# MasterPCB_transfer.net
KiCad netlist of a schematic drawn in EAGLE
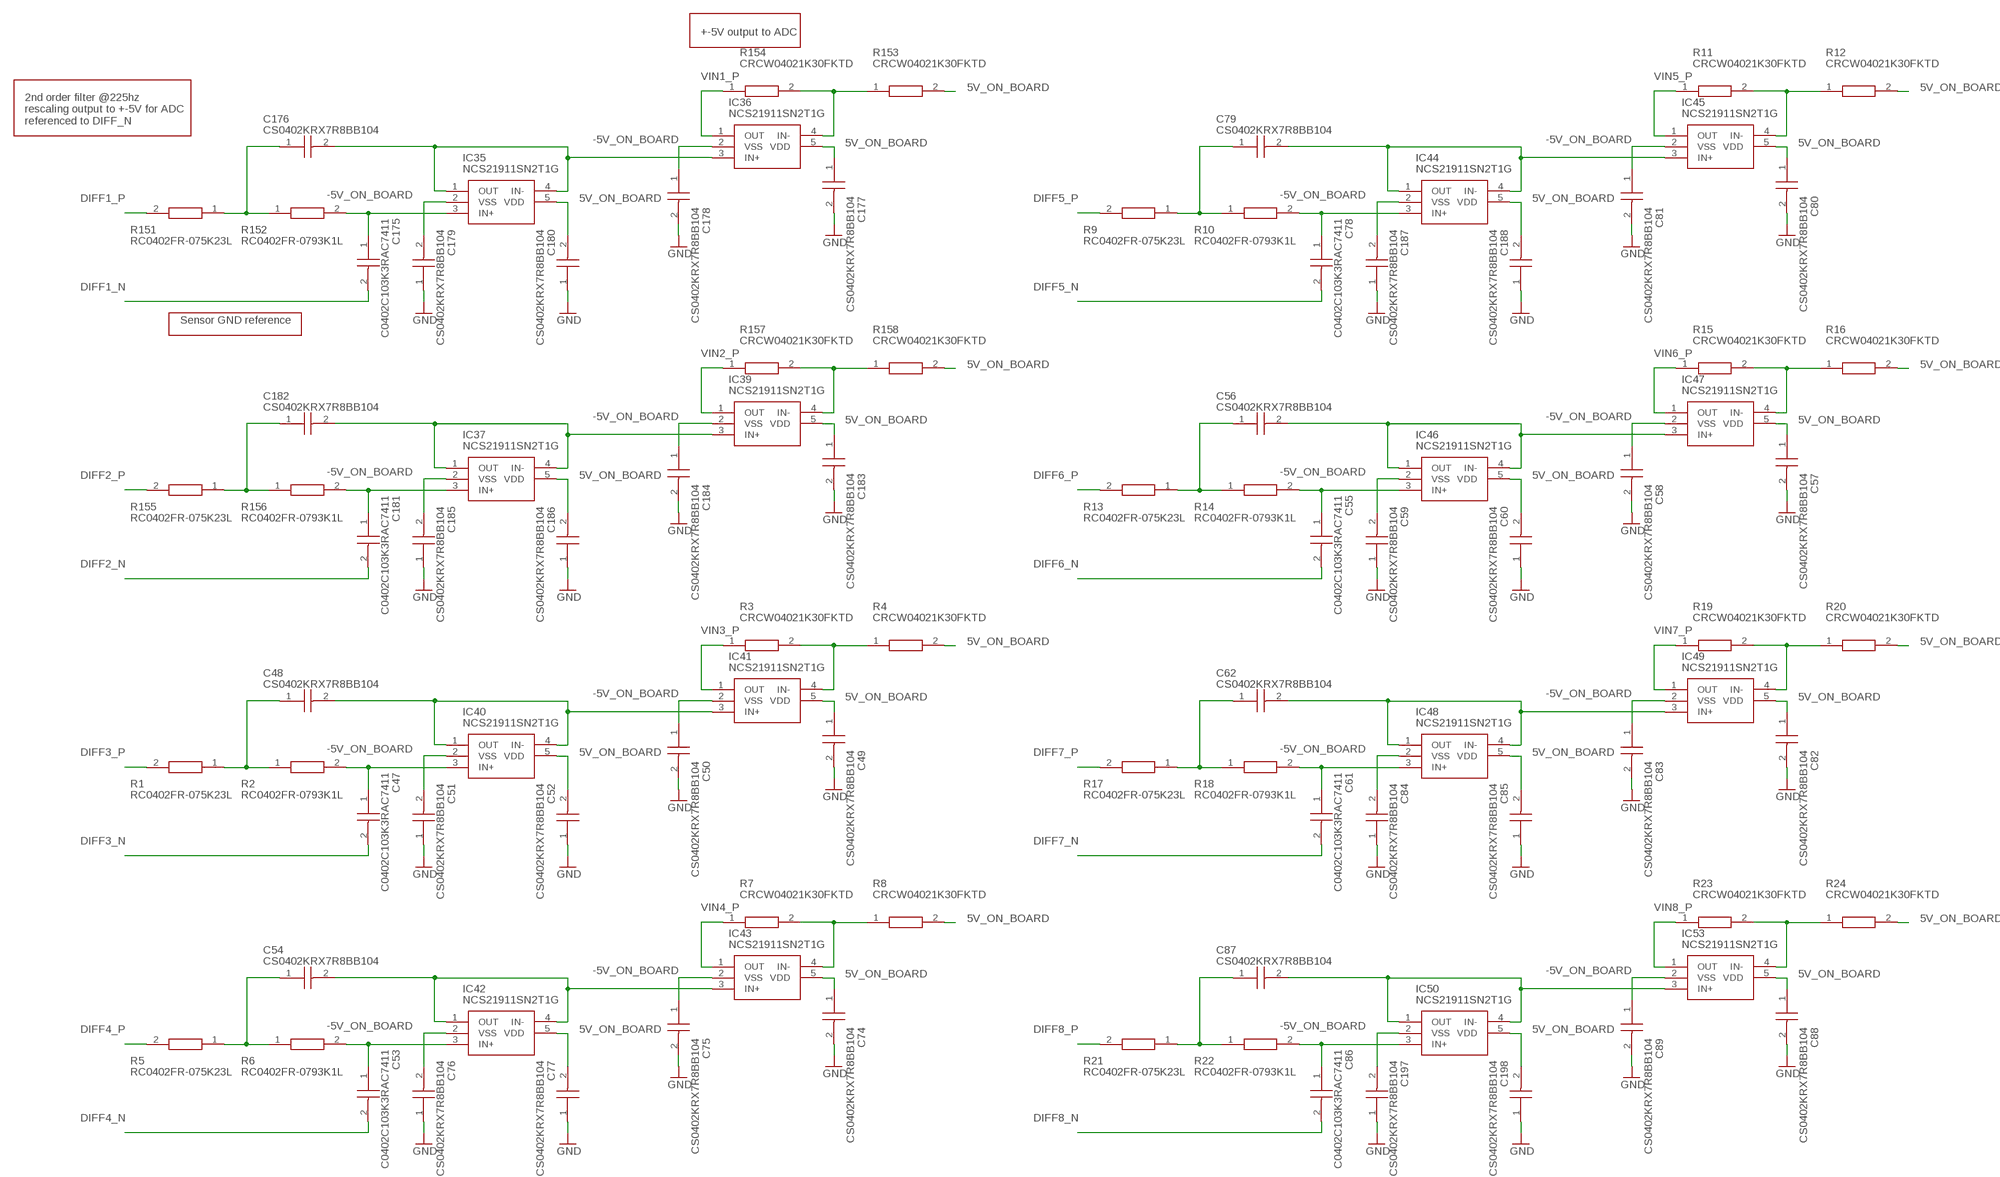
[diagram p0: schematic, sheet 1, part 1 of 3]
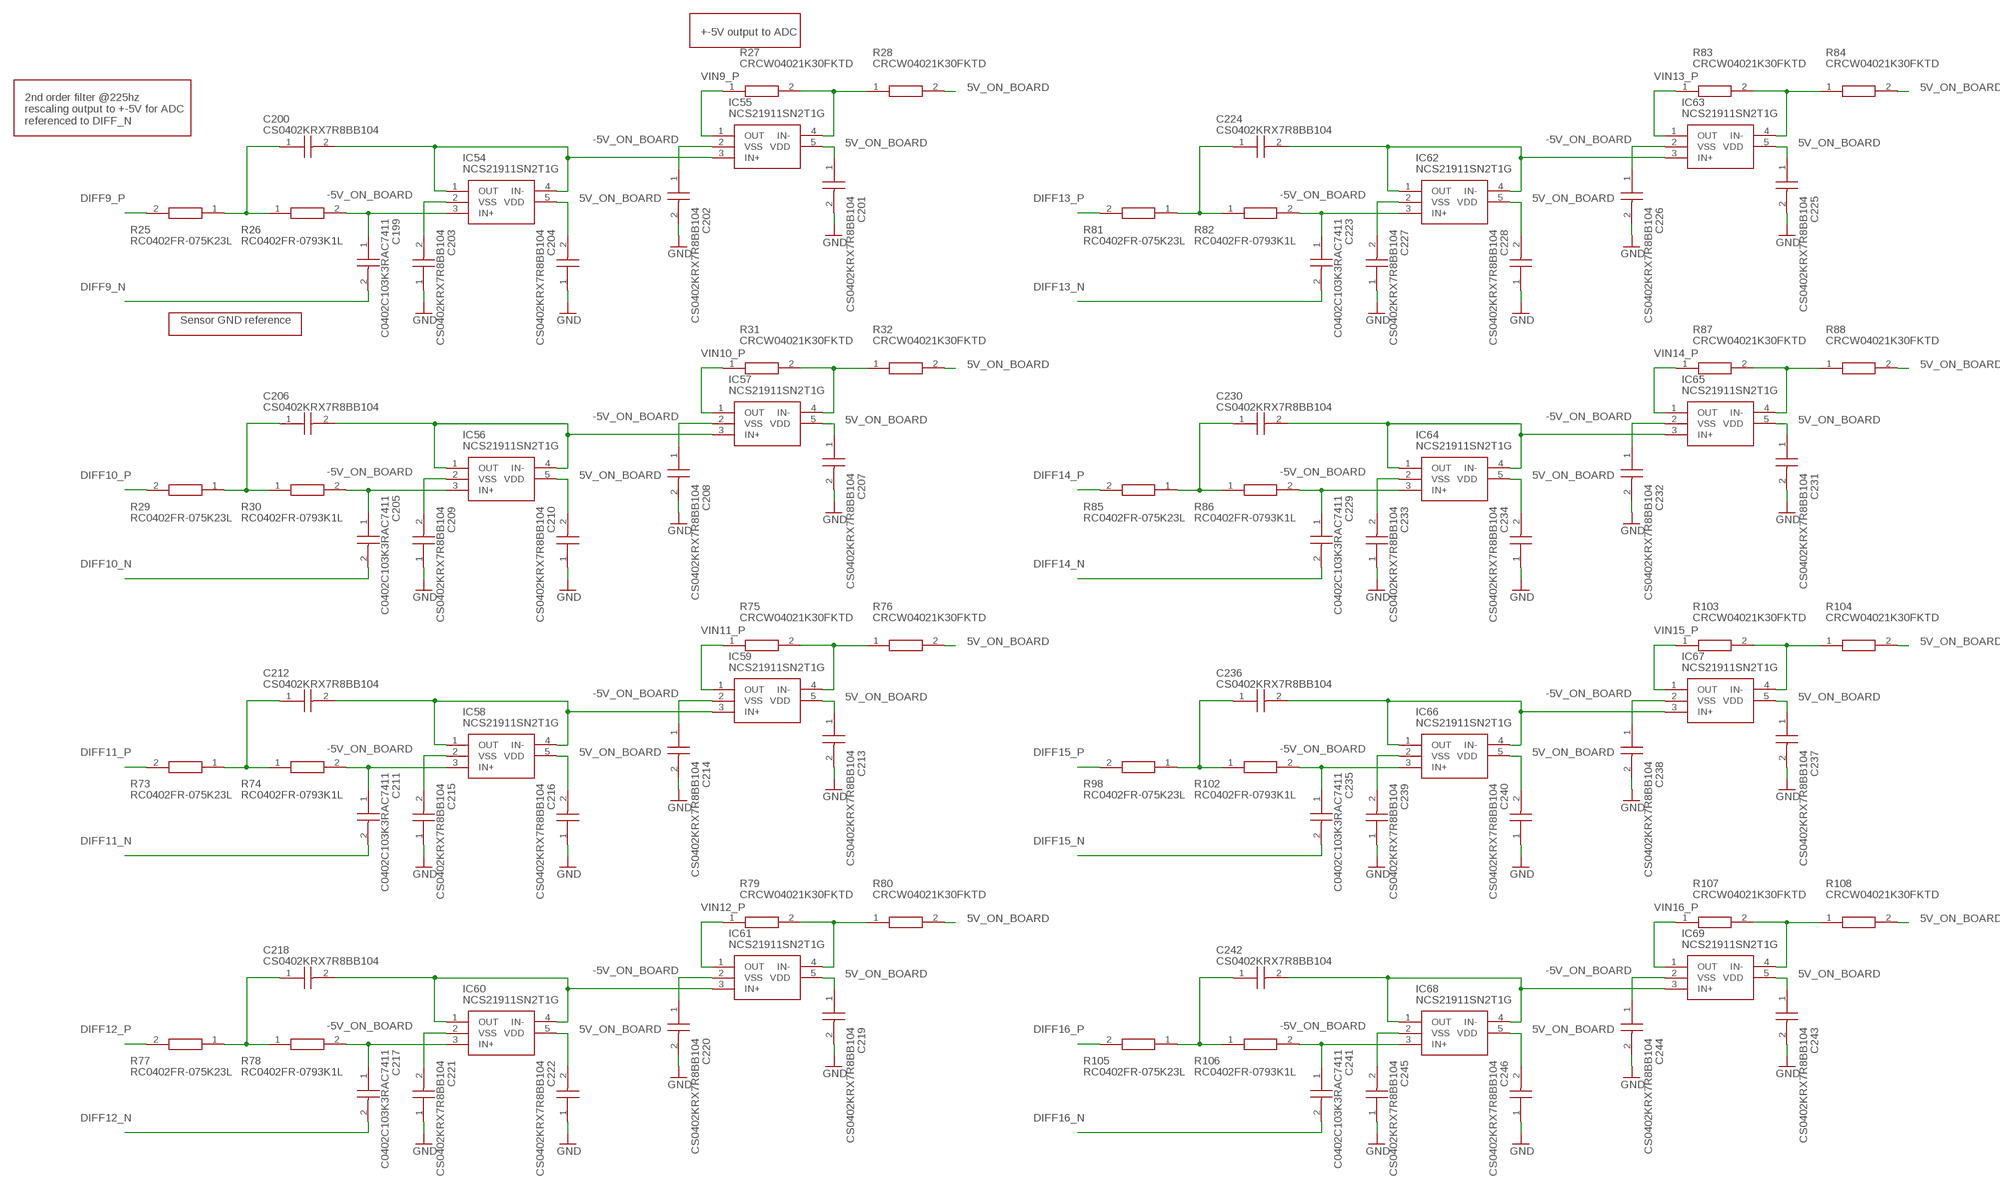
[diagram p1: schematic, sheet 1, part 2 of 3]
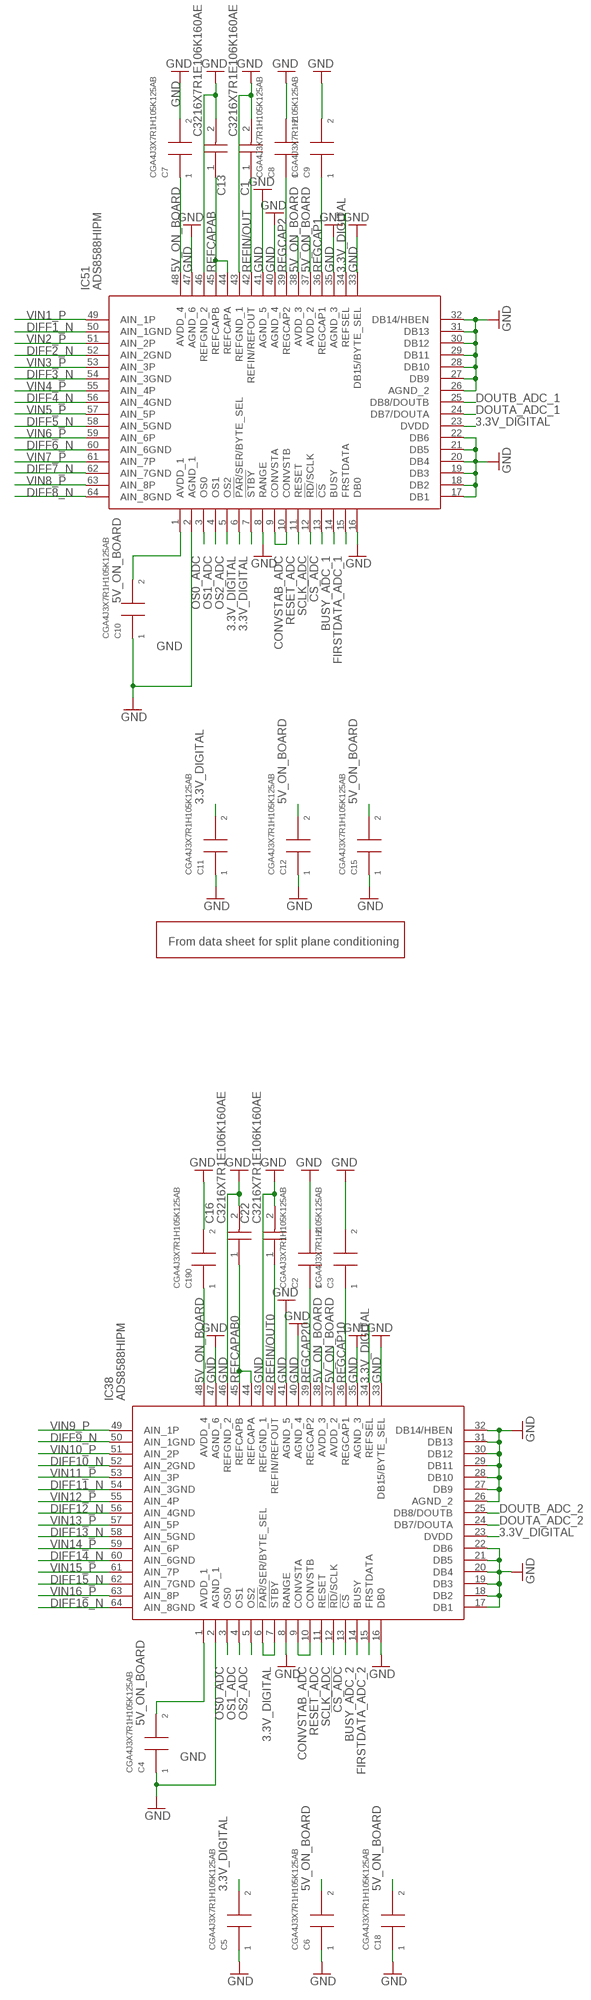
[diagram p2: schematic, sheet 1, part 3 of 3]
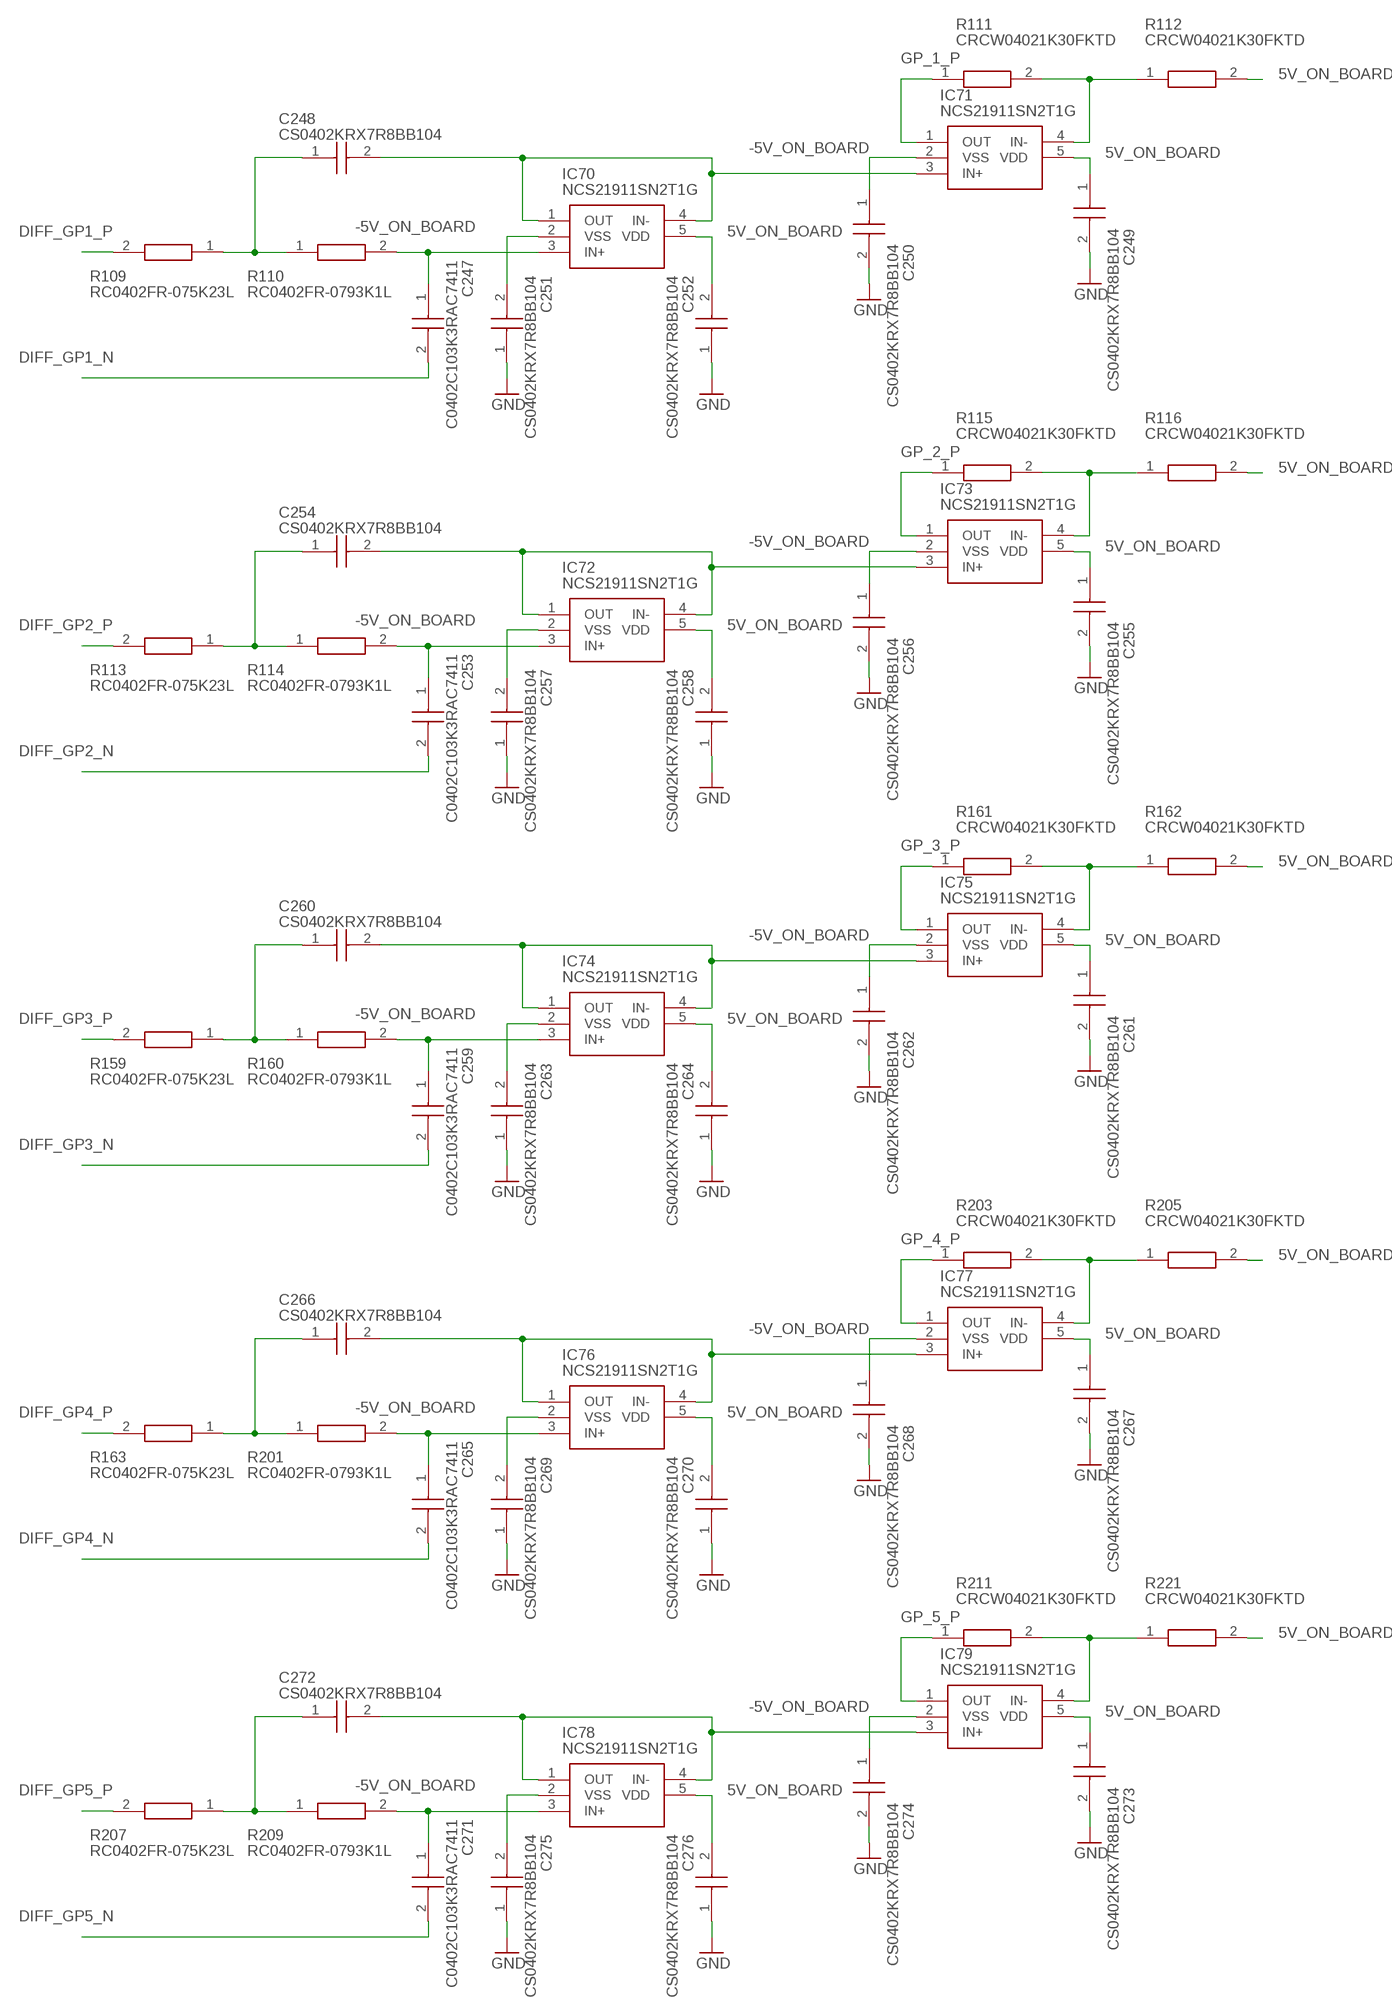
[diagram p3: schematic, sheet 2, part 1 of 2]
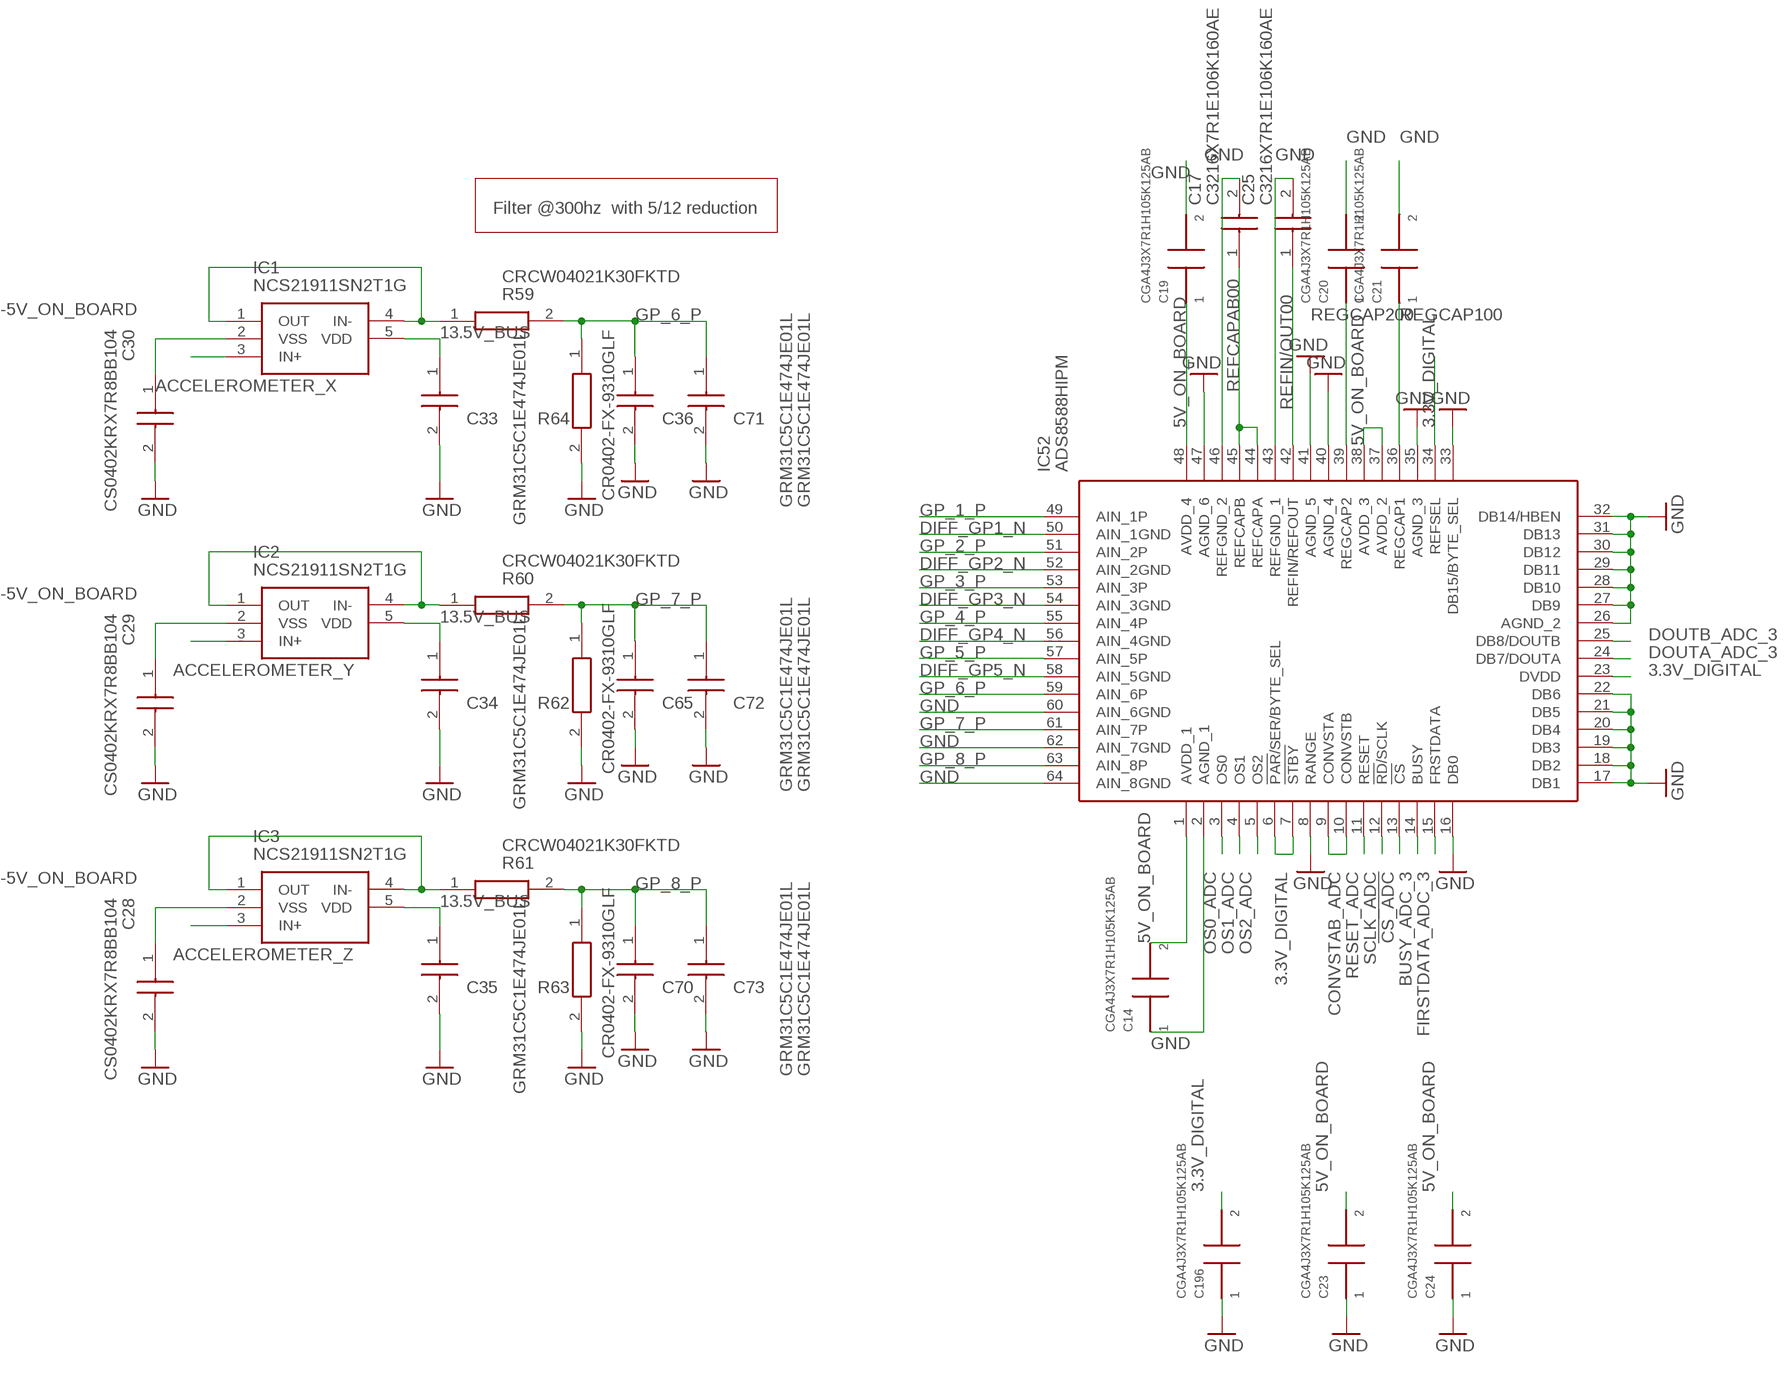
[diagram p4: schematic, sheet 2, part 2 of 2]
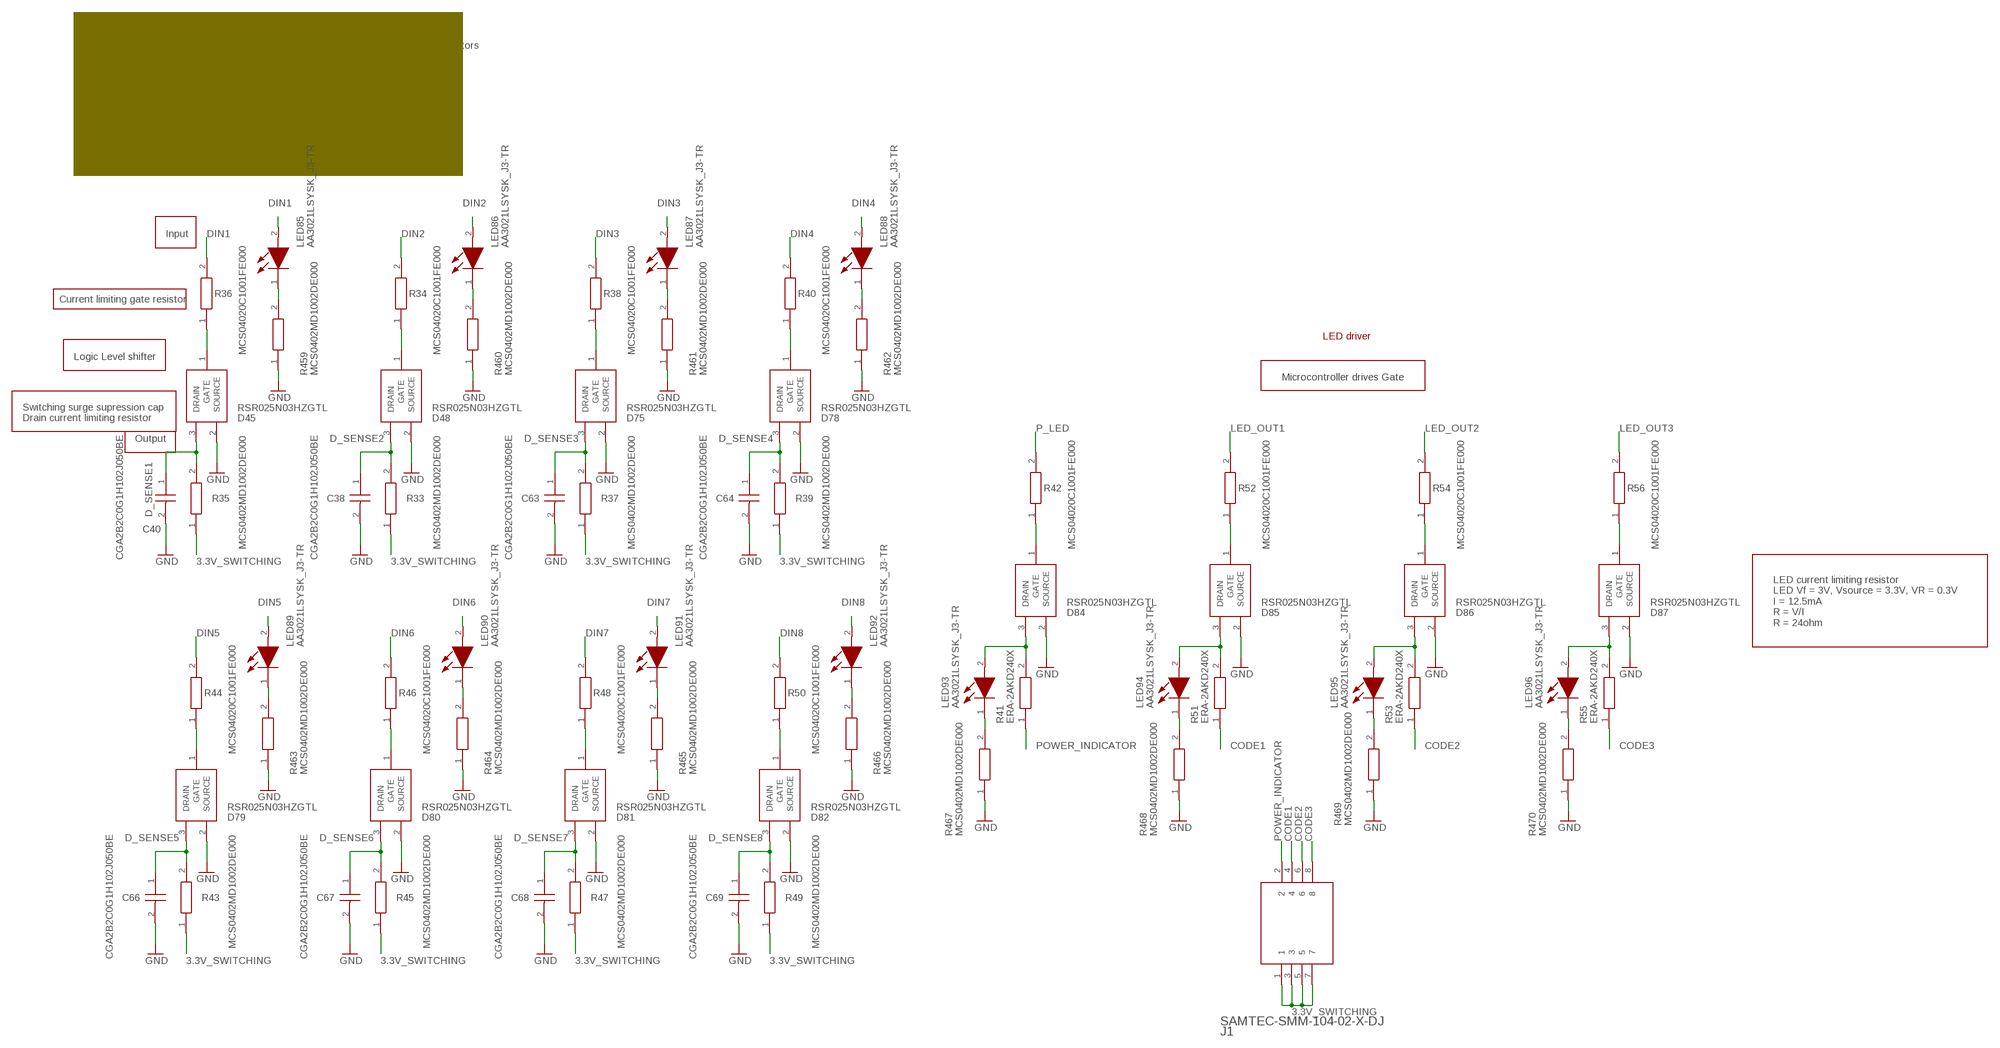
[diagram p5: schematic, sheet 3]
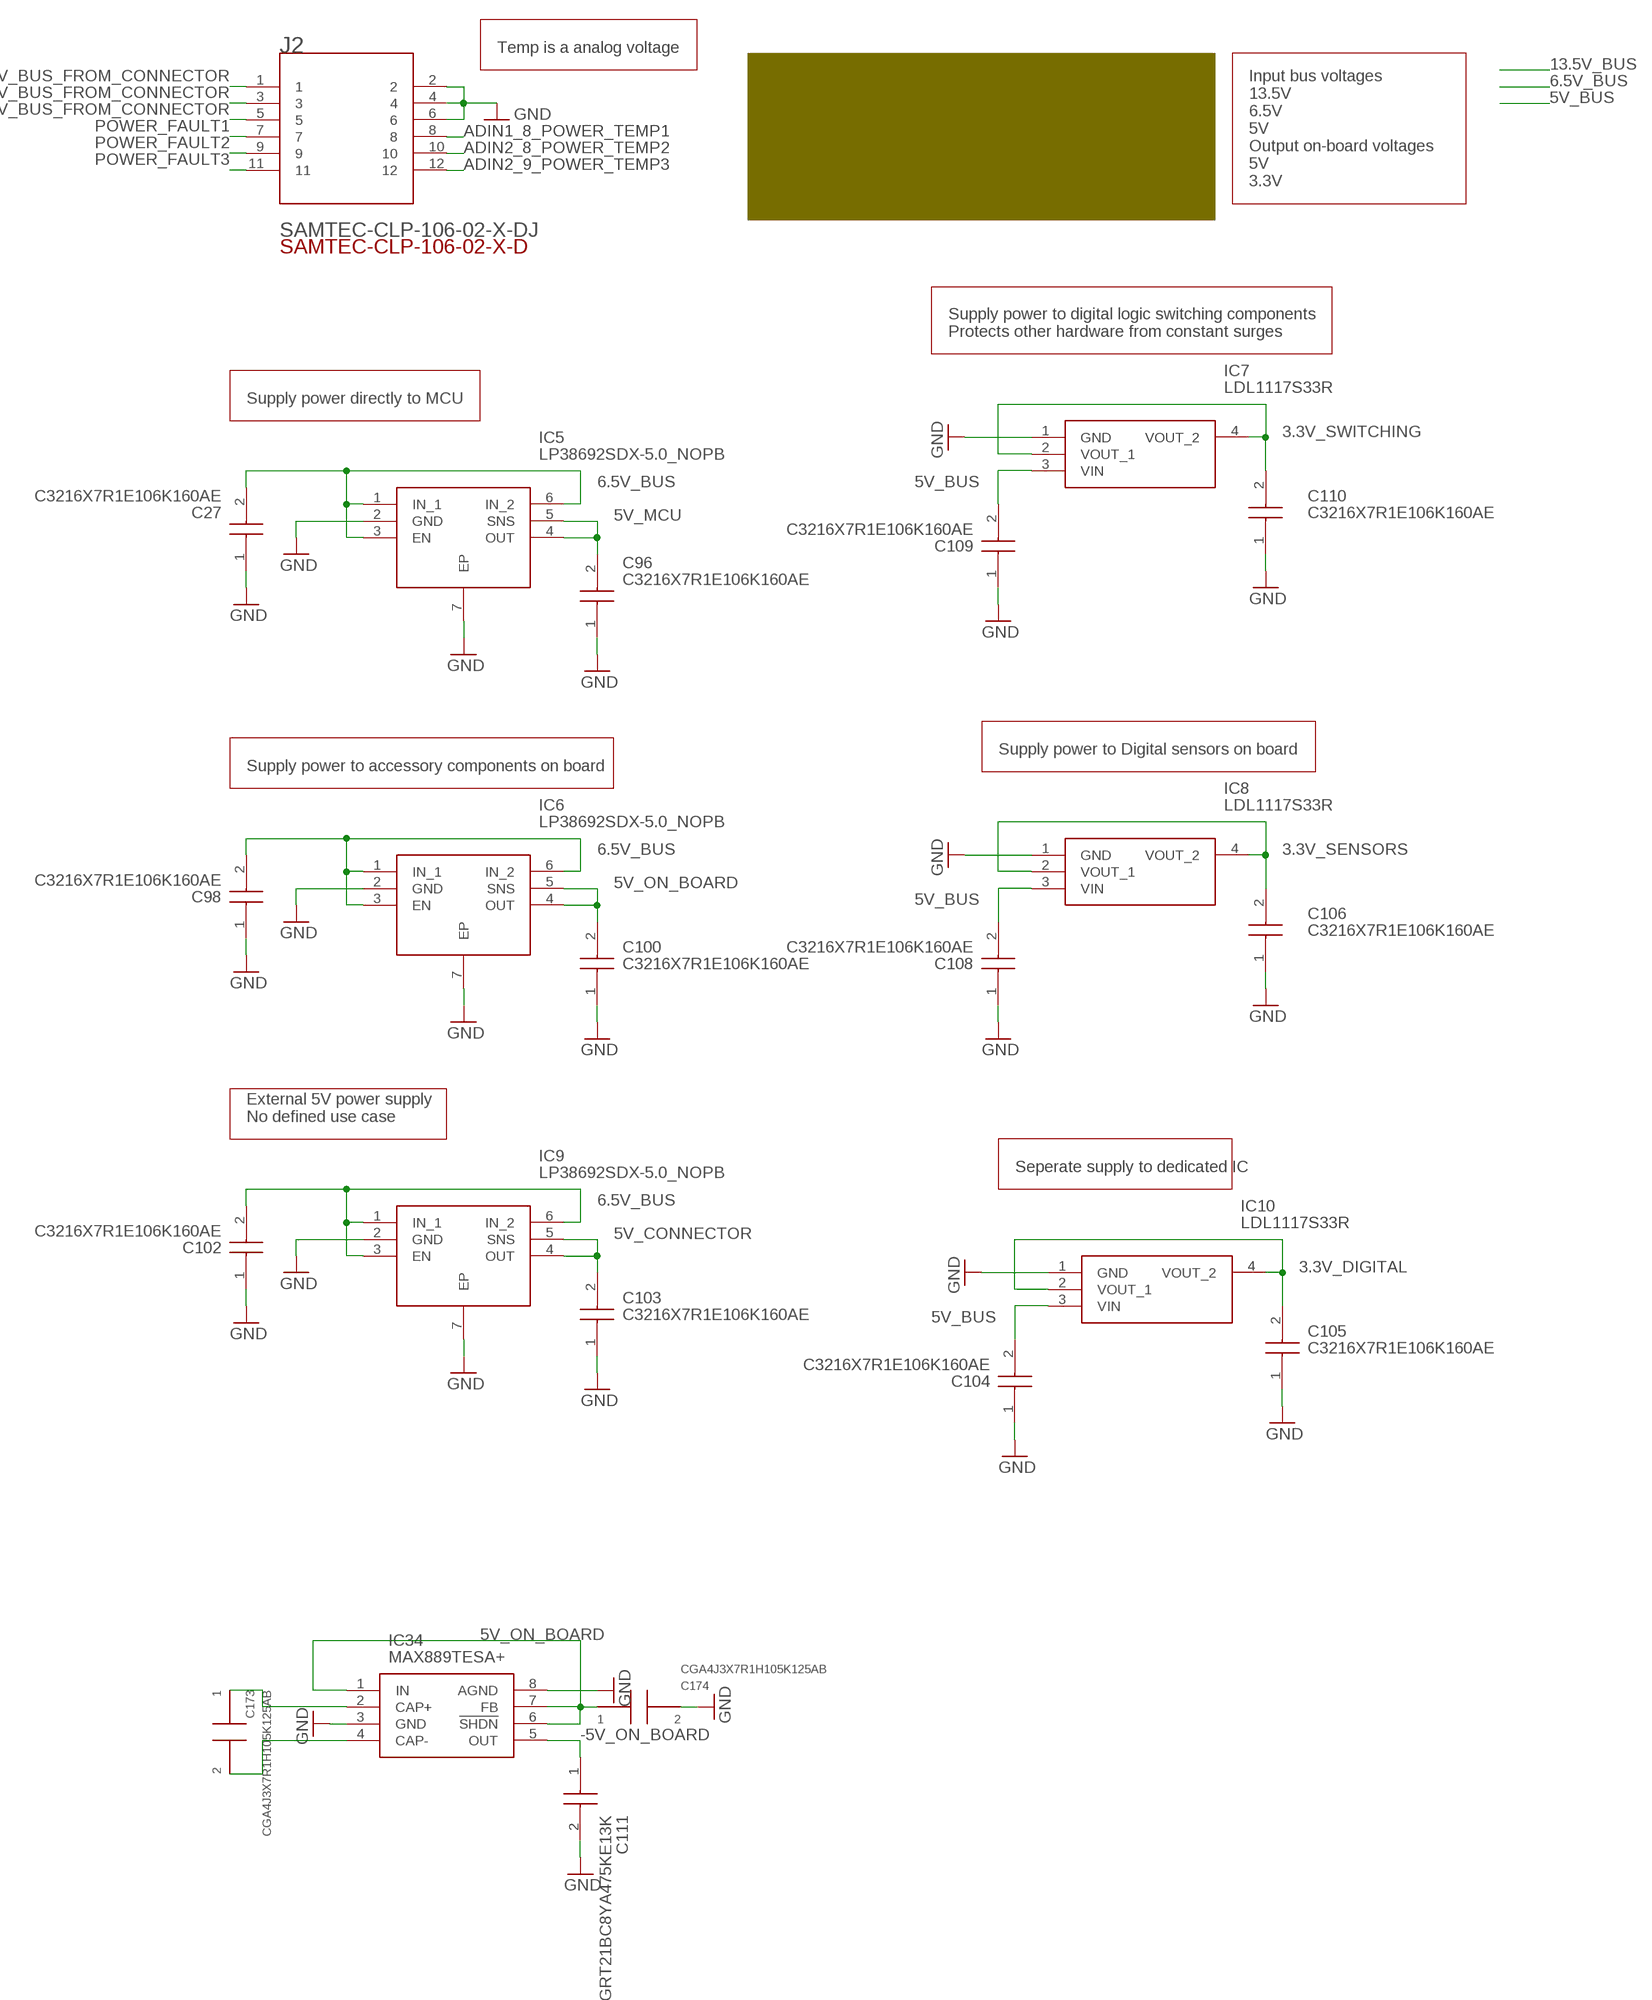
[diagram p6: schematic, sheet 4]
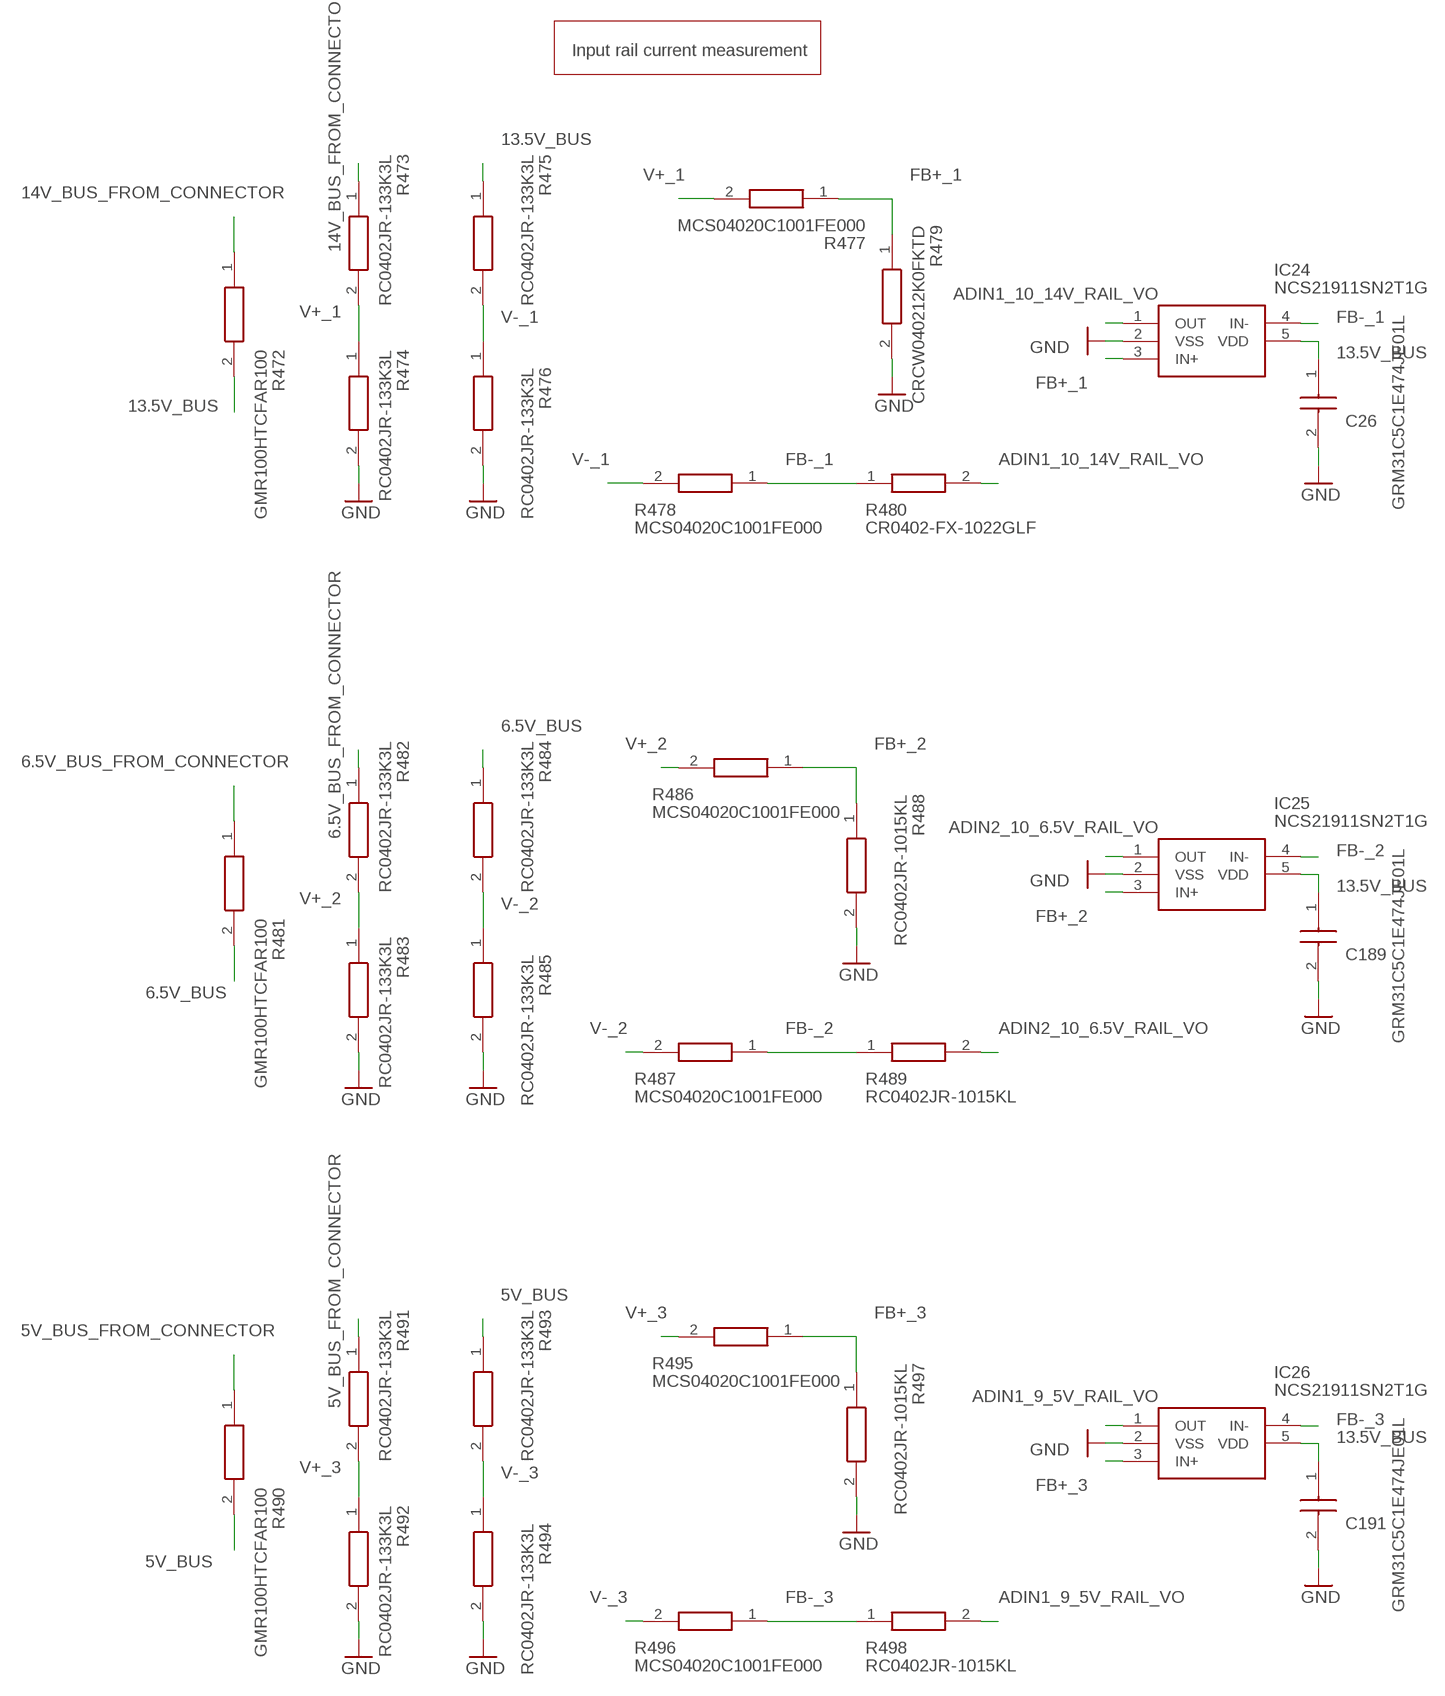
[diagram p7: schematic, sheet 5]
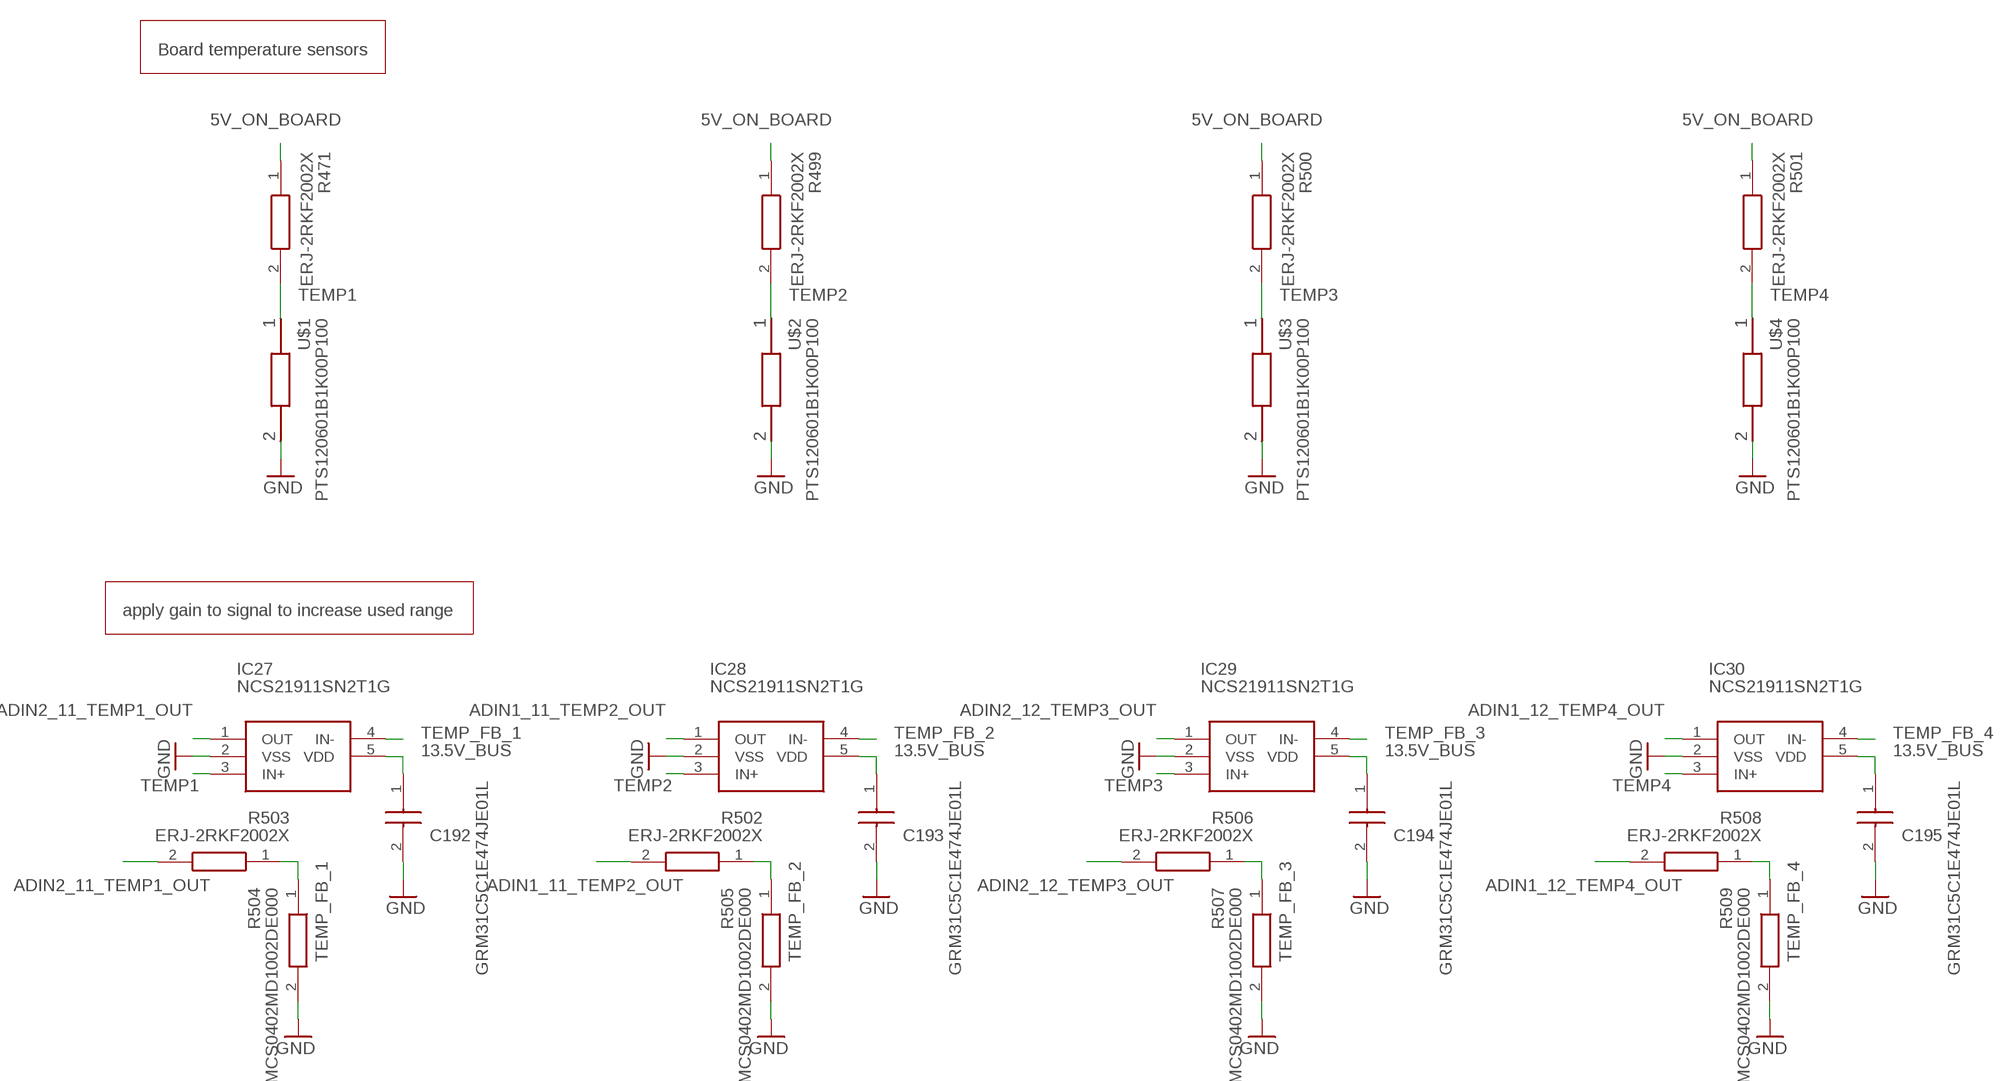
[diagram p8: schematic, sheet 6]
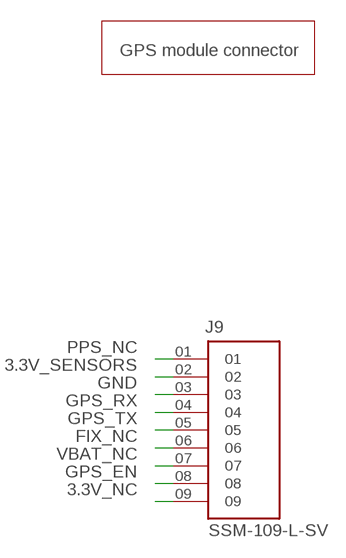
[diagram p9: schematic, sheet 7]
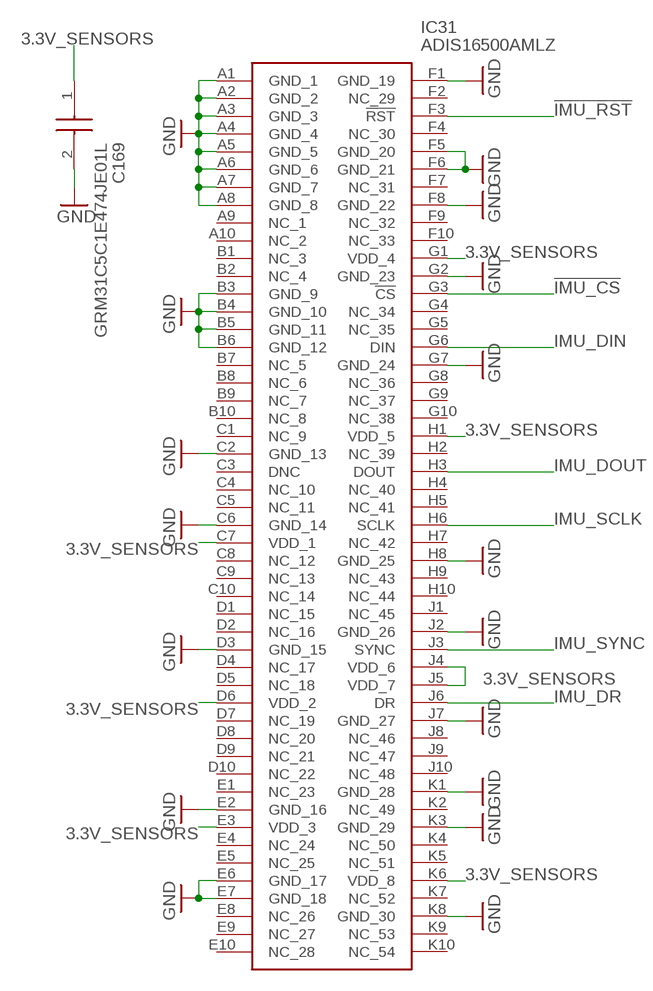
[diagram p10: schematic, sheet 8]
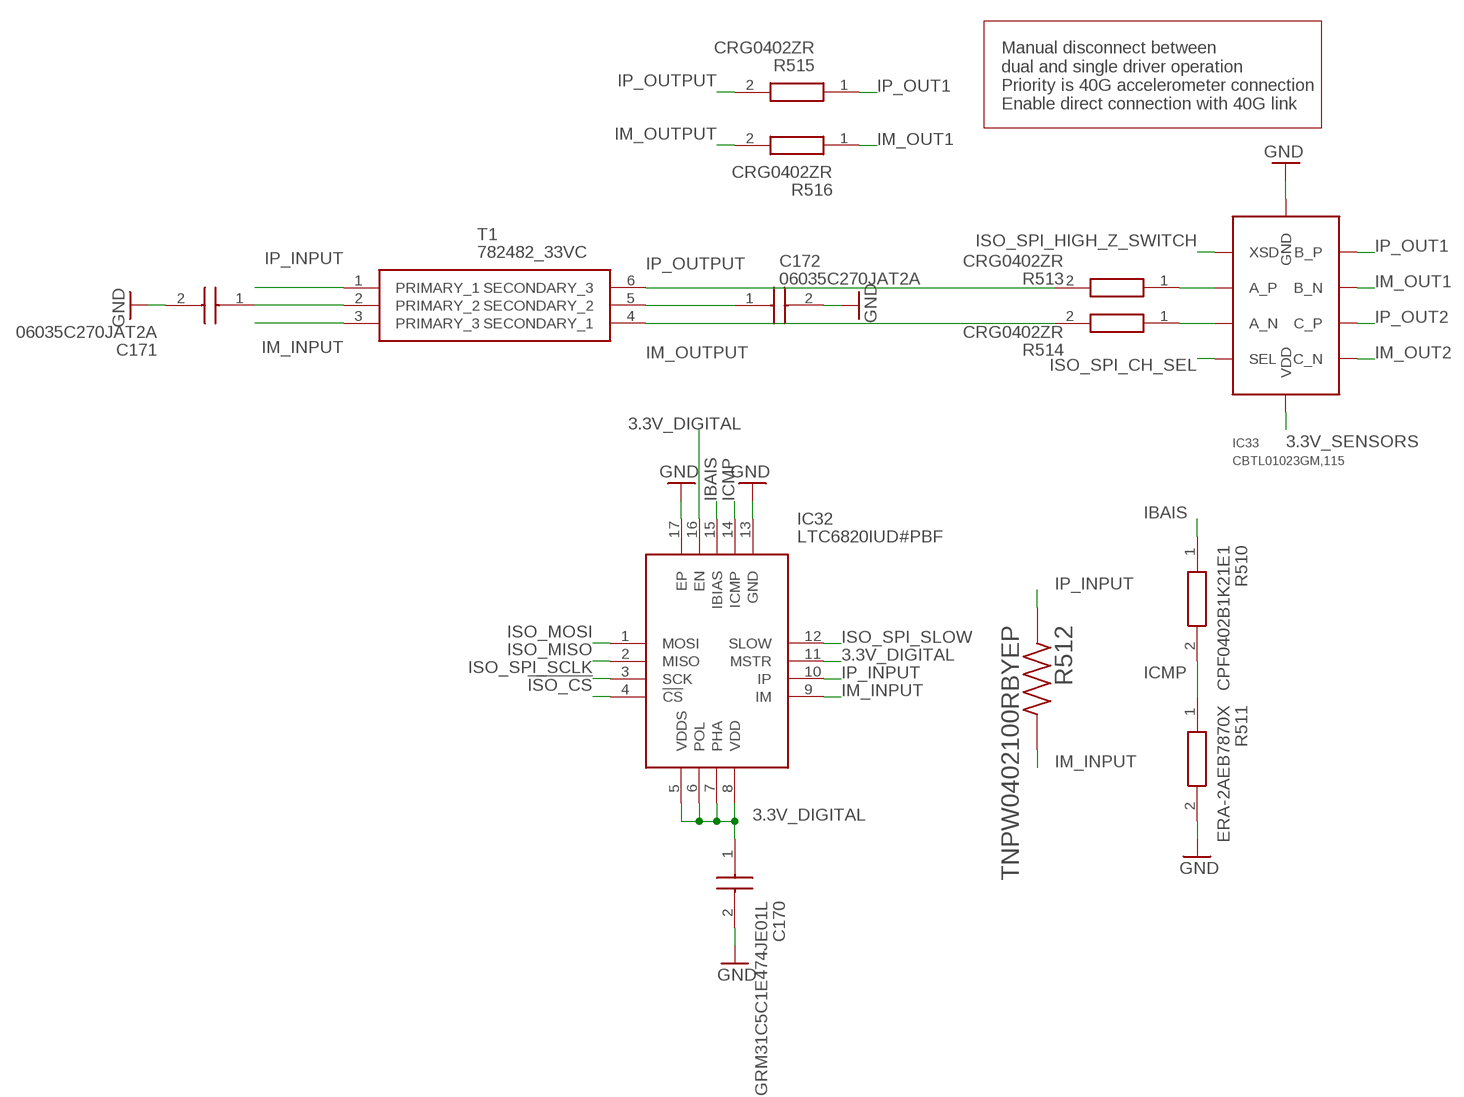
[diagram p11: schematic, sheet 9]
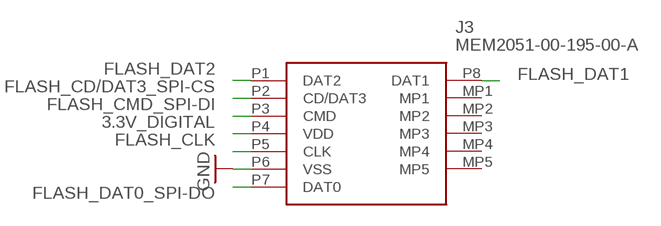
[diagram p12: schematic, sheet 10]
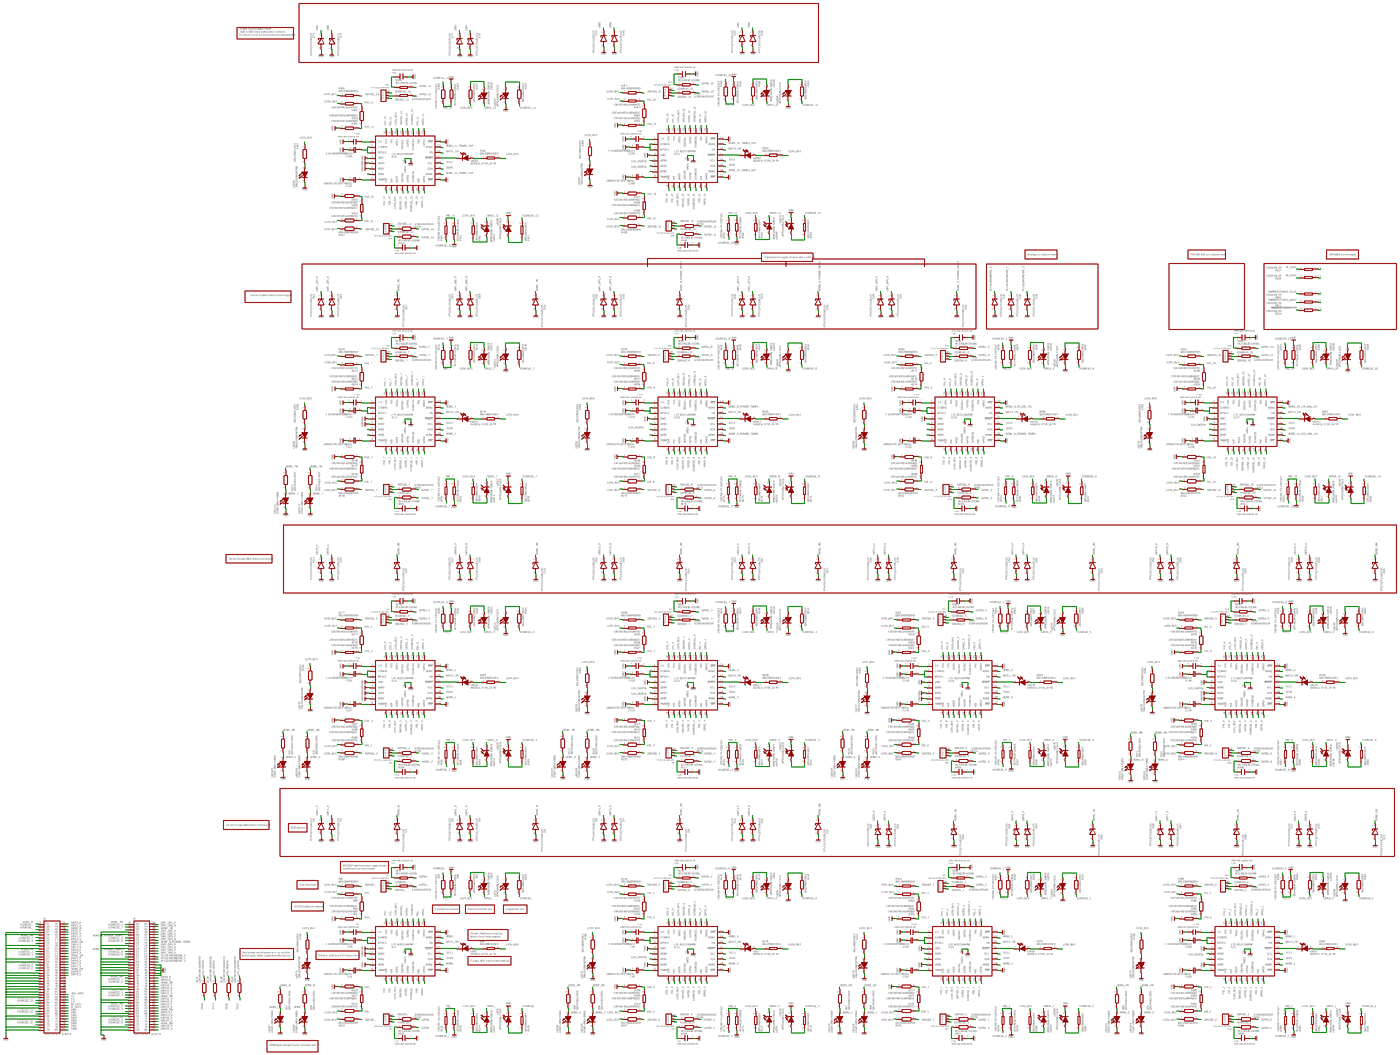
[diagram p13: schematic, sheet 11, overview]
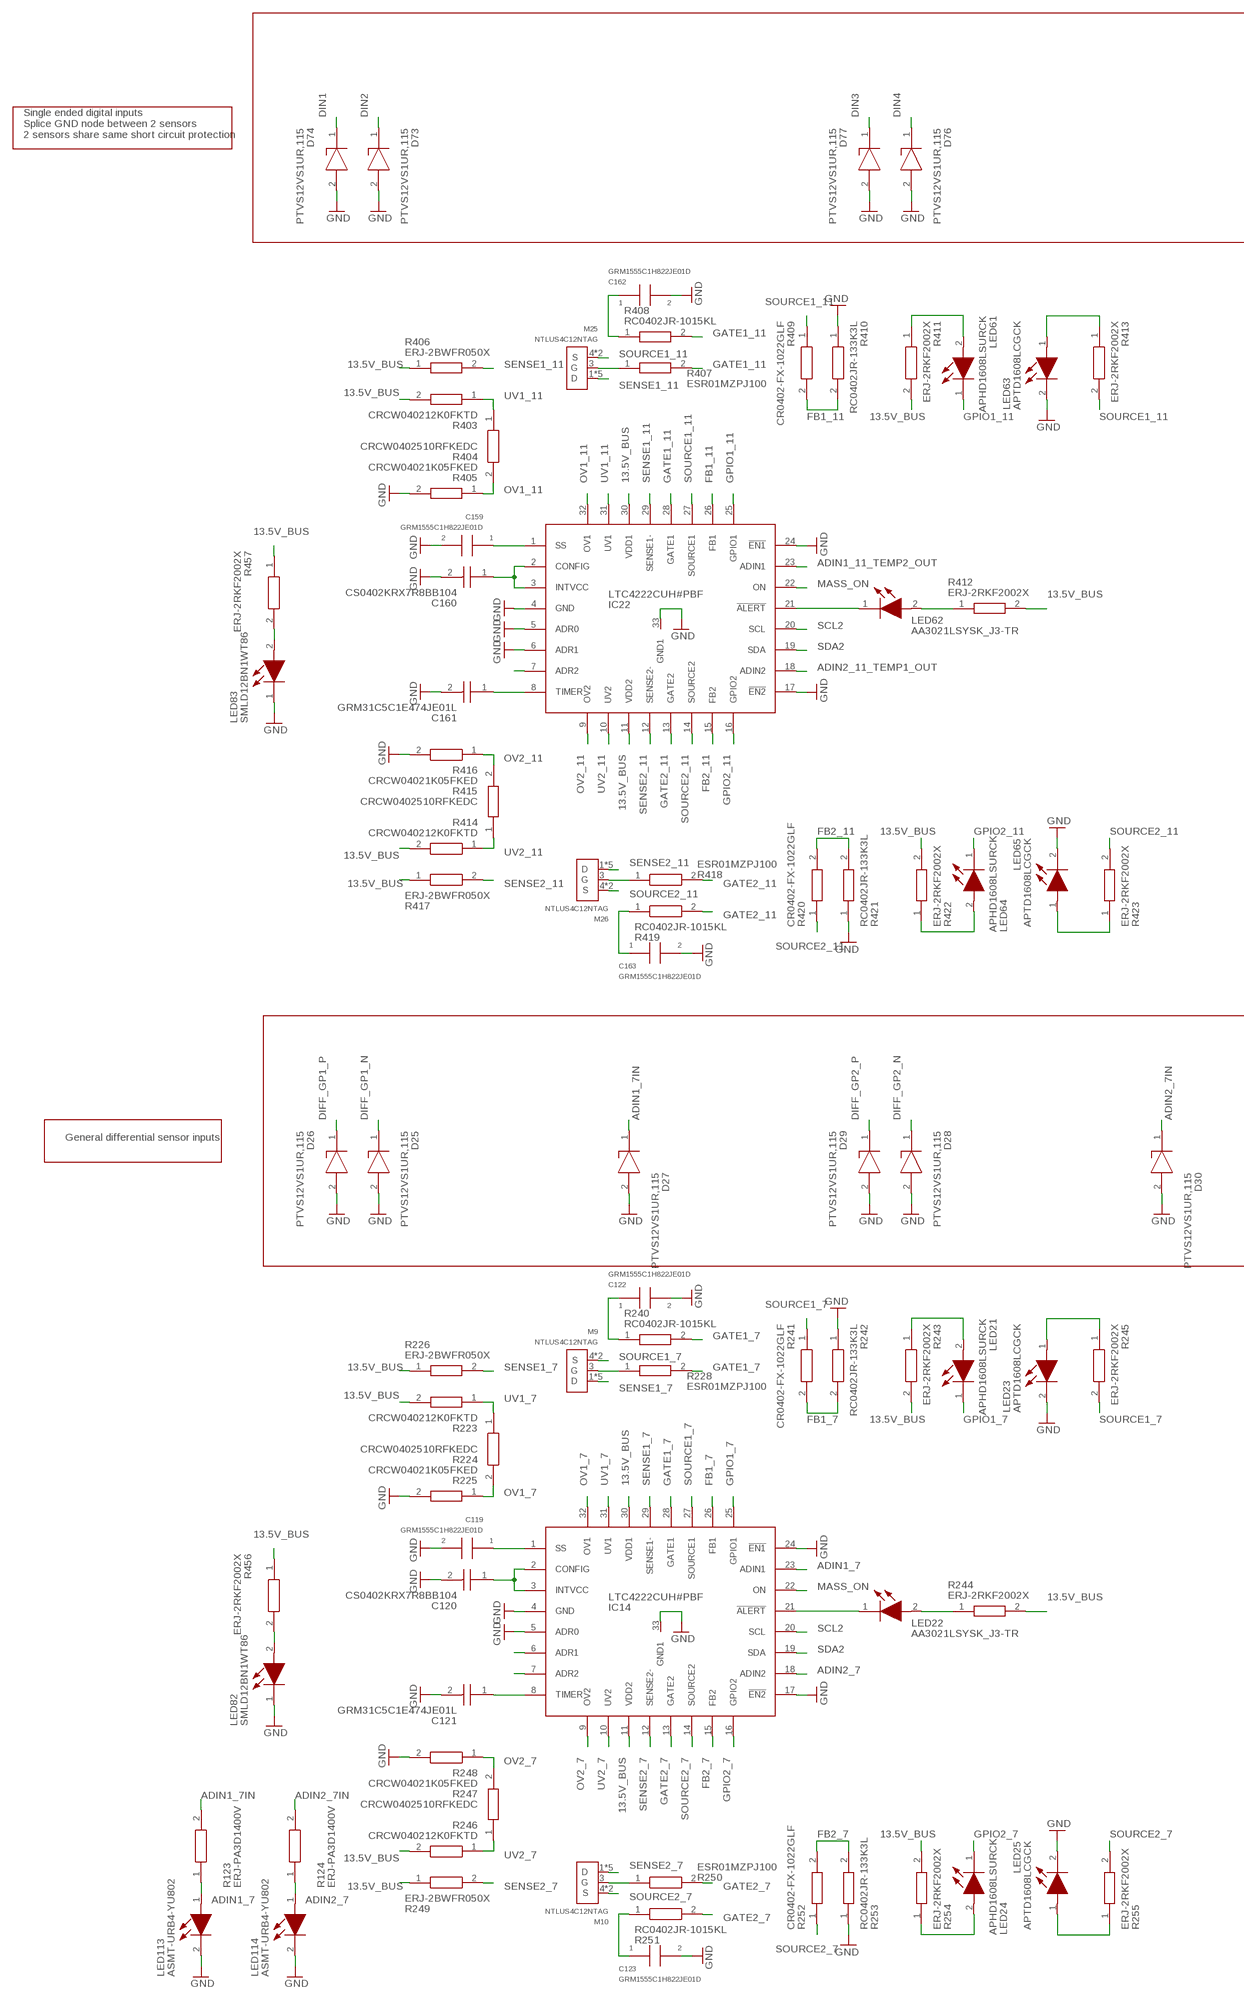
[diagram p14: schematic, sheet 11, part 1 of 6]
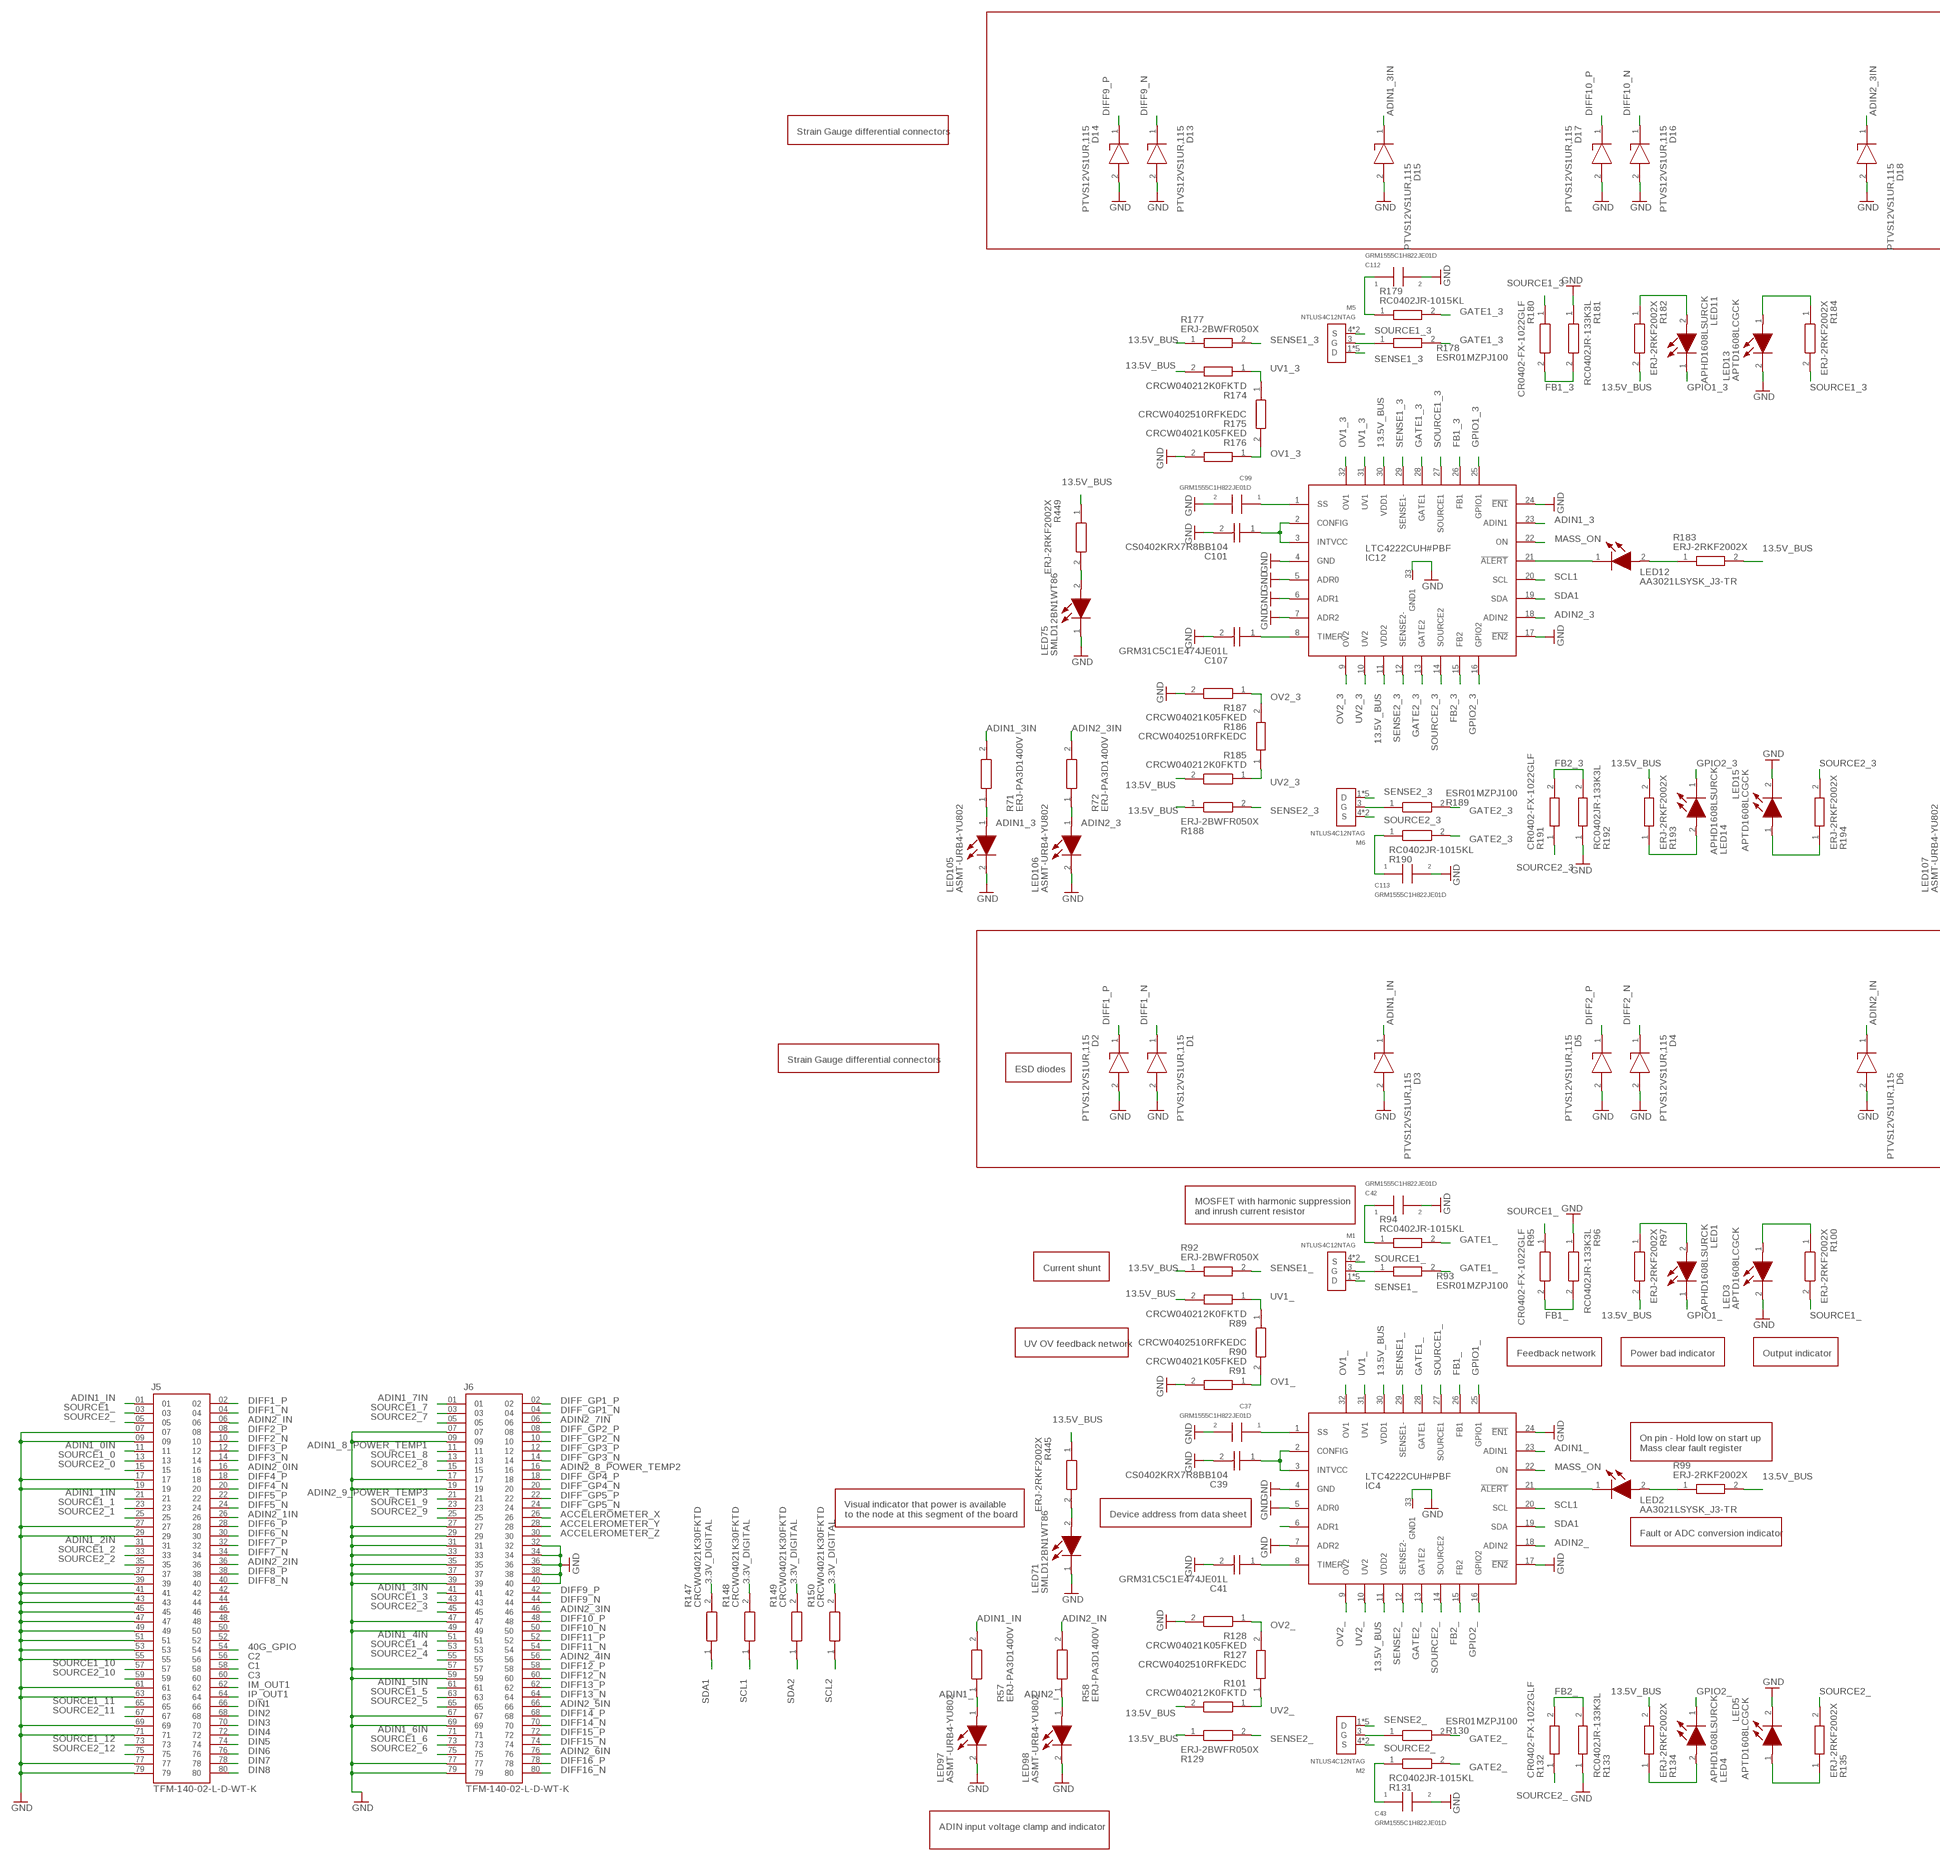
[diagram p15: schematic, sheet 11, part 2 of 6]
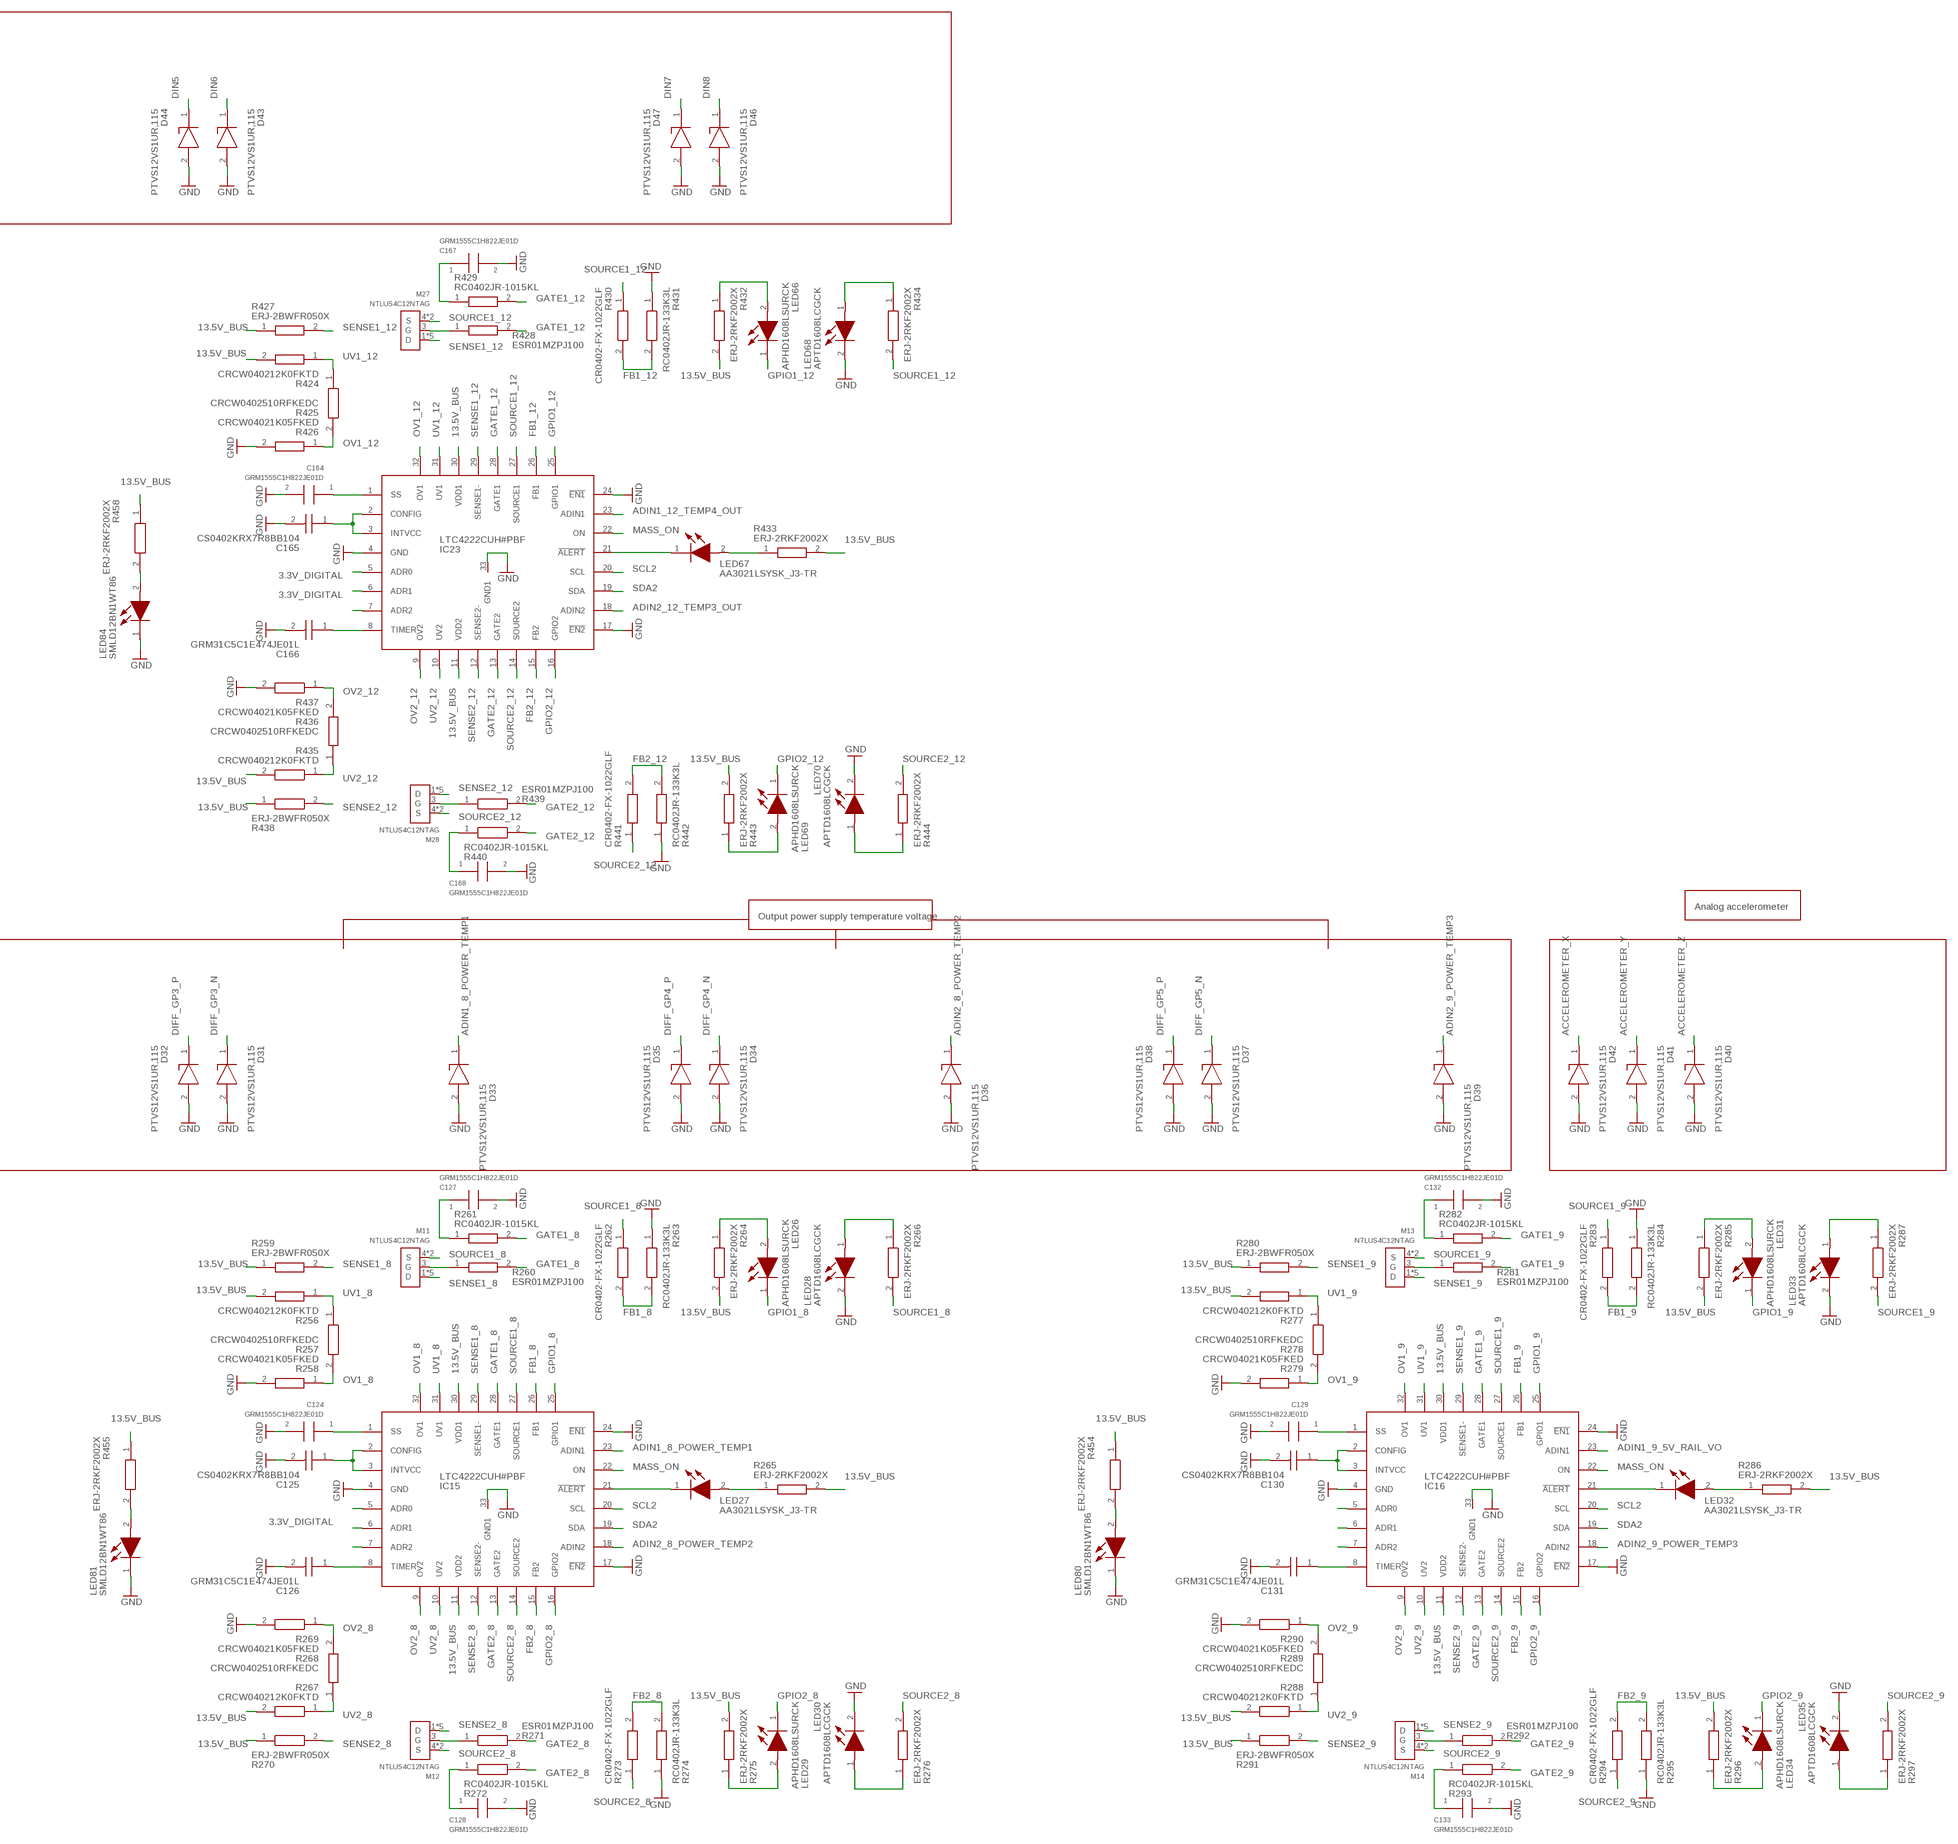
[diagram p16: schematic, sheet 11, part 3 of 6]
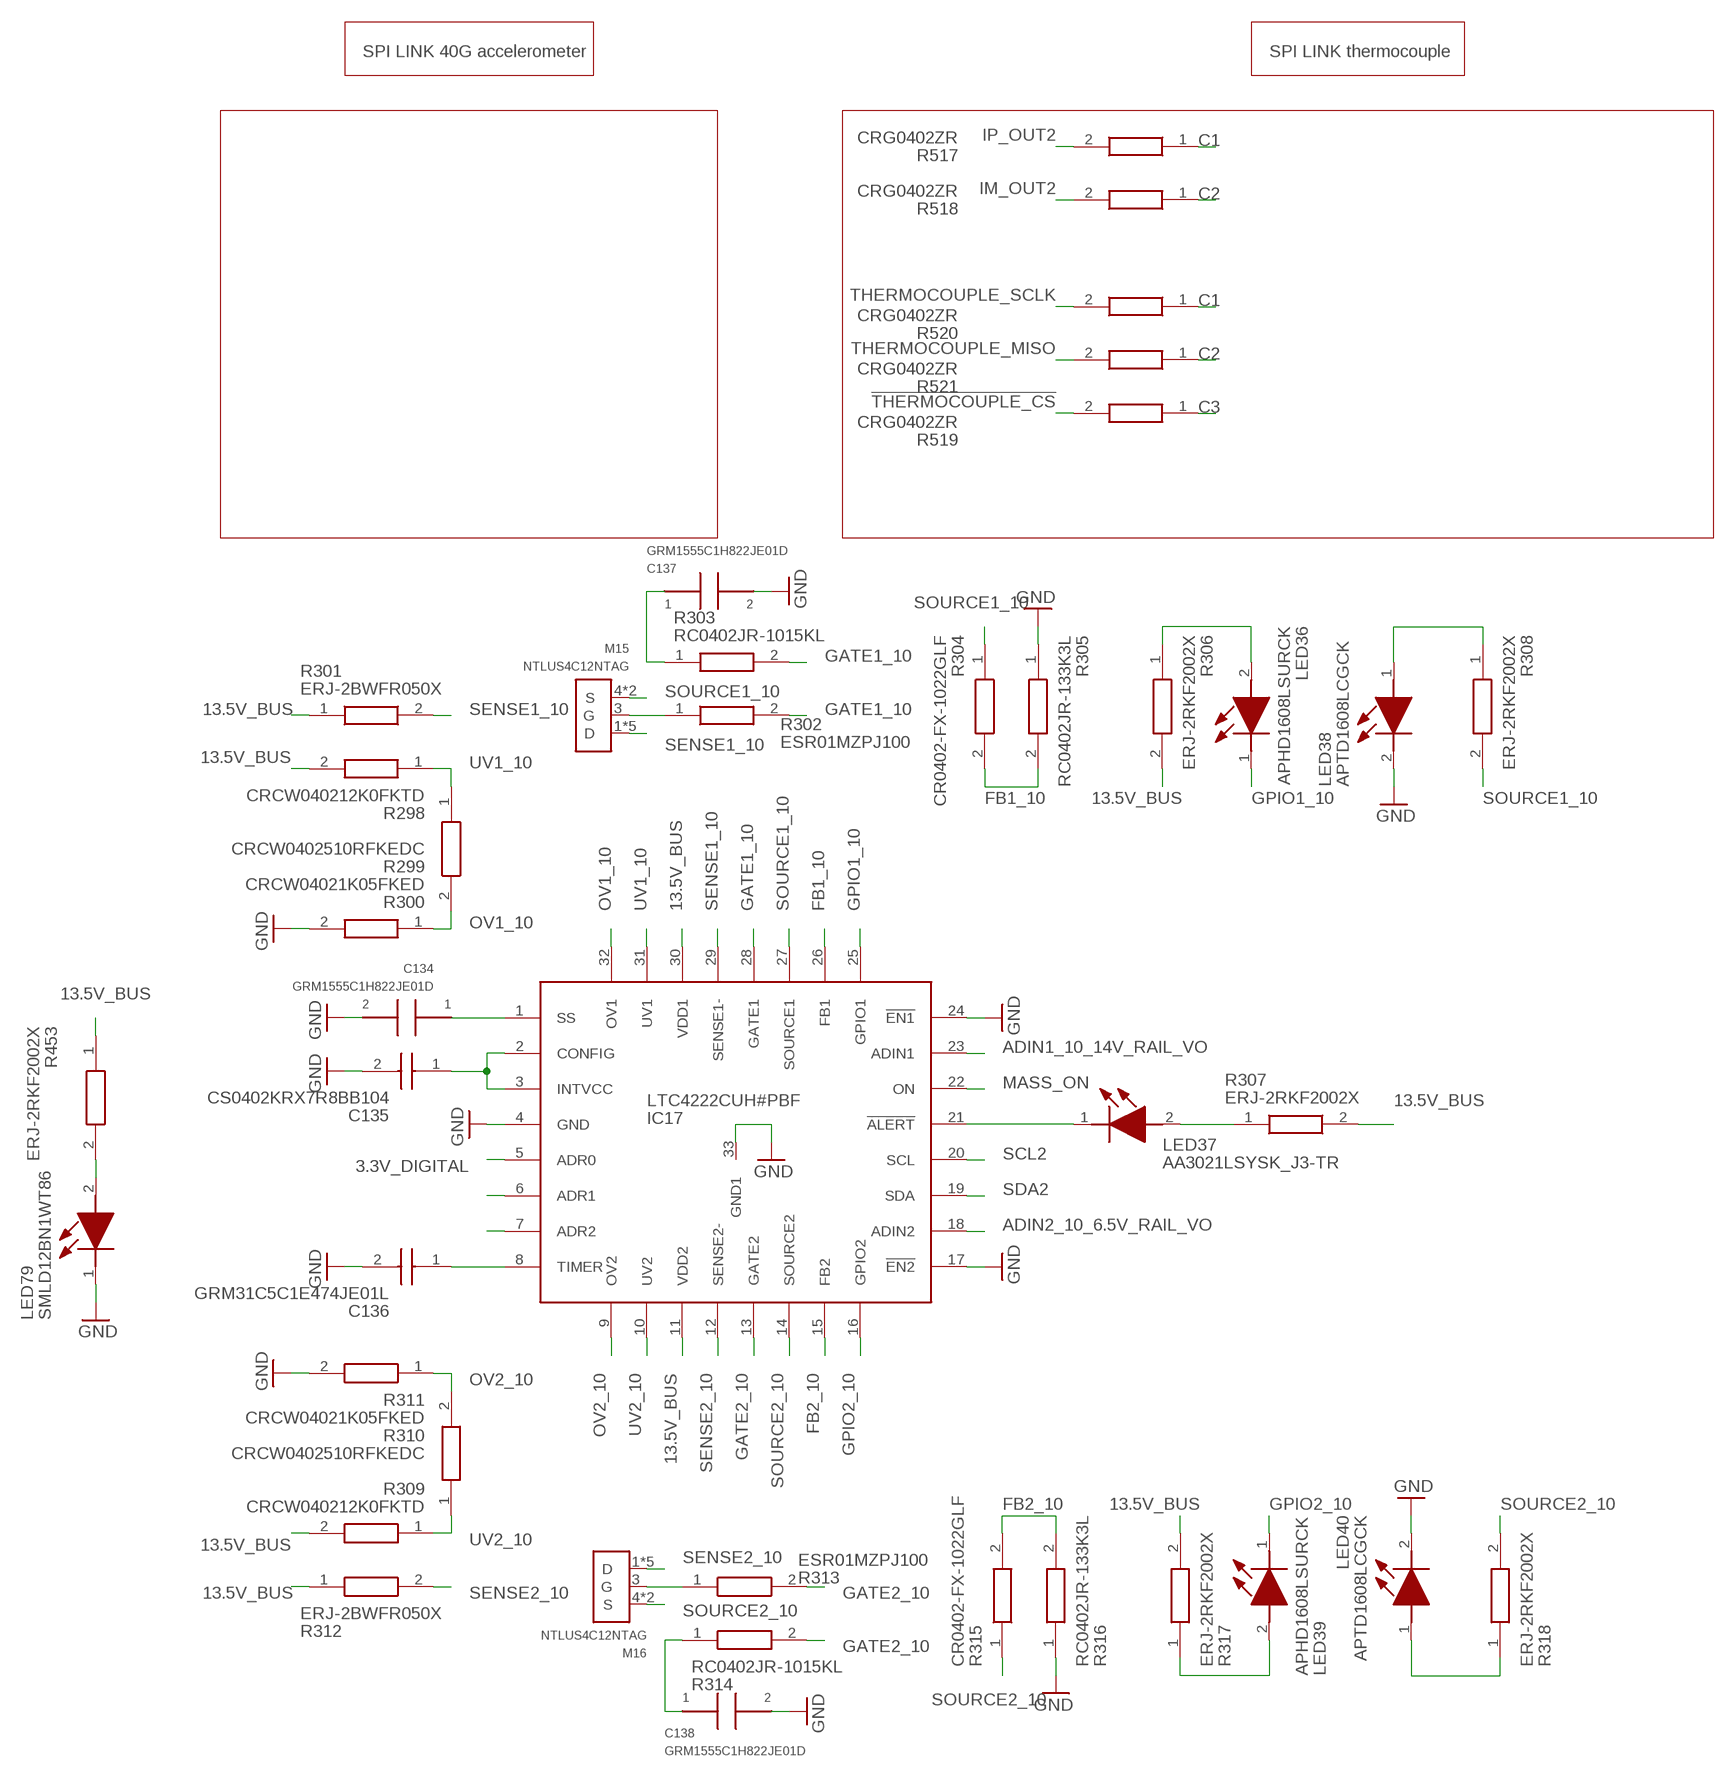
[diagram p17: schematic, sheet 11, part 4 of 6]
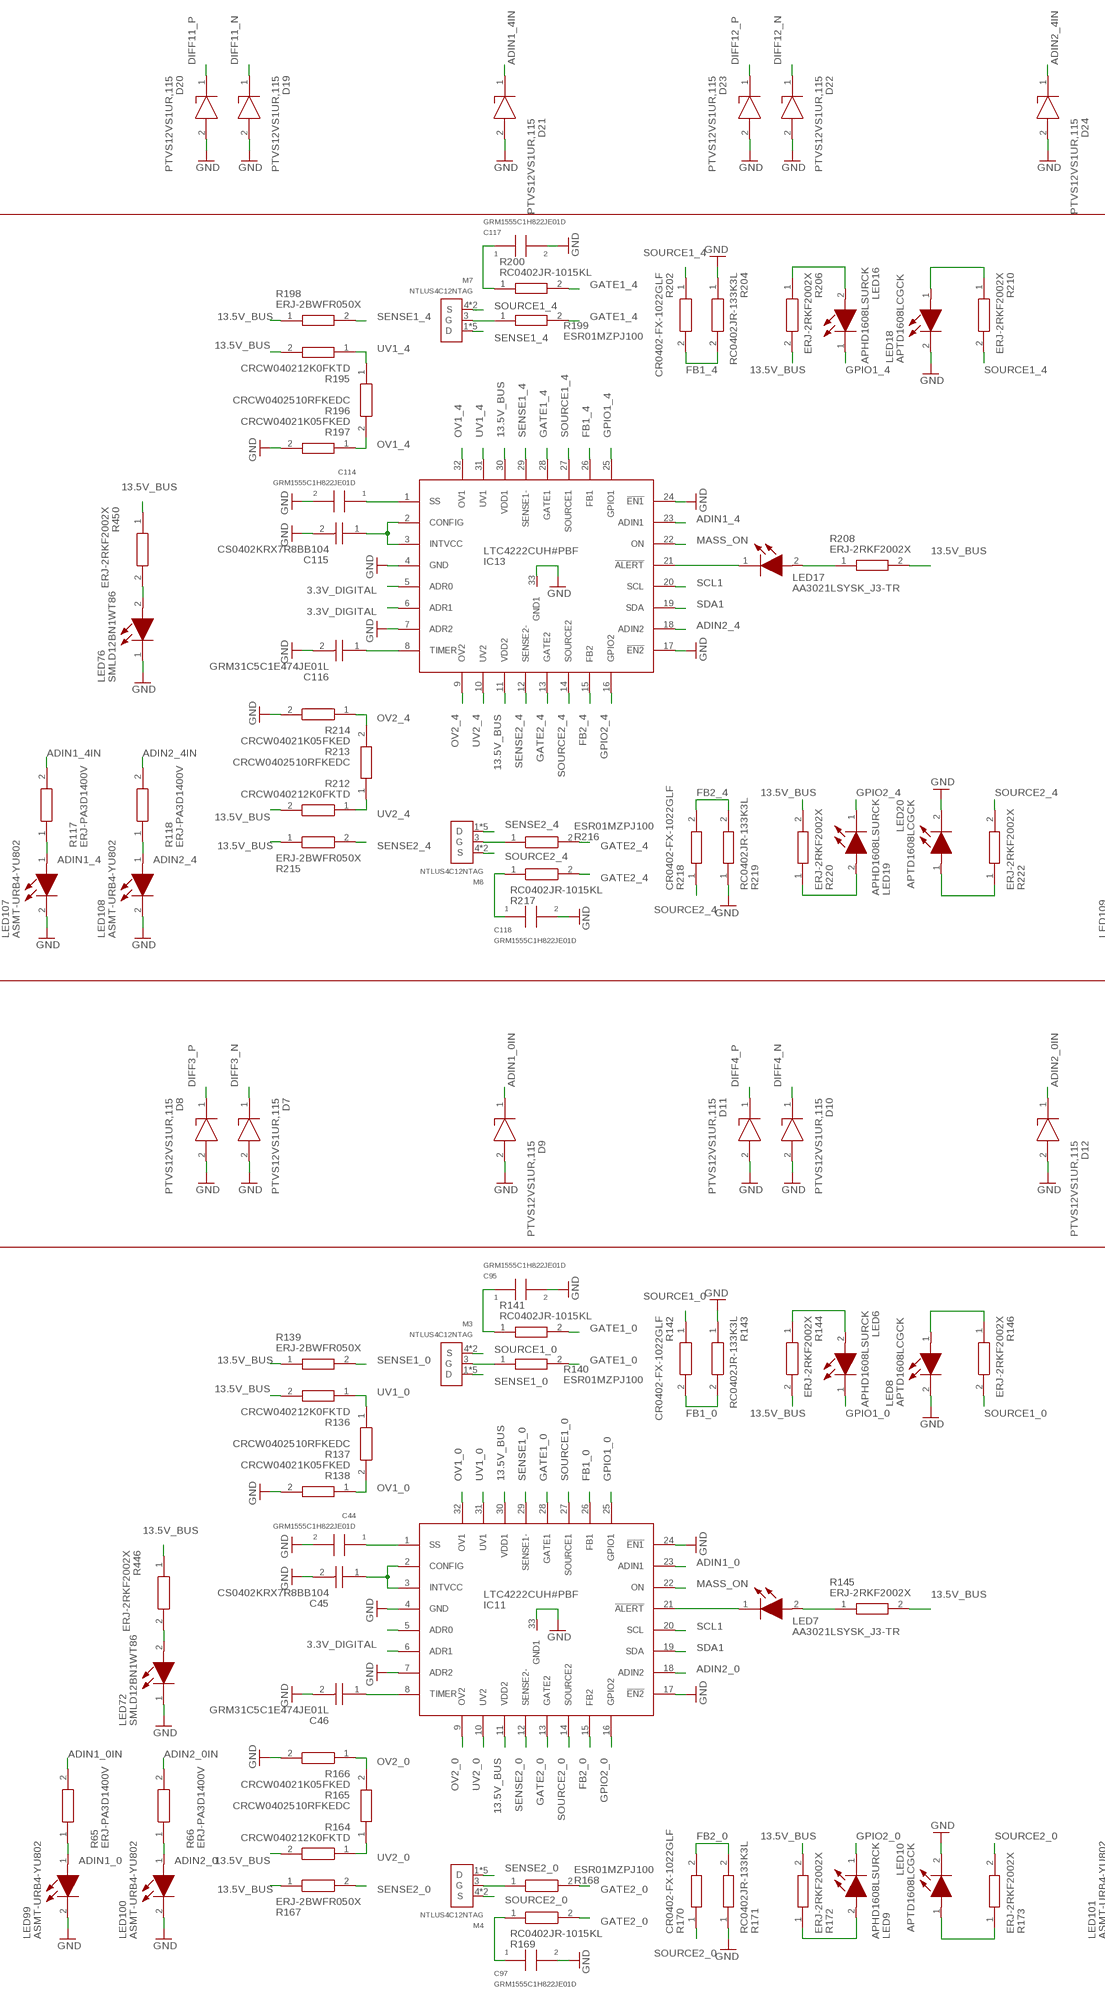
[diagram p18: schematic, sheet 11, part 5 of 6]
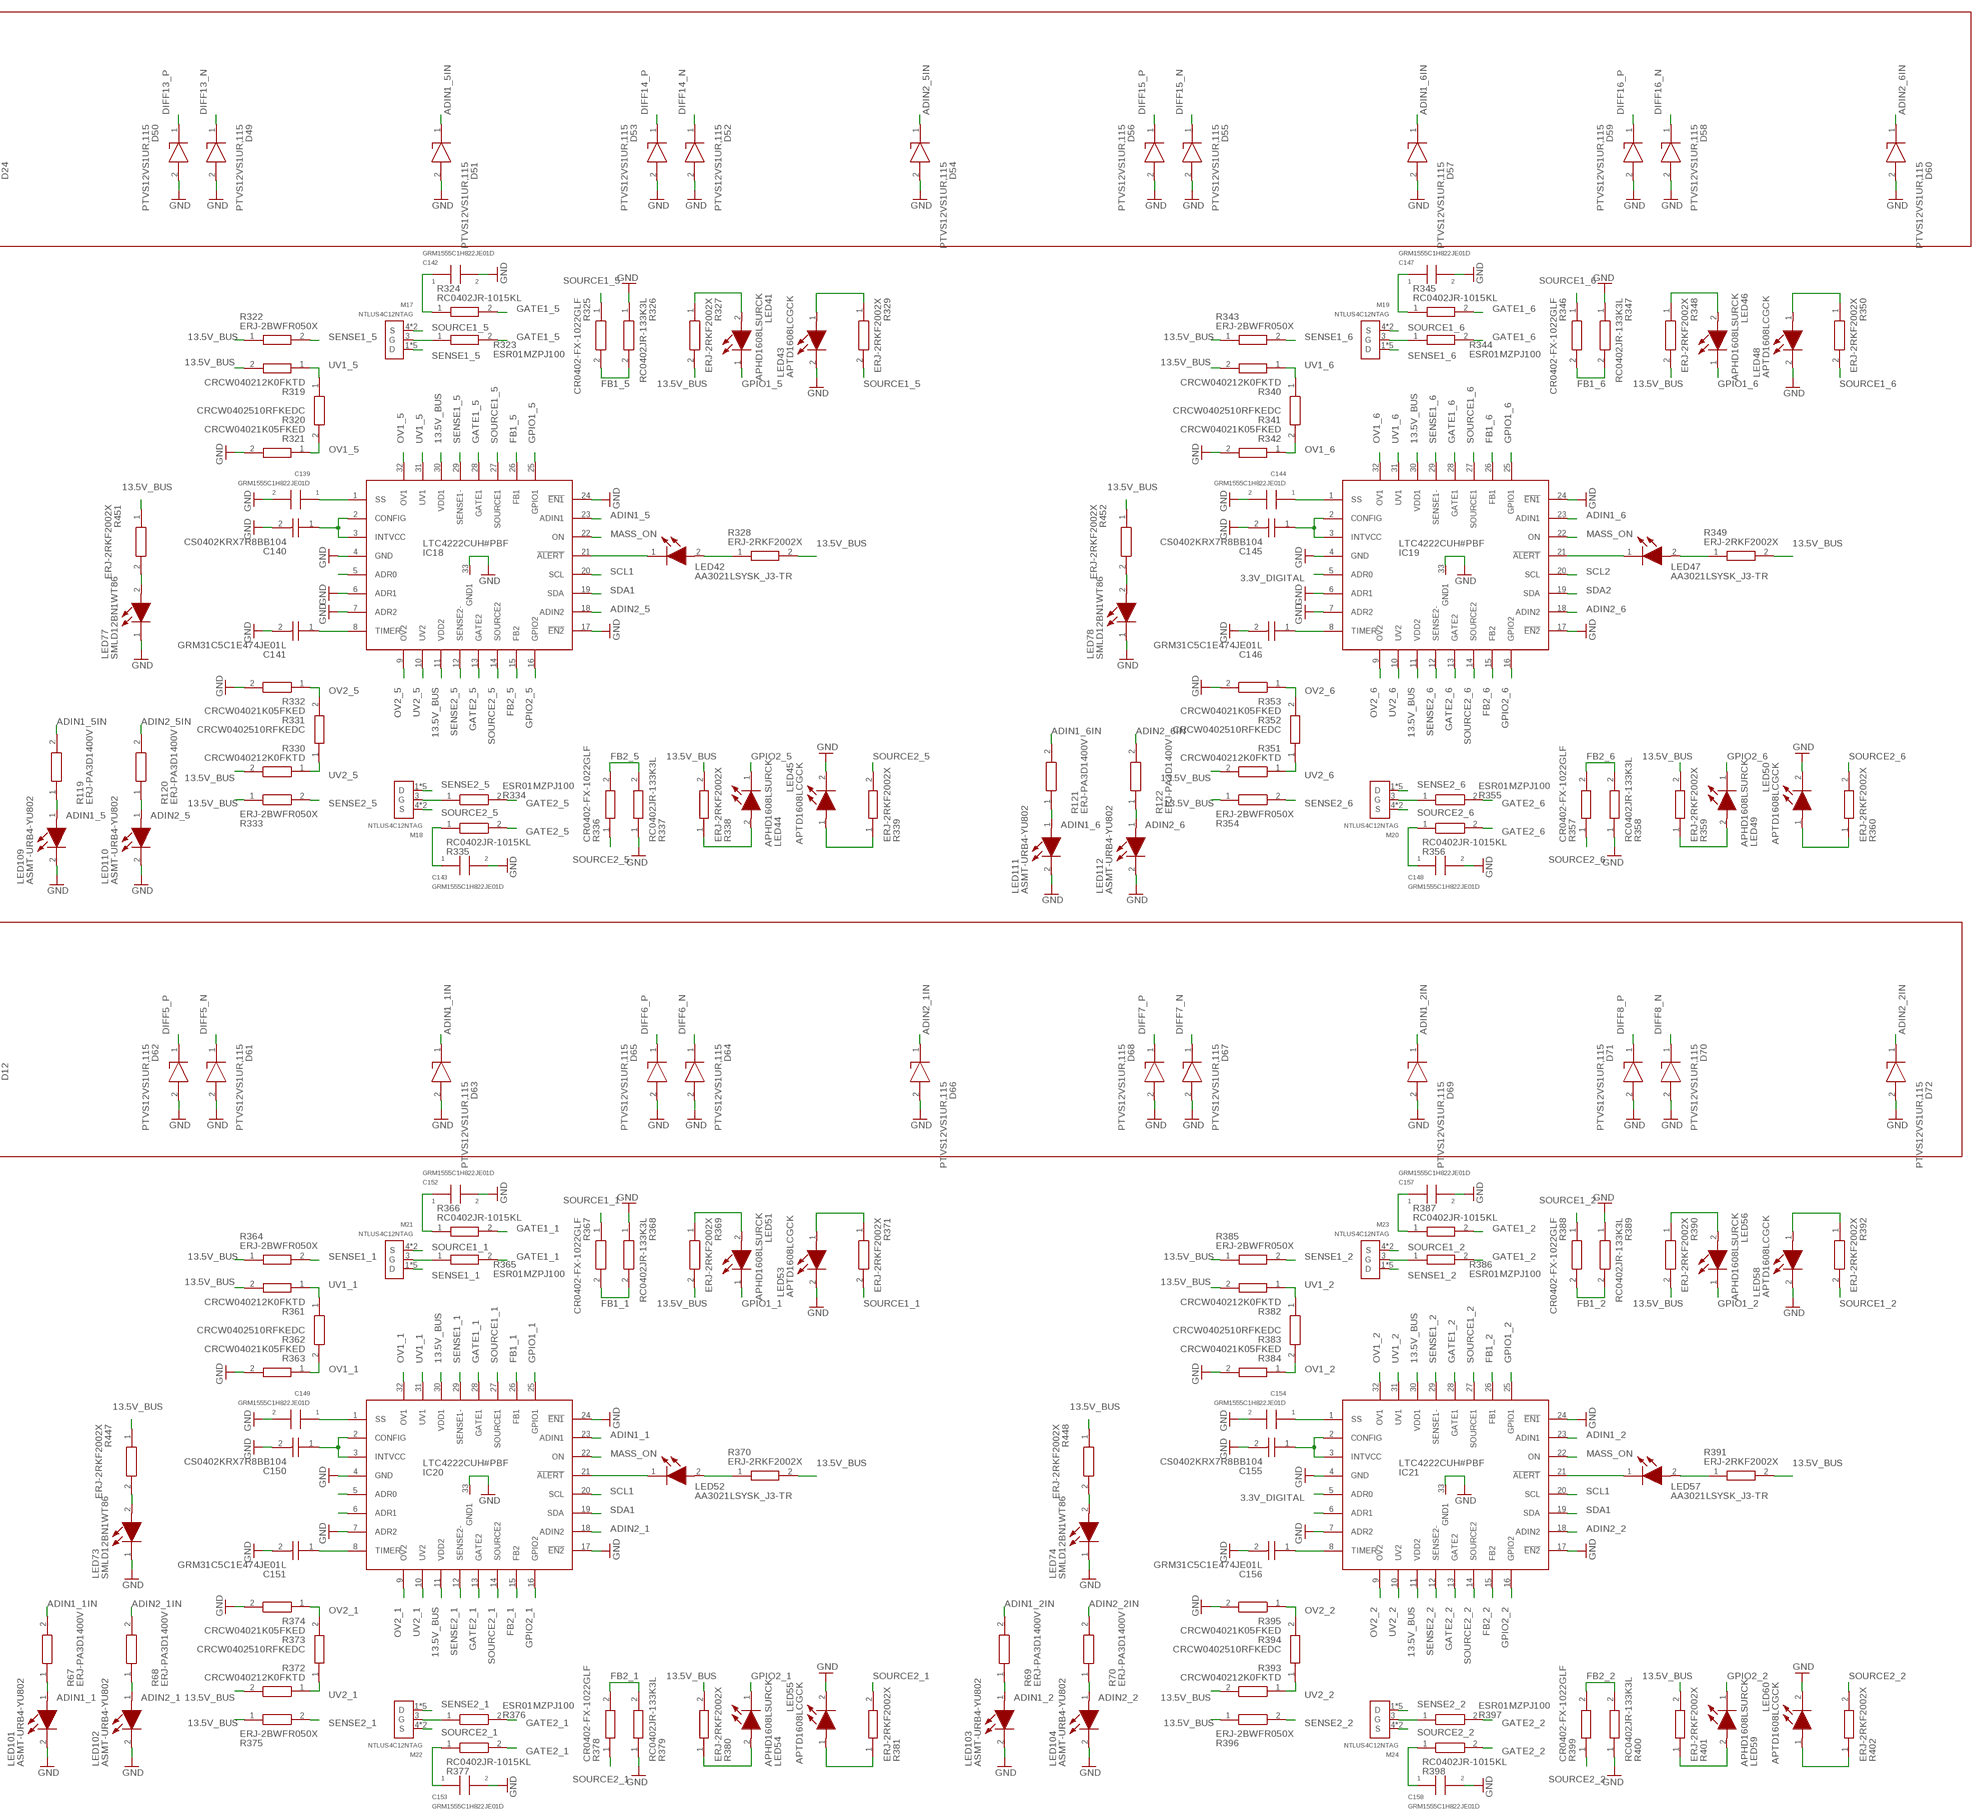
[diagram p19: schematic, sheet 11, part 6 of 6]
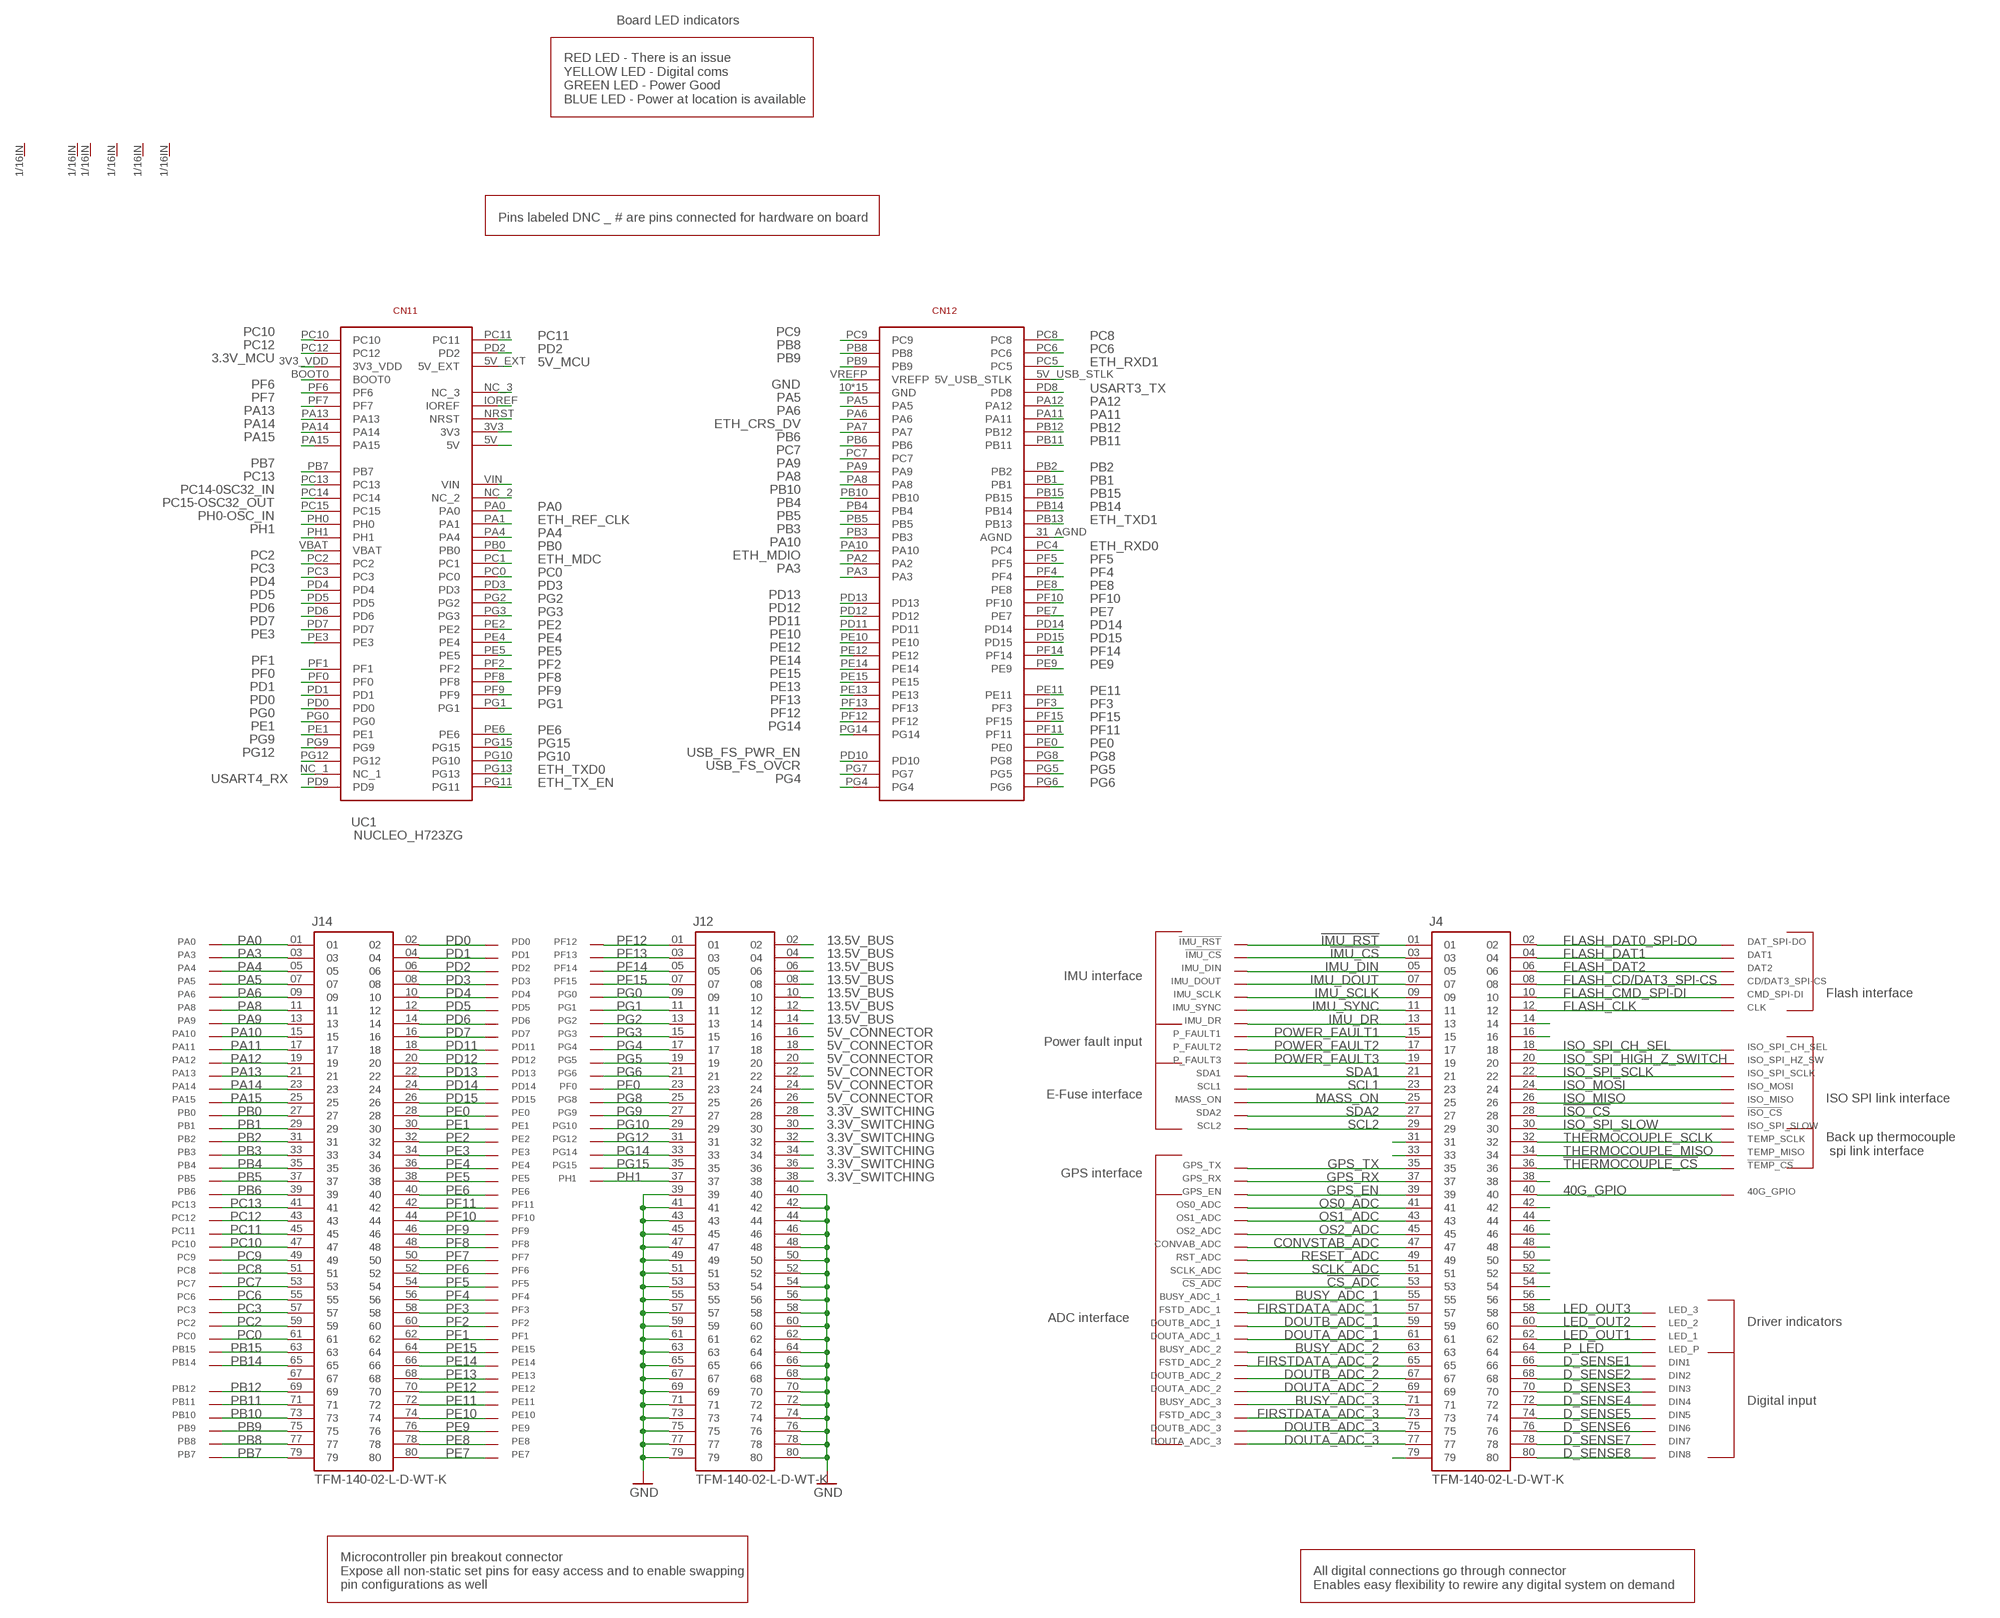
[diagram p20: schematic, sheet 12]

(export (version "E")
  (design (tool "Eeschema 10.0.6"))
  (components
    (comp (ref "C38")
      (value "CGA2B2C0G1H102J050BE")
      (footprint "eagle-import:CAPC1005X55N")
      (fields (field (name "MOUSER_PART_NUMBER") "810-CGA2B2C0G1H102J5"))
      (libsource (lib "eagle-import") (part "CGA2B2C0G1H102J050BE"))
    )
    (comp (ref "C40")
      (value "CGA2B2C0G1H102J050BE")
      (footprint "eagle-import:CAPC1005X55N")
      (fields (field (name "MOUSER_PART_NUMBER") "810-CGA2B2C0G1H102J5"))
      (libsource (lib "eagle-import") (part "CGA2B2C0G1H102J050BE"))
    )
    (comp (ref "C63")
      (value "CGA2B2C0G1H102J050BE")
      (footprint "eagle-import:CAPC1005X55N")
      (fields (field (name "MOUSER_PART_NUMBER") "810-CGA2B2C0G1H102J5"))
      (libsource (lib "eagle-import") (part "CGA2B2C0G1H102J050BE"))
    )
    (comp (ref "C64")
      (value "CGA2B2C0G1H102J050BE")
      (footprint "eagle-import:CAPC1005X55N")
      (fields (field (name "MOUSER_PART_NUMBER") "810-CGA2B2C0G1H102J5"))
      (libsource (lib "eagle-import") (part "CGA2B2C0G1H102J050BE"))
    )
    (comp (ref "C66")
      (value "CGA2B2C0G1H102J050BE")
      (footprint "eagle-import:CAPC1005X55N")
      (fields (field (name "MOUSER_PART_NUMBER") "810-CGA2B2C0G1H102J5"))
      (libsource (lib "eagle-import") (part "CGA2B2C0G1H102J050BE"))
    )
    (comp (ref "C67")
      (value "CGA2B2C0G1H102J050BE")
      (footprint "eagle-import:CAPC1005X55N")
      (fields (field (name "MOUSER_PART_NUMBER") "810-CGA2B2C0G1H102J5"))
      (libsource (lib "eagle-import") (part "CGA2B2C0G1H102J050BE"))
    )
    (comp (ref "C68")
      (value "CGA2B2C0G1H102J050BE")
      (footprint "eagle-import:CAPC1005X55N")
      (fields (field (name "MOUSER_PART_NUMBER") "810-CGA2B2C0G1H102J5"))
      (libsource (lib "eagle-import") (part "CGA2B2C0G1H102J050BE"))
    )
    (comp (ref "C69")
      (value "CGA2B2C0G1H102J050BE")
      (footprint "eagle-import:CAPC1005X55N")
      (fields (field (name "MOUSER_PART_NUMBER") "810-CGA2B2C0G1H102J5"))
      (libsource (lib "eagle-import") (part "CGA2B2C0G1H102J050BE"))
    )
    (comp (ref "D45")
      (value "RSR025N03HZGTL")
      (footprint "eagle-import:SOT95P280X100-3N")
      (fields (field (name "MOUSER_PART_NUMBER") "755-RSR025N03HZGTL"))
      (libsource (lib "eagle-import") (part "RSR025N03HZGTL"))
    )
    (comp (ref "D48")
      (value "RSR025N03HZGTL")
      (footprint "eagle-import:SOT95P280X100-3N")
      (fields (field (name "MOUSER_PART_NUMBER") "755-RSR025N03HZGTL"))
      (libsource (lib "eagle-import") (part "RSR025N03HZGTL"))
    )
    (comp (ref "D75")
      (value "RSR025N03HZGTL")
      (footprint "eagle-import:SOT95P280X100-3N")
      (fields (field (name "MOUSER_PART_NUMBER") "755-RSR025N03HZGTL"))
      (libsource (lib "eagle-import") (part "RSR025N03HZGTL"))
    )
    (comp (ref "D78")
      (value "RSR025N03HZGTL")
      (footprint "eagle-import:SOT95P280X100-3N")
      (fields (field (name "MOUSER_PART_NUMBER") "755-RSR025N03HZGTL"))
      (libsource (lib "eagle-import") (part "RSR025N03HZGTL"))
    )
    (comp (ref "D79")
      (value "RSR025N03HZGTL")
      (footprint "eagle-import:SOT95P280X100-3N")
      (fields (field (name "MOUSER_PART_NUMBER") "755-RSR025N03HZGTL"))
      (libsource (lib "eagle-import") (part "RSR025N03HZGTL"))
    )
    (comp (ref "D80")
      (value "RSR025N03HZGTL")
      (footprint "eagle-import:SOT95P280X100-3N")
      (fields (field (name "MOUSER_PART_NUMBER") "755-RSR025N03HZGTL"))
      (libsource (lib "eagle-import") (part "RSR025N03HZGTL"))
    )
    (comp (ref "D81")
      (value "RSR025N03HZGTL")
      (footprint "eagle-import:SOT95P280X100-3N")
      (fields (field (name "MOUSER_PART_NUMBER") "755-RSR025N03HZGTL"))
      (libsource (lib "eagle-import") (part "RSR025N03HZGTL"))
    )
    (comp (ref "D82")
      (value "RSR025N03HZGTL")
      (footprint "eagle-import:SOT95P280X100-3N")
      (fields (field (name "MOUSER_PART_NUMBER") "755-RSR025N03HZGTL"))
      (libsource (lib "eagle-import") (part "RSR025N03HZGTL"))
    )
    (comp (ref "D84")
      (value "RSR025N03HZGTL")
      (footprint "eagle-import:SOT95P280X100-3N")
      (fields (field (name "MOUSER_PART_NUMBER") "755-RSR025N03HZGTL"))
      (libsource (lib "eagle-import") (part "RSR025N03HZGTL"))
    )
    (comp (ref "D85")
      (value "RSR025N03HZGTL")
      (footprint "eagle-import:SOT95P280X100-3N")
      (fields (field (name "MOUSER_PART_NUMBER") "755-RSR025N03HZGTL"))
      (libsource (lib "eagle-import") (part "RSR025N03HZGTL"))
    )
    (comp (ref "D86")
      (value "RSR025N03HZGTL")
      (footprint "eagle-import:SOT95P280X100-3N")
      (fields (field (name "MOUSER_PART_NUMBER") "755-RSR025N03HZGTL"))
      (libsource (lib "eagle-import") (part "RSR025N03HZGTL"))
    )
    (comp (ref "D87")
      (value "RSR025N03HZGTL")
      (footprint "eagle-import:SOT95P280X100-3N")
      (fields (field (name "MOUSER_PART_NUMBER") "755-RSR025N03HZGTL"))
      (libsource (lib "eagle-import") (part "RSR025N03HZGTL"))
    )
    (comp (ref "J1")
      (value "SAMTEC-SMM-104-02-X-DJ")
      (footprint "eagle-import:SAMTEC-SMM-104-02-X-D")
      (libsource (lib "eagle-import") (part "SAMTEC-SMM-104-02-X-DJ"))
    )
    (comp (ref "LED85")
      (value "AA3021LSYSK_J3-TR")
      (footprint "eagle-import:AA3021LSYSKJ3TR")
      (fields
        (field (name "MANUFACTURER_PART_NUMBER") "AA3021LSYSK/J3-TR")
        (field (name "MOUSER_PART_NUMBER") "604-AA3021LSYSK/J3TR")
      )
      (libsource (lib "eagle-import") (part "AA3021LSYSK_J3-TR"))
    )
    (comp (ref "LED86")
      (value "AA3021LSYSK_J3-TR")
      (footprint "eagle-import:AA3021LSYSKJ3TR")
      (fields
        (field (name "MANUFACTURER_PART_NUMBER") "AA3021LSYSK/J3-TR")
        (field (name "MOUSER_PART_NUMBER") "604-AA3021LSYSK/J3TR")
      )
      (libsource (lib "eagle-import") (part "AA3021LSYSK_J3-TR"))
    )
    (comp (ref "LED87")
      (value "AA3021LSYSK_J3-TR")
      (footprint "eagle-import:AA3021LSYSKJ3TR")
      (fields
        (field (name "MANUFACTURER_PART_NUMBER") "AA3021LSYSK/J3-TR")
        (field (name "MOUSER_PART_NUMBER") "604-AA3021LSYSK/J3TR")
      )
      (libsource (lib "eagle-import") (part "AA3021LSYSK_J3-TR"))
    )
    (comp (ref "LED88")
      (value "AA3021LSYSK_J3-TR")
      (footprint "eagle-import:AA3021LSYSKJ3TR")
      (fields
        (field (name "MANUFACTURER_PART_NUMBER") "AA3021LSYSK/J3-TR")
        (field (name "MOUSER_PART_NUMBER") "604-AA3021LSYSK/J3TR")
      )
      (libsource (lib "eagle-import") (part "AA3021LSYSK_J3-TR"))
    )
    (comp (ref "LED89")
      (value "AA3021LSYSK_J3-TR")
      (footprint "eagle-import:AA3021LSYSKJ3TR")
      (fields
        (field (name "MANUFACTURER_PART_NUMBER") "AA3021LSYSK/J3-TR")
        (field (name "MOUSER_PART_NUMBER") "604-AA3021LSYSK/J3TR")
      )
      (libsource (lib "eagle-import") (part "AA3021LSYSK_J3-TR"))
    )
    (comp (ref "LED90")
      (value "AA3021LSYSK_J3-TR")
      (footprint "eagle-import:AA3021LSYSKJ3TR")
      (fields
        (field (name "MANUFACTURER_PART_NUMBER") "AA3021LSYSK/J3-TR")
        (field (name "MOUSER_PART_NUMBER") "604-AA3021LSYSK/J3TR")
      )
      (libsource (lib "eagle-import") (part "AA3021LSYSK_J3-TR"))
    )
    (comp (ref "LED91")
      (value "AA3021LSYSK_J3-TR")
      (footprint "eagle-import:AA3021LSYSKJ3TR")
      (fields
        (field (name "MANUFACTURER_PART_NUMBER") "AA3021LSYSK/J3-TR")
        (field (name "MOUSER_PART_NUMBER") "604-AA3021LSYSK/J3TR")
      )
      (libsource (lib "eagle-import") (part "AA3021LSYSK_J3-TR"))
    )
    (comp (ref "LED92")
      (value "AA3021LSYSK_J3-TR")
      (footprint "eagle-import:AA3021LSYSKJ3TR")
      (fields
        (field (name "MANUFACTURER_PART_NUMBER") "AA3021LSYSK/J3-TR")
        (field (name "MOUSER_PART_NUMBER") "604-AA3021LSYSK/J3TR")
      )
      (libsource (lib "eagle-import") (part "AA3021LSYSK_J3-TR"))
    )
    (comp (ref "LED93")
      (value "AA3021LSYSK_J3-TR")
      (footprint "eagle-import:AA3021LSYSKJ3TR")
      (fields
        (field (name "MANUFACTURER_PART_NUMBER") "AA3021LSYSK/J3-TR")
        (field (name "MOUSER_PART_NUMBER") "604-AA3021LSYSK/J3TR")
      )
      (libsource (lib "eagle-import") (part "AA3021LSYSK_J3-TR"))
    )
    (comp (ref "LED94")
      (value "AA3021LSYSK_J3-TR")
      (footprint "eagle-import:AA3021LSYSKJ3TR")
      (fields
        (field (name "MANUFACTURER_PART_NUMBER") "AA3021LSYSK/J3-TR")
        (field (name "MOUSER_PART_NUMBER") "604-AA3021LSYSK/J3TR")
      )
      (libsource (lib "eagle-import") (part "AA3021LSYSK_J3-TR"))
    )
    (comp (ref "LED95")
      (value "AA3021LSYSK_J3-TR")
      (footprint "eagle-import:AA3021LSYSKJ3TR")
      (fields
        (field (name "MANUFACTURER_PART_NUMBER") "AA3021LSYSK/J3-TR")
        (field (name "MOUSER_PART_NUMBER") "604-AA3021LSYSK/J3TR")
      )
      (libsource (lib "eagle-import") (part "AA3021LSYSK_J3-TR"))
    )
    (comp (ref "LED96")
      (value "AA3021LSYSK_J3-TR")
      (footprint "eagle-import:AA3021LSYSKJ3TR")
      (fields
        (field (name "MANUFACTURER_PART_NUMBER") "AA3021LSYSK/J3-TR")
        (field (name "MOUSER_PART_NUMBER") "604-AA3021LSYSK/J3TR")
      )
      (libsource (lib "eagle-import") (part "AA3021LSYSK_J3-TR"))
    )
    (comp (ref "R33")
      (value "MCS0402MD1002DE000")
      (footprint "eagle-import:RESC1005X37N")
      (fields (field (name "MOUSER_PART_NUMBER") "594-MCS0402MD1002DE0"))
      (libsource (lib "eagle-import") (part "MCS0402MD1002DE000"))
    )
    (comp (ref "R34")
      (value "MCS04020C1001FE000")
      (footprint "eagle-import:RESC1005X37N")
      (fields (field (name "MOUSER_PART_NUMBER") "594-MCS04020C1001FE0"))
      (libsource (lib "eagle-import") (part "MCS04020C1001FE000"))
    )
    (comp (ref "R35")
      (value "MCS0402MD1002DE000")
      (footprint "eagle-import:RESC1005X37N")
      (fields (field (name "MOUSER_PART_NUMBER") "594-MCS0402MD1002DE0"))
      (libsource (lib "eagle-import") (part "MCS0402MD1002DE000"))
    )
    (comp (ref "R36")
      (value "MCS04020C1001FE000")
      (footprint "eagle-import:RESC1005X37N")
      (fields (field (name "MOUSER_PART_NUMBER") "594-MCS04020C1001FE0"))
      (libsource (lib "eagle-import") (part "MCS04020C1001FE000"))
    )
    (comp (ref "R37")
      (value "MCS0402MD1002DE000")
      (footprint "eagle-import:RESC1005X37N")
      (fields (field (name "MOUSER_PART_NUMBER") "594-MCS0402MD1002DE0"))
      (libsource (lib "eagle-import") (part "MCS0402MD1002DE000"))
    )
    (comp (ref "R38")
      (value "MCS04020C1001FE000")
      (footprint "eagle-import:RESC1005X37N")
      (fields (field (name "MOUSER_PART_NUMBER") "594-MCS04020C1001FE0"))
      (libsource (lib "eagle-import") (part "MCS04020C1001FE000"))
    )
    (comp (ref "R39")
      (value "MCS0402MD1002DE000")
      (footprint "eagle-import:RESC1005X37N")
      (fields (field (name "MOUSER_PART_NUMBER") "594-MCS0402MD1002DE0"))
      (libsource (lib "eagle-import") (part "MCS0402MD1002DE000"))
    )
    (comp (ref "R40")
      (value "MCS04020C1001FE000")
      (footprint "eagle-import:RESC1005X37N")
      (fields (field (name "MOUSER_PART_NUMBER") "594-MCS04020C1001FE0"))
      (libsource (lib "eagle-import") (part "MCS04020C1001FE000"))
    )
    (comp (ref "R41")
      (value "ERA-2AKD240X")
      (footprint "eagle-import:ERA2A_(0402)")
      (fields (field (name "MOUSER_PART_NUMBER") "667-ERA-2AKD240X"))
      (libsource (lib "eagle-import") (part "ERA-2AKD240X"))
    )
    (comp (ref "R42")
      (value "MCS04020C1001FE000")
      (footprint "eagle-import:RESC1005X37N")
      (fields (field (name "MOUSER_PART_NUMBER") "594-MCS04020C1001FE0"))
      (libsource (lib "eagle-import") (part "MCS04020C1001FE000"))
    )
    (comp (ref "R43")
      (value "MCS0402MD1002DE000")
      (footprint "eagle-import:RESC1005X37N")
      (fields (field (name "MOUSER_PART_NUMBER") "594-MCS0402MD1002DE0"))
      (libsource (lib "eagle-import") (part "MCS0402MD1002DE000"))
    )
    (comp (ref "R44")
      (value "MCS04020C1001FE000")
      (footprint "eagle-import:RESC1005X37N")
      (fields (field (name "MOUSER_PART_NUMBER") "594-MCS04020C1001FE0"))
      (libsource (lib "eagle-import") (part "MCS04020C1001FE000"))
    )
    (comp (ref "R45")
      (value "MCS0402MD1002DE000")
      (footprint "eagle-import:RESC1005X37N")
      (fields (field (name "MOUSER_PART_NUMBER") "594-MCS0402MD1002DE0"))
      (libsource (lib "eagle-import") (part "MCS0402MD1002DE000"))
    )
    (comp (ref "R46")
      (value "MCS04020C1001FE000")
      (footprint "eagle-import:RESC1005X37N")
      (fields (field (name "MOUSER_PART_NUMBER") "594-MCS04020C1001FE0"))
      (libsource (lib "eagle-import") (part "MCS04020C1001FE000"))
    )
    (comp (ref "R47")
      (value "MCS0402MD1002DE000")
      (footprint "eagle-import:RESC1005X37N")
      (fields (field (name "MOUSER_PART_NUMBER") "594-MCS0402MD1002DE0"))
      (libsource (lib "eagle-import") (part "MCS0402MD1002DE000"))
    )
    (comp (ref "R48")
      (value "MCS04020C1001FE000")
      (footprint "eagle-import:RESC1005X37N")
      (fields (field (name "MOUSER_PART_NUMBER") "594-MCS04020C1001FE0"))
      (libsource (lib "eagle-import") (part "MCS04020C1001FE000"))
    )
    (comp (ref "R49")
      (value "MCS0402MD1002DE000")
      (footprint "eagle-import:RESC1005X37N")
      (fields (field (name "MOUSER_PART_NUMBER") "594-MCS0402MD1002DE0"))
      (libsource (lib "eagle-import") (part "MCS0402MD1002DE000"))
    )
    (comp (ref "R50")
      (value "MCS04020C1001FE000")
      (footprint "eagle-import:RESC1005X37N")
      (fields (field (name "MOUSER_PART_NUMBER") "594-MCS04020C1001FE0"))
      (libsource (lib "eagle-import") (part "MCS04020C1001FE000"))
    )
    (comp (ref "R51")
      (value "ERA-2AKD240X")
      (footprint "eagle-import:ERA2A_(0402)")
      (fields (field (name "MOUSER_PART_NUMBER") "667-ERA-2AKD240X"))
      (libsource (lib "eagle-import") (part "ERA-2AKD240X"))
    )
    (comp (ref "R52")
      (value "MCS04020C1001FE000")
      (footprint "eagle-import:RESC1005X37N")
      (fields (field (name "MOUSER_PART_NUMBER") "594-MCS04020C1001FE0"))
      (libsource (lib "eagle-import") (part "MCS04020C1001FE000"))
    )
    (comp (ref "R53")
      (value "ERA-2AKD240X")
      (footprint "eagle-import:ERA2A_(0402)")
      (fields (field (name "MOUSER_PART_NUMBER") "667-ERA-2AKD240X"))
      (libsource (lib "eagle-import") (part "ERA-2AKD240X"))
    )
    (comp (ref "R54")
      (value "MCS04020C1001FE000")
      (footprint "eagle-import:RESC1005X37N")
      (fields (field (name "MOUSER_PART_NUMBER") "594-MCS04020C1001FE0"))
      (libsource (lib "eagle-import") (part "MCS04020C1001FE000"))
    )
    (comp (ref "R55")
      (value "ERA-2AKD240X")
      (footprint "eagle-import:ERA2A_(0402)")
      (fields (field (name "MOUSER_PART_NUMBER") "667-ERA-2AKD240X"))
      (libsource (lib "eagle-import") (part "ERA-2AKD240X"))
    )
    (comp (ref "R56")
      (value "MCS04020C1001FE000")
      (footprint "eagle-import:RESC1005X37N")
      (fields (field (name "MOUSER_PART_NUMBER") "594-MCS04020C1001FE0"))
      (libsource (lib "eagle-import") (part "MCS04020C1001FE000"))
    )
    (comp (ref "R459")
      (value "MCS0402MD1002DE000")
      (footprint "eagle-import:RESC1005X37N")
      (fields (field (name "MOUSER_PART_NUMBER") "594-MCS0402MD1002DE0"))
      (libsource (lib "eagle-import") (part "MCS0402MD1002DE000"))
    )
    (comp (ref "R460")
      (value "MCS0402MD1002DE000")
      (footprint "eagle-import:RESC1005X37N")
      (fields (field (name "MOUSER_PART_NUMBER") "594-MCS0402MD1002DE0"))
      (libsource (lib "eagle-import") (part "MCS0402MD1002DE000"))
    )
    (comp (ref "R461")
      (value "MCS0402MD1002DE000")
      (footprint "eagle-import:RESC1005X37N")
      (fields (field (name "MOUSER_PART_NUMBER") "594-MCS0402MD1002DE0"))
      (libsource (lib "eagle-import") (part "MCS0402MD1002DE000"))
    )
    (comp (ref "R462")
      (value "MCS0402MD1002DE000")
      (footprint "eagle-import:RESC1005X37N")
      (fields (field (name "MOUSER_PART_NUMBER") "594-MCS0402MD1002DE0"))
      (libsource (lib "eagle-import") (part "MCS0402MD1002DE000"))
    )
    (comp (ref "R463")
      (value "MCS0402MD1002DE000")
      (footprint "eagle-import:RESC1005X37N")
      (fields (field (name "MOUSER_PART_NUMBER") "594-MCS0402MD1002DE0"))
      (libsource (lib "eagle-import") (part "MCS0402MD1002DE000"))
    )
    (comp (ref "R464")
      (value "MCS0402MD1002DE000")
      (footprint "eagle-import:RESC1005X37N")
      (fields (field (name "MOUSER_PART_NUMBER") "594-MCS0402MD1002DE0"))
      (libsource (lib "eagle-import") (part "MCS0402MD1002DE000"))
    )
    (comp (ref "R465")
      (value "MCS0402MD1002DE000")
      (footprint "eagle-import:RESC1005X37N")
      (fields (field (name "MOUSER_PART_NUMBER") "594-MCS0402MD1002DE0"))
      (libsource (lib "eagle-import") (part "MCS0402MD1002DE000"))
    )
    (comp (ref "R466")
      (value "MCS0402MD1002DE000")
      (footprint "eagle-import:RESC1005X37N")
      (fields (field (name "MOUSER_PART_NUMBER") "594-MCS0402MD1002DE0"))
      (libsource (lib "eagle-import") (part "MCS0402MD1002DE000"))
    )
    (comp (ref "R467")
      (value "MCS0402MD1002DE000")
      (footprint "eagle-import:RESC1005X37N")
      (fields (field (name "MOUSER_PART_NUMBER") "594-MCS0402MD1002DE0"))
      (libsource (lib "eagle-import") (part "MCS0402MD1002DE000"))
    )
    (comp (ref "R468")
      (value "MCS0402MD1002DE000")
      (footprint "eagle-import:RESC1005X37N")
      (fields (field (name "MOUSER_PART_NUMBER") "594-MCS0402MD1002DE0"))
      (libsource (lib "eagle-import") (part "MCS0402MD1002DE000"))
    )
    (comp (ref "R469")
      (value "MCS0402MD1002DE000")
      (footprint "eagle-import:RESC1005X37N")
      (fields (field (name "MOUSER_PART_NUMBER") "594-MCS0402MD1002DE0"))
      (libsource (lib "eagle-import") (part "MCS0402MD1002DE000"))
    )
    (comp (ref "R470")
      (value "MCS0402MD1002DE000")
      (footprint "eagle-import:RESC1005X37N")
      (fields (field (name "MOUSER_PART_NUMBER") "594-MCS0402MD1002DE0"))
      (libsource (lib "eagle-import") (part "MCS0402MD1002DE000"))
    )
    (comp (ref "C27")
      (value "C3216X7R1E106K160AE")
      (footprint "eagle-import:C3216_COMMERCIAL")
      (fields (field (name "MOUSER_PART_NUMBER") "810-C3216X7R1E106KST"))
      (libsource (lib "eagle-import") (part "C3216X7R1E106K160AE"))
    )
    (comp (ref "C96")
      (value "C3216X7R1E106K160AE")
      (footprint "eagle-import:C3216_COMMERCIAL")
      (fields (field (name "MOUSER_PART_NUMBER") "810-C3216X7R1E106KST"))
      (libsource (lib "eagle-import") (part "C3216X7R1E106K160AE"))
    )
    (comp (ref "C98")
      (value "C3216X7R1E106K160AE")
      (footprint "eagle-import:C3216_COMMERCIAL")
      (fields (field (name "MOUSER_PART_NUMBER") "810-C3216X7R1E106KST"))
      (libsource (lib "eagle-import") (part "C3216X7R1E106K160AE"))
    )
    (comp (ref "C100")
      (value "C3216X7R1E106K160AE")
      (footprint "eagle-import:C3216_COMMERCIAL")
      (fields (field (name "MOUSER_PART_NUMBER") "810-C3216X7R1E106KST"))
      (libsource (lib "eagle-import") (part "C3216X7R1E106K160AE"))
    )
    (comp (ref "C102")
      (value "C3216X7R1E106K160AE")
      (footprint "eagle-import:C3216_COMMERCIAL")
      (fields (field (name "MOUSER_PART_NUMBER") "810-C3216X7R1E106KST"))
      (libsource (lib "eagle-import") (part "C3216X7R1E106K160AE"))
    )
    (comp (ref "C103")
      (value "C3216X7R1E106K160AE")
      (footprint "eagle-import:C3216_COMMERCIAL")
      (fields (field (name "MOUSER_PART_NUMBER") "810-C3216X7R1E106KST"))
      (libsource (lib "eagle-import") (part "C3216X7R1E106K160AE"))
    )
    (comp (ref "C104")
      (value "C3216X7R1E106K160AE")
      (footprint "eagle-import:C3216_COMMERCIAL")
      (fields (field (name "MOUSER_PART_NUMBER") "810-C3216X7R1E106KST"))
      (libsource (lib "eagle-import") (part "C3216X7R1E106K160AE"))
    )
    (comp (ref "C105")
      (value "C3216X7R1E106K160AE")
      (footprint "eagle-import:C3216_COMMERCIAL")
      (fields (field (name "MOUSER_PART_NUMBER") "810-C3216X7R1E106KST"))
      (libsource (lib "eagle-import") (part "C3216X7R1E106K160AE"))
    )
    (comp (ref "C106")
      (value "C3216X7R1E106K160AE")
      (footprint "eagle-import:C3216_COMMERCIAL")
      (fields (field (name "MOUSER_PART_NUMBER") "810-C3216X7R1E106KST"))
      (libsource (lib "eagle-import") (part "C3216X7R1E106K160AE"))
    )
    (comp (ref "C108")
      (value "C3216X7R1E106K160AE")
      (footprint "eagle-import:C3216_COMMERCIAL")
      (fields (field (name "MOUSER_PART_NUMBER") "810-C3216X7R1E106KST"))
      (libsource (lib "eagle-import") (part "C3216X7R1E106K160AE"))
    )
    (comp (ref "C109")
      (value "C3216X7R1E106K160AE")
      (footprint "eagle-import:C3216_COMMERCIAL")
      (fields (field (name "MOUSER_PART_NUMBER") "810-C3216X7R1E106KST"))
      (libsource (lib "eagle-import") (part "C3216X7R1E106K160AE"))
    )
    (comp (ref "C110")
      (value "C3216X7R1E106K160AE")
      (footprint "eagle-import:C3216_COMMERCIAL")
      (fields (field (name "MOUSER_PART_NUMBER") "810-C3216X7R1E106KST"))
      (libsource (lib "eagle-import") (part "C3216X7R1E106K160AE"))
    )
    (comp (ref "C111")
      (value "GRT21BC8YA475KE13K")
      (footprint "eagle-import:CAPC2012X135N")
      (fields (field (name "MOUSER_PART_NUMBER") "81-GRT21BC8YA475KE3K"))
      (libsource (lib "eagle-import") (part "GRT21BC8YA475KE13K"))
    )
    (comp (ref "C173")
      (value "CGA4J3X7R1H105K125AB")
      (footprint "eagle-import:CAPC2012X145N")
      (fields (field (name "MOUSER_PART_NUMBER") "810-CGA4J3X7R1H105K "))
      (libsource (lib "eagle-import") (part "CGA4J3X7R1H105K125AB"))
    )
    (comp (ref "C174")
      (value "CGA4J3X7R1H105K125AB")
      (footprint "eagle-import:CAPC2012X145N")
      (fields (field (name "MOUSER_PART_NUMBER") "810-CGA4J3X7R1H105K "))
      (libsource (lib "eagle-import") (part "CGA4J3X7R1H105K125AB"))
    )
    (comp (ref "IC5")
      (value "LP38692SDX-5.0_NOPB")
      (footprint "eagle-import:SON95P300X300X80-7N")
      (fields
        (field (name "MANUFACTURER_PART_NUMBER") "LP38692SDX-5.0/NOPB")
        (field (name "MOUSER_PART_NUMBER") "926-LP38692SDX50NOPB")
      )
      (libsource (lib "eagle-import") (part "LP38692SDX-5.0_NOPB"))
    )
    (comp (ref "IC6")
      (value "LP38692SDX-5.0_NOPB")
      (footprint "eagle-import:SON95P300X300X80-7N")
      (fields
        (field (name "MANUFACTURER_PART_NUMBER") "LP38692SDX-5.0/NOPB")
        (field (name "MOUSER_PART_NUMBER") "926-LP38692SDX50NOPB")
      )
      (libsource (lib "eagle-import") (part "LP38692SDX-5.0_NOPB"))
    )
    (comp (ref "IC7")
      (value "LDL1117S33R")
      (footprint "eagle-import:SOT230P700X180-4N")
      (fields (field (name "MOUSER_PART_NUMBER") "511-LDL1117S33R"))
      (libsource (lib "eagle-import") (part "LDL1117S33R"))
    )
    (comp (ref "IC8")
      (value "LDL1117S33R")
      (footprint "eagle-import:SOT230P700X180-4N")
      (fields (field (name "MOUSER_PART_NUMBER") "511-LDL1117S33R"))
      (libsource (lib "eagle-import") (part "LDL1117S33R"))
    )
    (comp (ref "IC9")
      (value "LP38692SDX-5.0_NOPB")
      (footprint "eagle-import:SON95P300X300X80-7N")
      (fields
        (field (name "MANUFACTURER_PART_NUMBER") "LP38692SDX-5.0/NOPB")
        (field (name "MOUSER_PART_NUMBER") "926-LP38692SDX50NOPB")
      )
      (libsource (lib "eagle-import") (part "LP38692SDX-5.0_NOPB"))
    )
    (comp (ref "IC10")
      (value "LDL1117S33R")
      (footprint "eagle-import:SOT230P700X180-4N")
      (fields (field (name "MOUSER_PART_NUMBER") "511-LDL1117S33R"))
      (libsource (lib "eagle-import") (part "LDL1117S33R"))
    )
    (comp (ref "IC34")
      (value "MAX889TESA+")
      (footprint "eagle-import:SOIC127P600X175-8N")
      (fields (field (name "MOUSER_PART_NUMBER") "700-MAX889TESA"))
      (libsource (lib "eagle-import") (part "MAX889TESA+"))
    )
    (comp (ref "J2")
      (value "SAMTEC-CLP-106-02-X-DJ")
      (footprint "eagle-import:SAMTEC-CLP-106-02-X-D")
      (libsource (lib "eagle-import") (part "SAMTEC-CLP-106-02-X-DJ"))
    )
    (comp (ref "C26")
      (value "GRM31C5C1E474JE01L")
      (footprint "eagle-import:CAPC3216X180N")
      (fields (field (name "MOUSER_PART_NUMBER") "81-GRM31C5C1E474JE1L"))
      (libsource (lib "eagle-import") (part "GRM31C5C1E474JE01L"))
    )
    (comp (ref "C189")
      (value "GRM31C5C1E474JE01L")
      (footprint "eagle-import:CAPC3216X180N")
      (fields (field (name "MOUSER_PART_NUMBER") "81-GRM31C5C1E474JE1L"))
      (libsource (lib "eagle-import") (part "GRM31C5C1E474JE01L"))
    )
    (comp (ref "C191")
      (value "GRM31C5C1E474JE01L")
      (footprint "eagle-import:CAPC3216X180N")
      (fields (field (name "MOUSER_PART_NUMBER") "81-GRM31C5C1E474JE1L"))
      (libsource (lib "eagle-import") (part "GRM31C5C1E474JE01L"))
    )
    (comp (ref "IC24")
      (value "NCS21911SN2T1G")
      (footprint "eagle-import:SOT95P275X110-5N")
      (fields (field (name "MOUSER_PART_NUMBER") "863-NCS21911SN2T1G"))
      (libsource (lib "eagle-import") (part "NCS21911SN2T1G"))
    )
    (comp (ref "IC25")
      (value "NCS21911SN2T1G")
      (footprint "eagle-import:SOT95P275X110-5N")
      (fields (field (name "MOUSER_PART_NUMBER") "863-NCS21911SN2T1G"))
      (libsource (lib "eagle-import") (part "NCS21911SN2T1G"))
    )
    (comp (ref "IC26")
      (value "NCS21911SN2T1G")
      (footprint "eagle-import:SOT95P275X110-5N")
      (fields (field (name "MOUSER_PART_NUMBER") "863-NCS21911SN2T1G"))
      (libsource (lib "eagle-import") (part "NCS21911SN2T1G"))
    )
    (comp (ref "R472")
      (value "GMR100HTCFAR100")
      (footprint "eagle-import:RESC6432X55N")
      (fields (field (name "MOUSER_PART_NUMBER") "755-GMR100HTCFAR100"))
      (libsource (lib "eagle-import") (part "GMR100HTCFAR100"))
    )
    (comp (ref "R473")
      (value "RC0402JR-133K3L")
      (footprint "eagle-import:RESC1005X40N")
      (fields (field (name "MOUSER_PART_NUMBER") "603-RC0402JR-133K3L"))
      (libsource (lib "eagle-import") (part "RC0402JR-133K3L"))
    )
    (comp (ref "R474")
      (value "RC0402JR-133K3L")
      (footprint "eagle-import:RESC1005X40N")
      (fields (field (name "MOUSER_PART_NUMBER") "603-RC0402JR-133K3L"))
      (libsource (lib "eagle-import") (part "RC0402JR-133K3L"))
    )
    (comp (ref "R475")
      (value "RC0402JR-133K3L")
      (footprint "eagle-import:RESC1005X40N")
      (fields (field (name "MOUSER_PART_NUMBER") "603-RC0402JR-133K3L"))
      (libsource (lib "eagle-import") (part "RC0402JR-133K3L"))
    )
    (comp (ref "R476")
      (value "RC0402JR-133K3L")
      (footprint "eagle-import:RESC1005X40N")
      (fields (field (name "MOUSER_PART_NUMBER") "603-RC0402JR-133K3L"))
      (libsource (lib "eagle-import") (part "RC0402JR-133K3L"))
    )
    (comp (ref "R477")
      (value "MCS04020C1001FE000")
      (footprint "eagle-import:RESC1005X37N")
      (fields (field (name "MOUSER_PART_NUMBER") "594-MCS04020C1001FE0"))
      (libsource (lib "eagle-import") (part "MCS04020C1001FE000"))
    )
    (comp (ref "R478")
      (value "MCS04020C1001FE000")
      (footprint "eagle-import:RESC1005X37N")
      (fields (field (name "MOUSER_PART_NUMBER") "594-MCS04020C1001FE0"))
      (libsource (lib "eagle-import") (part "MCS04020C1001FE000"))
    )
    (comp (ref "R479")
      (value "CRCW040212K0FKTD")
      (footprint "eagle-import:RESC1005X40N")
      (fields (field (name "MOUSER_PART_NUMBER") "71-CRCW0402-12K"))
      (libsource (lib "eagle-import") (part "CRCW040212K0FKTD"))
    )
    (comp (ref "R480")
      (value "CR0402-FX-1022GLF")
      (footprint "eagle-import:RESC1005X40N")
      (fields (field (name "MOUSER_PART_NUMBER") "652-CR0402-FX1022GLF"))
      (libsource (lib "eagle-import") (part "CR0402-FX-1022GLF"))
    )
    (comp (ref "R481")
      (value "GMR100HTCFAR100")
      (footprint "eagle-import:RESC6432X55N")
      (fields (field (name "MOUSER_PART_NUMBER") "755-GMR100HTCFAR100"))
      (libsource (lib "eagle-import") (part "GMR100HTCFAR100"))
    )
    (comp (ref "R482")
      (value "RC0402JR-133K3L")
      (footprint "eagle-import:RESC1005X40N")
      (fields (field (name "MOUSER_PART_NUMBER") "603-RC0402JR-133K3L"))
      (libsource (lib "eagle-import") (part "RC0402JR-133K3L"))
    )
    (comp (ref "R483")
      (value "RC0402JR-133K3L")
      (footprint "eagle-import:RESC1005X40N")
      (fields (field (name "MOUSER_PART_NUMBER") "603-RC0402JR-133K3L"))
      (libsource (lib "eagle-import") (part "RC0402JR-133K3L"))
    )
    (comp (ref "R484")
      (value "RC0402JR-133K3L")
      (footprint "eagle-import:RESC1005X40N")
      (fields (field (name "MOUSER_PART_NUMBER") "603-RC0402JR-133K3L"))
      (libsource (lib "eagle-import") (part "RC0402JR-133K3L"))
    )
    (comp (ref "R485")
      (value "RC0402JR-133K3L")
      (footprint "eagle-import:RESC1005X40N")
      (fields (field (name "MOUSER_PART_NUMBER") "603-RC0402JR-133K3L"))
      (libsource (lib "eagle-import") (part "RC0402JR-133K3L"))
    )
    (comp (ref "R486")
      (value "MCS04020C1001FE000")
      (footprint "eagle-import:RESC1005X37N")
      (fields (field (name "MOUSER_PART_NUMBER") "594-MCS04020C1001FE0"))
      (libsource (lib "eagle-import") (part "MCS04020C1001FE000"))
    )
    (comp (ref "R487")
      (value "MCS04020C1001FE000")
      (footprint "eagle-import:RESC1005X37N")
      (fields (field (name "MOUSER_PART_NUMBER") "594-MCS04020C1001FE0"))
      (libsource (lib "eagle-import") (part "MCS04020C1001FE000"))
    )
    (comp (ref "R488")
      (value "RC0402JR-1015KL")
      (footprint "eagle-import:RESC1005X40N")
      (fields (field (name "MOUSER_PART_NUMBER") "603-RC0402JR-1015KL"))
      (libsource (lib "eagle-import") (part "RC0402JR-1015KL"))
    )
    (comp (ref "R489")
      (value "RC0402JR-1015KL")
      (footprint "eagle-import:RESC1005X40N")
      (fields (field (name "MOUSER_PART_NUMBER") "603-RC0402JR-1015KL"))
      (libsource (lib "eagle-import") (part "RC0402JR-1015KL"))
    )
    (comp (ref "R490")
      (value "GMR100HTCFAR100")
      (footprint "eagle-import:RESC6432X55N")
      (fields (field (name "MOUSER_PART_NUMBER") "755-GMR100HTCFAR100"))
      (libsource (lib "eagle-import") (part "GMR100HTCFAR100"))
    )
    (comp (ref "R491")
      (value "RC0402JR-133K3L")
      (footprint "eagle-import:RESC1005X40N")
      (fields (field (name "MOUSER_PART_NUMBER") "603-RC0402JR-133K3L"))
      (libsource (lib "eagle-import") (part "RC0402JR-133K3L"))
    )
    (comp (ref "R492")
      (value "RC0402JR-133K3L")
      (footprint "eagle-import:RESC1005X40N")
      (fields (field (name "MOUSER_PART_NUMBER") "603-RC0402JR-133K3L"))
      (libsource (lib "eagle-import") (part "RC0402JR-133K3L"))
    )
    (comp (ref "R493")
      (value "RC0402JR-133K3L")
      (footprint "eagle-import:RESC1005X40N")
      (fields (field (name "MOUSER_PART_NUMBER") "603-RC0402JR-133K3L"))
      (libsource (lib "eagle-import") (part "RC0402JR-133K3L"))
    )
    (comp (ref "R494")
      (value "RC0402JR-133K3L")
      (footprint "eagle-import:RESC1005X40N")
      (fields (field (name "MOUSER_PART_NUMBER") "603-RC0402JR-133K3L"))
      (libsource (lib "eagle-import") (part "RC0402JR-133K3L"))
    )
    (comp (ref "R495")
      (value "MCS04020C1001FE000")
      (footprint "eagle-import:RESC1005X37N")
      (fields (field (name "MOUSER_PART_NUMBER") "594-MCS04020C1001FE0"))
      (libsource (lib "eagle-import") (part "MCS04020C1001FE000"))
    )
    (comp (ref "R496")
      (value "MCS04020C1001FE000")
      (footprint "eagle-import:RESC1005X37N")
      (fields (field (name "MOUSER_PART_NUMBER") "594-MCS04020C1001FE0"))
      (libsource (lib "eagle-import") (part "MCS04020C1001FE000"))
    )
    (comp (ref "R497")
      (value "RC0402JR-1015KL")
      (footprint "eagle-import:RESC1005X40N")
      (fields (field (name "MOUSER_PART_NUMBER") "603-RC0402JR-1015KL"))
      (libsource (lib "eagle-import") (part "RC0402JR-1015KL"))
    )
    (comp (ref "R498")
      (value "RC0402JR-1015KL")
      (footprint "eagle-import:RESC1005X40N")
      (fields (field (name "MOUSER_PART_NUMBER") "603-RC0402JR-1015KL"))
      (libsource (lib "eagle-import") (part "RC0402JR-1015KL"))
    )
    (comp (ref "C1")
      (value "C3216X7R1E106K160AE")
      (footprint "eagle-import:C3216_COMMERCIAL")
      (fields (field (name "MOUSER_PART_NUMBER") "810-C3216X7R1E106KST"))
      (libsource (lib "eagle-import") (part "C3216X7R1E106K160AE"))
    )
    (comp (ref "C2")
      (value "CGA4J3X7R1H105K125AB")
      (footprint "eagle-import:CAPC2012X145N")
      (fields (field (name "MOUSER_PART_NUMBER") "810-CGA4J3X7R1H105K "))
      (libsource (lib "eagle-import") (part "CGA4J3X7R1H105K125AB"))
    )
    (comp (ref "C3")
      (value "CGA4J3X7R1H105K125AB")
      (footprint "eagle-import:CAPC2012X145N")
      (fields (field (name "MOUSER_PART_NUMBER") "810-CGA4J3X7R1H105K "))
      (libsource (lib "eagle-import") (part "CGA4J3X7R1H105K125AB"))
    )
    (comp (ref "C4")
      (value "CGA4J3X7R1H105K125AB")
      (footprint "eagle-import:CAPC2012X145N")
      (fields (field (name "MOUSER_PART_NUMBER") "810-CGA4J3X7R1H105K "))
      (libsource (lib "eagle-import") (part "CGA4J3X7R1H105K125AB"))
    )
    (comp (ref "C5")
      (value "CGA4J3X7R1H105K125AB")
      (footprint "eagle-import:CAPC2012X145N")
      (fields (field (name "MOUSER_PART_NUMBER") "810-CGA4J3X7R1H105K "))
      (libsource (lib "eagle-import") (part "CGA4J3X7R1H105K125AB"))
    )
    (comp (ref "C6")
      (value "CGA4J3X7R1H105K125AB")
      (footprint "eagle-import:CAPC2012X145N")
      (fields (field (name "MOUSER_PART_NUMBER") "810-CGA4J3X7R1H105K "))
      (libsource (lib "eagle-import") (part "CGA4J3X7R1H105K125AB"))
    )
    (comp (ref "C7")
      (value "CGA4J3X7R1H105K125AB")
      (footprint "eagle-import:CAPC2012X145N")
      (fields (field (name "MOUSER_PART_NUMBER") "810-CGA4J3X7R1H105K "))
      (libsource (lib "eagle-import") (part "CGA4J3X7R1H105K125AB"))
    )
    (comp (ref "C8")
      (value "CGA4J3X7R1H105K125AB")
      (footprint "eagle-import:CAPC2012X145N")
      (fields (field (name "MOUSER_PART_NUMBER") "810-CGA4J3X7R1H105K "))
      (libsource (lib "eagle-import") (part "CGA4J3X7R1H105K125AB"))
    )
    (comp (ref "C9")
      (value "CGA4J3X7R1H105K125AB")
      (footprint "eagle-import:CAPC2012X145N")
      (fields (field (name "MOUSER_PART_NUMBER") "810-CGA4J3X7R1H105K "))
      (libsource (lib "eagle-import") (part "CGA4J3X7R1H105K125AB"))
    )
    (comp (ref "C10")
      (value "CGA4J3X7R1H105K125AB")
      (footprint "eagle-import:CAPC2012X145N")
      (fields (field (name "MOUSER_PART_NUMBER") "810-CGA4J3X7R1H105K "))
      (libsource (lib "eagle-import") (part "CGA4J3X7R1H105K125AB"))
    )
    (comp (ref "C11")
      (value "CGA4J3X7R1H105K125AB")
      (footprint "eagle-import:CAPC2012X145N")
      (fields (field (name "MOUSER_PART_NUMBER") "810-CGA4J3X7R1H105K "))
      (libsource (lib "eagle-import") (part "CGA4J3X7R1H105K125AB"))
    )
    (comp (ref "C12")
      (value "CGA4J3X7R1H105K125AB")
      (footprint "eagle-import:CAPC2012X145N")
      (fields (field (name "MOUSER_PART_NUMBER") "810-CGA4J3X7R1H105K "))
      (libsource (lib "eagle-import") (part "CGA4J3X7R1H105K125AB"))
    )
    (comp (ref "C13")
      (value "C3216X7R1E106K160AE")
      (footprint "eagle-import:C3216_COMMERCIAL")
      (fields (field (name "MOUSER_PART_NUMBER") "810-C3216X7R1E106KST"))
      (libsource (lib "eagle-import") (part "C3216X7R1E106K160AE"))
    )
    (comp (ref "C15")
      (value "CGA4J3X7R1H105K125AB")
      (footprint "eagle-import:CAPC2012X145N")
      (fields (field (name "MOUSER_PART_NUMBER") "810-CGA4J3X7R1H105K "))
      (libsource (lib "eagle-import") (part "CGA4J3X7R1H105K125AB"))
    )
    (comp (ref "C16")
      (value "C3216X7R1E106K160AE")
      (footprint "eagle-import:C3216_COMMERCIAL")
      (fields (field (name "MOUSER_PART_NUMBER") "810-C3216X7R1E106KST"))
      (libsource (lib "eagle-import") (part "C3216X7R1E106K160AE"))
    )
    (comp (ref "C18")
      (value "CGA4J3X7R1H105K125AB")
      (footprint "eagle-import:CAPC2012X145N")
      (fields (field (name "MOUSER_PART_NUMBER") "810-CGA4J3X7R1H105K "))
      (libsource (lib "eagle-import") (part "CGA4J3X7R1H105K125AB"))
    )
    (comp (ref "C22")
      (value "C3216X7R1E106K160AE")
      (footprint "eagle-import:C3216_COMMERCIAL")
      (fields (field (name "MOUSER_PART_NUMBER") "810-C3216X7R1E106KST"))
      (libsource (lib "eagle-import") (part "C3216X7R1E106K160AE"))
    )
    (comp (ref "C47")
      (value "C0402C103K3RAC7411")
      (footprint "eagle-import:C0402")
      (fields (field (name "MOUSER_PART_NUMBER") "80-C0402C103K3R7411"))
      (libsource (lib "eagle-import") (part "C0402C103K3RAC7411"))
    )
    (comp (ref "C48")
      (value "CS0402KRX7R8BB104")
      (footprint "eagle-import:CAPC1005X65N")
      (fields (field (name "MOUSER_PART_NUMBER") "603-CS0402KRX78BB104"))
      (libsource (lib "eagle-import") (part "CS0402KRX7R8BB104"))
    )
    (comp (ref "C49")
      (value "CS0402KRX7R8BB104")
      (footprint "eagle-import:CAPC1005X65N")
      (fields (field (name "MOUSER_PART_NUMBER") "603-CS0402KRX78BB104"))
      (libsource (lib "eagle-import") (part "CS0402KRX7R8BB104"))
    )
    (comp (ref "C50")
      (value "CS0402KRX7R8BB104")
      (footprint "eagle-import:CAPC1005X65N")
      (fields (field (name "MOUSER_PART_NUMBER") "603-CS0402KRX78BB104"))
      (libsource (lib "eagle-import") (part "CS0402KRX7R8BB104"))
    )
    (comp (ref "C51")
      (value "CS0402KRX7R8BB104")
      (footprint "eagle-import:CAPC1005X65N")
      (fields (field (name "MOUSER_PART_NUMBER") "603-CS0402KRX78BB104"))
      (libsource (lib "eagle-import") (part "CS0402KRX7R8BB104"))
    )
    (comp (ref "C52")
      (value "CS0402KRX7R8BB104")
      (footprint "eagle-import:CAPC1005X65N")
      (fields (field (name "MOUSER_PART_NUMBER") "603-CS0402KRX78BB104"))
      (libsource (lib "eagle-import") (part "CS0402KRX7R8BB104"))
    )
    (comp (ref "C53")
      (value "C0402C103K3RAC7411")
      (footprint "eagle-import:C0402")
      (fields (field (name "MOUSER_PART_NUMBER") "80-C0402C103K3R7411"))
      (libsource (lib "eagle-import") (part "C0402C103K3RAC7411"))
    )
    (comp (ref "C54")
      (value "CS0402KRX7R8BB104")
      (footprint "eagle-import:CAPC1005X65N")
      (fields (field (name "MOUSER_PART_NUMBER") "603-CS0402KRX78BB104"))
      (libsource (lib "eagle-import") (part "CS0402KRX7R8BB104"))
    )
    (comp (ref "C55")
      (value "C0402C103K3RAC7411")
      (footprint "eagle-import:C0402")
      (fields (field (name "MOUSER_PART_NUMBER") "80-C0402C103K3R7411"))
      (libsource (lib "eagle-import") (part "C0402C103K3RAC7411"))
    )
    (comp (ref "C56")
      (value "CS0402KRX7R8BB104")
      (footprint "eagle-import:CAPC1005X65N")
      (fields (field (name "MOUSER_PART_NUMBER") "603-CS0402KRX78BB104"))
      (libsource (lib "eagle-import") (part "CS0402KRX7R8BB104"))
    )
    (comp (ref "C57")
      (value "CS0402KRX7R8BB104")
      (footprint "eagle-import:CAPC1005X65N")
      (fields (field (name "MOUSER_PART_NUMBER") "603-CS0402KRX78BB104"))
      (libsource (lib "eagle-import") (part "CS0402KRX7R8BB104"))
    )
    (comp (ref "C58")
      (value "CS0402KRX7R8BB104")
      (footprint "eagle-import:CAPC1005X65N")
      (fields (field (name "MOUSER_PART_NUMBER") "603-CS0402KRX78BB104"))
      (libsource (lib "eagle-import") (part "CS0402KRX7R8BB104"))
    )
    (comp (ref "C59")
      (value "CS0402KRX7R8BB104")
      (footprint "eagle-import:CAPC1005X65N")
      (fields (field (name "MOUSER_PART_NUMBER") "603-CS0402KRX78BB104"))
      (libsource (lib "eagle-import") (part "CS0402KRX7R8BB104"))
    )
    (comp (ref "C60")
      (value "CS0402KRX7R8BB104")
      (footprint "eagle-import:CAPC1005X65N")
      (fields (field (name "MOUSER_PART_NUMBER") "603-CS0402KRX78BB104"))
      (libsource (lib "eagle-import") (part "CS0402KRX7R8BB104"))
    )
    (comp (ref "C61")
      (value "C0402C103K3RAC7411")
      (footprint "eagle-import:C0402")
      (fields (field (name "MOUSER_PART_NUMBER") "80-C0402C103K3R7411"))
      (libsource (lib "eagle-import") (part "C0402C103K3RAC7411"))
    )
    (comp (ref "C62")
      (value "CS0402KRX7R8BB104")
      (footprint "eagle-import:CAPC1005X65N")
      (fields (field (name "MOUSER_PART_NUMBER") "603-CS0402KRX78BB104"))
      (libsource (lib "eagle-import") (part "CS0402KRX7R8BB104"))
    )
    (comp (ref "C74")
      (value "CS0402KRX7R8BB104")
      (footprint "eagle-import:CAPC1005X65N")
      (fields (field (name "MOUSER_PART_NUMBER") "603-CS0402KRX78BB104"))
      (libsource (lib "eagle-import") (part "CS0402KRX7R8BB104"))
    )
    (comp (ref "C75")
      (value "CS0402KRX7R8BB104")
      (footprint "eagle-import:CAPC1005X65N")
      (fields (field (name "MOUSER_PART_NUMBER") "603-CS0402KRX78BB104"))
      (libsource (lib "eagle-import") (part "CS0402KRX7R8BB104"))
    )
    (comp (ref "C76")
      (value "CS0402KRX7R8BB104")
      (footprint "eagle-import:CAPC1005X65N")
      (fields (field (name "MOUSER_PART_NUMBER") "603-CS0402KRX78BB104"))
      (libsource (lib "eagle-import") (part "CS0402KRX7R8BB104"))
    )
    (comp (ref "C77")
      (value "CS0402KRX7R8BB104")
      (footprint "eagle-import:CAPC1005X65N")
      (fields (field (name "MOUSER_PART_NUMBER") "603-CS0402KRX78BB104"))
      (libsource (lib "eagle-import") (part "CS0402KRX7R8BB104"))
    )
    (comp (ref "C78")
      (value "C0402C103K3RAC7411")
      (footprint "eagle-import:C0402")
      (fields (field (name "MOUSER_PART_NUMBER") "80-C0402C103K3R7411"))
      (libsource (lib "eagle-import") (part "C0402C103K3RAC7411"))
    )
    (comp (ref "C79")
      (value "CS0402KRX7R8BB104")
      (footprint "eagle-import:CAPC1005X65N")
      (fields (field (name "MOUSER_PART_NUMBER") "603-CS0402KRX78BB104"))
      (libsource (lib "eagle-import") (part "CS0402KRX7R8BB104"))
    )
    (comp (ref "C80")
      (value "CS0402KRX7R8BB104")
      (footprint "eagle-import:CAPC1005X65N")
      (fields (field (name "MOUSER_PART_NUMBER") "603-CS0402KRX78BB104"))
      (libsource (lib "eagle-import") (part "CS0402KRX7R8BB104"))
    )
    (comp (ref "C81")
      (value "CS0402KRX7R8BB104")
      (footprint "eagle-import:CAPC1005X65N")
      (fields (field (name "MOUSER_PART_NUMBER") "603-CS0402KRX78BB104"))
      (libsource (lib "eagle-import") (part "CS0402KRX7R8BB104"))
    )
    (comp (ref "C82")
      (value "CS0402KRX7R8BB104")
      (footprint "eagle-import:CAPC1005X65N")
      (fields (field (name "MOUSER_PART_NUMBER") "603-CS0402KRX78BB104"))
      (libsource (lib "eagle-import") (part "CS0402KRX7R8BB104"))
    )
    (comp (ref "C83")
      (value "CS0402KRX7R8BB104")
      (footprint "eagle-import:CAPC1005X65N")
      (fields (field (name "MOUSER_PART_NUMBER") "603-CS0402KRX78BB104"))
      (libsource (lib "eagle-import") (part "CS0402KRX7R8BB104"))
    )
    (comp (ref "C84")
      (value "CS0402KRX7R8BB104")
      (footprint "eagle-import:CAPC1005X65N")
      (fields (field (name "MOUSER_PART_NUMBER") "603-CS0402KRX78BB104"))
      (libsource (lib "eagle-import") (part "CS0402KRX7R8BB104"))
    )
    (comp (ref "C85")
      (value "CS0402KRX7R8BB104")
      (footprint "eagle-import:CAPC1005X65N")
      (fields (field (name "MOUSER_PART_NUMBER") "603-CS0402KRX78BB104"))
      (libsource (lib "eagle-import") (part "CS0402KRX7R8BB104"))
    )
    (comp (ref "C86")
      (value "C0402C103K3RAC7411")
      (footprint "eagle-import:C0402")
      (fields (field (name "MOUSER_PART_NUMBER") "80-C0402C103K3R7411"))
      (libsource (lib "eagle-import") (part "C0402C103K3RAC7411"))
    )
    (comp (ref "C87")
      (value "CS0402KRX7R8BB104")
      (footprint "eagle-import:CAPC1005X65N")
      (fields (field (name "MOUSER_PART_NUMBER") "603-CS0402KRX78BB104"))
      (libsource (lib "eagle-import") (part "CS0402KRX7R8BB104"))
    )
    (comp (ref "C88")
      (value "CS0402KRX7R8BB104")
      (footprint "eagle-import:CAPC1005X65N")
      (fields (field (name "MOUSER_PART_NUMBER") "603-CS0402KRX78BB104"))
      (libsource (lib "eagle-import") (part "CS0402KRX7R8BB104"))
    )
    (comp (ref "C89")
      (value "CS0402KRX7R8BB104")
      (footprint "eagle-import:CAPC1005X65N")
      (fields (field (name "MOUSER_PART_NUMBER") "603-CS0402KRX78BB104"))
      (libsource (lib "eagle-import") (part "CS0402KRX7R8BB104"))
    )
    (comp (ref "C175")
      (value "C0402C103K3RAC7411")
      (footprint "eagle-import:C0402")
      (fields (field (name "MOUSER_PART_NUMBER") "80-C0402C103K3R7411"))
      (libsource (lib "eagle-import") (part "C0402C103K3RAC7411"))
    )
    (comp (ref "C176")
      (value "CS0402KRX7R8BB104")
      (footprint "eagle-import:CAPC1005X65N")
      (fields (field (name "MOUSER_PART_NUMBER") "603-CS0402KRX78BB104"))
      (libsource (lib "eagle-import") (part "CS0402KRX7R8BB104"))
    )
    (comp (ref "C177")
      (value "CS0402KRX7R8BB104")
      (footprint "eagle-import:CAPC1005X65N")
      (fields (field (name "MOUSER_PART_NUMBER") "603-CS0402KRX78BB104"))
      (libsource (lib "eagle-import") (part "CS0402KRX7R8BB104"))
    )
    (comp (ref "C178")
      (value "CS0402KRX7R8BB104")
      (footprint "eagle-import:CAPC1005X65N")
      (fields (field (name "MOUSER_PART_NUMBER") "603-CS0402KRX78BB104"))
      (libsource (lib "eagle-import") (part "CS0402KRX7R8BB104"))
    )
    (comp (ref "C179")
      (value "CS0402KRX7R8BB104")
      (footprint "eagle-import:CAPC1005X65N")
      (fields (field (name "MOUSER_PART_NUMBER") "603-CS0402KRX78BB104"))
      (libsource (lib "eagle-import") (part "CS0402KRX7R8BB104"))
    )
    (comp (ref "C180")
      (value "CS0402KRX7R8BB104")
      (footprint "eagle-import:CAPC1005X65N")
      (fields (field (name "MOUSER_PART_NUMBER") "603-CS0402KRX78BB104"))
      (libsource (lib "eagle-import") (part "CS0402KRX7R8BB104"))
    )
    (comp (ref "C181")
      (value "C0402C103K3RAC7411")
      (footprint "eagle-import:C0402")
      (fields (field (name "MOUSER_PART_NUMBER") "80-C0402C103K3R7411"))
      (libsource (lib "eagle-import") (part "C0402C103K3RAC7411"))
    )
    (comp (ref "C182")
      (value "CS0402KRX7R8BB104")
      (footprint "eagle-import:CAPC1005X65N")
      (fields (field (name "MOUSER_PART_NUMBER") "603-CS0402KRX78BB104"))
      (libsource (lib "eagle-import") (part "CS0402KRX7R8BB104"))
    )
    (comp (ref "C183")
      (value "CS0402KRX7R8BB104")
      (footprint "eagle-import:CAPC1005X65N")
      (fields (field (name "MOUSER_PART_NUMBER") "603-CS0402KRX78BB104"))
      (libsource (lib "eagle-import") (part "CS0402KRX7R8BB104"))
    )
    (comp (ref "C184")
      (value "CS0402KRX7R8BB104")
      (footprint "eagle-import:CAPC1005X65N")
      (fields (field (name "MOUSER_PART_NUMBER") "603-CS0402KRX78BB104"))
      (libsource (lib "eagle-import") (part "CS0402KRX7R8BB104"))
    )
    (comp (ref "C185")
      (value "CS0402KRX7R8BB104")
      (footprint "eagle-import:CAPC1005X65N")
      (fields (field (name "MOUSER_PART_NUMBER") "603-CS0402KRX78BB104"))
      (libsource (lib "eagle-import") (part "CS0402KRX7R8BB104"))
    )
    (comp (ref "C186")
      (value "CS0402KRX7R8BB104")
      (footprint "eagle-import:CAPC1005X65N")
      (fields (field (name "MOUSER_PART_NUMBER") "603-CS0402KRX78BB104"))
      (libsource (lib "eagle-import") (part "CS0402KRX7R8BB104"))
    )
    (comp (ref "C187")
      (value "CS0402KRX7R8BB104")
      (footprint "eagle-import:CAPC1005X65N")
      (fields (field (name "MOUSER_PART_NUMBER") "603-CS0402KRX78BB104"))
      (libsource (lib "eagle-import") (part "CS0402KRX7R8BB104"))
    )
    (comp (ref "C188")
      (value "CS0402KRX7R8BB104")
      (footprint "eagle-import:CAPC1005X65N")
      (fields (field (name "MOUSER_PART_NUMBER") "603-CS0402KRX78BB104"))
      (libsource (lib "eagle-import") (part "CS0402KRX7R8BB104"))
    )
    (comp (ref "C190")
      (value "CGA4J3X7R1H105K125AB")
      (footprint "eagle-import:CAPC2012X145N")
      (fields (field (name "MOUSER_PART_NUMBER") "810-CGA4J3X7R1H105K "))
      (libsource (lib "eagle-import") (part "CGA4J3X7R1H105K125AB"))
    )
    (comp (ref "C197")
      (value "CS0402KRX7R8BB104")
      (footprint "eagle-import:CAPC1005X65N")
      (fields (field (name "MOUSER_PART_NUMBER") "603-CS0402KRX78BB104"))
      (libsource (lib "eagle-import") (part "CS0402KRX7R8BB104"))
    )
    (comp (ref "C198")
      (value "CS0402KRX7R8BB104")
      (footprint "eagle-import:CAPC1005X65N")
      (fields (field (name "MOUSER_PART_NUMBER") "603-CS0402KRX78BB104"))
      (libsource (lib "eagle-import") (part "CS0402KRX7R8BB104"))
    )
    (comp (ref "C199")
      (value "C0402C103K3RAC7411")
      (footprint "eagle-import:C0402")
      (fields (field (name "MOUSER_PART_NUMBER") "80-C0402C103K3R7411"))
      (libsource (lib "eagle-import") (part "C0402C103K3RAC7411"))
    )
    (comp (ref "C200")
      (value "CS0402KRX7R8BB104")
      (footprint "eagle-import:CAPC1005X65N")
      (fields (field (name "MOUSER_PART_NUMBER") "603-CS0402KRX78BB104"))
      (libsource (lib "eagle-import") (part "CS0402KRX7R8BB104"))
    )
    (comp (ref "C201")
      (value "CS0402KRX7R8BB104")
      (footprint "eagle-import:CAPC1005X65N")
      (fields (field (name "MOUSER_PART_NUMBER") "603-CS0402KRX78BB104"))
      (libsource (lib "eagle-import") (part "CS0402KRX7R8BB104"))
    )
    (comp (ref "C202")
      (value "CS0402KRX7R8BB104")
      (footprint "eagle-import:CAPC1005X65N")
      (fields (field (name "MOUSER_PART_NUMBER") "603-CS0402KRX78BB104"))
      (libsource (lib "eagle-import") (part "CS0402KRX7R8BB104"))
    )
    (comp (ref "C203")
      (value "CS0402KRX7R8BB104")
      (footprint "eagle-import:CAPC1005X65N")
      (fields (field (name "MOUSER_PART_NUMBER") "603-CS0402KRX78BB104"))
      (libsource (lib "eagle-import") (part "CS0402KRX7R8BB104"))
    )
    (comp (ref "C204")
      (value "CS0402KRX7R8BB104")
      (footprint "eagle-import:CAPC1005X65N")
      (fields (field (name "MOUSER_PART_NUMBER") "603-CS0402KRX78BB104"))
      (libsource (lib "eagle-import") (part "CS0402KRX7R8BB104"))
    )
    (comp (ref "C205")
      (value "C0402C103K3RAC7411")
      (footprint "eagle-import:C0402")
      (fields (field (name "MOUSER_PART_NUMBER") "80-C0402C103K3R7411"))
      (libsource (lib "eagle-import") (part "C0402C103K3RAC7411"))
    )
    (comp (ref "C206")
      (value "CS0402KRX7R8BB104")
      (footprint "eagle-import:CAPC1005X65N")
      (fields (field (name "MOUSER_PART_NUMBER") "603-CS0402KRX78BB104"))
      (libsource (lib "eagle-import") (part "CS0402KRX7R8BB104"))
    )
    (comp (ref "C207")
      (value "CS0402KRX7R8BB104")
      (footprint "eagle-import:CAPC1005X65N")
      (fields (field (name "MOUSER_PART_NUMBER") "603-CS0402KRX78BB104"))
      (libsource (lib "eagle-import") (part "CS0402KRX7R8BB104"))
    )
    (comp (ref "C208")
      (value "CS0402KRX7R8BB104")
      (footprint "eagle-import:CAPC1005X65N")
      (fields (field (name "MOUSER_PART_NUMBER") "603-CS0402KRX78BB104"))
      (libsource (lib "eagle-import") (part "CS0402KRX7R8BB104"))
    )
    (comp (ref "C209")
      (value "CS0402KRX7R8BB104")
      (footprint "eagle-import:CAPC1005X65N")
      (fields (field (name "MOUSER_PART_NUMBER") "603-CS0402KRX78BB104"))
      (libsource (lib "eagle-import") (part "CS0402KRX7R8BB104"))
    )
    (comp (ref "C210")
      (value "CS0402KRX7R8BB104")
      (footprint "eagle-import:CAPC1005X65N")
      (fields (field (name "MOUSER_PART_NUMBER") "603-CS0402KRX78BB104"))
      (libsource (lib "eagle-import") (part "CS0402KRX7R8BB104"))
    )
    (comp (ref "C211")
      (value "C0402C103K3RAC7411")
      (footprint "eagle-import:C0402")
      (fields (field (name "MOUSER_PART_NUMBER") "80-C0402C103K3R7411"))
      (libsource (lib "eagle-import") (part "C0402C103K3RAC7411"))
    )
    (comp (ref "C212")
      (value "CS0402KRX7R8BB104")
      (footprint "eagle-import:CAPC1005X65N")
      (fields (field (name "MOUSER_PART_NUMBER") "603-CS0402KRX78BB104"))
      (libsource (lib "eagle-import") (part "CS0402KRX7R8BB104"))
    )
    (comp (ref "C213")
      (value "CS0402KRX7R8BB104")
      (footprint "eagle-import:CAPC1005X65N")
      (fields (field (name "MOUSER_PART_NUMBER") "603-CS0402KRX78BB104"))
      (libsource (lib "eagle-import") (part "CS0402KRX7R8BB104"))
    )
    (comp (ref "C214")
      (value "CS0402KRX7R8BB104")
      (footprint "eagle-import:CAPC1005X65N")
      (fields (field (name "MOUSER_PART_NUMBER") "603-CS0402KRX78BB104"))
      (libsource (lib "eagle-import") (part "CS0402KRX7R8BB104"))
    )
    (comp (ref "C215")
      (value "CS0402KRX7R8BB104")
      (footprint "eagle-import:CAPC1005X65N")
      (fields (field (name "MOUSER_PART_NUMBER") "603-CS0402KRX78BB104"))
      (libsource (lib "eagle-import") (part "CS0402KRX7R8BB104"))
    )
    (comp (ref "C216")
      (value "CS0402KRX7R8BB104")
      (footprint "eagle-import:CAPC1005X65N")
      (fields (field (name "MOUSER_PART_NUMBER") "603-CS0402KRX78BB104"))
      (libsource (lib "eagle-import") (part "CS0402KRX7R8BB104"))
    )
    (comp (ref "C217")
      (value "C0402C103K3RAC7411")
      (footprint "eagle-import:C0402")
      (fields (field (name "MOUSER_PART_NUMBER") "80-C0402C103K3R7411"))
      (libsource (lib "eagle-import") (part "C0402C103K3RAC7411"))
    )
    (comp (ref "C218")
      (value "CS0402KRX7R8BB104")
      (footprint "eagle-import:CAPC1005X65N")
      (fields (field (name "MOUSER_PART_NUMBER") "603-CS0402KRX78BB104"))
      (libsource (lib "eagle-import") (part "CS0402KRX7R8BB104"))
    )
    (comp (ref "C219")
      (value "CS0402KRX7R8BB104")
      (footprint "eagle-import:CAPC1005X65N")
      (fields (field (name "MOUSER_PART_NUMBER") "603-CS0402KRX78BB104"))
      (libsource (lib "eagle-import") (part "CS0402KRX7R8BB104"))
    )
    (comp (ref "C220")
      (value "CS0402KRX7R8BB104")
      (footprint "eagle-import:CAPC1005X65N")
      (fields (field (name "MOUSER_PART_NUMBER") "603-CS0402KRX78BB104"))
      (libsource (lib "eagle-import") (part "CS0402KRX7R8BB104"))
    )
    (comp (ref "C221")
      (value "CS0402KRX7R8BB104")
      (footprint "eagle-import:CAPC1005X65N")
      (fields (field (name "MOUSER_PART_NUMBER") "603-CS0402KRX78BB104"))
      (libsource (lib "eagle-import") (part "CS0402KRX7R8BB104"))
    )
    (comp (ref "C222")
      (value "CS0402KRX7R8BB104")
      (footprint "eagle-import:CAPC1005X65N")
      (fields (field (name "MOUSER_PART_NUMBER") "603-CS0402KRX78BB104"))
      (libsource (lib "eagle-import") (part "CS0402KRX7R8BB104"))
    )
    (comp (ref "C223")
      (value "C0402C103K3RAC7411")
      (footprint "eagle-import:C0402")
      (fields (field (name "MOUSER_PART_NUMBER") "80-C0402C103K3R7411"))
      (libsource (lib "eagle-import") (part "C0402C103K3RAC7411"))
    )
    (comp (ref "C224")
      (value "CS0402KRX7R8BB104")
      (footprint "eagle-import:CAPC1005X65N")
      (fields (field (name "MOUSER_PART_NUMBER") "603-CS0402KRX78BB104"))
      (libsource (lib "eagle-import") (part "CS0402KRX7R8BB104"))
    )
    (comp (ref "C225")
      (value "CS0402KRX7R8BB104")
      (footprint "eagle-import:CAPC1005X65N")
      (fields (field (name "MOUSER_PART_NUMBER") "603-CS0402KRX78BB104"))
      (libsource (lib "eagle-import") (part "CS0402KRX7R8BB104"))
    )
    (comp (ref "C226")
      (value "CS0402KRX7R8BB104")
      (footprint "eagle-import:CAPC1005X65N")
      (fields (field (name "MOUSER_PART_NUMBER") "603-CS0402KRX78BB104"))
      (libsource (lib "eagle-import") (part "CS0402KRX7R8BB104"))
    )
    (comp (ref "C227")
      (value "CS0402KRX7R8BB104")
      (footprint "eagle-import:CAPC1005X65N")
      (fields (field (name "MOUSER_PART_NUMBER") "603-CS0402KRX78BB104"))
      (libsource (lib "eagle-import") (part "CS0402KRX7R8BB104"))
    )
    (comp (ref "C228")
      (value "CS0402KRX7R8BB104")
      (footprint "eagle-import:CAPC1005X65N")
      (fields (field (name "MOUSER_PART_NUMBER") "603-CS0402KRX78BB104"))
      (libsource (lib "eagle-import") (part "CS0402KRX7R8BB104"))
    )
    (comp (ref "C229")
      (value "C0402C103K3RAC7411")
      (footprint "eagle-import:C0402")
      (fields (field (name "MOUSER_PART_NUMBER") "80-C0402C103K3R7411"))
      (libsource (lib "eagle-import") (part "C0402C103K3RAC7411"))
    )
    (comp (ref "C230")
      (value "CS0402KRX7R8BB104")
      (footprint "eagle-import:CAPC1005X65N")
      (fields (field (name "MOUSER_PART_NUMBER") "603-CS0402KRX78BB104"))
      (libsource (lib "eagle-import") (part "CS0402KRX7R8BB104"))
    )
    (comp (ref "C231")
      (value "CS0402KRX7R8BB104")
      (footprint "eagle-import:CAPC1005X65N")
      (fields (field (name "MOUSER_PART_NUMBER") "603-CS0402KRX78BB104"))
      (libsource (lib "eagle-import") (part "CS0402KRX7R8BB104"))
    )
    (comp (ref "C232")
      (value "CS0402KRX7R8BB104")
      (footprint "eagle-import:CAPC1005X65N")
      (fields (field (name "MOUSER_PART_NUMBER") "603-CS0402KRX78BB104"))
      (libsource (lib "eagle-import") (part "CS0402KRX7R8BB104"))
    )
    (comp (ref "C233")
      (value "CS0402KRX7R8BB104")
      (footprint "eagle-import:CAPC1005X65N")
      (fields (field (name "MOUSER_PART_NUMBER") "603-CS0402KRX78BB104"))
      (libsource (lib "eagle-import") (part "CS0402KRX7R8BB104"))
    )
    (comp (ref "C234")
      (value "CS0402KRX7R8BB104")
      (footprint "eagle-import:CAPC1005X65N")
      (fields (field (name "MOUSER_PART_NUMBER") "603-CS0402KRX78BB104"))
      (libsource (lib "eagle-import") (part "CS0402KRX7R8BB104"))
    )
    (comp (ref "C235")
      (value "C0402C103K3RAC7411")
      (footprint "eagle-import:C0402")
      (fields (field (name "MOUSER_PART_NUMBER") "80-C0402C103K3R7411"))
      (libsource (lib "eagle-import") (part "C0402C103K3RAC7411"))
    )
    (comp (ref "C236")
      (value "CS0402KRX7R8BB104")
      (footprint "eagle-import:CAPC1005X65N")
      (fields (field (name "MOUSER_PART_NUMBER") "603-CS0402KRX78BB104"))
      (libsource (lib "eagle-import") (part "CS0402KRX7R8BB104"))
    )
    (comp (ref "C237")
      (value "CS0402KRX7R8BB104")
      (footprint "eagle-import:CAPC1005X65N")
      (fields (field (name "MOUSER_PART_NUMBER") "603-CS0402KRX78BB104"))
      (libsource (lib "eagle-import") (part "CS0402KRX7R8BB104"))
    )
    (comp (ref "C238")
      (value "CS0402KRX7R8BB104")
      (footprint "eagle-import:CAPC1005X65N")
      (fields (field (name "MOUSER_PART_NUMBER") "603-CS0402KRX78BB104"))
      (libsource (lib "eagle-import") (part "CS0402KRX7R8BB104"))
    )
    (comp (ref "C239")
      (value "CS0402KRX7R8BB104")
      (footprint "eagle-import:CAPC1005X65N")
      (fields (field (name "MOUSER_PART_NUMBER") "603-CS0402KRX78BB104"))
      (libsource (lib "eagle-import") (part "CS0402KRX7R8BB104"))
    )
    (comp (ref "C240")
      (value "CS0402KRX7R8BB104")
      (footprint "eagle-import:CAPC1005X65N")
      (fields (field (name "MOUSER_PART_NUMBER") "603-CS0402KRX78BB104"))
      (libsource (lib "eagle-import") (part "CS0402KRX7R8BB104"))
    )
    (comp (ref "C241")
      (value "C0402C103K3RAC7411")
      (footprint "eagle-import:C0402")
      (fields (field (name "MOUSER_PART_NUMBER") "80-C0402C103K3R7411"))
      (libsource (lib "eagle-import") (part "C0402C103K3RAC7411"))
    )
    (comp (ref "C242")
      (value "CS0402KRX7R8BB104")
      (footprint "eagle-import:CAPC1005X65N")
      (fields (field (name "MOUSER_PART_NUMBER") "603-CS0402KRX78BB104"))
      (libsource (lib "eagle-import") (part "CS0402KRX7R8BB104"))
    )
    (comp (ref "C243")
      (value "CS0402KRX7R8BB104")
      (footprint "eagle-import:CAPC1005X65N")
      (fields (field (name "MOUSER_PART_NUMBER") "603-CS0402KRX78BB104"))
      (libsource (lib "eagle-import") (part "CS0402KRX7R8BB104"))
    )
    (comp (ref "C244")
      (value "CS0402KRX7R8BB104")
      (footprint "eagle-import:CAPC1005X65N")
      (fields (field (name "MOUSER_PART_NUMBER") "603-CS0402KRX78BB104"))
      (libsource (lib "eagle-import") (part "CS0402KRX7R8BB104"))
    )
    (comp (ref "C245")
      (value "CS0402KRX7R8BB104")
      (footprint "eagle-import:CAPC1005X65N")
      (fields (field (name "MOUSER_PART_NUMBER") "603-CS0402KRX78BB104"))
      (libsource (lib "eagle-import") (part "CS0402KRX7R8BB104"))
    )
    (comp (ref "C246")
      (value "CS0402KRX7R8BB104")
      (footprint "eagle-import:CAPC1005X65N")
      (fields (field (name "MOUSER_PART_NUMBER") "603-CS0402KRX78BB104"))
      (libsource (lib "eagle-import") (part "CS0402KRX7R8BB104"))
    )
    (comp (ref "IC35")
      (value "NCS21911SN2T1G")
      (footprint "eagle-import:SOT95P275X110-5N")
      (fields (field (name "MOUSER_PART_NUMBER") "863-NCS21911SN2T1G"))
      (libsource (lib "eagle-import") (part "NCS21911SN2T1G"))
    )
    (comp (ref "IC36")
      (value "NCS21911SN2T1G")
      (footprint "eagle-import:SOT95P275X110-5N")
      (fields (field (name "MOUSER_PART_NUMBER") "863-NCS21911SN2T1G"))
      (libsource (lib "eagle-import") (part "NCS21911SN2T1G"))
    )
    (comp (ref "IC37")
      (value "NCS21911SN2T1G")
      (footprint "eagle-import:SOT95P275X110-5N")
      (fields (field (name "MOUSER_PART_NUMBER") "863-NCS21911SN2T1G"))
      (libsource (lib "eagle-import") (part "NCS21911SN2T1G"))
    )
    (comp (ref "IC38")
      (value "ADS8588HIPM")
      (footprint "eagle-import:QFP50P1200X1200X160-64N_NO_3D")
      (libsource (lib "eagle-import") (part "ADS8588HIPM"))
    )
    (comp (ref "IC39")
      (value "NCS21911SN2T1G")
      (footprint "eagle-import:SOT95P275X110-5N")
      (fields (field (name "MOUSER_PART_NUMBER") "863-NCS21911SN2T1G"))
      (libsource (lib "eagle-import") (part "NCS21911SN2T1G"))
    )
    (comp (ref "IC40")
      (value "NCS21911SN2T1G")
      (footprint "eagle-import:SOT95P275X110-5N")
      (fields (field (name "MOUSER_PART_NUMBER") "863-NCS21911SN2T1G"))
      (libsource (lib "eagle-import") (part "NCS21911SN2T1G"))
    )
    (comp (ref "IC41")
      (value "NCS21911SN2T1G")
      (footprint "eagle-import:SOT95P275X110-5N")
      (fields (field (name "MOUSER_PART_NUMBER") "863-NCS21911SN2T1G"))
      (libsource (lib "eagle-import") (part "NCS21911SN2T1G"))
    )
    (comp (ref "IC42")
      (value "NCS21911SN2T1G")
      (footprint "eagle-import:SOT95P275X110-5N")
      (fields (field (name "MOUSER_PART_NUMBER") "863-NCS21911SN2T1G"))
      (libsource (lib "eagle-import") (part "NCS21911SN2T1G"))
    )
    (comp (ref "IC43")
      (value "NCS21911SN2T1G")
      (footprint "eagle-import:SOT95P275X110-5N")
      (fields (field (name "MOUSER_PART_NUMBER") "863-NCS21911SN2T1G"))
      (libsource (lib "eagle-import") (part "NCS21911SN2T1G"))
    )
    (comp (ref "IC44")
      (value "NCS21911SN2T1G")
      (footprint "eagle-import:SOT95P275X110-5N")
      (fields (field (name "MOUSER_PART_NUMBER") "863-NCS21911SN2T1G"))
      (libsource (lib "eagle-import") (part "NCS21911SN2T1G"))
    )
    (comp (ref "IC45")
      (value "NCS21911SN2T1G")
      (footprint "eagle-import:SOT95P275X110-5N")
      (fields (field (name "MOUSER_PART_NUMBER") "863-NCS21911SN2T1G"))
      (libsource (lib "eagle-import") (part "NCS21911SN2T1G"))
    )
    (comp (ref "IC46")
      (value "NCS21911SN2T1G")
      (footprint "eagle-import:SOT95P275X110-5N")
      (fields (field (name "MOUSER_PART_NUMBER") "863-NCS21911SN2T1G"))
      (libsource (lib "eagle-import") (part "NCS21911SN2T1G"))
    )
    (comp (ref "IC47")
      (value "NCS21911SN2T1G")
      (footprint "eagle-import:SOT95P275X110-5N")
      (fields (field (name "MOUSER_PART_NUMBER") "863-NCS21911SN2T1G"))
      (libsource (lib "eagle-import") (part "NCS21911SN2T1G"))
    )
    (comp (ref "IC48")
      (value "NCS21911SN2T1G")
      (footprint "eagle-import:SOT95P275X110-5N")
      (fields (field (name "MOUSER_PART_NUMBER") "863-NCS21911SN2T1G"))
      (libsource (lib "eagle-import") (part "NCS21911SN2T1G"))
    )
    (comp (ref "IC49")
      (value "NCS21911SN2T1G")
      (footprint "eagle-import:SOT95P275X110-5N")
      (fields (field (name "MOUSER_PART_NUMBER") "863-NCS21911SN2T1G"))
      (libsource (lib "eagle-import") (part "NCS21911SN2T1G"))
    )
    (comp (ref "IC50")
      (value "NCS21911SN2T1G")
      (footprint "eagle-import:SOT95P275X110-5N")
      (fields (field (name "MOUSER_PART_NUMBER") "863-NCS21911SN2T1G"))
      (libsource (lib "eagle-import") (part "NCS21911SN2T1G"))
    )
    (comp (ref "IC51")
      (value "ADS8588HIPM")
      (footprint "eagle-import:QFP50P1200X1200X160-64N_NO_3D")
      (libsource (lib "eagle-import") (part "ADS8588HIPM"))
    )
    (comp (ref "IC53")
      (value "NCS21911SN2T1G")
      (footprint "eagle-import:SOT95P275X110-5N")
      (fields (field (name "MOUSER_PART_NUMBER") "863-NCS21911SN2T1G"))
      (libsource (lib "eagle-import") (part "NCS21911SN2T1G"))
    )
    (comp (ref "IC54")
      (value "NCS21911SN2T1G")
      (footprint "eagle-import:SOT95P275X110-5N")
      (fields (field (name "MOUSER_PART_NUMBER") "863-NCS21911SN2T1G"))
      (libsource (lib "eagle-import") (part "NCS21911SN2T1G"))
    )
    (comp (ref "IC55")
      (value "NCS21911SN2T1G")
      (footprint "eagle-import:SOT95P275X110-5N")
      (fields (field (name "MOUSER_PART_NUMBER") "863-NCS21911SN2T1G"))
      (libsource (lib "eagle-import") (part "NCS21911SN2T1G"))
    )
    (comp (ref "IC56")
      (value "NCS21911SN2T1G")
      (footprint "eagle-import:SOT95P275X110-5N")
      (fields (field (name "MOUSER_PART_NUMBER") "863-NCS21911SN2T1G"))
      (libsource (lib "eagle-import") (part "NCS21911SN2T1G"))
    )
    (comp (ref "IC57")
      (value "NCS21911SN2T1G")
      (footprint "eagle-import:SOT95P275X110-5N")
      (fields (field (name "MOUSER_PART_NUMBER") "863-NCS21911SN2T1G"))
      (libsource (lib "eagle-import") (part "NCS21911SN2T1G"))
    )
    (comp (ref "IC58")
      (value "NCS21911SN2T1G")
      (footprint "eagle-import:SOT95P275X110-5N")
      (fields (field (name "MOUSER_PART_NUMBER") "863-NCS21911SN2T1G"))
      (libsource (lib "eagle-import") (part "NCS21911SN2T1G"))
    )
    (comp (ref "IC59")
      (value "NCS21911SN2T1G")
      (footprint "eagle-import:SOT95P275X110-5N")
      (fields (field (name "MOUSER_PART_NUMBER") "863-NCS21911SN2T1G"))
      (libsource (lib "eagle-import") (part "NCS21911SN2T1G"))
    )
    (comp (ref "IC60")
      (value "NCS21911SN2T1G")
      (footprint "eagle-import:SOT95P275X110-5N")
      (fields (field (name "MOUSER_PART_NUMBER") "863-NCS21911SN2T1G"))
      (libsource (lib "eagle-import") (part "NCS21911SN2T1G"))
    )
    (comp (ref "IC61")
      (value "NCS21911SN2T1G")
      (footprint "eagle-import:SOT95P275X110-5N")
      (fields (field (name "MOUSER_PART_NUMBER") "863-NCS21911SN2T1G"))
      (libsource (lib "eagle-import") (part "NCS21911SN2T1G"))
    )
    (comp (ref "IC62")
      (value "NCS21911SN2T1G")
      (footprint "eagle-import:SOT95P275X110-5N")
      (fields (field (name "MOUSER_PART_NUMBER") "863-NCS21911SN2T1G"))
      (libsource (lib "eagle-import") (part "NCS21911SN2T1G"))
    )
    (comp (ref "IC63")
      (value "NCS21911SN2T1G")
      (footprint "eagle-import:SOT95P275X110-5N")
      (fields (field (name "MOUSER_PART_NUMBER") "863-NCS21911SN2T1G"))
      (libsource (lib "eagle-import") (part "NCS21911SN2T1G"))
    )
    (comp (ref "IC64")
      (value "NCS21911SN2T1G")
      (footprint "eagle-import:SOT95P275X110-5N")
      (fields (field (name "MOUSER_PART_NUMBER") "863-NCS21911SN2T1G"))
      (libsource (lib "eagle-import") (part "NCS21911SN2T1G"))
    )
    (comp (ref "IC65")
      (value "NCS21911SN2T1G")
      (footprint "eagle-import:SOT95P275X110-5N")
      (fields (field (name "MOUSER_PART_NUMBER") "863-NCS21911SN2T1G"))
      (libsource (lib "eagle-import") (part "NCS21911SN2T1G"))
    )
    (comp (ref "IC66")
      (value "NCS21911SN2T1G")
      (footprint "eagle-import:SOT95P275X110-5N")
      (fields (field (name "MOUSER_PART_NUMBER") "863-NCS21911SN2T1G"))
      (libsource (lib "eagle-import") (part "NCS21911SN2T1G"))
    )
    (comp (ref "IC67")
      (value "NCS21911SN2T1G")
      (footprint "eagle-import:SOT95P275X110-5N")
      (fields (field (name "MOUSER_PART_NUMBER") "863-NCS21911SN2T1G"))
      (libsource (lib "eagle-import") (part "NCS21911SN2T1G"))
    )
    (comp (ref "IC68")
      (value "NCS21911SN2T1G")
      (footprint "eagle-import:SOT95P275X110-5N")
      (fields (field (name "MOUSER_PART_NUMBER") "863-NCS21911SN2T1G"))
      (libsource (lib "eagle-import") (part "NCS21911SN2T1G"))
    )
    (comp (ref "IC69")
      (value "NCS21911SN2T1G")
      (footprint "eagle-import:SOT95P275X110-5N")
      (fields (field (name "MOUSER_PART_NUMBER") "863-NCS21911SN2T1G"))
      (libsource (lib "eagle-import") (part "NCS21911SN2T1G"))
    )
    (comp (ref "R1")
      (value "RC0402FR-075K23L")
      (footprint "eagle-import:RESC1005X40N")
      (fields (field (name "MOUSER_PART_NUMBER") "603-RC0402FR-075K23L"))
      (libsource (lib "eagle-import") (part "RC0402FR-075K23L"))
    )
    (comp (ref "R2")
      (value "RC0402FR-0793K1L")
      (footprint "eagle-import:RESC1005X40N")
      (fields (field (name "MOUSER_PART_NUMBER") "603-RC0402FR-0793K1L"))
      (libsource (lib "eagle-import") (part "RC0402FR-0793K1L"))
    )
    (comp (ref "R3")
      (value "CRCW04021K30FKTD")
      (footprint "eagle-import:RESC1005X40N")
      (fields (field (name "MOUSER_PART_NUMBER") "71-CRCW0402-1.3K"))
      (libsource (lib "eagle-import") (part "CRCW04021K30FKTD"))
    )
    (comp (ref "R4")
      (value "CRCW04021K30FKTD")
      (footprint "eagle-import:RESC1005X40N")
      (fields (field (name "MOUSER_PART_NUMBER") "71-CRCW0402-1.3K"))
      (libsource (lib "eagle-import") (part "CRCW04021K30FKTD"))
    )
    (comp (ref "R5")
      (value "RC0402FR-075K23L")
      (footprint "eagle-import:RESC1005X40N")
      (fields (field (name "MOUSER_PART_NUMBER") "603-RC0402FR-075K23L"))
      (libsource (lib "eagle-import") (part "RC0402FR-075K23L"))
    )
    (comp (ref "R6")
      (value "RC0402FR-0793K1L")
      (footprint "eagle-import:RESC1005X40N")
      (fields (field (name "MOUSER_PART_NUMBER") "603-RC0402FR-0793K1L"))
      (libsource (lib "eagle-import") (part "RC0402FR-0793K1L"))
    )
    (comp (ref "R7")
      (value "CRCW04021K30FKTD")
      (footprint "eagle-import:RESC1005X40N")
      (fields (field (name "MOUSER_PART_NUMBER") "71-CRCW0402-1.3K"))
      (libsource (lib "eagle-import") (part "CRCW04021K30FKTD"))
    )
    (comp (ref "R8")
      (value "CRCW04021K30FKTD")
      (footprint "eagle-import:RESC1005X40N")
      (fields (field (name "MOUSER_PART_NUMBER") "71-CRCW0402-1.3K"))
      (libsource (lib "eagle-import") (part "CRCW04021K30FKTD"))
    )
    (comp (ref "R9")
      (value "RC0402FR-075K23L")
      (footprint "eagle-import:RESC1005X40N")
      (fields (field (name "MOUSER_PART_NUMBER") "603-RC0402FR-075K23L"))
      (libsource (lib "eagle-import") (part "RC0402FR-075K23L"))
    )
    (comp (ref "R10")
      (value "RC0402FR-0793K1L")
      (footprint "eagle-import:RESC1005X40N")
      (fields (field (name "MOUSER_PART_NUMBER") "603-RC0402FR-0793K1L"))
      (libsource (lib "eagle-import") (part "RC0402FR-0793K1L"))
    )
    (comp (ref "R11")
      (value "CRCW04021K30FKTD")
      (footprint "eagle-import:RESC1005X40N")
      (fields (field (name "MOUSER_PART_NUMBER") "71-CRCW0402-1.3K"))
      (libsource (lib "eagle-import") (part "CRCW04021K30FKTD"))
    )
    (comp (ref "R12")
      (value "CRCW04021K30FKTD")
      (footprint "eagle-import:RESC1005X40N")
      (fields (field (name "MOUSER_PART_NUMBER") "71-CRCW0402-1.3K"))
      (libsource (lib "eagle-import") (part "CRCW04021K30FKTD"))
    )
    (comp (ref "R13")
      (value "RC0402FR-075K23L")
      (footprint "eagle-import:RESC1005X40N")
      (fields (field (name "MOUSER_PART_NUMBER") "603-RC0402FR-075K23L"))
      (libsource (lib "eagle-import") (part "RC0402FR-075K23L"))
    )
    (comp (ref "R14")
      (value "RC0402FR-0793K1L")
      (footprint "eagle-import:RESC1005X40N")
      (fields (field (name "MOUSER_PART_NUMBER") "603-RC0402FR-0793K1L"))
      (libsource (lib "eagle-import") (part "RC0402FR-0793K1L"))
    )
    (comp (ref "R15")
      (value "CRCW04021K30FKTD")
      (footprint "eagle-import:RESC1005X40N")
      (fields (field (name "MOUSER_PART_NUMBER") "71-CRCW0402-1.3K"))
      (libsource (lib "eagle-import") (part "CRCW04021K30FKTD"))
    )
    (comp (ref "R16")
      (value "CRCW04021K30FKTD")
      (footprint "eagle-import:RESC1005X40N")
      (fields (field (name "MOUSER_PART_NUMBER") "71-CRCW0402-1.3K"))
      (libsource (lib "eagle-import") (part "CRCW04021K30FKTD"))
    )
    (comp (ref "R17")
      (value "RC0402FR-075K23L")
      (footprint "eagle-import:RESC1005X40N")
      (fields (field (name "MOUSER_PART_NUMBER") "603-RC0402FR-075K23L"))
      (libsource (lib "eagle-import") (part "RC0402FR-075K23L"))
    )
    (comp (ref "R18")
      (value "RC0402FR-0793K1L")
      (footprint "eagle-import:RESC1005X40N")
      (fields (field (name "MOUSER_PART_NUMBER") "603-RC0402FR-0793K1L"))
      (libsource (lib "eagle-import") (part "RC0402FR-0793K1L"))
    )
    (comp (ref "R19")
      (value "CRCW04021K30FKTD")
      (footprint "eagle-import:RESC1005X40N")
      (fields (field (name "MOUSER_PART_NUMBER") "71-CRCW0402-1.3K"))
      (libsource (lib "eagle-import") (part "CRCW04021K30FKTD"))
    )
    (comp (ref "R20")
      (value "CRCW04021K30FKTD")
      (footprint "eagle-import:RESC1005X40N")
      (fields (field (name "MOUSER_PART_NUMBER") "71-CRCW0402-1.3K"))
      (libsource (lib "eagle-import") (part "CRCW04021K30FKTD"))
    )
    (comp (ref "R21")
      (value "RC0402FR-075K23L")
      (footprint "eagle-import:RESC1005X40N")
      (fields (field (name "MOUSER_PART_NUMBER") "603-RC0402FR-075K23L"))
      (libsource (lib "eagle-import") (part "RC0402FR-075K23L"))
    )
    (comp (ref "R22")
      (value "RC0402FR-0793K1L")
      (footprint "eagle-import:RESC1005X40N")
      (fields (field (name "MOUSER_PART_NUMBER") "603-RC0402FR-0793K1L"))
      (libsource (lib "eagle-import") (part "RC0402FR-0793K1L"))
    )
    (comp (ref "R23")
      (value "CRCW04021K30FKTD")
      (footprint "eagle-import:RESC1005X40N")
      (fields (field (name "MOUSER_PART_NUMBER") "71-CRCW0402-1.3K"))
      (libsource (lib "eagle-import") (part "CRCW04021K30FKTD"))
    )
    (comp (ref "R24")
      (value "CRCW04021K30FKTD")
      (footprint "eagle-import:RESC1005X40N")
      (fields (field (name "MOUSER_PART_NUMBER") "71-CRCW0402-1.3K"))
      (libsource (lib "eagle-import") (part "CRCW04021K30FKTD"))
    )
    (comp (ref "R25")
      (value "RC0402FR-075K23L")
      (footprint "eagle-import:RESC1005X40N")
      (fields (field (name "MOUSER_PART_NUMBER") "603-RC0402FR-075K23L"))
      (libsource (lib "eagle-import") (part "RC0402FR-075K23L"))
    )
    (comp (ref "R26")
      (value "RC0402FR-0793K1L")
      (footprint "eagle-import:RESC1005X40N")
      (fields (field (name "MOUSER_PART_NUMBER") "603-RC0402FR-0793K1L"))
      (libsource (lib "eagle-import") (part "RC0402FR-0793K1L"))
    )
    (comp (ref "R27")
      (value "CRCW04021K30FKTD")
      (footprint "eagle-import:RESC1005X40N")
      (fields (field (name "MOUSER_PART_NUMBER") "71-CRCW0402-1.3K"))
      (libsource (lib "eagle-import") (part "CRCW04021K30FKTD"))
    )
    (comp (ref "R28")
      (value "CRCW04021K30FKTD")
      (footprint "eagle-import:RESC1005X40N")
      (fields (field (name "MOUSER_PART_NUMBER") "71-CRCW0402-1.3K"))
      (libsource (lib "eagle-import") (part "CRCW04021K30FKTD"))
    )
    (comp (ref "R29")
      (value "RC0402FR-075K23L")
      (footprint "eagle-import:RESC1005X40N")
      (fields (field (name "MOUSER_PART_NUMBER") "603-RC0402FR-075K23L"))
      (libsource (lib "eagle-import") (part "RC0402FR-075K23L"))
    )
    (comp (ref "R30")
      (value "RC0402FR-0793K1L")
      (footprint "eagle-import:RESC1005X40N")
      (fields (field (name "MOUSER_PART_NUMBER") "603-RC0402FR-0793K1L"))
      (libsource (lib "eagle-import") (part "RC0402FR-0793K1L"))
    )
    (comp (ref "R31")
      (value "CRCW04021K30FKTD")
      (footprint "eagle-import:RESC1005X40N")
      (fields (field (name "MOUSER_PART_NUMBER") "71-CRCW0402-1.3K"))
      (libsource (lib "eagle-import") (part "CRCW04021K30FKTD"))
    )
    (comp (ref "R32")
      (value "CRCW04021K30FKTD")
      (footprint "eagle-import:RESC1005X40N")
      (fields (field (name "MOUSER_PART_NUMBER") "71-CRCW0402-1.3K"))
      (libsource (lib "eagle-import") (part "CRCW04021K30FKTD"))
    )
    (comp (ref "R73")
      (value "RC0402FR-075K23L")
      (footprint "eagle-import:RESC1005X40N")
      (fields (field (name "MOUSER_PART_NUMBER") "603-RC0402FR-075K23L"))
      (libsource (lib "eagle-import") (part "RC0402FR-075K23L"))
    )
    (comp (ref "R74")
      (value "RC0402FR-0793K1L")
      (footprint "eagle-import:RESC1005X40N")
      (fields (field (name "MOUSER_PART_NUMBER") "603-RC0402FR-0793K1L"))
      (libsource (lib "eagle-import") (part "RC0402FR-0793K1L"))
    )
    (comp (ref "R75")
      (value "CRCW04021K30FKTD")
      (footprint "eagle-import:RESC1005X40N")
      (fields (field (name "MOUSER_PART_NUMBER") "71-CRCW0402-1.3K"))
      (libsource (lib "eagle-import") (part "CRCW04021K30FKTD"))
    )
    (comp (ref "R76")
      (value "CRCW04021K30FKTD")
      (footprint "eagle-import:RESC1005X40N")
      (fields (field (name "MOUSER_PART_NUMBER") "71-CRCW0402-1.3K"))
      (libsource (lib "eagle-import") (part "CRCW04021K30FKTD"))
    )
    (comp (ref "R77")
      (value "RC0402FR-075K23L")
      (footprint "eagle-import:RESC1005X40N")
      (fields (field (name "MOUSER_PART_NUMBER") "603-RC0402FR-075K23L"))
      (libsource (lib "eagle-import") (part "RC0402FR-075K23L"))
    )
    (comp (ref "R78")
      (value "RC0402FR-0793K1L")
      (footprint "eagle-import:RESC1005X40N")
      (fields (field (name "MOUSER_PART_NUMBER") "603-RC0402FR-0793K1L"))
      (libsource (lib "eagle-import") (part "RC0402FR-0793K1L"))
    )
    (comp (ref "R79")
      (value "CRCW04021K30FKTD")
      (footprint "eagle-import:RESC1005X40N")
      (fields (field (name "MOUSER_PART_NUMBER") "71-CRCW0402-1.3K"))
      (libsource (lib "eagle-import") (part "CRCW04021K30FKTD"))
    )
    (comp (ref "R80")
      (value "CRCW04021K30FKTD")
      (footprint "eagle-import:RESC1005X40N")
      (fields (field (name "MOUSER_PART_NUMBER") "71-CRCW0402-1.3K"))
      (libsource (lib "eagle-import") (part "CRCW04021K30FKTD"))
    )
    (comp (ref "R81")
      (value "RC0402FR-075K23L")
      (footprint "eagle-import:RESC1005X40N")
      (fields (field (name "MOUSER_PART_NUMBER") "603-RC0402FR-075K23L"))
      (libsource (lib "eagle-import") (part "RC0402FR-075K23L"))
    )
    (comp (ref "R82")
      (value "RC0402FR-0793K1L")
      (footprint "eagle-import:RESC1005X40N")
      (fields (field (name "MOUSER_PART_NUMBER") "603-RC0402FR-0793K1L"))
      (libsource (lib "eagle-import") (part "RC0402FR-0793K1L"))
    )
    (comp (ref "R83")
      (value "CRCW04021K30FKTD")
      (footprint "eagle-import:RESC1005X40N")
      (fields (field (name "MOUSER_PART_NUMBER") "71-CRCW0402-1.3K"))
      (libsource (lib "eagle-import") (part "CRCW04021K30FKTD"))
    )
    (comp (ref "R84")
      (value "CRCW04021K30FKTD")
      (footprint "eagle-import:RESC1005X40N")
      (fields (field (name "MOUSER_PART_NUMBER") "71-CRCW0402-1.3K"))
      (libsource (lib "eagle-import") (part "CRCW04021K30FKTD"))
    )
    (comp (ref "R85")
      (value "RC0402FR-075K23L")
      (footprint "eagle-import:RESC1005X40N")
      (fields (field (name "MOUSER_PART_NUMBER") "603-RC0402FR-075K23L"))
      (libsource (lib "eagle-import") (part "RC0402FR-075K23L"))
    )
    (comp (ref "R86")
      (value "RC0402FR-0793K1L")
      (footprint "eagle-import:RESC1005X40N")
      (fields (field (name "MOUSER_PART_NUMBER") "603-RC0402FR-0793K1L"))
      (libsource (lib "eagle-import") (part "RC0402FR-0793K1L"))
    )
    (comp (ref "R87")
      (value "CRCW04021K30FKTD")
      (footprint "eagle-import:RESC1005X40N")
      (fields (field (name "MOUSER_PART_NUMBER") "71-CRCW0402-1.3K"))
      (libsource (lib "eagle-import") (part "CRCW04021K30FKTD"))
    )
    (comp (ref "R88")
      (value "CRCW04021K30FKTD")
      (footprint "eagle-import:RESC1005X40N")
      (fields (field (name "MOUSER_PART_NUMBER") "71-CRCW0402-1.3K"))
      (libsource (lib "eagle-import") (part "CRCW04021K30FKTD"))
    )
    (comp (ref "R98")
      (value "RC0402FR-075K23L")
      (footprint "eagle-import:RESC1005X40N")
      (fields (field (name "MOUSER_PART_NUMBER") "603-RC0402FR-075K23L"))
      (libsource (lib "eagle-import") (part "RC0402FR-075K23L"))
    )
    (comp (ref "R102")
      (value "RC0402FR-0793K1L")
      (footprint "eagle-import:RESC1005X40N")
      (fields (field (name "MOUSER_PART_NUMBER") "603-RC0402FR-0793K1L"))
      (libsource (lib "eagle-import") (part "RC0402FR-0793K1L"))
    )
    (comp (ref "R103")
      (value "CRCW04021K30FKTD")
      (footprint "eagle-import:RESC1005X40N")
      (fields (field (name "MOUSER_PART_NUMBER") "71-CRCW0402-1.3K"))
      (libsource (lib "eagle-import") (part "CRCW04021K30FKTD"))
    )
    (comp (ref "R104")
      (value "CRCW04021K30FKTD")
      (footprint "eagle-import:RESC1005X40N")
      (fields (field (name "MOUSER_PART_NUMBER") "71-CRCW0402-1.3K"))
      (libsource (lib "eagle-import") (part "CRCW04021K30FKTD"))
    )
    (comp (ref "R105")
      (value "RC0402FR-075K23L")
      (footprint "eagle-import:RESC1005X40N")
      (fields (field (name "MOUSER_PART_NUMBER") "603-RC0402FR-075K23L"))
      (libsource (lib "eagle-import") (part "RC0402FR-075K23L"))
    )
    (comp (ref "R106")
      (value "RC0402FR-0793K1L")
      (footprint "eagle-import:RESC1005X40N")
      (fields (field (name "MOUSER_PART_NUMBER") "603-RC0402FR-0793K1L"))
      (libsource (lib "eagle-import") (part "RC0402FR-0793K1L"))
    )
    (comp (ref "R107")
      (value "CRCW04021K30FKTD")
      (footprint "eagle-import:RESC1005X40N")
      (fields (field (name "MOUSER_PART_NUMBER") "71-CRCW0402-1.3K"))
      (libsource (lib "eagle-import") (part "CRCW04021K30FKTD"))
    )
    (comp (ref "R108")
      (value "CRCW04021K30FKTD")
      (footprint "eagle-import:RESC1005X40N")
      (fields (field (name "MOUSER_PART_NUMBER") "71-CRCW0402-1.3K"))
      (libsource (lib "eagle-import") (part "CRCW04021K30FKTD"))
    )
    (comp (ref "R151")
      (value "RC0402FR-075K23L")
      (footprint "eagle-import:RESC1005X40N")
      (fields (field (name "MOUSER_PART_NUMBER") "603-RC0402FR-075K23L"))
      (libsource (lib "eagle-import") (part "RC0402FR-075K23L"))
    )
    (comp (ref "R152")
      (value "RC0402FR-0793K1L")
      (footprint "eagle-import:RESC1005X40N")
      (fields (field (name "MOUSER_PART_NUMBER") "603-RC0402FR-0793K1L"))
      (libsource (lib "eagle-import") (part "RC0402FR-0793K1L"))
    )
    (comp (ref "R153")
      (value "CRCW04021K30FKTD")
      (footprint "eagle-import:RESC1005X40N")
      (fields (field (name "MOUSER_PART_NUMBER") "71-CRCW0402-1.3K"))
      (libsource (lib "eagle-import") (part "CRCW04021K30FKTD"))
    )
    (comp (ref "R154")
      (value "CRCW04021K30FKTD")
      (footprint "eagle-import:RESC1005X40N")
      (fields (field (name "MOUSER_PART_NUMBER") "71-CRCW0402-1.3K"))
      (libsource (lib "eagle-import") (part "CRCW04021K30FKTD"))
    )
    (comp (ref "R155")
      (value "RC0402FR-075K23L")
      (footprint "eagle-import:RESC1005X40N")
      (fields (field (name "MOUSER_PART_NUMBER") "603-RC0402FR-075K23L"))
      (libsource (lib "eagle-import") (part "RC0402FR-075K23L"))
    )
    (comp (ref "R156")
      (value "RC0402FR-0793K1L")
      (footprint "eagle-import:RESC1005X40N")
      (fields (field (name "MOUSER_PART_NUMBER") "603-RC0402FR-0793K1L"))
      (libsource (lib "eagle-import") (part "RC0402FR-0793K1L"))
    )
    (comp (ref "R157")
      (value "CRCW04021K30FKTD")
      (footprint "eagle-import:RESC1005X40N")
      (fields (field (name "MOUSER_PART_NUMBER") "71-CRCW0402-1.3K"))
      (libsource (lib "eagle-import") (part "CRCW04021K30FKTD"))
    )
    (comp (ref "R158")
      (value "CRCW04021K30FKTD")
      (footprint "eagle-import:RESC1005X40N")
      (fields (field (name "MOUSER_PART_NUMBER") "71-CRCW0402-1.3K"))
      (libsource (lib "eagle-import") (part "CRCW04021K30FKTD"))
    )
    (comp (ref "J3")
      (value "MEM2051-00-195-00-A")
      (footprint "eagle-import:MEM20510019500A")
      (fields (field (name "MOUSER_PART_NUMBER") "640-MEM20510019500A"))
      (libsource (lib "eagle-import") (part "MEM2051-00-195-00-A"))
    )
    (comp (ref "!CS_ADC")
      (value "SMALL_TP")
      (footprint "eagle-import:SMALL_TP")
      (libsource (lib "eagle-import") (part "SMALL_TP"))
    )
    (comp (ref "!IMU_CS")
      (value "SMALL_TP")
      (footprint "eagle-import:SMALL_TP")
      (libsource (lib "eagle-import") (part "SMALL_TP"))
    )
    (comp (ref "!IMU_RST")
      (value "SMALL_TP")
      (footprint "eagle-import:SMALL_TP")
      (libsource (lib "eagle-import") (part "SMALL_TP"))
    )
    (comp (ref "!ISO_CS")
      (value "SMALL_TP")
      (footprint "eagle-import:SMALL_TP")
      (libsource (lib "eagle-import") (part "SMALL_TP"))
    )
    (comp (ref "!TEMP_CS")
      (value "SMALL_TP")
      (footprint "eagle-import:SMALL_TP")
      (libsource (lib "eagle-import") (part "SMALL_TP"))
    )
    (comp (ref "40G_GPIO")
      (value "SMALL_TP")
      (footprint "eagle-import:SMALL_TP")
      (libsource (lib "eagle-import") (part "SMALL_TP"))
    )
    (comp (ref "BUSY_ADC_1")
      (value "SMALL_TP")
      (footprint "eagle-import:SMALL_TP")
      (libsource (lib "eagle-import") (part "SMALL_TP"))
    )
    (comp (ref "BUSY_ADC_2")
      (value "SMALL_TP")
      (footprint "eagle-import:SMALL_TP")
      (libsource (lib "eagle-import") (part "SMALL_TP"))
    )
    (comp (ref "BUSY_ADC_3")
      (value "SMALL_TP")
      (footprint "eagle-import:SMALL_TP")
      (libsource (lib "eagle-import") (part "SMALL_TP"))
    )
    (comp (ref "CD/DAT3_SPI-CS")
      (value "SMALL_TP")
      (footprint "eagle-import:SMALL_TP")
      (libsource (lib "eagle-import") (part "SMALL_TP"))
    )
    (comp (ref "CLK")
      (value "SMALL_TP")
      (footprint "eagle-import:SMALL_TP")
      (libsource (lib "eagle-import") (part "SMALL_TP"))
    )
    (comp (ref "CMD_SPI-DI")
      (value "SMALL_TP")
      (footprint "eagle-import:SMALL_TP")
      (libsource (lib "eagle-import") (part "SMALL_TP"))
    )
    (comp (ref "CONVAB_ADC")
      (value "SMALL_TP")
      (footprint "eagle-import:SMALL_TP")
      (libsource (lib "eagle-import") (part "SMALL_TP"))
    )
    (comp (ref "DAT1")
      (value "SMALL_TP")
      (footprint "eagle-import:SMALL_TP")
      (libsource (lib "eagle-import") (part "SMALL_TP"))
    )
    (comp (ref "DAT2")
      (value "SMALL_TP")
      (footprint "eagle-import:SMALL_TP")
      (libsource (lib "eagle-import") (part "SMALL_TP"))
    )
    (comp (ref "DAT_SPI-DO")
      (value "SMALL_TP")
      (footprint "eagle-import:SMALL_TP")
      (libsource (lib "eagle-import") (part "SMALL_TP"))
    )
    (comp (ref "DIN1")
      (value "SMALL_TP")
      (footprint "eagle-import:SMALL_TP")
      (libsource (lib "eagle-import") (part "SMALL_TP"))
    )
    (comp (ref "DIN2")
      (value "SMALL_TP")
      (footprint "eagle-import:SMALL_TP")
      (libsource (lib "eagle-import") (part "SMALL_TP"))
    )
    (comp (ref "DIN3")
      (value "SMALL_TP")
      (footprint "eagle-import:SMALL_TP")
      (libsource (lib "eagle-import") (part "SMALL_TP"))
    )
    (comp (ref "DIN4")
      (value "SMALL_TP")
      (footprint "eagle-import:SMALL_TP")
      (libsource (lib "eagle-import") (part "SMALL_TP"))
    )
    (comp (ref "DIN5")
      (value "SMALL_TP")
      (footprint "eagle-import:SMALL_TP")
      (libsource (lib "eagle-import") (part "SMALL_TP"))
    )
    (comp (ref "DIN6")
      (value "SMALL_TP")
      (footprint "eagle-import:SMALL_TP")
      (libsource (lib "eagle-import") (part "SMALL_TP"))
    )
    (comp (ref "DIN7")
      (value "SMALL_TP")
      (footprint "eagle-import:SMALL_TP")
      (libsource (lib "eagle-import") (part "SMALL_TP"))
    )
    (comp (ref "DIN8")
      (value "SMALL_TP")
      (footprint "eagle-import:SMALL_TP")
      (libsource (lib "eagle-import") (part "SMALL_TP"))
    )
    (comp (ref "DOUTA_ADC_1")
      (value "SMALL_TP")
      (footprint "eagle-import:SMALL_TP")
      (libsource (lib "eagle-import") (part "SMALL_TP"))
    )
    (comp (ref "DOUTA_ADC_2")
      (value "SMALL_TP")
      (footprint "eagle-import:SMALL_TP")
      (libsource (lib "eagle-import") (part "SMALL_TP"))
    )
    (comp (ref "DOUTA_ADC_3")
      (value "SMALL_TP")
      (footprint "eagle-import:SMALL_TP")
      (libsource (lib "eagle-import") (part "SMALL_TP"))
    )
    (comp (ref "DOUTB_ADC_1")
      (value "SMALL_TP")
      (footprint "eagle-import:SMALL_TP")
      (libsource (lib "eagle-import") (part "SMALL_TP"))
    )
    (comp (ref "DOUTB_ADC_2")
      (value "SMALL_TP")
      (footprint "eagle-import:SMALL_TP")
      (libsource (lib "eagle-import") (part "SMALL_TP"))
    )
    (comp (ref "DOUTB_ADC_3")
      (value "SMALL_TP")
      (footprint "eagle-import:SMALL_TP")
      (libsource (lib "eagle-import") (part "SMALL_TP"))
    )
    (comp (ref "FSTD_ADC_1")
      (value "SMALL_TP")
      (footprint "eagle-import:SMALL_TP")
      (libsource (lib "eagle-import") (part "SMALL_TP"))
    )
    (comp (ref "FSTD_ADC_2")
      (value "SMALL_TP")
      (footprint "eagle-import:SMALL_TP")
      (libsource (lib "eagle-import") (part "SMALL_TP"))
    )
    (comp (ref "FSTD_ADC_3")
      (value "SMALL_TP")
      (footprint "eagle-import:SMALL_TP")
      (libsource (lib "eagle-import") (part "SMALL_TP"))
    )
    (comp (ref "GPS_EN")
      (value "SMALL_TP")
      (footprint "eagle-import:SMALL_TP")
      (libsource (lib "eagle-import") (part "SMALL_TP"))
    )
    (comp (ref "GPS_RX")
      (value "SMALL_TP")
      (footprint "eagle-import:SMALL_TP")
      (libsource (lib "eagle-import") (part "SMALL_TP"))
    )
    (comp (ref "GPS_TX")
      (value "SMALL_TP")
      (footprint "eagle-import:SMALL_TP")
      (libsource (lib "eagle-import") (part "SMALL_TP"))
    )
    (comp (ref "IMU_DIN")
      (value "SMALL_TP")
      (footprint "eagle-import:SMALL_TP")
      (libsource (lib "eagle-import") (part "SMALL_TP"))
    )
    (comp (ref "IMU_DOUT")
      (value "SMALL_TP")
      (footprint "eagle-import:SMALL_TP")
      (libsource (lib "eagle-import") (part "SMALL_TP"))
    )
    (comp (ref "IMU_DR")
      (value "SMALL_TP")
      (footprint "eagle-import:SMALL_TP")
      (libsource (lib "eagle-import") (part "SMALL_TP"))
    )
    (comp (ref "IMU_SCLK")
      (value "SMALL_TP")
      (footprint "eagle-import:SMALL_TP")
      (libsource (lib "eagle-import") (part "SMALL_TP"))
    )
    (comp (ref "IMU_SYNC")
      (value "SMALL_TP")
      (footprint "eagle-import:SMALL_TP")
      (libsource (lib "eagle-import") (part "SMALL_TP"))
    )
    (comp (ref "ISO_MISO")
      (value "SMALL_TP")
      (footprint "eagle-import:SMALL_TP")
      (libsource (lib "eagle-import") (part "SMALL_TP"))
    )
    (comp (ref "ISO_MOSI")
      (value "SMALL_TP")
      (footprint "eagle-import:SMALL_TP")
      (libsource (lib "eagle-import") (part "SMALL_TP"))
    )
    (comp (ref "ISO_SPI_CH_SEL")
      (value "SMALL_TP")
      (footprint "eagle-import:SMALL_TP")
      (libsource (lib "eagle-import") (part "SMALL_TP"))
    )
    (comp (ref "ISO_SPI_HZ_SW")
      (value "SMALL_TP")
      (footprint "eagle-import:SMALL_TP")
      (libsource (lib "eagle-import") (part "SMALL_TP"))
    )
    (comp (ref "ISO_SPI_SCLK")
      (value "SMALL_TP")
      (footprint "eagle-import:SMALL_TP")
      (libsource (lib "eagle-import") (part "SMALL_TP"))
    )
    (comp (ref "ISO_SPI_SLOW")
      (value "SMALL_TP")
      (footprint "eagle-import:SMALL_TP")
      (libsource (lib "eagle-import") (part "SMALL_TP"))
    )
    (comp (ref "J4")
      (value "TFM-140-02-L-D-WT-K")
      (footprint "eagle-import:SAMTEC_TFM-140-02-L-D-WT-K")
      (fields (field (name "MANUFACTURER") "SAMTEC"))
      (libsource (lib "eagle-import") (part "TFM-140-02-L-D-WT-K"))
    )
    (comp (ref "J12")
      (value "TFM-140-02-L-D-WT-K")
      (footprint "eagle-import:SAMTEC_TFM-140-02-L-D-WT-K")
      (fields (field (name "MANUFACTURER") "SAMTEC"))
      (libsource (lib "eagle-import") (part "TFM-140-02-L-D-WT-K"))
    )
    (comp (ref "J14")
      (value "TFM-140-02-L-D-WT-K")
      (footprint "eagle-import:SAMTEC_TFM-140-02-L-D-WT-K")
      (fields (field (name "MANUFACTURER") "SAMTEC"))
      (libsource (lib "eagle-import") (part "TFM-140-02-L-D-WT-K"))
    )
    (comp (ref "LED_1")
      (value "SMALL_TP")
      (footprint "eagle-import:SMALL_TP")
      (libsource (lib "eagle-import") (part "SMALL_TP"))
    )
    (comp (ref "LED_2")
      (value "SMALL_TP")
      (footprint "eagle-import:SMALL_TP")
      (libsource (lib "eagle-import") (part "SMALL_TP"))
    )
    (comp (ref "LED_3")
      (value "SMALL_TP")
      (footprint "eagle-import:SMALL_TP")
      (libsource (lib "eagle-import") (part "SMALL_TP"))
    )
    (comp (ref "LED_P")
      (value "SMALL_TP")
      (footprint "eagle-import:SMALL_TP")
      (libsource (lib "eagle-import") (part "SMALL_TP"))
    )
    (comp (ref "MASS_ON")
      (value "SMALL_TP")
      (footprint "eagle-import:SMALL_TP")
      (libsource (lib "eagle-import") (part "SMALL_TP"))
    )
    (comp (ref "OS0_ADC")
      (value "SMALL_TP")
      (footprint "eagle-import:SMALL_TP")
      (libsource (lib "eagle-import") (part "SMALL_TP"))
    )
    (comp (ref "OS1_ADC")
      (value "SMALL_TP")
      (footprint "eagle-import:SMALL_TP")
      (libsource (lib "eagle-import") (part "SMALL_TP"))
    )
    (comp (ref "OS2_ADC")
      (value "SMALL_TP")
      (footprint "eagle-import:SMALL_TP")
      (libsource (lib "eagle-import") (part "SMALL_TP"))
    )
    (comp (ref "PA0")
      (value "SMALL_TP")
      (footprint "eagle-import:SMALL_TP")
      (libsource (lib "eagle-import") (part "SMALL_TP"))
    )
    (comp (ref "PA3")
      (value "SMALL_TP")
      (footprint "eagle-import:SMALL_TP")
      (libsource (lib "eagle-import") (part "SMALL_TP"))
    )
    (comp (ref "PA4")
      (value "SMALL_TP")
      (footprint "eagle-import:SMALL_TP")
      (libsource (lib "eagle-import") (part "SMALL_TP"))
    )
    (comp (ref "PA5")
      (value "SMALL_TP")
      (footprint "eagle-import:SMALL_TP")
      (libsource (lib "eagle-import") (part "SMALL_TP"))
    )
    (comp (ref "PA6")
      (value "SMALL_TP")
      (footprint "eagle-import:SMALL_TP")
      (libsource (lib "eagle-import") (part "SMALL_TP"))
    )
    (comp (ref "PA8")
      (value "SMALL_TP")
      (footprint "eagle-import:SMALL_TP")
      (libsource (lib "eagle-import") (part "SMALL_TP"))
    )
    (comp (ref "PA9")
      (value "SMALL_TP")
      (footprint "eagle-import:SMALL_TP")
      (libsource (lib "eagle-import") (part "SMALL_TP"))
    )
    (comp (ref "PA10")
      (value "SMALL_TP")
      (footprint "eagle-import:SMALL_TP")
      (libsource (lib "eagle-import") (part "SMALL_TP"))
    )
    (comp (ref "PA11")
      (value "SMALL_TP")
      (footprint "eagle-import:SMALL_TP")
      (libsource (lib "eagle-import") (part "SMALL_TP"))
    )
    (comp (ref "PA12")
      (value "SMALL_TP")
      (footprint "eagle-import:SMALL_TP")
      (libsource (lib "eagle-import") (part "SMALL_TP"))
    )
    (comp (ref "PA13")
      (value "SMALL_TP")
      (footprint "eagle-import:SMALL_TP")
      (libsource (lib "eagle-import") (part "SMALL_TP"))
    )
    (comp (ref "PA14")
      (value "SMALL_TP")
      (footprint "eagle-import:SMALL_TP")
      (libsource (lib "eagle-import") (part "SMALL_TP"))
    )
    (comp (ref "PA15")
      (value "SMALL_TP")
      (footprint "eagle-import:SMALL_TP")
      (libsource (lib "eagle-import") (part "SMALL_TP"))
    )
    (comp (ref "PB0")
      (value "SMALL_TP")
      (footprint "eagle-import:SMALL_TP")
      (libsource (lib "eagle-import") (part "SMALL_TP"))
    )
    (comp (ref "PB1")
      (value "SMALL_TP")
      (footprint "eagle-import:SMALL_TP")
      (libsource (lib "eagle-import") (part "SMALL_TP"))
    )
    (comp (ref "PB2")
      (value "SMALL_TP")
      (footprint "eagle-import:SMALL_TP")
      (libsource (lib "eagle-import") (part "SMALL_TP"))
    )
    (comp (ref "PB3")
      (value "SMALL_TP")
      (footprint "eagle-import:SMALL_TP")
      (libsource (lib "eagle-import") (part "SMALL_TP"))
    )
    (comp (ref "PB4")
      (value "SMALL_TP")
      (footprint "eagle-import:SMALL_TP")
      (libsource (lib "eagle-import") (part "SMALL_TP"))
    )
    (comp (ref "PB5")
      (value "SMALL_TP")
      (footprint "eagle-import:SMALL_TP")
      (libsource (lib "eagle-import") (part "SMALL_TP"))
    )
    (comp (ref "PB6")
      (value "SMALL_TP")
      (footprint "eagle-import:SMALL_TP")
      (libsource (lib "eagle-import") (part "SMALL_TP"))
    )
    (comp (ref "PB7")
      (value "SMALL_TP")
      (footprint "eagle-import:SMALL_TP")
      (libsource (lib "eagle-import") (part "SMALL_TP"))
    )
    (comp (ref "PB8")
      (value "SMALL_TP")
      (footprint "eagle-import:SMALL_TP")
      (libsource (lib "eagle-import") (part "SMALL_TP"))
    )
    (comp (ref "PB9")
      (value "SMALL_TP")
      (footprint "eagle-import:SMALL_TP")
      (libsource (lib "eagle-import") (part "SMALL_TP"))
    )
    (comp (ref "PB10")
      (value "SMALL_TP")
      (footprint "eagle-import:SMALL_TP")
      (libsource (lib "eagle-import") (part "SMALL_TP"))
    )
    (comp (ref "PB11")
      (value "SMALL_TP")
      (footprint "eagle-import:SMALL_TP")
      (libsource (lib "eagle-import") (part "SMALL_TP"))
    )
    (comp (ref "PB12")
      (value "SMALL_TP")
      (footprint "eagle-import:SMALL_TP")
      (libsource (lib "eagle-import") (part "SMALL_TP"))
    )
    (comp (ref "PB14")
      (value "SMALL_TP")
      (footprint "eagle-import:SMALL_TP")
      (libsource (lib "eagle-import") (part "SMALL_TP"))
    )
    (comp (ref "PB15")
      (value "SMALL_TP")
      (footprint "eagle-import:SMALL_TP")
      (libsource (lib "eagle-import") (part "SMALL_TP"))
    )
    (comp (ref "PC0")
      (value "SMALL_TP")
      (footprint "eagle-import:SMALL_TP")
      (libsource (lib "eagle-import") (part "SMALL_TP"))
    )
    (comp (ref "PC2")
      (value "SMALL_TP")
      (footprint "eagle-import:SMALL_TP")
      (libsource (lib "eagle-import") (part "SMALL_TP"))
    )
    (comp (ref "PC3")
      (value "SMALL_TP")
      (footprint "eagle-import:SMALL_TP")
      (libsource (lib "eagle-import") (part "SMALL_TP"))
    )
    (comp (ref "PC6")
      (value "SMALL_TP")
      (footprint "eagle-import:SMALL_TP")
      (libsource (lib "eagle-import") (part "SMALL_TP"))
    )
    (comp (ref "PC7")
      (value "SMALL_TP")
      (footprint "eagle-import:SMALL_TP")
      (libsource (lib "eagle-import") (part "SMALL_TP"))
    )
    (comp (ref "PC8")
      (value "SMALL_TP")
      (footprint "eagle-import:SMALL_TP")
      (libsource (lib "eagle-import") (part "SMALL_TP"))
    )
    (comp (ref "PC9")
      (value "SMALL_TP")
      (footprint "eagle-import:SMALL_TP")
      (libsource (lib "eagle-import") (part "SMALL_TP"))
    )
    (comp (ref "PC10")
      (value "SMALL_TP")
      (footprint "eagle-import:SMALL_TP")
      (libsource (lib "eagle-import") (part "SMALL_TP"))
    )
    (comp (ref "PC11")
      (value "SMALL_TP")
      (footprint "eagle-import:SMALL_TP")
      (libsource (lib "eagle-import") (part "SMALL_TP"))
    )
    (comp (ref "PC12")
      (value "SMALL_TP")
      (footprint "eagle-import:SMALL_TP")
      (libsource (lib "eagle-import") (part "SMALL_TP"))
    )
    (comp (ref "PC13")
      (value "SMALL_TP")
      (footprint "eagle-import:SMALL_TP")
      (libsource (lib "eagle-import") (part "SMALL_TP"))
    )
    (comp (ref "PD0")
      (value "SMALL_TP")
      (footprint "eagle-import:SMALL_TP")
      (libsource (lib "eagle-import") (part "SMALL_TP"))
    )
    (comp (ref "PD1")
      (value "SMALL_TP")
      (footprint "eagle-import:SMALL_TP")
      (libsource (lib "eagle-import") (part "SMALL_TP"))
    )
    (comp (ref "PD2")
      (value "SMALL_TP")
      (footprint "eagle-import:SMALL_TP")
      (libsource (lib "eagle-import") (part "SMALL_TP"))
    )
    (comp (ref "PD3")
      (value "SMALL_TP")
      (footprint "eagle-import:SMALL_TP")
      (libsource (lib "eagle-import") (part "SMALL_TP"))
    )
    (comp (ref "PD4")
      (value "SMALL_TP")
      (footprint "eagle-import:SMALL_TP")
      (libsource (lib "eagle-import") (part "SMALL_TP"))
    )
    (comp (ref "PD5")
      (value "SMALL_TP")
      (footprint "eagle-import:SMALL_TP")
      (libsource (lib "eagle-import") (part "SMALL_TP"))
    )
    (comp (ref "PD6")
      (value "SMALL_TP")
      (footprint "eagle-import:SMALL_TP")
      (libsource (lib "eagle-import") (part "SMALL_TP"))
    )
    (comp (ref "PD7")
      (value "SMALL_TP")
      (footprint "eagle-import:SMALL_TP")
      (libsource (lib "eagle-import") (part "SMALL_TP"))
    )
    (comp (ref "PD11")
      (value "SMALL_TP")
      (footprint "eagle-import:SMALL_TP")
      (libsource (lib "eagle-import") (part "SMALL_TP"))
    )
    (comp (ref "PD12")
      (value "SMALL_TP")
      (footprint "eagle-import:SMALL_TP")
      (libsource (lib "eagle-import") (part "SMALL_TP"))
    )
    (comp (ref "PD13")
      (value "SMALL_TP")
      (footprint "eagle-import:SMALL_TP")
      (libsource (lib "eagle-import") (part "SMALL_TP"))
    )
    (comp (ref "PD14")
      (value "SMALL_TP")
      (footprint "eagle-import:SMALL_TP")
      (libsource (lib "eagle-import") (part "SMALL_TP"))
    )
    (comp (ref "PD15")
      (value "SMALL_TP")
      (footprint "eagle-import:SMALL_TP")
      (libsource (lib "eagle-import") (part "SMALL_TP"))
    )
    (comp (ref "PE0")
      (value "SMALL_TP")
      (footprint "eagle-import:SMALL_TP")
      (libsource (lib "eagle-import") (part "SMALL_TP"))
    )
    (comp (ref "PE1")
      (value "SMALL_TP")
      (footprint "eagle-import:SMALL_TP")
      (libsource (lib "eagle-import") (part "SMALL_TP"))
    )
    (comp (ref "PE2")
      (value "SMALL_TP")
      (footprint "eagle-import:SMALL_TP")
      (libsource (lib "eagle-import") (part "SMALL_TP"))
    )
    (comp (ref "PE3")
      (value "SMALL_TP")
      (footprint "eagle-import:SMALL_TP")
      (libsource (lib "eagle-import") (part "SMALL_TP"))
    )
    (comp (ref "PE4")
      (value "SMALL_TP")
      (footprint "eagle-import:SMALL_TP")
      (libsource (lib "eagle-import") (part "SMALL_TP"))
    )
    (comp (ref "PE5")
      (value "SMALL_TP")
      (footprint "eagle-import:SMALL_TP")
      (libsource (lib "eagle-import") (part "SMALL_TP"))
    )
    (comp (ref "PE6")
      (value "SMALL_TP")
      (footprint "eagle-import:SMALL_TP")
      (libsource (lib "eagle-import") (part "SMALL_TP"))
    )
    (comp (ref "PE7")
      (value "SMALL_TP")
      (footprint "eagle-import:SMALL_TP")
      (libsource (lib "eagle-import") (part "SMALL_TP"))
    )
    (comp (ref "PE8")
      (value "SMALL_TP")
      (footprint "eagle-import:SMALL_TP")
      (libsource (lib "eagle-import") (part "SMALL_TP"))
    )
    (comp (ref "PE9")
      (value "SMALL_TP")
      (footprint "eagle-import:SMALL_TP")
      (libsource (lib "eagle-import") (part "SMALL_TP"))
    )
    (comp (ref "PE10")
      (value "SMALL_TP")
      (footprint "eagle-import:SMALL_TP")
      (libsource (lib "eagle-import") (part "SMALL_TP"))
    )
    (comp (ref "PE11")
      (value "SMALL_TP")
      (footprint "eagle-import:SMALL_TP")
      (libsource (lib "eagle-import") (part "SMALL_TP"))
    )
    (comp (ref "PE12")
      (value "SMALL_TP")
      (footprint "eagle-import:SMALL_TP")
      (libsource (lib "eagle-import") (part "SMALL_TP"))
    )
    (comp (ref "PE13")
      (value "SMALL_TP")
      (footprint "eagle-import:SMALL_TP")
      (libsource (lib "eagle-import") (part "SMALL_TP"))
    )
    (comp (ref "PE14")
      (value "SMALL_TP")
      (footprint "eagle-import:SMALL_TP")
      (libsource (lib "eagle-import") (part "SMALL_TP"))
    )
    (comp (ref "PE15")
      (value "SMALL_TP")
      (footprint "eagle-import:SMALL_TP")
      (libsource (lib "eagle-import") (part "SMALL_TP"))
    )
    (comp (ref "PF0")
      (value "SMALL_TP")
      (footprint "eagle-import:SMALL_TP")
      (libsource (lib "eagle-import") (part "SMALL_TP"))
    )
    (comp (ref "PF1")
      (value "SMALL_TP")
      (footprint "eagle-import:SMALL_TP")
      (libsource (lib "eagle-import") (part "SMALL_TP"))
    )
    (comp (ref "PF2")
      (value "SMALL_TP")
      (footprint "eagle-import:SMALL_TP")
      (libsource (lib "eagle-import") (part "SMALL_TP"))
    )
    (comp (ref "PF3")
      (value "SMALL_TP")
      (footprint "eagle-import:SMALL_TP")
      (libsource (lib "eagle-import") (part "SMALL_TP"))
    )
    (comp (ref "PF4")
      (value "SMALL_TP")
      (footprint "eagle-import:SMALL_TP")
      (libsource (lib "eagle-import") (part "SMALL_TP"))
    )
    (comp (ref "PF5")
      (value "SMALL_TP")
      (footprint "eagle-import:SMALL_TP")
      (libsource (lib "eagle-import") (part "SMALL_TP"))
    )
    (comp (ref "PF6")
      (value "SMALL_TP")
      (footprint "eagle-import:SMALL_TP")
      (libsource (lib "eagle-import") (part "SMALL_TP"))
    )
    (comp (ref "PF7")
      (value "SMALL_TP")
      (footprint "eagle-import:SMALL_TP")
      (libsource (lib "eagle-import") (part "SMALL_TP"))
    )
    (comp (ref "PF8")
      (value "SMALL_TP")
      (footprint "eagle-import:SMALL_TP")
      (libsource (lib "eagle-import") (part "SMALL_TP"))
    )
    (comp (ref "PF9")
      (value "SMALL_TP")
      (footprint "eagle-import:SMALL_TP")
      (libsource (lib "eagle-import") (part "SMALL_TP"))
    )
    (comp (ref "PF10")
      (value "SMALL_TP")
      (footprint "eagle-import:SMALL_TP")
      (libsource (lib "eagle-import") (part "SMALL_TP"))
    )
    (comp (ref "PF11")
      (value "SMALL_TP")
      (footprint "eagle-import:SMALL_TP")
      (libsource (lib "eagle-import") (part "SMALL_TP"))
    )
    (comp (ref "PF12")
      (value "SMALL_TP")
      (footprint "eagle-import:SMALL_TP")
      (libsource (lib "eagle-import") (part "SMALL_TP"))
    )
    (comp (ref "PF13")
      (value "SMALL_TP")
      (footprint "eagle-import:SMALL_TP")
      (libsource (lib "eagle-import") (part "SMALL_TP"))
    )
    (comp (ref "PF14")
      (value "SMALL_TP")
      (footprint "eagle-import:SMALL_TP")
      (libsource (lib "eagle-import") (part "SMALL_TP"))
    )
    (comp (ref "PF15")
      (value "SMALL_TP")
      (footprint "eagle-import:SMALL_TP")
      (libsource (lib "eagle-import") (part "SMALL_TP"))
    )
    (comp (ref "PG0")
      (value "SMALL_TP")
      (footprint "eagle-import:SMALL_TP")
      (libsource (lib "eagle-import") (part "SMALL_TP"))
    )
    (comp (ref "PG1")
      (value "SMALL_TP")
      (footprint "eagle-import:SMALL_TP")
      (libsource (lib "eagle-import") (part "SMALL_TP"))
    )
    (comp (ref "PG2")
      (value "SMALL_TP")
      (footprint "eagle-import:SMALL_TP")
      (libsource (lib "eagle-import") (part "SMALL_TP"))
    )
    (comp (ref "PG3")
      (value "SMALL_TP")
      (footprint "eagle-import:SMALL_TP")
      (libsource (lib "eagle-import") (part "SMALL_TP"))
    )
    (comp (ref "PG4")
      (value "SMALL_TP")
      (footprint "eagle-import:SMALL_TP")
      (libsource (lib "eagle-import") (part "SMALL_TP"))
    )
    (comp (ref "PG5")
      (value "SMALL_TP")
      (footprint "eagle-import:SMALL_TP")
      (libsource (lib "eagle-import") (part "SMALL_TP"))
    )
    (comp (ref "PG6")
      (value "SMALL_TP")
      (footprint "eagle-import:SMALL_TP")
      (libsource (lib "eagle-import") (part "SMALL_TP"))
    )
    (comp (ref "PG8")
      (value "SMALL_TP")
      (footprint "eagle-import:SMALL_TP")
      (libsource (lib "eagle-import") (part "SMALL_TP"))
    )
    (comp (ref "PG9")
      (value "SMALL_TP")
      (footprint "eagle-import:SMALL_TP")
      (libsource (lib "eagle-import") (part "SMALL_TP"))
    )
    (comp (ref "PG10")
      (value "SMALL_TP")
      (footprint "eagle-import:SMALL_TP")
      (libsource (lib "eagle-import") (part "SMALL_TP"))
    )
    (comp (ref "PG12")
      (value "SMALL_TP")
      (footprint "eagle-import:SMALL_TP")
      (libsource (lib "eagle-import") (part "SMALL_TP"))
    )
    (comp (ref "PG14")
      (value "SMALL_TP")
      (footprint "eagle-import:SMALL_TP")
      (libsource (lib "eagle-import") (part "SMALL_TP"))
    )
    (comp (ref "PG15")
      (value "SMALL_TP")
      (footprint "eagle-import:SMALL_TP")
      (libsource (lib "eagle-import") (part "SMALL_TP"))
    )
    (comp (ref "PH1")
      (value "SMALL_TP")
      (footprint "eagle-import:SMALL_TP")
      (libsource (lib "eagle-import") (part "SMALL_TP"))
    )
    (comp (ref "P_FAULT1")
      (value "SMALL_TP")
      (footprint "eagle-import:SMALL_TP")
      (libsource (lib "eagle-import") (part "SMALL_TP"))
    )
    (comp (ref "P_FAULT2")
      (value "SMALL_TP")
      (footprint "eagle-import:SMALL_TP")
      (libsource (lib "eagle-import") (part "SMALL_TP"))
    )
    (comp (ref "P_FAULT3")
      (value "SMALL_TP")
      (footprint "eagle-import:SMALL_TP")
      (libsource (lib "eagle-import") (part "SMALL_TP"))
    )
    (comp (ref "RST_ADC")
      (value "SMALL_TP")
      (footprint "eagle-import:SMALL_TP")
      (libsource (lib "eagle-import") (part "SMALL_TP"))
    )
    (comp (ref "SCL1")
      (value "SMALL_TP")
      (footprint "eagle-import:SMALL_TP")
      (libsource (lib "eagle-import") (part "SMALL_TP"))
    )
    (comp (ref "SCL2")
      (value "SMALL_TP")
      (footprint "eagle-import:SMALL_TP")
      (libsource (lib "eagle-import") (part "SMALL_TP"))
    )
    (comp (ref "SCLK_ADC")
      (value "SMALL_TP")
      (footprint "eagle-import:SMALL_TP")
      (libsource (lib "eagle-import") (part "SMALL_TP"))
    )
    (comp (ref "SDA1")
      (value "SMALL_TP")
      (footprint "eagle-import:SMALL_TP")
      (libsource (lib "eagle-import") (part "SMALL_TP"))
    )
    (comp (ref "SDA2")
      (value "SMALL_TP")
      (footprint "eagle-import:SMALL_TP")
      (libsource (lib "eagle-import") (part "SMALL_TP"))
    )
    (comp (ref "TEMP_MISO")
      (value "SMALL_TP")
      (footprint "eagle-import:SMALL_TP")
      (libsource (lib "eagle-import") (part "SMALL_TP"))
    )
    (comp (ref "TEMP_SCLK")
      (value "SMALL_TP")
      (footprint "eagle-import:SMALL_TP")
      (libsource (lib "eagle-import") (part "SMALL_TP"))
    )
    (comp (ref "U$5")
      (value "THROUGH_HOLE")
      (footprint "eagle-import:1_16TH_BOLT")
      (libsource (lib "eagle-import") (part "THROUGH_HOLE"))
    )
    (comp (ref "U$7")
      (value "THROUGH_HOLE")
      (footprint "eagle-import:1_16TH_BOLT")
      (libsource (lib "eagle-import") (part "THROUGH_HOLE"))
    )
    (comp (ref "U$9")
      (value "THROUGH_HOLE")
      (footprint "eagle-import:1_16TH_BOLT")
      (libsource (lib "eagle-import") (part "THROUGH_HOLE"))
    )
    (comp (ref "U$10")
      (value "THROUGH_HOLE")
      (footprint "eagle-import:1_16TH_BOLT")
      (libsource (lib "eagle-import") (part "THROUGH_HOLE"))
    )
    (comp (ref "U$14")
      (value "THROUGH_HOLE")
      (footprint "eagle-import:1_16TH_BOLT")
      (libsource (lib "eagle-import") (part "THROUGH_HOLE"))
    )
    (comp (ref "U$15")
      (value "THROUGH_HOLE")
      (footprint "eagle-import:1_16TH_BOLT")
      (libsource (lib "eagle-import") (part "THROUGH_HOLE"))
    )
    (comp (ref "UC1")
      (value "NUCLEO_H723ZG")
      (footprint "eagle-import:NUCLEO_H723ZG")
      (libsource (lib "eagle-import") (part "NUCLEO_H723ZG"))
    )
    (comp (ref "J9")
      (value "SSM-109-L-SV")
      (footprint "eagle-import:SAMTEC_SSM-109-L-SV")
      (fields (field (name "MANUFACTURER") "SAMTEC "))
      (libsource (lib "eagle-import") (part "SSM-109-L-SV"))
    )
    (comp (ref "C192")
      (value "GRM31C5C1E474JE01L")
      (footprint "eagle-import:CAPC3216X180N")
      (fields (field (name "MOUSER_PART_NUMBER") "81-GRM31C5C1E474JE1L"))
      (libsource (lib "eagle-import") (part "GRM31C5C1E474JE01L"))
    )
    (comp (ref "C193")
      (value "GRM31C5C1E474JE01L")
      (footprint "eagle-import:CAPC3216X180N")
      (fields (field (name "MOUSER_PART_NUMBER") "81-GRM31C5C1E474JE1L"))
      (libsource (lib "eagle-import") (part "GRM31C5C1E474JE01L"))
    )
    (comp (ref "C194")
      (value "GRM31C5C1E474JE01L")
      (footprint "eagle-import:CAPC3216X180N")
      (fields (field (name "MOUSER_PART_NUMBER") "81-GRM31C5C1E474JE1L"))
      (libsource (lib "eagle-import") (part "GRM31C5C1E474JE01L"))
    )
    (comp (ref "C195")
      (value "GRM31C5C1E474JE01L")
      (footprint "eagle-import:CAPC3216X180N")
      (fields (field (name "MOUSER_PART_NUMBER") "81-GRM31C5C1E474JE1L"))
      (libsource (lib "eagle-import") (part "GRM31C5C1E474JE01L"))
    )
    (comp (ref "IC27")
      (value "NCS21911SN2T1G")
      (footprint "eagle-import:SOT95P275X110-5N")
      (fields (field (name "MOUSER_PART_NUMBER") "863-NCS21911SN2T1G"))
      (libsource (lib "eagle-import") (part "NCS21911SN2T1G"))
    )
    (comp (ref "IC28")
      (value "NCS21911SN2T1G")
      (footprint "eagle-import:SOT95P275X110-5N")
      (fields (field (name "MOUSER_PART_NUMBER") "863-NCS21911SN2T1G"))
      (libsource (lib "eagle-import") (part "NCS21911SN2T1G"))
    )
    (comp (ref "IC29")
      (value "NCS21911SN2T1G")
      (footprint "eagle-import:SOT95P275X110-5N")
      (fields (field (name "MOUSER_PART_NUMBER") "863-NCS21911SN2T1G"))
      (libsource (lib "eagle-import") (part "NCS21911SN2T1G"))
    )
    (comp (ref "IC30")
      (value "NCS21911SN2T1G")
      (footprint "eagle-import:SOT95P275X110-5N")
      (fields (field (name "MOUSER_PART_NUMBER") "863-NCS21911SN2T1G"))
      (libsource (lib "eagle-import") (part "NCS21911SN2T1G"))
    )
    (comp (ref "R471")
      (value "ERJ-2RKF2002X")
      (footprint "eagle-import:ERJ2R_(0402)")
      (fields (field (name "MOUSER_PART_NUMBER") "667-ERJ-2RKF2002X"))
      (libsource (lib "eagle-import") (part "ERJ-2RKF2002X"))
    )
    (comp (ref "R499")
      (value "ERJ-2RKF2002X")
      (footprint "eagle-import:ERJ2R_(0402)")
      (fields (field (name "MOUSER_PART_NUMBER") "667-ERJ-2RKF2002X"))
      (libsource (lib "eagle-import") (part "ERJ-2RKF2002X"))
    )
    (comp (ref "R500")
      (value "ERJ-2RKF2002X")
      (footprint "eagle-import:ERJ2R_(0402)")
      (fields (field (name "MOUSER_PART_NUMBER") "667-ERJ-2RKF2002X"))
      (libsource (lib "eagle-import") (part "ERJ-2RKF2002X"))
    )
    (comp (ref "R501")
      (value "ERJ-2RKF2002X")
      (footprint "eagle-import:ERJ2R_(0402)")
      (fields (field (name "MOUSER_PART_NUMBER") "667-ERJ-2RKF2002X"))
      (libsource (lib "eagle-import") (part "ERJ-2RKF2002X"))
    )
    (comp (ref "R502")
      (value "ERJ-2RKF2002X")
      (footprint "eagle-import:ERJ2R_(0402)")
      (fields (field (name "MOUSER_PART_NUMBER") "667-ERJ-2RKF2002X"))
      (libsource (lib "eagle-import") (part "ERJ-2RKF2002X"))
    )
    (comp (ref "R503")
      (value "ERJ-2RKF2002X")
      (footprint "eagle-import:ERJ2R_(0402)")
      (fields (field (name "MOUSER_PART_NUMBER") "667-ERJ-2RKF2002X"))
      (libsource (lib "eagle-import") (part "ERJ-2RKF2002X"))
    )
    (comp (ref "R504")
      (value "MCS0402MD1002DE000")
      (footprint "eagle-import:RESC1005X37N")
      (fields (field (name "MOUSER_PART_NUMBER") "594-MCS0402MD1002DE0"))
      (libsource (lib "eagle-import") (part "MCS0402MD1002DE000"))
    )
    (comp (ref "R505")
      (value "MCS0402MD1002DE000")
      (footprint "eagle-import:RESC1005X37N")
      (fields (field (name "MOUSER_PART_NUMBER") "594-MCS0402MD1002DE0"))
      (libsource (lib "eagle-import") (part "MCS0402MD1002DE000"))
    )
    (comp (ref "R506")
      (value "ERJ-2RKF2002X")
      (footprint "eagle-import:ERJ2R_(0402)")
      (fields (field (name "MOUSER_PART_NUMBER") "667-ERJ-2RKF2002X"))
      (libsource (lib "eagle-import") (part "ERJ-2RKF2002X"))
    )
    (comp (ref "R507")
      (value "MCS0402MD1002DE000")
      (footprint "eagle-import:RESC1005X37N")
      (fields (field (name "MOUSER_PART_NUMBER") "594-MCS0402MD1002DE0"))
      (libsource (lib "eagle-import") (part "MCS0402MD1002DE000"))
    )
    (comp (ref "R508")
      (value "ERJ-2RKF2002X")
      (footprint "eagle-import:ERJ2R_(0402)")
      (fields (field (name "MOUSER_PART_NUMBER") "667-ERJ-2RKF2002X"))
      (libsource (lib "eagle-import") (part "ERJ-2RKF2002X"))
    )
    (comp (ref "R509")
      (value "MCS0402MD1002DE000")
      (footprint "eagle-import:RESC1005X37N")
      (fields (field (name "MOUSER_PART_NUMBER") "594-MCS0402MD1002DE0"))
      (libsource (lib "eagle-import") (part "MCS0402MD1002DE000"))
    )
    (comp (ref "U$1")
      (value "PTS120601B1K00P100")
      (footprint "eagle-import:RESC3016X70N")
      (libsource (lib "eagle-import") (part "PTS120601B1K00P100"))
    )
    (comp (ref "U$2")
      (value "PTS120601B1K00P100")
      (footprint "eagle-import:RESC3016X70N")
      (libsource (lib "eagle-import") (part "PTS120601B1K00P100"))
    )
    (comp (ref "U$3")
      (value "PTS120601B1K00P100")
      (footprint "eagle-import:RESC3016X70N")
      (libsource (lib "eagle-import") (part "PTS120601B1K00P100"))
    )
    (comp (ref "U$4")
      (value "PTS120601B1K00P100")
      (footprint "eagle-import:RESC3016X70N")
      (libsource (lib "eagle-import") (part "PTS120601B1K00P100"))
    )
    (comp (ref "C169")
      (value "GRM31C5C1E474JE01L")
      (footprint "eagle-import:CAPC3216X180N")
      (fields (field (name "MOUSER_PART_NUMBER") "81-GRM31C5C1E474JE1L"))
      (libsource (lib "eagle-import") (part "GRM31C5C1E474JE01L"))
    )
    (comp (ref "IC31")
      (value "ADIS16500AMLZ")
      (footprint "eagle-import:BGA100C127P10X10_1500X1500X608")
      (fields (field (name "MOUSER_PART_NUMBER") "584-ADIS16500AMLZ"))
      (libsource (lib "eagle-import") (part "ADIS16500AMLZ"))
    )
    (comp (ref "C14")
      (value "CGA4J3X7R1H105K125AB")
      (footprint "eagle-import:CAPC2012X145N")
      (fields (field (name "MOUSER_PART_NUMBER") "810-CGA4J3X7R1H105K "))
      (libsource (lib "eagle-import") (part "CGA4J3X7R1H105K125AB"))
    )
    (comp (ref "C17")
      (value "C3216X7R1E106K160AE")
      (footprint "eagle-import:C3216_COMMERCIAL")
      (fields (field (name "MOUSER_PART_NUMBER") "810-C3216X7R1E106KST"))
      (libsource (lib "eagle-import") (part "C3216X7R1E106K160AE"))
    )
    (comp (ref "C19")
      (value "CGA4J3X7R1H105K125AB")
      (footprint "eagle-import:CAPC2012X145N")
      (fields (field (name "MOUSER_PART_NUMBER") "810-CGA4J3X7R1H105K "))
      (libsource (lib "eagle-import") (part "CGA4J3X7R1H105K125AB"))
    )
    (comp (ref "C20")
      (value "CGA4J3X7R1H105K125AB")
      (footprint "eagle-import:CAPC2012X145N")
      (fields (field (name "MOUSER_PART_NUMBER") "810-CGA4J3X7R1H105K "))
      (libsource (lib "eagle-import") (part "CGA4J3X7R1H105K125AB"))
    )
    (comp (ref "C21")
      (value "CGA4J3X7R1H105K125AB")
      (footprint "eagle-import:CAPC2012X145N")
      (fields (field (name "MOUSER_PART_NUMBER") "810-CGA4J3X7R1H105K "))
      (libsource (lib "eagle-import") (part "CGA4J3X7R1H105K125AB"))
    )
    (comp (ref "C23")
      (value "CGA4J3X7R1H105K125AB")
      (footprint "eagle-import:CAPC2012X145N")
      (fields (field (name "MOUSER_PART_NUMBER") "810-CGA4J3X7R1H105K "))
      (libsource (lib "eagle-import") (part "CGA4J3X7R1H105K125AB"))
    )
    (comp (ref "C24")
      (value "CGA4J3X7R1H105K125AB")
      (footprint "eagle-import:CAPC2012X145N")
      (fields (field (name "MOUSER_PART_NUMBER") "810-CGA4J3X7R1H105K "))
      (libsource (lib "eagle-import") (part "CGA4J3X7R1H105K125AB"))
    )
    (comp (ref "C25")
      (value "C3216X7R1E106K160AE")
      (footprint "eagle-import:C3216_COMMERCIAL")
      (fields (field (name "MOUSER_PART_NUMBER") "810-C3216X7R1E106KST"))
      (libsource (lib "eagle-import") (part "C3216X7R1E106K160AE"))
    )
    (comp (ref "C28")
      (value "CS0402KRX7R8BB104")
      (footprint "eagle-import:CAPC1005X65N")
      (fields (field (name "MOUSER_PART_NUMBER") "603-CS0402KRX78BB104"))
      (libsource (lib "eagle-import") (part "CS0402KRX7R8BB104"))
    )
    (comp (ref "C29")
      (value "CS0402KRX7R8BB104")
      (footprint "eagle-import:CAPC1005X65N")
      (fields (field (name "MOUSER_PART_NUMBER") "603-CS0402KRX78BB104"))
      (libsource (lib "eagle-import") (part "CS0402KRX7R8BB104"))
    )
    (comp (ref "C30")
      (value "CS0402KRX7R8BB104")
      (footprint "eagle-import:CAPC1005X65N")
      (fields (field (name "MOUSER_PART_NUMBER") "603-CS0402KRX78BB104"))
      (libsource (lib "eagle-import") (part "CS0402KRX7R8BB104"))
    )
    (comp (ref "C33")
      (value "GRM31C5C1E474JE01L")
      (footprint "eagle-import:CAPC3216X180N")
      (fields (field (name "MOUSER_PART_NUMBER") "81-GRM31C5C1E474JE1L"))
      (libsource (lib "eagle-import") (part "GRM31C5C1E474JE01L"))
    )
    (comp (ref "C34")
      (value "GRM31C5C1E474JE01L")
      (footprint "eagle-import:CAPC3216X180N")
      (fields (field (name "MOUSER_PART_NUMBER") "81-GRM31C5C1E474JE1L"))
      (libsource (lib "eagle-import") (part "GRM31C5C1E474JE01L"))
    )
    (comp (ref "C35")
      (value "GRM31C5C1E474JE01L")
      (footprint "eagle-import:CAPC3216X180N")
      (fields (field (name "MOUSER_PART_NUMBER") "81-GRM31C5C1E474JE1L"))
      (libsource (lib "eagle-import") (part "GRM31C5C1E474JE01L"))
    )
    (comp (ref "C36")
      (value "GRM31C5C1E474JE01L")
      (footprint "eagle-import:CAPC3216X180N")
      (fields (field (name "MOUSER_PART_NUMBER") "81-GRM31C5C1E474JE1L"))
      (libsource (lib "eagle-import") (part "GRM31C5C1E474JE01L"))
    )
    (comp (ref "C65")
      (value "GRM31C5C1E474JE01L")
      (footprint "eagle-import:CAPC3216X180N")
      (fields (field (name "MOUSER_PART_NUMBER") "81-GRM31C5C1E474JE1L"))
      (libsource (lib "eagle-import") (part "GRM31C5C1E474JE01L"))
    )
    (comp (ref "C70")
      (value "GRM31C5C1E474JE01L")
      (footprint "eagle-import:CAPC3216X180N")
      (fields (field (name "MOUSER_PART_NUMBER") "81-GRM31C5C1E474JE1L"))
      (libsource (lib "eagle-import") (part "GRM31C5C1E474JE01L"))
    )
    (comp (ref "C71")
      (value "GRM31C5C1E474JE01L")
      (footprint "eagle-import:CAPC3216X180N")
      (fields (field (name "MOUSER_PART_NUMBER") "81-GRM31C5C1E474JE1L"))
      (libsource (lib "eagle-import") (part "GRM31C5C1E474JE01L"))
    )
    (comp (ref "C72")
      (value "GRM31C5C1E474JE01L")
      (footprint "eagle-import:CAPC3216X180N")
      (fields (field (name "MOUSER_PART_NUMBER") "81-GRM31C5C1E474JE1L"))
      (libsource (lib "eagle-import") (part "GRM31C5C1E474JE01L"))
    )
    (comp (ref "C73")
      (value "GRM31C5C1E474JE01L")
      (footprint "eagle-import:CAPC3216X180N")
      (fields (field (name "MOUSER_PART_NUMBER") "81-GRM31C5C1E474JE1L"))
      (libsource (lib "eagle-import") (part "GRM31C5C1E474JE01L"))
    )
    (comp (ref "C196")
      (value "CGA4J3X7R1H105K125AB")
      (footprint "eagle-import:CAPC2012X145N")
      (fields (field (name "MOUSER_PART_NUMBER") "810-CGA4J3X7R1H105K "))
      (libsource (lib "eagle-import") (part "CGA4J3X7R1H105K125AB"))
    )
    (comp (ref "C247")
      (value "C0402C103K3RAC7411")
      (footprint "eagle-import:C0402")
      (fields (field (name "MOUSER_PART_NUMBER") "80-C0402C103K3R7411"))
      (libsource (lib "eagle-import") (part "C0402C103K3RAC7411"))
    )
    (comp (ref "C248")
      (value "CS0402KRX7R8BB104")
      (footprint "eagle-import:CAPC1005X65N")
      (fields (field (name "MOUSER_PART_NUMBER") "603-CS0402KRX78BB104"))
      (libsource (lib "eagle-import") (part "CS0402KRX7R8BB104"))
    )
    (comp (ref "C249")
      (value "CS0402KRX7R8BB104")
      (footprint "eagle-import:CAPC1005X65N")
      (fields (field (name "MOUSER_PART_NUMBER") "603-CS0402KRX78BB104"))
      (libsource (lib "eagle-import") (part "CS0402KRX7R8BB104"))
    )
    (comp (ref "C250")
      (value "CS0402KRX7R8BB104")
      (footprint "eagle-import:CAPC1005X65N")
      (fields (field (name "MOUSER_PART_NUMBER") "603-CS0402KRX78BB104"))
      (libsource (lib "eagle-import") (part "CS0402KRX7R8BB104"))
    )
    (comp (ref "C251")
      (value "CS0402KRX7R8BB104")
      (footprint "eagle-import:CAPC1005X65N")
      (fields (field (name "MOUSER_PART_NUMBER") "603-CS0402KRX78BB104"))
      (libsource (lib "eagle-import") (part "CS0402KRX7R8BB104"))
    )
    (comp (ref "C252")
      (value "CS0402KRX7R8BB104")
      (footprint "eagle-import:CAPC1005X65N")
      (fields (field (name "MOUSER_PART_NUMBER") "603-CS0402KRX78BB104"))
      (libsource (lib "eagle-import") (part "CS0402KRX7R8BB104"))
    )
    (comp (ref "C253")
      (value "C0402C103K3RAC7411")
      (footprint "eagle-import:C0402")
      (fields (field (name "MOUSER_PART_NUMBER") "80-C0402C103K3R7411"))
      (libsource (lib "eagle-import") (part "C0402C103K3RAC7411"))
    )
    (comp (ref "C254")
      (value "CS0402KRX7R8BB104")
      (footprint "eagle-import:CAPC1005X65N")
      (fields (field (name "MOUSER_PART_NUMBER") "603-CS0402KRX78BB104"))
      (libsource (lib "eagle-import") (part "CS0402KRX7R8BB104"))
    )
    (comp (ref "C255")
      (value "CS0402KRX7R8BB104")
      (footprint "eagle-import:CAPC1005X65N")
      (fields (field (name "MOUSER_PART_NUMBER") "603-CS0402KRX78BB104"))
      (libsource (lib "eagle-import") (part "CS0402KRX7R8BB104"))
    )
    (comp (ref "C256")
      (value "CS0402KRX7R8BB104")
      (footprint "eagle-import:CAPC1005X65N")
      (fields (field (name "MOUSER_PART_NUMBER") "603-CS0402KRX78BB104"))
      (libsource (lib "eagle-import") (part "CS0402KRX7R8BB104"))
    )
    (comp (ref "C257")
      (value "CS0402KRX7R8BB104")
      (footprint "eagle-import:CAPC1005X65N")
      (fields (field (name "MOUSER_PART_NUMBER") "603-CS0402KRX78BB104"))
      (libsource (lib "eagle-import") (part "CS0402KRX7R8BB104"))
    )
    (comp (ref "C258")
      (value "CS0402KRX7R8BB104")
      (footprint "eagle-import:CAPC1005X65N")
      (fields (field (name "MOUSER_PART_NUMBER") "603-CS0402KRX78BB104"))
      (libsource (lib "eagle-import") (part "CS0402KRX7R8BB104"))
    )
    (comp (ref "C259")
      (value "C0402C103K3RAC7411")
      (footprint "eagle-import:C0402")
      (fields (field (name "MOUSER_PART_NUMBER") "80-C0402C103K3R7411"))
      (libsource (lib "eagle-import") (part "C0402C103K3RAC7411"))
    )
    (comp (ref "C260")
      (value "CS0402KRX7R8BB104")
      (footprint "eagle-import:CAPC1005X65N")
      (fields (field (name "MOUSER_PART_NUMBER") "603-CS0402KRX78BB104"))
      (libsource (lib "eagle-import") (part "CS0402KRX7R8BB104"))
    )
    (comp (ref "C261")
      (value "CS0402KRX7R8BB104")
      (footprint "eagle-import:CAPC1005X65N")
      (fields (field (name "MOUSER_PART_NUMBER") "603-CS0402KRX78BB104"))
      (libsource (lib "eagle-import") (part "CS0402KRX7R8BB104"))
    )
    (comp (ref "C262")
      (value "CS0402KRX7R8BB104")
      (footprint "eagle-import:CAPC1005X65N")
      (fields (field (name "MOUSER_PART_NUMBER") "603-CS0402KRX78BB104"))
      (libsource (lib "eagle-import") (part "CS0402KRX7R8BB104"))
    )
    (comp (ref "C263")
      (value "CS0402KRX7R8BB104")
      (footprint "eagle-import:CAPC1005X65N")
      (fields (field (name "MOUSER_PART_NUMBER") "603-CS0402KRX78BB104"))
      (libsource (lib "eagle-import") (part "CS0402KRX7R8BB104"))
    )
    (comp (ref "C264")
      (value "CS0402KRX7R8BB104")
      (footprint "eagle-import:CAPC1005X65N")
      (fields (field (name "MOUSER_PART_NUMBER") "603-CS0402KRX78BB104"))
      (libsource (lib "eagle-import") (part "CS0402KRX7R8BB104"))
    )
    (comp (ref "C265")
      (value "C0402C103K3RAC7411")
      (footprint "eagle-import:C0402")
      (fields (field (name "MOUSER_PART_NUMBER") "80-C0402C103K3R7411"))
      (libsource (lib "eagle-import") (part "C0402C103K3RAC7411"))
    )
    (comp (ref "C266")
      (value "CS0402KRX7R8BB104")
      (footprint "eagle-import:CAPC1005X65N")
      (fields (field (name "MOUSER_PART_NUMBER") "603-CS0402KRX78BB104"))
      (libsource (lib "eagle-import") (part "CS0402KRX7R8BB104"))
    )
    (comp (ref "C267")
      (value "CS0402KRX7R8BB104")
      (footprint "eagle-import:CAPC1005X65N")
      (fields (field (name "MOUSER_PART_NUMBER") "603-CS0402KRX78BB104"))
      (libsource (lib "eagle-import") (part "CS0402KRX7R8BB104"))
    )
    (comp (ref "C268")
      (value "CS0402KRX7R8BB104")
      (footprint "eagle-import:CAPC1005X65N")
      (fields (field (name "MOUSER_PART_NUMBER") "603-CS0402KRX78BB104"))
      (libsource (lib "eagle-import") (part "CS0402KRX7R8BB104"))
    )
    (comp (ref "C269")
      (value "CS0402KRX7R8BB104")
      (footprint "eagle-import:CAPC1005X65N")
      (fields (field (name "MOUSER_PART_NUMBER") "603-CS0402KRX78BB104"))
      (libsource (lib "eagle-import") (part "CS0402KRX7R8BB104"))
    )
    (comp (ref "C270")
      (value "CS0402KRX7R8BB104")
      (footprint "eagle-import:CAPC1005X65N")
      (fields (field (name "MOUSER_PART_NUMBER") "603-CS0402KRX78BB104"))
      (libsource (lib "eagle-import") (part "CS0402KRX7R8BB104"))
    )
    (comp (ref "C271")
      (value "C0402C103K3RAC7411")
      (footprint "eagle-import:C0402")
      (fields (field (name "MOUSER_PART_NUMBER") "80-C0402C103K3R7411"))
      (libsource (lib "eagle-import") (part "C0402C103K3RAC7411"))
    )
    (comp (ref "C272")
      (value "CS0402KRX7R8BB104")
      (footprint "eagle-import:CAPC1005X65N")
      (fields (field (name "MOUSER_PART_NUMBER") "603-CS0402KRX78BB104"))
      (libsource (lib "eagle-import") (part "CS0402KRX7R8BB104"))
    )
    (comp (ref "C273")
      (value "CS0402KRX7R8BB104")
      (footprint "eagle-import:CAPC1005X65N")
      (fields (field (name "MOUSER_PART_NUMBER") "603-CS0402KRX78BB104"))
      (libsource (lib "eagle-import") (part "CS0402KRX7R8BB104"))
    )
    (comp (ref "C274")
      (value "CS0402KRX7R8BB104")
      (footprint "eagle-import:CAPC1005X65N")
      (fields (field (name "MOUSER_PART_NUMBER") "603-CS0402KRX78BB104"))
      (libsource (lib "eagle-import") (part "CS0402KRX7R8BB104"))
    )
    (comp (ref "C275")
      (value "CS0402KRX7R8BB104")
      (footprint "eagle-import:CAPC1005X65N")
      (fields (field (name "MOUSER_PART_NUMBER") "603-CS0402KRX78BB104"))
      (libsource (lib "eagle-import") (part "CS0402KRX7R8BB104"))
    )
    (comp (ref "C276")
      (value "CS0402KRX7R8BB104")
      (footprint "eagle-import:CAPC1005X65N")
      (fields (field (name "MOUSER_PART_NUMBER") "603-CS0402KRX78BB104"))
      (libsource (lib "eagle-import") (part "CS0402KRX7R8BB104"))
    )
    (comp (ref "IC1")
      (value "NCS21911SN2T1G")
      (footprint "eagle-import:SOT95P275X110-5N")
      (fields (field (name "MOUSER_PART_NUMBER") "863-NCS21911SN2T1G"))
      (libsource (lib "eagle-import") (part "NCS21911SN2T1G"))
    )
    (comp (ref "IC2")
      (value "NCS21911SN2T1G")
      (footprint "eagle-import:SOT95P275X110-5N")
      (fields (field (name "MOUSER_PART_NUMBER") "863-NCS21911SN2T1G"))
      (libsource (lib "eagle-import") (part "NCS21911SN2T1G"))
    )
    (comp (ref "IC3")
      (value "NCS21911SN2T1G")
      (footprint "eagle-import:SOT95P275X110-5N")
      (fields (field (name "MOUSER_PART_NUMBER") "863-NCS21911SN2T1G"))
      (libsource (lib "eagle-import") (part "NCS21911SN2T1G"))
    )
    (comp (ref "IC52")
      (value "ADS8588HIPM")
      (footprint "eagle-import:QFP50P1200X1200X160-64N_NO_3D")
      (libsource (lib "eagle-import") (part "ADS8588HIPM"))
    )
    (comp (ref "IC70")
      (value "NCS21911SN2T1G")
      (footprint "eagle-import:SOT95P275X110-5N")
      (fields (field (name "MOUSER_PART_NUMBER") "863-NCS21911SN2T1G"))
      (libsource (lib "eagle-import") (part "NCS21911SN2T1G"))
    )
    (comp (ref "IC71")
      (value "NCS21911SN2T1G")
      (footprint "eagle-import:SOT95P275X110-5N")
      (fields (field (name "MOUSER_PART_NUMBER") "863-NCS21911SN2T1G"))
      (libsource (lib "eagle-import") (part "NCS21911SN2T1G"))
    )
    (comp (ref "IC72")
      (value "NCS21911SN2T1G")
      (footprint "eagle-import:SOT95P275X110-5N")
      (fields (field (name "MOUSER_PART_NUMBER") "863-NCS21911SN2T1G"))
      (libsource (lib "eagle-import") (part "NCS21911SN2T1G"))
    )
    (comp (ref "IC73")
      (value "NCS21911SN2T1G")
      (footprint "eagle-import:SOT95P275X110-5N")
      (fields (field (name "MOUSER_PART_NUMBER") "863-NCS21911SN2T1G"))
      (libsource (lib "eagle-import") (part "NCS21911SN2T1G"))
    )
    (comp (ref "IC74")
      (value "NCS21911SN2T1G")
      (footprint "eagle-import:SOT95P275X110-5N")
      (fields (field (name "MOUSER_PART_NUMBER") "863-NCS21911SN2T1G"))
      (libsource (lib "eagle-import") (part "NCS21911SN2T1G"))
    )
    (comp (ref "IC75")
      (value "NCS21911SN2T1G")
      (footprint "eagle-import:SOT95P275X110-5N")
      (fields (field (name "MOUSER_PART_NUMBER") "863-NCS21911SN2T1G"))
      (libsource (lib "eagle-import") (part "NCS21911SN2T1G"))
    )
    (comp (ref "IC76")
      (value "NCS21911SN2T1G")
      (footprint "eagle-import:SOT95P275X110-5N")
      (fields (field (name "MOUSER_PART_NUMBER") "863-NCS21911SN2T1G"))
      (libsource (lib "eagle-import") (part "NCS21911SN2T1G"))
    )
    (comp (ref "IC77")
      (value "NCS21911SN2T1G")
      (footprint "eagle-import:SOT95P275X110-5N")
      (fields (field (name "MOUSER_PART_NUMBER") "863-NCS21911SN2T1G"))
      (libsource (lib "eagle-import") (part "NCS21911SN2T1G"))
    )
    (comp (ref "IC78")
      (value "NCS21911SN2T1G")
      (footprint "eagle-import:SOT95P275X110-5N")
      (fields (field (name "MOUSER_PART_NUMBER") "863-NCS21911SN2T1G"))
      (libsource (lib "eagle-import") (part "NCS21911SN2T1G"))
    )
    (comp (ref "IC79")
      (value "NCS21911SN2T1G")
      (footprint "eagle-import:SOT95P275X110-5N")
      (fields (field (name "MOUSER_PART_NUMBER") "863-NCS21911SN2T1G"))
      (libsource (lib "eagle-import") (part "NCS21911SN2T1G"))
    )
    (comp (ref "R59")
      (value "CRCW04021K30FKTD")
      (footprint "eagle-import:RESC1005X40N")
      (fields (field (name "MOUSER_PART_NUMBER") "71-CRCW0402-1.3K"))
      (libsource (lib "eagle-import") (part "CRCW04021K30FKTD"))
    )
    (comp (ref "R60")
      (value "CRCW04021K30FKTD")
      (footprint "eagle-import:RESC1005X40N")
      (fields (field (name "MOUSER_PART_NUMBER") "71-CRCW0402-1.3K"))
      (libsource (lib "eagle-import") (part "CRCW04021K30FKTD"))
    )
    (comp (ref "R61")
      (value "CRCW04021K30FKTD")
      (footprint "eagle-import:RESC1005X40N")
      (fields (field (name "MOUSER_PART_NUMBER") "71-CRCW0402-1.3K"))
      (libsource (lib "eagle-import") (part "CRCW04021K30FKTD"))
    )
    (comp (ref "R62")
      (value "CR0402-FX-9310GLF")
      (footprint "eagle-import:RESC1005X40N")
      (fields (field (name "MOUSER_PART_NUMBER") "652-CR0402FX9310GLF"))
      (libsource (lib "eagle-import") (part "CR0402-FX-9310GLF"))
    )
    (comp (ref "R63")
      (value "CR0402-FX-9310GLF")
      (footprint "eagle-import:RESC1005X40N")
      (fields (field (name "MOUSER_PART_NUMBER") "652-CR0402FX9310GLF"))
      (libsource (lib "eagle-import") (part "CR0402-FX-9310GLF"))
    )
    (comp (ref "R64")
      (value "CR0402-FX-9310GLF")
      (footprint "eagle-import:RESC1005X40N")
      (fields (field (name "MOUSER_PART_NUMBER") "652-CR0402FX9310GLF"))
      (libsource (lib "eagle-import") (part "CR0402-FX-9310GLF"))
    )
    (comp (ref "R109")
      (value "RC0402FR-075K23L")
      (footprint "eagle-import:RESC1005X40N")
      (fields (field (name "MOUSER_PART_NUMBER") "603-RC0402FR-075K23L"))
      (libsource (lib "eagle-import") (part "RC0402FR-075K23L"))
    )
    (comp (ref "R110")
      (value "RC0402FR-0793K1L")
      (footprint "eagle-import:RESC1005X40N")
      (fields (field (name "MOUSER_PART_NUMBER") "603-RC0402FR-0793K1L"))
      (libsource (lib "eagle-import") (part "RC0402FR-0793K1L"))
    )
    (comp (ref "R111")
      (value "CRCW04021K30FKTD")
      (footprint "eagle-import:RESC1005X40N")
      (fields (field (name "MOUSER_PART_NUMBER") "71-CRCW0402-1.3K"))
      (libsource (lib "eagle-import") (part "CRCW04021K30FKTD"))
    )
    (comp (ref "R112")
      (value "CRCW04021K30FKTD")
      (footprint "eagle-import:RESC1005X40N")
      (fields (field (name "MOUSER_PART_NUMBER") "71-CRCW0402-1.3K"))
      (libsource (lib "eagle-import") (part "CRCW04021K30FKTD"))
    )
    (comp (ref "R113")
      (value "RC0402FR-075K23L")
      (footprint "eagle-import:RESC1005X40N")
      (fields (field (name "MOUSER_PART_NUMBER") "603-RC0402FR-075K23L"))
      (libsource (lib "eagle-import") (part "RC0402FR-075K23L"))
    )
    (comp (ref "R114")
      (value "RC0402FR-0793K1L")
      (footprint "eagle-import:RESC1005X40N")
      (fields (field (name "MOUSER_PART_NUMBER") "603-RC0402FR-0793K1L"))
      (libsource (lib "eagle-import") (part "RC0402FR-0793K1L"))
    )
    (comp (ref "R115")
      (value "CRCW04021K30FKTD")
      (footprint "eagle-import:RESC1005X40N")
      (fields (field (name "MOUSER_PART_NUMBER") "71-CRCW0402-1.3K"))
      (libsource (lib "eagle-import") (part "CRCW04021K30FKTD"))
    )
    (comp (ref "R116")
      (value "CRCW04021K30FKTD")
      (footprint "eagle-import:RESC1005X40N")
      (fields (field (name "MOUSER_PART_NUMBER") "71-CRCW0402-1.3K"))
      (libsource (lib "eagle-import") (part "CRCW04021K30FKTD"))
    )
    (comp (ref "R159")
      (value "RC0402FR-075K23L")
      (footprint "eagle-import:RESC1005X40N")
      (fields (field (name "MOUSER_PART_NUMBER") "603-RC0402FR-075K23L"))
      (libsource (lib "eagle-import") (part "RC0402FR-075K23L"))
    )
    (comp (ref "R160")
      (value "RC0402FR-0793K1L")
      (footprint "eagle-import:RESC1005X40N")
      (fields (field (name "MOUSER_PART_NUMBER") "603-RC0402FR-0793K1L"))
      (libsource (lib "eagle-import") (part "RC0402FR-0793K1L"))
    )
    (comp (ref "R161")
      (value "CRCW04021K30FKTD")
      (footprint "eagle-import:RESC1005X40N")
      (fields (field (name "MOUSER_PART_NUMBER") "71-CRCW0402-1.3K"))
      (libsource (lib "eagle-import") (part "CRCW04021K30FKTD"))
    )
    (comp (ref "R162")
      (value "CRCW04021K30FKTD")
      (footprint "eagle-import:RESC1005X40N")
      (fields (field (name "MOUSER_PART_NUMBER") "71-CRCW0402-1.3K"))
      (libsource (lib "eagle-import") (part "CRCW04021K30FKTD"))
    )
    (comp (ref "R163")
      (value "RC0402FR-075K23L")
      (footprint "eagle-import:RESC1005X40N")
      (fields (field (name "MOUSER_PART_NUMBER") "603-RC0402FR-075K23L"))
      (libsource (lib "eagle-import") (part "RC0402FR-075K23L"))
    )
    (comp (ref "R201")
      (value "RC0402FR-0793K1L")
      (footprint "eagle-import:RESC1005X40N")
      (fields (field (name "MOUSER_PART_NUMBER") "603-RC0402FR-0793K1L"))
      (libsource (lib "eagle-import") (part "RC0402FR-0793K1L"))
    )
    (comp (ref "R203")
      (value "CRCW04021K30FKTD")
      (footprint "eagle-import:RESC1005X40N")
      (fields (field (name "MOUSER_PART_NUMBER") "71-CRCW0402-1.3K"))
      (libsource (lib "eagle-import") (part "CRCW04021K30FKTD"))
    )
    (comp (ref "R205")
      (value "CRCW04021K30FKTD")
      (footprint "eagle-import:RESC1005X40N")
      (fields (field (name "MOUSER_PART_NUMBER") "71-CRCW0402-1.3K"))
      (libsource (lib "eagle-import") (part "CRCW04021K30FKTD"))
    )
    (comp (ref "R207")
      (value "RC0402FR-075K23L")
      (footprint "eagle-import:RESC1005X40N")
      (fields (field (name "MOUSER_PART_NUMBER") "603-RC0402FR-075K23L"))
      (libsource (lib "eagle-import") (part "RC0402FR-075K23L"))
    )
    (comp (ref "R209")
      (value "RC0402FR-0793K1L")
      (footprint "eagle-import:RESC1005X40N")
      (fields (field (name "MOUSER_PART_NUMBER") "603-RC0402FR-0793K1L"))
      (libsource (lib "eagle-import") (part "RC0402FR-0793K1L"))
    )
    (comp (ref "R211")
      (value "CRCW04021K30FKTD")
      (footprint "eagle-import:RESC1005X40N")
      (fields (field (name "MOUSER_PART_NUMBER") "71-CRCW0402-1.3K"))
      (libsource (lib "eagle-import") (part "CRCW04021K30FKTD"))
    )
    (comp (ref "R221")
      (value "CRCW04021K30FKTD")
      (footprint "eagle-import:RESC1005X40N")
      (fields (field (name "MOUSER_PART_NUMBER") "71-CRCW0402-1.3K"))
      (libsource (lib "eagle-import") (part "CRCW04021K30FKTD"))
    )
    (comp (ref "C37")
      (value "GRM1555C1H822JE01D")
      (footprint "eagle-import:0402CAP")
      (libsource (lib "eagle-import") (part "GRM1555C1H822JE01D"))
    )
    (comp (ref "C39")
      (value "CS0402KRX7R8BB104")
      (footprint "eagle-import:CAPC1005X65N")
      (fields (field (name "MOUSER_PART_NUMBER") "603-CS0402KRX78BB104"))
      (libsource (lib "eagle-import") (part "CS0402KRX7R8BB104"))
    )
    (comp (ref "C41")
      (value "GRM31C5C1E474JE01L")
      (footprint "eagle-import:CAPC3216X180N")
      (fields (field (name "MOUSER_PART_NUMBER") "81-GRM31C5C1E474JE1L"))
      (libsource (lib "eagle-import") (part "GRM31C5C1E474JE01L"))
    )
    (comp (ref "C42")
      (value "GRM1555C1H822JE01D")
      (footprint "eagle-import:0402CAP")
      (libsource (lib "eagle-import") (part "GRM1555C1H822JE01D"))
    )
    (comp (ref "C43")
      (value "GRM1555C1H822JE01D")
      (footprint "eagle-import:0402CAP")
      (libsource (lib "eagle-import") (part "GRM1555C1H822JE01D"))
    )
    (comp (ref "C44")
      (value "GRM1555C1H822JE01D")
      (footprint "eagle-import:0402CAP")
      (libsource (lib "eagle-import") (part "GRM1555C1H822JE01D"))
    )
    (comp (ref "C45")
      (value "CS0402KRX7R8BB104")
      (footprint "eagle-import:CAPC1005X65N")
      (fields (field (name "MOUSER_PART_NUMBER") "603-CS0402KRX78BB104"))
      (libsource (lib "eagle-import") (part "CS0402KRX7R8BB104"))
    )
    (comp (ref "C46")
      (value "GRM31C5C1E474JE01L")
      (footprint "eagle-import:CAPC3216X180N")
      (fields (field (name "MOUSER_PART_NUMBER") "81-GRM31C5C1E474JE1L"))
      (libsource (lib "eagle-import") (part "GRM31C5C1E474JE01L"))
    )
    (comp (ref "C95")
      (value "GRM1555C1H822JE01D")
      (footprint "eagle-import:0402CAP")
      (libsource (lib "eagle-import") (part "GRM1555C1H822JE01D"))
    )
    (comp (ref "C97")
      (value "GRM1555C1H822JE01D")
      (footprint "eagle-import:0402CAP")
      (libsource (lib "eagle-import") (part "GRM1555C1H822JE01D"))
    )
    (comp (ref "C99")
      (value "GRM1555C1H822JE01D")
      (footprint "eagle-import:0402CAP")
      (libsource (lib "eagle-import") (part "GRM1555C1H822JE01D"))
    )
    (comp (ref "C101")
      (value "CS0402KRX7R8BB104")
      (footprint "eagle-import:CAPC1005X65N")
      (fields (field (name "MOUSER_PART_NUMBER") "603-CS0402KRX78BB104"))
      (libsource (lib "eagle-import") (part "CS0402KRX7R8BB104"))
    )
    (comp (ref "C107")
      (value "GRM31C5C1E474JE01L")
      (footprint "eagle-import:CAPC3216X180N")
      (fields (field (name "MOUSER_PART_NUMBER") "81-GRM31C5C1E474JE1L"))
      (libsource (lib "eagle-import") (part "GRM31C5C1E474JE01L"))
    )
    (comp (ref "C112")
      (value "GRM1555C1H822JE01D")
      (footprint "eagle-import:0402CAP")
      (libsource (lib "eagle-import") (part "GRM1555C1H822JE01D"))
    )
    (comp (ref "C113")
      (value "GRM1555C1H822JE01D")
      (footprint "eagle-import:0402CAP")
      (libsource (lib "eagle-import") (part "GRM1555C1H822JE01D"))
    )
    (comp (ref "C114")
      (value "GRM1555C1H822JE01D")
      (footprint "eagle-import:0402CAP")
      (libsource (lib "eagle-import") (part "GRM1555C1H822JE01D"))
    )
    (comp (ref "C115")
      (value "CS0402KRX7R8BB104")
      (footprint "eagle-import:CAPC1005X65N")
      (fields (field (name "MOUSER_PART_NUMBER") "603-CS0402KRX78BB104"))
      (libsource (lib "eagle-import") (part "CS0402KRX7R8BB104"))
    )
    (comp (ref "C116")
      (value "GRM31C5C1E474JE01L")
      (footprint "eagle-import:CAPC3216X180N")
      (fields (field (name "MOUSER_PART_NUMBER") "81-GRM31C5C1E474JE1L"))
      (libsource (lib "eagle-import") (part "GRM31C5C1E474JE01L"))
    )
    (comp (ref "C117")
      (value "GRM1555C1H822JE01D")
      (footprint "eagle-import:0402CAP")
      (libsource (lib "eagle-import") (part "GRM1555C1H822JE01D"))
    )
    (comp (ref "C118")
      (value "GRM1555C1H822JE01D")
      (footprint "eagle-import:0402CAP")
      (libsource (lib "eagle-import") (part "GRM1555C1H822JE01D"))
    )
    (comp (ref "C119")
      (value "GRM1555C1H822JE01D")
      (footprint "eagle-import:0402CAP")
      (libsource (lib "eagle-import") (part "GRM1555C1H822JE01D"))
    )
    (comp (ref "C120")
      (value "CS0402KRX7R8BB104")
      (footprint "eagle-import:CAPC1005X65N")
      (fields (field (name "MOUSER_PART_NUMBER") "603-CS0402KRX78BB104"))
      (libsource (lib "eagle-import") (part "CS0402KRX7R8BB104"))
    )
    (comp (ref "C121")
      (value "GRM31C5C1E474JE01L")
      (footprint "eagle-import:CAPC3216X180N")
      (fields (field (name "MOUSER_PART_NUMBER") "81-GRM31C5C1E474JE1L"))
      (libsource (lib "eagle-import") (part "GRM31C5C1E474JE01L"))
    )
    (comp (ref "C122")
      (value "GRM1555C1H822JE01D")
      (footprint "eagle-import:0402CAP")
      (libsource (lib "eagle-import") (part "GRM1555C1H822JE01D"))
    )
    (comp (ref "C123")
      (value "GRM1555C1H822JE01D")
      (footprint "eagle-import:0402CAP")
      (libsource (lib "eagle-import") (part "GRM1555C1H822JE01D"))
    )
    (comp (ref "C124")
      (value "GRM1555C1H822JE01D")
      (footprint "eagle-import:0402CAP")
      (libsource (lib "eagle-import") (part "GRM1555C1H822JE01D"))
    )
    (comp (ref "C125")
      (value "CS0402KRX7R8BB104")
      (footprint "eagle-import:CAPC1005X65N")
      (fields (field (name "MOUSER_PART_NUMBER") "603-CS0402KRX78BB104"))
      (libsource (lib "eagle-import") (part "CS0402KRX7R8BB104"))
    )
    (comp (ref "C126")
      (value "GRM31C5C1E474JE01L")
      (footprint "eagle-import:CAPC3216X180N")
      (fields (field (name "MOUSER_PART_NUMBER") "81-GRM31C5C1E474JE1L"))
      (libsource (lib "eagle-import") (part "GRM31C5C1E474JE01L"))
    )
    (comp (ref "C127")
      (value "GRM1555C1H822JE01D")
      (footprint "eagle-import:0402CAP")
      (libsource (lib "eagle-import") (part "GRM1555C1H822JE01D"))
    )
    (comp (ref "C128")
      (value "GRM1555C1H822JE01D")
      (footprint "eagle-import:0402CAP")
      (libsource (lib "eagle-import") (part "GRM1555C1H822JE01D"))
    )
    (comp (ref "C129")
      (value "GRM1555C1H822JE01D")
      (footprint "eagle-import:0402CAP")
      (libsource (lib "eagle-import") (part "GRM1555C1H822JE01D"))
    )
    (comp (ref "C130")
      (value "CS0402KRX7R8BB104")
      (footprint "eagle-import:CAPC1005X65N")
      (fields (field (name "MOUSER_PART_NUMBER") "603-CS0402KRX78BB104"))
      (libsource (lib "eagle-import") (part "CS0402KRX7R8BB104"))
    )
    (comp (ref "C131")
      (value "GRM31C5C1E474JE01L")
      (footprint "eagle-import:CAPC3216X180N")
      (fields (field (name "MOUSER_PART_NUMBER") "81-GRM31C5C1E474JE1L"))
      (libsource (lib "eagle-import") (part "GRM31C5C1E474JE01L"))
    )
    (comp (ref "C132")
      (value "GRM1555C1H822JE01D")
      (footprint "eagle-import:0402CAP")
      (libsource (lib "eagle-import") (part "GRM1555C1H822JE01D"))
    )
    (comp (ref "C133")
      (value "GRM1555C1H822JE01D")
      (footprint "eagle-import:0402CAP")
      (libsource (lib "eagle-import") (part "GRM1555C1H822JE01D"))
    )
    (comp (ref "C134")
      (value "GRM1555C1H822JE01D")
      (footprint "eagle-import:0402CAP")
      (libsource (lib "eagle-import") (part "GRM1555C1H822JE01D"))
    )
    (comp (ref "C135")
      (value "CS0402KRX7R8BB104")
      (footprint "eagle-import:CAPC1005X65N")
      (fields (field (name "MOUSER_PART_NUMBER") "603-CS0402KRX78BB104"))
      (libsource (lib "eagle-import") (part "CS0402KRX7R8BB104"))
    )
    (comp (ref "C136")
      (value "GRM31C5C1E474JE01L")
      (footprint "eagle-import:CAPC3216X180N")
      (fields (field (name "MOUSER_PART_NUMBER") "81-GRM31C5C1E474JE1L"))
      (libsource (lib "eagle-import") (part "GRM31C5C1E474JE01L"))
    )
    (comp (ref "C137")
      (value "GRM1555C1H822JE01D")
      (footprint "eagle-import:0402CAP")
      (libsource (lib "eagle-import") (part "GRM1555C1H822JE01D"))
    )
    (comp (ref "C138")
      (value "GRM1555C1H822JE01D")
      (footprint "eagle-import:0402CAP")
      (libsource (lib "eagle-import") (part "GRM1555C1H822JE01D"))
    )
    (comp (ref "C139")
      (value "GRM1555C1H822JE01D")
      (footprint "eagle-import:0402CAP")
      (libsource (lib "eagle-import") (part "GRM1555C1H822JE01D"))
    )
    (comp (ref "C140")
      (value "CS0402KRX7R8BB104")
      (footprint "eagle-import:CAPC1005X65N")
      (fields (field (name "MOUSER_PART_NUMBER") "603-CS0402KRX78BB104"))
      (libsource (lib "eagle-import") (part "CS0402KRX7R8BB104"))
    )
    (comp (ref "C141")
      (value "GRM31C5C1E474JE01L")
      (footprint "eagle-import:CAPC3216X180N")
      (fields (field (name "MOUSER_PART_NUMBER") "81-GRM31C5C1E474JE1L"))
      (libsource (lib "eagle-import") (part "GRM31C5C1E474JE01L"))
    )
    (comp (ref "C142")
      (value "GRM1555C1H822JE01D")
      (footprint "eagle-import:0402CAP")
      (libsource (lib "eagle-import") (part "GRM1555C1H822JE01D"))
    )
    (comp (ref "C143")
      (value "GRM1555C1H822JE01D")
      (footprint "eagle-import:0402CAP")
      (libsource (lib "eagle-import") (part "GRM1555C1H822JE01D"))
    )
    (comp (ref "C144")
      (value "GRM1555C1H822JE01D")
      (footprint "eagle-import:0402CAP")
      (libsource (lib "eagle-import") (part "GRM1555C1H822JE01D"))
    )
    (comp (ref "C145")
      (value "CS0402KRX7R8BB104")
      (footprint "eagle-import:CAPC1005X65N")
      (fields (field (name "MOUSER_PART_NUMBER") "603-CS0402KRX78BB104"))
      (libsource (lib "eagle-import") (part "CS0402KRX7R8BB104"))
    )
    (comp (ref "C146")
      (value "GRM31C5C1E474JE01L")
      (footprint "eagle-import:CAPC3216X180N")
      (fields (field (name "MOUSER_PART_NUMBER") "81-GRM31C5C1E474JE1L"))
      (libsource (lib "eagle-import") (part "GRM31C5C1E474JE01L"))
    )
    (comp (ref "C147")
      (value "GRM1555C1H822JE01D")
      (footprint "eagle-import:0402CAP")
      (libsource (lib "eagle-import") (part "GRM1555C1H822JE01D"))
    )
    (comp (ref "C148")
      (value "GRM1555C1H822JE01D")
      (footprint "eagle-import:0402CAP")
      (libsource (lib "eagle-import") (part "GRM1555C1H822JE01D"))
    )
    (comp (ref "C149")
      (value "GRM1555C1H822JE01D")
      (footprint "eagle-import:0402CAP")
      (libsource (lib "eagle-import") (part "GRM1555C1H822JE01D"))
    )
    (comp (ref "C150")
      (value "CS0402KRX7R8BB104")
      (footprint "eagle-import:CAPC1005X65N")
      (fields (field (name "MOUSER_PART_NUMBER") "603-CS0402KRX78BB104"))
      (libsource (lib "eagle-import") (part "CS0402KRX7R8BB104"))
    )
    (comp (ref "C151")
      (value "GRM31C5C1E474JE01L")
      (footprint "eagle-import:CAPC3216X180N")
      (fields (field (name "MOUSER_PART_NUMBER") "81-GRM31C5C1E474JE1L"))
      (libsource (lib "eagle-import") (part "GRM31C5C1E474JE01L"))
    )
    (comp (ref "C152")
      (value "GRM1555C1H822JE01D")
      (footprint "eagle-import:0402CAP")
      (libsource (lib "eagle-import") (part "GRM1555C1H822JE01D"))
    )
    (comp (ref "C153")
      (value "GRM1555C1H822JE01D")
      (footprint "eagle-import:0402CAP")
      (libsource (lib "eagle-import") (part "GRM1555C1H822JE01D"))
    )
    (comp (ref "C154")
      (value "GRM1555C1H822JE01D")
      (footprint "eagle-import:0402CAP")
      (libsource (lib "eagle-import") (part "GRM1555C1H822JE01D"))
    )
    (comp (ref "C155")
      (value "CS0402KRX7R8BB104")
      (footprint "eagle-import:CAPC1005X65N")
      (fields (field (name "MOUSER_PART_NUMBER") "603-CS0402KRX78BB104"))
      (libsource (lib "eagle-import") (part "CS0402KRX7R8BB104"))
    )
    (comp (ref "C156")
      (value "GRM31C5C1E474JE01L")
      (footprint "eagle-import:CAPC3216X180N")
      (fields (field (name "MOUSER_PART_NUMBER") "81-GRM31C5C1E474JE1L"))
      (libsource (lib "eagle-import") (part "GRM31C5C1E474JE01L"))
    )
    (comp (ref "C157")
      (value "GRM1555C1H822JE01D")
      (footprint "eagle-import:0402CAP")
      (libsource (lib "eagle-import") (part "GRM1555C1H822JE01D"))
    )
    (comp (ref "C158")
      (value "GRM1555C1H822JE01D")
      (footprint "eagle-import:0402CAP")
      (libsource (lib "eagle-import") (part "GRM1555C1H822JE01D"))
    )
    (comp (ref "C159")
      (value "GRM1555C1H822JE01D")
      (footprint "eagle-import:0402CAP")
      (libsource (lib "eagle-import") (part "GRM1555C1H822JE01D"))
    )
    (comp (ref "C160")
      (value "CS0402KRX7R8BB104")
      (footprint "eagle-import:CAPC1005X65N")
      (fields (field (name "MOUSER_PART_NUMBER") "603-CS0402KRX78BB104"))
      (libsource (lib "eagle-import") (part "CS0402KRX7R8BB104"))
    )
    (comp (ref "C161")
      (value "GRM31C5C1E474JE01L")
      (footprint "eagle-import:CAPC3216X180N")
      (fields (field (name "MOUSER_PART_NUMBER") "81-GRM31C5C1E474JE1L"))
      (libsource (lib "eagle-import") (part "GRM31C5C1E474JE01L"))
    )
    (comp (ref "C162")
      (value "GRM1555C1H822JE01D")
      (footprint "eagle-import:0402CAP")
      (libsource (lib "eagle-import") (part "GRM1555C1H822JE01D"))
    )
    (comp (ref "C163")
      (value "GRM1555C1H822JE01D")
      (footprint "eagle-import:0402CAP")
      (libsource (lib "eagle-import") (part "GRM1555C1H822JE01D"))
    )
    (comp (ref "C164")
      (value "GRM1555C1H822JE01D")
      (footprint "eagle-import:0402CAP")
      (libsource (lib "eagle-import") (part "GRM1555C1H822JE01D"))
    )
    (comp (ref "C165")
      (value "CS0402KRX7R8BB104")
      (footprint "eagle-import:CAPC1005X65N")
      (fields (field (name "MOUSER_PART_NUMBER") "603-CS0402KRX78BB104"))
      (libsource (lib "eagle-import") (part "CS0402KRX7R8BB104"))
    )
    (comp (ref "C166")
      (value "GRM31C5C1E474JE01L")
      (footprint "eagle-import:CAPC3216X180N")
      (fields (field (name "MOUSER_PART_NUMBER") "81-GRM31C5C1E474JE1L"))
      (libsource (lib "eagle-import") (part "GRM31C5C1E474JE01L"))
    )
    (comp (ref "C167")
      (value "GRM1555C1H822JE01D")
      (footprint "eagle-import:0402CAP")
      (libsource (lib "eagle-import") (part "GRM1555C1H822JE01D"))
    )
    (comp (ref "C168")
      (value "GRM1555C1H822JE01D")
      (footprint "eagle-import:0402CAP")
      (libsource (lib "eagle-import") (part "GRM1555C1H822JE01D"))
    )
    (comp (ref "D1")
      (value "PTVS12VS1UR,115")
      (footprint "eagle-import:SOD123W")
      (fields (field (name "MOUSER_PART_NUMBER") "771-PTVS12VS1UR115"))
      (libsource (lib "eagle-import") (part "PTVS12VS1UR,115"))
    )
    (comp (ref "D2")
      (value "PTVS12VS1UR,115")
      (footprint "eagle-import:SOD123W")
      (fields (field (name "MOUSER_PART_NUMBER") "771-PTVS12VS1UR115"))
      (libsource (lib "eagle-import") (part "PTVS12VS1UR,115"))
    )
    (comp (ref "D3")
      (value "PTVS12VS1UR,115")
      (footprint "eagle-import:SOD123W")
      (fields (field (name "MOUSER_PART_NUMBER") "771-PTVS12VS1UR115"))
      (libsource (lib "eagle-import") (part "PTVS12VS1UR,115"))
    )
    (comp (ref "D4")
      (value "PTVS12VS1UR,115")
      (footprint "eagle-import:SOD123W")
      (fields (field (name "MOUSER_PART_NUMBER") "771-PTVS12VS1UR115"))
      (libsource (lib "eagle-import") (part "PTVS12VS1UR,115"))
    )
    (comp (ref "D5")
      (value "PTVS12VS1UR,115")
      (footprint "eagle-import:SOD123W")
      (fields (field (name "MOUSER_PART_NUMBER") "771-PTVS12VS1UR115"))
      (libsource (lib "eagle-import") (part "PTVS12VS1UR,115"))
    )
    (comp (ref "D6")
      (value "PTVS12VS1UR,115")
      (footprint "eagle-import:SOD123W")
      (fields (field (name "MOUSER_PART_NUMBER") "771-PTVS12VS1UR115"))
      (libsource (lib "eagle-import") (part "PTVS12VS1UR,115"))
    )
    (comp (ref "D7")
      (value "PTVS12VS1UR,115")
      (footprint "eagle-import:SOD123W")
      (fields (field (name "MOUSER_PART_NUMBER") "771-PTVS12VS1UR115"))
      (libsource (lib "eagle-import") (part "PTVS12VS1UR,115"))
    )
    (comp (ref "D8")
      (value "PTVS12VS1UR,115")
      (footprint "eagle-import:SOD123W")
      (fields (field (name "MOUSER_PART_NUMBER") "771-PTVS12VS1UR115"))
      (libsource (lib "eagle-import") (part "PTVS12VS1UR,115"))
    )
    (comp (ref "D9")
      (value "PTVS12VS1UR,115")
      (footprint "eagle-import:SOD123W")
      (fields (field (name "MOUSER_PART_NUMBER") "771-PTVS12VS1UR115"))
      (libsource (lib "eagle-import") (part "PTVS12VS1UR,115"))
    )
    (comp (ref "D10")
      (value "PTVS12VS1UR,115")
      (footprint "eagle-import:SOD123W")
      (fields (field (name "MOUSER_PART_NUMBER") "771-PTVS12VS1UR115"))
      (libsource (lib "eagle-import") (part "PTVS12VS1UR,115"))
    )
    (comp (ref "D11")
      (value "PTVS12VS1UR,115")
      (footprint "eagle-import:SOD123W")
      (fields (field (name "MOUSER_PART_NUMBER") "771-PTVS12VS1UR115"))
      (libsource (lib "eagle-import") (part "PTVS12VS1UR,115"))
    )
    (comp (ref "D12")
      (value "PTVS12VS1UR,115")
      (footprint "eagle-import:SOD123W")
      (fields (field (name "MOUSER_PART_NUMBER") "771-PTVS12VS1UR115"))
      (libsource (lib "eagle-import") (part "PTVS12VS1UR,115"))
    )
    (comp (ref "D13")
      (value "PTVS12VS1UR,115")
      (footprint "eagle-import:SOD123W")
      (fields (field (name "MOUSER_PART_NUMBER") "771-PTVS12VS1UR115"))
      (libsource (lib "eagle-import") (part "PTVS12VS1UR,115"))
    )
    (comp (ref "D14")
      (value "PTVS12VS1UR,115")
      (footprint "eagle-import:SOD123W")
      (fields (field (name "MOUSER_PART_NUMBER") "771-PTVS12VS1UR115"))
      (libsource (lib "eagle-import") (part "PTVS12VS1UR,115"))
    )
    (comp (ref "D15")
      (value "PTVS12VS1UR,115")
      (footprint "eagle-import:SOD123W")
      (fields (field (name "MOUSER_PART_NUMBER") "771-PTVS12VS1UR115"))
      (libsource (lib "eagle-import") (part "PTVS12VS1UR,115"))
    )
    (comp (ref "D16")
      (value "PTVS12VS1UR,115")
      (footprint "eagle-import:SOD123W")
      (fields (field (name "MOUSER_PART_NUMBER") "771-PTVS12VS1UR115"))
      (libsource (lib "eagle-import") (part "PTVS12VS1UR,115"))
    )
    (comp (ref "D17")
      (value "PTVS12VS1UR,115")
      (footprint "eagle-import:SOD123W")
      (fields (field (name "MOUSER_PART_NUMBER") "771-PTVS12VS1UR115"))
      (libsource (lib "eagle-import") (part "PTVS12VS1UR,115"))
    )
    (comp (ref "D18")
      (value "PTVS12VS1UR,115")
      (footprint "eagle-import:SOD123W")
      (fields (field (name "MOUSER_PART_NUMBER") "771-PTVS12VS1UR115"))
      (libsource (lib "eagle-import") (part "PTVS12VS1UR,115"))
    )
    (comp (ref "D19")
      (value "PTVS12VS1UR,115")
      (footprint "eagle-import:SOD123W")
      (fields (field (name "MOUSER_PART_NUMBER") "771-PTVS12VS1UR115"))
      (libsource (lib "eagle-import") (part "PTVS12VS1UR,115"))
    )
    (comp (ref "D20")
      (value "PTVS12VS1UR,115")
      (footprint "eagle-import:SOD123W")
      (fields (field (name "MOUSER_PART_NUMBER") "771-PTVS12VS1UR115"))
      (libsource (lib "eagle-import") (part "PTVS12VS1UR,115"))
    )
    (comp (ref "D21")
      (value "PTVS12VS1UR,115")
      (footprint "eagle-import:SOD123W")
      (fields (field (name "MOUSER_PART_NUMBER") "771-PTVS12VS1UR115"))
      (libsource (lib "eagle-import") (part "PTVS12VS1UR,115"))
    )
    (comp (ref "D22")
      (value "PTVS12VS1UR,115")
      (footprint "eagle-import:SOD123W")
      (fields (field (name "MOUSER_PART_NUMBER") "771-PTVS12VS1UR115"))
      (libsource (lib "eagle-import") (part "PTVS12VS1UR,115"))
    )
    (comp (ref "D23")
      (value "PTVS12VS1UR,115")
      (footprint "eagle-import:SOD123W")
      (fields (field (name "MOUSER_PART_NUMBER") "771-PTVS12VS1UR115"))
      (libsource (lib "eagle-import") (part "PTVS12VS1UR,115"))
    )
    (comp (ref "D24")
      (value "PTVS12VS1UR,115")
      (footprint "eagle-import:SOD123W")
      (fields (field (name "MOUSER_PART_NUMBER") "771-PTVS12VS1UR115"))
      (libsource (lib "eagle-import") (part "PTVS12VS1UR,115"))
    )
    (comp (ref "D25")
      (value "PTVS12VS1UR,115")
      (footprint "eagle-import:SOD123W")
      (fields (field (name "MOUSER_PART_NUMBER") "771-PTVS12VS1UR115"))
      (libsource (lib "eagle-import") (part "PTVS12VS1UR,115"))
    )
    (comp (ref "D26")
      (value "PTVS12VS1UR,115")
      (footprint "eagle-import:SOD123W")
      (fields (field (name "MOUSER_PART_NUMBER") "771-PTVS12VS1UR115"))
      (libsource (lib "eagle-import") (part "PTVS12VS1UR,115"))
    )
    (comp (ref "D27")
      (value "PTVS12VS1UR,115")
      (footprint "eagle-import:SOD123W")
      (fields (field (name "MOUSER_PART_NUMBER") "771-PTVS12VS1UR115"))
      (libsource (lib "eagle-import") (part "PTVS12VS1UR,115"))
    )
    (comp (ref "D28")
      (value "PTVS12VS1UR,115")
      (footprint "eagle-import:SOD123W")
      (fields (field (name "MOUSER_PART_NUMBER") "771-PTVS12VS1UR115"))
      (libsource (lib "eagle-import") (part "PTVS12VS1UR,115"))
    )
    (comp (ref "D29")
      (value "PTVS12VS1UR,115")
      (footprint "eagle-import:SOD123W")
      (fields (field (name "MOUSER_PART_NUMBER") "771-PTVS12VS1UR115"))
      (libsource (lib "eagle-import") (part "PTVS12VS1UR,115"))
    )
    (comp (ref "D30")
      (value "PTVS12VS1UR,115")
      (footprint "eagle-import:SOD123W")
      (fields (field (name "MOUSER_PART_NUMBER") "771-PTVS12VS1UR115"))
      (libsource (lib "eagle-import") (part "PTVS12VS1UR,115"))
    )
    (comp (ref "D31")
      (value "PTVS12VS1UR,115")
      (footprint "eagle-import:SOD123W")
      (fields (field (name "MOUSER_PART_NUMBER") "771-PTVS12VS1UR115"))
      (libsource (lib "eagle-import") (part "PTVS12VS1UR,115"))
    )
    (comp (ref "D32")
      (value "PTVS12VS1UR,115")
      (footprint "eagle-import:SOD123W")
      (fields (field (name "MOUSER_PART_NUMBER") "771-PTVS12VS1UR115"))
      (libsource (lib "eagle-import") (part "PTVS12VS1UR,115"))
    )
    (comp (ref "D33")
      (value "PTVS12VS1UR,115")
      (footprint "eagle-import:SOD123W")
      (fields (field (name "MOUSER_PART_NUMBER") "771-PTVS12VS1UR115"))
      (libsource (lib "eagle-import") (part "PTVS12VS1UR,115"))
    )
    (comp (ref "D34")
      (value "PTVS12VS1UR,115")
      (footprint "eagle-import:SOD123W")
      (fields (field (name "MOUSER_PART_NUMBER") "771-PTVS12VS1UR115"))
      (libsource (lib "eagle-import") (part "PTVS12VS1UR,115"))
    )
    (comp (ref "D35")
      (value "PTVS12VS1UR,115")
      (footprint "eagle-import:SOD123W")
      (fields (field (name "MOUSER_PART_NUMBER") "771-PTVS12VS1UR115"))
      (libsource (lib "eagle-import") (part "PTVS12VS1UR,115"))
    )
    (comp (ref "D36")
      (value "PTVS12VS1UR,115")
      (footprint "eagle-import:SOD123W")
      (fields (field (name "MOUSER_PART_NUMBER") "771-PTVS12VS1UR115"))
      (libsource (lib "eagle-import") (part "PTVS12VS1UR,115"))
    )
    (comp (ref "D37")
      (value "PTVS12VS1UR,115")
      (footprint "eagle-import:SOD123W")
      (fields (field (name "MOUSER_PART_NUMBER") "771-PTVS12VS1UR115"))
      (libsource (lib "eagle-import") (part "PTVS12VS1UR,115"))
    )
    (comp (ref "D38")
      (value "PTVS12VS1UR,115")
      (footprint "eagle-import:SOD123W")
      (fields (field (name "MOUSER_PART_NUMBER") "771-PTVS12VS1UR115"))
      (libsource (lib "eagle-import") (part "PTVS12VS1UR,115"))
    )
    (comp (ref "D39")
      (value "PTVS12VS1UR,115")
      (footprint "eagle-import:SOD123W")
      (fields (field (name "MOUSER_PART_NUMBER") "771-PTVS12VS1UR115"))
      (libsource (lib "eagle-import") (part "PTVS12VS1UR,115"))
    )
    (comp (ref "D40")
      (value "PTVS12VS1UR,115")
      (footprint "eagle-import:SOD123W")
      (fields (field (name "MOUSER_PART_NUMBER") "771-PTVS12VS1UR115"))
      (libsource (lib "eagle-import") (part "PTVS12VS1UR,115"))
    )
    (comp (ref "D41")
      (value "PTVS12VS1UR,115")
      (footprint "eagle-import:SOD123W")
      (fields (field (name "MOUSER_PART_NUMBER") "771-PTVS12VS1UR115"))
      (libsource (lib "eagle-import") (part "PTVS12VS1UR,115"))
    )
    (comp (ref "D42")
      (value "PTVS12VS1UR,115")
      (footprint "eagle-import:SOD123W")
      (fields (field (name "MOUSER_PART_NUMBER") "771-PTVS12VS1UR115"))
      (libsource (lib "eagle-import") (part "PTVS12VS1UR,115"))
    )
    (comp (ref "D43")
      (value "PTVS12VS1UR,115")
      (footprint "eagle-import:SOD123W")
      (fields (field (name "MOUSER_PART_NUMBER") "771-PTVS12VS1UR115"))
      (libsource (lib "eagle-import") (part "PTVS12VS1UR,115"))
    )
    (comp (ref "D44")
      (value "PTVS12VS1UR,115")
      (footprint "eagle-import:SOD123W")
      (fields (field (name "MOUSER_PART_NUMBER") "771-PTVS12VS1UR115"))
      (libsource (lib "eagle-import") (part "PTVS12VS1UR,115"))
    )
    (comp (ref "D46")
      (value "PTVS12VS1UR,115")
      (footprint "eagle-import:SOD123W")
      (fields (field (name "MOUSER_PART_NUMBER") "771-PTVS12VS1UR115"))
      (libsource (lib "eagle-import") (part "PTVS12VS1UR,115"))
    )
    (comp (ref "D47")
      (value "PTVS12VS1UR,115")
      (footprint "eagle-import:SOD123W")
      (fields (field (name "MOUSER_PART_NUMBER") "771-PTVS12VS1UR115"))
      (libsource (lib "eagle-import") (part "PTVS12VS1UR,115"))
    )
    (comp (ref "D49")
      (value "PTVS12VS1UR,115")
      (footprint "eagle-import:SOD123W")
      (fields (field (name "MOUSER_PART_NUMBER") "771-PTVS12VS1UR115"))
      (libsource (lib "eagle-import") (part "PTVS12VS1UR,115"))
    )
    (comp (ref "D50")
      (value "PTVS12VS1UR,115")
      (footprint "eagle-import:SOD123W")
      (fields (field (name "MOUSER_PART_NUMBER") "771-PTVS12VS1UR115"))
      (libsource (lib "eagle-import") (part "PTVS12VS1UR,115"))
    )
    (comp (ref "D51")
      (value "PTVS12VS1UR,115")
      (footprint "eagle-import:SOD123W")
      (fields (field (name "MOUSER_PART_NUMBER") "771-PTVS12VS1UR115"))
      (libsource (lib "eagle-import") (part "PTVS12VS1UR,115"))
    )
    (comp (ref "D52")
      (value "PTVS12VS1UR,115")
      (footprint "eagle-import:SOD123W")
      (fields (field (name "MOUSER_PART_NUMBER") "771-PTVS12VS1UR115"))
      (libsource (lib "eagle-import") (part "PTVS12VS1UR,115"))
    )
    (comp (ref "D53")
      (value "PTVS12VS1UR,115")
      (footprint "eagle-import:SOD123W")
      (fields (field (name "MOUSER_PART_NUMBER") "771-PTVS12VS1UR115"))
      (libsource (lib "eagle-import") (part "PTVS12VS1UR,115"))
    )
    (comp (ref "D54")
      (value "PTVS12VS1UR,115")
      (footprint "eagle-import:SOD123W")
      (fields (field (name "MOUSER_PART_NUMBER") "771-PTVS12VS1UR115"))
      (libsource (lib "eagle-import") (part "PTVS12VS1UR,115"))
    )
    (comp (ref "D55")
      (value "PTVS12VS1UR,115")
      (footprint "eagle-import:SOD123W")
      (fields (field (name "MOUSER_PART_NUMBER") "771-PTVS12VS1UR115"))
      (libsource (lib "eagle-import") (part "PTVS12VS1UR,115"))
    )
    (comp (ref "D56")
      (value "PTVS12VS1UR,115")
      (footprint "eagle-import:SOD123W")
      (fields (field (name "MOUSER_PART_NUMBER") "771-PTVS12VS1UR115"))
      (libsource (lib "eagle-import") (part "PTVS12VS1UR,115"))
    )
    (comp (ref "D57")
      (value "PTVS12VS1UR,115")
      (footprint "eagle-import:SOD123W")
      (fields (field (name "MOUSER_PART_NUMBER") "771-PTVS12VS1UR115"))
      (libsource (lib "eagle-import") (part "PTVS12VS1UR,115"))
    )
    (comp (ref "D58")
      (value "PTVS12VS1UR,115")
      (footprint "eagle-import:SOD123W")
      (fields (field (name "MOUSER_PART_NUMBER") "771-PTVS12VS1UR115"))
      (libsource (lib "eagle-import") (part "PTVS12VS1UR,115"))
    )
    (comp (ref "D59")
      (value "PTVS12VS1UR,115")
      (footprint "eagle-import:SOD123W")
      (fields (field (name "MOUSER_PART_NUMBER") "771-PTVS12VS1UR115"))
      (libsource (lib "eagle-import") (part "PTVS12VS1UR,115"))
    )
    (comp (ref "D60")
      (value "PTVS12VS1UR,115")
      (footprint "eagle-import:SOD123W")
      (fields (field (name "MOUSER_PART_NUMBER") "771-PTVS12VS1UR115"))
      (libsource (lib "eagle-import") (part "PTVS12VS1UR,115"))
    )
    (comp (ref "D61")
      (value "PTVS12VS1UR,115")
      (footprint "eagle-import:SOD123W")
      (fields (field (name "MOUSER_PART_NUMBER") "771-PTVS12VS1UR115"))
      (libsource (lib "eagle-import") (part "PTVS12VS1UR,115"))
    )
    (comp (ref "D62")
      (value "PTVS12VS1UR,115")
      (footprint "eagle-import:SOD123W")
      (fields (field (name "MOUSER_PART_NUMBER") "771-PTVS12VS1UR115"))
      (libsource (lib "eagle-import") (part "PTVS12VS1UR,115"))
    )
    (comp (ref "D63")
      (value "PTVS12VS1UR,115")
      (footprint "eagle-import:SOD123W")
      (fields (field (name "MOUSER_PART_NUMBER") "771-PTVS12VS1UR115"))
      (libsource (lib "eagle-import") (part "PTVS12VS1UR,115"))
    )
    (comp (ref "D64")
      (value "PTVS12VS1UR,115")
      (footprint "eagle-import:SOD123W")
      (fields (field (name "MOUSER_PART_NUMBER") "771-PTVS12VS1UR115"))
      (libsource (lib "eagle-import") (part "PTVS12VS1UR,115"))
    )
    (comp (ref "D65")
      (value "PTVS12VS1UR,115")
      (footprint "eagle-import:SOD123W")
      (fields (field (name "MOUSER_PART_NUMBER") "771-PTVS12VS1UR115"))
      (libsource (lib "eagle-import") (part "PTVS12VS1UR,115"))
    )
    (comp (ref "D66")
      (value "PTVS12VS1UR,115")
      (footprint "eagle-import:SOD123W")
      (fields (field (name "MOUSER_PART_NUMBER") "771-PTVS12VS1UR115"))
      (libsource (lib "eagle-import") (part "PTVS12VS1UR,115"))
    )
    (comp (ref "D67")
      (value "PTVS12VS1UR,115")
      (footprint "eagle-import:SOD123W")
      (fields (field (name "MOUSER_PART_NUMBER") "771-PTVS12VS1UR115"))
      (libsource (lib "eagle-import") (part "PTVS12VS1UR,115"))
    )
    (comp (ref "D68")
      (value "PTVS12VS1UR,115")
      (footprint "eagle-import:SOD123W")
      (fields (field (name "MOUSER_PART_NUMBER") "771-PTVS12VS1UR115"))
      (libsource (lib "eagle-import") (part "PTVS12VS1UR,115"))
    )
    (comp (ref "D69")
      (value "PTVS12VS1UR,115")
      (footprint "eagle-import:SOD123W")
      (fields (field (name "MOUSER_PART_NUMBER") "771-PTVS12VS1UR115"))
      (libsource (lib "eagle-import") (part "PTVS12VS1UR,115"))
    )
    (comp (ref "D70")
      (value "PTVS12VS1UR,115")
      (footprint "eagle-import:SOD123W")
      (fields (field (name "MOUSER_PART_NUMBER") "771-PTVS12VS1UR115"))
      (libsource (lib "eagle-import") (part "PTVS12VS1UR,115"))
    )
    (comp (ref "D71")
      (value "PTVS12VS1UR,115")
      (footprint "eagle-import:SOD123W")
      (fields (field (name "MOUSER_PART_NUMBER") "771-PTVS12VS1UR115"))
      (libsource (lib "eagle-import") (part "PTVS12VS1UR,115"))
    )
    (comp (ref "D72")
      (value "PTVS12VS1UR,115")
      (footprint "eagle-import:SOD123W")
      (fields (field (name "MOUSER_PART_NUMBER") "771-PTVS12VS1UR115"))
      (libsource (lib "eagle-import") (part "PTVS12VS1UR,115"))
    )
    (comp (ref "D73")
      (value "PTVS12VS1UR,115")
      (footprint "eagle-import:SOD123W")
      (fields (field (name "MOUSER_PART_NUMBER") "771-PTVS12VS1UR115"))
      (libsource (lib "eagle-import") (part "PTVS12VS1UR,115"))
    )
    (comp (ref "D74")
      (value "PTVS12VS1UR,115")
      (footprint "eagle-import:SOD123W")
      (fields (field (name "MOUSER_PART_NUMBER") "771-PTVS12VS1UR115"))
      (libsource (lib "eagle-import") (part "PTVS12VS1UR,115"))
    )
    (comp (ref "D76")
      (value "PTVS12VS1UR,115")
      (footprint "eagle-import:SOD123W")
      (fields (field (name "MOUSER_PART_NUMBER") "771-PTVS12VS1UR115"))
      (libsource (lib "eagle-import") (part "PTVS12VS1UR,115"))
    )
    (comp (ref "D77")
      (value "PTVS12VS1UR,115")
      (footprint "eagle-import:SOD123W")
      (fields (field (name "MOUSER_PART_NUMBER") "771-PTVS12VS1UR115"))
      (libsource (lib "eagle-import") (part "PTVS12VS1UR,115"))
    )
    (comp (ref "IC4")
      (value "LTC4222CUH#PBF")
      (footprint "eagle-import:QFN50P500X500X80-33T345N")
      (fields
        (field (name "MANUFACTURER_PART_NUMBER") "LTC4222CUH#PBF ")
        (field (name "MOUSER_PART_NUMBER") "584-LTC4222CUH#PBF ")
      )
      (libsource (lib "eagle-import") (part "LTC4222CUH#PBF"))
    )
    (comp (ref "IC11")
      (value "LTC4222CUH#PBF")
      (footprint "eagle-import:QFN50P500X500X80-33T345N")
      (fields
        (field (name "MANUFACTURER_PART_NUMBER") "LTC4222CUH#PBF ")
        (field (name "MOUSER_PART_NUMBER") "584-LTC4222CUH#PBF ")
      )
      (libsource (lib "eagle-import") (part "LTC4222CUH#PBF"))
    )
    (comp (ref "IC12")
      (value "LTC4222CUH#PBF")
      (footprint "eagle-import:QFN50P500X500X80-33T345N")
      (fields
        (field (name "MANUFACTURER_PART_NUMBER") "LTC4222CUH#PBF ")
        (field (name "MOUSER_PART_NUMBER") "584-LTC4222CUH#PBF ")
      )
      (libsource (lib "eagle-import") (part "LTC4222CUH#PBF"))
    )
    (comp (ref "IC13")
      (value "LTC4222CUH#PBF")
      (footprint "eagle-import:QFN50P500X500X80-33T345N")
      (fields
        (field (name "MANUFACTURER_PART_NUMBER") "LTC4222CUH#PBF ")
        (field (name "MOUSER_PART_NUMBER") "584-LTC4222CUH#PBF ")
      )
      (libsource (lib "eagle-import") (part "LTC4222CUH#PBF"))
    )
    (comp (ref "IC14")
      (value "LTC4222CUH#PBF")
      (footprint "eagle-import:QFN50P500X500X80-33T345N")
      (fields
        (field (name "MANUFACTURER_PART_NUMBER") "LTC4222CUH#PBF ")
        (field (name "MOUSER_PART_NUMBER") "584-LTC4222CUH#PBF ")
      )
      (libsource (lib "eagle-import") (part "LTC4222CUH#PBF"))
    )
    (comp (ref "IC15")
      (value "LTC4222CUH#PBF")
      (footprint "eagle-import:QFN50P500X500X80-33T345N")
      (fields
        (field (name "MANUFACTURER_PART_NUMBER") "LTC4222CUH#PBF ")
        (field (name "MOUSER_PART_NUMBER") "584-LTC4222CUH#PBF ")
      )
      (libsource (lib "eagle-import") (part "LTC4222CUH#PBF"))
    )
    (comp (ref "IC16")
      (value "LTC4222CUH#PBF")
      (footprint "eagle-import:QFN50P500X500X80-33T345N")
      (fields
        (field (name "MANUFACTURER_PART_NUMBER") "LTC4222CUH#PBF ")
        (field (name "MOUSER_PART_NUMBER") "584-LTC4222CUH#PBF ")
      )
      (libsource (lib "eagle-import") (part "LTC4222CUH#PBF"))
    )
    (comp (ref "IC17")
      (value "LTC4222CUH#PBF")
      (footprint "eagle-import:QFN50P500X500X80-33T345N")
      (fields
        (field (name "MANUFACTURER_PART_NUMBER") "LTC4222CUH#PBF ")
        (field (name "MOUSER_PART_NUMBER") "584-LTC4222CUH#PBF ")
      )
      (libsource (lib "eagle-import") (part "LTC4222CUH#PBF"))
    )
    (comp (ref "IC18")
      (value "LTC4222CUH#PBF")
      (footprint "eagle-import:QFN50P500X500X80-33T345N")
      (fields
        (field (name "MANUFACTURER_PART_NUMBER") "LTC4222CUH#PBF ")
        (field (name "MOUSER_PART_NUMBER") "584-LTC4222CUH#PBF ")
      )
      (libsource (lib "eagle-import") (part "LTC4222CUH#PBF"))
    )
    (comp (ref "IC19")
      (value "LTC4222CUH#PBF")
      (footprint "eagle-import:QFN50P500X500X80-33T345N")
      (fields
        (field (name "MANUFACTURER_PART_NUMBER") "LTC4222CUH#PBF ")
        (field (name "MOUSER_PART_NUMBER") "584-LTC4222CUH#PBF ")
      )
      (libsource (lib "eagle-import") (part "LTC4222CUH#PBF"))
    )
    (comp (ref "IC20")
      (value "LTC4222CUH#PBF")
      (footprint "eagle-import:QFN50P500X500X80-33T345N")
      (fields
        (field (name "MANUFACTURER_PART_NUMBER") "LTC4222CUH#PBF ")
        (field (name "MOUSER_PART_NUMBER") "584-LTC4222CUH#PBF ")
      )
      (libsource (lib "eagle-import") (part "LTC4222CUH#PBF"))
    )
    (comp (ref "IC21")
      (value "LTC4222CUH#PBF")
      (footprint "eagle-import:QFN50P500X500X80-33T345N")
      (fields
        (field (name "MANUFACTURER_PART_NUMBER") "LTC4222CUH#PBF ")
        (field (name "MOUSER_PART_NUMBER") "584-LTC4222CUH#PBF ")
      )
      (libsource (lib "eagle-import") (part "LTC4222CUH#PBF"))
    )
    (comp (ref "IC22")
      (value "LTC4222CUH#PBF")
      (footprint "eagle-import:QFN50P500X500X80-33T345N")
      (fields
        (field (name "MANUFACTURER_PART_NUMBER") "LTC4222CUH#PBF ")
        (field (name "MOUSER_PART_NUMBER") "584-LTC4222CUH#PBF ")
      )
      (libsource (lib "eagle-import") (part "LTC4222CUH#PBF"))
    )
    (comp (ref "IC23")
      (value "LTC4222CUH#PBF")
      (footprint "eagle-import:QFN50P500X500X80-33T345N")
      (fields
        (field (name "MANUFACTURER_PART_NUMBER") "LTC4222CUH#PBF ")
        (field (name "MOUSER_PART_NUMBER") "584-LTC4222CUH#PBF ")
      )
      (libsource (lib "eagle-import") (part "LTC4222CUH#PBF"))
    )
    (comp (ref "J5")
      (value "TFM-140-02-L-D-WT-K")
      (footprint "eagle-import:SAMTEC_TFM-140-02-L-D-WT-K")
      (fields (field (name "MANUFACTURER") "SAMTEC"))
      (libsource (lib "eagle-import") (part "TFM-140-02-L-D-WT-K"))
    )
    (comp (ref "J6")
      (value "TFM-140-02-L-D-WT-K")
      (footprint "eagle-import:SAMTEC_TFM-140-02-L-D-WT-K")
      (fields (field (name "MANUFACTURER") "SAMTEC"))
      (libsource (lib "eagle-import") (part "TFM-140-02-L-D-WT-K"))
    )
    (comp (ref "LED1")
      (value "APHD1608LSURCK")
      (footprint "eagle-import:LEDM168X80N")
      (fields (field (name "MOUSER_PART_NUMBER") "604-APHD1608LSURCK"))
      (libsource (lib "eagle-import") (part "APHD1608LSURCK"))
    )
    (comp (ref "LED2")
      (value "AA3021LSYSK_J3-TR")
      (footprint "eagle-import:AA3021LSYSKJ3TR")
      (fields
        (field (name "MANUFACTURER_PART_NUMBER") "AA3021LSYSK/J3-TR")
        (field (name "MOUSER_PART_NUMBER") "604-AA3021LSYSK/J3TR")
      )
      (libsource (lib "eagle-import") (part "AA3021LSYSK_J3-TR"))
    )
    (comp (ref "LED3")
      (value "APTD1608LCGCK")
      (footprint "eagle-import:APT1608CGCK")
      (fields (field (name "MOUSER_PART_NUMBER") "604-APTD1608LCGCK"))
      (libsource (lib "eagle-import") (part "APTD1608LCGCK"))
    )
    (comp (ref "LED4")
      (value "APHD1608LSURCK")
      (footprint "eagle-import:LEDM168X80N")
      (fields (field (name "MOUSER_PART_NUMBER") "604-APHD1608LSURCK"))
      (libsource (lib "eagle-import") (part "APHD1608LSURCK"))
    )
    (comp (ref "LED5")
      (value "APTD1608LCGCK")
      (footprint "eagle-import:APT1608CGCK")
      (fields (field (name "MOUSER_PART_NUMBER") "604-APTD1608LCGCK"))
      (libsource (lib "eagle-import") (part "APTD1608LCGCK"))
    )
    (comp (ref "LED6")
      (value "APHD1608LSURCK")
      (footprint "eagle-import:LEDM168X80N")
      (fields (field (name "MOUSER_PART_NUMBER") "604-APHD1608LSURCK"))
      (libsource (lib "eagle-import") (part "APHD1608LSURCK"))
    )
    (comp (ref "LED7")
      (value "AA3021LSYSK_J3-TR")
      (footprint "eagle-import:AA3021LSYSKJ3TR")
      (fields
        (field (name "MANUFACTURER_PART_NUMBER") "AA3021LSYSK/J3-TR")
        (field (name "MOUSER_PART_NUMBER") "604-AA3021LSYSK/J3TR")
      )
      (libsource (lib "eagle-import") (part "AA3021LSYSK_J3-TR"))
    )
    (comp (ref "LED8")
      (value "APTD1608LCGCK")
      (footprint "eagle-import:APT1608CGCK")
      (fields (field (name "MOUSER_PART_NUMBER") "604-APTD1608LCGCK"))
      (libsource (lib "eagle-import") (part "APTD1608LCGCK"))
    )
    (comp (ref "LED9")
      (value "APHD1608LSURCK")
      (footprint "eagle-import:LEDM168X80N")
      (fields (field (name "MOUSER_PART_NUMBER") "604-APHD1608LSURCK"))
      (libsource (lib "eagle-import") (part "APHD1608LSURCK"))
    )
    (comp (ref "LED10")
      (value "APTD1608LCGCK")
      (footprint "eagle-import:APT1608CGCK")
      (fields (field (name "MOUSER_PART_NUMBER") "604-APTD1608LCGCK"))
      (libsource (lib "eagle-import") (part "APTD1608LCGCK"))
    )
    (comp (ref "LED11")
      (value "APHD1608LSURCK")
      (footprint "eagle-import:LEDM168X80N")
      (fields (field (name "MOUSER_PART_NUMBER") "604-APHD1608LSURCK"))
      (libsource (lib "eagle-import") (part "APHD1608LSURCK"))
    )
    (comp (ref "LED12")
      (value "AA3021LSYSK_J3-TR")
      (footprint "eagle-import:AA3021LSYSKJ3TR")
      (fields
        (field (name "MANUFACTURER_PART_NUMBER") "AA3021LSYSK/J3-TR")
        (field (name "MOUSER_PART_NUMBER") "604-AA3021LSYSK/J3TR")
      )
      (libsource (lib "eagle-import") (part "AA3021LSYSK_J3-TR"))
    )
    (comp (ref "LED13")
      (value "APTD1608LCGCK")
      (footprint "eagle-import:APT1608CGCK")
      (fields (field (name "MOUSER_PART_NUMBER") "604-APTD1608LCGCK"))
      (libsource (lib "eagle-import") (part "APTD1608LCGCK"))
    )
    (comp (ref "LED14")
      (value "APHD1608LSURCK")
      (footprint "eagle-import:LEDM168X80N")
      (fields (field (name "MOUSER_PART_NUMBER") "604-APHD1608LSURCK"))
      (libsource (lib "eagle-import") (part "APHD1608LSURCK"))
    )
    (comp (ref "LED15")
      (value "APTD1608LCGCK")
      (footprint "eagle-import:APT1608CGCK")
      (fields (field (name "MOUSER_PART_NUMBER") "604-APTD1608LCGCK"))
      (libsource (lib "eagle-import") (part "APTD1608LCGCK"))
    )
    (comp (ref "LED16")
      (value "APHD1608LSURCK")
      (footprint "eagle-import:LEDM168X80N")
      (fields (field (name "MOUSER_PART_NUMBER") "604-APHD1608LSURCK"))
      (libsource (lib "eagle-import") (part "APHD1608LSURCK"))
    )
    (comp (ref "LED17")
      (value "AA3021LSYSK_J3-TR")
      (footprint "eagle-import:AA3021LSYSKJ3TR")
      (fields
        (field (name "MANUFACTURER_PART_NUMBER") "AA3021LSYSK/J3-TR")
        (field (name "MOUSER_PART_NUMBER") "604-AA3021LSYSK/J3TR")
      )
      (libsource (lib "eagle-import") (part "AA3021LSYSK_J3-TR"))
    )
    (comp (ref "LED18")
      (value "APTD1608LCGCK")
      (footprint "eagle-import:APT1608CGCK")
      (fields (field (name "MOUSER_PART_NUMBER") "604-APTD1608LCGCK"))
      (libsource (lib "eagle-import") (part "APTD1608LCGCK"))
    )
    (comp (ref "LED19")
      (value "APHD1608LSURCK")
      (footprint "eagle-import:LEDM168X80N")
      (fields (field (name "MOUSER_PART_NUMBER") "604-APHD1608LSURCK"))
      (libsource (lib "eagle-import") (part "APHD1608LSURCK"))
    )
    (comp (ref "LED20")
      (value "APTD1608LCGCK")
      (footprint "eagle-import:APT1608CGCK")
      (fields (field (name "MOUSER_PART_NUMBER") "604-APTD1608LCGCK"))
      (libsource (lib "eagle-import") (part "APTD1608LCGCK"))
    )
    (comp (ref "LED21")
      (value "APHD1608LSURCK")
      (footprint "eagle-import:LEDM168X80N")
      (fields (field (name "MOUSER_PART_NUMBER") "604-APHD1608LSURCK"))
      (libsource (lib "eagle-import") (part "APHD1608LSURCK"))
    )
    (comp (ref "LED22")
      (value "AA3021LSYSK_J3-TR")
      (footprint "eagle-import:AA3021LSYSKJ3TR")
      (fields
        (field (name "MANUFACTURER_PART_NUMBER") "AA3021LSYSK/J3-TR")
        (field (name "MOUSER_PART_NUMBER") "604-AA3021LSYSK/J3TR")
      )
      (libsource (lib "eagle-import") (part "AA3021LSYSK_J3-TR"))
    )
    (comp (ref "LED23")
      (value "APTD1608LCGCK")
      (footprint "eagle-import:APT1608CGCK")
      (fields (field (name "MOUSER_PART_NUMBER") "604-APTD1608LCGCK"))
      (libsource (lib "eagle-import") (part "APTD1608LCGCK"))
    )
    (comp (ref "LED24")
      (value "APHD1608LSURCK")
      (footprint "eagle-import:LEDM168X80N")
      (fields (field (name "MOUSER_PART_NUMBER") "604-APHD1608LSURCK"))
      (libsource (lib "eagle-import") (part "APHD1608LSURCK"))
    )
    (comp (ref "LED25")
      (value "APTD1608LCGCK")
      (footprint "eagle-import:APT1608CGCK")
      (fields (field (name "MOUSER_PART_NUMBER") "604-APTD1608LCGCK"))
      (libsource (lib "eagle-import") (part "APTD1608LCGCK"))
    )
    (comp (ref "LED26")
      (value "APHD1608LSURCK")
      (footprint "eagle-import:LEDM168X80N")
      (fields (field (name "MOUSER_PART_NUMBER") "604-APHD1608LSURCK"))
      (libsource (lib "eagle-import") (part "APHD1608LSURCK"))
    )
    (comp (ref "LED27")
      (value "AA3021LSYSK_J3-TR")
      (footprint "eagle-import:AA3021LSYSKJ3TR")
      (fields
        (field (name "MANUFACTURER_PART_NUMBER") "AA3021LSYSK/J3-TR")
        (field (name "MOUSER_PART_NUMBER") "604-AA3021LSYSK/J3TR")
      )
      (libsource (lib "eagle-import") (part "AA3021LSYSK_J3-TR"))
    )
    (comp (ref "LED28")
      (value "APTD1608LCGCK")
      (footprint "eagle-import:APT1608CGCK")
      (fields (field (name "MOUSER_PART_NUMBER") "604-APTD1608LCGCK"))
      (libsource (lib "eagle-import") (part "APTD1608LCGCK"))
    )
    (comp (ref "LED29")
      (value "APHD1608LSURCK")
      (footprint "eagle-import:LEDM168X80N")
      (fields (field (name "MOUSER_PART_NUMBER") "604-APHD1608LSURCK"))
      (libsource (lib "eagle-import") (part "APHD1608LSURCK"))
    )
    (comp (ref "LED30")
      (value "APTD1608LCGCK")
      (footprint "eagle-import:APT1608CGCK")
      (fields (field (name "MOUSER_PART_NUMBER") "604-APTD1608LCGCK"))
      (libsource (lib "eagle-import") (part "APTD1608LCGCK"))
    )
    (comp (ref "LED31")
      (value "APHD1608LSURCK")
      (footprint "eagle-import:LEDM168X80N")
      (fields (field (name "MOUSER_PART_NUMBER") "604-APHD1608LSURCK"))
      (libsource (lib "eagle-import") (part "APHD1608LSURCK"))
    )
    (comp (ref "LED32")
      (value "AA3021LSYSK_J3-TR")
      (footprint "eagle-import:AA3021LSYSKJ3TR")
      (fields
        (field (name "MANUFACTURER_PART_NUMBER") "AA3021LSYSK/J3-TR")
        (field (name "MOUSER_PART_NUMBER") "604-AA3021LSYSK/J3TR")
      )
      (libsource (lib "eagle-import") (part "AA3021LSYSK_J3-TR"))
    )
    (comp (ref "LED33")
      (value "APTD1608LCGCK")
      (footprint "eagle-import:APT1608CGCK")
      (fields (field (name "MOUSER_PART_NUMBER") "604-APTD1608LCGCK"))
      (libsource (lib "eagle-import") (part "APTD1608LCGCK"))
    )
    (comp (ref "LED34")
      (value "APHD1608LSURCK")
      (footprint "eagle-import:LEDM168X80N")
      (fields (field (name "MOUSER_PART_NUMBER") "604-APHD1608LSURCK"))
      (libsource (lib "eagle-import") (part "APHD1608LSURCK"))
    )
    (comp (ref "LED35")
      (value "APTD1608LCGCK")
      (footprint "eagle-import:APT1608CGCK")
      (fields (field (name "MOUSER_PART_NUMBER") "604-APTD1608LCGCK"))
      (libsource (lib "eagle-import") (part "APTD1608LCGCK"))
    )
    (comp (ref "LED36")
      (value "APHD1608LSURCK")
      (footprint "eagle-import:LEDM168X80N")
      (fields (field (name "MOUSER_PART_NUMBER") "604-APHD1608LSURCK"))
      (libsource (lib "eagle-import") (part "APHD1608LSURCK"))
    )
    (comp (ref "LED37")
      (value "AA3021LSYSK_J3-TR")
      (footprint "eagle-import:AA3021LSYSKJ3TR")
      (fields
        (field (name "MANUFACTURER_PART_NUMBER") "AA3021LSYSK/J3-TR")
        (field (name "MOUSER_PART_NUMBER") "604-AA3021LSYSK/J3TR")
      )
      (libsource (lib "eagle-import") (part "AA3021LSYSK_J3-TR"))
    )
    (comp (ref "LED38")
      (value "APTD1608LCGCK")
      (footprint "eagle-import:APT1608CGCK")
      (fields (field (name "MOUSER_PART_NUMBER") "604-APTD1608LCGCK"))
      (libsource (lib "eagle-import") (part "APTD1608LCGCK"))
    )
    (comp (ref "LED39")
      (value "APHD1608LSURCK")
      (footprint "eagle-import:LEDM168X80N")
      (fields (field (name "MOUSER_PART_NUMBER") "604-APHD1608LSURCK"))
      (libsource (lib "eagle-import") (part "APHD1608LSURCK"))
    )
    (comp (ref "LED40")
      (value "APTD1608LCGCK")
      (footprint "eagle-import:APT1608CGCK")
      (fields (field (name "MOUSER_PART_NUMBER") "604-APTD1608LCGCK"))
      (libsource (lib "eagle-import") (part "APTD1608LCGCK"))
    )
    (comp (ref "LED41")
      (value "APHD1608LSURCK")
      (footprint "eagle-import:LEDM168X80N")
      (fields (field (name "MOUSER_PART_NUMBER") "604-APHD1608LSURCK"))
      (libsource (lib "eagle-import") (part "APHD1608LSURCK"))
    )
    (comp (ref "LED42")
      (value "AA3021LSYSK_J3-TR")
      (footprint "eagle-import:AA3021LSYSKJ3TR")
      (fields
        (field (name "MANUFACTURER_PART_NUMBER") "AA3021LSYSK/J3-TR")
        (field (name "MOUSER_PART_NUMBER") "604-AA3021LSYSK/J3TR")
      )
      (libsource (lib "eagle-import") (part "AA3021LSYSK_J3-TR"))
    )
    (comp (ref "LED43")
      (value "APTD1608LCGCK")
      (footprint "eagle-import:APT1608CGCK")
      (fields (field (name "MOUSER_PART_NUMBER") "604-APTD1608LCGCK"))
      (libsource (lib "eagle-import") (part "APTD1608LCGCK"))
    )
    (comp (ref "LED44")
      (value "APHD1608LSURCK")
      (footprint "eagle-import:LEDM168X80N")
      (fields (field (name "MOUSER_PART_NUMBER") "604-APHD1608LSURCK"))
      (libsource (lib "eagle-import") (part "APHD1608LSURCK"))
    )
    (comp (ref "LED45")
      (value "APTD1608LCGCK")
      (footprint "eagle-import:APT1608CGCK")
      (fields (field (name "MOUSER_PART_NUMBER") "604-APTD1608LCGCK"))
      (libsource (lib "eagle-import") (part "APTD1608LCGCK"))
    )
    (comp (ref "LED46")
      (value "APHD1608LSURCK")
      (footprint "eagle-import:LEDM168X80N")
      (fields (field (name "MOUSER_PART_NUMBER") "604-APHD1608LSURCK"))
      (libsource (lib "eagle-import") (part "APHD1608LSURCK"))
    )
    (comp (ref "LED47")
      (value "AA3021LSYSK_J3-TR")
      (footprint "eagle-import:AA3021LSYSKJ3TR")
      (fields
        (field (name "MANUFACTURER_PART_NUMBER") "AA3021LSYSK/J3-TR")
        (field (name "MOUSER_PART_NUMBER") "604-AA3021LSYSK/J3TR")
      )
      (libsource (lib "eagle-import") (part "AA3021LSYSK_J3-TR"))
    )
    (comp (ref "LED48")
      (value "APTD1608LCGCK")
      (footprint "eagle-import:APT1608CGCK")
      (fields (field (name "MOUSER_PART_NUMBER") "604-APTD1608LCGCK"))
      (libsource (lib "eagle-import") (part "APTD1608LCGCK"))
    )
    (comp (ref "LED49")
      (value "APHD1608LSURCK")
      (footprint "eagle-import:LEDM168X80N")
      (fields (field (name "MOUSER_PART_NUMBER") "604-APHD1608LSURCK"))
      (libsource (lib "eagle-import") (part "APHD1608LSURCK"))
    )
    (comp (ref "LED50")
      (value "APTD1608LCGCK")
      (footprint "eagle-import:APT1608CGCK")
      (fields (field (name "MOUSER_PART_NUMBER") "604-APTD1608LCGCK"))
      (libsource (lib "eagle-import") (part "APTD1608LCGCK"))
    )
    (comp (ref "LED51")
      (value "APHD1608LSURCK")
      (footprint "eagle-import:LEDM168X80N")
      (fields (field (name "MOUSER_PART_NUMBER") "604-APHD1608LSURCK"))
      (libsource (lib "eagle-import") (part "APHD1608LSURCK"))
    )
    (comp (ref "LED52")
      (value "AA3021LSYSK_J3-TR")
      (footprint "eagle-import:AA3021LSYSKJ3TR")
      (fields
        (field (name "MANUFACTURER_PART_NUMBER") "AA3021LSYSK/J3-TR")
        (field (name "MOUSER_PART_NUMBER") "604-AA3021LSYSK/J3TR")
      )
      (libsource (lib "eagle-import") (part "AA3021LSYSK_J3-TR"))
    )
    (comp (ref "LED53")
      (value "APTD1608LCGCK")
      (footprint "eagle-import:APT1608CGCK")
      (fields (field (name "MOUSER_PART_NUMBER") "604-APTD1608LCGCK"))
      (libsource (lib "eagle-import") (part "APTD1608LCGCK"))
    )
    (comp (ref "LED54")
      (value "APHD1608LSURCK")
      (footprint "eagle-import:LEDM168X80N")
      (fields (field (name "MOUSER_PART_NUMBER") "604-APHD1608LSURCK"))
      (libsource (lib "eagle-import") (part "APHD1608LSURCK"))
    )
    (comp (ref "LED55")
      (value "APTD1608LCGCK")
      (footprint "eagle-import:APT1608CGCK")
      (fields (field (name "MOUSER_PART_NUMBER") "604-APTD1608LCGCK"))
      (libsource (lib "eagle-import") (part "APTD1608LCGCK"))
    )
    (comp (ref "LED56")
      (value "APHD1608LSURCK")
      (footprint "eagle-import:LEDM168X80N")
      (fields (field (name "MOUSER_PART_NUMBER") "604-APHD1608LSURCK"))
      (libsource (lib "eagle-import") (part "APHD1608LSURCK"))
    )
    (comp (ref "LED57")
      (value "AA3021LSYSK_J3-TR")
      (footprint "eagle-import:AA3021LSYSKJ3TR")
      (fields
        (field (name "MANUFACTURER_PART_NUMBER") "AA3021LSYSK/J3-TR")
        (field (name "MOUSER_PART_NUMBER") "604-AA3021LSYSK/J3TR")
      )
      (libsource (lib "eagle-import") (part "AA3021LSYSK_J3-TR"))
    )
    (comp (ref "LED58")
      (value "APTD1608LCGCK")
      (footprint "eagle-import:APT1608CGCK")
      (fields (field (name "MOUSER_PART_NUMBER") "604-APTD1608LCGCK"))
      (libsource (lib "eagle-import") (part "APTD1608LCGCK"))
    )
    (comp (ref "LED59")
      (value "APHD1608LSURCK")
      (footprint "eagle-import:LEDM168X80N")
      (fields (field (name "MOUSER_PART_NUMBER") "604-APHD1608LSURCK"))
      (libsource (lib "eagle-import") (part "APHD1608LSURCK"))
    )
    (comp (ref "LED60")
      (value "APTD1608LCGCK")
      (footprint "eagle-import:APT1608CGCK")
      (fields (field (name "MOUSER_PART_NUMBER") "604-APTD1608LCGCK"))
      (libsource (lib "eagle-import") (part "APTD1608LCGCK"))
    )
    (comp (ref "LED61")
      (value "APHD1608LSURCK")
      (footprint "eagle-import:LEDM168X80N")
      (fields (field (name "MOUSER_PART_NUMBER") "604-APHD1608LSURCK"))
      (libsource (lib "eagle-import") (part "APHD1608LSURCK"))
    )
    (comp (ref "LED62")
      (value "AA3021LSYSK_J3-TR")
      (footprint "eagle-import:AA3021LSYSKJ3TR")
      (fields
        (field (name "MANUFACTURER_PART_NUMBER") "AA3021LSYSK/J3-TR")
        (field (name "MOUSER_PART_NUMBER") "604-AA3021LSYSK/J3TR")
      )
      (libsource (lib "eagle-import") (part "AA3021LSYSK_J3-TR"))
    )
    (comp (ref "LED63")
      (value "APTD1608LCGCK")
      (footprint "eagle-import:APT1608CGCK")
      (fields (field (name "MOUSER_PART_NUMBER") "604-APTD1608LCGCK"))
      (libsource (lib "eagle-import") (part "APTD1608LCGCK"))
    )
    (comp (ref "LED64")
      (value "APHD1608LSURCK")
      (footprint "eagle-import:LEDM168X80N")
      (fields (field (name "MOUSER_PART_NUMBER") "604-APHD1608LSURCK"))
      (libsource (lib "eagle-import") (part "APHD1608LSURCK"))
    )
    (comp (ref "LED65")
      (value "APTD1608LCGCK")
      (footprint "eagle-import:APT1608CGCK")
      (fields (field (name "MOUSER_PART_NUMBER") "604-APTD1608LCGCK"))
      (libsource (lib "eagle-import") (part "APTD1608LCGCK"))
    )
    (comp (ref "LED66")
      (value "APHD1608LSURCK")
      (footprint "eagle-import:LEDM168X80N")
      (fields (field (name "MOUSER_PART_NUMBER") "604-APHD1608LSURCK"))
      (libsource (lib "eagle-import") (part "APHD1608LSURCK"))
    )
    (comp (ref "LED67")
      (value "AA3021LSYSK_J3-TR")
      (footprint "eagle-import:AA3021LSYSKJ3TR")
      (fields
        (field (name "MANUFACTURER_PART_NUMBER") "AA3021LSYSK/J3-TR")
        (field (name "MOUSER_PART_NUMBER") "604-AA3021LSYSK/J3TR")
      )
      (libsource (lib "eagle-import") (part "AA3021LSYSK_J3-TR"))
    )
    (comp (ref "LED68")
      (value "APTD1608LCGCK")
      (footprint "eagle-import:APT1608CGCK")
      (fields (field (name "MOUSER_PART_NUMBER") "604-APTD1608LCGCK"))
      (libsource (lib "eagle-import") (part "APTD1608LCGCK"))
    )
    (comp (ref "LED69")
      (value "APHD1608LSURCK")
      (footprint "eagle-import:LEDM168X80N")
      (fields (field (name "MOUSER_PART_NUMBER") "604-APHD1608LSURCK"))
      (libsource (lib "eagle-import") (part "APHD1608LSURCK"))
    )
    (comp (ref "LED70")
      (value "APTD1608LCGCK")
      (footprint "eagle-import:APT1608CGCK")
      (fields (field (name "MOUSER_PART_NUMBER") "604-APTD1608LCGCK"))
      (libsource (lib "eagle-import") (part "APTD1608LCGCK"))
    )
    (comp (ref "LED71")
      (value "SMLD12BN1WT86")
      (footprint "eagle-import:LEDM168X65N")
      (fields (field (name "MOUSER_PART_NUMBER") "755-SMLD12BN1WT86"))
      (libsource (lib "eagle-import") (part "SMLD12BN1WT86"))
    )
    (comp (ref "LED72")
      (value "SMLD12BN1WT86")
      (footprint "eagle-import:LEDM168X65N")
      (fields (field (name "MOUSER_PART_NUMBER") "755-SMLD12BN1WT86"))
      (libsource (lib "eagle-import") (part "SMLD12BN1WT86"))
    )
    (comp (ref "LED73")
      (value "SMLD12BN1WT86")
      (footprint "eagle-import:LEDM168X65N")
      (fields (field (name "MOUSER_PART_NUMBER") "755-SMLD12BN1WT86"))
      (libsource (lib "eagle-import") (part "SMLD12BN1WT86"))
    )
    (comp (ref "LED74")
      (value "SMLD12BN1WT86")
      (footprint "eagle-import:LEDM168X65N")
      (fields (field (name "MOUSER_PART_NUMBER") "755-SMLD12BN1WT86"))
      (libsource (lib "eagle-import") (part "SMLD12BN1WT86"))
    )
    (comp (ref "LED75")
      (value "SMLD12BN1WT86")
      (footprint "eagle-import:LEDM168X65N")
      (fields (field (name "MOUSER_PART_NUMBER") "755-SMLD12BN1WT86"))
      (libsource (lib "eagle-import") (part "SMLD12BN1WT86"))
    )
    (comp (ref "LED76")
      (value "SMLD12BN1WT86")
      (footprint "eagle-import:LEDM168X65N")
      (fields (field (name "MOUSER_PART_NUMBER") "755-SMLD12BN1WT86"))
      (libsource (lib "eagle-import") (part "SMLD12BN1WT86"))
    )
    (comp (ref "LED77")
      (value "SMLD12BN1WT86")
      (footprint "eagle-import:LEDM168X65N")
      (fields (field (name "MOUSER_PART_NUMBER") "755-SMLD12BN1WT86"))
      (libsource (lib "eagle-import") (part "SMLD12BN1WT86"))
    )
    (comp (ref "LED78")
      (value "SMLD12BN1WT86")
      (footprint "eagle-import:LEDM168X65N")
      (fields (field (name "MOUSER_PART_NUMBER") "755-SMLD12BN1WT86"))
      (libsource (lib "eagle-import") (part "SMLD12BN1WT86"))
    )
    (comp (ref "LED79")
      (value "SMLD12BN1WT86")
      (footprint "eagle-import:LEDM168X65N")
      (fields (field (name "MOUSER_PART_NUMBER") "755-SMLD12BN1WT86"))
      (libsource (lib "eagle-import") (part "SMLD12BN1WT86"))
    )
    (comp (ref "LED80")
      (value "SMLD12BN1WT86")
      (footprint "eagle-import:LEDM168X65N")
      (fields (field (name "MOUSER_PART_NUMBER") "755-SMLD12BN1WT86"))
      (libsource (lib "eagle-import") (part "SMLD12BN1WT86"))
    )
    (comp (ref "LED81")
      (value "SMLD12BN1WT86")
      (footprint "eagle-import:LEDM168X65N")
      (fields (field (name "MOUSER_PART_NUMBER") "755-SMLD12BN1WT86"))
      (libsource (lib "eagle-import") (part "SMLD12BN1WT86"))
    )
    (comp (ref "LED82")
      (value "SMLD12BN1WT86")
      (footprint "eagle-import:LEDM168X65N")
      (fields (field (name "MOUSER_PART_NUMBER") "755-SMLD12BN1WT86"))
      (libsource (lib "eagle-import") (part "SMLD12BN1WT86"))
    )
    (comp (ref "LED83")
      (value "SMLD12BN1WT86")
      (footprint "eagle-import:LEDM168X65N")
      (fields (field (name "MOUSER_PART_NUMBER") "755-SMLD12BN1WT86"))
      (libsource (lib "eagle-import") (part "SMLD12BN1WT86"))
    )
    (comp (ref "LED84")
      (value "SMLD12BN1WT86")
      (footprint "eagle-import:LEDM168X65N")
      (fields (field (name "MOUSER_PART_NUMBER") "755-SMLD12BN1WT86"))
      (libsource (lib "eagle-import") (part "SMLD12BN1WT86"))
    )
    (comp (ref "LED97")
      (value "ASMT-URB4-YU802")
      (footprint "eagle-import:ASMTURB4YU802")
      (fields (field (name "MOUSER_PART_NUMBER") "630-ASMT-URB4-YU802"))
      (libsource (lib "eagle-import") (part "ASMT-URB4-YU802"))
    )
    (comp (ref "LED98")
      (value "ASMT-URB4-YU802")
      (footprint "eagle-import:ASMTURB4YU802")
      (fields (field (name "MOUSER_PART_NUMBER") "630-ASMT-URB4-YU802"))
      (libsource (lib "eagle-import") (part "ASMT-URB4-YU802"))
    )
    (comp (ref "LED99")
      (value "ASMT-URB4-YU802")
      (footprint "eagle-import:ASMTURB4YU802")
      (fields (field (name "MOUSER_PART_NUMBER") "630-ASMT-URB4-YU802"))
      (libsource (lib "eagle-import") (part "ASMT-URB4-YU802"))
    )
    (comp (ref "LED100")
      (value "ASMT-URB4-YU802")
      (footprint "eagle-import:ASMTURB4YU802")
      (fields (field (name "MOUSER_PART_NUMBER") "630-ASMT-URB4-YU802"))
      (libsource (lib "eagle-import") (part "ASMT-URB4-YU802"))
    )
    (comp (ref "LED101")
      (value "ASMT-URB4-YU802")
      (footprint "eagle-import:ASMTURB4YU802")
      (fields (field (name "MOUSER_PART_NUMBER") "630-ASMT-URB4-YU802"))
      (libsource (lib "eagle-import") (part "ASMT-URB4-YU802"))
    )
    (comp (ref "LED102")
      (value "ASMT-URB4-YU802")
      (footprint "eagle-import:ASMTURB4YU802")
      (fields (field (name "MOUSER_PART_NUMBER") "630-ASMT-URB4-YU802"))
      (libsource (lib "eagle-import") (part "ASMT-URB4-YU802"))
    )
    (comp (ref "LED103")
      (value "ASMT-URB4-YU802")
      (footprint "eagle-import:ASMTURB4YU802")
      (fields (field (name "MOUSER_PART_NUMBER") "630-ASMT-URB4-YU802"))
      (libsource (lib "eagle-import") (part "ASMT-URB4-YU802"))
    )
    (comp (ref "LED104")
      (value "ASMT-URB4-YU802")
      (footprint "eagle-import:ASMTURB4YU802")
      (fields (field (name "MOUSER_PART_NUMBER") "630-ASMT-URB4-YU802"))
      (libsource (lib "eagle-import") (part "ASMT-URB4-YU802"))
    )
    (comp (ref "LED105")
      (value "ASMT-URB4-YU802")
      (footprint "eagle-import:ASMTURB4YU802")
      (fields (field (name "MOUSER_PART_NUMBER") "630-ASMT-URB4-YU802"))
      (libsource (lib "eagle-import") (part "ASMT-URB4-YU802"))
    )
    (comp (ref "LED106")
      (value "ASMT-URB4-YU802")
      (footprint "eagle-import:ASMTURB4YU802")
      (fields (field (name "MOUSER_PART_NUMBER") "630-ASMT-URB4-YU802"))
      (libsource (lib "eagle-import") (part "ASMT-URB4-YU802"))
    )
    (comp (ref "LED107")
      (value "ASMT-URB4-YU802")
      (footprint "eagle-import:ASMTURB4YU802")
      (fields (field (name "MOUSER_PART_NUMBER") "630-ASMT-URB4-YU802"))
      (libsource (lib "eagle-import") (part "ASMT-URB4-YU802"))
    )
    (comp (ref "LED108")
      (value "ASMT-URB4-YU802")
      (footprint "eagle-import:ASMTURB4YU802")
      (fields (field (name "MOUSER_PART_NUMBER") "630-ASMT-URB4-YU802"))
      (libsource (lib "eagle-import") (part "ASMT-URB4-YU802"))
    )
    (comp (ref "LED109")
      (value "ASMT-URB4-YU802")
      (footprint "eagle-import:ASMTURB4YU802")
      (fields (field (name "MOUSER_PART_NUMBER") "630-ASMT-URB4-YU802"))
      (libsource (lib "eagle-import") (part "ASMT-URB4-YU802"))
    )
    (comp (ref "LED110")
      (value "ASMT-URB4-YU802")
      (footprint "eagle-import:ASMTURB4YU802")
      (fields (field (name "MOUSER_PART_NUMBER") "630-ASMT-URB4-YU802"))
      (libsource (lib "eagle-import") (part "ASMT-URB4-YU802"))
    )
    (comp (ref "LED111")
      (value "ASMT-URB4-YU802")
      (footprint "eagle-import:ASMTURB4YU802")
      (fields (field (name "MOUSER_PART_NUMBER") "630-ASMT-URB4-YU802"))
      (libsource (lib "eagle-import") (part "ASMT-URB4-YU802"))
    )
    (comp (ref "LED112")
      (value "ASMT-URB4-YU802")
      (footprint "eagle-import:ASMTURB4YU802")
      (fields (field (name "MOUSER_PART_NUMBER") "630-ASMT-URB4-YU802"))
      (libsource (lib "eagle-import") (part "ASMT-URB4-YU802"))
    )
    (comp (ref "LED113")
      (value "ASMT-URB4-YU802")
      (footprint "eagle-import:ASMTURB4YU802")
      (fields (field (name "MOUSER_PART_NUMBER") "630-ASMT-URB4-YU802"))
      (libsource (lib "eagle-import") (part "ASMT-URB4-YU802"))
    )
    (comp (ref "LED114")
      (value "ASMT-URB4-YU802")
      (footprint "eagle-import:ASMTURB4YU802")
      (fields (field (name "MOUSER_PART_NUMBER") "630-ASMT-URB4-YU802"))
      (libsource (lib "eagle-import") (part "ASMT-URB4-YU802"))
    )
    (comp (ref "M1")
      (value "NTLUS4C12NTAG")
      (footprint "eagle-import:TRANS_NTLUS3A18PZTAG")
      (libsource (lib "eagle-import") (part "NTLUS4C12NTAG"))
    )
    (comp (ref "M2")
      (value "NTLUS4C12NTAG")
      (footprint "eagle-import:TRANS_NTLUS3A18PZTAG")
      (libsource (lib "eagle-import") (part "NTLUS4C12NTAG"))
    )
    (comp (ref "M3")
      (value "NTLUS4C12NTAG")
      (footprint "eagle-import:TRANS_NTLUS3A18PZTAG")
      (libsource (lib "eagle-import") (part "NTLUS4C12NTAG"))
    )
    (comp (ref "M4")
      (value "NTLUS4C12NTAG")
      (footprint "eagle-import:TRANS_NTLUS3A18PZTAG")
      (libsource (lib "eagle-import") (part "NTLUS4C12NTAG"))
    )
    (comp (ref "M5")
      (value "NTLUS4C12NTAG")
      (footprint "eagle-import:TRANS_NTLUS3A18PZTAG")
      (libsource (lib "eagle-import") (part "NTLUS4C12NTAG"))
    )
    (comp (ref "M6")
      (value "NTLUS4C12NTAG")
      (footprint "eagle-import:TRANS_NTLUS3A18PZTAG")
      (libsource (lib "eagle-import") (part "NTLUS4C12NTAG"))
    )
    (comp (ref "M7")
      (value "NTLUS4C12NTAG")
      (footprint "eagle-import:TRANS_NTLUS3A18PZTAG")
      (libsource (lib "eagle-import") (part "NTLUS4C12NTAG"))
    )
    (comp (ref "M8")
      (value "NTLUS4C12NTAG")
      (footprint "eagle-import:TRANS_NTLUS3A18PZTAG")
      (libsource (lib "eagle-import") (part "NTLUS4C12NTAG"))
    )
    (comp (ref "M9")
      (value "NTLUS4C12NTAG")
      (footprint "eagle-import:TRANS_NTLUS3A18PZTAG")
      (libsource (lib "eagle-import") (part "NTLUS4C12NTAG"))
    )
    (comp (ref "M10")
      (value "NTLUS4C12NTAG")
      (footprint "eagle-import:TRANS_NTLUS3A18PZTAG")
      (libsource (lib "eagle-import") (part "NTLUS4C12NTAG"))
    )
    (comp (ref "M11")
      (value "NTLUS4C12NTAG")
      (footprint "eagle-import:TRANS_NTLUS3A18PZTAG")
      (libsource (lib "eagle-import") (part "NTLUS4C12NTAG"))
    )
    (comp (ref "M12")
      (value "NTLUS4C12NTAG")
      (footprint "eagle-import:TRANS_NTLUS3A18PZTAG")
      (libsource (lib "eagle-import") (part "NTLUS4C12NTAG"))
    )
    (comp (ref "M13")
      (value "NTLUS4C12NTAG")
      (footprint "eagle-import:TRANS_NTLUS3A18PZTAG")
      (libsource (lib "eagle-import") (part "NTLUS4C12NTAG"))
    )
    (comp (ref "M14")
      (value "NTLUS4C12NTAG")
      (footprint "eagle-import:TRANS_NTLUS3A18PZTAG")
      (libsource (lib "eagle-import") (part "NTLUS4C12NTAG"))
    )
    (comp (ref "M15")
      (value "NTLUS4C12NTAG")
      (footprint "eagle-import:TRANS_NTLUS3A18PZTAG")
      (libsource (lib "eagle-import") (part "NTLUS4C12NTAG"))
    )
    (comp (ref "M16")
      (value "NTLUS4C12NTAG")
      (footprint "eagle-import:TRANS_NTLUS3A18PZTAG")
      (libsource (lib "eagle-import") (part "NTLUS4C12NTAG"))
    )
    (comp (ref "M17")
      (value "NTLUS4C12NTAG")
      (footprint "eagle-import:TRANS_NTLUS3A18PZTAG")
      (libsource (lib "eagle-import") (part "NTLUS4C12NTAG"))
    )
    (comp (ref "M18")
      (value "NTLUS4C12NTAG")
      (footprint "eagle-import:TRANS_NTLUS3A18PZTAG")
      (libsource (lib "eagle-import") (part "NTLUS4C12NTAG"))
    )
    (comp (ref "M19")
      (value "NTLUS4C12NTAG")
      (footprint "eagle-import:TRANS_NTLUS3A18PZTAG")
      (libsource (lib "eagle-import") (part "NTLUS4C12NTAG"))
    )
    (comp (ref "M20")
      (value "NTLUS4C12NTAG")
      (footprint "eagle-import:TRANS_NTLUS3A18PZTAG")
      (libsource (lib "eagle-import") (part "NTLUS4C12NTAG"))
    )
    (comp (ref "M21")
      (value "NTLUS4C12NTAG")
      (footprint "eagle-import:TRANS_NTLUS3A18PZTAG")
      (libsource (lib "eagle-import") (part "NTLUS4C12NTAG"))
    )
    (comp (ref "M22")
      (value "NTLUS4C12NTAG")
      (footprint "eagle-import:TRANS_NTLUS3A18PZTAG")
      (libsource (lib "eagle-import") (part "NTLUS4C12NTAG"))
    )
    (comp (ref "M23")
      (value "NTLUS4C12NTAG")
      (footprint "eagle-import:TRANS_NTLUS3A18PZTAG")
      (libsource (lib "eagle-import") (part "NTLUS4C12NTAG"))
    )
    (comp (ref "M24")
      (value "NTLUS4C12NTAG")
      (footprint "eagle-import:TRANS_NTLUS3A18PZTAG")
      (libsource (lib "eagle-import") (part "NTLUS4C12NTAG"))
    )
    (comp (ref "M25")
      (value "NTLUS4C12NTAG")
      (footprint "eagle-import:TRANS_NTLUS3A18PZTAG")
      (libsource (lib "eagle-import") (part "NTLUS4C12NTAG"))
    )
    (comp (ref "M26")
      (value "NTLUS4C12NTAG")
      (footprint "eagle-import:TRANS_NTLUS3A18PZTAG")
      (libsource (lib "eagle-import") (part "NTLUS4C12NTAG"))
    )
    (comp (ref "M27")
      (value "NTLUS4C12NTAG")
      (footprint "eagle-import:TRANS_NTLUS3A18PZTAG")
      (libsource (lib "eagle-import") (part "NTLUS4C12NTAG"))
    )
    (comp (ref "M28")
      (value "NTLUS4C12NTAG")
      (footprint "eagle-import:TRANS_NTLUS3A18PZTAG")
      (libsource (lib "eagle-import") (part "NTLUS4C12NTAG"))
    )
    (comp (ref "R57")
      (value "ERJ-PA3D1400V")
      (footprint "eagle-import:ERJP03_PA3_(0603)")
      (libsource (lib "eagle-import") (part "ERJ-PA3D1400V"))
    )
    (comp (ref "R58")
      (value "ERJ-PA3D1400V")
      (footprint "eagle-import:ERJP03_PA3_(0603)")
      (libsource (lib "eagle-import") (part "ERJ-PA3D1400V"))
    )
    (comp (ref "R65")
      (value "ERJ-PA3D1400V")
      (footprint "eagle-import:ERJP03_PA3_(0603)")
      (libsource (lib "eagle-import") (part "ERJ-PA3D1400V"))
    )
    (comp (ref "R66")
      (value "ERJ-PA3D1400V")
      (footprint "eagle-import:ERJP03_PA3_(0603)")
      (libsource (lib "eagle-import") (part "ERJ-PA3D1400V"))
    )
    (comp (ref "R67")
      (value "ERJ-PA3D1400V")
      (footprint "eagle-import:ERJP03_PA3_(0603)")
      (libsource (lib "eagle-import") (part "ERJ-PA3D1400V"))
    )
    (comp (ref "R68")
      (value "ERJ-PA3D1400V")
      (footprint "eagle-import:ERJP03_PA3_(0603)")
      (libsource (lib "eagle-import") (part "ERJ-PA3D1400V"))
    )
    (comp (ref "R69")
      (value "ERJ-PA3D1400V")
      (footprint "eagle-import:ERJP03_PA3_(0603)")
      (libsource (lib "eagle-import") (part "ERJ-PA3D1400V"))
    )
    (comp (ref "R70")
      (value "ERJ-PA3D1400V")
      (footprint "eagle-import:ERJP03_PA3_(0603)")
      (libsource (lib "eagle-import") (part "ERJ-PA3D1400V"))
    )
    (comp (ref "R71")
      (value "ERJ-PA3D1400V")
      (footprint "eagle-import:ERJP03_PA3_(0603)")
      (libsource (lib "eagle-import") (part "ERJ-PA3D1400V"))
    )
    (comp (ref "R72")
      (value "ERJ-PA3D1400V")
      (footprint "eagle-import:ERJP03_PA3_(0603)")
      (libsource (lib "eagle-import") (part "ERJ-PA3D1400V"))
    )
    (comp (ref "R89")
      (value "CRCW040212K0FKTD")
      (footprint "eagle-import:RESC1005X40N")
      (fields (field (name "MOUSER_PART_NUMBER") "71-CRCW0402-12K"))
      (libsource (lib "eagle-import") (part "CRCW040212K0FKTD"))
    )
    (comp (ref "R90")
      (value "CRCW0402510RFKEDC")
      (footprint "eagle-import:RESC1005X35N")
      (fields (field (name "MOUSER_PART_NUMBER") "71-CRCW0402510RFKEDC"))
      (libsource (lib "eagle-import") (part "CRCW0402510RFKEDC"))
    )
    (comp (ref "R91")
      (value "CRCW04021K05FKED")
      (footprint "eagle-import:RESC1005X40N")
      (fields (field (name "MOUSER_PART_NUMBER") "71-CRCW04021K05FKED"))
      (libsource (lib "eagle-import") (part "CRCW04021K05FKED"))
    )
    (comp (ref "R92")
      (value "ERJ-2BWFR050X")
      (footprint "eagle-import:ERJ_2LW_2BW_2B_(0402)")
      (fields (field (name "MOUSER_PART_NUMBER") "667-ERJ-2BWFR050X"))
      (libsource (lib "eagle-import") (part "ERJ-2BWFR050X"))
    )
    (comp (ref "R93")
      (value "ESR01MZPJ100")
      (footprint "eagle-import:RESC1005X40N")
      (fields (field (name "MOUSER_PART_NUMBER") "755-ESR01MZPJ100"))
      (libsource (lib "eagle-import") (part "ESR01MZPJ100"))
    )
    (comp (ref "R94")
      (value "RC0402JR-1015KL")
      (footprint "eagle-import:RESC1005X40N")
      (fields (field (name "MOUSER_PART_NUMBER") "603-RC0402JR-1015KL"))
      (libsource (lib "eagle-import") (part "RC0402JR-1015KL"))
    )
    (comp (ref "R95")
      (value "CR0402-FX-1022GLF")
      (footprint "eagle-import:RESC1005X40N")
      (fields (field (name "MOUSER_PART_NUMBER") "652-CR0402-FX1022GLF"))
      (libsource (lib "eagle-import") (part "CR0402-FX-1022GLF"))
    )
    (comp (ref "R96")
      (value "RC0402JR-133K3L")
      (footprint "eagle-import:RESC1005X40N")
      (fields (field (name "MOUSER_PART_NUMBER") "603-RC0402JR-133K3L"))
      (libsource (lib "eagle-import") (part "RC0402JR-133K3L"))
    )
    (comp (ref "R97")
      (value "ERJ-2RKF2002X")
      (footprint "eagle-import:ERJ2R_(0402)")
      (fields (field (name "MOUSER_PART_NUMBER") "667-ERJ-2RKF2002X"))
      (libsource (lib "eagle-import") (part "ERJ-2RKF2002X"))
    )
    (comp (ref "R99")
      (value "ERJ-2RKF2002X")
      (footprint "eagle-import:ERJ2R_(0402)")
      (fields (field (name "MOUSER_PART_NUMBER") "667-ERJ-2RKF2002X"))
      (libsource (lib "eagle-import") (part "ERJ-2RKF2002X"))
    )
    (comp (ref "R100")
      (value "ERJ-2RKF2002X")
      (footprint "eagle-import:ERJ2R_(0402)")
      (fields (field (name "MOUSER_PART_NUMBER") "667-ERJ-2RKF2002X"))
      (libsource (lib "eagle-import") (part "ERJ-2RKF2002X"))
    )
    (comp (ref "R101")
      (value "CRCW040212K0FKTD")
      (footprint "eagle-import:RESC1005X40N")
      (fields (field (name "MOUSER_PART_NUMBER") "71-CRCW0402-12K"))
      (libsource (lib "eagle-import") (part "CRCW040212K0FKTD"))
    )
    (comp (ref "R117")
      (value "ERJ-PA3D1400V")
      (footprint "eagle-import:ERJP03_PA3_(0603)")
      (libsource (lib "eagle-import") (part "ERJ-PA3D1400V"))
    )
    (comp (ref "R118")
      (value "ERJ-PA3D1400V")
      (footprint "eagle-import:ERJP03_PA3_(0603)")
      (libsource (lib "eagle-import") (part "ERJ-PA3D1400V"))
    )
    (comp (ref "R119")
      (value "ERJ-PA3D1400V")
      (footprint "eagle-import:ERJP03_PA3_(0603)")
      (libsource (lib "eagle-import") (part "ERJ-PA3D1400V"))
    )
    (comp (ref "R120")
      (value "ERJ-PA3D1400V")
      (footprint "eagle-import:ERJP03_PA3_(0603)")
      (libsource (lib "eagle-import") (part "ERJ-PA3D1400V"))
    )
    (comp (ref "R121")
      (value "ERJ-PA3D1400V")
      (footprint "eagle-import:ERJP03_PA3_(0603)")
      (libsource (lib "eagle-import") (part "ERJ-PA3D1400V"))
    )
    (comp (ref "R122")
      (value "ERJ-PA3D1400V")
      (footprint "eagle-import:ERJP03_PA3_(0603)")
      (libsource (lib "eagle-import") (part "ERJ-PA3D1400V"))
    )
    (comp (ref "R123")
      (value "ERJ-PA3D1400V")
      (footprint "eagle-import:ERJP03_PA3_(0603)")
      (libsource (lib "eagle-import") (part "ERJ-PA3D1400V"))
    )
    (comp (ref "R124")
      (value "ERJ-PA3D1400V")
      (footprint "eagle-import:ERJP03_PA3_(0603)")
      (libsource (lib "eagle-import") (part "ERJ-PA3D1400V"))
    )
    (comp (ref "R127")
      (value "CRCW0402510RFKEDC")
      (footprint "eagle-import:RESC1005X35N")
      (fields (field (name "MOUSER_PART_NUMBER") "71-CRCW0402510RFKEDC"))
      (libsource (lib "eagle-import") (part "CRCW0402510RFKEDC"))
    )
    (comp (ref "R128")
      (value "CRCW04021K05FKED")
      (footprint "eagle-import:RESC1005X40N")
      (fields (field (name "MOUSER_PART_NUMBER") "71-CRCW04021K05FKED"))
      (libsource (lib "eagle-import") (part "CRCW04021K05FKED"))
    )
    (comp (ref "R129")
      (value "ERJ-2BWFR050X")
      (footprint "eagle-import:ERJ_2LW_2BW_2B_(0402)")
      (fields (field (name "MOUSER_PART_NUMBER") "667-ERJ-2BWFR050X"))
      (libsource (lib "eagle-import") (part "ERJ-2BWFR050X"))
    )
    (comp (ref "R130")
      (value "ESR01MZPJ100")
      (footprint "eagle-import:RESC1005X40N")
      (fields (field (name "MOUSER_PART_NUMBER") "755-ESR01MZPJ100"))
      (libsource (lib "eagle-import") (part "ESR01MZPJ100"))
    )
    (comp (ref "R131")
      (value "RC0402JR-1015KL")
      (footprint "eagle-import:RESC1005X40N")
      (fields (field (name "MOUSER_PART_NUMBER") "603-RC0402JR-1015KL"))
      (libsource (lib "eagle-import") (part "RC0402JR-1015KL"))
    )
    (comp (ref "R132")
      (value "CR0402-FX-1022GLF")
      (footprint "eagle-import:RESC1005X40N")
      (fields (field (name "MOUSER_PART_NUMBER") "652-CR0402-FX1022GLF"))
      (libsource (lib "eagle-import") (part "CR0402-FX-1022GLF"))
    )
    (comp (ref "R133")
      (value "RC0402JR-133K3L")
      (footprint "eagle-import:RESC1005X40N")
      (fields (field (name "MOUSER_PART_NUMBER") "603-RC0402JR-133K3L"))
      (libsource (lib "eagle-import") (part "RC0402JR-133K3L"))
    )
    (comp (ref "R134")
      (value "ERJ-2RKF2002X")
      (footprint "eagle-import:ERJ2R_(0402)")
      (fields (field (name "MOUSER_PART_NUMBER") "667-ERJ-2RKF2002X"))
      (libsource (lib "eagle-import") (part "ERJ-2RKF2002X"))
    )
    (comp (ref "R135")
      (value "ERJ-2RKF2002X")
      (footprint "eagle-import:ERJ2R_(0402)")
      (fields (field (name "MOUSER_PART_NUMBER") "667-ERJ-2RKF2002X"))
      (libsource (lib "eagle-import") (part "ERJ-2RKF2002X"))
    )
    (comp (ref "R136")
      (value "CRCW040212K0FKTD")
      (footprint "eagle-import:RESC1005X40N")
      (fields (field (name "MOUSER_PART_NUMBER") "71-CRCW0402-12K"))
      (libsource (lib "eagle-import") (part "CRCW040212K0FKTD"))
    )
    (comp (ref "R137")
      (value "CRCW0402510RFKEDC")
      (footprint "eagle-import:RESC1005X35N")
      (fields (field (name "MOUSER_PART_NUMBER") "71-CRCW0402510RFKEDC"))
      (libsource (lib "eagle-import") (part "CRCW0402510RFKEDC"))
    )
    (comp (ref "R138")
      (value "CRCW04021K05FKED")
      (footprint "eagle-import:RESC1005X40N")
      (fields (field (name "MOUSER_PART_NUMBER") "71-CRCW04021K05FKED"))
      (libsource (lib "eagle-import") (part "CRCW04021K05FKED"))
    )
    (comp (ref "R139")
      (value "ERJ-2BWFR050X")
      (footprint "eagle-import:ERJ_2LW_2BW_2B_(0402)")
      (fields (field (name "MOUSER_PART_NUMBER") "667-ERJ-2BWFR050X"))
      (libsource (lib "eagle-import") (part "ERJ-2BWFR050X"))
    )
    (comp (ref "R140")
      (value "ESR01MZPJ100")
      (footprint "eagle-import:RESC1005X40N")
      (fields (field (name "MOUSER_PART_NUMBER") "755-ESR01MZPJ100"))
      (libsource (lib "eagle-import") (part "ESR01MZPJ100"))
    )
    (comp (ref "R141")
      (value "RC0402JR-1015KL")
      (footprint "eagle-import:RESC1005X40N")
      (fields (field (name "MOUSER_PART_NUMBER") "603-RC0402JR-1015KL"))
      (libsource (lib "eagle-import") (part "RC0402JR-1015KL"))
    )
    (comp (ref "R142")
      (value "CR0402-FX-1022GLF")
      (footprint "eagle-import:RESC1005X40N")
      (fields (field (name "MOUSER_PART_NUMBER") "652-CR0402-FX1022GLF"))
      (libsource (lib "eagle-import") (part "CR0402-FX-1022GLF"))
    )
    (comp (ref "R143")
      (value "RC0402JR-133K3L")
      (footprint "eagle-import:RESC1005X40N")
      (fields (field (name "MOUSER_PART_NUMBER") "603-RC0402JR-133K3L"))
      (libsource (lib "eagle-import") (part "RC0402JR-133K3L"))
    )
    (comp (ref "R144")
      (value "ERJ-2RKF2002X")
      (footprint "eagle-import:ERJ2R_(0402)")
      (fields (field (name "MOUSER_PART_NUMBER") "667-ERJ-2RKF2002X"))
      (libsource (lib "eagle-import") (part "ERJ-2RKF2002X"))
    )
    (comp (ref "R145")
      (value "ERJ-2RKF2002X")
      (footprint "eagle-import:ERJ2R_(0402)")
      (fields (field (name "MOUSER_PART_NUMBER") "667-ERJ-2RKF2002X"))
      (libsource (lib "eagle-import") (part "ERJ-2RKF2002X"))
    )
    (comp (ref "R146")
      (value "ERJ-2RKF2002X")
      (footprint "eagle-import:ERJ2R_(0402)")
      (fields (field (name "MOUSER_PART_NUMBER") "667-ERJ-2RKF2002X"))
      (libsource (lib "eagle-import") (part "ERJ-2RKF2002X"))
    )
    (comp (ref "R147")
      (value "CRCW04021K30FKTD")
      (footprint "eagle-import:RESC1005X40N")
      (fields (field (name "MOUSER_PART_NUMBER") "71-CRCW0402-1.3K"))
      (libsource (lib "eagle-import") (part "CRCW04021K30FKTD"))
    )
    (comp (ref "R148")
      (value "CRCW04021K30FKTD")
      (footprint "eagle-import:RESC1005X40N")
      (fields (field (name "MOUSER_PART_NUMBER") "71-CRCW0402-1.3K"))
      (libsource (lib "eagle-import") (part "CRCW04021K30FKTD"))
    )
    (comp (ref "R149")
      (value "CRCW04021K30FKTD")
      (footprint "eagle-import:RESC1005X40N")
      (fields (field (name "MOUSER_PART_NUMBER") "71-CRCW0402-1.3K"))
      (libsource (lib "eagle-import") (part "CRCW04021K30FKTD"))
    )
    (comp (ref "R150")
      (value "CRCW04021K30FKTD")
      (footprint "eagle-import:RESC1005X40N")
      (fields (field (name "MOUSER_PART_NUMBER") "71-CRCW0402-1.3K"))
      (libsource (lib "eagle-import") (part "CRCW04021K30FKTD"))
    )
    (comp (ref "R164")
      (value "CRCW040212K0FKTD")
      (footprint "eagle-import:RESC1005X40N")
      (fields (field (name "MOUSER_PART_NUMBER") "71-CRCW0402-12K"))
      (libsource (lib "eagle-import") (part "CRCW040212K0FKTD"))
    )
    (comp (ref "R165")
      (value "CRCW0402510RFKEDC")
      (footprint "eagle-import:RESC1005X35N")
      (fields (field (name "MOUSER_PART_NUMBER") "71-CRCW0402510RFKEDC"))
      (libsource (lib "eagle-import") (part "CRCW0402510RFKEDC"))
    )
    (comp (ref "R166")
      (value "CRCW04021K05FKED")
      (footprint "eagle-import:RESC1005X40N")
      (fields (field (name "MOUSER_PART_NUMBER") "71-CRCW04021K05FKED"))
      (libsource (lib "eagle-import") (part "CRCW04021K05FKED"))
    )
    (comp (ref "R167")
      (value "ERJ-2BWFR050X")
      (footprint "eagle-import:ERJ_2LW_2BW_2B_(0402)")
      (fields (field (name "MOUSER_PART_NUMBER") "667-ERJ-2BWFR050X"))
      (libsource (lib "eagle-import") (part "ERJ-2BWFR050X"))
    )
    (comp (ref "R168")
      (value "ESR01MZPJ100")
      (footprint "eagle-import:RESC1005X40N")
      (fields (field (name "MOUSER_PART_NUMBER") "755-ESR01MZPJ100"))
      (libsource (lib "eagle-import") (part "ESR01MZPJ100"))
    )
    (comp (ref "R169")
      (value "RC0402JR-1015KL")
      (footprint "eagle-import:RESC1005X40N")
      (fields (field (name "MOUSER_PART_NUMBER") "603-RC0402JR-1015KL"))
      (libsource (lib "eagle-import") (part "RC0402JR-1015KL"))
    )
    (comp (ref "R170")
      (value "CR0402-FX-1022GLF")
      (footprint "eagle-import:RESC1005X40N")
      (fields (field (name "MOUSER_PART_NUMBER") "652-CR0402-FX1022GLF"))
      (libsource (lib "eagle-import") (part "CR0402-FX-1022GLF"))
    )
    (comp (ref "R171")
      (value "RC0402JR-133K3L")
      (footprint "eagle-import:RESC1005X40N")
      (fields (field (name "MOUSER_PART_NUMBER") "603-RC0402JR-133K3L"))
      (libsource (lib "eagle-import") (part "RC0402JR-133K3L"))
    )
    (comp (ref "R172")
      (value "ERJ-2RKF2002X")
      (footprint "eagle-import:ERJ2R_(0402)")
      (fields (field (name "MOUSER_PART_NUMBER") "667-ERJ-2RKF2002X"))
      (libsource (lib "eagle-import") (part "ERJ-2RKF2002X"))
    )
    (comp (ref "R173")
      (value "ERJ-2RKF2002X")
      (footprint "eagle-import:ERJ2R_(0402)")
      (fields (field (name "MOUSER_PART_NUMBER") "667-ERJ-2RKF2002X"))
      (libsource (lib "eagle-import") (part "ERJ-2RKF2002X"))
    )
    (comp (ref "R174")
      (value "CRCW040212K0FKTD")
      (footprint "eagle-import:RESC1005X40N")
      (fields (field (name "MOUSER_PART_NUMBER") "71-CRCW0402-12K"))
      (libsource (lib "eagle-import") (part "CRCW040212K0FKTD"))
    )
    (comp (ref "R175")
      (value "CRCW0402510RFKEDC")
      (footprint "eagle-import:RESC1005X35N")
      (fields (field (name "MOUSER_PART_NUMBER") "71-CRCW0402510RFKEDC"))
      (libsource (lib "eagle-import") (part "CRCW0402510RFKEDC"))
    )
    (comp (ref "R176")
      (value "CRCW04021K05FKED")
      (footprint "eagle-import:RESC1005X40N")
      (fields (field (name "MOUSER_PART_NUMBER") "71-CRCW04021K05FKED"))
      (libsource (lib "eagle-import") (part "CRCW04021K05FKED"))
    )
    (comp (ref "R177")
      (value "ERJ-2BWFR050X")
      (footprint "eagle-import:ERJ_2LW_2BW_2B_(0402)")
      (fields (field (name "MOUSER_PART_NUMBER") "667-ERJ-2BWFR050X"))
      (libsource (lib "eagle-import") (part "ERJ-2BWFR050X"))
    )
    (comp (ref "R178")
      (value "ESR01MZPJ100")
      (footprint "eagle-import:RESC1005X40N")
      (fields (field (name "MOUSER_PART_NUMBER") "755-ESR01MZPJ100"))
      (libsource (lib "eagle-import") (part "ESR01MZPJ100"))
    )
    (comp (ref "R179")
      (value "RC0402JR-1015KL")
      (footprint "eagle-import:RESC1005X40N")
      (fields (field (name "MOUSER_PART_NUMBER") "603-RC0402JR-1015KL"))
      (libsource (lib "eagle-import") (part "RC0402JR-1015KL"))
    )
    (comp (ref "R180")
      (value "CR0402-FX-1022GLF")
      (footprint "eagle-import:RESC1005X40N")
      (fields (field (name "MOUSER_PART_NUMBER") "652-CR0402-FX1022GLF"))
      (libsource (lib "eagle-import") (part "CR0402-FX-1022GLF"))
    )
    (comp (ref "R181")
      (value "RC0402JR-133K3L")
      (footprint "eagle-import:RESC1005X40N")
      (fields (field (name "MOUSER_PART_NUMBER") "603-RC0402JR-133K3L"))
      (libsource (lib "eagle-import") (part "RC0402JR-133K3L"))
    )
    (comp (ref "R182")
      (value "ERJ-2RKF2002X")
      (footprint "eagle-import:ERJ2R_(0402)")
      (fields (field (name "MOUSER_PART_NUMBER") "667-ERJ-2RKF2002X"))
      (libsource (lib "eagle-import") (part "ERJ-2RKF2002X"))
    )
    (comp (ref "R183")
      (value "ERJ-2RKF2002X")
      (footprint "eagle-import:ERJ2R_(0402)")
      (fields (field (name "MOUSER_PART_NUMBER") "667-ERJ-2RKF2002X"))
      (libsource (lib "eagle-import") (part "ERJ-2RKF2002X"))
    )
    (comp (ref "R184")
      (value "ERJ-2RKF2002X")
      (footprint "eagle-import:ERJ2R_(0402)")
      (fields (field (name "MOUSER_PART_NUMBER") "667-ERJ-2RKF2002X"))
      (libsource (lib "eagle-import") (part "ERJ-2RKF2002X"))
    )
    (comp (ref "R185")
      (value "CRCW040212K0FKTD")
      (footprint "eagle-import:RESC1005X40N")
      (fields (field (name "MOUSER_PART_NUMBER") "71-CRCW0402-12K"))
      (libsource (lib "eagle-import") (part "CRCW040212K0FKTD"))
    )
    (comp (ref "R186")
      (value "CRCW0402510RFKEDC")
      (footprint "eagle-import:RESC1005X35N")
      (fields (field (name "MOUSER_PART_NUMBER") "71-CRCW0402510RFKEDC"))
      (libsource (lib "eagle-import") (part "CRCW0402510RFKEDC"))
    )
    (comp (ref "R187")
      (value "CRCW04021K05FKED")
      (footprint "eagle-import:RESC1005X40N")
      (fields (field (name "MOUSER_PART_NUMBER") "71-CRCW04021K05FKED"))
      (libsource (lib "eagle-import") (part "CRCW04021K05FKED"))
    )
    (comp (ref "R188")
      (value "ERJ-2BWFR050X")
      (footprint "eagle-import:ERJ_2LW_2BW_2B_(0402)")
      (fields (field (name "MOUSER_PART_NUMBER") "667-ERJ-2BWFR050X"))
      (libsource (lib "eagle-import") (part "ERJ-2BWFR050X"))
    )
    (comp (ref "R189")
      (value "ESR01MZPJ100")
      (footprint "eagle-import:RESC1005X40N")
      (fields (field (name "MOUSER_PART_NUMBER") "755-ESR01MZPJ100"))
      (libsource (lib "eagle-import") (part "ESR01MZPJ100"))
    )
    (comp (ref "R190")
      (value "RC0402JR-1015KL")
      (footprint "eagle-import:RESC1005X40N")
      (fields (field (name "MOUSER_PART_NUMBER") "603-RC0402JR-1015KL"))
      (libsource (lib "eagle-import") (part "RC0402JR-1015KL"))
    )
    (comp (ref "R191")
      (value "CR0402-FX-1022GLF")
      (footprint "eagle-import:RESC1005X40N")
      (fields (field (name "MOUSER_PART_NUMBER") "652-CR0402-FX1022GLF"))
      (libsource (lib "eagle-import") (part "CR0402-FX-1022GLF"))
    )
    (comp (ref "R192")
      (value "RC0402JR-133K3L")
      (footprint "eagle-import:RESC1005X40N")
      (fields (field (name "MOUSER_PART_NUMBER") "603-RC0402JR-133K3L"))
      (libsource (lib "eagle-import") (part "RC0402JR-133K3L"))
    )
    (comp (ref "R193")
      (value "ERJ-2RKF2002X")
      (footprint "eagle-import:ERJ2R_(0402)")
      (fields (field (name "MOUSER_PART_NUMBER") "667-ERJ-2RKF2002X"))
      (libsource (lib "eagle-import") (part "ERJ-2RKF2002X"))
    )
    (comp (ref "R194")
      (value "ERJ-2RKF2002X")
      (footprint "eagle-import:ERJ2R_(0402)")
      (fields (field (name "MOUSER_PART_NUMBER") "667-ERJ-2RKF2002X"))
      (libsource (lib "eagle-import") (part "ERJ-2RKF2002X"))
    )
    (comp (ref "R195")
      (value "CRCW040212K0FKTD")
      (footprint "eagle-import:RESC1005X40N")
      (fields (field (name "MOUSER_PART_NUMBER") "71-CRCW0402-12K"))
      (libsource (lib "eagle-import") (part "CRCW040212K0FKTD"))
    )
    (comp (ref "R196")
      (value "CRCW0402510RFKEDC")
      (footprint "eagle-import:RESC1005X35N")
      (fields (field (name "MOUSER_PART_NUMBER") "71-CRCW0402510RFKEDC"))
      (libsource (lib "eagle-import") (part "CRCW0402510RFKEDC"))
    )
    (comp (ref "R197")
      (value "CRCW04021K05FKED")
      (footprint "eagle-import:RESC1005X40N")
      (fields (field (name "MOUSER_PART_NUMBER") "71-CRCW04021K05FKED"))
      (libsource (lib "eagle-import") (part "CRCW04021K05FKED"))
    )
    (comp (ref "R198")
      (value "ERJ-2BWFR050X")
      (footprint "eagle-import:ERJ_2LW_2BW_2B_(0402)")
      (fields (field (name "MOUSER_PART_NUMBER") "667-ERJ-2BWFR050X"))
      (libsource (lib "eagle-import") (part "ERJ-2BWFR050X"))
    )
    (comp (ref "R199")
      (value "ESR01MZPJ100")
      (footprint "eagle-import:RESC1005X40N")
      (fields (field (name "MOUSER_PART_NUMBER") "755-ESR01MZPJ100"))
      (libsource (lib "eagle-import") (part "ESR01MZPJ100"))
    )
    (comp (ref "R200")
      (value "RC0402JR-1015KL")
      (footprint "eagle-import:RESC1005X40N")
      (fields (field (name "MOUSER_PART_NUMBER") "603-RC0402JR-1015KL"))
      (libsource (lib "eagle-import") (part "RC0402JR-1015KL"))
    )
    (comp (ref "R202")
      (value "CR0402-FX-1022GLF")
      (footprint "eagle-import:RESC1005X40N")
      (fields (field (name "MOUSER_PART_NUMBER") "652-CR0402-FX1022GLF"))
      (libsource (lib "eagle-import") (part "CR0402-FX-1022GLF"))
    )
    (comp (ref "R204")
      (value "RC0402JR-133K3L")
      (footprint "eagle-import:RESC1005X40N")
      (fields (field (name "MOUSER_PART_NUMBER") "603-RC0402JR-133K3L"))
      (libsource (lib "eagle-import") (part "RC0402JR-133K3L"))
    )
    (comp (ref "R206")
      (value "ERJ-2RKF2002X")
      (footprint "eagle-import:ERJ2R_(0402)")
      (fields (field (name "MOUSER_PART_NUMBER") "667-ERJ-2RKF2002X"))
      (libsource (lib "eagle-import") (part "ERJ-2RKF2002X"))
    )
    (comp (ref "R208")
      (value "ERJ-2RKF2002X")
      (footprint "eagle-import:ERJ2R_(0402)")
      (fields (field (name "MOUSER_PART_NUMBER") "667-ERJ-2RKF2002X"))
      (libsource (lib "eagle-import") (part "ERJ-2RKF2002X"))
    )
    (comp (ref "R210")
      (value "ERJ-2RKF2002X")
      (footprint "eagle-import:ERJ2R_(0402)")
      (fields (field (name "MOUSER_PART_NUMBER") "667-ERJ-2RKF2002X"))
      (libsource (lib "eagle-import") (part "ERJ-2RKF2002X"))
    )
    (comp (ref "R212")
      (value "CRCW040212K0FKTD")
      (footprint "eagle-import:RESC1005X40N")
      (fields (field (name "MOUSER_PART_NUMBER") "71-CRCW0402-12K"))
      (libsource (lib "eagle-import") (part "CRCW040212K0FKTD"))
    )
    (comp (ref "R213")
      (value "CRCW0402510RFKEDC")
      (footprint "eagle-import:RESC1005X35N")
      (fields (field (name "MOUSER_PART_NUMBER") "71-CRCW0402510RFKEDC"))
      (libsource (lib "eagle-import") (part "CRCW0402510RFKEDC"))
    )
    (comp (ref "R214")
      (value "CRCW04021K05FKED")
      (footprint "eagle-import:RESC1005X40N")
      (fields (field (name "MOUSER_PART_NUMBER") "71-CRCW04021K05FKED"))
      (libsource (lib "eagle-import") (part "CRCW04021K05FKED"))
    )
    (comp (ref "R215")
      (value "ERJ-2BWFR050X")
      (footprint "eagle-import:ERJ_2LW_2BW_2B_(0402)")
      (fields (field (name "MOUSER_PART_NUMBER") "667-ERJ-2BWFR050X"))
      (libsource (lib "eagle-import") (part "ERJ-2BWFR050X"))
    )
    (comp (ref "R216")
      (value "ESR01MZPJ100")
      (footprint "eagle-import:RESC1005X40N")
      (fields (field (name "MOUSER_PART_NUMBER") "755-ESR01MZPJ100"))
      (libsource (lib "eagle-import") (part "ESR01MZPJ100"))
    )
    (comp (ref "R217")
      (value "RC0402JR-1015KL")
      (footprint "eagle-import:RESC1005X40N")
      (fields (field (name "MOUSER_PART_NUMBER") "603-RC0402JR-1015KL"))
      (libsource (lib "eagle-import") (part "RC0402JR-1015KL"))
    )
    (comp (ref "R218")
      (value "CR0402-FX-1022GLF")
      (footprint "eagle-import:RESC1005X40N")
      (fields (field (name "MOUSER_PART_NUMBER") "652-CR0402-FX1022GLF"))
      (libsource (lib "eagle-import") (part "CR0402-FX-1022GLF"))
    )
    (comp (ref "R219")
      (value "RC0402JR-133K3L")
      (footprint "eagle-import:RESC1005X40N")
      (fields (field (name "MOUSER_PART_NUMBER") "603-RC0402JR-133K3L"))
      (libsource (lib "eagle-import") (part "RC0402JR-133K3L"))
    )
    (comp (ref "R220")
      (value "ERJ-2RKF2002X")
      (footprint "eagle-import:ERJ2R_(0402)")
      (fields (field (name "MOUSER_PART_NUMBER") "667-ERJ-2RKF2002X"))
      (libsource (lib "eagle-import") (part "ERJ-2RKF2002X"))
    )
    (comp (ref "R222")
      (value "ERJ-2RKF2002X")
      (footprint "eagle-import:ERJ2R_(0402)")
      (fields (field (name "MOUSER_PART_NUMBER") "667-ERJ-2RKF2002X"))
      (libsource (lib "eagle-import") (part "ERJ-2RKF2002X"))
    )
    (comp (ref "R223")
      (value "CRCW040212K0FKTD")
      (footprint "eagle-import:RESC1005X40N")
      (fields (field (name "MOUSER_PART_NUMBER") "71-CRCW0402-12K"))
      (libsource (lib "eagle-import") (part "CRCW040212K0FKTD"))
    )
    (comp (ref "R224")
      (value "CRCW0402510RFKEDC")
      (footprint "eagle-import:RESC1005X35N")
      (fields (field (name "MOUSER_PART_NUMBER") "71-CRCW0402510RFKEDC"))
      (libsource (lib "eagle-import") (part "CRCW0402510RFKEDC"))
    )
    (comp (ref "R225")
      (value "CRCW04021K05FKED")
      (footprint "eagle-import:RESC1005X40N")
      (fields (field (name "MOUSER_PART_NUMBER") "71-CRCW04021K05FKED"))
      (libsource (lib "eagle-import") (part "CRCW04021K05FKED"))
    )
    (comp (ref "R226")
      (value "ERJ-2BWFR050X")
      (footprint "eagle-import:ERJ_2LW_2BW_2B_(0402)")
      (fields (field (name "MOUSER_PART_NUMBER") "667-ERJ-2BWFR050X"))
      (libsource (lib "eagle-import") (part "ERJ-2BWFR050X"))
    )
    (comp (ref "R228")
      (value "ESR01MZPJ100")
      (footprint "eagle-import:RESC1005X40N")
      (fields (field (name "MOUSER_PART_NUMBER") "755-ESR01MZPJ100"))
      (libsource (lib "eagle-import") (part "ESR01MZPJ100"))
    )
    (comp (ref "R240")
      (value "RC0402JR-1015KL")
      (footprint "eagle-import:RESC1005X40N")
      (fields (field (name "MOUSER_PART_NUMBER") "603-RC0402JR-1015KL"))
      (libsource (lib "eagle-import") (part "RC0402JR-1015KL"))
    )
    (comp (ref "R241")
      (value "CR0402-FX-1022GLF")
      (footprint "eagle-import:RESC1005X40N")
      (fields (field (name "MOUSER_PART_NUMBER") "652-CR0402-FX1022GLF"))
      (libsource (lib "eagle-import") (part "CR0402-FX-1022GLF"))
    )
    (comp (ref "R242")
      (value "RC0402JR-133K3L")
      (footprint "eagle-import:RESC1005X40N")
      (fields (field (name "MOUSER_PART_NUMBER") "603-RC0402JR-133K3L"))
      (libsource (lib "eagle-import") (part "RC0402JR-133K3L"))
    )
    (comp (ref "R243")
      (value "ERJ-2RKF2002X")
      (footprint "eagle-import:ERJ2R_(0402)")
      (fields (field (name "MOUSER_PART_NUMBER") "667-ERJ-2RKF2002X"))
      (libsource (lib "eagle-import") (part "ERJ-2RKF2002X"))
    )
    (comp (ref "R244")
      (value "ERJ-2RKF2002X")
      (footprint "eagle-import:ERJ2R_(0402)")
      (fields (field (name "MOUSER_PART_NUMBER") "667-ERJ-2RKF2002X"))
      (libsource (lib "eagle-import") (part "ERJ-2RKF2002X"))
    )
    (comp (ref "R245")
      (value "ERJ-2RKF2002X")
      (footprint "eagle-import:ERJ2R_(0402)")
      (fields (field (name "MOUSER_PART_NUMBER") "667-ERJ-2RKF2002X"))
      (libsource (lib "eagle-import") (part "ERJ-2RKF2002X"))
    )
    (comp (ref "R246")
      (value "CRCW040212K0FKTD")
      (footprint "eagle-import:RESC1005X40N")
      (fields (field (name "MOUSER_PART_NUMBER") "71-CRCW0402-12K"))
      (libsource (lib "eagle-import") (part "CRCW040212K0FKTD"))
    )
    (comp (ref "R247")
      (value "CRCW0402510RFKEDC")
      (footprint "eagle-import:RESC1005X35N")
      (fields (field (name "MOUSER_PART_NUMBER") "71-CRCW0402510RFKEDC"))
      (libsource (lib "eagle-import") (part "CRCW0402510RFKEDC"))
    )
    (comp (ref "R248")
      (value "CRCW04021K05FKED")
      (footprint "eagle-import:RESC1005X40N")
      (fields (field (name "MOUSER_PART_NUMBER") "71-CRCW04021K05FKED"))
      (libsource (lib "eagle-import") (part "CRCW04021K05FKED"))
    )
    (comp (ref "R249")
      (value "ERJ-2BWFR050X")
      (footprint "eagle-import:ERJ_2LW_2BW_2B_(0402)")
      (fields (field (name "MOUSER_PART_NUMBER") "667-ERJ-2BWFR050X"))
      (libsource (lib "eagle-import") (part "ERJ-2BWFR050X"))
    )
    (comp (ref "R250")
      (value "ESR01MZPJ100")
      (footprint "eagle-import:RESC1005X40N")
      (fields (field (name "MOUSER_PART_NUMBER") "755-ESR01MZPJ100"))
      (libsource (lib "eagle-import") (part "ESR01MZPJ100"))
    )
    (comp (ref "R251")
      (value "RC0402JR-1015KL")
      (footprint "eagle-import:RESC1005X40N")
      (fields (field (name "MOUSER_PART_NUMBER") "603-RC0402JR-1015KL"))
      (libsource (lib "eagle-import") (part "RC0402JR-1015KL"))
    )
    (comp (ref "R252")
      (value "CR0402-FX-1022GLF")
      (footprint "eagle-import:RESC1005X40N")
      (fields (field (name "MOUSER_PART_NUMBER") "652-CR0402-FX1022GLF"))
      (libsource (lib "eagle-import") (part "CR0402-FX-1022GLF"))
    )
    (comp (ref "R253")
      (value "RC0402JR-133K3L")
      (footprint "eagle-import:RESC1005X40N")
      (fields (field (name "MOUSER_PART_NUMBER") "603-RC0402JR-133K3L"))
      (libsource (lib "eagle-import") (part "RC0402JR-133K3L"))
    )
    (comp (ref "R254")
      (value "ERJ-2RKF2002X")
      (footprint "eagle-import:ERJ2R_(0402)")
      (fields (field (name "MOUSER_PART_NUMBER") "667-ERJ-2RKF2002X"))
      (libsource (lib "eagle-import") (part "ERJ-2RKF2002X"))
    )
    (comp (ref "R255")
      (value "ERJ-2RKF2002X")
      (footprint "eagle-import:ERJ2R_(0402)")
      (fields (field (name "MOUSER_PART_NUMBER") "667-ERJ-2RKF2002X"))
      (libsource (lib "eagle-import") (part "ERJ-2RKF2002X"))
    )
    (comp (ref "R256")
      (value "CRCW040212K0FKTD")
      (footprint "eagle-import:RESC1005X40N")
      (fields (field (name "MOUSER_PART_NUMBER") "71-CRCW0402-12K"))
      (libsource (lib "eagle-import") (part "CRCW040212K0FKTD"))
    )
    (comp (ref "R257")
      (value "CRCW0402510RFKEDC")
      (footprint "eagle-import:RESC1005X35N")
      (fields (field (name "MOUSER_PART_NUMBER") "71-CRCW0402510RFKEDC"))
      (libsource (lib "eagle-import") (part "CRCW0402510RFKEDC"))
    )
    (comp (ref "R258")
      (value "CRCW04021K05FKED")
      (footprint "eagle-import:RESC1005X40N")
      (fields (field (name "MOUSER_PART_NUMBER") "71-CRCW04021K05FKED"))
      (libsource (lib "eagle-import") (part "CRCW04021K05FKED"))
    )
    (comp (ref "R259")
      (value "ERJ-2BWFR050X")
      (footprint "eagle-import:ERJ_2LW_2BW_2B_(0402)")
      (fields (field (name "MOUSER_PART_NUMBER") "667-ERJ-2BWFR050X"))
      (libsource (lib "eagle-import") (part "ERJ-2BWFR050X"))
    )
    (comp (ref "R260")
      (value "ESR01MZPJ100")
      (footprint "eagle-import:RESC1005X40N")
      (fields (field (name "MOUSER_PART_NUMBER") "755-ESR01MZPJ100"))
      (libsource (lib "eagle-import") (part "ESR01MZPJ100"))
    )
    (comp (ref "R261")
      (value "RC0402JR-1015KL")
      (footprint "eagle-import:RESC1005X40N")
      (fields (field (name "MOUSER_PART_NUMBER") "603-RC0402JR-1015KL"))
      (libsource (lib "eagle-import") (part "RC0402JR-1015KL"))
    )
    (comp (ref "R262")
      (value "CR0402-FX-1022GLF")
      (footprint "eagle-import:RESC1005X40N")
      (fields (field (name "MOUSER_PART_NUMBER") "652-CR0402-FX1022GLF"))
      (libsource (lib "eagle-import") (part "CR0402-FX-1022GLF"))
    )
    (comp (ref "R263")
      (value "RC0402JR-133K3L")
      (footprint "eagle-import:RESC1005X40N")
      (fields (field (name "MOUSER_PART_NUMBER") "603-RC0402JR-133K3L"))
      (libsource (lib "eagle-import") (part "RC0402JR-133K3L"))
    )
    (comp (ref "R264")
      (value "ERJ-2RKF2002X")
      (footprint "eagle-import:ERJ2R_(0402)")
      (fields (field (name "MOUSER_PART_NUMBER") "667-ERJ-2RKF2002X"))
      (libsource (lib "eagle-import") (part "ERJ-2RKF2002X"))
    )
    (comp (ref "R265")
      (value "ERJ-2RKF2002X")
      (footprint "eagle-import:ERJ2R_(0402)")
      (fields (field (name "MOUSER_PART_NUMBER") "667-ERJ-2RKF2002X"))
      (libsource (lib "eagle-import") (part "ERJ-2RKF2002X"))
    )
    (comp (ref "R266")
      (value "ERJ-2RKF2002X")
      (footprint "eagle-import:ERJ2R_(0402)")
      (fields (field (name "MOUSER_PART_NUMBER") "667-ERJ-2RKF2002X"))
      (libsource (lib "eagle-import") (part "ERJ-2RKF2002X"))
    )
    (comp (ref "R267")
      (value "CRCW040212K0FKTD")
      (footprint "eagle-import:RESC1005X40N")
      (fields (field (name "MOUSER_PART_NUMBER") "71-CRCW0402-12K"))
      (libsource (lib "eagle-import") (part "CRCW040212K0FKTD"))
    )
    (comp (ref "R268")
      (value "CRCW0402510RFKEDC")
      (footprint "eagle-import:RESC1005X35N")
      (fields (field (name "MOUSER_PART_NUMBER") "71-CRCW0402510RFKEDC"))
      (libsource (lib "eagle-import") (part "CRCW0402510RFKEDC"))
    )
    (comp (ref "R269")
      (value "CRCW04021K05FKED")
      (footprint "eagle-import:RESC1005X40N")
      (fields (field (name "MOUSER_PART_NUMBER") "71-CRCW04021K05FKED"))
      (libsource (lib "eagle-import") (part "CRCW04021K05FKED"))
    )
    (comp (ref "R270")
      (value "ERJ-2BWFR050X")
      (footprint "eagle-import:ERJ_2LW_2BW_2B_(0402)")
      (fields (field (name "MOUSER_PART_NUMBER") "667-ERJ-2BWFR050X"))
      (libsource (lib "eagle-import") (part "ERJ-2BWFR050X"))
    )
    (comp (ref "R271")
      (value "ESR01MZPJ100")
      (footprint "eagle-import:RESC1005X40N")
      (fields (field (name "MOUSER_PART_NUMBER") "755-ESR01MZPJ100"))
      (libsource (lib "eagle-import") (part "ESR01MZPJ100"))
    )
    (comp (ref "R272")
      (value "RC0402JR-1015KL")
      (footprint "eagle-import:RESC1005X40N")
      (fields (field (name "MOUSER_PART_NUMBER") "603-RC0402JR-1015KL"))
      (libsource (lib "eagle-import") (part "RC0402JR-1015KL"))
    )
    (comp (ref "R273")
      (value "CR0402-FX-1022GLF")
      (footprint "eagle-import:RESC1005X40N")
      (fields (field (name "MOUSER_PART_NUMBER") "652-CR0402-FX1022GLF"))
      (libsource (lib "eagle-import") (part "CR0402-FX-1022GLF"))
    )
    (comp (ref "R274")
      (value "RC0402JR-133K3L")
      (footprint "eagle-import:RESC1005X40N")
      (fields (field (name "MOUSER_PART_NUMBER") "603-RC0402JR-133K3L"))
      (libsource (lib "eagle-import") (part "RC0402JR-133K3L"))
    )
    (comp (ref "R275")
      (value "ERJ-2RKF2002X")
      (footprint "eagle-import:ERJ2R_(0402)")
      (fields (field (name "MOUSER_PART_NUMBER") "667-ERJ-2RKF2002X"))
      (libsource (lib "eagle-import") (part "ERJ-2RKF2002X"))
    )
    (comp (ref "R276")
      (value "ERJ-2RKF2002X")
      (footprint "eagle-import:ERJ2R_(0402)")
      (fields (field (name "MOUSER_PART_NUMBER") "667-ERJ-2RKF2002X"))
      (libsource (lib "eagle-import") (part "ERJ-2RKF2002X"))
    )
    (comp (ref "R277")
      (value "CRCW040212K0FKTD")
      (footprint "eagle-import:RESC1005X40N")
      (fields (field (name "MOUSER_PART_NUMBER") "71-CRCW0402-12K"))
      (libsource (lib "eagle-import") (part "CRCW040212K0FKTD"))
    )
    (comp (ref "R278")
      (value "CRCW0402510RFKEDC")
      (footprint "eagle-import:RESC1005X35N")
      (fields (field (name "MOUSER_PART_NUMBER") "71-CRCW0402510RFKEDC"))
      (libsource (lib "eagle-import") (part "CRCW0402510RFKEDC"))
    )
    (comp (ref "R279")
      (value "CRCW04021K05FKED")
      (footprint "eagle-import:RESC1005X40N")
      (fields (field (name "MOUSER_PART_NUMBER") "71-CRCW04021K05FKED"))
      (libsource (lib "eagle-import") (part "CRCW04021K05FKED"))
    )
    (comp (ref "R280")
      (value "ERJ-2BWFR050X")
      (footprint "eagle-import:ERJ_2LW_2BW_2B_(0402)")
      (fields (field (name "MOUSER_PART_NUMBER") "667-ERJ-2BWFR050X"))
      (libsource (lib "eagle-import") (part "ERJ-2BWFR050X"))
    )
    (comp (ref "R281")
      (value "ESR01MZPJ100")
      (footprint "eagle-import:RESC1005X40N")
      (fields (field (name "MOUSER_PART_NUMBER") "755-ESR01MZPJ100"))
      (libsource (lib "eagle-import") (part "ESR01MZPJ100"))
    )
    (comp (ref "R282")
      (value "RC0402JR-1015KL")
      (footprint "eagle-import:RESC1005X40N")
      (fields (field (name "MOUSER_PART_NUMBER") "603-RC0402JR-1015KL"))
      (libsource (lib "eagle-import") (part "RC0402JR-1015KL"))
    )
    (comp (ref "R283")
      (value "CR0402-FX-1022GLF")
      (footprint "eagle-import:RESC1005X40N")
      (fields (field (name "MOUSER_PART_NUMBER") "652-CR0402-FX1022GLF"))
      (libsource (lib "eagle-import") (part "CR0402-FX-1022GLF"))
    )
    (comp (ref "R284")
      (value "RC0402JR-133K3L")
      (footprint "eagle-import:RESC1005X40N")
      (fields (field (name "MOUSER_PART_NUMBER") "603-RC0402JR-133K3L"))
      (libsource (lib "eagle-import") (part "RC0402JR-133K3L"))
    )
    (comp (ref "R285")
      (value "ERJ-2RKF2002X")
      (footprint "eagle-import:ERJ2R_(0402)")
      (fields (field (name "MOUSER_PART_NUMBER") "667-ERJ-2RKF2002X"))
      (libsource (lib "eagle-import") (part "ERJ-2RKF2002X"))
    )
    (comp (ref "R286")
      (value "ERJ-2RKF2002X")
      (footprint "eagle-import:ERJ2R_(0402)")
      (fields (field (name "MOUSER_PART_NUMBER") "667-ERJ-2RKF2002X"))
      (libsource (lib "eagle-import") (part "ERJ-2RKF2002X"))
    )
    (comp (ref "R287")
      (value "ERJ-2RKF2002X")
      (footprint "eagle-import:ERJ2R_(0402)")
      (fields (field (name "MOUSER_PART_NUMBER") "667-ERJ-2RKF2002X"))
      (libsource (lib "eagle-import") (part "ERJ-2RKF2002X"))
    )
    (comp (ref "R288")
      (value "CRCW040212K0FKTD")
      (footprint "eagle-import:RESC1005X40N")
      (fields (field (name "MOUSER_PART_NUMBER") "71-CRCW0402-12K"))
      (libsource (lib "eagle-import") (part "CRCW040212K0FKTD"))
    )
    (comp (ref "R289")
      (value "CRCW0402510RFKEDC")
      (footprint "eagle-import:RESC1005X35N")
      (fields (field (name "MOUSER_PART_NUMBER") "71-CRCW0402510RFKEDC"))
      (libsource (lib "eagle-import") (part "CRCW0402510RFKEDC"))
    )
    (comp (ref "R290")
      (value "CRCW04021K05FKED")
      (footprint "eagle-import:RESC1005X40N")
      (fields (field (name "MOUSER_PART_NUMBER") "71-CRCW04021K05FKED"))
      (libsource (lib "eagle-import") (part "CRCW04021K05FKED"))
    )
    (comp (ref "R291")
      (value "ERJ-2BWFR050X")
      (footprint "eagle-import:ERJ_2LW_2BW_2B_(0402)")
      (fields (field (name "MOUSER_PART_NUMBER") "667-ERJ-2BWFR050X"))
      (libsource (lib "eagle-import") (part "ERJ-2BWFR050X"))
    )
    (comp (ref "R292")
      (value "ESR01MZPJ100")
      (footprint "eagle-import:RESC1005X40N")
      (fields (field (name "MOUSER_PART_NUMBER") "755-ESR01MZPJ100"))
      (libsource (lib "eagle-import") (part "ESR01MZPJ100"))
    )
    (comp (ref "R293")
      (value "RC0402JR-1015KL")
      (footprint "eagle-import:RESC1005X40N")
      (fields (field (name "MOUSER_PART_NUMBER") "603-RC0402JR-1015KL"))
      (libsource (lib "eagle-import") (part "RC0402JR-1015KL"))
    )
    (comp (ref "R294")
      (value "CR0402-FX-1022GLF")
      (footprint "eagle-import:RESC1005X40N")
      (fields (field (name "MOUSER_PART_NUMBER") "652-CR0402-FX1022GLF"))
      (libsource (lib "eagle-import") (part "CR0402-FX-1022GLF"))
    )
    (comp (ref "R295")
      (value "RC0402JR-133K3L")
      (footprint "eagle-import:RESC1005X40N")
      (fields (field (name "MOUSER_PART_NUMBER") "603-RC0402JR-133K3L"))
      (libsource (lib "eagle-import") (part "RC0402JR-133K3L"))
    )
    (comp (ref "R296")
      (value "ERJ-2RKF2002X")
      (footprint "eagle-import:ERJ2R_(0402)")
      (fields (field (name "MOUSER_PART_NUMBER") "667-ERJ-2RKF2002X"))
      (libsource (lib "eagle-import") (part "ERJ-2RKF2002X"))
    )
    (comp (ref "R297")
      (value "ERJ-2RKF2002X")
      (footprint "eagle-import:ERJ2R_(0402)")
      (fields (field (name "MOUSER_PART_NUMBER") "667-ERJ-2RKF2002X"))
      (libsource (lib "eagle-import") (part "ERJ-2RKF2002X"))
    )
    (comp (ref "R298")
      (value "CRCW040212K0FKTD")
      (footprint "eagle-import:RESC1005X40N")
      (fields (field (name "MOUSER_PART_NUMBER") "71-CRCW0402-12K"))
      (libsource (lib "eagle-import") (part "CRCW040212K0FKTD"))
    )
    (comp (ref "R299")
      (value "CRCW0402510RFKEDC")
      (footprint "eagle-import:RESC1005X35N")
      (fields (field (name "MOUSER_PART_NUMBER") "71-CRCW0402510RFKEDC"))
      (libsource (lib "eagle-import") (part "CRCW0402510RFKEDC"))
    )
    (comp (ref "R300")
      (value "CRCW04021K05FKED")
      (footprint "eagle-import:RESC1005X40N")
      (fields (field (name "MOUSER_PART_NUMBER") "71-CRCW04021K05FKED"))
      (libsource (lib "eagle-import") (part "CRCW04021K05FKED"))
    )
    (comp (ref "R301")
      (value "ERJ-2BWFR050X")
      (footprint "eagle-import:ERJ_2LW_2BW_2B_(0402)")
      (fields (field (name "MOUSER_PART_NUMBER") "667-ERJ-2BWFR050X"))
      (libsource (lib "eagle-import") (part "ERJ-2BWFR050X"))
    )
    (comp (ref "R302")
      (value "ESR01MZPJ100")
      (footprint "eagle-import:RESC1005X40N")
      (fields (field (name "MOUSER_PART_NUMBER") "755-ESR01MZPJ100"))
      (libsource (lib "eagle-import") (part "ESR01MZPJ100"))
    )
    (comp (ref "R303")
      (value "RC0402JR-1015KL")
      (footprint "eagle-import:RESC1005X40N")
      (fields (field (name "MOUSER_PART_NUMBER") "603-RC0402JR-1015KL"))
      (libsource (lib "eagle-import") (part "RC0402JR-1015KL"))
    )
    (comp (ref "R304")
      (value "CR0402-FX-1022GLF")
      (footprint "eagle-import:RESC1005X40N")
      (fields (field (name "MOUSER_PART_NUMBER") "652-CR0402-FX1022GLF"))
      (libsource (lib "eagle-import") (part "CR0402-FX-1022GLF"))
    )
    (comp (ref "R305")
      (value "RC0402JR-133K3L")
      (footprint "eagle-import:RESC1005X40N")
      (fields (field (name "MOUSER_PART_NUMBER") "603-RC0402JR-133K3L"))
      (libsource (lib "eagle-import") (part "RC0402JR-133K3L"))
    )
    (comp (ref "R306")
      (value "ERJ-2RKF2002X")
      (footprint "eagle-import:ERJ2R_(0402)")
      (fields (field (name "MOUSER_PART_NUMBER") "667-ERJ-2RKF2002X"))
      (libsource (lib "eagle-import") (part "ERJ-2RKF2002X"))
    )
    (comp (ref "R307")
      (value "ERJ-2RKF2002X")
      (footprint "eagle-import:ERJ2R_(0402)")
      (fields (field (name "MOUSER_PART_NUMBER") "667-ERJ-2RKF2002X"))
      (libsource (lib "eagle-import") (part "ERJ-2RKF2002X"))
    )
    (comp (ref "R308")
      (value "ERJ-2RKF2002X")
      (footprint "eagle-import:ERJ2R_(0402)")
      (fields (field (name "MOUSER_PART_NUMBER") "667-ERJ-2RKF2002X"))
      (libsource (lib "eagle-import") (part "ERJ-2RKF2002X"))
    )
    (comp (ref "R309")
      (value "CRCW040212K0FKTD")
      (footprint "eagle-import:RESC1005X40N")
      (fields (field (name "MOUSER_PART_NUMBER") "71-CRCW0402-12K"))
      (libsource (lib "eagle-import") (part "CRCW040212K0FKTD"))
    )
    (comp (ref "R310")
      (value "CRCW0402510RFKEDC")
      (footprint "eagle-import:RESC1005X35N")
      (fields (field (name "MOUSER_PART_NUMBER") "71-CRCW0402510RFKEDC"))
      (libsource (lib "eagle-import") (part "CRCW0402510RFKEDC"))
    )
    (comp (ref "R311")
      (value "CRCW04021K05FKED")
      (footprint "eagle-import:RESC1005X40N")
      (fields (field (name "MOUSER_PART_NUMBER") "71-CRCW04021K05FKED"))
      (libsource (lib "eagle-import") (part "CRCW04021K05FKED"))
    )
    (comp (ref "R312")
      (value "ERJ-2BWFR050X")
      (footprint "eagle-import:ERJ_2LW_2BW_2B_(0402)")
      (fields (field (name "MOUSER_PART_NUMBER") "667-ERJ-2BWFR050X"))
      (libsource (lib "eagle-import") (part "ERJ-2BWFR050X"))
    )
    (comp (ref "R313")
      (value "ESR01MZPJ100")
      (footprint "eagle-import:RESC1005X40N")
      (fields (field (name "MOUSER_PART_NUMBER") "755-ESR01MZPJ100"))
      (libsource (lib "eagle-import") (part "ESR01MZPJ100"))
    )
    (comp (ref "R314")
      (value "RC0402JR-1015KL")
      (footprint "eagle-import:RESC1005X40N")
      (fields (field (name "MOUSER_PART_NUMBER") "603-RC0402JR-1015KL"))
      (libsource (lib "eagle-import") (part "RC0402JR-1015KL"))
    )
    (comp (ref "R315")
      (value "CR0402-FX-1022GLF")
      (footprint "eagle-import:RESC1005X40N")
      (fields (field (name "MOUSER_PART_NUMBER") "652-CR0402-FX1022GLF"))
      (libsource (lib "eagle-import") (part "CR0402-FX-1022GLF"))
    )
    (comp (ref "R316")
      (value "RC0402JR-133K3L")
      (footprint "eagle-import:RESC1005X40N")
      (fields (field (name "MOUSER_PART_NUMBER") "603-RC0402JR-133K3L"))
      (libsource (lib "eagle-import") (part "RC0402JR-133K3L"))
    )
    (comp (ref "R317")
      (value "ERJ-2RKF2002X")
      (footprint "eagle-import:ERJ2R_(0402)")
      (fields (field (name "MOUSER_PART_NUMBER") "667-ERJ-2RKF2002X"))
      (libsource (lib "eagle-import") (part "ERJ-2RKF2002X"))
    )
    (comp (ref "R318")
      (value "ERJ-2RKF2002X")
      (footprint "eagle-import:ERJ2R_(0402)")
      (fields (field (name "MOUSER_PART_NUMBER") "667-ERJ-2RKF2002X"))
      (libsource (lib "eagle-import") (part "ERJ-2RKF2002X"))
    )
    (comp (ref "R319")
      (value "CRCW040212K0FKTD")
      (footprint "eagle-import:RESC1005X40N")
      (fields (field (name "MOUSER_PART_NUMBER") "71-CRCW0402-12K"))
      (libsource (lib "eagle-import") (part "CRCW040212K0FKTD"))
    )
    (comp (ref "R320")
      (value "CRCW0402510RFKEDC")
      (footprint "eagle-import:RESC1005X35N")
      (fields (field (name "MOUSER_PART_NUMBER") "71-CRCW0402510RFKEDC"))
      (libsource (lib "eagle-import") (part "CRCW0402510RFKEDC"))
    )
    (comp (ref "R321")
      (value "CRCW04021K05FKED")
      (footprint "eagle-import:RESC1005X40N")
      (fields (field (name "MOUSER_PART_NUMBER") "71-CRCW04021K05FKED"))
      (libsource (lib "eagle-import") (part "CRCW04021K05FKED"))
    )
    (comp (ref "R322")
      (value "ERJ-2BWFR050X")
      (footprint "eagle-import:ERJ_2LW_2BW_2B_(0402)")
      (fields (field (name "MOUSER_PART_NUMBER") "667-ERJ-2BWFR050X"))
      (libsource (lib "eagle-import") (part "ERJ-2BWFR050X"))
    )
    (comp (ref "R323")
      (value "ESR01MZPJ100")
      (footprint "eagle-import:RESC1005X40N")
      (fields (field (name "MOUSER_PART_NUMBER") "755-ESR01MZPJ100"))
      (libsource (lib "eagle-import") (part "ESR01MZPJ100"))
    )
    (comp (ref "R324")
      (value "RC0402JR-1015KL")
      (footprint "eagle-import:RESC1005X40N")
      (fields (field (name "MOUSER_PART_NUMBER") "603-RC0402JR-1015KL"))
      (libsource (lib "eagle-import") (part "RC0402JR-1015KL"))
    )
    (comp (ref "R325")
      (value "CR0402-FX-1022GLF")
      (footprint "eagle-import:RESC1005X40N")
      (fields (field (name "MOUSER_PART_NUMBER") "652-CR0402-FX1022GLF"))
      (libsource (lib "eagle-import") (part "CR0402-FX-1022GLF"))
    )
    (comp (ref "R326")
      (value "RC0402JR-133K3L")
      (footprint "eagle-import:RESC1005X40N")
      (fields (field (name "MOUSER_PART_NUMBER") "603-RC0402JR-133K3L"))
      (libsource (lib "eagle-import") (part "RC0402JR-133K3L"))
    )
    (comp (ref "R327")
      (value "ERJ-2RKF2002X")
      (footprint "eagle-import:ERJ2R_(0402)")
      (fields (field (name "MOUSER_PART_NUMBER") "667-ERJ-2RKF2002X"))
      (libsource (lib "eagle-import") (part "ERJ-2RKF2002X"))
    )
    (comp (ref "R328")
      (value "ERJ-2RKF2002X")
      (footprint "eagle-import:ERJ2R_(0402)")
      (fields (field (name "MOUSER_PART_NUMBER") "667-ERJ-2RKF2002X"))
      (libsource (lib "eagle-import") (part "ERJ-2RKF2002X"))
    )
    (comp (ref "R329")
      (value "ERJ-2RKF2002X")
      (footprint "eagle-import:ERJ2R_(0402)")
      (fields (field (name "MOUSER_PART_NUMBER") "667-ERJ-2RKF2002X"))
      (libsource (lib "eagle-import") (part "ERJ-2RKF2002X"))
    )
    (comp (ref "R330")
      (value "CRCW040212K0FKTD")
      (footprint "eagle-import:RESC1005X40N")
      (fields (field (name "MOUSER_PART_NUMBER") "71-CRCW0402-12K"))
      (libsource (lib "eagle-import") (part "CRCW040212K0FKTD"))
    )
    (comp (ref "R331")
      (value "CRCW0402510RFKEDC")
      (footprint "eagle-import:RESC1005X35N")
      (fields (field (name "MOUSER_PART_NUMBER") "71-CRCW0402510RFKEDC"))
      (libsource (lib "eagle-import") (part "CRCW0402510RFKEDC"))
    )
    (comp (ref "R332")
      (value "CRCW04021K05FKED")
      (footprint "eagle-import:RESC1005X40N")
      (fields (field (name "MOUSER_PART_NUMBER") "71-CRCW04021K05FKED"))
      (libsource (lib "eagle-import") (part "CRCW04021K05FKED"))
    )
    (comp (ref "R333")
      (value "ERJ-2BWFR050X")
      (footprint "eagle-import:ERJ_2LW_2BW_2B_(0402)")
      (fields (field (name "MOUSER_PART_NUMBER") "667-ERJ-2BWFR050X"))
      (libsource (lib "eagle-import") (part "ERJ-2BWFR050X"))
    )
    (comp (ref "R334")
      (value "ESR01MZPJ100")
      (footprint "eagle-import:RESC1005X40N")
      (fields (field (name "MOUSER_PART_NUMBER") "755-ESR01MZPJ100"))
      (libsource (lib "eagle-import") (part "ESR01MZPJ100"))
    )
    (comp (ref "R335")
      (value "RC0402JR-1015KL")
      (footprint "eagle-import:RESC1005X40N")
      (fields (field (name "MOUSER_PART_NUMBER") "603-RC0402JR-1015KL"))
      (libsource (lib "eagle-import") (part "RC0402JR-1015KL"))
    )
    (comp (ref "R336")
      (value "CR0402-FX-1022GLF")
      (footprint "eagle-import:RESC1005X40N")
      (fields (field (name "MOUSER_PART_NUMBER") "652-CR0402-FX1022GLF"))
      (libsource (lib "eagle-import") (part "CR0402-FX-1022GLF"))
    )
    (comp (ref "R337")
      (value "RC0402JR-133K3L")
      (footprint "eagle-import:RESC1005X40N")
      (fields (field (name "MOUSER_PART_NUMBER") "603-RC0402JR-133K3L"))
      (libsource (lib "eagle-import") (part "RC0402JR-133K3L"))
    )
    (comp (ref "R338")
      (value "ERJ-2RKF2002X")
      (footprint "eagle-import:ERJ2R_(0402)")
      (fields (field (name "MOUSER_PART_NUMBER") "667-ERJ-2RKF2002X"))
      (libsource (lib "eagle-import") (part "ERJ-2RKF2002X"))
    )
    (comp (ref "R339")
      (value "ERJ-2RKF2002X")
      (footprint "eagle-import:ERJ2R_(0402)")
      (fields (field (name "MOUSER_PART_NUMBER") "667-ERJ-2RKF2002X"))
      (libsource (lib "eagle-import") (part "ERJ-2RKF2002X"))
    )
    (comp (ref "R340")
      (value "CRCW040212K0FKTD")
      (footprint "eagle-import:RESC1005X40N")
      (fields (field (name "MOUSER_PART_NUMBER") "71-CRCW0402-12K"))
      (libsource (lib "eagle-import") (part "CRCW040212K0FKTD"))
    )
    (comp (ref "R341")
      (value "CRCW0402510RFKEDC")
      (footprint "eagle-import:RESC1005X35N")
      (fields (field (name "MOUSER_PART_NUMBER") "71-CRCW0402510RFKEDC"))
      (libsource (lib "eagle-import") (part "CRCW0402510RFKEDC"))
    )
    (comp (ref "R342")
      (value "CRCW04021K05FKED")
      (footprint "eagle-import:RESC1005X40N")
      (fields (field (name "MOUSER_PART_NUMBER") "71-CRCW04021K05FKED"))
      (libsource (lib "eagle-import") (part "CRCW04021K05FKED"))
    )
    (comp (ref "R343")
      (value "ERJ-2BWFR050X")
      (footprint "eagle-import:ERJ_2LW_2BW_2B_(0402)")
      (fields (field (name "MOUSER_PART_NUMBER") "667-ERJ-2BWFR050X"))
      (libsource (lib "eagle-import") (part "ERJ-2BWFR050X"))
    )
    (comp (ref "R344")
      (value "ESR01MZPJ100")
      (footprint "eagle-import:RESC1005X40N")
      (fields (field (name "MOUSER_PART_NUMBER") "755-ESR01MZPJ100"))
      (libsource (lib "eagle-import") (part "ESR01MZPJ100"))
    )
    (comp (ref "R345")
      (value "RC0402JR-1015KL")
      (footprint "eagle-import:RESC1005X40N")
      (fields (field (name "MOUSER_PART_NUMBER") "603-RC0402JR-1015KL"))
      (libsource (lib "eagle-import") (part "RC0402JR-1015KL"))
    )
    (comp (ref "R346")
      (value "CR0402-FX-1022GLF")
      (footprint "eagle-import:RESC1005X40N")
      (fields (field (name "MOUSER_PART_NUMBER") "652-CR0402-FX1022GLF"))
      (libsource (lib "eagle-import") (part "CR0402-FX-1022GLF"))
    )
    (comp (ref "R347")
      (value "RC0402JR-133K3L")
      (footprint "eagle-import:RESC1005X40N")
      (fields (field (name "MOUSER_PART_NUMBER") "603-RC0402JR-133K3L"))
      (libsource (lib "eagle-import") (part "RC0402JR-133K3L"))
    )
    (comp (ref "R348")
      (value "ERJ-2RKF2002X")
      (footprint "eagle-import:ERJ2R_(0402)")
      (fields (field (name "MOUSER_PART_NUMBER") "667-ERJ-2RKF2002X"))
      (libsource (lib "eagle-import") (part "ERJ-2RKF2002X"))
    )
    (comp (ref "R349")
      (value "ERJ-2RKF2002X")
      (footprint "eagle-import:ERJ2R_(0402)")
      (fields (field (name "MOUSER_PART_NUMBER") "667-ERJ-2RKF2002X"))
      (libsource (lib "eagle-import") (part "ERJ-2RKF2002X"))
    )
    (comp (ref "R350")
      (value "ERJ-2RKF2002X")
      (footprint "eagle-import:ERJ2R_(0402)")
      (fields (field (name "MOUSER_PART_NUMBER") "667-ERJ-2RKF2002X"))
      (libsource (lib "eagle-import") (part "ERJ-2RKF2002X"))
    )
    (comp (ref "R351")
      (value "CRCW040212K0FKTD")
      (footprint "eagle-import:RESC1005X40N")
      (fields (field (name "MOUSER_PART_NUMBER") "71-CRCW0402-12K"))
      (libsource (lib "eagle-import") (part "CRCW040212K0FKTD"))
    )
    (comp (ref "R352")
      (value "CRCW0402510RFKEDC")
      (footprint "eagle-import:RESC1005X35N")
      (fields (field (name "MOUSER_PART_NUMBER") "71-CRCW0402510RFKEDC"))
      (libsource (lib "eagle-import") (part "CRCW0402510RFKEDC"))
    )
    (comp (ref "R353")
      (value "CRCW04021K05FKED")
      (footprint "eagle-import:RESC1005X40N")
      (fields (field (name "MOUSER_PART_NUMBER") "71-CRCW04021K05FKED"))
      (libsource (lib "eagle-import") (part "CRCW04021K05FKED"))
    )
    (comp (ref "R354")
      (value "ERJ-2BWFR050X")
      (footprint "eagle-import:ERJ_2LW_2BW_2B_(0402)")
      (fields (field (name "MOUSER_PART_NUMBER") "667-ERJ-2BWFR050X"))
      (libsource (lib "eagle-import") (part "ERJ-2BWFR050X"))
    )
    (comp (ref "R355")
      (value "ESR01MZPJ100")
      (footprint "eagle-import:RESC1005X40N")
      (fields (field (name "MOUSER_PART_NUMBER") "755-ESR01MZPJ100"))
      (libsource (lib "eagle-import") (part "ESR01MZPJ100"))
    )
    (comp (ref "R356")
      (value "RC0402JR-1015KL")
      (footprint "eagle-import:RESC1005X40N")
      (fields (field (name "MOUSER_PART_NUMBER") "603-RC0402JR-1015KL"))
      (libsource (lib "eagle-import") (part "RC0402JR-1015KL"))
    )
    (comp (ref "R357")
      (value "CR0402-FX-1022GLF")
      (footprint "eagle-import:RESC1005X40N")
      (fields (field (name "MOUSER_PART_NUMBER") "652-CR0402-FX1022GLF"))
      (libsource (lib "eagle-import") (part "CR0402-FX-1022GLF"))
    )
    (comp (ref "R358")
      (value "RC0402JR-133K3L")
      (footprint "eagle-import:RESC1005X40N")
      (fields (field (name "MOUSER_PART_NUMBER") "603-RC0402JR-133K3L"))
      (libsource (lib "eagle-import") (part "RC0402JR-133K3L"))
    )
    (comp (ref "R359")
      (value "ERJ-2RKF2002X")
      (footprint "eagle-import:ERJ2R_(0402)")
      (fields (field (name "MOUSER_PART_NUMBER") "667-ERJ-2RKF2002X"))
      (libsource (lib "eagle-import") (part "ERJ-2RKF2002X"))
    )
    (comp (ref "R360")
      (value "ERJ-2RKF2002X")
      (footprint "eagle-import:ERJ2R_(0402)")
      (fields (field (name "MOUSER_PART_NUMBER") "667-ERJ-2RKF2002X"))
      (libsource (lib "eagle-import") (part "ERJ-2RKF2002X"))
    )
    (comp (ref "R361")
      (value "CRCW040212K0FKTD")
      (footprint "eagle-import:RESC1005X40N")
      (fields (field (name "MOUSER_PART_NUMBER") "71-CRCW0402-12K"))
      (libsource (lib "eagle-import") (part "CRCW040212K0FKTD"))
    )
    (comp (ref "R362")
      (value "CRCW0402510RFKEDC")
      (footprint "eagle-import:RESC1005X35N")
      (fields (field (name "MOUSER_PART_NUMBER") "71-CRCW0402510RFKEDC"))
      (libsource (lib "eagle-import") (part "CRCW0402510RFKEDC"))
    )
    (comp (ref "R363")
      (value "CRCW04021K05FKED")
      (footprint "eagle-import:RESC1005X40N")
      (fields (field (name "MOUSER_PART_NUMBER") "71-CRCW04021K05FKED"))
      (libsource (lib "eagle-import") (part "CRCW04021K05FKED"))
    )
    (comp (ref "R364")
      (value "ERJ-2BWFR050X")
      (footprint "eagle-import:ERJ_2LW_2BW_2B_(0402)")
      (fields (field (name "MOUSER_PART_NUMBER") "667-ERJ-2BWFR050X"))
      (libsource (lib "eagle-import") (part "ERJ-2BWFR050X"))
    )
    (comp (ref "R365")
      (value "ESR01MZPJ100")
      (footprint "eagle-import:RESC1005X40N")
      (fields (field (name "MOUSER_PART_NUMBER") "755-ESR01MZPJ100"))
      (libsource (lib "eagle-import") (part "ESR01MZPJ100"))
    )
    (comp (ref "R366")
      (value "RC0402JR-1015KL")
      (footprint "eagle-import:RESC1005X40N")
      (fields (field (name "MOUSER_PART_NUMBER") "603-RC0402JR-1015KL"))
      (libsource (lib "eagle-import") (part "RC0402JR-1015KL"))
    )
    (comp (ref "R367")
      (value "CR0402-FX-1022GLF")
      (footprint "eagle-import:RESC1005X40N")
      (fields (field (name "MOUSER_PART_NUMBER") "652-CR0402-FX1022GLF"))
      (libsource (lib "eagle-import") (part "CR0402-FX-1022GLF"))
    )
    (comp (ref "R368")
      (value "RC0402JR-133K3L")
      (footprint "eagle-import:RESC1005X40N")
      (fields (field (name "MOUSER_PART_NUMBER") "603-RC0402JR-133K3L"))
      (libsource (lib "eagle-import") (part "RC0402JR-133K3L"))
    )
    (comp (ref "R369")
      (value "ERJ-2RKF2002X")
      (footprint "eagle-import:ERJ2R_(0402)")
      (fields (field (name "MOUSER_PART_NUMBER") "667-ERJ-2RKF2002X"))
      (libsource (lib "eagle-import") (part "ERJ-2RKF2002X"))
    )
    (comp (ref "R370")
      (value "ERJ-2RKF2002X")
      (footprint "eagle-import:ERJ2R_(0402)")
      (fields (field (name "MOUSER_PART_NUMBER") "667-ERJ-2RKF2002X"))
      (libsource (lib "eagle-import") (part "ERJ-2RKF2002X"))
    )
    (comp (ref "R371")
      (value "ERJ-2RKF2002X")
      (footprint "eagle-import:ERJ2R_(0402)")
      (fields (field (name "MOUSER_PART_NUMBER") "667-ERJ-2RKF2002X"))
      (libsource (lib "eagle-import") (part "ERJ-2RKF2002X"))
    )
    (comp (ref "R372")
      (value "CRCW040212K0FKTD")
      (footprint "eagle-import:RESC1005X40N")
      (fields (field (name "MOUSER_PART_NUMBER") "71-CRCW0402-12K"))
      (libsource (lib "eagle-import") (part "CRCW040212K0FKTD"))
    )
    (comp (ref "R373")
      (value "CRCW0402510RFKEDC")
      (footprint "eagle-import:RESC1005X35N")
      (fields (field (name "MOUSER_PART_NUMBER") "71-CRCW0402510RFKEDC"))
      (libsource (lib "eagle-import") (part "CRCW0402510RFKEDC"))
    )
    (comp (ref "R374")
      (value "CRCW04021K05FKED")
      (footprint "eagle-import:RESC1005X40N")
      (fields (field (name "MOUSER_PART_NUMBER") "71-CRCW04021K05FKED"))
      (libsource (lib "eagle-import") (part "CRCW04021K05FKED"))
    )
    (comp (ref "R375")
      (value "ERJ-2BWFR050X")
      (footprint "eagle-import:ERJ_2LW_2BW_2B_(0402)")
      (fields (field (name "MOUSER_PART_NUMBER") "667-ERJ-2BWFR050X"))
      (libsource (lib "eagle-import") (part "ERJ-2BWFR050X"))
    )
    (comp (ref "R376")
      (value "ESR01MZPJ100")
      (footprint "eagle-import:RESC1005X40N")
      (fields (field (name "MOUSER_PART_NUMBER") "755-ESR01MZPJ100"))
      (libsource (lib "eagle-import") (part "ESR01MZPJ100"))
    )
    (comp (ref "R377")
      (value "RC0402JR-1015KL")
      (footprint "eagle-import:RESC1005X40N")
      (fields (field (name "MOUSER_PART_NUMBER") "603-RC0402JR-1015KL"))
      (libsource (lib "eagle-import") (part "RC0402JR-1015KL"))
    )
    (comp (ref "R378")
      (value "CR0402-FX-1022GLF")
      (footprint "eagle-import:RESC1005X40N")
      (fields (field (name "MOUSER_PART_NUMBER") "652-CR0402-FX1022GLF"))
      (libsource (lib "eagle-import") (part "CR0402-FX-1022GLF"))
    )
    (comp (ref "R379")
      (value "RC0402JR-133K3L")
      (footprint "eagle-import:RESC1005X40N")
      (fields (field (name "MOUSER_PART_NUMBER") "603-RC0402JR-133K3L"))
      (libsource (lib "eagle-import") (part "RC0402JR-133K3L"))
    )
    (comp (ref "R380")
      (value "ERJ-2RKF2002X")
      (footprint "eagle-import:ERJ2R_(0402)")
      (fields (field (name "MOUSER_PART_NUMBER") "667-ERJ-2RKF2002X"))
      (libsource (lib "eagle-import") (part "ERJ-2RKF2002X"))
    )
    (comp (ref "R381")
      (value "ERJ-2RKF2002X")
      (footprint "eagle-import:ERJ2R_(0402)")
      (fields (field (name "MOUSER_PART_NUMBER") "667-ERJ-2RKF2002X"))
      (libsource (lib "eagle-import") (part "ERJ-2RKF2002X"))
    )
    (comp (ref "R382")
      (value "CRCW040212K0FKTD")
      (footprint "eagle-import:RESC1005X40N")
      (fields (field (name "MOUSER_PART_NUMBER") "71-CRCW0402-12K"))
      (libsource (lib "eagle-import") (part "CRCW040212K0FKTD"))
    )
    (comp (ref "R383")
      (value "CRCW0402510RFKEDC")
      (footprint "eagle-import:RESC1005X35N")
      (fields (field (name "MOUSER_PART_NUMBER") "71-CRCW0402510RFKEDC"))
      (libsource (lib "eagle-import") (part "CRCW0402510RFKEDC"))
    )
    (comp (ref "R384")
      (value "CRCW04021K05FKED")
      (footprint "eagle-import:RESC1005X40N")
      (fields (field (name "MOUSER_PART_NUMBER") "71-CRCW04021K05FKED"))
      (libsource (lib "eagle-import") (part "CRCW04021K05FKED"))
    )
    (comp (ref "R385")
      (value "ERJ-2BWFR050X")
      (footprint "eagle-import:ERJ_2LW_2BW_2B_(0402)")
      (fields (field (name "MOUSER_PART_NUMBER") "667-ERJ-2BWFR050X"))
      (libsource (lib "eagle-import") (part "ERJ-2BWFR050X"))
    )
    (comp (ref "R386")
      (value "ESR01MZPJ100")
      (footprint "eagle-import:RESC1005X40N")
      (fields (field (name "MOUSER_PART_NUMBER") "755-ESR01MZPJ100"))
      (libsource (lib "eagle-import") (part "ESR01MZPJ100"))
    )
    (comp (ref "R387")
      (value "RC0402JR-1015KL")
      (footprint "eagle-import:RESC1005X40N")
      (fields (field (name "MOUSER_PART_NUMBER") "603-RC0402JR-1015KL"))
      (libsource (lib "eagle-import") (part "RC0402JR-1015KL"))
    )
    (comp (ref "R388")
      (value "CR0402-FX-1022GLF")
      (footprint "eagle-import:RESC1005X40N")
      (fields (field (name "MOUSER_PART_NUMBER") "652-CR0402-FX1022GLF"))
      (libsource (lib "eagle-import") (part "CR0402-FX-1022GLF"))
    )
    (comp (ref "R389")
      (value "RC0402JR-133K3L")
      (footprint "eagle-import:RESC1005X40N")
      (fields (field (name "MOUSER_PART_NUMBER") "603-RC0402JR-133K3L"))
      (libsource (lib "eagle-import") (part "RC0402JR-133K3L"))
    )
    (comp (ref "R390")
      (value "ERJ-2RKF2002X")
      (footprint "eagle-import:ERJ2R_(0402)")
      (fields (field (name "MOUSER_PART_NUMBER") "667-ERJ-2RKF2002X"))
      (libsource (lib "eagle-import") (part "ERJ-2RKF2002X"))
    )
    (comp (ref "R391")
      (value "ERJ-2RKF2002X")
      (footprint "eagle-import:ERJ2R_(0402)")
      (fields (field (name "MOUSER_PART_NUMBER") "667-ERJ-2RKF2002X"))
      (libsource (lib "eagle-import") (part "ERJ-2RKF2002X"))
    )
    (comp (ref "R392")
      (value "ERJ-2RKF2002X")
      (footprint "eagle-import:ERJ2R_(0402)")
      (fields (field (name "MOUSER_PART_NUMBER") "667-ERJ-2RKF2002X"))
      (libsource (lib "eagle-import") (part "ERJ-2RKF2002X"))
    )
    (comp (ref "R393")
      (value "CRCW040212K0FKTD")
      (footprint "eagle-import:RESC1005X40N")
      (fields (field (name "MOUSER_PART_NUMBER") "71-CRCW0402-12K"))
      (libsource (lib "eagle-import") (part "CRCW040212K0FKTD"))
    )
    (comp (ref "R394")
      (value "CRCW0402510RFKEDC")
      (footprint "eagle-import:RESC1005X35N")
      (fields (field (name "MOUSER_PART_NUMBER") "71-CRCW0402510RFKEDC"))
      (libsource (lib "eagle-import") (part "CRCW0402510RFKEDC"))
    )
    (comp (ref "R395")
      (value "CRCW04021K05FKED")
      (footprint "eagle-import:RESC1005X40N")
      (fields (field (name "MOUSER_PART_NUMBER") "71-CRCW04021K05FKED"))
      (libsource (lib "eagle-import") (part "CRCW04021K05FKED"))
    )
    (comp (ref "R396")
      (value "ERJ-2BWFR050X")
      (footprint "eagle-import:ERJ_2LW_2BW_2B_(0402)")
      (fields (field (name "MOUSER_PART_NUMBER") "667-ERJ-2BWFR050X"))
      (libsource (lib "eagle-import") (part "ERJ-2BWFR050X"))
    )
    (comp (ref "R397")
      (value "ESR01MZPJ100")
      (footprint "eagle-import:RESC1005X40N")
      (fields (field (name "MOUSER_PART_NUMBER") "755-ESR01MZPJ100"))
      (libsource (lib "eagle-import") (part "ESR01MZPJ100"))
    )
    (comp (ref "R398")
      (value "RC0402JR-1015KL")
      (footprint "eagle-import:RESC1005X40N")
      (fields (field (name "MOUSER_PART_NUMBER") "603-RC0402JR-1015KL"))
      (libsource (lib "eagle-import") (part "RC0402JR-1015KL"))
    )
    (comp (ref "R399")
      (value "CR0402-FX-1022GLF")
      (footprint "eagle-import:RESC1005X40N")
      (fields (field (name "MOUSER_PART_NUMBER") "652-CR0402-FX1022GLF"))
      (libsource (lib "eagle-import") (part "CR0402-FX-1022GLF"))
    )
    (comp (ref "R400")
      (value "RC0402JR-133K3L")
      (footprint "eagle-import:RESC1005X40N")
      (fields (field (name "MOUSER_PART_NUMBER") "603-RC0402JR-133K3L"))
      (libsource (lib "eagle-import") (part "RC0402JR-133K3L"))
    )
    (comp (ref "R401")
      (value "ERJ-2RKF2002X")
      (footprint "eagle-import:ERJ2R_(0402)")
      (fields (field (name "MOUSER_PART_NUMBER") "667-ERJ-2RKF2002X"))
      (libsource (lib "eagle-import") (part "ERJ-2RKF2002X"))
    )
    (comp (ref "R402")
      (value "ERJ-2RKF2002X")
      (footprint "eagle-import:ERJ2R_(0402)")
      (fields (field (name "MOUSER_PART_NUMBER") "667-ERJ-2RKF2002X"))
      (libsource (lib "eagle-import") (part "ERJ-2RKF2002X"))
    )
    (comp (ref "R403")
      (value "CRCW040212K0FKTD")
      (footprint "eagle-import:RESC1005X40N")
      (fields (field (name "MOUSER_PART_NUMBER") "71-CRCW0402-12K"))
      (libsource (lib "eagle-import") (part "CRCW040212K0FKTD"))
    )
    (comp (ref "R404")
      (value "CRCW0402510RFKEDC")
      (footprint "eagle-import:RESC1005X35N")
      (fields (field (name "MOUSER_PART_NUMBER") "71-CRCW0402510RFKEDC"))
      (libsource (lib "eagle-import") (part "CRCW0402510RFKEDC"))
    )
    (comp (ref "R405")
      (value "CRCW04021K05FKED")
      (footprint "eagle-import:RESC1005X40N")
      (fields (field (name "MOUSER_PART_NUMBER") "71-CRCW04021K05FKED"))
      (libsource (lib "eagle-import") (part "CRCW04021K05FKED"))
    )
    (comp (ref "R406")
      (value "ERJ-2BWFR050X")
      (footprint "eagle-import:ERJ_2LW_2BW_2B_(0402)")
      (fields (field (name "MOUSER_PART_NUMBER") "667-ERJ-2BWFR050X"))
      (libsource (lib "eagle-import") (part "ERJ-2BWFR050X"))
    )
    (comp (ref "R407")
      (value "ESR01MZPJ100")
      (footprint "eagle-import:RESC1005X40N")
      (fields (field (name "MOUSER_PART_NUMBER") "755-ESR01MZPJ100"))
      (libsource (lib "eagle-import") (part "ESR01MZPJ100"))
    )
    (comp (ref "R408")
      (value "RC0402JR-1015KL")
      (footprint "eagle-import:RESC1005X40N")
      (fields (field (name "MOUSER_PART_NUMBER") "603-RC0402JR-1015KL"))
      (libsource (lib "eagle-import") (part "RC0402JR-1015KL"))
    )
    (comp (ref "R409")
      (value "CR0402-FX-1022GLF")
      (footprint "eagle-import:RESC1005X40N")
      (fields (field (name "MOUSER_PART_NUMBER") "652-CR0402-FX1022GLF"))
      (libsource (lib "eagle-import") (part "CR0402-FX-1022GLF"))
    )
    (comp (ref "R410")
      (value "RC0402JR-133K3L")
      (footprint "eagle-import:RESC1005X40N")
      (fields (field (name "MOUSER_PART_NUMBER") "603-RC0402JR-133K3L"))
      (libsource (lib "eagle-import") (part "RC0402JR-133K3L"))
    )
    (comp (ref "R411")
      (value "ERJ-2RKF2002X")
      (footprint "eagle-import:ERJ2R_(0402)")
      (fields (field (name "MOUSER_PART_NUMBER") "667-ERJ-2RKF2002X"))
      (libsource (lib "eagle-import") (part "ERJ-2RKF2002X"))
    )
    (comp (ref "R412")
      (value "ERJ-2RKF2002X")
      (footprint "eagle-import:ERJ2R_(0402)")
      (fields (field (name "MOUSER_PART_NUMBER") "667-ERJ-2RKF2002X"))
      (libsource (lib "eagle-import") (part "ERJ-2RKF2002X"))
    )
    (comp (ref "R413")
      (value "ERJ-2RKF2002X")
      (footprint "eagle-import:ERJ2R_(0402)")
      (fields (field (name "MOUSER_PART_NUMBER") "667-ERJ-2RKF2002X"))
      (libsource (lib "eagle-import") (part "ERJ-2RKF2002X"))
    )
    (comp (ref "R414")
      (value "CRCW040212K0FKTD")
      (footprint "eagle-import:RESC1005X40N")
      (fields (field (name "MOUSER_PART_NUMBER") "71-CRCW0402-12K"))
      (libsource (lib "eagle-import") (part "CRCW040212K0FKTD"))
    )
    (comp (ref "R415")
      (value "CRCW0402510RFKEDC")
      (footprint "eagle-import:RESC1005X35N")
      (fields (field (name "MOUSER_PART_NUMBER") "71-CRCW0402510RFKEDC"))
      (libsource (lib "eagle-import") (part "CRCW0402510RFKEDC"))
    )
    (comp (ref "R416")
      (value "CRCW04021K05FKED")
      (footprint "eagle-import:RESC1005X40N")
      (fields (field (name "MOUSER_PART_NUMBER") "71-CRCW04021K05FKED"))
      (libsource (lib "eagle-import") (part "CRCW04021K05FKED"))
    )
    (comp (ref "R417")
      (value "ERJ-2BWFR050X")
      (footprint "eagle-import:ERJ_2LW_2BW_2B_(0402)")
      (fields (field (name "MOUSER_PART_NUMBER") "667-ERJ-2BWFR050X"))
      (libsource (lib "eagle-import") (part "ERJ-2BWFR050X"))
    )
    (comp (ref "R418")
      (value "ESR01MZPJ100")
      (footprint "eagle-import:RESC1005X40N")
      (fields (field (name "MOUSER_PART_NUMBER") "755-ESR01MZPJ100"))
      (libsource (lib "eagle-import") (part "ESR01MZPJ100"))
    )
    (comp (ref "R419")
      (value "RC0402JR-1015KL")
      (footprint "eagle-import:RESC1005X40N")
      (fields (field (name "MOUSER_PART_NUMBER") "603-RC0402JR-1015KL"))
      (libsource (lib "eagle-import") (part "RC0402JR-1015KL"))
    )
    (comp (ref "R420")
      (value "CR0402-FX-1022GLF")
      (footprint "eagle-import:RESC1005X40N")
      (fields (field (name "MOUSER_PART_NUMBER") "652-CR0402-FX1022GLF"))
      (libsource (lib "eagle-import") (part "CR0402-FX-1022GLF"))
    )
    (comp (ref "R421")
      (value "RC0402JR-133K3L")
      (footprint "eagle-import:RESC1005X40N")
      (fields (field (name "MOUSER_PART_NUMBER") "603-RC0402JR-133K3L"))
      (libsource (lib "eagle-import") (part "RC0402JR-133K3L"))
    )
    (comp (ref "R422")
      (value "ERJ-2RKF2002X")
      (footprint "eagle-import:ERJ2R_(0402)")
      (fields (field (name "MOUSER_PART_NUMBER") "667-ERJ-2RKF2002X"))
      (libsource (lib "eagle-import") (part "ERJ-2RKF2002X"))
    )
    (comp (ref "R423")
      (value "ERJ-2RKF2002X")
      (footprint "eagle-import:ERJ2R_(0402)")
      (fields (field (name "MOUSER_PART_NUMBER") "667-ERJ-2RKF2002X"))
      (libsource (lib "eagle-import") (part "ERJ-2RKF2002X"))
    )
    (comp (ref "R424")
      (value "CRCW040212K0FKTD")
      (footprint "eagle-import:RESC1005X40N")
      (fields (field (name "MOUSER_PART_NUMBER") "71-CRCW0402-12K"))
      (libsource (lib "eagle-import") (part "CRCW040212K0FKTD"))
    )
    (comp (ref "R425")
      (value "CRCW0402510RFKEDC")
      (footprint "eagle-import:RESC1005X35N")
      (fields (field (name "MOUSER_PART_NUMBER") "71-CRCW0402510RFKEDC"))
      (libsource (lib "eagle-import") (part "CRCW0402510RFKEDC"))
    )
    (comp (ref "R426")
      (value "CRCW04021K05FKED")
      (footprint "eagle-import:RESC1005X40N")
      (fields (field (name "MOUSER_PART_NUMBER") "71-CRCW04021K05FKED"))
      (libsource (lib "eagle-import") (part "CRCW04021K05FKED"))
    )
    (comp (ref "R427")
      (value "ERJ-2BWFR050X")
      (footprint "eagle-import:ERJ_2LW_2BW_2B_(0402)")
      (fields (field (name "MOUSER_PART_NUMBER") "667-ERJ-2BWFR050X"))
      (libsource (lib "eagle-import") (part "ERJ-2BWFR050X"))
    )
    (comp (ref "R428")
      (value "ESR01MZPJ100")
      (footprint "eagle-import:RESC1005X40N")
      (fields (field (name "MOUSER_PART_NUMBER") "755-ESR01MZPJ100"))
      (libsource (lib "eagle-import") (part "ESR01MZPJ100"))
    )
    (comp (ref "R429")
      (value "RC0402JR-1015KL")
      (footprint "eagle-import:RESC1005X40N")
      (fields (field (name "MOUSER_PART_NUMBER") "603-RC0402JR-1015KL"))
      (libsource (lib "eagle-import") (part "RC0402JR-1015KL"))
    )
    (comp (ref "R430")
      (value "CR0402-FX-1022GLF")
      (footprint "eagle-import:RESC1005X40N")
      (fields (field (name "MOUSER_PART_NUMBER") "652-CR0402-FX1022GLF"))
      (libsource (lib "eagle-import") (part "CR0402-FX-1022GLF"))
    )
    (comp (ref "R431")
      (value "RC0402JR-133K3L")
      (footprint "eagle-import:RESC1005X40N")
      (fields (field (name "MOUSER_PART_NUMBER") "603-RC0402JR-133K3L"))
      (libsource (lib "eagle-import") (part "RC0402JR-133K3L"))
    )
    (comp (ref "R432")
      (value "ERJ-2RKF2002X")
      (footprint "eagle-import:ERJ2R_(0402)")
      (fields (field (name "MOUSER_PART_NUMBER") "667-ERJ-2RKF2002X"))
      (libsource (lib "eagle-import") (part "ERJ-2RKF2002X"))
    )
    (comp (ref "R433")
      (value "ERJ-2RKF2002X")
      (footprint "eagle-import:ERJ2R_(0402)")
      (fields (field (name "MOUSER_PART_NUMBER") "667-ERJ-2RKF2002X"))
      (libsource (lib "eagle-import") (part "ERJ-2RKF2002X"))
    )
    (comp (ref "R434")
      (value "ERJ-2RKF2002X")
      (footprint "eagle-import:ERJ2R_(0402)")
      (fields (field (name "MOUSER_PART_NUMBER") "667-ERJ-2RKF2002X"))
      (libsource (lib "eagle-import") (part "ERJ-2RKF2002X"))
    )
    (comp (ref "R435")
      (value "CRCW040212K0FKTD")
      (footprint "eagle-import:RESC1005X40N")
      (fields (field (name "MOUSER_PART_NUMBER") "71-CRCW0402-12K"))
      (libsource (lib "eagle-import") (part "CRCW040212K0FKTD"))
    )
    (comp (ref "R436")
      (value "CRCW0402510RFKEDC")
      (footprint "eagle-import:RESC1005X35N")
      (fields (field (name "MOUSER_PART_NUMBER") "71-CRCW0402510RFKEDC"))
      (libsource (lib "eagle-import") (part "CRCW0402510RFKEDC"))
    )
    (comp (ref "R437")
      (value "CRCW04021K05FKED")
      (footprint "eagle-import:RESC1005X40N")
      (fields (field (name "MOUSER_PART_NUMBER") "71-CRCW04021K05FKED"))
      (libsource (lib "eagle-import") (part "CRCW04021K05FKED"))
    )
    (comp (ref "R438")
      (value "ERJ-2BWFR050X")
      (footprint "eagle-import:ERJ_2LW_2BW_2B_(0402)")
      (fields (field (name "MOUSER_PART_NUMBER") "667-ERJ-2BWFR050X"))
      (libsource (lib "eagle-import") (part "ERJ-2BWFR050X"))
    )
    (comp (ref "R439")
      (value "ESR01MZPJ100")
      (footprint "eagle-import:RESC1005X40N")
      (fields (field (name "MOUSER_PART_NUMBER") "755-ESR01MZPJ100"))
      (libsource (lib "eagle-import") (part "ESR01MZPJ100"))
    )
    (comp (ref "R440")
      (value "RC0402JR-1015KL")
      (footprint "eagle-import:RESC1005X40N")
      (fields (field (name "MOUSER_PART_NUMBER") "603-RC0402JR-1015KL"))
      (libsource (lib "eagle-import") (part "RC0402JR-1015KL"))
    )
    (comp (ref "R441")
      (value "CR0402-FX-1022GLF")
      (footprint "eagle-import:RESC1005X40N")
      (fields (field (name "MOUSER_PART_NUMBER") "652-CR0402-FX1022GLF"))
      (libsource (lib "eagle-import") (part "CR0402-FX-1022GLF"))
    )
    (comp (ref "R442")
      (value "RC0402JR-133K3L")
      (footprint "eagle-import:RESC1005X40N")
      (fields (field (name "MOUSER_PART_NUMBER") "603-RC0402JR-133K3L"))
      (libsource (lib "eagle-import") (part "RC0402JR-133K3L"))
    )
    (comp (ref "R443")
      (value "ERJ-2RKF2002X")
      (footprint "eagle-import:ERJ2R_(0402)")
      (fields (field (name "MOUSER_PART_NUMBER") "667-ERJ-2RKF2002X"))
      (libsource (lib "eagle-import") (part "ERJ-2RKF2002X"))
    )
    (comp (ref "R444")
      (value "ERJ-2RKF2002X")
      (footprint "eagle-import:ERJ2R_(0402)")
      (fields (field (name "MOUSER_PART_NUMBER") "667-ERJ-2RKF2002X"))
      (libsource (lib "eagle-import") (part "ERJ-2RKF2002X"))
    )
    (comp (ref "R445")
      (value "ERJ-2RKF2002X")
      (footprint "eagle-import:ERJ2R_(0402)")
      (fields (field (name "MOUSER_PART_NUMBER") "667-ERJ-2RKF2002X"))
      (libsource (lib "eagle-import") (part "ERJ-2RKF2002X"))
    )
    (comp (ref "R446")
      (value "ERJ-2RKF2002X")
      (footprint "eagle-import:ERJ2R_(0402)")
      (fields (field (name "MOUSER_PART_NUMBER") "667-ERJ-2RKF2002X"))
      (libsource (lib "eagle-import") (part "ERJ-2RKF2002X"))
    )
    (comp (ref "R447")
      (value "ERJ-2RKF2002X")
      (footprint "eagle-import:ERJ2R_(0402)")
      (fields (field (name "MOUSER_PART_NUMBER") "667-ERJ-2RKF2002X"))
      (libsource (lib "eagle-import") (part "ERJ-2RKF2002X"))
    )
    (comp (ref "R448")
      (value "ERJ-2RKF2002X")
      (footprint "eagle-import:ERJ2R_(0402)")
      (fields (field (name "MOUSER_PART_NUMBER") "667-ERJ-2RKF2002X"))
      (libsource (lib "eagle-import") (part "ERJ-2RKF2002X"))
    )
    (comp (ref "R449")
      (value "ERJ-2RKF2002X")
      (footprint "eagle-import:ERJ2R_(0402)")
      (fields (field (name "MOUSER_PART_NUMBER") "667-ERJ-2RKF2002X"))
      (libsource (lib "eagle-import") (part "ERJ-2RKF2002X"))
    )
    (comp (ref "R450")
      (value "ERJ-2RKF2002X")
      (footprint "eagle-import:ERJ2R_(0402)")
      (fields (field (name "MOUSER_PART_NUMBER") "667-ERJ-2RKF2002X"))
      (libsource (lib "eagle-import") (part "ERJ-2RKF2002X"))
    )
    (comp (ref "R451")
      (value "ERJ-2RKF2002X")
      (footprint "eagle-import:ERJ2R_(0402)")
      (fields (field (name "MOUSER_PART_NUMBER") "667-ERJ-2RKF2002X"))
      (libsource (lib "eagle-import") (part "ERJ-2RKF2002X"))
    )
    (comp (ref "R452")
      (value "ERJ-2RKF2002X")
      (footprint "eagle-import:ERJ2R_(0402)")
      (fields (field (name "MOUSER_PART_NUMBER") "667-ERJ-2RKF2002X"))
      (libsource (lib "eagle-import") (part "ERJ-2RKF2002X"))
    )
    (comp (ref "R453")
      (value "ERJ-2RKF2002X")
      (footprint "eagle-import:ERJ2R_(0402)")
      (fields (field (name "MOUSER_PART_NUMBER") "667-ERJ-2RKF2002X"))
      (libsource (lib "eagle-import") (part "ERJ-2RKF2002X"))
    )
    (comp (ref "R454")
      (value "ERJ-2RKF2002X")
      (footprint "eagle-import:ERJ2R_(0402)")
      (fields (field (name "MOUSER_PART_NUMBER") "667-ERJ-2RKF2002X"))
      (libsource (lib "eagle-import") (part "ERJ-2RKF2002X"))
    )
    (comp (ref "R455")
      (value "ERJ-2RKF2002X")
      (footprint "eagle-import:ERJ2R_(0402)")
      (fields (field (name "MOUSER_PART_NUMBER") "667-ERJ-2RKF2002X"))
      (libsource (lib "eagle-import") (part "ERJ-2RKF2002X"))
    )
    (comp (ref "R456")
      (value "ERJ-2RKF2002X")
      (footprint "eagle-import:ERJ2R_(0402)")
      (fields (field (name "MOUSER_PART_NUMBER") "667-ERJ-2RKF2002X"))
      (libsource (lib "eagle-import") (part "ERJ-2RKF2002X"))
    )
    (comp (ref "R457")
      (value "ERJ-2RKF2002X")
      (footprint "eagle-import:ERJ2R_(0402)")
      (fields (field (name "MOUSER_PART_NUMBER") "667-ERJ-2RKF2002X"))
      (libsource (lib "eagle-import") (part "ERJ-2RKF2002X"))
    )
    (comp (ref "R458")
      (value "ERJ-2RKF2002X")
      (footprint "eagle-import:ERJ2R_(0402)")
      (fields (field (name "MOUSER_PART_NUMBER") "667-ERJ-2RKF2002X"))
      (libsource (lib "eagle-import") (part "ERJ-2RKF2002X"))
    )
    (comp (ref "R517")
      (value "CRG0402ZR")
      (footprint "eagle-import:RESC1005X40N")
      (fields (field (name "MOUSER_PART_NUMBER") "279-CRG0402ZR"))
      (libsource (lib "eagle-import") (part "CRG0402ZR"))
    )
    (comp (ref "R518")
      (value "CRG0402ZR")
      (footprint "eagle-import:RESC1005X40N")
      (fields (field (name "MOUSER_PART_NUMBER") "279-CRG0402ZR"))
      (libsource (lib "eagle-import") (part "CRG0402ZR"))
    )
    (comp (ref "R519")
      (value "CRG0402ZR")
      (footprint "eagle-import:RESC1005X40N")
      (fields (field (name "MOUSER_PART_NUMBER") "279-CRG0402ZR"))
      (libsource (lib "eagle-import") (part "CRG0402ZR"))
    )
    (comp (ref "R520")
      (value "CRG0402ZR")
      (footprint "eagle-import:RESC1005X40N")
      (fields (field (name "MOUSER_PART_NUMBER") "279-CRG0402ZR"))
      (libsource (lib "eagle-import") (part "CRG0402ZR"))
    )
    (comp (ref "R521")
      (value "CRG0402ZR")
      (footprint "eagle-import:RESC1005X40N")
      (fields (field (name "MOUSER_PART_NUMBER") "279-CRG0402ZR"))
      (libsource (lib "eagle-import") (part "CRG0402ZR"))
    )
    (comp (ref "C170")
      (value "GRM31C5C1E474JE01L")
      (footprint "eagle-import:CAPC3216X180N")
      (fields (field (name "MOUSER_PART_NUMBER") "81-GRM31C5C1E474JE1L"))
      (libsource (lib "eagle-import") (part "GRM31C5C1E474JE01L"))
    )
    (comp (ref "C171")
      (value "06035C270JAT2A")
      (footprint "eagle-import:CAPC1608X90N")
      (libsource (lib "eagle-import") (part "06035C270JAT2A"))
    )
    (comp (ref "C172")
      (value "06035C270JAT2A")
      (footprint "eagle-import:CAPC1608X90N")
      (libsource (lib "eagle-import") (part "06035C270JAT2A"))
    )
    (comp (ref "IC32")
      (value "LTC6820IUD#PBF")
      (footprint "eagle-import:QFN50P300X300X80-17N")
      (fields (field (name "MOUSER_PART_NUMBER") "584-LTC6820IUD#PBF"))
      (libsource (lib "eagle-import") (part "LTC6820IUD#PBF"))
    )
    (comp (ref "IC33")
      (value "CBTL01023GM,115")
      (footprint "eagle-import:QFN50P200X155X50-10N")
      (libsource (lib "eagle-import") (part "CBTL01023GM,115"))
    )
    (comp (ref "R510")
      (value "CPF0402B1K21E1")
      (footprint "eagle-import:RESC1005X35N")
      (libsource (lib "eagle-import") (part "CPF0402B1K21E1"))
    )
    (comp (ref "R511")
      (value "ERA-2AEB7870X")
      (footprint "eagle-import:ERA2AED122X")
      (libsource (lib "eagle-import") (part "ERA-2AEB7870X"))
    )
    (comp (ref "R512")
      (value "TNPW0402100RBYEP")
      (footprint "eagle-import:RESC1005X40N")
      (fields (field (name "MF") "Vishay"))
      (libsource (lib "eagle-import") (part "TNPW0402100RBYEP"))
    )
    (comp (ref "R513")
      (value "CRG0402ZR")
      (footprint "eagle-import:RESC1005X40N")
      (fields (field (name "MOUSER_PART_NUMBER") "279-CRG0402ZR"))
      (libsource (lib "eagle-import") (part "CRG0402ZR"))
    )
    (comp (ref "R514")
      (value "CRG0402ZR")
      (footprint "eagle-import:RESC1005X40N")
      (fields (field (name "MOUSER_PART_NUMBER") "279-CRG0402ZR"))
      (libsource (lib "eagle-import") (part "CRG0402ZR"))
    )
    (comp (ref "R515")
      (value "CRG0402ZR")
      (footprint "eagle-import:RESC1005X40N")
      (fields (field (name "MOUSER_PART_NUMBER") "279-CRG0402ZR"))
      (libsource (lib "eagle-import") (part "CRG0402ZR"))
    )
    (comp (ref "R516")
      (value "CRG0402ZR")
      (footprint "eagle-import:RESC1005X40N")
      (fields (field (name "MOUSER_PART_NUMBER") "279-CRG0402ZR"))
      (libsource (lib "eagle-import") (part "CRG0402ZR"))
    )
    (comp (ref "T1")
      (value "782482_33VC")
      (footprint "eagle-import:DIP1016W60P254L914H635Q6N")
      (fields
        (field (name "MANUFACTURER_PART_NUMBER") "782482/33VC")
        (field (name "MOUSER_PART_NUMBER") "580-782482/33VC")
      )
      (libsource (lib "eagle-import") (part "782482_33VC"))
    )
  )
  (nets
    (net (code "1") (name "-5V_ON_BOARD") (class "Default")
      (node (ref "C111") (pin "1") (pinfunction "1_1") (pintype "bidirectional"))
      (node (ref "C178") (pin "1") (pinfunction "1_1") (pintype "bidirectional"))
      (node (ref "C179") (pin "2") (pinfunction "2_2") (pintype "bidirectional"))
      (node (ref "C184") (pin "1") (pinfunction "1_1") (pintype "bidirectional"))
      (node (ref "C185") (pin "2") (pinfunction "2_2") (pintype "bidirectional"))
      (node (ref "C187") (pin "2") (pinfunction "2_2") (pintype "bidirectional"))
      (node (ref "C197") (pin "2") (pinfunction "2_2") (pintype "bidirectional"))
      (node (ref "C202") (pin "1") (pinfunction "1_1") (pintype "bidirectional"))
      (node (ref "C203") (pin "2") (pinfunction "2_2") (pintype "bidirectional"))
      (node (ref "C208") (pin "1") (pinfunction "1_1") (pintype "bidirectional"))
      (node (ref "C209") (pin "2") (pinfunction "2_2") (pintype "bidirectional"))
      (node (ref "C214") (pin "1") (pinfunction "1_1") (pintype "bidirectional"))
      (node (ref "C215") (pin "2") (pinfunction "2_2") (pintype "bidirectional"))
      (node (ref "C220") (pin "1") (pinfunction "1_1") (pintype "bidirectional"))
      (node (ref "C221") (pin "2") (pinfunction "2_2") (pintype "bidirectional"))
      (node (ref "C226") (pin "1") (pinfunction "1_1") (pintype "bidirectional"))
      (node (ref "C227") (pin "2") (pinfunction "2_2") (pintype "bidirectional"))
      (node (ref "C232") (pin "1") (pinfunction "1_1") (pintype "bidirectional"))
      (node (ref "C233") (pin "2") (pinfunction "2_2") (pintype "bidirectional"))
      (node (ref "C238") (pin "1") (pinfunction "1_1") (pintype "bidirectional"))
      (node (ref "C239") (pin "2") (pinfunction "2_2") (pintype "bidirectional"))
      (node (ref "C244") (pin "1") (pinfunction "1_1") (pintype "bidirectional"))
      (node (ref "C245") (pin "2") (pinfunction "2_2") (pintype "bidirectional"))
      (node (ref "C250") (pin "1") (pinfunction "1_1") (pintype "bidirectional"))
      (node (ref "C251") (pin "2") (pinfunction "2_2") (pintype "bidirectional"))
      (node (ref "C256") (pin "1") (pinfunction "1_1") (pintype "bidirectional"))
      (node (ref "C257") (pin "2") (pinfunction "2_2") (pintype "bidirectional"))
      (node (ref "C262") (pin "1") (pinfunction "1_1") (pintype "bidirectional"))
      (node (ref "C263") (pin "2") (pinfunction "2_2") (pintype "bidirectional"))
      (node (ref "C268") (pin "1") (pinfunction "1_1") (pintype "bidirectional"))
      (node (ref "C269") (pin "2") (pinfunction "2_2") (pintype "bidirectional"))
      (node (ref "C274") (pin "1") (pinfunction "1_1") (pintype "bidirectional"))
      (node (ref "C275") (pin "2") (pinfunction "2_2") (pintype "bidirectional"))
      (node (ref "C28") (pin "1") (pinfunction "1_1") (pintype "bidirectional"))
      (node (ref "C29") (pin "1") (pinfunction "1_1") (pintype "bidirectional"))
      (node (ref "C30") (pin "1") (pinfunction "1_1") (pintype "bidirectional"))
      (node (ref "C50") (pin "1") (pinfunction "1_1") (pintype "bidirectional"))
      (node (ref "C51") (pin "2") (pinfunction "2_2") (pintype "bidirectional"))
      (node (ref "C58") (pin "1") (pinfunction "1_1") (pintype "bidirectional"))
      (node (ref "C59") (pin "2") (pinfunction "2_2") (pintype "bidirectional"))
      (node (ref "C75") (pin "1") (pinfunction "1_1") (pintype "bidirectional"))
      (node (ref "C76") (pin "2") (pinfunction "2_2") (pintype "bidirectional"))
      (node (ref "C81") (pin "1") (pinfunction "1_1") (pintype "bidirectional"))
      (node (ref "C83") (pin "1") (pinfunction "1_1") (pintype "bidirectional"))
      (node (ref "C84") (pin "2") (pinfunction "2_2") (pintype "bidirectional"))
      (node (ref "C89") (pin "1") (pinfunction "1_1") (pintype "bidirectional"))
      (node (ref "IC1") (pin "2") (pinfunction "VSS_2") (pintype "bidirectional"))
      (node (ref "IC2") (pin "2") (pinfunction "VSS_2") (pintype "bidirectional"))
      (node (ref "IC3") (pin "2") (pinfunction "VSS_2") (pintype "bidirectional"))
      (node (ref "IC34") (pin "5") (pinfunction "OUT_5") (pintype "bidirectional"))
      (node (ref "IC35") (pin "2") (pinfunction "VSS_2") (pintype "bidirectional"))
      (node (ref "IC36") (pin "2") (pinfunction "VSS_2") (pintype "bidirectional"))
      (node (ref "IC37") (pin "2") (pinfunction "VSS_2") (pintype "bidirectional"))
      (node (ref "IC39") (pin "2") (pinfunction "VSS_2") (pintype "bidirectional"))
      (node (ref "IC40") (pin "2") (pinfunction "VSS_2") (pintype "bidirectional"))
      (node (ref "IC41") (pin "2") (pinfunction "VSS_2") (pintype "bidirectional"))
      (node (ref "IC42") (pin "2") (pinfunction "VSS_2") (pintype "bidirectional"))
      (node (ref "IC43") (pin "2") (pinfunction "VSS_2") (pintype "bidirectional"))
      (node (ref "IC44") (pin "2") (pinfunction "VSS_2") (pintype "bidirectional"))
      (node (ref "IC45") (pin "2") (pinfunction "VSS_2") (pintype "bidirectional"))
      (node (ref "IC46") (pin "2") (pinfunction "VSS_2") (pintype "bidirectional"))
      (node (ref "IC47") (pin "2") (pinfunction "VSS_2") (pintype "bidirectional"))
      (node (ref "IC48") (pin "2") (pinfunction "VSS_2") (pintype "bidirectional"))
      (node (ref "IC49") (pin "2") (pinfunction "VSS_2") (pintype "bidirectional"))
      (node (ref "IC50") (pin "2") (pinfunction "VSS_2") (pintype "bidirectional"))
      (node (ref "IC53") (pin "2") (pinfunction "VSS_2") (pintype "bidirectional"))
      (node (ref "IC54") (pin "2") (pinfunction "VSS_2") (pintype "bidirectional"))
      (node (ref "IC55") (pin "2") (pinfunction "VSS_2") (pintype "bidirectional"))
      (node (ref "IC56") (pin "2") (pinfunction "VSS_2") (pintype "bidirectional"))
      (node (ref "IC57") (pin "2") (pinfunction "VSS_2") (pintype "bidirectional"))
      (node (ref "IC58") (pin "2") (pinfunction "VSS_2") (pintype "bidirectional"))
      (node (ref "IC59") (pin "2") (pinfunction "VSS_2") (pintype "bidirectional"))
      (node (ref "IC60") (pin "2") (pinfunction "VSS_2") (pintype "bidirectional"))
      (node (ref "IC61") (pin "2") (pinfunction "VSS_2") (pintype "bidirectional"))
      (node (ref "IC62") (pin "2") (pinfunction "VSS_2") (pintype "bidirectional"))
      (node (ref "IC63") (pin "2") (pinfunction "VSS_2") (pintype "bidirectional"))
      (node (ref "IC64") (pin "2") (pinfunction "VSS_2") (pintype "bidirectional"))
      (node (ref "IC65") (pin "2") (pinfunction "VSS_2") (pintype "bidirectional"))
      (node (ref "IC66") (pin "2") (pinfunction "VSS_2") (pintype "bidirectional"))
      (node (ref "IC67") (pin "2") (pinfunction "VSS_2") (pintype "bidirectional"))
      (node (ref "IC68") (pin "2") (pinfunction "VSS_2") (pintype "bidirectional"))
      (node (ref "IC69") (pin "2") (pinfunction "VSS_2") (pintype "bidirectional"))
      (node (ref "IC70") (pin "2") (pinfunction "VSS_2") (pintype "bidirectional"))
      (node (ref "IC71") (pin "2") (pinfunction "VSS_2") (pintype "bidirectional"))
      (node (ref "IC72") (pin "2") (pinfunction "VSS_2") (pintype "bidirectional"))
      (node (ref "IC73") (pin "2") (pinfunction "VSS_2") (pintype "bidirectional"))
      (node (ref "IC74") (pin "2") (pinfunction "VSS_2") (pintype "bidirectional"))
      (node (ref "IC75") (pin "2") (pinfunction "VSS_2") (pintype "bidirectional"))
      (node (ref "IC76") (pin "2") (pinfunction "VSS_2") (pintype "bidirectional"))
      (node (ref "IC77") (pin "2") (pinfunction "VSS_2") (pintype "bidirectional"))
      (node (ref "IC78") (pin "2") (pinfunction "VSS_2") (pintype "bidirectional"))
      (node (ref "IC79") (pin "2") (pinfunction "VSS_2") (pintype "bidirectional"))
    )
    (net (code "2") (name "3.3V_DIGITAL") (class "Default")
      (node (ref "C105") (pin "2") (pinfunction "2_2") (pintype "bidirectional"))
      (node (ref "C11") (pin "2") (pinfunction "2_2") (pintype "bidirectional"))
      (node (ref "C170") (pin "1") (pinfunction "1_1") (pintype "bidirectional"))
      (node (ref "C196") (pin "2") (pinfunction "2_2") (pintype "bidirectional"))
      (node (ref "C5") (pin "2") (pinfunction "2_2") (pintype "bidirectional"))
      (node (ref "IC10") (pin "2") (pinfunction "VOUT_1_2") (pintype "output"))
      (node (ref "IC10") (pin "4") (pinfunction "VOUT_2_4") (pintype "output"))
      (node (ref "IC11") (pin "6") (pinfunction "ADR1_6") (pintype "bidirectional"))
      (node (ref "IC13") (pin "5") (pinfunction "ADR0_5") (pintype "bidirectional"))
      (node (ref "IC13") (pin "6") (pinfunction "ADR1_6") (pintype "bidirectional"))
      (node (ref "IC15") (pin "6") (pinfunction "ADR1_6") (pintype "bidirectional"))
      (node (ref "IC17") (pin "5") (pinfunction "ADR0_5") (pintype "bidirectional"))
      (node (ref "IC19") (pin "5") (pinfunction "ADR0_5") (pintype "bidirectional"))
      (node (ref "IC21") (pin "5") (pinfunction "ADR0_5") (pintype "bidirectional"))
      (node (ref "IC23") (pin "5") (pinfunction "ADR0_5") (pintype "bidirectional"))
      (node (ref "IC23") (pin "6") (pinfunction "ADR1_6") (pintype "bidirectional"))
      (node (ref "IC32") (pin "11") (pinfunction "MSTR_11") (pintype "bidirectional"))
      (node (ref "IC32") (pin "16") (pinfunction "EN_16") (pintype "bidirectional"))
      (node (ref "IC32") (pin "5") (pinfunction "VDDS_5") (pintype "bidirectional"))
      (node (ref "IC32") (pin "6") (pinfunction "POL_6") (pintype "bidirectional"))
      (node (ref "IC32") (pin "7") (pinfunction "PHA_7") (pintype "bidirectional"))
      (node (ref "IC32") (pin "8") (pinfunction "VDD_8") (pintype "bidirectional"))
      (node (ref "IC38") (pin "23") (pinfunction "DVDD_23") (pintype "power_in"))
      (node (ref "IC38") (pin "34") (pinfunction "REFSEL_34") (pintype "input"))
      (node (ref "IC38") (pin "6") (pinfunction "~{PAR}/SER/BYTE_SEL_6") (pintype "input"))
      (node (ref "IC38") (pin "7") (pinfunction "~{STBY}_7") (pintype "input"))
      (node (ref "IC51") (pin "23") (pinfunction "DVDD_23") (pintype "power_in"))
      (node (ref "IC51") (pin "34") (pinfunction "REFSEL_34") (pintype "input"))
      (node (ref "IC51") (pin "6") (pinfunction "~{PAR}/SER/BYTE_SEL_6") (pintype "input"))
      (node (ref "IC51") (pin "7") (pinfunction "~{STBY}_7") (pintype "input"))
      (node (ref "IC52") (pin "23") (pinfunction "DVDD_23") (pintype "power_in"))
      (node (ref "IC52") (pin "34") (pinfunction "REFSEL_34") (pintype "input"))
      (node (ref "IC52") (pin "6") (pinfunction "~{PAR}/SER/BYTE_SEL_6") (pintype "input"))
      (node (ref "IC52") (pin "7") (pinfunction "~{STBY}_7") (pintype "input"))
      (node (ref "J3") (pin "P4") (pinfunction "VDD_P4") (pintype "bidirectional"))
      (node (ref "R147") (pin "2") (pinfunction "2_2") (pintype "bidirectional"))
      (node (ref "R148") (pin "2") (pinfunction "2_2") (pintype "bidirectional"))
      (node (ref "R149") (pin "2") (pinfunction "2_2") (pintype "bidirectional"))
      (node (ref "R150") (pin "2") (pinfunction "2_2") (pintype "bidirectional"))
    )
    (net (code "3") (name "3.3V_MCU") (class "Default")
      (node (ref "UC1") (pin "3V3_VDD") (pinfunction "3V3_VDD_3V3_VDD") (pintype "passive"))
    )
    (net (code "4") (name "3.3V_NC") (class "Default")
      (node (ref "J9") (pin "09") (pinfunction "09_09") (pintype "passive"))
    )
    (net (code "5") (name "3.3V_SENSORS") (class "Default")
      (node (ref "C106") (pin "2") (pinfunction "2_2") (pintype "bidirectional"))
      (node (ref "C169") (pin "1") (pinfunction "1_1") (pintype "bidirectional"))
      (node (ref "IC31") (pin "C7") (pinfunction "VDD_1_C7") (pintype "bidirectional"))
      (node (ref "IC31") (pin "D6") (pinfunction "VDD_2_D6") (pintype "bidirectional"))
      (node (ref "IC31") (pin "E3") (pinfunction "VDD_3_E3") (pintype "bidirectional"))
      (node (ref "IC31") (pin "G1") (pinfunction "VDD_4_G1") (pintype "bidirectional"))
      (node (ref "IC31") (pin "H1") (pinfunction "VDD_5_H1") (pintype "bidirectional"))
      (node (ref "IC31") (pin "J4") (pinfunction "VDD_6_J4") (pintype "bidirectional"))
      (node (ref "IC31") (pin "J5") (pinfunction "VDD_7_J5") (pintype "bidirectional"))
      (node (ref "IC31") (pin "K6") (pinfunction "VDD_8_K6") (pintype "bidirectional"))
      (node (ref "IC33") (pin "5") (pinfunction "VDD_5") (pintype "bidirectional"))
      (node (ref "IC8") (pin "2") (pinfunction "VOUT_1_2") (pintype "output"))
      (node (ref "IC8") (pin "4") (pinfunction "VOUT_2_4") (pintype "output"))
      (node (ref "J9") (pin "02") (pinfunction "02_02") (pintype "passive"))
    )
    (net (code "6") (name "3.3V_SWITCHING") (class "Default")
      (node (ref "C110") (pin "2") (pinfunction "2_2") (pintype "bidirectional"))
      (node (ref "IC7") (pin "2") (pinfunction "VOUT_1_2") (pintype "output"))
      (node (ref "IC7") (pin "4") (pinfunction "VOUT_2_4") (pintype "output"))
      (node (ref "J1") (pin "1") (pinfunction "1_1") (pintype "passive"))
      (node (ref "J1") (pin "3") (pinfunction "3_3") (pintype "passive"))
      (node (ref "J1") (pin "5") (pinfunction "5_5") (pintype "passive"))
      (node (ref "J1") (pin "7") (pinfunction "7_7") (pintype "passive"))
      (node (ref "J12") (pin "28") (pinfunction "28_28") (pintype "passive"))
      (node (ref "J12") (pin "30") (pinfunction "30_30") (pintype "passive"))
      (node (ref "J12") (pin "32") (pinfunction "32_32") (pintype "passive"))
      (node (ref "J12") (pin "34") (pinfunction "34_34") (pintype "passive"))
      (node (ref "J12") (pin "36") (pinfunction "36_36") (pintype "passive"))
      (node (ref "J12") (pin "38") (pinfunction "38_38") (pintype "passive"))
      (node (ref "R33") (pin "1") (pinfunction "1_1") (pintype "bidirectional"))
      (node (ref "R35") (pin "1") (pinfunction "1_1") (pintype "bidirectional"))
      (node (ref "R37") (pin "1") (pinfunction "1_1") (pintype "bidirectional"))
      (node (ref "R39") (pin "1") (pinfunction "1_1") (pintype "bidirectional"))
      (node (ref "R43") (pin "1") (pinfunction "1_1") (pintype "bidirectional"))
      (node (ref "R45") (pin "1") (pinfunction "1_1") (pintype "bidirectional"))
      (node (ref "R47") (pin "1") (pinfunction "1_1") (pintype "bidirectional"))
      (node (ref "R49") (pin "1") (pinfunction "1_1") (pintype "bidirectional"))
    )
    (net (code "7") (name "5V_BUS") (class "Default")
      (node (ref "C104") (pin "2") (pinfunction "2_2") (pintype "bidirectional"))
      (node (ref "C108") (pin "2") (pinfunction "2_2") (pintype "bidirectional"))
      (node (ref "C109") (pin "2") (pinfunction "2_2") (pintype "bidirectional"))
      (node (ref "IC10") (pin "3") (pinfunction "VIN_3") (pintype "input"))
      (node (ref "IC7") (pin "3") (pinfunction "VIN_3") (pintype "input"))
      (node (ref "IC8") (pin "3") (pinfunction "VIN_3") (pintype "input"))
      (node (ref "R490") (pin "2") (pinfunction "2_2") (pintype "bidirectional"))
      (node (ref "R493") (pin "1") (pinfunction "1_1") (pintype "bidirectional"))
    )
    (net (code "8") (name "5V_BUS_FROM_CONNECTOR") (class "Default")
      (node (ref "J2") (pin "5") (pinfunction "5_5") (pintype "passive"))
      (node (ref "R490") (pin "1") (pinfunction "1_1") (pintype "bidirectional"))
      (node (ref "R491") (pin "1") (pinfunction "1_1") (pintype "bidirectional"))
    )
    (net (code "9") (name "5V_CONNECTOR") (class "Default")
      (node (ref "C103") (pin "2") (pinfunction "2_2") (pintype "bidirectional"))
      (node (ref "IC9") (pin "4") (pinfunction "OUT_4") (pintype "bidirectional"))
      (node (ref "IC9") (pin "5") (pinfunction "SNS_5") (pintype "bidirectional"))
      (node (ref "J12") (pin "16") (pinfunction "16_16") (pintype "passive"))
      (node (ref "J12") (pin "18") (pinfunction "18_18") (pintype "passive"))
      (node (ref "J12") (pin "20") (pinfunction "20_20") (pintype "passive"))
      (node (ref "J12") (pin "22") (pinfunction "22_22") (pintype "passive"))
      (node (ref "J12") (pin "24") (pinfunction "24_24") (pintype "passive"))
      (node (ref "J12") (pin "26") (pinfunction "26_26") (pintype "passive"))
    )
    (net (code "10") (name "5V_MCU") (class "Default")
      (node (ref "C96") (pin "2") (pinfunction "2_2") (pintype "bidirectional"))
      (node (ref "IC5") (pin "4") (pinfunction "OUT_4") (pintype "bidirectional"))
      (node (ref "IC5") (pin "5") (pinfunction "SNS_5") (pintype "bidirectional"))
      (node (ref "UC1") (pin "5V_EXT") (pinfunction "5V_EXT_5V_EXT") (pintype "passive"))
    )
    (net (code "11") (name "5V_ON_BOARD") (class "Default")
      (node (ref "C10") (pin "2") (pinfunction "2_2") (pintype "bidirectional"))
      (node (ref "C100") (pin "2") (pinfunction "2_2") (pintype "bidirectional"))
      (node (ref "C12") (pin "2") (pinfunction "2_2") (pintype "bidirectional"))
      (node (ref "C14") (pin "2") (pinfunction "2_2") (pintype "bidirectional"))
      (node (ref "C15") (pin "2") (pinfunction "2_2") (pintype "bidirectional"))
      (node (ref "C174") (pin "1") (pinfunction "1_1") (pintype "bidirectional"))
      (node (ref "C177") (pin "1") (pinfunction "1_1") (pintype "bidirectional"))
      (node (ref "C18") (pin "2") (pinfunction "2_2") (pintype "bidirectional"))
      (node (ref "C180") (pin "2") (pinfunction "2_2") (pintype "bidirectional"))
      (node (ref "C183") (pin "1") (pinfunction "1_1") (pintype "bidirectional"))
      (node (ref "C186") (pin "2") (pinfunction "2_2") (pintype "bidirectional"))
      (node (ref "C188") (pin "2") (pinfunction "2_2") (pintype "bidirectional"))
      (node (ref "C19") (pin "1") (pinfunction "1_1") (pintype "bidirectional"))
      (node (ref "C190") (pin "1") (pinfunction "1_1") (pintype "bidirectional"))
      (node (ref "C198") (pin "2") (pinfunction "2_2") (pintype "bidirectional"))
      (node (ref "C201") (pin "1") (pinfunction "1_1") (pintype "bidirectional"))
      (node (ref "C204") (pin "2") (pinfunction "2_2") (pintype "bidirectional"))
      (node (ref "C207") (pin "1") (pinfunction "1_1") (pintype "bidirectional"))
      (node (ref "C210") (pin "2") (pinfunction "2_2") (pintype "bidirectional"))
      (node (ref "C213") (pin "1") (pinfunction "1_1") (pintype "bidirectional"))
      (node (ref "C216") (pin "2") (pinfunction "2_2") (pintype "bidirectional"))
      (node (ref "C219") (pin "1") (pinfunction "1_1") (pintype "bidirectional"))
      (node (ref "C222") (pin "2") (pinfunction "2_2") (pintype "bidirectional"))
      (node (ref "C225") (pin "1") (pinfunction "1_1") (pintype "bidirectional"))
      (node (ref "C228") (pin "2") (pinfunction "2_2") (pintype "bidirectional"))
      (node (ref "C23") (pin "2") (pinfunction "2_2") (pintype "bidirectional"))
      (node (ref "C231") (pin "1") (pinfunction "1_1") (pintype "bidirectional"))
      (node (ref "C234") (pin "2") (pinfunction "2_2") (pintype "bidirectional"))
      (node (ref "C237") (pin "1") (pinfunction "1_1") (pintype "bidirectional"))
      (node (ref "C24") (pin "2") (pinfunction "2_2") (pintype "bidirectional"))
      (node (ref "C240") (pin "2") (pinfunction "2_2") (pintype "bidirectional"))
      (node (ref "C243") (pin "1") (pinfunction "1_1") (pintype "bidirectional"))
      (node (ref "C246") (pin "2") (pinfunction "2_2") (pintype "bidirectional"))
      (node (ref "C249") (pin "1") (pinfunction "1_1") (pintype "bidirectional"))
      (node (ref "C252") (pin "2") (pinfunction "2_2") (pintype "bidirectional"))
      (node (ref "C255") (pin "1") (pinfunction "1_1") (pintype "bidirectional"))
      (node (ref "C258") (pin "2") (pinfunction "2_2") (pintype "bidirectional"))
      (node (ref "C261") (pin "1") (pinfunction "1_1") (pintype "bidirectional"))
      (node (ref "C264") (pin "2") (pinfunction "2_2") (pintype "bidirectional"))
      (node (ref "C267") (pin "1") (pinfunction "1_1") (pintype "bidirectional"))
      (node (ref "C270") (pin "2") (pinfunction "2_2") (pintype "bidirectional"))
      (node (ref "C273") (pin "1") (pinfunction "1_1") (pintype "bidirectional"))
      (node (ref "C276") (pin "2") (pinfunction "2_2") (pintype "bidirectional"))
      (node (ref "C4") (pin "2") (pinfunction "2_2") (pintype "bidirectional"))
      (node (ref "C49") (pin "1") (pinfunction "1_1") (pintype "bidirectional"))
      (node (ref "C52") (pin "2") (pinfunction "2_2") (pintype "bidirectional"))
      (node (ref "C57") (pin "1") (pinfunction "1_1") (pintype "bidirectional"))
      (node (ref "C6") (pin "2") (pinfunction "2_2") (pintype "bidirectional"))
      (node (ref "C60") (pin "2") (pinfunction "2_2") (pintype "bidirectional"))
      (node (ref "C7") (pin "1") (pinfunction "1_1") (pintype "bidirectional"))
      (node (ref "C74") (pin "1") (pinfunction "1_1") (pintype "bidirectional"))
      (node (ref "C77") (pin "2") (pinfunction "2_2") (pintype "bidirectional"))
      (node (ref "C80") (pin "1") (pinfunction "1_1") (pintype "bidirectional"))
      (node (ref "C82") (pin "1") (pinfunction "1_1") (pintype "bidirectional"))
      (node (ref "C85") (pin "2") (pinfunction "2_2") (pintype "bidirectional"))
      (node (ref "C88") (pin "1") (pinfunction "1_1") (pintype "bidirectional"))
      (node (ref "IC34") (pin "1") (pinfunction "IN_1") (pintype "bidirectional"))
      (node (ref "IC34") (pin "6") (pinfunction "~{SHDN}_6") (pintype "bidirectional"))
      (node (ref "IC34") (pin "7") (pinfunction "FB_7") (pintype "bidirectional"))
      (node (ref "IC35") (pin "5") (pinfunction "VDD_5") (pintype "bidirectional"))
      (node (ref "IC36") (pin "5") (pinfunction "VDD_5") (pintype "bidirectional"))
      (node (ref "IC37") (pin "5") (pinfunction "VDD_5") (pintype "bidirectional"))
      (node (ref "IC38") (pin "1") (pinfunction "AVDD_1_1") (pintype "power_in"))
      (node (ref "IC38") (pin "37") (pinfunction "AVDD_2_37") (pintype "power_in"))
      (node (ref "IC38") (pin "38") (pinfunction "AVDD_3_38") (pintype "power_in"))
      (node (ref "IC38") (pin "48") (pinfunction "AVDD_4_48") (pintype "power_in"))
      (node (ref "IC39") (pin "5") (pinfunction "VDD_5") (pintype "bidirectional"))
      (node (ref "IC40") (pin "5") (pinfunction "VDD_5") (pintype "bidirectional"))
      (node (ref "IC41") (pin "5") (pinfunction "VDD_5") (pintype "bidirectional"))
      (node (ref "IC42") (pin "5") (pinfunction "VDD_5") (pintype "bidirectional"))
      (node (ref "IC43") (pin "5") (pinfunction "VDD_5") (pintype "bidirectional"))
      (node (ref "IC44") (pin "5") (pinfunction "VDD_5") (pintype "bidirectional"))
      (node (ref "IC45") (pin "5") (pinfunction "VDD_5") (pintype "bidirectional"))
      (node (ref "IC46") (pin "5") (pinfunction "VDD_5") (pintype "bidirectional"))
      (node (ref "IC47") (pin "5") (pinfunction "VDD_5") (pintype "bidirectional"))
      (node (ref "IC48") (pin "5") (pinfunction "VDD_5") (pintype "bidirectional"))
      (node (ref "IC49") (pin "5") (pinfunction "VDD_5") (pintype "bidirectional"))
      (node (ref "IC50") (pin "5") (pinfunction "VDD_5") (pintype "bidirectional"))
      (node (ref "IC51") (pin "1") (pinfunction "AVDD_1_1") (pintype "power_in"))
      (node (ref "IC51") (pin "37") (pinfunction "AVDD_2_37") (pintype "power_in"))
      (node (ref "IC51") (pin "38") (pinfunction "AVDD_3_38") (pintype "power_in"))
      (node (ref "IC51") (pin "48") (pinfunction "AVDD_4_48") (pintype "power_in"))
      (node (ref "IC52") (pin "1") (pinfunction "AVDD_1_1") (pintype "power_in"))
      (node (ref "IC52") (pin "37") (pinfunction "AVDD_2_37") (pintype "power_in"))
      (node (ref "IC52") (pin "38") (pinfunction "AVDD_3_38") (pintype "power_in"))
      (node (ref "IC52") (pin "48") (pinfunction "AVDD_4_48") (pintype "power_in"))
      (node (ref "IC53") (pin "5") (pinfunction "VDD_5") (pintype "bidirectional"))
      (node (ref "IC54") (pin "5") (pinfunction "VDD_5") (pintype "bidirectional"))
      (node (ref "IC55") (pin "5") (pinfunction "VDD_5") (pintype "bidirectional"))
      (node (ref "IC56") (pin "5") (pinfunction "VDD_5") (pintype "bidirectional"))
      (node (ref "IC57") (pin "5") (pinfunction "VDD_5") (pintype "bidirectional"))
      (node (ref "IC58") (pin "5") (pinfunction "VDD_5") (pintype "bidirectional"))
      (node (ref "IC59") (pin "5") (pinfunction "VDD_5") (pintype "bidirectional"))
      (node (ref "IC6") (pin "4") (pinfunction "OUT_4") (pintype "bidirectional"))
      (node (ref "IC6") (pin "5") (pinfunction "SNS_5") (pintype "bidirectional"))
      (node (ref "IC60") (pin "5") (pinfunction "VDD_5") (pintype "bidirectional"))
      (node (ref "IC61") (pin "5") (pinfunction "VDD_5") (pintype "bidirectional"))
      (node (ref "IC62") (pin "5") (pinfunction "VDD_5") (pintype "bidirectional"))
      (node (ref "IC63") (pin "5") (pinfunction "VDD_5") (pintype "bidirectional"))
      (node (ref "IC64") (pin "5") (pinfunction "VDD_5") (pintype "bidirectional"))
      (node (ref "IC65") (pin "5") (pinfunction "VDD_5") (pintype "bidirectional"))
      (node (ref "IC66") (pin "5") (pinfunction "VDD_5") (pintype "bidirectional"))
      (node (ref "IC67") (pin "5") (pinfunction "VDD_5") (pintype "bidirectional"))
      (node (ref "IC68") (pin "5") (pinfunction "VDD_5") (pintype "bidirectional"))
      (node (ref "IC69") (pin "5") (pinfunction "VDD_5") (pintype "bidirectional"))
      (node (ref "IC70") (pin "5") (pinfunction "VDD_5") (pintype "bidirectional"))
      (node (ref "IC71") (pin "5") (pinfunction "VDD_5") (pintype "bidirectional"))
      (node (ref "IC72") (pin "5") (pinfunction "VDD_5") (pintype "bidirectional"))
      (node (ref "IC73") (pin "5") (pinfunction "VDD_5") (pintype "bidirectional"))
      (node (ref "IC74") (pin "5") (pinfunction "VDD_5") (pintype "bidirectional"))
      (node (ref "IC75") (pin "5") (pinfunction "VDD_5") (pintype "bidirectional"))
      (node (ref "IC76") (pin "5") (pinfunction "VDD_5") (pintype "bidirectional"))
      (node (ref "IC77") (pin "5") (pinfunction "VDD_5") (pintype "bidirectional"))
      (node (ref "IC78") (pin "5") (pinfunction "VDD_5") (pintype "bidirectional"))
      (node (ref "IC79") (pin "5") (pinfunction "VDD_5") (pintype "bidirectional"))
      (node (ref "R104") (pin "2") (pinfunction "2_2") (pintype "bidirectional"))
      (node (ref "R108") (pin "2") (pinfunction "2_2") (pintype "bidirectional"))
      (node (ref "R112") (pin "2") (pinfunction "2_2") (pintype "bidirectional"))
      (node (ref "R116") (pin "2") (pinfunction "2_2") (pintype "bidirectional"))
      (node (ref "R12") (pin "2") (pinfunction "2_2") (pintype "bidirectional"))
      (node (ref "R153") (pin "2") (pinfunction "2_2") (pintype "bidirectional"))
      (node (ref "R158") (pin "2") (pinfunction "2_2") (pintype "bidirectional"))
      (node (ref "R16") (pin "2") (pinfunction "2_2") (pintype "bidirectional"))
      (node (ref "R162") (pin "2") (pinfunction "2_2") (pintype "bidirectional"))
      (node (ref "R20") (pin "2") (pinfunction "2_2") (pintype "bidirectional"))
      (node (ref "R205") (pin "2") (pinfunction "2_2") (pintype "bidirectional"))
      (node (ref "R221") (pin "2") (pinfunction "2_2") (pintype "bidirectional"))
      (node (ref "R24") (pin "2") (pinfunction "2_2") (pintype "bidirectional"))
      (node (ref "R28") (pin "2") (pinfunction "2_2") (pintype "bidirectional"))
      (node (ref "R32") (pin "2") (pinfunction "2_2") (pintype "bidirectional"))
      (node (ref "R4") (pin "2") (pinfunction "2_2") (pintype "bidirectional"))
      (node (ref "R471") (pin "1") (pinfunction "1_1") (pintype "bidirectional"))
      (node (ref "R499") (pin "1") (pinfunction "1_1") (pintype "bidirectional"))
      (node (ref "R500") (pin "1") (pinfunction "1_1") (pintype "bidirectional"))
      (node (ref "R501") (pin "1") (pinfunction "1_1") (pintype "bidirectional"))
      (node (ref "R76") (pin "2") (pinfunction "2_2") (pintype "bidirectional"))
      (node (ref "R8") (pin "2") (pinfunction "2_2") (pintype "bidirectional"))
      (node (ref "R80") (pin "2") (pinfunction "2_2") (pintype "bidirectional"))
      (node (ref "R84") (pin "2") (pinfunction "2_2") (pintype "bidirectional"))
      (node (ref "R88") (pin "2") (pinfunction "2_2") (pintype "bidirectional"))
    )
    (net (code "12") (name "6.5V_BUS") (class "Default")
      (node (ref "C102") (pin "2") (pinfunction "2_2") (pintype "bidirectional"))
      (node (ref "C27") (pin "2") (pinfunction "2_2") (pintype "bidirectional"))
      (node (ref "C98") (pin "2") (pinfunction "2_2") (pintype "bidirectional"))
      (node (ref "IC5") (pin "1") (pinfunction "IN_1_1") (pintype "bidirectional"))
      (node (ref "IC5") (pin "3") (pinfunction "EN_3") (pintype "bidirectional"))
      (node (ref "IC5") (pin "6") (pinfunction "IN_2_6") (pintype "bidirectional"))
      (node (ref "IC6") (pin "1") (pinfunction "IN_1_1") (pintype "bidirectional"))
      (node (ref "IC6") (pin "3") (pinfunction "EN_3") (pintype "bidirectional"))
      (node (ref "IC6") (pin "6") (pinfunction "IN_2_6") (pintype "bidirectional"))
      (node (ref "IC9") (pin "1") (pinfunction "IN_1_1") (pintype "bidirectional"))
      (node (ref "IC9") (pin "3") (pinfunction "EN_3") (pintype "bidirectional"))
      (node (ref "IC9") (pin "6") (pinfunction "IN_2_6") (pintype "bidirectional"))
      (node (ref "R481") (pin "2") (pinfunction "2_2") (pintype "bidirectional"))
      (node (ref "R484") (pin "1") (pinfunction "1_1") (pintype "bidirectional"))
    )
    (net (code "13") (name "6.5V_BUS_FROM_CONNECTOR") (class "Default")
      (node (ref "J2") (pin "3") (pinfunction "3_3") (pintype "passive"))
      (node (ref "R481") (pin "1") (pinfunction "1_1") (pintype "bidirectional"))
      (node (ref "R482") (pin "1") (pinfunction "1_1") (pintype "bidirectional"))
    )
    (net (code "14") (name "13.5V_BUS") (class "Default")
      (node (ref "C189") (pin "1") (pinfunction "1_1") (pintype "bidirectional"))
      (node (ref "C191") (pin "1") (pinfunction "1_1") (pintype "bidirectional"))
      (node (ref "C192") (pin "1") (pinfunction "1_1") (pintype "bidirectional"))
      (node (ref "C193") (pin "1") (pinfunction "1_1") (pintype "bidirectional"))
      (node (ref "C194") (pin "1") (pinfunction "1_1") (pintype "bidirectional"))
      (node (ref "C195") (pin "1") (pinfunction "1_1") (pintype "bidirectional"))
      (node (ref "C26") (pin "1") (pinfunction "1_1") (pintype "bidirectional"))
      (node (ref "C33") (pin "1") (pinfunction "1_1") (pintype "bidirectional"))
      (node (ref "C34") (pin "1") (pinfunction "1_1") (pintype "bidirectional"))
      (node (ref "C35") (pin "1") (pinfunction "1_1") (pintype "bidirectional"))
      (node (ref "IC1") (pin "5") (pinfunction "VDD_5") (pintype "bidirectional"))
      (node (ref "IC11") (pin "11") (pinfunction "VDD2_11") (pintype "bidirectional"))
      (node (ref "IC11") (pin "30") (pinfunction "VDD1_30") (pintype "bidirectional"))
      (node (ref "IC12") (pin "11") (pinfunction "VDD2_11") (pintype "bidirectional"))
      (node (ref "IC12") (pin "30") (pinfunction "VDD1_30") (pintype "bidirectional"))
      (node (ref "IC13") (pin "11") (pinfunction "VDD2_11") (pintype "bidirectional"))
      (node (ref "IC13") (pin "30") (pinfunction "VDD1_30") (pintype "bidirectional"))
      (node (ref "IC14") (pin "11") (pinfunction "VDD2_11") (pintype "bidirectional"))
      (node (ref "IC14") (pin "30") (pinfunction "VDD1_30") (pintype "bidirectional"))
      (node (ref "IC15") (pin "11") (pinfunction "VDD2_11") (pintype "bidirectional"))
      (node (ref "IC15") (pin "30") (pinfunction "VDD1_30") (pintype "bidirectional"))
      (node (ref "IC16") (pin "11") (pinfunction "VDD2_11") (pintype "bidirectional"))
      (node (ref "IC16") (pin "30") (pinfunction "VDD1_30") (pintype "bidirectional"))
      (node (ref "IC17") (pin "11") (pinfunction "VDD2_11") (pintype "bidirectional"))
      (node (ref "IC17") (pin "30") (pinfunction "VDD1_30") (pintype "bidirectional"))
      (node (ref "IC18") (pin "11") (pinfunction "VDD2_11") (pintype "bidirectional"))
      (node (ref "IC18") (pin "30") (pinfunction "VDD1_30") (pintype "bidirectional"))
      (node (ref "IC19") (pin "11") (pinfunction "VDD2_11") (pintype "bidirectional"))
      (node (ref "IC19") (pin "30") (pinfunction "VDD1_30") (pintype "bidirectional"))
      (node (ref "IC2") (pin "5") (pinfunction "VDD_5") (pintype "bidirectional"))
      (node (ref "IC20") (pin "11") (pinfunction "VDD2_11") (pintype "bidirectional"))
      (node (ref "IC20") (pin "30") (pinfunction "VDD1_30") (pintype "bidirectional"))
      (node (ref "IC21") (pin "11") (pinfunction "VDD2_11") (pintype "bidirectional"))
      (node (ref "IC21") (pin "30") (pinfunction "VDD1_30") (pintype "bidirectional"))
      (node (ref "IC22") (pin "11") (pinfunction "VDD2_11") (pintype "bidirectional"))
      (node (ref "IC22") (pin "30") (pinfunction "VDD1_30") (pintype "bidirectional"))
      (node (ref "IC23") (pin "11") (pinfunction "VDD2_11") (pintype "bidirectional"))
      (node (ref "IC23") (pin "30") (pinfunction "VDD1_30") (pintype "bidirectional"))
      (node (ref "IC24") (pin "5") (pinfunction "VDD_5") (pintype "bidirectional"))
      (node (ref "IC25") (pin "5") (pinfunction "VDD_5") (pintype "bidirectional"))
      (node (ref "IC26") (pin "5") (pinfunction "VDD_5") (pintype "bidirectional"))
      (node (ref "IC27") (pin "5") (pinfunction "VDD_5") (pintype "bidirectional"))
      (node (ref "IC28") (pin "5") (pinfunction "VDD_5") (pintype "bidirectional"))
      (node (ref "IC29") (pin "5") (pinfunction "VDD_5") (pintype "bidirectional"))
      (node (ref "IC3") (pin "5") (pinfunction "VDD_5") (pintype "bidirectional"))
      (node (ref "IC30") (pin "5") (pinfunction "VDD_5") (pintype "bidirectional"))
      (node (ref "IC4") (pin "11") (pinfunction "VDD2_11") (pintype "bidirectional"))
      (node (ref "IC4") (pin "30") (pinfunction "VDD1_30") (pintype "bidirectional"))
      (node (ref "J12") (pin "02") (pinfunction "02_02") (pintype "passive"))
      (node (ref "J12") (pin "04") (pinfunction "04_04") (pintype "passive"))
      (node (ref "J12") (pin "06") (pinfunction "06_06") (pintype "passive"))
      (node (ref "J12") (pin "08") (pinfunction "08_08") (pintype "passive"))
      (node (ref "J12") (pin "10") (pinfunction "10_10") (pintype "passive"))
      (node (ref "J12") (pin "12") (pinfunction "12_12") (pintype "passive"))
      (node (ref "J12") (pin "14") (pinfunction "14_14") (pintype "passive"))
      (node (ref "R101") (pin "2") (pinfunction "2_2") (pintype "bidirectional"))
      (node (ref "R129") (pin "1") (pinfunction "1_1") (pintype "bidirectional"))
      (node (ref "R134") (pin "2") (pinfunction "2_2") (pintype "bidirectional"))
      (node (ref "R136") (pin "2") (pinfunction "2_2") (pintype "bidirectional"))
      (node (ref "R139") (pin "1") (pinfunction "1_1") (pintype "bidirectional"))
      (node (ref "R144") (pin "2") (pinfunction "2_2") (pintype "bidirectional"))
      (node (ref "R145") (pin "2") (pinfunction "2_2") (pintype "bidirectional"))
      (node (ref "R164") (pin "2") (pinfunction "2_2") (pintype "bidirectional"))
      (node (ref "R167") (pin "1") (pinfunction "1_1") (pintype "bidirectional"))
      (node (ref "R172") (pin "2") (pinfunction "2_2") (pintype "bidirectional"))
      (node (ref "R174") (pin "2") (pinfunction "2_2") (pintype "bidirectional"))
      (node (ref "R177") (pin "1") (pinfunction "1_1") (pintype "bidirectional"))
      (node (ref "R182") (pin "2") (pinfunction "2_2") (pintype "bidirectional"))
      (node (ref "R183") (pin "2") (pinfunction "2_2") (pintype "bidirectional"))
      (node (ref "R185") (pin "2") (pinfunction "2_2") (pintype "bidirectional"))
      (node (ref "R188") (pin "1") (pinfunction "1_1") (pintype "bidirectional"))
      (node (ref "R193") (pin "2") (pinfunction "2_2") (pintype "bidirectional"))
      (node (ref "R195") (pin "2") (pinfunction "2_2") (pintype "bidirectional"))
      (node (ref "R198") (pin "1") (pinfunction "1_1") (pintype "bidirectional"))
      (node (ref "R206") (pin "2") (pinfunction "2_2") (pintype "bidirectional"))
      (node (ref "R208") (pin "2") (pinfunction "2_2") (pintype "bidirectional"))
      (node (ref "R212") (pin "2") (pinfunction "2_2") (pintype "bidirectional"))
      (node (ref "R215") (pin "1") (pinfunction "1_1") (pintype "bidirectional"))
      (node (ref "R220") (pin "2") (pinfunction "2_2") (pintype "bidirectional"))
      (node (ref "R223") (pin "2") (pinfunction "2_2") (pintype "bidirectional"))
      (node (ref "R226") (pin "1") (pinfunction "1_1") (pintype "bidirectional"))
      (node (ref "R243") (pin "2") (pinfunction "2_2") (pintype "bidirectional"))
      (node (ref "R244") (pin "2") (pinfunction "2_2") (pintype "bidirectional"))
      (node (ref "R246") (pin "2") (pinfunction "2_2") (pintype "bidirectional"))
      (node (ref "R249") (pin "1") (pinfunction "1_1") (pintype "bidirectional"))
      (node (ref "R254") (pin "2") (pinfunction "2_2") (pintype "bidirectional"))
      (node (ref "R256") (pin "2") (pinfunction "2_2") (pintype "bidirectional"))
      (node (ref "R259") (pin "1") (pinfunction "1_1") (pintype "bidirectional"))
      (node (ref "R264") (pin "2") (pinfunction "2_2") (pintype "bidirectional"))
      (node (ref "R265") (pin "2") (pinfunction "2_2") (pintype "bidirectional"))
      (node (ref "R267") (pin "2") (pinfunction "2_2") (pintype "bidirectional"))
      (node (ref "R270") (pin "1") (pinfunction "1_1") (pintype "bidirectional"))
      (node (ref "R275") (pin "2") (pinfunction "2_2") (pintype "bidirectional"))
      (node (ref "R277") (pin "2") (pinfunction "2_2") (pintype "bidirectional"))
      (node (ref "R280") (pin "1") (pinfunction "1_1") (pintype "bidirectional"))
      (node (ref "R285") (pin "2") (pinfunction "2_2") (pintype "bidirectional"))
      (node (ref "R286") (pin "2") (pinfunction "2_2") (pintype "bidirectional"))
      (node (ref "R288") (pin "2") (pinfunction "2_2") (pintype "bidirectional"))
      (node (ref "R291") (pin "1") (pinfunction "1_1") (pintype "bidirectional"))
      (node (ref "R296") (pin "2") (pinfunction "2_2") (pintype "bidirectional"))
      (node (ref "R298") (pin "2") (pinfunction "2_2") (pintype "bidirectional"))
      (node (ref "R301") (pin "1") (pinfunction "1_1") (pintype "bidirectional"))
      (node (ref "R306") (pin "2") (pinfunction "2_2") (pintype "bidirectional"))
      (node (ref "R307") (pin "2") (pinfunction "2_2") (pintype "bidirectional"))
      (node (ref "R309") (pin "2") (pinfunction "2_2") (pintype "bidirectional"))
      (node (ref "R312") (pin "1") (pinfunction "1_1") (pintype "bidirectional"))
      (node (ref "R317") (pin "2") (pinfunction "2_2") (pintype "bidirectional"))
      (node (ref "R319") (pin "2") (pinfunction "2_2") (pintype "bidirectional"))
      (node (ref "R322") (pin "1") (pinfunction "1_1") (pintype "bidirectional"))
      (node (ref "R327") (pin "2") (pinfunction "2_2") (pintype "bidirectional"))
      (node (ref "R328") (pin "2") (pinfunction "2_2") (pintype "bidirectional"))
      (node (ref "R330") (pin "2") (pinfunction "2_2") (pintype "bidirectional"))
      (node (ref "R333") (pin "1") (pinfunction "1_1") (pintype "bidirectional"))
      (node (ref "R338") (pin "2") (pinfunction "2_2") (pintype "bidirectional"))
      (node (ref "R340") (pin "2") (pinfunction "2_2") (pintype "bidirectional"))
      (node (ref "R343") (pin "1") (pinfunction "1_1") (pintype "bidirectional"))
      (node (ref "R348") (pin "2") (pinfunction "2_2") (pintype "bidirectional"))
      (node (ref "R349") (pin "2") (pinfunction "2_2") (pintype "bidirectional"))
      (node (ref "R351") (pin "2") (pinfunction "2_2") (pintype "bidirectional"))
      (node (ref "R354") (pin "1") (pinfunction "1_1") (pintype "bidirectional"))
      (node (ref "R359") (pin "2") (pinfunction "2_2") (pintype "bidirectional"))
      (node (ref "R361") (pin "2") (pinfunction "2_2") (pintype "bidirectional"))
      (node (ref "R364") (pin "1") (pinfunction "1_1") (pintype "bidirectional"))
      (node (ref "R369") (pin "2") (pinfunction "2_2") (pintype "bidirectional"))
      (node (ref "R370") (pin "2") (pinfunction "2_2") (pintype "bidirectional"))
      (node (ref "R372") (pin "2") (pinfunction "2_2") (pintype "bidirectional"))
      (node (ref "R375") (pin "1") (pinfunction "1_1") (pintype "bidirectional"))
      (node (ref "R380") (pin "2") (pinfunction "2_2") (pintype "bidirectional"))
      (node (ref "R382") (pin "2") (pinfunction "2_2") (pintype "bidirectional"))
      (node (ref "R385") (pin "1") (pinfunction "1_1") (pintype "bidirectional"))
      (node (ref "R390") (pin "2") (pinfunction "2_2") (pintype "bidirectional"))
      (node (ref "R391") (pin "2") (pinfunction "2_2") (pintype "bidirectional"))
      (node (ref "R393") (pin "2") (pinfunction "2_2") (pintype "bidirectional"))
      (node (ref "R396") (pin "1") (pinfunction "1_1") (pintype "bidirectional"))
      (node (ref "R401") (pin "2") (pinfunction "2_2") (pintype "bidirectional"))
      (node (ref "R403") (pin "2") (pinfunction "2_2") (pintype "bidirectional"))
      (node (ref "R406") (pin "1") (pinfunction "1_1") (pintype "bidirectional"))
      (node (ref "R411") (pin "2") (pinfunction "2_2") (pintype "bidirectional"))
      (node (ref "R412") (pin "2") (pinfunction "2_2") (pintype "bidirectional"))
      (node (ref "R414") (pin "2") (pinfunction "2_2") (pintype "bidirectional"))
      (node (ref "R417") (pin "1") (pinfunction "1_1") (pintype "bidirectional"))
      (node (ref "R422") (pin "2") (pinfunction "2_2") (pintype "bidirectional"))
      (node (ref "R424") (pin "2") (pinfunction "2_2") (pintype "bidirectional"))
      (node (ref "R427") (pin "1") (pinfunction "1_1") (pintype "bidirectional"))
      (node (ref "R432") (pin "2") (pinfunction "2_2") (pintype "bidirectional"))
      (node (ref "R433") (pin "2") (pinfunction "2_2") (pintype "bidirectional"))
      (node (ref "R435") (pin "2") (pinfunction "2_2") (pintype "bidirectional"))
      (node (ref "R438") (pin "1") (pinfunction "1_1") (pintype "bidirectional"))
      (node (ref "R443") (pin "2") (pinfunction "2_2") (pintype "bidirectional"))
      (node (ref "R445") (pin "1") (pinfunction "1_1") (pintype "bidirectional"))
      (node (ref "R446") (pin "1") (pinfunction "1_1") (pintype "bidirectional"))
      (node (ref "R447") (pin "1") (pinfunction "1_1") (pintype "bidirectional"))
      (node (ref "R448") (pin "1") (pinfunction "1_1") (pintype "bidirectional"))
      (node (ref "R449") (pin "1") (pinfunction "1_1") (pintype "bidirectional"))
      (node (ref "R450") (pin "1") (pinfunction "1_1") (pintype "bidirectional"))
      (node (ref "R451") (pin "1") (pinfunction "1_1") (pintype "bidirectional"))
      (node (ref "R452") (pin "1") (pinfunction "1_1") (pintype "bidirectional"))
      (node (ref "R453") (pin "1") (pinfunction "1_1") (pintype "bidirectional"))
      (node (ref "R454") (pin "1") (pinfunction "1_1") (pintype "bidirectional"))
      (node (ref "R455") (pin "1") (pinfunction "1_1") (pintype "bidirectional"))
      (node (ref "R456") (pin "1") (pinfunction "1_1") (pintype "bidirectional"))
      (node (ref "R457") (pin "1") (pinfunction "1_1") (pintype "bidirectional"))
      (node (ref "R458") (pin "1") (pinfunction "1_1") (pintype "bidirectional"))
      (node (ref "R472") (pin "2") (pinfunction "2_2") (pintype "bidirectional"))
      (node (ref "R475") (pin "1") (pinfunction "1_1") (pintype "bidirectional"))
      (node (ref "R89") (pin "2") (pinfunction "2_2") (pintype "bidirectional"))
      (node (ref "R92") (pin "1") (pinfunction "1_1") (pintype "bidirectional"))
      (node (ref "R97") (pin "2") (pinfunction "2_2") (pintype "bidirectional"))
      (node (ref "R99") (pin "2") (pinfunction "2_2") (pintype "bidirectional"))
    )
    (net (code "15") (name "14V_BUS_FROM_CONNECTOR") (class "Default")
      (node (ref "J2") (pin "1") (pinfunction "1_1") (pintype "passive"))
      (node (ref "R472") (pin "1") (pinfunction "1_1") (pintype "bidirectional"))
      (node (ref "R473") (pin "1") (pinfunction "1_1") (pintype "bidirectional"))
    )
    (net (code "16") (name "40G_GPIO") (class "Default")
      (node (ref "40G_GPIO") (pin "TP") (pinfunction "TP_TP") (pintype "bidirectional"))
      (node (ref "J4") (pin "40") (pinfunction "40_40") (pintype "passive"))
      (node (ref "J5") (pin "54") (pinfunction "54_54") (pintype "passive"))
    )
    (net (code "17") (name "ACCELEROMETER_X") (class "Default")
      (node (ref "D42") (pin "1") (pinfunction "K_1") (pintype "bidirectional"))
      (node (ref "IC1") (pin "3") (pinfunction "IN+_3") (pintype "bidirectional"))
      (node (ref "J6") (pin "26") (pinfunction "26_26") (pintype "passive"))
    )
    (net (code "18") (name "ACCELEROMETER_Y") (class "Default")
      (node (ref "D41") (pin "1") (pinfunction "K_1") (pintype "bidirectional"))
      (node (ref "IC2") (pin "3") (pinfunction "IN+_3") (pintype "bidirectional"))
      (node (ref "J6") (pin "28") (pinfunction "28_28") (pintype "passive"))
    )
    (net (code "19") (name "ACCELEROMETER_Z") (class "Default")
      (node (ref "D40") (pin "1") (pinfunction "K_1") (pintype "bidirectional"))
      (node (ref "IC3") (pin "3") (pinfunction "IN+_3") (pintype "bidirectional"))
      (node (ref "J6") (pin "30") (pinfunction "30_30") (pintype "passive"))
    )
    (net (code "20") (name "ADIN1_") (class "Default")
      (node (ref "IC4") (pin "23") (pinfunction "ADIN1_23") (pintype "bidirectional"))
      (node (ref "LED97") (pin "1") (pinfunction "A_1") (pintype "bidirectional"))
      (node (ref "R57") (pin "1") (pinfunction "1_1") (pintype "bidirectional"))
    )
    (net (code "21") (name "ADIN1_0") (class "Default")
      (node (ref "IC11") (pin "23") (pinfunction "ADIN1_23") (pintype "bidirectional"))
      (node (ref "LED99") (pin "1") (pinfunction "A_1") (pintype "bidirectional"))
      (node (ref "R65") (pin "1") (pinfunction "1_1") (pintype "bidirectional"))
    )
    (net (code "22") (name "ADIN1_0IN") (class "Default")
      (node (ref "D9") (pin "1") (pinfunction "K_1") (pintype "bidirectional"))
      (node (ref "J5") (pin "11") (pinfunction "11_11") (pintype "passive"))
      (node (ref "R65") (pin "2") (pinfunction "2_2") (pintype "bidirectional"))
    )
    (net (code "23") (name "ADIN1_1") (class "Default")
      (node (ref "IC20") (pin "23") (pinfunction "ADIN1_23") (pintype "bidirectional"))
      (node (ref "LED101") (pin "1") (pinfunction "A_1") (pintype "bidirectional"))
      (node (ref "R67") (pin "1") (pinfunction "1_1") (pintype "bidirectional"))
    )
    (net (code "24") (name "ADIN1_1IN") (class "Default")
      (node (ref "D63") (pin "1") (pinfunction "K_1") (pintype "bidirectional"))
      (node (ref "J5") (pin "21") (pinfunction "21_21") (pintype "passive"))
      (node (ref "R67") (pin "2") (pinfunction "2_2") (pintype "bidirectional"))
    )
    (net (code "25") (name "ADIN1_2") (class "Default")
      (node (ref "IC21") (pin "23") (pinfunction "ADIN1_23") (pintype "bidirectional"))
      (node (ref "LED103") (pin "1") (pinfunction "A_1") (pintype "bidirectional"))
      (node (ref "R69") (pin "1") (pinfunction "1_1") (pintype "bidirectional"))
    )
    (net (code "26") (name "ADIN1_2IN") (class "Default")
      (node (ref "D69") (pin "1") (pinfunction "K_1") (pintype "bidirectional"))
      (node (ref "J5") (pin "31") (pinfunction "31_31") (pintype "passive"))
      (node (ref "R69") (pin "2") (pinfunction "2_2") (pintype "bidirectional"))
    )
    (net (code "27") (name "ADIN1_3") (class "Default")
      (node (ref "IC12") (pin "23") (pinfunction "ADIN1_23") (pintype "bidirectional"))
      (node (ref "LED105") (pin "1") (pinfunction "A_1") (pintype "bidirectional"))
      (node (ref "R71") (pin "1") (pinfunction "1_1") (pintype "bidirectional"))
    )
    (net (code "28") (name "ADIN1_3IN") (class "Default")
      (node (ref "D15") (pin "1") (pinfunction "K_1") (pintype "bidirectional"))
      (node (ref "J6") (pin "41") (pinfunction "41_41") (pintype "passive"))
      (node (ref "R71") (pin "2") (pinfunction "2_2") (pintype "bidirectional"))
    )
    (net (code "29") (name "ADIN1_4") (class "Default")
      (node (ref "IC13") (pin "23") (pinfunction "ADIN1_23") (pintype "bidirectional"))
      (node (ref "LED107") (pin "1") (pinfunction "A_1") (pintype "bidirectional"))
      (node (ref "R117") (pin "1") (pinfunction "1_1") (pintype "bidirectional"))
    )
    (net (code "30") (name "ADIN1_4IN") (class "Default")
      (node (ref "D21") (pin "1") (pinfunction "K_1") (pintype "bidirectional"))
      (node (ref "J6") (pin "51") (pinfunction "51_51") (pintype "passive"))
      (node (ref "R117") (pin "2") (pinfunction "2_2") (pintype "bidirectional"))
    )
    (net (code "31") (name "ADIN1_5") (class "Default")
      (node (ref "IC18") (pin "23") (pinfunction "ADIN1_23") (pintype "bidirectional"))
      (node (ref "LED109") (pin "1") (pinfunction "A_1") (pintype "bidirectional"))
      (node (ref "R119") (pin "1") (pinfunction "1_1") (pintype "bidirectional"))
    )
    (net (code "32") (name "ADIN1_5IN") (class "Default")
      (node (ref "D51") (pin "1") (pinfunction "K_1") (pintype "bidirectional"))
      (node (ref "J6") (pin "61") (pinfunction "61_61") (pintype "passive"))
      (node (ref "R119") (pin "2") (pinfunction "2_2") (pintype "bidirectional"))
    )
    (net (code "33") (name "ADIN1_6") (class "Default")
      (node (ref "IC19") (pin "23") (pinfunction "ADIN1_23") (pintype "bidirectional"))
      (node (ref "LED111") (pin "1") (pinfunction "A_1") (pintype "bidirectional"))
      (node (ref "R121") (pin "1") (pinfunction "1_1") (pintype "bidirectional"))
    )
    (net (code "34") (name "ADIN1_6IN") (class "Default")
      (node (ref "D57") (pin "1") (pinfunction "K_1") (pintype "bidirectional"))
      (node (ref "J6") (pin "71") (pinfunction "71_71") (pintype "passive"))
      (node (ref "R121") (pin "2") (pinfunction "2_2") (pintype "bidirectional"))
    )
    (net (code "35") (name "ADIN1_7") (class "Default")
      (node (ref "IC14") (pin "23") (pinfunction "ADIN1_23") (pintype "bidirectional"))
      (node (ref "LED113") (pin "1") (pinfunction "A_1") (pintype "bidirectional"))
      (node (ref "R123") (pin "1") (pinfunction "1_1") (pintype "bidirectional"))
    )
    (net (code "36") (name "ADIN1_7IN") (class "Default")
      (node (ref "D27") (pin "1") (pinfunction "K_1") (pintype "bidirectional"))
      (node (ref "J6") (pin "01") (pinfunction "01_01") (pintype "passive"))
      (node (ref "R123") (pin "2") (pinfunction "2_2") (pintype "bidirectional"))
    )
    (net (code "37") (name "ADIN1_8_POWER_TEMP1") (class "Default")
      (node (ref "D33") (pin "1") (pinfunction "K_1") (pintype "bidirectional"))
      (node (ref "IC15") (pin "23") (pinfunction "ADIN1_23") (pintype "bidirectional"))
      (node (ref "J2") (pin "8") (pinfunction "8_8") (pintype "passive"))
      (node (ref "J6") (pin "11") (pinfunction "11_11") (pintype "passive"))
    )
    (net (code "38") (name "ADIN1_9_5V_RAIL_VO") (class "Default")
      (node (ref "IC16") (pin "23") (pinfunction "ADIN1_23") (pintype "bidirectional"))
      (node (ref "IC26") (pin "1") (pinfunction "OUT_1") (pintype "bidirectional"))
      (node (ref "R498") (pin "2") (pinfunction "2_2") (pintype "bidirectional"))
    )
    (net (code "39") (name "ADIN1_10_14V_RAIL_VO") (class "Default")
      (node (ref "IC17") (pin "23") (pinfunction "ADIN1_23") (pintype "bidirectional"))
      (node (ref "IC24") (pin "1") (pinfunction "OUT_1") (pintype "bidirectional"))
      (node (ref "R480") (pin "2") (pinfunction "2_2") (pintype "bidirectional"))
    )
    (net (code "40") (name "ADIN1_11_TEMP2_OUT") (class "Default")
      (node (ref "IC22") (pin "23") (pinfunction "ADIN1_23") (pintype "bidirectional"))
      (node (ref "IC28") (pin "1") (pinfunction "OUT_1") (pintype "bidirectional"))
      (node (ref "R502") (pin "2") (pinfunction "2_2") (pintype "bidirectional"))
    )
    (net (code "41") (name "ADIN1_12_TEMP4_OUT") (class "Default")
      (node (ref "IC23") (pin "23") (pinfunction "ADIN1_23") (pintype "bidirectional"))
      (node (ref "IC30") (pin "1") (pinfunction "OUT_1") (pintype "bidirectional"))
      (node (ref "R508") (pin "2") (pinfunction "2_2") (pintype "bidirectional"))
    )
    (net (code "42") (name "ADIN1_IN") (class "Default")
      (node (ref "D3") (pin "1") (pinfunction "K_1") (pintype "bidirectional"))
      (node (ref "J5") (pin "01") (pinfunction "01_01") (pintype "passive"))
      (node (ref "R57") (pin "2") (pinfunction "2_2") (pintype "bidirectional"))
    )
    (net (code "43") (name "ADIN2_") (class "Default")
      (node (ref "IC4") (pin "18") (pinfunction "ADIN2_18") (pintype "bidirectional"))
      (node (ref "LED98") (pin "1") (pinfunction "A_1") (pintype "bidirectional"))
      (node (ref "R58") (pin "1") (pinfunction "1_1") (pintype "bidirectional"))
    )
    (net (code "44") (name "ADIN2_0") (class "Default")
      (node (ref "IC11") (pin "18") (pinfunction "ADIN2_18") (pintype "bidirectional"))
      (node (ref "LED100") (pin "1") (pinfunction "A_1") (pintype "bidirectional"))
      (node (ref "R66") (pin "1") (pinfunction "1_1") (pintype "bidirectional"))
    )
    (net (code "45") (name "ADIN2_0IN") (class "Default")
      (node (ref "D12") (pin "1") (pinfunction "K_1") (pintype "bidirectional"))
      (node (ref "J5") (pin "16") (pinfunction "16_16") (pintype "passive"))
      (node (ref "R66") (pin "2") (pinfunction "2_2") (pintype "bidirectional"))
    )
    (net (code "46") (name "ADIN2_1") (class "Default")
      (node (ref "IC20") (pin "18") (pinfunction "ADIN2_18") (pintype "bidirectional"))
      (node (ref "LED102") (pin "1") (pinfunction "A_1") (pintype "bidirectional"))
      (node (ref "R68") (pin "1") (pinfunction "1_1") (pintype "bidirectional"))
    )
    (net (code "47") (name "ADIN2_1IN") (class "Default")
      (node (ref "D66") (pin "1") (pinfunction "K_1") (pintype "bidirectional"))
      (node (ref "J5") (pin "26") (pinfunction "26_26") (pintype "passive"))
      (node (ref "R68") (pin "2") (pinfunction "2_2") (pintype "bidirectional"))
    )
    (net (code "48") (name "ADIN2_2") (class "Default")
      (node (ref "IC21") (pin "18") (pinfunction "ADIN2_18") (pintype "bidirectional"))
      (node (ref "LED104") (pin "1") (pinfunction "A_1") (pintype "bidirectional"))
      (node (ref "R70") (pin "1") (pinfunction "1_1") (pintype "bidirectional"))
    )
    (net (code "49") (name "ADIN2_2IN") (class "Default")
      (node (ref "D72") (pin "1") (pinfunction "K_1") (pintype "bidirectional"))
      (node (ref "J5") (pin "36") (pinfunction "36_36") (pintype "passive"))
      (node (ref "R70") (pin "2") (pinfunction "2_2") (pintype "bidirectional"))
    )
    (net (code "50") (name "ADIN2_3") (class "Default")
      (node (ref "IC12") (pin "18") (pinfunction "ADIN2_18") (pintype "bidirectional"))
      (node (ref "LED106") (pin "1") (pinfunction "A_1") (pintype "bidirectional"))
      (node (ref "R72") (pin "1") (pinfunction "1_1") (pintype "bidirectional"))
    )
    (net (code "51") (name "ADIN2_3IN") (class "Default")
      (node (ref "D18") (pin "1") (pinfunction "K_1") (pintype "bidirectional"))
      (node (ref "J6") (pin "46") (pinfunction "46_46") (pintype "passive"))
      (node (ref "R72") (pin "2") (pinfunction "2_2") (pintype "bidirectional"))
    )
    (net (code "52") (name "ADIN2_4") (class "Default")
      (node (ref "IC13") (pin "18") (pinfunction "ADIN2_18") (pintype "bidirectional"))
      (node (ref "LED108") (pin "1") (pinfunction "A_1") (pintype "bidirectional"))
      (node (ref "R118") (pin "1") (pinfunction "1_1") (pintype "bidirectional"))
    )
    (net (code "53") (name "ADIN2_4IN") (class "Default")
      (node (ref "D24") (pin "1") (pinfunction "K_1") (pintype "bidirectional"))
      (node (ref "J6") (pin "56") (pinfunction "56_56") (pintype "passive"))
      (node (ref "R118") (pin "2") (pinfunction "2_2") (pintype "bidirectional"))
    )
    (net (code "54") (name "ADIN2_5") (class "Default")
      (node (ref "IC18") (pin "18") (pinfunction "ADIN2_18") (pintype "bidirectional"))
      (node (ref "LED110") (pin "1") (pinfunction "A_1") (pintype "bidirectional"))
      (node (ref "R120") (pin "1") (pinfunction "1_1") (pintype "bidirectional"))
    )
    (net (code "55") (name "ADIN2_5IN") (class "Default")
      (node (ref "D54") (pin "1") (pinfunction "K_1") (pintype "bidirectional"))
      (node (ref "J6") (pin "66") (pinfunction "66_66") (pintype "passive"))
      (node (ref "R120") (pin "2") (pinfunction "2_2") (pintype "bidirectional"))
    )
    (net (code "56") (name "ADIN2_6") (class "Default")
      (node (ref "IC19") (pin "18") (pinfunction "ADIN2_18") (pintype "bidirectional"))
      (node (ref "LED112") (pin "1") (pinfunction "A_1") (pintype "bidirectional"))
      (node (ref "R122") (pin "1") (pinfunction "1_1") (pintype "bidirectional"))
    )
    (net (code "57") (name "ADIN2_6IN") (class "Default")
      (node (ref "D60") (pin "1") (pinfunction "K_1") (pintype "bidirectional"))
      (node (ref "J6") (pin "76") (pinfunction "76_76") (pintype "passive"))
      (node (ref "R122") (pin "2") (pinfunction "2_2") (pintype "bidirectional"))
    )
    (net (code "58") (name "ADIN2_7") (class "Default")
      (node (ref "IC14") (pin "18") (pinfunction "ADIN2_18") (pintype "bidirectional"))
      (node (ref "LED114") (pin "1") (pinfunction "A_1") (pintype "bidirectional"))
      (node (ref "R124") (pin "1") (pinfunction "1_1") (pintype "bidirectional"))
    )
    (net (code "59") (name "ADIN2_7IN") (class "Default")
      (node (ref "D30") (pin "1") (pinfunction "K_1") (pintype "bidirectional"))
      (node (ref "J6") (pin "06") (pinfunction "06_06") (pintype "passive"))
      (node (ref "R124") (pin "2") (pinfunction "2_2") (pintype "bidirectional"))
    )
    (net (code "60") (name "ADIN2_8_POWER_TEMP2") (class "Default")
      (node (ref "D36") (pin "1") (pinfunction "K_1") (pintype "bidirectional"))
      (node (ref "IC15") (pin "18") (pinfunction "ADIN2_18") (pintype "bidirectional"))
      (node (ref "J2") (pin "10") (pinfunction "10_10") (pintype "passive"))
      (node (ref "J6") (pin "16") (pinfunction "16_16") (pintype "passive"))
    )
    (net (code "61") (name "ADIN2_9_POWER_TEMP3") (class "Default")
      (node (ref "D39") (pin "1") (pinfunction "K_1") (pintype "bidirectional"))
      (node (ref "IC16") (pin "18") (pinfunction "ADIN2_18") (pintype "bidirectional"))
      (node (ref "J2") (pin "12") (pinfunction "12_12") (pintype "passive"))
      (node (ref "J6") (pin "21") (pinfunction "21_21") (pintype "passive"))
    )
    (net (code "62") (name "ADIN2_10_6.5V_RAIL_VO") (class "Default")
      (node (ref "IC17") (pin "18") (pinfunction "ADIN2_18") (pintype "bidirectional"))
      (node (ref "IC25") (pin "1") (pinfunction "OUT_1") (pintype "bidirectional"))
      (node (ref "R489") (pin "2") (pinfunction "2_2") (pintype "bidirectional"))
    )
    (net (code "63") (name "ADIN2_11_TEMP1_OUT") (class "Default")
      (node (ref "IC22") (pin "18") (pinfunction "ADIN2_18") (pintype "bidirectional"))
      (node (ref "IC27") (pin "1") (pinfunction "OUT_1") (pintype "bidirectional"))
      (node (ref "R503") (pin "2") (pinfunction "2_2") (pintype "bidirectional"))
    )
    (net (code "64") (name "ADIN2_12_TEMP3_OUT") (class "Default")
      (node (ref "IC23") (pin "18") (pinfunction "ADIN2_18") (pintype "bidirectional"))
      (node (ref "IC29") (pin "1") (pinfunction "OUT_1") (pintype "bidirectional"))
      (node (ref "R506") (pin "2") (pinfunction "2_2") (pintype "bidirectional"))
    )
    (net (code "65") (name "ADIN2_IN") (class "Default")
      (node (ref "D6") (pin "1") (pinfunction "K_1") (pintype "bidirectional"))
      (node (ref "J5") (pin "06") (pinfunction "06_06") (pintype "passive"))
      (node (ref "R58") (pin "2") (pinfunction "2_2") (pintype "bidirectional"))
    )
    (net (code "66") (name "BUSY_ADC_1") (class "Default")
      (node (ref "BUSY_ADC_1") (pin "TP") (pinfunction "TP_TP") (pintype "bidirectional"))
      (node (ref "IC51") (pin "14") (pinfunction "BUSY_14") (pintype "output"))
      (node (ref "J4") (pin "55") (pinfunction "55_55") (pintype "passive"))
    )
    (net (code "67") (name "BUSY_ADC_2") (class "Default")
      (node (ref "BUSY_ADC_2") (pin "TP") (pinfunction "TP_TP") (pintype "bidirectional"))
      (node (ref "IC38") (pin "14") (pinfunction "BUSY_14") (pintype "output"))
      (node (ref "J4") (pin "63") (pinfunction "63_63") (pintype "passive"))
    )
    (net (code "68") (name "BUSY_ADC_3") (class "Default")
      (node (ref "BUSY_ADC_3") (pin "TP") (pinfunction "TP_TP") (pintype "bidirectional"))
      (node (ref "IC52") (pin "14") (pinfunction "BUSY_14") (pintype "output"))
      (node (ref "J4") (pin "71") (pinfunction "71_71") (pintype "passive"))
    )
    (net (code "69") (name "C1") (class "Default")
      (node (ref "J5") (pin "58") (pinfunction "58_58") (pintype "passive"))
      (node (ref "R517") (pin "1") (pinfunction "1_1") (pintype "bidirectional"))
      (node (ref "R520") (pin "1") (pinfunction "1_1") (pintype "bidirectional"))
    )
    (net (code "70") (name "C2") (class "Default")
      (node (ref "J5") (pin "56") (pinfunction "56_56") (pintype "passive"))
      (node (ref "R518") (pin "1") (pinfunction "1_1") (pintype "bidirectional"))
      (node (ref "R521") (pin "1") (pinfunction "1_1") (pintype "bidirectional"))
    )
    (net (code "71") (name "C3") (class "Default")
      (node (ref "J5") (pin "60") (pinfunction "60_60") (pintype "passive"))
      (node (ref "R519") (pin "1") (pinfunction "1_1") (pintype "bidirectional"))
    )
    (net (code "72") (name "CODE1") (class "Default")
      (node (ref "J1") (pin "4") (pinfunction "4_4") (pintype "passive"))
      (node (ref "R51") (pin "1") (pinfunction "1_1") (pintype "bidirectional"))
    )
    (net (code "73") (name "CODE2") (class "Default")
      (node (ref "J1") (pin "6") (pinfunction "6_6") (pintype "passive"))
      (node (ref "R53") (pin "1") (pinfunction "1_1") (pintype "bidirectional"))
    )
    (net (code "74") (name "CODE3") (class "Default")
      (node (ref "J1") (pin "8") (pinfunction "8_8") (pintype "passive"))
      (node (ref "R55") (pin "1") (pinfunction "1_1") (pintype "bidirectional"))
    )
    (net (code "75") (name "CONVSTAB_ADC") (class "Default")
      (node (ref "CONVAB_ADC") (pin "TP") (pinfunction "TP_TP") (pintype "bidirectional"))
      (node (ref "IC38") (pin "10") (pinfunction "CONVSTB_10") (pintype "input"))
      (node (ref "IC38") (pin "9") (pinfunction "CONVSTA_9") (pintype "input"))
      (node (ref "IC51") (pin "10") (pinfunction "CONVSTB_10") (pintype "input"))
      (node (ref "IC51") (pin "9") (pinfunction "CONVSTA_9") (pintype "input"))
      (node (ref "IC52") (pin "10") (pinfunction "CONVSTB_10") (pintype "input"))
      (node (ref "IC52") (pin "9") (pinfunction "CONVSTA_9") (pintype "input"))
      (node (ref "J4") (pin "47") (pinfunction "47_47") (pintype "passive"))
    )
    (net (code "76") (name "DIFF1_N") (class "Default")
      (node (ref "C175") (pin "2") (pinfunction "2_2") (pintype "bidirectional"))
      (node (ref "D1") (pin "1") (pinfunction "K_1") (pintype "bidirectional"))
      (node (ref "IC51") (pin "50") (pinfunction "AIN_1GND_50") (pintype "input"))
      (node (ref "J5") (pin "04") (pinfunction "04_04") (pintype "passive"))
    )
    (net (code "77") (name "DIFF1_P") (class "Default")
      (node (ref "D2") (pin "1") (pinfunction "K_1") (pintype "bidirectional"))
      (node (ref "J5") (pin "02") (pinfunction "02_02") (pintype "passive"))
      (node (ref "R151") (pin "2") (pinfunction "2_2") (pintype "bidirectional"))
    )
    (net (code "78") (name "DIFF2_N") (class "Default")
      (node (ref "C181") (pin "2") (pinfunction "2_2") (pintype "bidirectional"))
      (node (ref "D4") (pin "1") (pinfunction "K_1") (pintype "bidirectional"))
      (node (ref "IC51") (pin "52") (pinfunction "AIN_2GND_52") (pintype "input"))
      (node (ref "J5") (pin "10") (pinfunction "10_10") (pintype "passive"))
    )
    (net (code "79") (name "DIFF2_P") (class "Default")
      (node (ref "D5") (pin "1") (pinfunction "K_1") (pintype "bidirectional"))
      (node (ref "J5") (pin "08") (pinfunction "08_08") (pintype "passive"))
      (node (ref "R155") (pin "2") (pinfunction "2_2") (pintype "bidirectional"))
    )
    (net (code "80") (name "DIFF3_N") (class "Default")
      (node (ref "C47") (pin "2") (pinfunction "2_2") (pintype "bidirectional"))
      (node (ref "D7") (pin "1") (pinfunction "K_1") (pintype "bidirectional"))
      (node (ref "IC51") (pin "54") (pinfunction "AIN_3GND_54") (pintype "input"))
      (node (ref "J5") (pin "14") (pinfunction "14_14") (pintype "passive"))
    )
    (net (code "81") (name "DIFF3_P") (class "Default")
      (node (ref "D8") (pin "1") (pinfunction "K_1") (pintype "bidirectional"))
      (node (ref "J5") (pin "12") (pinfunction "12_12") (pintype "passive"))
      (node (ref "R1") (pin "2") (pinfunction "2_2") (pintype "bidirectional"))
    )
    (net (code "82") (name "DIFF4_N") (class "Default")
      (node (ref "C53") (pin "2") (pinfunction "2_2") (pintype "bidirectional"))
      (node (ref "D10") (pin "1") (pinfunction "K_1") (pintype "bidirectional"))
      (node (ref "IC51") (pin "56") (pinfunction "AIN_4GND_56") (pintype "input"))
      (node (ref "J5") (pin "20") (pinfunction "20_20") (pintype "passive"))
    )
    (net (code "83") (name "DIFF4_P") (class "Default")
      (node (ref "D11") (pin "1") (pinfunction "K_1") (pintype "bidirectional"))
      (node (ref "J5") (pin "18") (pinfunction "18_18") (pintype "passive"))
      (node (ref "R5") (pin "2") (pinfunction "2_2") (pintype "bidirectional"))
    )
    (net (code "84") (name "DIFF5_N") (class "Default")
      (node (ref "C78") (pin "2") (pinfunction "2_2") (pintype "bidirectional"))
      (node (ref "D61") (pin "1") (pinfunction "K_1") (pintype "bidirectional"))
      (node (ref "IC51") (pin "58") (pinfunction "AIN_5GND_58") (pintype "input"))
      (node (ref "J5") (pin "24") (pinfunction "24_24") (pintype "passive"))
    )
    (net (code "85") (name "DIFF5_P") (class "Default")
      (node (ref "D62") (pin "1") (pinfunction "K_1") (pintype "bidirectional"))
      (node (ref "J5") (pin "22") (pinfunction "22_22") (pintype "passive"))
      (node (ref "R9") (pin "2") (pinfunction "2_2") (pintype "bidirectional"))
    )
    (net (code "86") (name "DIFF6_N") (class "Default")
      (node (ref "C55") (pin "2") (pinfunction "2_2") (pintype "bidirectional"))
      (node (ref "D64") (pin "1") (pinfunction "K_1") (pintype "bidirectional"))
      (node (ref "IC51") (pin "60") (pinfunction "AIN_6GND_60") (pintype "input"))
      (node (ref "J5") (pin "30") (pinfunction "30_30") (pintype "passive"))
    )
    (net (code "87") (name "DIFF6_P") (class "Default")
      (node (ref "D65") (pin "1") (pinfunction "K_1") (pintype "bidirectional"))
      (node (ref "J5") (pin "28") (pinfunction "28_28") (pintype "passive"))
      (node (ref "R13") (pin "2") (pinfunction "2_2") (pintype "bidirectional"))
    )
    (net (code "88") (name "DIFF7_N") (class "Default")
      (node (ref "C61") (pin "2") (pinfunction "2_2") (pintype "bidirectional"))
      (node (ref "D67") (pin "1") (pinfunction "K_1") (pintype "bidirectional"))
      (node (ref "IC51") (pin "62") (pinfunction "AIN_7GND_62") (pintype "input"))
      (node (ref "J5") (pin "34") (pinfunction "34_34") (pintype "passive"))
    )
    (net (code "89") (name "DIFF7_P") (class "Default")
      (node (ref "D68") (pin "1") (pinfunction "K_1") (pintype "bidirectional"))
      (node (ref "J5") (pin "32") (pinfunction "32_32") (pintype "passive"))
      (node (ref "R17") (pin "2") (pinfunction "2_2") (pintype "bidirectional"))
    )
    (net (code "90") (name "DIFF8_N") (class "Default")
      (node (ref "C86") (pin "2") (pinfunction "2_2") (pintype "bidirectional"))
      (node (ref "D70") (pin "1") (pinfunction "K_1") (pintype "bidirectional"))
      (node (ref "IC51") (pin "64") (pinfunction "AIN_8GND_64") (pintype "input"))
      (node (ref "J5") (pin "40") (pinfunction "40_40") (pintype "passive"))
    )
    (net (code "91") (name "DIFF8_P") (class "Default")
      (node (ref "D71") (pin "1") (pinfunction "K_1") (pintype "bidirectional"))
      (node (ref "J5") (pin "38") (pinfunction "38_38") (pintype "passive"))
      (node (ref "R21") (pin "2") (pinfunction "2_2") (pintype "bidirectional"))
    )
    (net (code "92") (name "DIFF9_N") (class "Default")
      (node (ref "C199") (pin "2") (pinfunction "2_2") (pintype "bidirectional"))
      (node (ref "D13") (pin "1") (pinfunction "K_1") (pintype "bidirectional"))
      (node (ref "IC38") (pin "50") (pinfunction "AIN_1GND_50") (pintype "input"))
      (node (ref "J6") (pin "44") (pinfunction "44_44") (pintype "passive"))
    )
    (net (code "93") (name "DIFF9_P") (class "Default")
      (node (ref "D14") (pin "1") (pinfunction "K_1") (pintype "bidirectional"))
      (node (ref "J6") (pin "42") (pinfunction "42_42") (pintype "passive"))
      (node (ref "R25") (pin "2") (pinfunction "2_2") (pintype "bidirectional"))
    )
    (net (code "94") (name "DIFF10_N") (class "Default")
      (node (ref "C205") (pin "2") (pinfunction "2_2") (pintype "bidirectional"))
      (node (ref "D16") (pin "1") (pinfunction "K_1") (pintype "bidirectional"))
      (node (ref "IC38") (pin "52") (pinfunction "AIN_2GND_52") (pintype "input"))
      (node (ref "J6") (pin "50") (pinfunction "50_50") (pintype "passive"))
    )
    (net (code "95") (name "DIFF10_P") (class "Default")
      (node (ref "D17") (pin "1") (pinfunction "K_1") (pintype "bidirectional"))
      (node (ref "J6") (pin "48") (pinfunction "48_48") (pintype "passive"))
      (node (ref "R29") (pin "2") (pinfunction "2_2") (pintype "bidirectional"))
    )
    (net (code "96") (name "DIFF11_N") (class "Default")
      (node (ref "C211") (pin "2") (pinfunction "2_2") (pintype "bidirectional"))
      (node (ref "D19") (pin "1") (pinfunction "K_1") (pintype "bidirectional"))
      (node (ref "IC38") (pin "54") (pinfunction "AIN_3GND_54") (pintype "input"))
      (node (ref "J6") (pin "54") (pinfunction "54_54") (pintype "passive"))
    )
    (net (code "97") (name "DIFF11_P") (class "Default")
      (node (ref "D20") (pin "1") (pinfunction "K_1") (pintype "bidirectional"))
      (node (ref "J6") (pin "52") (pinfunction "52_52") (pintype "passive"))
      (node (ref "R73") (pin "2") (pinfunction "2_2") (pintype "bidirectional"))
    )
    (net (code "98") (name "DIFF12_N") (class "Default")
      (node (ref "C217") (pin "2") (pinfunction "2_2") (pintype "bidirectional"))
      (node (ref "D22") (pin "1") (pinfunction "K_1") (pintype "bidirectional"))
      (node (ref "IC38") (pin "56") (pinfunction "AIN_4GND_56") (pintype "input"))
      (node (ref "J6") (pin "60") (pinfunction "60_60") (pintype "passive"))
    )
    (net (code "99") (name "DIFF12_P") (class "Default")
      (node (ref "D23") (pin "1") (pinfunction "K_1") (pintype "bidirectional"))
      (node (ref "J6") (pin "58") (pinfunction "58_58") (pintype "passive"))
      (node (ref "R77") (pin "2") (pinfunction "2_2") (pintype "bidirectional"))
    )
    (net (code "100") (name "DIFF13_N") (class "Default")
      (node (ref "C223") (pin "2") (pinfunction "2_2") (pintype "bidirectional"))
      (node (ref "D49") (pin "1") (pinfunction "K_1") (pintype "bidirectional"))
      (node (ref "IC38") (pin "58") (pinfunction "AIN_5GND_58") (pintype "input"))
      (node (ref "J6") (pin "64") (pinfunction "64_64") (pintype "passive"))
    )
    (net (code "101") (name "DIFF13_P") (class "Default")
      (node (ref "D50") (pin "1") (pinfunction "K_1") (pintype "bidirectional"))
      (node (ref "J6") (pin "62") (pinfunction "62_62") (pintype "passive"))
      (node (ref "R81") (pin "2") (pinfunction "2_2") (pintype "bidirectional"))
    )
    (net (code "102") (name "DIFF14_N") (class "Default")
      (node (ref "C229") (pin "2") (pinfunction "2_2") (pintype "bidirectional"))
      (node (ref "D52") (pin "1") (pinfunction "K_1") (pintype "bidirectional"))
      (node (ref "IC38") (pin "60") (pinfunction "AIN_6GND_60") (pintype "input"))
      (node (ref "J6") (pin "70") (pinfunction "70_70") (pintype "passive"))
    )
    (net (code "103") (name "DIFF14_P") (class "Default")
      (node (ref "D53") (pin "1") (pinfunction "K_1") (pintype "bidirectional"))
      (node (ref "J6") (pin "68") (pinfunction "68_68") (pintype "passive"))
      (node (ref "R85") (pin "2") (pinfunction "2_2") (pintype "bidirectional"))
    )
    (net (code "104") (name "DIFF15_N") (class "Default")
      (node (ref "C235") (pin "2") (pinfunction "2_2") (pintype "bidirectional"))
      (node (ref "D55") (pin "1") (pinfunction "K_1") (pintype "bidirectional"))
      (node (ref "IC38") (pin "62") (pinfunction "AIN_7GND_62") (pintype "input"))
      (node (ref "J6") (pin "74") (pinfunction "74_74") (pintype "passive"))
    )
    (net (code "105") (name "DIFF15_P") (class "Default")
      (node (ref "D56") (pin "1") (pinfunction "K_1") (pintype "bidirectional"))
      (node (ref "J6") (pin "72") (pinfunction "72_72") (pintype "passive"))
      (node (ref "R98") (pin "2") (pinfunction "2_2") (pintype "bidirectional"))
    )
    (net (code "106") (name "DIFF16_N") (class "Default")
      (node (ref "C241") (pin "2") (pinfunction "2_2") (pintype "bidirectional"))
      (node (ref "D58") (pin "1") (pinfunction "K_1") (pintype "bidirectional"))
      (node (ref "IC38") (pin "64") (pinfunction "AIN_8GND_64") (pintype "input"))
      (node (ref "J6") (pin "80") (pinfunction "80_80") (pintype "passive"))
    )
    (net (code "107") (name "DIFF16_P") (class "Default")
      (node (ref "D59") (pin "1") (pinfunction "K_1") (pintype "bidirectional"))
      (node (ref "J6") (pin "78") (pinfunction "78_78") (pintype "passive"))
      (node (ref "R105") (pin "2") (pinfunction "2_2") (pintype "bidirectional"))
    )
    (net (code "108") (name "DIFF_GP1_N") (class "Default")
      (node (ref "C247") (pin "2") (pinfunction "2_2") (pintype "bidirectional"))
      (node (ref "D25") (pin "1") (pinfunction "K_1") (pintype "bidirectional"))
      (node (ref "IC52") (pin "50") (pinfunction "AIN_1GND_50") (pintype "input"))
      (node (ref "J6") (pin "04") (pinfunction "04_04") (pintype "passive"))
    )
    (net (code "109") (name "DIFF_GP1_P") (class "Default")
      (node (ref "D26") (pin "1") (pinfunction "K_1") (pintype "bidirectional"))
      (node (ref "J6") (pin "02") (pinfunction "02_02") (pintype "passive"))
      (node (ref "R109") (pin "2") (pinfunction "2_2") (pintype "bidirectional"))
    )
    (net (code "110") (name "DIFF_GP2_N") (class "Default")
      (node (ref "C253") (pin "2") (pinfunction "2_2") (pintype "bidirectional"))
      (node (ref "D28") (pin "1") (pinfunction "K_1") (pintype "bidirectional"))
      (node (ref "IC52") (pin "52") (pinfunction "AIN_2GND_52") (pintype "input"))
      (node (ref "J6") (pin "10") (pinfunction "10_10") (pintype "passive"))
    )
    (net (code "111") (name "DIFF_GP2_P") (class "Default")
      (node (ref "D29") (pin "1") (pinfunction "K_1") (pintype "bidirectional"))
      (node (ref "J6") (pin "08") (pinfunction "08_08") (pintype "passive"))
      (node (ref "R113") (pin "2") (pinfunction "2_2") (pintype "bidirectional"))
    )
    (net (code "112") (name "DIFF_GP3_N") (class "Default")
      (node (ref "C259") (pin "2") (pinfunction "2_2") (pintype "bidirectional"))
      (node (ref "D31") (pin "1") (pinfunction "K_1") (pintype "bidirectional"))
      (node (ref "IC52") (pin "54") (pinfunction "AIN_3GND_54") (pintype "input"))
      (node (ref "J6") (pin "14") (pinfunction "14_14") (pintype "passive"))
    )
    (net (code "113") (name "DIFF_GP3_P") (class "Default")
      (node (ref "D32") (pin "1") (pinfunction "K_1") (pintype "bidirectional"))
      (node (ref "J6") (pin "12") (pinfunction "12_12") (pintype "passive"))
      (node (ref "R159") (pin "2") (pinfunction "2_2") (pintype "bidirectional"))
    )
    (net (code "114") (name "DIFF_GP4_N") (class "Default")
      (node (ref "C265") (pin "2") (pinfunction "2_2") (pintype "bidirectional"))
      (node (ref "D34") (pin "1") (pinfunction "K_1") (pintype "bidirectional"))
      (node (ref "IC52") (pin "56") (pinfunction "AIN_4GND_56") (pintype "input"))
      (node (ref "J6") (pin "20") (pinfunction "20_20") (pintype "passive"))
    )
    (net (code "115") (name "DIFF_GP4_P") (class "Default")
      (node (ref "D35") (pin "1") (pinfunction "K_1") (pintype "bidirectional"))
      (node (ref "J6") (pin "18") (pinfunction "18_18") (pintype "passive"))
      (node (ref "R163") (pin "2") (pinfunction "2_2") (pintype "bidirectional"))
    )
    (net (code "116") (name "DIFF_GP5_N") (class "Default")
      (node (ref "C271") (pin "2") (pinfunction "2_2") (pintype "bidirectional"))
      (node (ref "D37") (pin "1") (pinfunction "K_1") (pintype "bidirectional"))
      (node (ref "IC52") (pin "58") (pinfunction "AIN_5GND_58") (pintype "input"))
      (node (ref "J6") (pin "24") (pinfunction "24_24") (pintype "passive"))
    )
    (net (code "117") (name "DIFF_GP5_P") (class "Default")
      (node (ref "D38") (pin "1") (pinfunction "K_1") (pintype "bidirectional"))
      (node (ref "J6") (pin "22") (pinfunction "22_22") (pintype "passive"))
      (node (ref "R207") (pin "2") (pinfunction "2_2") (pintype "bidirectional"))
    )
    (net (code "118") (name "DIN1") (class "Default")
      (node (ref "D74") (pin "1") (pinfunction "K_1") (pintype "bidirectional"))
      (node (ref "J5") (pin "66") (pinfunction "66_66") (pintype "passive"))
      (node (ref "LED85") (pin "2") (pinfunction "A_2") (pintype "bidirectional"))
      (node (ref "R36") (pin "2") (pinfunction "2_2") (pintype "bidirectional"))
    )
    (net (code "119") (name "DIN2") (class "Default")
      (node (ref "D73") (pin "1") (pinfunction "K_1") (pintype "bidirectional"))
      (node (ref "J5") (pin "68") (pinfunction "68_68") (pintype "passive"))
      (node (ref "LED86") (pin "2") (pinfunction "A_2") (pintype "bidirectional"))
      (node (ref "R34") (pin "2") (pinfunction "2_2") (pintype "bidirectional"))
    )
    (net (code "120") (name "DIN3") (class "Default")
      (node (ref "D77") (pin "1") (pinfunction "K_1") (pintype "bidirectional"))
      (node (ref "J5") (pin "70") (pinfunction "70_70") (pintype "passive"))
      (node (ref "LED87") (pin "2") (pinfunction "A_2") (pintype "bidirectional"))
      (node (ref "R38") (pin "2") (pinfunction "2_2") (pintype "bidirectional"))
    )
    (net (code "121") (name "DIN4") (class "Default")
      (node (ref "D76") (pin "1") (pinfunction "K_1") (pintype "bidirectional"))
      (node (ref "J5") (pin "72") (pinfunction "72_72") (pintype "passive"))
      (node (ref "LED88") (pin "2") (pinfunction "A_2") (pintype "bidirectional"))
      (node (ref "R40") (pin "2") (pinfunction "2_2") (pintype "bidirectional"))
    )
    (net (code "122") (name "DIN5") (class "Default")
      (node (ref "D44") (pin "1") (pinfunction "K_1") (pintype "bidirectional"))
      (node (ref "J5") (pin "74") (pinfunction "74_74") (pintype "passive"))
      (node (ref "LED89") (pin "2") (pinfunction "A_2") (pintype "bidirectional"))
      (node (ref "R44") (pin "2") (pinfunction "2_2") (pintype "bidirectional"))
    )
    (net (code "123") (name "DIN6") (class "Default")
      (node (ref "D43") (pin "1") (pinfunction "K_1") (pintype "bidirectional"))
      (node (ref "J5") (pin "76") (pinfunction "76_76") (pintype "passive"))
      (node (ref "LED90") (pin "2") (pinfunction "A_2") (pintype "bidirectional"))
      (node (ref "R46") (pin "2") (pinfunction "2_2") (pintype "bidirectional"))
    )
    (net (code "124") (name "DIN7") (class "Default")
      (node (ref "D47") (pin "1") (pinfunction "K_1") (pintype "bidirectional"))
      (node (ref "J5") (pin "78") (pinfunction "78_78") (pintype "passive"))
      (node (ref "LED91") (pin "2") (pinfunction "A_2") (pintype "bidirectional"))
      (node (ref "R48") (pin "2") (pinfunction "2_2") (pintype "bidirectional"))
    )
    (net (code "125") (name "DIN8") (class "Default")
      (node (ref "D46") (pin "1") (pinfunction "K_1") (pintype "bidirectional"))
      (node (ref "J5") (pin "80") (pinfunction "80_80") (pintype "passive"))
      (node (ref "LED92") (pin "2") (pinfunction "A_2") (pintype "bidirectional"))
      (node (ref "R50") (pin "2") (pinfunction "2_2") (pintype "bidirectional"))
    )
    (net (code "126") (name "DOUTA_ADC_1") (class "Default")
      (node (ref "DOUTA_ADC_1") (pin "TP") (pinfunction "TP_TP") (pintype "bidirectional"))
      (node (ref "IC51") (pin "24") (pinfunction "DB7/DOUTA_24") (pintype "output"))
      (node (ref "J4") (pin "61") (pinfunction "61_61") (pintype "passive"))
    )
    (net (code "127") (name "DOUTA_ADC_2") (class "Default")
      (node (ref "DOUTA_ADC_2") (pin "TP") (pinfunction "TP_TP") (pintype "bidirectional"))
      (node (ref "IC38") (pin "24") (pinfunction "DB7/DOUTA_24") (pintype "output"))
      (node (ref "J4") (pin "69") (pinfunction "69_69") (pintype "passive"))
    )
    (net (code "128") (name "DOUTA_ADC_3") (class "Default")
      (node (ref "DOUTA_ADC_3") (pin "TP") (pinfunction "TP_TP") (pintype "bidirectional"))
      (node (ref "IC52") (pin "24") (pinfunction "DB7/DOUTA_24") (pintype "output"))
      (node (ref "J4") (pin "77") (pinfunction "77_77") (pintype "passive"))
    )
    (net (code "129") (name "DOUTB_ADC_1") (class "Default")
      (node (ref "DOUTB_ADC_1") (pin "TP") (pinfunction "TP_TP") (pintype "bidirectional"))
      (node (ref "IC51") (pin "25") (pinfunction "DB8/DOUTB_25") (pintype "output"))
      (node (ref "J4") (pin "59") (pinfunction "59_59") (pintype "passive"))
    )
    (net (code "130") (name "DOUTB_ADC_2") (class "Default")
      (node (ref "DOUTB_ADC_2") (pin "TP") (pinfunction "TP_TP") (pintype "bidirectional"))
      (node (ref "IC38") (pin "25") (pinfunction "DB8/DOUTB_25") (pintype "output"))
      (node (ref "J4") (pin "67") (pinfunction "67_67") (pintype "passive"))
    )
    (net (code "131") (name "DOUTB_ADC_3") (class "Default")
      (node (ref "DOUTB_ADC_3") (pin "TP") (pinfunction "TP_TP") (pintype "bidirectional"))
      (node (ref "IC52") (pin "25") (pinfunction "DB8/DOUTB_25") (pintype "output"))
      (node (ref "J4") (pin "75") (pinfunction "75_75") (pintype "passive"))
    )
    (net (code "132") (name "D_SENSE1") (class "Default")
      (node (ref "C40") (pin "1") (pinfunction "1_1") (pintype "bidirectional"))
      (node (ref "D45") (pin "3") (pinfunction "DRAIN_3") (pintype "bidirectional"))
      (node (ref "DIN1") (pin "TP") (pinfunction "TP_TP") (pintype "bidirectional"))
      (node (ref "J4") (pin "66") (pinfunction "66_66") (pintype "passive"))
      (node (ref "R35") (pin "2") (pinfunction "2_2") (pintype "bidirectional"))
    )
    (net (code "133") (name "D_SENSE2") (class "Default")
      (node (ref "C38") (pin "1") (pinfunction "1_1") (pintype "bidirectional"))
      (node (ref "D48") (pin "3") (pinfunction "DRAIN_3") (pintype "bidirectional"))
      (node (ref "DIN2") (pin "TP") (pinfunction "TP_TP") (pintype "bidirectional"))
      (node (ref "J4") (pin "68") (pinfunction "68_68") (pintype "passive"))
      (node (ref "R33") (pin "2") (pinfunction "2_2") (pintype "bidirectional"))
    )
    (net (code "134") (name "D_SENSE3") (class "Default")
      (node (ref "C63") (pin "1") (pinfunction "1_1") (pintype "bidirectional"))
      (node (ref "D75") (pin "3") (pinfunction "DRAIN_3") (pintype "bidirectional"))
      (node (ref "DIN3") (pin "TP") (pinfunction "TP_TP") (pintype "bidirectional"))
      (node (ref "J4") (pin "70") (pinfunction "70_70") (pintype "passive"))
      (node (ref "R37") (pin "2") (pinfunction "2_2") (pintype "bidirectional"))
    )
    (net (code "135") (name "D_SENSE4") (class "Default")
      (node (ref "C64") (pin "1") (pinfunction "1_1") (pintype "bidirectional"))
      (node (ref "D78") (pin "3") (pinfunction "DRAIN_3") (pintype "bidirectional"))
      (node (ref "DIN4") (pin "TP") (pinfunction "TP_TP") (pintype "bidirectional"))
      (node (ref "J4") (pin "72") (pinfunction "72_72") (pintype "passive"))
      (node (ref "R39") (pin "2") (pinfunction "2_2") (pintype "bidirectional"))
    )
    (net (code "136") (name "D_SENSE5") (class "Default")
      (node (ref "C66") (pin "1") (pinfunction "1_1") (pintype "bidirectional"))
      (node (ref "D79") (pin "3") (pinfunction "DRAIN_3") (pintype "bidirectional"))
      (node (ref "DIN5") (pin "TP") (pinfunction "TP_TP") (pintype "bidirectional"))
      (node (ref "J4") (pin "74") (pinfunction "74_74") (pintype "passive"))
      (node (ref "R43") (pin "2") (pinfunction "2_2") (pintype "bidirectional"))
    )
    (net (code "137") (name "D_SENSE6") (class "Default")
      (node (ref "C67") (pin "1") (pinfunction "1_1") (pintype "bidirectional"))
      (node (ref "D80") (pin "3") (pinfunction "DRAIN_3") (pintype "bidirectional"))
      (node (ref "DIN6") (pin "TP") (pinfunction "TP_TP") (pintype "bidirectional"))
      (node (ref "J4") (pin "76") (pinfunction "76_76") (pintype "passive"))
      (node (ref "R45") (pin "2") (pinfunction "2_2") (pintype "bidirectional"))
    )
    (net (code "138") (name "D_SENSE7") (class "Default")
      (node (ref "C68") (pin "1") (pinfunction "1_1") (pintype "bidirectional"))
      (node (ref "D81") (pin "3") (pinfunction "DRAIN_3") (pintype "bidirectional"))
      (node (ref "DIN7") (pin "TP") (pinfunction "TP_TP") (pintype "bidirectional"))
      (node (ref "J4") (pin "78") (pinfunction "78_78") (pintype "passive"))
      (node (ref "R47") (pin "2") (pinfunction "2_2") (pintype "bidirectional"))
    )
    (net (code "139") (name "D_SENSE8") (class "Default")
      (node (ref "C69") (pin "1") (pinfunction "1_1") (pintype "bidirectional"))
      (node (ref "D82") (pin "3") (pinfunction "DRAIN_3") (pintype "bidirectional"))
      (node (ref "DIN8") (pin "TP") (pinfunction "TP_TP") (pintype "bidirectional"))
      (node (ref "J4") (pin "80") (pinfunction "80_80") (pintype "passive"))
      (node (ref "R49") (pin "2") (pinfunction "2_2") (pintype "bidirectional"))
    )
    (net (code "140") (name "ETH_CRS_DV") (class "Default")
      (node (ref "UC1") (pin "PA7") (pinfunction "PA7_PA7") (pintype "passive"))
    )
    (net (code "141") (name "ETH_MDC") (class "Default")
      (node (ref "UC1") (pin "PC1") (pinfunction "PC1_PC1") (pintype "passive"))
    )
    (net (code "142") (name "ETH_MDIO") (class "Default")
      (node (ref "UC1") (pin "PA2") (pinfunction "PA2_PA2") (pintype "passive"))
    )
    (net (code "143") (name "ETH_REF_CLK") (class "Default")
      (node (ref "UC1") (pin "PA1") (pinfunction "PA1_PA1") (pintype "passive"))
    )
    (net (code "144") (name "ETH_RXD0") (class "Default")
      (node (ref "UC1") (pin "PC4") (pinfunction "PC4_PC4") (pintype "passive"))
    )
    (net (code "145") (name "ETH_RXD1") (class "Default")
      (node (ref "UC1") (pin "PC5") (pinfunction "PC5_PC5") (pintype "passive"))
    )
    (net (code "146") (name "ETH_TXD0") (class "Default")
      (node (ref "UC1") (pin "PG13") (pinfunction "PG13_PG13") (pintype "passive"))
    )
    (net (code "147") (name "ETH_TXD1") (class "Default")
      (node (ref "UC1") (pin "PB13") (pinfunction "PB13_PB13") (pintype "passive"))
    )
    (net (code "148") (name "ETH_TX_EN") (class "Default")
      (node (ref "UC1") (pin "PG11") (pinfunction "PG11_PG11") (pintype "passive"))
    )
    (net (code "149") (name "FB+_1") (class "Default")
      (node (ref "IC24") (pin "3") (pinfunction "IN+_3") (pintype "bidirectional"))
      (node (ref "R477") (pin "1") (pinfunction "1_1") (pintype "bidirectional"))
      (node (ref "R479") (pin "1") (pinfunction "1_1") (pintype "bidirectional"))
    )
    (net (code "150") (name "FB+_2") (class "Default")
      (node (ref "IC25") (pin "3") (pinfunction "IN+_3") (pintype "bidirectional"))
      (node (ref "R486") (pin "1") (pinfunction "1_1") (pintype "bidirectional"))
      (node (ref "R488") (pin "1") (pinfunction "1_1") (pintype "bidirectional"))
    )
    (net (code "151") (name "FB+_3") (class "Default")
      (node (ref "IC26") (pin "3") (pinfunction "IN+_3") (pintype "bidirectional"))
      (node (ref "R495") (pin "1") (pinfunction "1_1") (pintype "bidirectional"))
      (node (ref "R497") (pin "1") (pinfunction "1_1") (pintype "bidirectional"))
    )
    (net (code "152") (name "FB-_1") (class "Default")
      (node (ref "IC24") (pin "4") (pinfunction "IN-_4") (pintype "bidirectional"))
      (node (ref "R478") (pin "1") (pinfunction "1_1") (pintype "bidirectional"))
      (node (ref "R480") (pin "1") (pinfunction "1_1") (pintype "bidirectional"))
    )
    (net (code "153") (name "FB-_2") (class "Default")
      (node (ref "IC25") (pin "4") (pinfunction "IN-_4") (pintype "bidirectional"))
      (node (ref "R487") (pin "1") (pinfunction "1_1") (pintype "bidirectional"))
      (node (ref "R489") (pin "1") (pinfunction "1_1") (pintype "bidirectional"))
    )
    (net (code "154") (name "FB-_3") (class "Default")
      (node (ref "IC26") (pin "4") (pinfunction "IN-_4") (pintype "bidirectional"))
      (node (ref "R496") (pin "1") (pinfunction "1_1") (pintype "bidirectional"))
      (node (ref "R498") (pin "1") (pinfunction "1_1") (pintype "bidirectional"))
    )
    (net (code "155") (name "FB1_") (class "Default")
      (node (ref "IC4") (pin "26") (pinfunction "FB1_26") (pintype "bidirectional"))
      (node (ref "R95") (pin "2") (pinfunction "2_2") (pintype "bidirectional"))
      (node (ref "R96") (pin "2") (pinfunction "2_2") (pintype "bidirectional"))
    )
    (net (code "156") (name "FB1_0") (class "Default")
      (node (ref "IC11") (pin "26") (pinfunction "FB1_26") (pintype "bidirectional"))
      (node (ref "R142") (pin "2") (pinfunction "2_2") (pintype "bidirectional"))
      (node (ref "R143") (pin "2") (pinfunction "2_2") (pintype "bidirectional"))
    )
    (net (code "157") (name "FB1_1") (class "Default")
      (node (ref "IC20") (pin "26") (pinfunction "FB1_26") (pintype "bidirectional"))
      (node (ref "R367") (pin "2") (pinfunction "2_2") (pintype "bidirectional"))
      (node (ref "R368") (pin "2") (pinfunction "2_2") (pintype "bidirectional"))
    )
    (net (code "158") (name "FB1_2") (class "Default")
      (node (ref "IC21") (pin "26") (pinfunction "FB1_26") (pintype "bidirectional"))
      (node (ref "R388") (pin "2") (pinfunction "2_2") (pintype "bidirectional"))
      (node (ref "R389") (pin "2") (pinfunction "2_2") (pintype "bidirectional"))
    )
    (net (code "159") (name "FB1_3") (class "Default")
      (node (ref "IC12") (pin "26") (pinfunction "FB1_26") (pintype "bidirectional"))
      (node (ref "R180") (pin "2") (pinfunction "2_2") (pintype "bidirectional"))
      (node (ref "R181") (pin "2") (pinfunction "2_2") (pintype "bidirectional"))
    )
    (net (code "160") (name "FB1_4") (class "Default")
      (node (ref "IC13") (pin "26") (pinfunction "FB1_26") (pintype "bidirectional"))
      (node (ref "R202") (pin "2") (pinfunction "2_2") (pintype "bidirectional"))
      (node (ref "R204") (pin "2") (pinfunction "2_2") (pintype "bidirectional"))
    )
    (net (code "161") (name "FB1_5") (class "Default")
      (node (ref "IC18") (pin "26") (pinfunction "FB1_26") (pintype "bidirectional"))
      (node (ref "R325") (pin "2") (pinfunction "2_2") (pintype "bidirectional"))
      (node (ref "R326") (pin "2") (pinfunction "2_2") (pintype "bidirectional"))
    )
    (net (code "162") (name "FB1_6") (class "Default")
      (node (ref "IC19") (pin "26") (pinfunction "FB1_26") (pintype "bidirectional"))
      (node (ref "R346") (pin "2") (pinfunction "2_2") (pintype "bidirectional"))
      (node (ref "R347") (pin "2") (pinfunction "2_2") (pintype "bidirectional"))
    )
    (net (code "163") (name "FB1_7") (class "Default")
      (node (ref "IC14") (pin "26") (pinfunction "FB1_26") (pintype "bidirectional"))
      (node (ref "R241") (pin "2") (pinfunction "2_2") (pintype "bidirectional"))
      (node (ref "R242") (pin "2") (pinfunction "2_2") (pintype "bidirectional"))
    )
    (net (code "164") (name "FB1_8") (class "Default")
      (node (ref "IC15") (pin "26") (pinfunction "FB1_26") (pintype "bidirectional"))
      (node (ref "R262") (pin "2") (pinfunction "2_2") (pintype "bidirectional"))
      (node (ref "R263") (pin "2") (pinfunction "2_2") (pintype "bidirectional"))
    )
    (net (code "165") (name "FB1_9") (class "Default")
      (node (ref "IC16") (pin "26") (pinfunction "FB1_26") (pintype "bidirectional"))
      (node (ref "R283") (pin "2") (pinfunction "2_2") (pintype "bidirectional"))
      (node (ref "R284") (pin "2") (pinfunction "2_2") (pintype "bidirectional"))
    )
    (net (code "166") (name "FB1_10") (class "Default")
      (node (ref "IC17") (pin "26") (pinfunction "FB1_26") (pintype "bidirectional"))
      (node (ref "R304") (pin "2") (pinfunction "2_2") (pintype "bidirectional"))
      (node (ref "R305") (pin "2") (pinfunction "2_2") (pintype "bidirectional"))
    )
    (net (code "167") (name "FB1_11") (class "Default")
      (node (ref "IC22") (pin "26") (pinfunction "FB1_26") (pintype "bidirectional"))
      (node (ref "R409") (pin "2") (pinfunction "2_2") (pintype "bidirectional"))
      (node (ref "R410") (pin "2") (pinfunction "2_2") (pintype "bidirectional"))
    )
    (net (code "168") (name "FB1_12") (class "Default")
      (node (ref "IC23") (pin "26") (pinfunction "FB1_26") (pintype "bidirectional"))
      (node (ref "R430") (pin "2") (pinfunction "2_2") (pintype "bidirectional"))
      (node (ref "R431") (pin "2") (pinfunction "2_2") (pintype "bidirectional"))
    )
    (net (code "169") (name "FB2_") (class "Default")
      (node (ref "IC4") (pin "15") (pinfunction "FB2_15") (pintype "bidirectional"))
      (node (ref "R132") (pin "2") (pinfunction "2_2") (pintype "bidirectional"))
      (node (ref "R133") (pin "2") (pinfunction "2_2") (pintype "bidirectional"))
    )
    (net (code "170") (name "FB2_0") (class "Default")
      (node (ref "IC11") (pin "15") (pinfunction "FB2_15") (pintype "bidirectional"))
      (node (ref "R170") (pin "2") (pinfunction "2_2") (pintype "bidirectional"))
      (node (ref "R171") (pin "2") (pinfunction "2_2") (pintype "bidirectional"))
    )
    (net (code "171") (name "FB2_1") (class "Default")
      (node (ref "IC20") (pin "15") (pinfunction "FB2_15") (pintype "bidirectional"))
      (node (ref "R378") (pin "2") (pinfunction "2_2") (pintype "bidirectional"))
      (node (ref "R379") (pin "2") (pinfunction "2_2") (pintype "bidirectional"))
    )
    (net (code "172") (name "FB2_2") (class "Default")
      (node (ref "IC21") (pin "15") (pinfunction "FB2_15") (pintype "bidirectional"))
      (node (ref "R399") (pin "2") (pinfunction "2_2") (pintype "bidirectional"))
      (node (ref "R400") (pin "2") (pinfunction "2_2") (pintype "bidirectional"))
    )
    (net (code "173") (name "FB2_3") (class "Default")
      (node (ref "IC12") (pin "15") (pinfunction "FB2_15") (pintype "bidirectional"))
      (node (ref "R191") (pin "2") (pinfunction "2_2") (pintype "bidirectional"))
      (node (ref "R192") (pin "2") (pinfunction "2_2") (pintype "bidirectional"))
    )
    (net (code "174") (name "FB2_4") (class "Default")
      (node (ref "IC13") (pin "15") (pinfunction "FB2_15") (pintype "bidirectional"))
      (node (ref "R218") (pin "2") (pinfunction "2_2") (pintype "bidirectional"))
      (node (ref "R219") (pin "2") (pinfunction "2_2") (pintype "bidirectional"))
    )
    (net (code "175") (name "FB2_5") (class "Default")
      (node (ref "IC18") (pin "15") (pinfunction "FB2_15") (pintype "bidirectional"))
      (node (ref "R336") (pin "2") (pinfunction "2_2") (pintype "bidirectional"))
      (node (ref "R337") (pin "2") (pinfunction "2_2") (pintype "bidirectional"))
    )
    (net (code "176") (name "FB2_6") (class "Default")
      (node (ref "IC19") (pin "15") (pinfunction "FB2_15") (pintype "bidirectional"))
      (node (ref "R357") (pin "2") (pinfunction "2_2") (pintype "bidirectional"))
      (node (ref "R358") (pin "2") (pinfunction "2_2") (pintype "bidirectional"))
    )
    (net (code "177") (name "FB2_7") (class "Default")
      (node (ref "IC14") (pin "15") (pinfunction "FB2_15") (pintype "bidirectional"))
      (node (ref "R252") (pin "2") (pinfunction "2_2") (pintype "bidirectional"))
      (node (ref "R253") (pin "2") (pinfunction "2_2") (pintype "bidirectional"))
    )
    (net (code "178") (name "FB2_8") (class "Default")
      (node (ref "IC15") (pin "15") (pinfunction "FB2_15") (pintype "bidirectional"))
      (node (ref "R273") (pin "2") (pinfunction "2_2") (pintype "bidirectional"))
      (node (ref "R274") (pin "2") (pinfunction "2_2") (pintype "bidirectional"))
    )
    (net (code "179") (name "FB2_9") (class "Default")
      (node (ref "IC16") (pin "15") (pinfunction "FB2_15") (pintype "bidirectional"))
      (node (ref "R294") (pin "2") (pinfunction "2_2") (pintype "bidirectional"))
      (node (ref "R295") (pin "2") (pinfunction "2_2") (pintype "bidirectional"))
    )
    (net (code "180") (name "FB2_10") (class "Default")
      (node (ref "IC17") (pin "15") (pinfunction "FB2_15") (pintype "bidirectional"))
      (node (ref "R315") (pin "2") (pinfunction "2_2") (pintype "bidirectional"))
      (node (ref "R316") (pin "2") (pinfunction "2_2") (pintype "bidirectional"))
    )
    (net (code "181") (name "FB2_11") (class "Default")
      (node (ref "IC22") (pin "15") (pinfunction "FB2_15") (pintype "bidirectional"))
      (node (ref "R420") (pin "2") (pinfunction "2_2") (pintype "bidirectional"))
      (node (ref "R421") (pin "2") (pinfunction "2_2") (pintype "bidirectional"))
    )
    (net (code "182") (name "FB2_12") (class "Default")
      (node (ref "IC23") (pin "15") (pinfunction "FB2_15") (pintype "bidirectional"))
      (node (ref "R441") (pin "2") (pinfunction "2_2") (pintype "bidirectional"))
      (node (ref "R442") (pin "2") (pinfunction "2_2") (pintype "bidirectional"))
    )
    (net (code "183") (name "FIRSTDATA_ADC_1") (class "Default")
      (node (ref "FSTD_ADC_1") (pin "TP") (pinfunction "TP_TP") (pintype "bidirectional"))
      (node (ref "IC51") (pin "15") (pinfunction "FRSTDATA_15") (pintype "output"))
      (node (ref "J4") (pin "57") (pinfunction "57_57") (pintype "passive"))
    )
    (net (code "184") (name "FIRSTDATA_ADC_2") (class "Default")
      (node (ref "FSTD_ADC_2") (pin "TP") (pinfunction "TP_TP") (pintype "bidirectional"))
      (node (ref "IC38") (pin "15") (pinfunction "FRSTDATA_15") (pintype "output"))
      (node (ref "J4") (pin "65") (pinfunction "65_65") (pintype "passive"))
    )
    (net (code "185") (name "FIRSTDATA_ADC_3") (class "Default")
      (node (ref "FSTD_ADC_3") (pin "TP") (pinfunction "TP_TP") (pintype "bidirectional"))
      (node (ref "IC52") (pin "15") (pinfunction "FRSTDATA_15") (pintype "output"))
      (node (ref "J4") (pin "73") (pinfunction "73_73") (pintype "passive"))
    )
    (net (code "186") (name "FIX_NC") (class "Default")
      (node (ref "J9") (pin "06") (pinfunction "06_06") (pintype "passive"))
    )
    (net (code "187") (name "FLASH_CD{slash}DAT3_SPI-CS") (class "Default")
      (node (ref "CD/DAT3_SPI-CS") (pin "TP") (pinfunction "TP_TP") (pintype "bidirectional"))
      (node (ref "J3") (pin "P2") (pinfunction "CD/DAT3_P2") (pintype "bidirectional"))
      (node (ref "J4") (pin "08") (pinfunction "08_08") (pintype "passive"))
    )
    (net (code "188") (name "FLASH_CLK") (class "Default")
      (node (ref "CLK") (pin "TP") (pinfunction "TP_TP") (pintype "bidirectional"))
      (node (ref "J3") (pin "P5") (pinfunction "CLK_P5") (pintype "bidirectional"))
      (node (ref "J4") (pin "12") (pinfunction "12_12") (pintype "passive"))
    )
    (net (code "189") (name "FLASH_CMD_SPI-DI") (class "Default")
      (node (ref "CMD_SPI-DI") (pin "TP") (pinfunction "TP_TP") (pintype "bidirectional"))
      (node (ref "J3") (pin "P3") (pinfunction "CMD_P3") (pintype "bidirectional"))
      (node (ref "J4") (pin "10") (pinfunction "10_10") (pintype "passive"))
    )
    (net (code "190") (name "FLASH_DAT0_SPI-DO") (class "Default")
      (node (ref "DAT_SPI-DO") (pin "TP") (pinfunction "TP_TP") (pintype "bidirectional"))
      (node (ref "J3") (pin "P7") (pinfunction "DAT0_P7") (pintype "bidirectional"))
      (node (ref "J4") (pin "02") (pinfunction "02_02") (pintype "passive"))
    )
    (net (code "191") (name "FLASH_DAT1") (class "Default")
      (node (ref "DAT1") (pin "TP") (pinfunction "TP_TP") (pintype "bidirectional"))
      (node (ref "J3") (pin "P8") (pinfunction "DAT1_P8") (pintype "bidirectional"))
      (node (ref "J4") (pin "04") (pinfunction "04_04") (pintype "passive"))
    )
    (net (code "192") (name "FLASH_DAT2") (class "Default")
      (node (ref "DAT2") (pin "TP") (pinfunction "TP_TP") (pintype "bidirectional"))
      (node (ref "J3") (pin "P1") (pinfunction "DAT2_P1") (pintype "bidirectional"))
      (node (ref "J4") (pin "06") (pinfunction "06_06") (pintype "passive"))
    )
    (net (code "193") (name "GATE1_") (class "Default")
      (node (ref "IC4") (pin "28") (pinfunction "GATE1_28") (pintype "bidirectional"))
      (node (ref "R93") (pin "2") (pinfunction "2_2") (pintype "bidirectional"))
      (node (ref "R94") (pin "2") (pinfunction "2_2") (pintype "bidirectional"))
    )
    (net (code "194") (name "GATE1_0") (class "Default")
      (node (ref "IC11") (pin "28") (pinfunction "GATE1_28") (pintype "bidirectional"))
      (node (ref "R140") (pin "2") (pinfunction "2_2") (pintype "bidirectional"))
      (node (ref "R141") (pin "2") (pinfunction "2_2") (pintype "bidirectional"))
    )
    (net (code "195") (name "GATE1_1") (class "Default")
      (node (ref "IC20") (pin "28") (pinfunction "GATE1_28") (pintype "bidirectional"))
      (node (ref "R365") (pin "2") (pinfunction "2_2") (pintype "bidirectional"))
      (node (ref "R366") (pin "2") (pinfunction "2_2") (pintype "bidirectional"))
    )
    (net (code "196") (name "GATE1_2") (class "Default")
      (node (ref "IC21") (pin "28") (pinfunction "GATE1_28") (pintype "bidirectional"))
      (node (ref "R386") (pin "2") (pinfunction "2_2") (pintype "bidirectional"))
      (node (ref "R387") (pin "2") (pinfunction "2_2") (pintype "bidirectional"))
    )
    (net (code "197") (name "GATE1_3") (class "Default")
      (node (ref "IC12") (pin "28") (pinfunction "GATE1_28") (pintype "bidirectional"))
      (node (ref "R178") (pin "2") (pinfunction "2_2") (pintype "bidirectional"))
      (node (ref "R179") (pin "2") (pinfunction "2_2") (pintype "bidirectional"))
    )
    (net (code "198") (name "GATE1_4") (class "Default")
      (node (ref "IC13") (pin "28") (pinfunction "GATE1_28") (pintype "bidirectional"))
      (node (ref "R199") (pin "2") (pinfunction "2_2") (pintype "bidirectional"))
      (node (ref "R200") (pin "2") (pinfunction "2_2") (pintype "bidirectional"))
    )
    (net (code "199") (name "GATE1_5") (class "Default")
      (node (ref "IC18") (pin "28") (pinfunction "GATE1_28") (pintype "bidirectional"))
      (node (ref "R323") (pin "2") (pinfunction "2_2") (pintype "bidirectional"))
      (node (ref "R324") (pin "2") (pinfunction "2_2") (pintype "bidirectional"))
    )
    (net (code "200") (name "GATE1_6") (class "Default")
      (node (ref "IC19") (pin "28") (pinfunction "GATE1_28") (pintype "bidirectional"))
      (node (ref "R344") (pin "2") (pinfunction "2_2") (pintype "bidirectional"))
      (node (ref "R345") (pin "2") (pinfunction "2_2") (pintype "bidirectional"))
    )
    (net (code "201") (name "GATE1_7") (class "Default")
      (node (ref "IC14") (pin "28") (pinfunction "GATE1_28") (pintype "bidirectional"))
      (node (ref "R228") (pin "2") (pinfunction "2_2") (pintype "bidirectional"))
      (node (ref "R240") (pin "2") (pinfunction "2_2") (pintype "bidirectional"))
    )
    (net (code "202") (name "GATE1_8") (class "Default")
      (node (ref "IC15") (pin "28") (pinfunction "GATE1_28") (pintype "bidirectional"))
      (node (ref "R260") (pin "2") (pinfunction "2_2") (pintype "bidirectional"))
      (node (ref "R261") (pin "2") (pinfunction "2_2") (pintype "bidirectional"))
    )
    (net (code "203") (name "GATE1_9") (class "Default")
      (node (ref "IC16") (pin "28") (pinfunction "GATE1_28") (pintype "bidirectional"))
      (node (ref "R281") (pin "2") (pinfunction "2_2") (pintype "bidirectional"))
      (node (ref "R282") (pin "2") (pinfunction "2_2") (pintype "bidirectional"))
    )
    (net (code "204") (name "GATE1_10") (class "Default")
      (node (ref "IC17") (pin "28") (pinfunction "GATE1_28") (pintype "bidirectional"))
      (node (ref "R302") (pin "2") (pinfunction "2_2") (pintype "bidirectional"))
      (node (ref "R303") (pin "2") (pinfunction "2_2") (pintype "bidirectional"))
    )
    (net (code "205") (name "GATE1_11") (class "Default")
      (node (ref "IC22") (pin "28") (pinfunction "GATE1_28") (pintype "bidirectional"))
      (node (ref "R407") (pin "2") (pinfunction "2_2") (pintype "bidirectional"))
      (node (ref "R408") (pin "2") (pinfunction "2_2") (pintype "bidirectional"))
    )
    (net (code "206") (name "GATE1_12") (class "Default")
      (node (ref "IC23") (pin "28") (pinfunction "GATE1_28") (pintype "bidirectional"))
      (node (ref "R428") (pin "2") (pinfunction "2_2") (pintype "bidirectional"))
      (node (ref "R429") (pin "2") (pinfunction "2_2") (pintype "bidirectional"))
    )
    (net (code "207") (name "GATE2_") (class "Default")
      (node (ref "IC4") (pin "13") (pinfunction "GATE2_13") (pintype "bidirectional"))
      (node (ref "R130") (pin "2") (pinfunction "2_2") (pintype "bidirectional"))
      (node (ref "R131") (pin "2") (pinfunction "2_2") (pintype "bidirectional"))
    )
    (net (code "208") (name "GATE2_0") (class "Default")
      (node (ref "IC11") (pin "13") (pinfunction "GATE2_13") (pintype "bidirectional"))
      (node (ref "R168") (pin "2") (pinfunction "2_2") (pintype "bidirectional"))
      (node (ref "R169") (pin "2") (pinfunction "2_2") (pintype "bidirectional"))
    )
    (net (code "209") (name "GATE2_1") (class "Default")
      (node (ref "IC20") (pin "13") (pinfunction "GATE2_13") (pintype "bidirectional"))
      (node (ref "R376") (pin "2") (pinfunction "2_2") (pintype "bidirectional"))
      (node (ref "R377") (pin "2") (pinfunction "2_2") (pintype "bidirectional"))
    )
    (net (code "210") (name "GATE2_2") (class "Default")
      (node (ref "IC21") (pin "13") (pinfunction "GATE2_13") (pintype "bidirectional"))
      (node (ref "R397") (pin "2") (pinfunction "2_2") (pintype "bidirectional"))
      (node (ref "R398") (pin "2") (pinfunction "2_2") (pintype "bidirectional"))
    )
    (net (code "211") (name "GATE2_3") (class "Default")
      (node (ref "IC12") (pin "13") (pinfunction "GATE2_13") (pintype "bidirectional"))
      (node (ref "R189") (pin "2") (pinfunction "2_2") (pintype "bidirectional"))
      (node (ref "R190") (pin "2") (pinfunction "2_2") (pintype "bidirectional"))
    )
    (net (code "212") (name "GATE2_4") (class "Default")
      (node (ref "IC13") (pin "13") (pinfunction "GATE2_13") (pintype "bidirectional"))
      (node (ref "R216") (pin "2") (pinfunction "2_2") (pintype "bidirectional"))
      (node (ref "R217") (pin "2") (pinfunction "2_2") (pintype "bidirectional"))
    )
    (net (code "213") (name "GATE2_5") (class "Default")
      (node (ref "IC18") (pin "13") (pinfunction "GATE2_13") (pintype "bidirectional"))
      (node (ref "R334") (pin "2") (pinfunction "2_2") (pintype "bidirectional"))
      (node (ref "R335") (pin "2") (pinfunction "2_2") (pintype "bidirectional"))
    )
    (net (code "214") (name "GATE2_6") (class "Default")
      (node (ref "IC19") (pin "13") (pinfunction "GATE2_13") (pintype "bidirectional"))
      (node (ref "R355") (pin "2") (pinfunction "2_2") (pintype "bidirectional"))
      (node (ref "R356") (pin "2") (pinfunction "2_2") (pintype "bidirectional"))
    )
    (net (code "215") (name "GATE2_7") (class "Default")
      (node (ref "IC14") (pin "13") (pinfunction "GATE2_13") (pintype "bidirectional"))
      (node (ref "R250") (pin "2") (pinfunction "2_2") (pintype "bidirectional"))
      (node (ref "R251") (pin "2") (pinfunction "2_2") (pintype "bidirectional"))
    )
    (net (code "216") (name "GATE2_8") (class "Default")
      (node (ref "IC15") (pin "13") (pinfunction "GATE2_13") (pintype "bidirectional"))
      (node (ref "R271") (pin "2") (pinfunction "2_2") (pintype "bidirectional"))
      (node (ref "R272") (pin "2") (pinfunction "2_2") (pintype "bidirectional"))
    )
    (net (code "217") (name "GATE2_9") (class "Default")
      (node (ref "IC16") (pin "13") (pinfunction "GATE2_13") (pintype "bidirectional"))
      (node (ref "R292") (pin "2") (pinfunction "2_2") (pintype "bidirectional"))
      (node (ref "R293") (pin "2") (pinfunction "2_2") (pintype "bidirectional"))
    )
    (net (code "218") (name "GATE2_10") (class "Default")
      (node (ref "IC17") (pin "13") (pinfunction "GATE2_13") (pintype "bidirectional"))
      (node (ref "R313") (pin "2") (pinfunction "2_2") (pintype "bidirectional"))
      (node (ref "R314") (pin "2") (pinfunction "2_2") (pintype "bidirectional"))
    )
    (net (code "219") (name "GATE2_11") (class "Default")
      (node (ref "IC22") (pin "13") (pinfunction "GATE2_13") (pintype "bidirectional"))
      (node (ref "R418") (pin "2") (pinfunction "2_2") (pintype "bidirectional"))
      (node (ref "R419") (pin "2") (pinfunction "2_2") (pintype "bidirectional"))
    )
    (net (code "220") (name "GATE2_12") (class "Default")
      (node (ref "IC23") (pin "13") (pinfunction "GATE2_13") (pintype "bidirectional"))
      (node (ref "R439") (pin "2") (pinfunction "2_2") (pintype "bidirectional"))
      (node (ref "R440") (pin "2") (pinfunction "2_2") (pintype "bidirectional"))
    )
    (net (code "221") (name "GND") (class "Default")
      (node (ref "C1") (pin "2") (pinfunction "2_2") (pintype "bidirectional"))
      (node (ref "C10") (pin "1") (pinfunction "1_1") (pintype "bidirectional"))
      (node (ref "C100") (pin "1") (pinfunction "1_1") (pintype "bidirectional"))
      (node (ref "C101") (pin "2") (pinfunction "2_2") (pintype "bidirectional"))
      (node (ref "C102") (pin "1") (pinfunction "1_1") (pintype "bidirectional"))
      (node (ref "C103") (pin "1") (pinfunction "1_1") (pintype "bidirectional"))
      (node (ref "C104") (pin "1") (pinfunction "1_1") (pintype "bidirectional"))
      (node (ref "C105") (pin "1") (pinfunction "1_1") (pintype "bidirectional"))
      (node (ref "C106") (pin "1") (pinfunction "1_1") (pintype "bidirectional"))
      (node (ref "C107") (pin "2") (pinfunction "2_2") (pintype "bidirectional"))
      (node (ref "C108") (pin "1") (pinfunction "1_1") (pintype "bidirectional"))
      (node (ref "C109") (pin "1") (pinfunction "1_1") (pintype "bidirectional"))
      (node (ref "C11") (pin "1") (pinfunction "1_1") (pintype "bidirectional"))
      (node (ref "C110") (pin "1") (pinfunction "1_1") (pintype "bidirectional"))
      (node (ref "C111") (pin "2") (pinfunction "2_2") (pintype "bidirectional"))
      (node (ref "C112") (pin "2") (pinfunction "2_2") (pintype "bidirectional"))
      (node (ref "C113") (pin "2") (pinfunction "2_2") (pintype "bidirectional"))
      (node (ref "C114") (pin "2") (pinfunction "2_2") (pintype "bidirectional"))
      (node (ref "C115") (pin "2") (pinfunction "2_2") (pintype "bidirectional"))
      (node (ref "C116") (pin "2") (pinfunction "2_2") (pintype "bidirectional"))
      (node (ref "C117") (pin "2") (pinfunction "2_2") (pintype "bidirectional"))
      (node (ref "C118") (pin "2") (pinfunction "2_2") (pintype "bidirectional"))
      (node (ref "C119") (pin "2") (pinfunction "2_2") (pintype "bidirectional"))
      (node (ref "C12") (pin "1") (pinfunction "1_1") (pintype "bidirectional"))
      (node (ref "C120") (pin "2") (pinfunction "2_2") (pintype "bidirectional"))
      (node (ref "C121") (pin "2") (pinfunction "2_2") (pintype "bidirectional"))
      (node (ref "C122") (pin "2") (pinfunction "2_2") (pintype "bidirectional"))
      (node (ref "C123") (pin "2") (pinfunction "2_2") (pintype "bidirectional"))
      (node (ref "C124") (pin "2") (pinfunction "2_2") (pintype "bidirectional"))
      (node (ref "C125") (pin "2") (pinfunction "2_2") (pintype "bidirectional"))
      (node (ref "C126") (pin "2") (pinfunction "2_2") (pintype "bidirectional"))
      (node (ref "C127") (pin "2") (pinfunction "2_2") (pintype "bidirectional"))
      (node (ref "C128") (pin "2") (pinfunction "2_2") (pintype "bidirectional"))
      (node (ref "C129") (pin "2") (pinfunction "2_2") (pintype "bidirectional"))
      (node (ref "C13") (pin "2") (pinfunction "2_2") (pintype "bidirectional"))
      (node (ref "C130") (pin "2") (pinfunction "2_2") (pintype "bidirectional"))
      (node (ref "C131") (pin "2") (pinfunction "2_2") (pintype "bidirectional"))
      (node (ref "C132") (pin "2") (pinfunction "2_2") (pintype "bidirectional"))
      (node (ref "C133") (pin "2") (pinfunction "2_2") (pintype "bidirectional"))
      (node (ref "C134") (pin "2") (pinfunction "2_2") (pintype "bidirectional"))
      (node (ref "C135") (pin "2") (pinfunction "2_2") (pintype "bidirectional"))
      (node (ref "C136") (pin "2") (pinfunction "2_2") (pintype "bidirectional"))
      (node (ref "C137") (pin "2") (pinfunction "2_2") (pintype "bidirectional"))
      (node (ref "C138") (pin "2") (pinfunction "2_2") (pintype "bidirectional"))
      (node (ref "C139") (pin "2") (pinfunction "2_2") (pintype "bidirectional"))
      (node (ref "C14") (pin "1") (pinfunction "1_1") (pintype "bidirectional"))
      (node (ref "C140") (pin "2") (pinfunction "2_2") (pintype "bidirectional"))
      (node (ref "C141") (pin "2") (pinfunction "2_2") (pintype "bidirectional"))
      (node (ref "C142") (pin "2") (pinfunction "2_2") (pintype "bidirectional"))
      (node (ref "C143") (pin "2") (pinfunction "2_2") (pintype "bidirectional"))
      (node (ref "C144") (pin "2") (pinfunction "2_2") (pintype "bidirectional"))
      (node (ref "C145") (pin "2") (pinfunction "2_2") (pintype "bidirectional"))
      (node (ref "C146") (pin "2") (pinfunction "2_2") (pintype "bidirectional"))
      (node (ref "C147") (pin "2") (pinfunction "2_2") (pintype "bidirectional"))
      (node (ref "C148") (pin "2") (pinfunction "2_2") (pintype "bidirectional"))
      (node (ref "C149") (pin "2") (pinfunction "2_2") (pintype "bidirectional"))
      (node (ref "C15") (pin "1") (pinfunction "1_1") (pintype "bidirectional"))
      (node (ref "C150") (pin "2") (pinfunction "2_2") (pintype "bidirectional"))
      (node (ref "C151") (pin "2") (pinfunction "2_2") (pintype "bidirectional"))
      (node (ref "C152") (pin "2") (pinfunction "2_2") (pintype "bidirectional"))
      (node (ref "C153") (pin "2") (pinfunction "2_2") (pintype "bidirectional"))
      (node (ref "C154") (pin "2") (pinfunction "2_2") (pintype "bidirectional"))
      (node (ref "C155") (pin "2") (pinfunction "2_2") (pintype "bidirectional"))
      (node (ref "C156") (pin "2") (pinfunction "2_2") (pintype "bidirectional"))
      (node (ref "C157") (pin "2") (pinfunction "2_2") (pintype "bidirectional"))
      (node (ref "C158") (pin "2") (pinfunction "2_2") (pintype "bidirectional"))
      (node (ref "C159") (pin "2") (pinfunction "2_2") (pintype "bidirectional"))
      (node (ref "C16") (pin "2") (pinfunction "2_2") (pintype "bidirectional"))
      (node (ref "C160") (pin "2") (pinfunction "2_2") (pintype "bidirectional"))
      (node (ref "C161") (pin "2") (pinfunction "2_2") (pintype "bidirectional"))
      (node (ref "C162") (pin "2") (pinfunction "2_2") (pintype "bidirectional"))
      (node (ref "C163") (pin "2") (pinfunction "2_2") (pintype "bidirectional"))
      (node (ref "C164") (pin "2") (pinfunction "2_2") (pintype "bidirectional"))
      (node (ref "C165") (pin "2") (pinfunction "2_2") (pintype "bidirectional"))
      (node (ref "C166") (pin "2") (pinfunction "2_2") (pintype "bidirectional"))
      (node (ref "C167") (pin "2") (pinfunction "2_2") (pintype "bidirectional"))
      (node (ref "C168") (pin "2") (pinfunction "2_2") (pintype "bidirectional"))
      (node (ref "C169") (pin "2") (pinfunction "2_2") (pintype "bidirectional"))
      (node (ref "C17") (pin "2") (pinfunction "2_2") (pintype "bidirectional"))
      (node (ref "C170") (pin "2") (pinfunction "2_2") (pintype "bidirectional"))
      (node (ref "C171") (pin "2") (pinfunction "2_2") (pintype "bidirectional"))
      (node (ref "C172") (pin "2") (pinfunction "2_2") (pintype "bidirectional"))
      (node (ref "C174") (pin "2") (pinfunction "2_2") (pintype "bidirectional"))
      (node (ref "C177") (pin "2") (pinfunction "2_2") (pintype "bidirectional"))
      (node (ref "C178") (pin "2") (pinfunction "2_2") (pintype "bidirectional"))
      (node (ref "C179") (pin "1") (pinfunction "1_1") (pintype "bidirectional"))
      (node (ref "C18") (pin "1") (pinfunction "1_1") (pintype "bidirectional"))
      (node (ref "C180") (pin "1") (pinfunction "1_1") (pintype "bidirectional"))
      (node (ref "C183") (pin "2") (pinfunction "2_2") (pintype "bidirectional"))
      (node (ref "C184") (pin "2") (pinfunction "2_2") (pintype "bidirectional"))
      (node (ref "C185") (pin "1") (pinfunction "1_1") (pintype "bidirectional"))
      (node (ref "C186") (pin "1") (pinfunction "1_1") (pintype "bidirectional"))
      (node (ref "C187") (pin "1") (pinfunction "1_1") (pintype "bidirectional"))
      (node (ref "C188") (pin "1") (pinfunction "1_1") (pintype "bidirectional"))
      (node (ref "C189") (pin "2") (pinfunction "2_2") (pintype "bidirectional"))
      (node (ref "C19") (pin "2") (pinfunction "2_2") (pintype "bidirectional"))
      (node (ref "C190") (pin "2") (pinfunction "2_2") (pintype "bidirectional"))
      (node (ref "C191") (pin "2") (pinfunction "2_2") (pintype "bidirectional"))
      (node (ref "C192") (pin "2") (pinfunction "2_2") (pintype "bidirectional"))
      (node (ref "C193") (pin "2") (pinfunction "2_2") (pintype "bidirectional"))
      (node (ref "C194") (pin "2") (pinfunction "2_2") (pintype "bidirectional"))
      (node (ref "C195") (pin "2") (pinfunction "2_2") (pintype "bidirectional"))
      (node (ref "C196") (pin "1") (pinfunction "1_1") (pintype "bidirectional"))
      (node (ref "C197") (pin "1") (pinfunction "1_1") (pintype "bidirectional"))
      (node (ref "C198") (pin "1") (pinfunction "1_1") (pintype "bidirectional"))
      (node (ref "C2") (pin "2") (pinfunction "2_2") (pintype "bidirectional"))
      (node (ref "C20") (pin "2") (pinfunction "2_2") (pintype "bidirectional"))
      (node (ref "C201") (pin "2") (pinfunction "2_2") (pintype "bidirectional"))
      (node (ref "C202") (pin "2") (pinfunction "2_2") (pintype "bidirectional"))
      (node (ref "C203") (pin "1") (pinfunction "1_1") (pintype "bidirectional"))
      (node (ref "C204") (pin "1") (pinfunction "1_1") (pintype "bidirectional"))
      (node (ref "C207") (pin "2") (pinfunction "2_2") (pintype "bidirectional"))
      (node (ref "C208") (pin "2") (pinfunction "2_2") (pintype "bidirectional"))
      (node (ref "C209") (pin "1") (pinfunction "1_1") (pintype "bidirectional"))
      (node (ref "C21") (pin "2") (pinfunction "2_2") (pintype "bidirectional"))
      (node (ref "C210") (pin "1") (pinfunction "1_1") (pintype "bidirectional"))
      (node (ref "C213") (pin "2") (pinfunction "2_2") (pintype "bidirectional"))
      (node (ref "C214") (pin "2") (pinfunction "2_2") (pintype "bidirectional"))
      (node (ref "C215") (pin "1") (pinfunction "1_1") (pintype "bidirectional"))
      (node (ref "C216") (pin "1") (pinfunction "1_1") (pintype "bidirectional"))
      (node (ref "C219") (pin "2") (pinfunction "2_2") (pintype "bidirectional"))
      (node (ref "C22") (pin "2") (pinfunction "2_2") (pintype "bidirectional"))
      (node (ref "C220") (pin "2") (pinfunction "2_2") (pintype "bidirectional"))
      (node (ref "C221") (pin "1") (pinfunction "1_1") (pintype "bidirectional"))
      (node (ref "C222") (pin "1") (pinfunction "1_1") (pintype "bidirectional"))
      (node (ref "C225") (pin "2") (pinfunction "2_2") (pintype "bidirectional"))
      (node (ref "C226") (pin "2") (pinfunction "2_2") (pintype "bidirectional"))
      (node (ref "C227") (pin "1") (pinfunction "1_1") (pintype "bidirectional"))
      (node (ref "C228") (pin "1") (pinfunction "1_1") (pintype "bidirectional"))
      (node (ref "C23") (pin "1") (pinfunction "1_1") (pintype "bidirectional"))
      (node (ref "C231") (pin "2") (pinfunction "2_2") (pintype "bidirectional"))
      (node (ref "C232") (pin "2") (pinfunction "2_2") (pintype "bidirectional"))
      (node (ref "C233") (pin "1") (pinfunction "1_1") (pintype "bidirectional"))
      (node (ref "C234") (pin "1") (pinfunction "1_1") (pintype "bidirectional"))
      (node (ref "C237") (pin "2") (pinfunction "2_2") (pintype "bidirectional"))
      (node (ref "C238") (pin "2") (pinfunction "2_2") (pintype "bidirectional"))
      (node (ref "C239") (pin "1") (pinfunction "1_1") (pintype "bidirectional"))
      (node (ref "C24") (pin "1") (pinfunction "1_1") (pintype "bidirectional"))
      (node (ref "C240") (pin "1") (pinfunction "1_1") (pintype "bidirectional"))
      (node (ref "C243") (pin "2") (pinfunction "2_2") (pintype "bidirectional"))
      (node (ref "C244") (pin "2") (pinfunction "2_2") (pintype "bidirectional"))
      (node (ref "C245") (pin "1") (pinfunction "1_1") (pintype "bidirectional"))
      (node (ref "C246") (pin "1") (pinfunction "1_1") (pintype "bidirectional"))
      (node (ref "C249") (pin "2") (pinfunction "2_2") (pintype "bidirectional"))
      (node (ref "C25") (pin "2") (pinfunction "2_2") (pintype "bidirectional"))
      (node (ref "C250") (pin "2") (pinfunction "2_2") (pintype "bidirectional"))
      (node (ref "C251") (pin "1") (pinfunction "1_1") (pintype "bidirectional"))
      (node (ref "C252") (pin "1") (pinfunction "1_1") (pintype "bidirectional"))
      (node (ref "C255") (pin "2") (pinfunction "2_2") (pintype "bidirectional"))
      (node (ref "C256") (pin "2") (pinfunction "2_2") (pintype "bidirectional"))
      (node (ref "C257") (pin "1") (pinfunction "1_1") (pintype "bidirectional"))
      (node (ref "C258") (pin "1") (pinfunction "1_1") (pintype "bidirectional"))
      (node (ref "C26") (pin "2") (pinfunction "2_2") (pintype "bidirectional"))
      (node (ref "C261") (pin "2") (pinfunction "2_2") (pintype "bidirectional"))
      (node (ref "C262") (pin "2") (pinfunction "2_2") (pintype "bidirectional"))
      (node (ref "C263") (pin "1") (pinfunction "1_1") (pintype "bidirectional"))
      (node (ref "C264") (pin "1") (pinfunction "1_1") (pintype "bidirectional"))
      (node (ref "C267") (pin "2") (pinfunction "2_2") (pintype "bidirectional"))
      (node (ref "C268") (pin "2") (pinfunction "2_2") (pintype "bidirectional"))
      (node (ref "C269") (pin "1") (pinfunction "1_1") (pintype "bidirectional"))
      (node (ref "C27") (pin "1") (pinfunction "1_1") (pintype "bidirectional"))
      (node (ref "C270") (pin "1") (pinfunction "1_1") (pintype "bidirectional"))
      (node (ref "C273") (pin "2") (pinfunction "2_2") (pintype "bidirectional"))
      (node (ref "C274") (pin "2") (pinfunction "2_2") (pintype "bidirectional"))
      (node (ref "C275") (pin "1") (pinfunction "1_1") (pintype "bidirectional"))
      (node (ref "C276") (pin "1") (pinfunction "1_1") (pintype "bidirectional"))
      (node (ref "C28") (pin "2") (pinfunction "2_2") (pintype "bidirectional"))
      (node (ref "C29") (pin "2") (pinfunction "2_2") (pintype "bidirectional"))
      (node (ref "C3") (pin "2") (pinfunction "2_2") (pintype "bidirectional"))
      (node (ref "C30") (pin "2") (pinfunction "2_2") (pintype "bidirectional"))
      (node (ref "C33") (pin "2") (pinfunction "2_2") (pintype "bidirectional"))
      (node (ref "C34") (pin "2") (pinfunction "2_2") (pintype "bidirectional"))
      (node (ref "C35") (pin "2") (pinfunction "2_2") (pintype "bidirectional"))
      (node (ref "C36") (pin "2") (pinfunction "2_2") (pintype "bidirectional"))
      (node (ref "C37") (pin "2") (pinfunction "2_2") (pintype "bidirectional"))
      (node (ref "C38") (pin "2") (pinfunction "2_2") (pintype "bidirectional"))
      (node (ref "C39") (pin "2") (pinfunction "2_2") (pintype "bidirectional"))
      (node (ref "C4") (pin "1") (pinfunction "1_1") (pintype "bidirectional"))
      (node (ref "C40") (pin "2") (pinfunction "2_2") (pintype "bidirectional"))
      (node (ref "C41") (pin "2") (pinfunction "2_2") (pintype "bidirectional"))
      (node (ref "C42") (pin "2") (pinfunction "2_2") (pintype "bidirectional"))
      (node (ref "C43") (pin "2") (pinfunction "2_2") (pintype "bidirectional"))
      (node (ref "C44") (pin "2") (pinfunction "2_2") (pintype "bidirectional"))
      (node (ref "C45") (pin "2") (pinfunction "2_2") (pintype "bidirectional"))
      (node (ref "C46") (pin "2") (pinfunction "2_2") (pintype "bidirectional"))
      (node (ref "C49") (pin "2") (pinfunction "2_2") (pintype "bidirectional"))
      (node (ref "C5") (pin "1") (pinfunction "1_1") (pintype "bidirectional"))
      (node (ref "C50") (pin "2") (pinfunction "2_2") (pintype "bidirectional"))
      (node (ref "C51") (pin "1") (pinfunction "1_1") (pintype "bidirectional"))
      (node (ref "C52") (pin "1") (pinfunction "1_1") (pintype "bidirectional"))
      (node (ref "C57") (pin "2") (pinfunction "2_2") (pintype "bidirectional"))
      (node (ref "C58") (pin "2") (pinfunction "2_2") (pintype "bidirectional"))
      (node (ref "C59") (pin "1") (pinfunction "1_1") (pintype "bidirectional"))
      (node (ref "C6") (pin "1") (pinfunction "1_1") (pintype "bidirectional"))
      (node (ref "C60") (pin "1") (pinfunction "1_1") (pintype "bidirectional"))
      (node (ref "C63") (pin "2") (pinfunction "2_2") (pintype "bidirectional"))
      (node (ref "C64") (pin "2") (pinfunction "2_2") (pintype "bidirectional"))
      (node (ref "C65") (pin "2") (pinfunction "2_2") (pintype "bidirectional"))
      (node (ref "C66") (pin "2") (pinfunction "2_2") (pintype "bidirectional"))
      (node (ref "C67") (pin "2") (pinfunction "2_2") (pintype "bidirectional"))
      (node (ref "C68") (pin "2") (pinfunction "2_2") (pintype "bidirectional"))
      (node (ref "C69") (pin "2") (pinfunction "2_2") (pintype "bidirectional"))
      (node (ref "C7") (pin "2") (pinfunction "2_2") (pintype "bidirectional"))
      (node (ref "C70") (pin "2") (pinfunction "2_2") (pintype "bidirectional"))
      (node (ref "C71") (pin "2") (pinfunction "2_2") (pintype "bidirectional"))
      (node (ref "C72") (pin "2") (pinfunction "2_2") (pintype "bidirectional"))
      (node (ref "C73") (pin "2") (pinfunction "2_2") (pintype "bidirectional"))
      (node (ref "C74") (pin "2") (pinfunction "2_2") (pintype "bidirectional"))
      (node (ref "C75") (pin "2") (pinfunction "2_2") (pintype "bidirectional"))
      (node (ref "C76") (pin "1") (pinfunction "1_1") (pintype "bidirectional"))
      (node (ref "C77") (pin "1") (pinfunction "1_1") (pintype "bidirectional"))
      (node (ref "C8") (pin "2") (pinfunction "2_2") (pintype "bidirectional"))
      (node (ref "C80") (pin "2") (pinfunction "2_2") (pintype "bidirectional"))
      (node (ref "C81") (pin "2") (pinfunction "2_2") (pintype "bidirectional"))
      (node (ref "C82") (pin "2") (pinfunction "2_2") (pintype "bidirectional"))
      (node (ref "C83") (pin "2") (pinfunction "2_2") (pintype "bidirectional"))
      (node (ref "C84") (pin "1") (pinfunction "1_1") (pintype "bidirectional"))
      (node (ref "C85") (pin "1") (pinfunction "1_1") (pintype "bidirectional"))
      (node (ref "C88") (pin "2") (pinfunction "2_2") (pintype "bidirectional"))
      (node (ref "C89") (pin "2") (pinfunction "2_2") (pintype "bidirectional"))
      (node (ref "C9") (pin "2") (pinfunction "2_2") (pintype "bidirectional"))
      (node (ref "C95") (pin "2") (pinfunction "2_2") (pintype "bidirectional"))
      (node (ref "C96") (pin "1") (pinfunction "1_1") (pintype "bidirectional"))
      (node (ref "C97") (pin "2") (pinfunction "2_2") (pintype "bidirectional"))
      (node (ref "C98") (pin "1") (pinfunction "1_1") (pintype "bidirectional"))
      (node (ref "C99") (pin "2") (pinfunction "2_2") (pintype "bidirectional"))
      (node (ref "D1") (pin "2") (pinfunction "A_2") (pintype "bidirectional"))
      (node (ref "D10") (pin "2") (pinfunction "A_2") (pintype "bidirectional"))
      (node (ref "D11") (pin "2") (pinfunction "A_2") (pintype "bidirectional"))
      (node (ref "D12") (pin "2") (pinfunction "A_2") (pintype "bidirectional"))
      (node (ref "D13") (pin "2") (pinfunction "A_2") (pintype "bidirectional"))
      (node (ref "D14") (pin "2") (pinfunction "A_2") (pintype "bidirectional"))
      (node (ref "D15") (pin "2") (pinfunction "A_2") (pintype "bidirectional"))
      (node (ref "D16") (pin "2") (pinfunction "A_2") (pintype "bidirectional"))
      (node (ref "D17") (pin "2") (pinfunction "A_2") (pintype "bidirectional"))
      (node (ref "D18") (pin "2") (pinfunction "A_2") (pintype "bidirectional"))
      (node (ref "D19") (pin "2") (pinfunction "A_2") (pintype "bidirectional"))
      (node (ref "D2") (pin "2") (pinfunction "A_2") (pintype "bidirectional"))
      (node (ref "D20") (pin "2") (pinfunction "A_2") (pintype "bidirectional"))
      (node (ref "D21") (pin "2") (pinfunction "A_2") (pintype "bidirectional"))
      (node (ref "D22") (pin "2") (pinfunction "A_2") (pintype "bidirectional"))
      (node (ref "D23") (pin "2") (pinfunction "A_2") (pintype "bidirectional"))
      (node (ref "D24") (pin "2") (pinfunction "A_2") (pintype "bidirectional"))
      (node (ref "D25") (pin "2") (pinfunction "A_2") (pintype "bidirectional"))
      (node (ref "D26") (pin "2") (pinfunction "A_2") (pintype "bidirectional"))
      (node (ref "D27") (pin "2") (pinfunction "A_2") (pintype "bidirectional"))
      (node (ref "D28") (pin "2") (pinfunction "A_2") (pintype "bidirectional"))
      (node (ref "D29") (pin "2") (pinfunction "A_2") (pintype "bidirectional"))
      (node (ref "D3") (pin "2") (pinfunction "A_2") (pintype "bidirectional"))
      (node (ref "D30") (pin "2") (pinfunction "A_2") (pintype "bidirectional"))
      (node (ref "D31") (pin "2") (pinfunction "A_2") (pintype "bidirectional"))
      (node (ref "D32") (pin "2") (pinfunction "A_2") (pintype "bidirectional"))
      (node (ref "D33") (pin "2") (pinfunction "A_2") (pintype "bidirectional"))
      (node (ref "D34") (pin "2") (pinfunction "A_2") (pintype "bidirectional"))
      (node (ref "D35") (pin "2") (pinfunction "A_2") (pintype "bidirectional"))
      (node (ref "D36") (pin "2") (pinfunction "A_2") (pintype "bidirectional"))
      (node (ref "D37") (pin "2") (pinfunction "A_2") (pintype "bidirectional"))
      (node (ref "D38") (pin "2") (pinfunction "A_2") (pintype "bidirectional"))
      (node (ref "D39") (pin "2") (pinfunction "A_2") (pintype "bidirectional"))
      (node (ref "D4") (pin "2") (pinfunction "A_2") (pintype "bidirectional"))
      (node (ref "D40") (pin "2") (pinfunction "A_2") (pintype "bidirectional"))
      (node (ref "D41") (pin "2") (pinfunction "A_2") (pintype "bidirectional"))
      (node (ref "D42") (pin "2") (pinfunction "A_2") (pintype "bidirectional"))
      (node (ref "D43") (pin "2") (pinfunction "A_2") (pintype "bidirectional"))
      (node (ref "D44") (pin "2") (pinfunction "A_2") (pintype "bidirectional"))
      (node (ref "D45") (pin "2") (pinfunction "SOURCE_2") (pintype "bidirectional"))
      (node (ref "D46") (pin "2") (pinfunction "A_2") (pintype "bidirectional"))
      (node (ref "D47") (pin "2") (pinfunction "A_2") (pintype "bidirectional"))
      (node (ref "D48") (pin "2") (pinfunction "SOURCE_2") (pintype "bidirectional"))
      (node (ref "D49") (pin "2") (pinfunction "A_2") (pintype "bidirectional"))
      (node (ref "D5") (pin "2") (pinfunction "A_2") (pintype "bidirectional"))
      (node (ref "D50") (pin "2") (pinfunction "A_2") (pintype "bidirectional"))
      (node (ref "D51") (pin "2") (pinfunction "A_2") (pintype "bidirectional"))
      (node (ref "D52") (pin "2") (pinfunction "A_2") (pintype "bidirectional"))
      (node (ref "D53") (pin "2") (pinfunction "A_2") (pintype "bidirectional"))
      (node (ref "D54") (pin "2") (pinfunction "A_2") (pintype "bidirectional"))
      (node (ref "D55") (pin "2") (pinfunction "A_2") (pintype "bidirectional"))
      (node (ref "D56") (pin "2") (pinfunction "A_2") (pintype "bidirectional"))
      (node (ref "D57") (pin "2") (pinfunction "A_2") (pintype "bidirectional"))
      (node (ref "D58") (pin "2") (pinfunction "A_2") (pintype "bidirectional"))
      (node (ref "D59") (pin "2") (pinfunction "A_2") (pintype "bidirectional"))
      (node (ref "D6") (pin "2") (pinfunction "A_2") (pintype "bidirectional"))
      (node (ref "D60") (pin "2") (pinfunction "A_2") (pintype "bidirectional"))
      (node (ref "D61") (pin "2") (pinfunction "A_2") (pintype "bidirectional"))
      (node (ref "D62") (pin "2") (pinfunction "A_2") (pintype "bidirectional"))
      (node (ref "D63") (pin "2") (pinfunction "A_2") (pintype "bidirectional"))
      (node (ref "D64") (pin "2") (pinfunction "A_2") (pintype "bidirectional"))
      (node (ref "D65") (pin "2") (pinfunction "A_2") (pintype "bidirectional"))
      (node (ref "D66") (pin "2") (pinfunction "A_2") (pintype "bidirectional"))
      (node (ref "D67") (pin "2") (pinfunction "A_2") (pintype "bidirectional"))
      (node (ref "D68") (pin "2") (pinfunction "A_2") (pintype "bidirectional"))
      (node (ref "D69") (pin "2") (pinfunction "A_2") (pintype "bidirectional"))
      (node (ref "D7") (pin "2") (pinfunction "A_2") (pintype "bidirectional"))
      (node (ref "D70") (pin "2") (pinfunction "A_2") (pintype "bidirectional"))
      (node (ref "D71") (pin "2") (pinfunction "A_2") (pintype "bidirectional"))
      (node (ref "D72") (pin "2") (pinfunction "A_2") (pintype "bidirectional"))
      (node (ref "D73") (pin "2") (pinfunction "A_2") (pintype "bidirectional"))
      (node (ref "D74") (pin "2") (pinfunction "A_2") (pintype "bidirectional"))
      (node (ref "D75") (pin "2") (pinfunction "SOURCE_2") (pintype "bidirectional"))
      (node (ref "D76") (pin "2") (pinfunction "A_2") (pintype "bidirectional"))
      (node (ref "D77") (pin "2") (pinfunction "A_2") (pintype "bidirectional"))
      (node (ref "D78") (pin "2") (pinfunction "SOURCE_2") (pintype "bidirectional"))
      (node (ref "D79") (pin "2") (pinfunction "SOURCE_2") (pintype "bidirectional"))
      (node (ref "D8") (pin "2") (pinfunction "A_2") (pintype "bidirectional"))
      (node (ref "D80") (pin "2") (pinfunction "SOURCE_2") (pintype "bidirectional"))
      (node (ref "D81") (pin "2") (pinfunction "SOURCE_2") (pintype "bidirectional"))
      (node (ref "D82") (pin "2") (pinfunction "SOURCE_2") (pintype "bidirectional"))
      (node (ref "D84") (pin "2") (pinfunction "SOURCE_2") (pintype "bidirectional"))
      (node (ref "D85") (pin "2") (pinfunction "SOURCE_2") (pintype "bidirectional"))
      (node (ref "D86") (pin "2") (pinfunction "SOURCE_2") (pintype "bidirectional"))
      (node (ref "D87") (pin "2") (pinfunction "SOURCE_2") (pintype "bidirectional"))
      (node (ref "D9") (pin "2") (pinfunction "A_2") (pintype "bidirectional"))
      (node (ref "IC10") (pin "1") (pinfunction "GND_1") (pintype "power_in"))
      (node (ref "IC11") (pin "17") (pinfunction "~{EN2}_17") (pintype "bidirectional"))
      (node (ref "IC11") (pin "24") (pinfunction "~{EN1}_24") (pintype "bidirectional"))
      (node (ref "IC11") (pin "33") (pinfunction "GND1_33") (pintype "bidirectional"))
      (node (ref "IC11") (pin "4") (pinfunction "GND_4") (pintype "bidirectional"))
      (node (ref "IC11") (pin "7") (pinfunction "ADR2_7") (pintype "bidirectional"))
      (node (ref "IC12") (pin "17") (pinfunction "~{EN2}_17") (pintype "bidirectional"))
      (node (ref "IC12") (pin "24") (pinfunction "~{EN1}_24") (pintype "bidirectional"))
      (node (ref "IC12") (pin "33") (pinfunction "GND1_33") (pintype "bidirectional"))
      (node (ref "IC12") (pin "4") (pinfunction "GND_4") (pintype "bidirectional"))
      (node (ref "IC12") (pin "5") (pinfunction "ADR0_5") (pintype "bidirectional"))
      (node (ref "IC12") (pin "6") (pinfunction "ADR1_6") (pintype "bidirectional"))
      (node (ref "IC12") (pin "7") (pinfunction "ADR2_7") (pintype "bidirectional"))
      (node (ref "IC13") (pin "17") (pinfunction "~{EN2}_17") (pintype "bidirectional"))
      (node (ref "IC13") (pin "24") (pinfunction "~{EN1}_24") (pintype "bidirectional"))
      (node (ref "IC13") (pin "33") (pinfunction "GND1_33") (pintype "bidirectional"))
      (node (ref "IC13") (pin "4") (pinfunction "GND_4") (pintype "bidirectional"))
      (node (ref "IC13") (pin "7") (pinfunction "ADR2_7") (pintype "bidirectional"))
      (node (ref "IC14") (pin "17") (pinfunction "~{EN2}_17") (pintype "bidirectional"))
      (node (ref "IC14") (pin "24") (pinfunction "~{EN1}_24") (pintype "bidirectional"))
      (node (ref "IC14") (pin "33") (pinfunction "GND1_33") (pintype "bidirectional"))
      (node (ref "IC14") (pin "4") (pinfunction "GND_4") (pintype "bidirectional"))
      (node (ref "IC14") (pin "5") (pinfunction "ADR0_5") (pintype "bidirectional"))
      (node (ref "IC15") (pin "17") (pinfunction "~{EN2}_17") (pintype "bidirectional"))
      (node (ref "IC15") (pin "24") (pinfunction "~{EN1}_24") (pintype "bidirectional"))
      (node (ref "IC15") (pin "33") (pinfunction "GND1_33") (pintype "bidirectional"))
      (node (ref "IC15") (pin "4") (pinfunction "GND_4") (pintype "bidirectional"))
      (node (ref "IC16") (pin "17") (pinfunction "~{EN2}_17") (pintype "bidirectional"))
      (node (ref "IC16") (pin "24") (pinfunction "~{EN1}_24") (pintype "bidirectional"))
      (node (ref "IC16") (pin "33") (pinfunction "GND1_33") (pintype "bidirectional"))
      (node (ref "IC16") (pin "4") (pinfunction "GND_4") (pintype "bidirectional"))
      (node (ref "IC17") (pin "17") (pinfunction "~{EN2}_17") (pintype "bidirectional"))
      (node (ref "IC17") (pin "24") (pinfunction "~{EN1}_24") (pintype "bidirectional"))
      (node (ref "IC17") (pin "33") (pinfunction "GND1_33") (pintype "bidirectional"))
      (node (ref "IC17") (pin "4") (pinfunction "GND_4") (pintype "bidirectional"))
      (node (ref "IC18") (pin "17") (pinfunction "~{EN2}_17") (pintype "bidirectional"))
      (node (ref "IC18") (pin "24") (pinfunction "~{EN1}_24") (pintype "bidirectional"))
      (node (ref "IC18") (pin "33") (pinfunction "GND1_33") (pintype "bidirectional"))
      (node (ref "IC18") (pin "4") (pinfunction "GND_4") (pintype "bidirectional"))
      (node (ref "IC18") (pin "6") (pinfunction "ADR1_6") (pintype "bidirectional"))
      (node (ref "IC18") (pin "7") (pinfunction "ADR2_7") (pintype "bidirectional"))
      (node (ref "IC19") (pin "17") (pinfunction "~{EN2}_17") (pintype "bidirectional"))
      (node (ref "IC19") (pin "24") (pinfunction "~{EN1}_24") (pintype "bidirectional"))
      (node (ref "IC19") (pin "33") (pinfunction "GND1_33") (pintype "bidirectional"))
      (node (ref "IC19") (pin "4") (pinfunction "GND_4") (pintype "bidirectional"))
      (node (ref "IC19") (pin "6") (pinfunction "ADR1_6") (pintype "bidirectional"))
      (node (ref "IC19") (pin "7") (pinfunction "ADR2_7") (pintype "bidirectional"))
      (node (ref "IC20") (pin "17") (pinfunction "~{EN2}_17") (pintype "bidirectional"))
      (node (ref "IC20") (pin "24") (pinfunction "~{EN1}_24") (pintype "bidirectional"))
      (node (ref "IC20") (pin "33") (pinfunction "GND1_33") (pintype "bidirectional"))
      (node (ref "IC20") (pin "4") (pinfunction "GND_4") (pintype "bidirectional"))
      (node (ref "IC20") (pin "7") (pinfunction "ADR2_7") (pintype "bidirectional"))
      (node (ref "IC21") (pin "17") (pinfunction "~{EN2}_17") (pintype "bidirectional"))
      (node (ref "IC21") (pin "24") (pinfunction "~{EN1}_24") (pintype "bidirectional"))
      (node (ref "IC21") (pin "33") (pinfunction "GND1_33") (pintype "bidirectional"))
      (node (ref "IC21") (pin "4") (pinfunction "GND_4") (pintype "bidirectional"))
      (node (ref "IC21") (pin "7") (pinfunction "ADR2_7") (pintype "bidirectional"))
      (node (ref "IC22") (pin "17") (pinfunction "~{EN2}_17") (pintype "bidirectional"))
      (node (ref "IC22") (pin "24") (pinfunction "~{EN1}_24") (pintype "bidirectional"))
      (node (ref "IC22") (pin "33") (pinfunction "GND1_33") (pintype "bidirectional"))
      (node (ref "IC22") (pin "4") (pinfunction "GND_4") (pintype "bidirectional"))
      (node (ref "IC22") (pin "5") (pinfunction "ADR0_5") (pintype "bidirectional"))
      (node (ref "IC22") (pin "6") (pinfunction "ADR1_6") (pintype "bidirectional"))
      (node (ref "IC23") (pin "17") (pinfunction "~{EN2}_17") (pintype "bidirectional"))
      (node (ref "IC23") (pin "24") (pinfunction "~{EN1}_24") (pintype "bidirectional"))
      (node (ref "IC23") (pin "33") (pinfunction "GND1_33") (pintype "bidirectional"))
      (node (ref "IC23") (pin "4") (pinfunction "GND_4") (pintype "bidirectional"))
      (node (ref "IC24") (pin "2") (pinfunction "VSS_2") (pintype "bidirectional"))
      (node (ref "IC25") (pin "2") (pinfunction "VSS_2") (pintype "bidirectional"))
      (node (ref "IC26") (pin "2") (pinfunction "VSS_2") (pintype "bidirectional"))
      (node (ref "IC27") (pin "2") (pinfunction "VSS_2") (pintype "bidirectional"))
      (node (ref "IC28") (pin "2") (pinfunction "VSS_2") (pintype "bidirectional"))
      (node (ref "IC29") (pin "2") (pinfunction "VSS_2") (pintype "bidirectional"))
      (node (ref "IC30") (pin "2") (pinfunction "VSS_2") (pintype "bidirectional"))
      (node (ref "IC31") (pin "A1") (pinfunction "GND_1_A1") (pintype "bidirectional"))
      (node (ref "IC31") (pin "A2") (pinfunction "GND_2_A2") (pintype "bidirectional"))
      (node (ref "IC31") (pin "A3") (pinfunction "GND_3_A3") (pintype "bidirectional"))
      (node (ref "IC31") (pin "A4") (pinfunction "GND_4_A4") (pintype "bidirectional"))
      (node (ref "IC31") (pin "A5") (pinfunction "GND_5_A5") (pintype "bidirectional"))
      (node (ref "IC31") (pin "A6") (pinfunction "GND_6_A6") (pintype "bidirectional"))
      (node (ref "IC31") (pin "A7") (pinfunction "GND_7_A7") (pintype "bidirectional"))
      (node (ref "IC31") (pin "A8") (pinfunction "GND_8_A8") (pintype "bidirectional"))
      (node (ref "IC31") (pin "B3") (pinfunction "GND_9_B3") (pintype "bidirectional"))
      (node (ref "IC31") (pin "B4") (pinfunction "GND_10_B4") (pintype "bidirectional"))
      (node (ref "IC31") (pin "B5") (pinfunction "GND_11_B5") (pintype "bidirectional"))
      (node (ref "IC31") (pin "B6") (pinfunction "GND_12_B6") (pintype "bidirectional"))
      (node (ref "IC31") (pin "C2") (pinfunction "GND_13_C2") (pintype "bidirectional"))
      (node (ref "IC31") (pin "C6") (pinfunction "GND_14_C6") (pintype "bidirectional"))
      (node (ref "IC31") (pin "D3") (pinfunction "GND_15_D3") (pintype "bidirectional"))
      (node (ref "IC31") (pin "E2") (pinfunction "GND_16_E2") (pintype "bidirectional"))
      (node (ref "IC31") (pin "E6") (pinfunction "GND_17_E6") (pintype "bidirectional"))
      (node (ref "IC31") (pin "E7") (pinfunction "GND_18_E7") (pintype "bidirectional"))
      (node (ref "IC31") (pin "F1") (pinfunction "GND_19_F1") (pintype "bidirectional"))
      (node (ref "IC31") (pin "F5") (pinfunction "GND_20_F5") (pintype "bidirectional"))
      (node (ref "IC31") (pin "F6") (pinfunction "GND_21_F6") (pintype "bidirectional"))
      (node (ref "IC31") (pin "F8") (pinfunction "GND_22_F8") (pintype "bidirectional"))
      (node (ref "IC31") (pin "G2") (pinfunction "GND_23_G2") (pintype "bidirectional"))
      (node (ref "IC31") (pin "G7") (pinfunction "GND_24_G7") (pintype "bidirectional"))
      (node (ref "IC31") (pin "H8") (pinfunction "GND_25_H8") (pintype "bidirectional"))
      (node (ref "IC31") (pin "J2") (pinfunction "GND_26_J2") (pintype "bidirectional"))
      (node (ref "IC31") (pin "J7") (pinfunction "GND_27_J7") (pintype "bidirectional"))
      (node (ref "IC31") (pin "K1") (pinfunction "GND_28_K1") (pintype "bidirectional"))
      (node (ref "IC31") (pin "K3") (pinfunction "GND_29_K3") (pintype "bidirectional"))
      (node (ref "IC31") (pin "K8") (pinfunction "GND_30_K8") (pintype "bidirectional"))
      (node (ref "IC32") (pin "13") (pinfunction "GND_13") (pintype "bidirectional"))
      (node (ref "IC32") (pin "17") (pinfunction "EP_17") (pintype "bidirectional"))
      (node (ref "IC33") (pin "10") (pinfunction "GND_10") (pintype "bidirectional"))
      (node (ref "IC34") (pin "3") (pinfunction "GND_3") (pintype "bidirectional"))
      (node (ref "IC34") (pin "8") (pinfunction "AGND_8") (pintype "bidirectional"))
      (node (ref "IC38") (pin "16") (pinfunction "DB0_16") (pintype "output"))
      (node (ref "IC38") (pin "17") (pinfunction "DB1_17") (pintype "output"))
      (node (ref "IC38") (pin "18") (pinfunction "DB2_18") (pintype "output"))
      (node (ref "IC38") (pin "19") (pinfunction "DB3_19") (pintype "output"))
      (node (ref "IC38") (pin "2") (pinfunction "AGND_1_2") (pintype "power_in"))
      (node (ref "IC38") (pin "20") (pinfunction "DB4_20") (pintype "output"))
      (node (ref "IC38") (pin "21") (pinfunction "DB5_21") (pintype "output"))
      (node (ref "IC38") (pin "22") (pinfunction "DB6_22") (pintype "output"))
      (node (ref "IC38") (pin "26") (pinfunction "AGND_2_26") (pintype "power_in"))
      (node (ref "IC38") (pin "27") (pinfunction "DB9_27") (pintype "output"))
      (node (ref "IC38") (pin "28") (pinfunction "DB10_28") (pintype "output"))
      (node (ref "IC38") (pin "29") (pinfunction "DB11_29") (pintype "output"))
      (node (ref "IC38") (pin "30") (pinfunction "DB12_30") (pintype "output"))
      (node (ref "IC38") (pin "31") (pinfunction "DB13_31") (pintype "output"))
      (node (ref "IC38") (pin "32") (pinfunction "DB14/HBEN_32") (pintype "bidirectional"))
      (node (ref "IC38") (pin "33") (pinfunction "DB15/BYTE_SEL_33") (pintype "bidirectional"))
      (node (ref "IC38") (pin "35") (pinfunction "AGND_3_35") (pintype "power_in"))
      (node (ref "IC38") (pin "40") (pinfunction "AGND_4_40") (pintype "power_in"))
      (node (ref "IC38") (pin "41") (pinfunction "AGND_5_41") (pintype "power_in"))
      (node (ref "IC38") (pin "43") (pinfunction "REFGND_1_43") (pintype "power_in"))
      (node (ref "IC38") (pin "46") (pinfunction "REFGND_2_46") (pintype "power_in"))
      (node (ref "IC38") (pin "47") (pinfunction "AGND_6_47") (pintype "power_in"))
      (node (ref "IC38") (pin "8") (pinfunction "RANGE_8") (pintype "input"))
      (node (ref "IC4") (pin "17") (pinfunction "~{EN2}_17") (pintype "bidirectional"))
      (node (ref "IC4") (pin "24") (pinfunction "~{EN1}_24") (pintype "bidirectional"))
      (node (ref "IC4") (pin "33") (pinfunction "GND1_33") (pintype "bidirectional"))
      (node (ref "IC4") (pin "4") (pinfunction "GND_4") (pintype "bidirectional"))
      (node (ref "IC4") (pin "5") (pinfunction "ADR0_5") (pintype "bidirectional"))
      (node (ref "IC4") (pin "7") (pinfunction "ADR2_7") (pintype "bidirectional"))
      (node (ref "IC5") (pin "2") (pinfunction "GND_2") (pintype "bidirectional"))
      (node (ref "IC5") (pin "7") (pinfunction "EP_7") (pintype "bidirectional"))
      (node (ref "IC51") (pin "16") (pinfunction "DB0_16") (pintype "output"))
      (node (ref "IC51") (pin "17") (pinfunction "DB1_17") (pintype "output"))
      (node (ref "IC51") (pin "18") (pinfunction "DB2_18") (pintype "output"))
      (node (ref "IC51") (pin "19") (pinfunction "DB3_19") (pintype "output"))
      (node (ref "IC51") (pin "2") (pinfunction "AGND_1_2") (pintype "power_in"))
      (node (ref "IC51") (pin "20") (pinfunction "DB4_20") (pintype "output"))
      (node (ref "IC51") (pin "21") (pinfunction "DB5_21") (pintype "output"))
      (node (ref "IC51") (pin "22") (pinfunction "DB6_22") (pintype "output"))
      (node (ref "IC51") (pin "26") (pinfunction "AGND_2_26") (pintype "power_in"))
      (node (ref "IC51") (pin "27") (pinfunction "DB9_27") (pintype "output"))
      (node (ref "IC51") (pin "28") (pinfunction "DB10_28") (pintype "output"))
      (node (ref "IC51") (pin "29") (pinfunction "DB11_29") (pintype "output"))
      (node (ref "IC51") (pin "30") (pinfunction "DB12_30") (pintype "output"))
      (node (ref "IC51") (pin "31") (pinfunction "DB13_31") (pintype "output"))
      (node (ref "IC51") (pin "32") (pinfunction "DB14/HBEN_32") (pintype "bidirectional"))
      (node (ref "IC51") (pin "33") (pinfunction "DB15/BYTE_SEL_33") (pintype "bidirectional"))
      (node (ref "IC51") (pin "35") (pinfunction "AGND_3_35") (pintype "power_in"))
      (node (ref "IC51") (pin "40") (pinfunction "AGND_4_40") (pintype "power_in"))
      (node (ref "IC51") (pin "41") (pinfunction "AGND_5_41") (pintype "power_in"))
      (node (ref "IC51") (pin "43") (pinfunction "REFGND_1_43") (pintype "power_in"))
      (node (ref "IC51") (pin "46") (pinfunction "REFGND_2_46") (pintype "power_in"))
      (node (ref "IC51") (pin "47") (pinfunction "AGND_6_47") (pintype "power_in"))
      (node (ref "IC51") (pin "8") (pinfunction "RANGE_8") (pintype "input"))
      (node (ref "IC52") (pin "16") (pinfunction "DB0_16") (pintype "output"))
      (node (ref "IC52") (pin "17") (pinfunction "DB1_17") (pintype "output"))
      (node (ref "IC52") (pin "18") (pinfunction "DB2_18") (pintype "output"))
      (node (ref "IC52") (pin "19") (pinfunction "DB3_19") (pintype "output"))
      (node (ref "IC52") (pin "2") (pinfunction "AGND_1_2") (pintype "power_in"))
      (node (ref "IC52") (pin "20") (pinfunction "DB4_20") (pintype "output"))
      (node (ref "IC52") (pin "21") (pinfunction "DB5_21") (pintype "output"))
      (node (ref "IC52") (pin "22") (pinfunction "DB6_22") (pintype "output"))
      (node (ref "IC52") (pin "26") (pinfunction "AGND_2_26") (pintype "power_in"))
      (node (ref "IC52") (pin "27") (pinfunction "DB9_27") (pintype "output"))
      (node (ref "IC52") (pin "28") (pinfunction "DB10_28") (pintype "output"))
      (node (ref "IC52") (pin "29") (pinfunction "DB11_29") (pintype "output"))
      (node (ref "IC52") (pin "30") (pinfunction "DB12_30") (pintype "output"))
      (node (ref "IC52") (pin "31") (pinfunction "DB13_31") (pintype "output"))
      (node (ref "IC52") (pin "32") (pinfunction "DB14/HBEN_32") (pintype "bidirectional"))
      (node (ref "IC52") (pin "33") (pinfunction "DB15/BYTE_SEL_33") (pintype "bidirectional"))
      (node (ref "IC52") (pin "35") (pinfunction "AGND_3_35") (pintype "power_in"))
      (node (ref "IC52") (pin "40") (pinfunction "AGND_4_40") (pintype "power_in"))
      (node (ref "IC52") (pin "41") (pinfunction "AGND_5_41") (pintype "power_in"))
      (node (ref "IC52") (pin "43") (pinfunction "REFGND_1_43") (pintype "power_in"))
      (node (ref "IC52") (pin "46") (pinfunction "REFGND_2_46") (pintype "power_in"))
      (node (ref "IC52") (pin "47") (pinfunction "AGND_6_47") (pintype "power_in"))
      (node (ref "IC52") (pin "60") (pinfunction "AIN_6GND_60") (pintype "input"))
      (node (ref "IC52") (pin "62") (pinfunction "AIN_7GND_62") (pintype "input"))
      (node (ref "IC52") (pin "64") (pinfunction "AIN_8GND_64") (pintype "input"))
      (node (ref "IC52") (pin "8") (pinfunction "RANGE_8") (pintype "input"))
      (node (ref "IC6") (pin "2") (pinfunction "GND_2") (pintype "bidirectional"))
      (node (ref "IC6") (pin "7") (pinfunction "EP_7") (pintype "bidirectional"))
      (node (ref "IC7") (pin "1") (pinfunction "GND_1") (pintype "power_in"))
      (node (ref "IC8") (pin "1") (pinfunction "GND_1") (pintype "power_in"))
      (node (ref "IC9") (pin "2") (pinfunction "GND_2") (pintype "bidirectional"))
      (node (ref "IC9") (pin "7") (pinfunction "EP_7") (pintype "bidirectional"))
      (node (ref "J12") (pin "39") (pinfunction "39_39") (pintype "passive"))
      (node (ref "J12") (pin "40") (pinfunction "40_40") (pintype "passive"))
      (node (ref "J12") (pin "41") (pinfunction "41_41") (pintype "passive"))
      (node (ref "J12") (pin "42") (pinfunction "42_42") (pintype "passive"))
      (node (ref "J12") (pin "43") (pinfunction "43_43") (pintype "passive"))
      (node (ref "J12") (pin "44") (pinfunction "44_44") (pintype "passive"))
      (node (ref "J12") (pin "45") (pinfunction "45_45") (pintype "passive"))
      (node (ref "J12") (pin "46") (pinfunction "46_46") (pintype "passive"))
      (node (ref "J12") (pin "47") (pinfunction "47_47") (pintype "passive"))
      (node (ref "J12") (pin "48") (pinfunction "48_48") (pintype "passive"))
      (node (ref "J12") (pin "49") (pinfunction "49_49") (pintype "passive"))
      (node (ref "J12") (pin "50") (pinfunction "50_50") (pintype "passive"))
      (node (ref "J12") (pin "51") (pinfunction "51_51") (pintype "passive"))
      (node (ref "J12") (pin "52") (pinfunction "52_52") (pintype "passive"))
      (node (ref "J12") (pin "53") (pinfunction "53_53") (pintype "passive"))
      (node (ref "J12") (pin "54") (pinfunction "54_54") (pintype "passive"))
      (node (ref "J12") (pin "55") (pinfunction "55_55") (pintype "passive"))
      (node (ref "J12") (pin "56") (pinfunction "56_56") (pintype "passive"))
      (node (ref "J12") (pin "57") (pinfunction "57_57") (pintype "passive"))
      (node (ref "J12") (pin "58") (pinfunction "58_58") (pintype "passive"))
      (node (ref "J12") (pin "59") (pinfunction "59_59") (pintype "passive"))
      (node (ref "J12") (pin "60") (pinfunction "60_60") (pintype "passive"))
      (node (ref "J12") (pin "61") (pinfunction "61_61") (pintype "passive"))
      (node (ref "J12") (pin "62") (pinfunction "62_62") (pintype "passive"))
      (node (ref "J12") (pin "63") (pinfunction "63_63") (pintype "passive"))
      (node (ref "J12") (pin "64") (pinfunction "64_64") (pintype "passive"))
      (node (ref "J12") (pin "65") (pinfunction "65_65") (pintype "passive"))
      (node (ref "J12") (pin "66") (pinfunction "66_66") (pintype "passive"))
      (node (ref "J12") (pin "67") (pinfunction "67_67") (pintype "passive"))
      (node (ref "J12") (pin "68") (pinfunction "68_68") (pintype "passive"))
      (node (ref "J12") (pin "69") (pinfunction "69_69") (pintype "passive"))
      (node (ref "J12") (pin "70") (pinfunction "70_70") (pintype "passive"))
      (node (ref "J12") (pin "71") (pinfunction "71_71") (pintype "passive"))
      (node (ref "J12") (pin "72") (pinfunction "72_72") (pintype "passive"))
      (node (ref "J12") (pin "73") (pinfunction "73_73") (pintype "passive"))
      (node (ref "J12") (pin "74") (pinfunction "74_74") (pintype "passive"))
      (node (ref "J12") (pin "75") (pinfunction "75_75") (pintype "passive"))
      (node (ref "J12") (pin "76") (pinfunction "76_76") (pintype "passive"))
      (node (ref "J12") (pin "77") (pinfunction "77_77") (pintype "passive"))
      (node (ref "J12") (pin "78") (pinfunction "78_78") (pintype "passive"))
      (node (ref "J12") (pin "79") (pinfunction "79_79") (pintype "passive"))
      (node (ref "J12") (pin "80") (pinfunction "80_80") (pintype "passive"))
      (node (ref "J2") (pin "2") (pinfunction "2_2") (pintype "passive"))
      (node (ref "J2") (pin "4") (pinfunction "4_4") (pintype "passive"))
      (node (ref "J2") (pin "6") (pinfunction "6_6") (pintype "passive"))
      (node (ref "J3") (pin "P6") (pinfunction "VSS_P6") (pintype "bidirectional"))
      (node (ref "J5") (pin "07") (pinfunction "07_07") (pintype "passive"))
      (node (ref "J5") (pin "09") (pinfunction "09_09") (pintype "passive"))
      (node (ref "J5") (pin "17") (pinfunction "17_17") (pintype "passive"))
      (node (ref "J5") (pin "19") (pinfunction "19_19") (pintype "passive"))
      (node (ref "J5") (pin "27") (pinfunction "27_27") (pintype "passive"))
      (node (ref "J5") (pin "29") (pinfunction "29_29") (pintype "passive"))
      (node (ref "J5") (pin "37") (pinfunction "37_37") (pintype "passive"))
      (node (ref "J5") (pin "39") (pinfunction "39_39") (pintype "passive"))
      (node (ref "J5") (pin "41") (pinfunction "41_41") (pintype "passive"))
      (node (ref "J5") (pin "43") (pinfunction "43_43") (pintype "passive"))
      (node (ref "J5") (pin "45") (pinfunction "45_45") (pintype "passive"))
      (node (ref "J5") (pin "47") (pinfunction "47_47") (pintype "passive"))
      (node (ref "J5") (pin "49") (pinfunction "49_49") (pintype "passive"))
      (node (ref "J5") (pin "51") (pinfunction "51_51") (pintype "passive"))
      (node (ref "J5") (pin "53") (pinfunction "53_53") (pintype "passive"))
      (node (ref "J5") (pin "55") (pinfunction "55_55") (pintype "passive"))
      (node (ref "J5") (pin "61") (pinfunction "61_61") (pintype "passive"))
      (node (ref "J5") (pin "63") (pinfunction "63_63") (pintype "passive"))
      (node (ref "J5") (pin "69") (pinfunction "69_69") (pintype "passive"))
      (node (ref "J5") (pin "71") (pinfunction "71_71") (pintype "passive"))
      (node (ref "J5") (pin "77") (pinfunction "77_77") (pintype "passive"))
      (node (ref "J5") (pin "79") (pinfunction "79_79") (pintype "passive"))
      (node (ref "J6") (pin "07") (pinfunction "07_07") (pintype "passive"))
      (node (ref "J6") (pin "09") (pinfunction "09_09") (pintype "passive"))
      (node (ref "J6") (pin "17") (pinfunction "17_17") (pintype "passive"))
      (node (ref "J6") (pin "19") (pinfunction "19_19") (pintype "passive"))
      (node (ref "J6") (pin "27") (pinfunction "27_27") (pintype "passive"))
      (node (ref "J6") (pin "29") (pinfunction "29_29") (pintype "passive"))
      (node (ref "J6") (pin "31") (pinfunction "31_31") (pintype "passive"))
      (node (ref "J6") (pin "32") (pinfunction "32_32") (pintype "passive"))
      (node (ref "J6") (pin "33") (pinfunction "33_33") (pintype "passive"))
      (node (ref "J6") (pin "34") (pinfunction "34_34") (pintype "passive"))
      (node (ref "J6") (pin "35") (pinfunction "35_35") (pintype "passive"))
      (node (ref "J6") (pin "36") (pinfunction "36_36") (pintype "passive"))
      (node (ref "J6") (pin "37") (pinfunction "37_37") (pintype "passive"))
      (node (ref "J6") (pin "38") (pinfunction "38_38") (pintype "passive"))
      (node (ref "J6") (pin "39") (pinfunction "39_39") (pintype "passive"))
      (node (ref "J6") (pin "40") (pinfunction "40_40") (pintype "passive"))
      (node (ref "J6") (pin "47") (pinfunction "47_47") (pintype "passive"))
      (node (ref "J6") (pin "49") (pinfunction "49_49") (pintype "passive"))
      (node (ref "J6") (pin "57") (pinfunction "57_57") (pintype "passive"))
      (node (ref "J6") (pin "59") (pinfunction "59_59") (pintype "passive"))
      (node (ref "J6") (pin "67") (pinfunction "67_67") (pintype "passive"))
      (node (ref "J6") (pin "69") (pinfunction "69_69") (pintype "passive"))
      (node (ref "J6") (pin "77") (pinfunction "77_77") (pintype "passive"))
      (node (ref "J6") (pin "79") (pinfunction "79_79") (pintype "passive"))
      (node (ref "J9") (pin "03") (pinfunction "03_03") (pintype "passive"))
      (node (ref "LED10") (pin "2") (pinfunction "K_2") (pintype "bidirectional"))
      (node (ref "LED100") (pin "2") (pinfunction "K_2") (pintype "bidirectional"))
      (node (ref "LED101") (pin "2") (pinfunction "K_2") (pintype "bidirectional"))
      (node (ref "LED102") (pin "2") (pinfunction "K_2") (pintype "bidirectional"))
      (node (ref "LED103") (pin "2") (pinfunction "K_2") (pintype "bidirectional"))
      (node (ref "LED104") (pin "2") (pinfunction "K_2") (pintype "bidirectional"))
      (node (ref "LED105") (pin "2") (pinfunction "K_2") (pintype "bidirectional"))
      (node (ref "LED106") (pin "2") (pinfunction "K_2") (pintype "bidirectional"))
      (node (ref "LED107") (pin "2") (pinfunction "K_2") (pintype "bidirectional"))
      (node (ref "LED108") (pin "2") (pinfunction "K_2") (pintype "bidirectional"))
      (node (ref "LED109") (pin "2") (pinfunction "K_2") (pintype "bidirectional"))
      (node (ref "LED110") (pin "2") (pinfunction "K_2") (pintype "bidirectional"))
      (node (ref "LED111") (pin "2") (pinfunction "K_2") (pintype "bidirectional"))
      (node (ref "LED112") (pin "2") (pinfunction "K_2") (pintype "bidirectional"))
      (node (ref "LED113") (pin "2") (pinfunction "K_2") (pintype "bidirectional"))
      (node (ref "LED114") (pin "2") (pinfunction "K_2") (pintype "bidirectional"))
      (node (ref "LED13") (pin "2") (pinfunction "K_2") (pintype "bidirectional"))
      (node (ref "LED15") (pin "2") (pinfunction "K_2") (pintype "bidirectional"))
      (node (ref "LED18") (pin "2") (pinfunction "K_2") (pintype "bidirectional"))
      (node (ref "LED20") (pin "2") (pinfunction "K_2") (pintype "bidirectional"))
      (node (ref "LED23") (pin "2") (pinfunction "K_2") (pintype "bidirectional"))
      (node (ref "LED25") (pin "2") (pinfunction "K_2") (pintype "bidirectional"))
      (node (ref "LED28") (pin "2") (pinfunction "K_2") (pintype "bidirectional"))
      (node (ref "LED3") (pin "2") (pinfunction "K_2") (pintype "bidirectional"))
      (node (ref "LED30") (pin "2") (pinfunction "K_2") (pintype "bidirectional"))
      (node (ref "LED33") (pin "2") (pinfunction "K_2") (pintype "bidirectional"))
      (node (ref "LED35") (pin "2") (pinfunction "K_2") (pintype "bidirectional"))
      (node (ref "LED38") (pin "2") (pinfunction "K_2") (pintype "bidirectional"))
      (node (ref "LED40") (pin "2") (pinfunction "K_2") (pintype "bidirectional"))
      (node (ref "LED43") (pin "2") (pinfunction "K_2") (pintype "bidirectional"))
      (node (ref "LED45") (pin "2") (pinfunction "K_2") (pintype "bidirectional"))
      (node (ref "LED48") (pin "2") (pinfunction "K_2") (pintype "bidirectional"))
      (node (ref "LED5") (pin "2") (pinfunction "K_2") (pintype "bidirectional"))
      (node (ref "LED50") (pin "2") (pinfunction "K_2") (pintype "bidirectional"))
      (node (ref "LED53") (pin "2") (pinfunction "K_2") (pintype "bidirectional"))
      (node (ref "LED55") (pin "2") (pinfunction "K_2") (pintype "bidirectional"))
      (node (ref "LED58") (pin "2") (pinfunction "K_2") (pintype "bidirectional"))
      (node (ref "LED60") (pin "2") (pinfunction "K_2") (pintype "bidirectional"))
      (node (ref "LED63") (pin "2") (pinfunction "K_2") (pintype "bidirectional"))
      (node (ref "LED65") (pin "2") (pinfunction "K_2") (pintype "bidirectional"))
      (node (ref "LED68") (pin "2") (pinfunction "K_2") (pintype "bidirectional"))
      (node (ref "LED70") (pin "2") (pinfunction "K_2") (pintype "bidirectional"))
      (node (ref "LED71") (pin "1") (pinfunction "K_1") (pintype "bidirectional"))
      (node (ref "LED72") (pin "1") (pinfunction "K_1") (pintype "bidirectional"))
      (node (ref "LED73") (pin "1") (pinfunction "K_1") (pintype "bidirectional"))
      (node (ref "LED74") (pin "1") (pinfunction "K_1") (pintype "bidirectional"))
      (node (ref "LED75") (pin "1") (pinfunction "K_1") (pintype "bidirectional"))
      (node (ref "LED76") (pin "1") (pinfunction "K_1") (pintype "bidirectional"))
      (node (ref "LED77") (pin "1") (pinfunction "K_1") (pintype "bidirectional"))
      (node (ref "LED78") (pin "1") (pinfunction "K_1") (pintype "bidirectional"))
      (node (ref "LED79") (pin "1") (pinfunction "K_1") (pintype "bidirectional"))
      (node (ref "LED8") (pin "2") (pinfunction "K_2") (pintype "bidirectional"))
      (node (ref "LED80") (pin "1") (pinfunction "K_1") (pintype "bidirectional"))
      (node (ref "LED81") (pin "1") (pinfunction "K_1") (pintype "bidirectional"))
      (node (ref "LED82") (pin "1") (pinfunction "K_1") (pintype "bidirectional"))
      (node (ref "LED83") (pin "1") (pinfunction "K_1") (pintype "bidirectional"))
      (node (ref "LED84") (pin "1") (pinfunction "K_1") (pintype "bidirectional"))
      (node (ref "LED97") (pin "2") (pinfunction "K_2") (pintype "bidirectional"))
      (node (ref "LED98") (pin "2") (pinfunction "K_2") (pintype "bidirectional"))
      (node (ref "LED99") (pin "2") (pinfunction "K_2") (pintype "bidirectional"))
      (node (ref "R128") (pin "2") (pinfunction "2_2") (pintype "bidirectional"))
      (node (ref "R133") (pin "1") (pinfunction "1_1") (pintype "bidirectional"))
      (node (ref "R138") (pin "2") (pinfunction "2_2") (pintype "bidirectional"))
      (node (ref "R143") (pin "1") (pinfunction "1_1") (pintype "bidirectional"))
      (node (ref "R166") (pin "2") (pinfunction "2_2") (pintype "bidirectional"))
      (node (ref "R171") (pin "1") (pinfunction "1_1") (pintype "bidirectional"))
      (node (ref "R176") (pin "2") (pinfunction "2_2") (pintype "bidirectional"))
      (node (ref "R181") (pin "1") (pinfunction "1_1") (pintype "bidirectional"))
      (node (ref "R187") (pin "2") (pinfunction "2_2") (pintype "bidirectional"))
      (node (ref "R192") (pin "1") (pinfunction "1_1") (pintype "bidirectional"))
      (node (ref "R197") (pin "2") (pinfunction "2_2") (pintype "bidirectional"))
      (node (ref "R204") (pin "1") (pinfunction "1_1") (pintype "bidirectional"))
      (node (ref "R214") (pin "2") (pinfunction "2_2") (pintype "bidirectional"))
      (node (ref "R219") (pin "1") (pinfunction "1_1") (pintype "bidirectional"))
      (node (ref "R225") (pin "2") (pinfunction "2_2") (pintype "bidirectional"))
      (node (ref "R242") (pin "1") (pinfunction "1_1") (pintype "bidirectional"))
      (node (ref "R248") (pin "2") (pinfunction "2_2") (pintype "bidirectional"))
      (node (ref "R253") (pin "1") (pinfunction "1_1") (pintype "bidirectional"))
      (node (ref "R258") (pin "2") (pinfunction "2_2") (pintype "bidirectional"))
      (node (ref "R263") (pin "1") (pinfunction "1_1") (pintype "bidirectional"))
      (node (ref "R269") (pin "2") (pinfunction "2_2") (pintype "bidirectional"))
      (node (ref "R274") (pin "1") (pinfunction "1_1") (pintype "bidirectional"))
      (node (ref "R279") (pin "2") (pinfunction "2_2") (pintype "bidirectional"))
      (node (ref "R284") (pin "1") (pinfunction "1_1") (pintype "bidirectional"))
      (node (ref "R290") (pin "2") (pinfunction "2_2") (pintype "bidirectional"))
      (node (ref "R295") (pin "1") (pinfunction "1_1") (pintype "bidirectional"))
      (node (ref "R300") (pin "2") (pinfunction "2_2") (pintype "bidirectional"))
      (node (ref "R305") (pin "1") (pinfunction "1_1") (pintype "bidirectional"))
      (node (ref "R311") (pin "2") (pinfunction "2_2") (pintype "bidirectional"))
      (node (ref "R316") (pin "1") (pinfunction "1_1") (pintype "bidirectional"))
      (node (ref "R321") (pin "2") (pinfunction "2_2") (pintype "bidirectional"))
      (node (ref "R326") (pin "1") (pinfunction "1_1") (pintype "bidirectional"))
      (node (ref "R332") (pin "2") (pinfunction "2_2") (pintype "bidirectional"))
      (node (ref "R337") (pin "1") (pinfunction "1_1") (pintype "bidirectional"))
      (node (ref "R342") (pin "2") (pinfunction "2_2") (pintype "bidirectional"))
      (node (ref "R347") (pin "1") (pinfunction "1_1") (pintype "bidirectional"))
      (node (ref "R353") (pin "2") (pinfunction "2_2") (pintype "bidirectional"))
      (node (ref "R358") (pin "1") (pinfunction "1_1") (pintype "bidirectional"))
      (node (ref "R363") (pin "2") (pinfunction "2_2") (pintype "bidirectional"))
      (node (ref "R368") (pin "1") (pinfunction "1_1") (pintype "bidirectional"))
      (node (ref "R374") (pin "2") (pinfunction "2_2") (pintype "bidirectional"))
      (node (ref "R379") (pin "1") (pinfunction "1_1") (pintype "bidirectional"))
      (node (ref "R384") (pin "2") (pinfunction "2_2") (pintype "bidirectional"))
      (node (ref "R389") (pin "1") (pinfunction "1_1") (pintype "bidirectional"))
      (node (ref "R395") (pin "2") (pinfunction "2_2") (pintype "bidirectional"))
      (node (ref "R400") (pin "1") (pinfunction "1_1") (pintype "bidirectional"))
      (node (ref "R405") (pin "2") (pinfunction "2_2") (pintype "bidirectional"))
      (node (ref "R410") (pin "1") (pinfunction "1_1") (pintype "bidirectional"))
      (node (ref "R416") (pin "2") (pinfunction "2_2") (pintype "bidirectional"))
      (node (ref "R421") (pin "1") (pinfunction "1_1") (pintype "bidirectional"))
      (node (ref "R426") (pin "2") (pinfunction "2_2") (pintype "bidirectional"))
      (node (ref "R431") (pin "1") (pinfunction "1_1") (pintype "bidirectional"))
      (node (ref "R437") (pin "2") (pinfunction "2_2") (pintype "bidirectional"))
      (node (ref "R442") (pin "1") (pinfunction "1_1") (pintype "bidirectional"))
      (node (ref "R459") (pin "1") (pinfunction "1_1") (pintype "bidirectional"))
      (node (ref "R460") (pin "1") (pinfunction "1_1") (pintype "bidirectional"))
      (node (ref "R461") (pin "1") (pinfunction "1_1") (pintype "bidirectional"))
      (node (ref "R462") (pin "1") (pinfunction "1_1") (pintype "bidirectional"))
      (node (ref "R463") (pin "1") (pinfunction "1_1") (pintype "bidirectional"))
      (node (ref "R464") (pin "1") (pinfunction "1_1") (pintype "bidirectional"))
      (node (ref "R465") (pin "1") (pinfunction "1_1") (pintype "bidirectional"))
      (node (ref "R466") (pin "1") (pinfunction "1_1") (pintype "bidirectional"))
      (node (ref "R467") (pin "1") (pinfunction "1_1") (pintype "bidirectional"))
      (node (ref "R468") (pin "1") (pinfunction "1_1") (pintype "bidirectional"))
      (node (ref "R469") (pin "1") (pinfunction "1_1") (pintype "bidirectional"))
      (node (ref "R470") (pin "1") (pinfunction "1_1") (pintype "bidirectional"))
      (node (ref "R474") (pin "2") (pinfunction "2_2") (pintype "bidirectional"))
      (node (ref "R476") (pin "2") (pinfunction "2_2") (pintype "bidirectional"))
      (node (ref "R479") (pin "2") (pinfunction "2_2") (pintype "bidirectional"))
      (node (ref "R483") (pin "2") (pinfunction "2_2") (pintype "bidirectional"))
      (node (ref "R485") (pin "2") (pinfunction "2_2") (pintype "bidirectional"))
      (node (ref "R488") (pin "2") (pinfunction "2_2") (pintype "bidirectional"))
      (node (ref "R492") (pin "2") (pinfunction "2_2") (pintype "bidirectional"))
      (node (ref "R494") (pin "2") (pinfunction "2_2") (pintype "bidirectional"))
      (node (ref "R497") (pin "2") (pinfunction "2_2") (pintype "bidirectional"))
      (node (ref "R504") (pin "2") (pinfunction "2_2") (pintype "bidirectional"))
      (node (ref "R505") (pin "2") (pinfunction "2_2") (pintype "bidirectional"))
      (node (ref "R507") (pin "2") (pinfunction "2_2") (pintype "bidirectional"))
      (node (ref "R509") (pin "2") (pinfunction "2_2") (pintype "bidirectional"))
      (node (ref "R511") (pin "2") (pinfunction "2_2") (pintype "bidirectional"))
      (node (ref "R62") (pin "2") (pinfunction "2_2") (pintype "bidirectional"))
      (node (ref "R63") (pin "2") (pinfunction "2_2") (pintype "bidirectional"))
      (node (ref "R64") (pin "2") (pinfunction "2_2") (pintype "bidirectional"))
      (node (ref "R91") (pin "2") (pinfunction "2_2") (pintype "bidirectional"))
      (node (ref "R96") (pin "1") (pinfunction "1_1") (pintype "bidirectional"))
      (node (ref "U$1") (pin "2") (pinfunction "P$2_2") (pintype "bidirectional"))
      (node (ref "U$2") (pin "2") (pinfunction "P$2_2") (pintype "bidirectional"))
      (node (ref "U$3") (pin "2") (pinfunction "P$2_2") (pintype "bidirectional"))
      (node (ref "U$4") (pin "2") (pinfunction "P$2_2") (pintype "bidirectional"))
      (node (ref "UC1") (pin "10") (pinfunction "GND_10") (pintype "passive"))
      (node (ref "UC1") (pin "122") (pinfunction "GND_122") (pintype "passive"))
      (node (ref "UC1") (pin "131") (pinfunction "GND_131") (pintype "passive"))
      (node (ref "UC1") (pin "143") (pinfunction "GND_143") (pintype "passive"))
      (node (ref "UC1") (pin "144") (pinfunction "GND_144") (pintype "passive"))
      (node (ref "UC1") (pin "19") (pinfunction "GND_19") (pintype "passive"))
      (node (ref "UC1") (pin "40") (pinfunction "GND_40") (pintype "passive"))
      (node (ref "UC1") (pin "53") (pinfunction "GND_53") (pintype "passive"))
      (node (ref "UC1") (pin "64") (pinfunction "GND_64") (pintype "passive"))
      (node (ref "UC1") (pin "71") (pinfunction "GND_71") (pintype "passive"))
      (node (ref "UC1") (pin "72") (pinfunction "GND_72") (pintype "passive"))
      (node (ref "UC1") (pin "79") (pinfunction "GND_79") (pintype "passive"))
      (node (ref "UC1") (pin "91") (pinfunction "GND_91") (pintype "passive"))
      (node (ref "UC1") (pin "92") (pinfunction "GND_92") (pintype "passive"))
      (node (ref "UC1") (pin "93") (pinfunction "GND_93") (pintype "passive"))
    )
    (net (code "222") (name "GPIO1_") (class "Default")
      (node (ref "IC4") (pin "25") (pinfunction "GPIO1_25") (pintype "bidirectional"))
      (node (ref "LED1") (pin "1") (pinfunction "K_1") (pintype "bidirectional"))
    )
    (net (code "223") (name "GPIO1_0") (class "Default")
      (node (ref "IC11") (pin "25") (pinfunction "GPIO1_25") (pintype "bidirectional"))
      (node (ref "LED6") (pin "1") (pinfunction "K_1") (pintype "bidirectional"))
    )
    (net (code "224") (name "GPIO1_1") (class "Default")
      (node (ref "IC20") (pin "25") (pinfunction "GPIO1_25") (pintype "bidirectional"))
      (node (ref "LED51") (pin "1") (pinfunction "K_1") (pintype "bidirectional"))
    )
    (net (code "225") (name "GPIO1_2") (class "Default")
      (node (ref "IC21") (pin "25") (pinfunction "GPIO1_25") (pintype "bidirectional"))
      (node (ref "LED56") (pin "1") (pinfunction "K_1") (pintype "bidirectional"))
    )
    (net (code "226") (name "GPIO1_3") (class "Default")
      (node (ref "IC12") (pin "25") (pinfunction "GPIO1_25") (pintype "bidirectional"))
      (node (ref "LED11") (pin "1") (pinfunction "K_1") (pintype "bidirectional"))
    )
    (net (code "227") (name "GPIO1_4") (class "Default")
      (node (ref "IC13") (pin "25") (pinfunction "GPIO1_25") (pintype "bidirectional"))
      (node (ref "LED16") (pin "1") (pinfunction "K_1") (pintype "bidirectional"))
    )
    (net (code "228") (name "GPIO1_5") (class "Default")
      (node (ref "IC18") (pin "25") (pinfunction "GPIO1_25") (pintype "bidirectional"))
      (node (ref "LED41") (pin "1") (pinfunction "K_1") (pintype "bidirectional"))
    )
    (net (code "229") (name "GPIO1_6") (class "Default")
      (node (ref "IC19") (pin "25") (pinfunction "GPIO1_25") (pintype "bidirectional"))
      (node (ref "LED46") (pin "1") (pinfunction "K_1") (pintype "bidirectional"))
    )
    (net (code "230") (name "GPIO1_7") (class "Default")
      (node (ref "IC14") (pin "25") (pinfunction "GPIO1_25") (pintype "bidirectional"))
      (node (ref "LED21") (pin "1") (pinfunction "K_1") (pintype "bidirectional"))
    )
    (net (code "231") (name "GPIO1_8") (class "Default")
      (node (ref "IC15") (pin "25") (pinfunction "GPIO1_25") (pintype "bidirectional"))
      (node (ref "LED26") (pin "1") (pinfunction "K_1") (pintype "bidirectional"))
    )
    (net (code "232") (name "GPIO1_9") (class "Default")
      (node (ref "IC16") (pin "25") (pinfunction "GPIO1_25") (pintype "bidirectional"))
      (node (ref "LED31") (pin "1") (pinfunction "K_1") (pintype "bidirectional"))
    )
    (net (code "233") (name "GPIO1_10") (class "Default")
      (node (ref "IC17") (pin "25") (pinfunction "GPIO1_25") (pintype "bidirectional"))
      (node (ref "LED36") (pin "1") (pinfunction "K_1") (pintype "bidirectional"))
    )
    (net (code "234") (name "GPIO1_11") (class "Default")
      (node (ref "IC22") (pin "25") (pinfunction "GPIO1_25") (pintype "bidirectional"))
      (node (ref "LED61") (pin "1") (pinfunction "K_1") (pintype "bidirectional"))
    )
    (net (code "235") (name "GPIO1_12") (class "Default")
      (node (ref "IC23") (pin "25") (pinfunction "GPIO1_25") (pintype "bidirectional"))
      (node (ref "LED66") (pin "1") (pinfunction "K_1") (pintype "bidirectional"))
    )
    (net (code "236") (name "GPIO2_") (class "Default")
      (node (ref "IC4") (pin "16") (pinfunction "GPIO2_16") (pintype "bidirectional"))
      (node (ref "LED4") (pin "1") (pinfunction "K_1") (pintype "bidirectional"))
    )
    (net (code "237") (name "GPIO2_0") (class "Default")
      (node (ref "IC11") (pin "16") (pinfunction "GPIO2_16") (pintype "bidirectional"))
      (node (ref "LED9") (pin "1") (pinfunction "K_1") (pintype "bidirectional"))
    )
    (net (code "238") (name "GPIO2_1") (class "Default")
      (node (ref "IC20") (pin "16") (pinfunction "GPIO2_16") (pintype "bidirectional"))
      (node (ref "LED54") (pin "1") (pinfunction "K_1") (pintype "bidirectional"))
    )
    (net (code "239") (name "GPIO2_2") (class "Default")
      (node (ref "IC21") (pin "16") (pinfunction "GPIO2_16") (pintype "bidirectional"))
      (node (ref "LED59") (pin "1") (pinfunction "K_1") (pintype "bidirectional"))
    )
    (net (code "240") (name "GPIO2_3") (class "Default")
      (node (ref "IC12") (pin "16") (pinfunction "GPIO2_16") (pintype "bidirectional"))
      (node (ref "LED14") (pin "1") (pinfunction "K_1") (pintype "bidirectional"))
    )
    (net (code "241") (name "GPIO2_4") (class "Default")
      (node (ref "IC13") (pin "16") (pinfunction "GPIO2_16") (pintype "bidirectional"))
      (node (ref "LED19") (pin "1") (pinfunction "K_1") (pintype "bidirectional"))
    )
    (net (code "242") (name "GPIO2_5") (class "Default")
      (node (ref "IC18") (pin "16") (pinfunction "GPIO2_16") (pintype "bidirectional"))
      (node (ref "LED44") (pin "1") (pinfunction "K_1") (pintype "bidirectional"))
    )
    (net (code "243") (name "GPIO2_6") (class "Default")
      (node (ref "IC19") (pin "16") (pinfunction "GPIO2_16") (pintype "bidirectional"))
      (node (ref "LED49") (pin "1") (pinfunction "K_1") (pintype "bidirectional"))
    )
    (net (code "244") (name "GPIO2_7") (class "Default")
      (node (ref "IC14") (pin "16") (pinfunction "GPIO2_16") (pintype "bidirectional"))
      (node (ref "LED24") (pin "1") (pinfunction "K_1") (pintype "bidirectional"))
    )
    (net (code "245") (name "GPIO2_8") (class "Default")
      (node (ref "IC15") (pin "16") (pinfunction "GPIO2_16") (pintype "bidirectional"))
      (node (ref "LED29") (pin "1") (pinfunction "K_1") (pintype "bidirectional"))
    )
    (net (code "246") (name "GPIO2_9") (class "Default")
      (node (ref "IC16") (pin "16") (pinfunction "GPIO2_16") (pintype "bidirectional"))
      (node (ref "LED34") (pin "1") (pinfunction "K_1") (pintype "bidirectional"))
    )
    (net (code "247") (name "GPIO2_10") (class "Default")
      (node (ref "IC17") (pin "16") (pinfunction "GPIO2_16") (pintype "bidirectional"))
      (node (ref "LED39") (pin "1") (pinfunction "K_1") (pintype "bidirectional"))
    )
    (net (code "248") (name "GPIO2_11") (class "Default")
      (node (ref "IC22") (pin "16") (pinfunction "GPIO2_16") (pintype "bidirectional"))
      (node (ref "LED64") (pin "1") (pinfunction "K_1") (pintype "bidirectional"))
    )
    (net (code "249") (name "GPIO2_12") (class "Default")
      (node (ref "IC23") (pin "16") (pinfunction "GPIO2_16") (pintype "bidirectional"))
      (node (ref "LED69") (pin "1") (pinfunction "K_1") (pintype "bidirectional"))
    )
    (net (code "250") (name "GPS_EN") (class "Default")
      (node (ref "GPS_EN") (pin "TP") (pinfunction "TP_TP") (pintype "bidirectional"))
      (node (ref "J4") (pin "39") (pinfunction "39_39") (pintype "passive"))
      (node (ref "J9") (pin "08") (pinfunction "08_08") (pintype "passive"))
    )
    (net (code "251") (name "GPS_RX") (class "Default")
      (node (ref "GPS_RX") (pin "TP") (pinfunction "TP_TP") (pintype "bidirectional"))
      (node (ref "J4") (pin "37") (pinfunction "37_37") (pintype "passive"))
      (node (ref "J9") (pin "04") (pinfunction "04_04") (pintype "passive"))
    )
    (net (code "252") (name "GPS_TX") (class "Default")
      (node (ref "GPS_TX") (pin "TP") (pinfunction "TP_TP") (pintype "bidirectional"))
      (node (ref "J4") (pin "35") (pinfunction "35_35") (pintype "passive"))
      (node (ref "J9") (pin "05") (pinfunction "05_05") (pintype "passive"))
    )
    (net (code "253") (name "GP_1_P") (class "Default")
      (node (ref "IC52") (pin "49") (pinfunction "AIN_1P_49") (pintype "input"))
      (node (ref "IC71") (pin "1") (pinfunction "OUT_1") (pintype "bidirectional"))
      (node (ref "R111") (pin "1") (pinfunction "1_1") (pintype "bidirectional"))
    )
    (net (code "254") (name "GP_2_P") (class "Default")
      (node (ref "IC52") (pin "51") (pinfunction "AIN_2P_51") (pintype "input"))
      (node (ref "IC73") (pin "1") (pinfunction "OUT_1") (pintype "bidirectional"))
      (node (ref "R115") (pin "1") (pinfunction "1_1") (pintype "bidirectional"))
    )
    (net (code "255") (name "GP_3_P") (class "Default")
      (node (ref "IC52") (pin "53") (pinfunction "AIN_3P_53") (pintype "input"))
      (node (ref "IC75") (pin "1") (pinfunction "OUT_1") (pintype "bidirectional"))
      (node (ref "R161") (pin "1") (pinfunction "1_1") (pintype "bidirectional"))
    )
    (net (code "256") (name "GP_4_P") (class "Default")
      (node (ref "IC52") (pin "55") (pinfunction "AIN_4P_55") (pintype "input"))
      (node (ref "IC77") (pin "1") (pinfunction "OUT_1") (pintype "bidirectional"))
      (node (ref "R203") (pin "1") (pinfunction "1_1") (pintype "bidirectional"))
    )
    (net (code "257") (name "GP_5_P") (class "Default")
      (node (ref "IC52") (pin "57") (pinfunction "AIN_5P_57") (pintype "input"))
      (node (ref "IC79") (pin "1") (pinfunction "OUT_1") (pintype "bidirectional"))
      (node (ref "R211") (pin "1") (pinfunction "1_1") (pintype "bidirectional"))
    )
    (net (code "258") (name "GP_6_P") (class "Default")
      (node (ref "C36") (pin "1") (pinfunction "1_1") (pintype "bidirectional"))
      (node (ref "C71") (pin "1") (pinfunction "1_1") (pintype "bidirectional"))
      (node (ref "IC52") (pin "59") (pinfunction "AIN_6P_59") (pintype "input"))
      (node (ref "R59") (pin "2") (pinfunction "2_2") (pintype "bidirectional"))
      (node (ref "R64") (pin "1") (pinfunction "1_1") (pintype "bidirectional"))
    )
    (net (code "259") (name "GP_7_P") (class "Default")
      (node (ref "C65") (pin "1") (pinfunction "1_1") (pintype "bidirectional"))
      (node (ref "C72") (pin "1") (pinfunction "1_1") (pintype "bidirectional"))
      (node (ref "IC52") (pin "61") (pinfunction "AIN_7P_61") (pintype "input"))
      (node (ref "R60") (pin "2") (pinfunction "2_2") (pintype "bidirectional"))
      (node (ref "R62") (pin "1") (pinfunction "1_1") (pintype "bidirectional"))
    )
    (net (code "260") (name "GP_8_P") (class "Default")
      (node (ref "C70") (pin "1") (pinfunction "1_1") (pintype "bidirectional"))
      (node (ref "C73") (pin "1") (pinfunction "1_1") (pintype "bidirectional"))
      (node (ref "IC52") (pin "63") (pinfunction "AIN_8P_63") (pintype "input"))
      (node (ref "R61") (pin "2") (pinfunction "2_2") (pintype "bidirectional"))
      (node (ref "R63") (pin "1") (pinfunction "1_1") (pintype "bidirectional"))
    )
    (net (code "261") (name "IBAIS") (class "Default")
      (node (ref "IC32") (pin "15") (pinfunction "IBIAS_15") (pintype "bidirectional"))
      (node (ref "R510") (pin "1") (pinfunction "1_1") (pintype "bidirectional"))
    )
    (net (code "262") (name "ICMP") (class "Default")
      (node (ref "IC32") (pin "14") (pinfunction "ICMP_14") (pintype "bidirectional"))
      (node (ref "R510") (pin "2") (pinfunction "2_2") (pintype "bidirectional"))
      (node (ref "R511") (pin "1") (pinfunction "1_1") (pintype "bidirectional"))
    )
    (net (code "263") (name "IMU_DIN") (class "Default")
      (node (ref "IC31") (pin "G6") (pinfunction "DIN_G6") (pintype "bidirectional"))
      (node (ref "IMU_DIN") (pin "TP") (pinfunction "TP_TP") (pintype "bidirectional"))
      (node (ref "J4") (pin "05") (pinfunction "05_05") (pintype "passive"))
    )
    (net (code "264") (name "IMU_DOUT") (class "Default")
      (node (ref "IC31") (pin "H3") (pinfunction "DOUT_H3") (pintype "bidirectional"))
      (node (ref "IMU_DOUT") (pin "TP") (pinfunction "TP_TP") (pintype "bidirectional"))
      (node (ref "J4") (pin "07") (pinfunction "07_07") (pintype "passive"))
    )
    (net (code "265") (name "IMU_DR") (class "Default")
      (node (ref "IC31") (pin "J6") (pinfunction "DR_J6") (pintype "bidirectional"))
      (node (ref "IMU_DR") (pin "TP") (pinfunction "TP_TP") (pintype "bidirectional"))
      (node (ref "J4") (pin "13") (pinfunction "13_13") (pintype "passive"))
    )
    (net (code "266") (name "IMU_SCLK") (class "Default")
      (node (ref "IC31") (pin "H6") (pinfunction "SCLK_H6") (pintype "bidirectional"))
      (node (ref "IMU_SCLK") (pin "TP") (pinfunction "TP_TP") (pintype "bidirectional"))
      (node (ref "J4") (pin "09") (pinfunction "09_09") (pintype "passive"))
    )
    (net (code "267") (name "IMU_SYNC") (class "Default")
      (node (ref "IC31") (pin "J3") (pinfunction "SYNC_J3") (pintype "bidirectional"))
      (node (ref "IMU_SYNC") (pin "TP") (pinfunction "TP_TP") (pintype "bidirectional"))
      (node (ref "J4") (pin "11") (pinfunction "11_11") (pintype "passive"))
    )
    (net (code "268") (name "IM_INPUT") (class "Default")
      (node (ref "IC32") (pin "9") (pinfunction "IM_9") (pintype "bidirectional"))
      (node (ref "R512") (pin "2") (pinfunction "2_2") (pintype "passive"))
      (node (ref "T1") (pin "3") (pinfunction "PRIMARY_3_3") (pintype "bidirectional"))
    )
    (net (code "269") (name "IM_OUT1") (class "Default")
      (node (ref "IC33") (pin "8") (pinfunction "B_N_8") (pintype "bidirectional"))
      (node (ref "J5") (pin "62") (pinfunction "62_62") (pintype "passive"))
      (node (ref "R516") (pin "1") (pinfunction "1_1") (pintype "bidirectional"))
    )
    (net (code "270") (name "IM_OUT2") (class "Default")
      (node (ref "IC33") (pin "6") (pinfunction "C_N_6") (pintype "bidirectional"))
      (node (ref "R518") (pin "2") (pinfunction "2_2") (pintype "bidirectional"))
    )
    (net (code "271") (name "IM_OUTPUT") (class "Default")
      (node (ref "R514") (pin "2") (pinfunction "2_2") (pintype "bidirectional"))
      (node (ref "R516") (pin "2") (pinfunction "2_2") (pintype "bidirectional"))
      (node (ref "T1") (pin "4") (pinfunction "SECONDARY_1_4") (pintype "bidirectional"))
    )
    (net (code "272") (name "IP_INPUT") (class "Default")
      (node (ref "IC32") (pin "10") (pinfunction "IP_10") (pintype "bidirectional"))
      (node (ref "R512") (pin "1") (pinfunction "1_1") (pintype "passive"))
      (node (ref "T1") (pin "1") (pinfunction "PRIMARY_1_1") (pintype "bidirectional"))
    )
    (net (code "273") (name "IP_OUT1") (class "Default")
      (node (ref "IC33") (pin "9") (pinfunction "B_P_9") (pintype "bidirectional"))
      (node (ref "J5") (pin "64") (pinfunction "64_64") (pintype "passive"))
      (node (ref "R515") (pin "1") (pinfunction "1_1") (pintype "bidirectional"))
    )
    (net (code "274") (name "IP_OUT2") (class "Default")
      (node (ref "IC33") (pin "7") (pinfunction "C_P_7") (pintype "bidirectional"))
      (node (ref "R517") (pin "2") (pinfunction "2_2") (pintype "bidirectional"))
    )
    (net (code "275") (name "IP_OUTPUT") (class "Default")
      (node (ref "R513") (pin "2") (pinfunction "2_2") (pintype "bidirectional"))
      (node (ref "R515") (pin "2") (pinfunction "2_2") (pintype "bidirectional"))
      (node (ref "T1") (pin "6") (pinfunction "SECONDARY_3_6") (pintype "bidirectional"))
    )
    (net (code "276") (name "ISO_MISO") (class "Default")
      (node (ref "IC32") (pin "2") (pinfunction "MISO_2") (pintype "bidirectional"))
      (node (ref "ISO_MISO") (pin "TP") (pinfunction "TP_TP") (pintype "bidirectional"))
      (node (ref "J4") (pin "26") (pinfunction "26_26") (pintype "passive"))
    )
    (net (code "277") (name "ISO_MOSI") (class "Default")
      (node (ref "IC32") (pin "1") (pinfunction "MOSI_1") (pintype "bidirectional"))
      (node (ref "ISO_MOSI") (pin "TP") (pinfunction "TP_TP") (pintype "bidirectional"))
      (node (ref "J4") (pin "24") (pinfunction "24_24") (pintype "passive"))
    )
    (net (code "278") (name "ISO_SPI_CH_SEL") (class "Default")
      (node (ref "IC33") (pin "4") (pinfunction "SEL_4") (pintype "bidirectional"))
      (node (ref "ISO_SPI_CH_SEL") (pin "TP") (pinfunction "TP_TP") (pintype "bidirectional"))
      (node (ref "J4") (pin "18") (pinfunction "18_18") (pintype "passive"))
    )
    (net (code "279") (name "ISO_SPI_HIGH_Z_SWITCH") (class "Default")
      (node (ref "IC33") (pin "1") (pinfunction "XSD_1") (pintype "bidirectional"))
      (node (ref "ISO_SPI_HZ_SW") (pin "TP") (pinfunction "TP_TP") (pintype "bidirectional"))
      (node (ref "J4") (pin "20") (pinfunction "20_20") (pintype "passive"))
    )
    (net (code "280") (name "ISO_SPI_SCLK") (class "Default")
      (node (ref "IC32") (pin "3") (pinfunction "SCK_3") (pintype "bidirectional"))
      (node (ref "ISO_SPI_SCLK") (pin "TP") (pinfunction "TP_TP") (pintype "bidirectional"))
      (node (ref "J4") (pin "22") (pinfunction "22_22") (pintype "passive"))
    )
    (net (code "281") (name "ISO_SPI_SLOW") (class "Default")
      (node (ref "IC32") (pin "12") (pinfunction "SLOW_12") (pintype "bidirectional"))
      (node (ref "ISO_SPI_SLOW") (pin "TP") (pinfunction "TP_TP") (pintype "bidirectional"))
      (node (ref "J4") (pin "30") (pinfunction "30_30") (pintype "passive"))
    )
    (net (code "282") (name "LED_OUT1") (class "Default")
      (node (ref "J4") (pin "62") (pinfunction "62_62") (pintype "passive"))
      (node (ref "LED_1") (pin "TP") (pinfunction "TP_TP") (pintype "bidirectional"))
      (node (ref "R52") (pin "2") (pinfunction "2_2") (pintype "bidirectional"))
    )
    (net (code "283") (name "LED_OUT2") (class "Default")
      (node (ref "J4") (pin "60") (pinfunction "60_60") (pintype "passive"))
      (node (ref "LED_2") (pin "TP") (pinfunction "TP_TP") (pintype "bidirectional"))
      (node (ref "R54") (pin "2") (pinfunction "2_2") (pintype "bidirectional"))
    )
    (net (code "284") (name "LED_OUT3") (class "Default")
      (node (ref "J4") (pin "58") (pinfunction "58_58") (pintype "passive"))
      (node (ref "LED_3") (pin "TP") (pinfunction "TP_TP") (pintype "bidirectional"))
      (node (ref "R56") (pin "2") (pinfunction "2_2") (pintype "bidirectional"))
    )
    (net (code "285") (name "MASS_ON") (class "Default")
      (node (ref "IC11") (pin "22") (pinfunction "ON_22") (pintype "bidirectional"))
      (node (ref "IC12") (pin "22") (pinfunction "ON_22") (pintype "bidirectional"))
      (node (ref "IC13") (pin "22") (pinfunction "ON_22") (pintype "bidirectional"))
      (node (ref "IC14") (pin "22") (pinfunction "ON_22") (pintype "bidirectional"))
      (node (ref "IC15") (pin "22") (pinfunction "ON_22") (pintype "bidirectional"))
      (node (ref "IC16") (pin "22") (pinfunction "ON_22") (pintype "bidirectional"))
      (node (ref "IC17") (pin "22") (pinfunction "ON_22") (pintype "bidirectional"))
      (node (ref "IC18") (pin "22") (pinfunction "ON_22") (pintype "bidirectional"))
      (node (ref "IC19") (pin "22") (pinfunction "ON_22") (pintype "bidirectional"))
      (node (ref "IC20") (pin "22") (pinfunction "ON_22") (pintype "bidirectional"))
      (node (ref "IC21") (pin "22") (pinfunction "ON_22") (pintype "bidirectional"))
      (node (ref "IC22") (pin "22") (pinfunction "ON_22") (pintype "bidirectional"))
      (node (ref "IC23") (pin "22") (pinfunction "ON_22") (pintype "bidirectional"))
      (node (ref "IC4") (pin "22") (pinfunction "ON_22") (pintype "bidirectional"))
      (node (ref "J4") (pin "25") (pinfunction "25_25") (pintype "passive"))
      (node (ref "MASS_ON") (pin "TP") (pinfunction "TP_TP") (pintype "bidirectional"))
    )
    (net (code "286") (name "Net-(C42-Pad1)") (class "Default")
      (node (ref "C42") (pin "1") (pinfunction "1_1") (pintype "bidirectional"))
      (node (ref "R94") (pin "1") (pinfunction "1_1") (pintype "bidirectional"))
    )
    (net (code "287") (name "Net-(C43-Pad1)") (class "Default")
      (node (ref "C43") (pin "1") (pinfunction "1_1") (pintype "bidirectional"))
      (node (ref "R131") (pin "1") (pinfunction "1_1") (pintype "bidirectional"))
    )
    (net (code "288") (name "Net-(C48-Pad1)") (class "Default")
      (node (ref "C48") (pin "1") (pinfunction "1_1") (pintype "bidirectional"))
      (node (ref "R1") (pin "1") (pinfunction "1_1") (pintype "bidirectional"))
      (node (ref "R2") (pin "1") (pinfunction "1_1") (pintype "bidirectional"))
    )
    (net (code "289") (name "Net-(C54-Pad1)") (class "Default")
      (node (ref "C54") (pin "1") (pinfunction "1_1") (pintype "bidirectional"))
      (node (ref "R5") (pin "1") (pinfunction "1_1") (pintype "bidirectional"))
      (node (ref "R6") (pin "1") (pinfunction "1_1") (pintype "bidirectional"))
    )
    (net (code "290") (name "Net-(C56-Pad1)") (class "Default")
      (node (ref "C56") (pin "1") (pinfunction "1_1") (pintype "bidirectional"))
      (node (ref "R13") (pin "1") (pinfunction "1_1") (pintype "bidirectional"))
      (node (ref "R14") (pin "1") (pinfunction "1_1") (pintype "bidirectional"))
    )
    (net (code "291") (name "Net-(C62-Pad1)") (class "Default")
      (node (ref "C62") (pin "1") (pinfunction "1_1") (pintype "bidirectional"))
      (node (ref "R17") (pin "1") (pinfunction "1_1") (pintype "bidirectional"))
      (node (ref "R18") (pin "1") (pinfunction "1_1") (pintype "bidirectional"))
    )
    (net (code "292") (name "Net-(C79-Pad1)") (class "Default")
      (node (ref "C79") (pin "1") (pinfunction "1_1") (pintype "bidirectional"))
      (node (ref "R10") (pin "1") (pinfunction "1_1") (pintype "bidirectional"))
      (node (ref "R9") (pin "1") (pinfunction "1_1") (pintype "bidirectional"))
    )
    (net (code "293") (name "Net-(C87-Pad1)") (class "Default")
      (node (ref "C87") (pin "1") (pinfunction "1_1") (pintype "bidirectional"))
      (node (ref "R21") (pin "1") (pinfunction "1_1") (pintype "bidirectional"))
      (node (ref "R22") (pin "1") (pinfunction "1_1") (pintype "bidirectional"))
    )
    (net (code "294") (name "Net-(C95-Pad1)") (class "Default")
      (node (ref "C95") (pin "1") (pinfunction "1_1") (pintype "bidirectional"))
      (node (ref "R141") (pin "1") (pinfunction "1_1") (pintype "bidirectional"))
    )
    (net (code "295") (name "Net-(C97-Pad1)") (class "Default")
      (node (ref "C97") (pin "1") (pinfunction "1_1") (pintype "bidirectional"))
      (node (ref "R169") (pin "1") (pinfunction "1_1") (pintype "bidirectional"))
    )
    (net (code "296") (name "Net-(C112-Pad1)") (class "Default")
      (node (ref "C112") (pin "1") (pinfunction "1_1") (pintype "bidirectional"))
      (node (ref "R179") (pin "1") (pinfunction "1_1") (pintype "bidirectional"))
    )
    (net (code "297") (name "Net-(C113-Pad1)") (class "Default")
      (node (ref "C113") (pin "1") (pinfunction "1_1") (pintype "bidirectional"))
      (node (ref "R190") (pin "1") (pinfunction "1_1") (pintype "bidirectional"))
    )
    (net (code "298") (name "Net-(C117-Pad1)") (class "Default")
      (node (ref "C117") (pin "1") (pinfunction "1_1") (pintype "bidirectional"))
      (node (ref "R200") (pin "1") (pinfunction "1_1") (pintype "bidirectional"))
    )
    (net (code "299") (name "Net-(C118-Pad1)") (class "Default")
      (node (ref "C118") (pin "1") (pinfunction "1_1") (pintype "bidirectional"))
      (node (ref "R217") (pin "1") (pinfunction "1_1") (pintype "bidirectional"))
    )
    (net (code "300") (name "Net-(C122-Pad1)") (class "Default")
      (node (ref "C122") (pin "1") (pinfunction "1_1") (pintype "bidirectional"))
      (node (ref "R240") (pin "1") (pinfunction "1_1") (pintype "bidirectional"))
    )
    (net (code "301") (name "Net-(C123-Pad1)") (class "Default")
      (node (ref "C123") (pin "1") (pinfunction "1_1") (pintype "bidirectional"))
      (node (ref "R251") (pin "1") (pinfunction "1_1") (pintype "bidirectional"))
    )
    (net (code "302") (name "Net-(C127-Pad1)") (class "Default")
      (node (ref "C127") (pin "1") (pinfunction "1_1") (pintype "bidirectional"))
      (node (ref "R261") (pin "1") (pinfunction "1_1") (pintype "bidirectional"))
    )
    (net (code "303") (name "Net-(C128-Pad1)") (class "Default")
      (node (ref "C128") (pin "1") (pinfunction "1_1") (pintype "bidirectional"))
      (node (ref "R272") (pin "1") (pinfunction "1_1") (pintype "bidirectional"))
    )
    (net (code "304") (name "Net-(C132-Pad1)") (class "Default")
      (node (ref "C132") (pin "1") (pinfunction "1_1") (pintype "bidirectional"))
      (node (ref "R282") (pin "1") (pinfunction "1_1") (pintype "bidirectional"))
    )
    (net (code "305") (name "Net-(C133-Pad1)") (class "Default")
      (node (ref "C133") (pin "1") (pinfunction "1_1") (pintype "bidirectional"))
      (node (ref "R293") (pin "1") (pinfunction "1_1") (pintype "bidirectional"))
    )
    (net (code "306") (name "Net-(C137-Pad1)") (class "Default")
      (node (ref "C137") (pin "1") (pinfunction "1_1") (pintype "bidirectional"))
      (node (ref "R303") (pin "1") (pinfunction "1_1") (pintype "bidirectional"))
    )
    (net (code "307") (name "Net-(C138-Pad1)") (class "Default")
      (node (ref "C138") (pin "1") (pinfunction "1_1") (pintype "bidirectional"))
      (node (ref "R314") (pin "1") (pinfunction "1_1") (pintype "bidirectional"))
    )
    (net (code "308") (name "Net-(C142-Pad1)") (class "Default")
      (node (ref "C142") (pin "1") (pinfunction "1_1") (pintype "bidirectional"))
      (node (ref "R324") (pin "1") (pinfunction "1_1") (pintype "bidirectional"))
    )
    (net (code "309") (name "Net-(C143-Pad1)") (class "Default")
      (node (ref "C143") (pin "1") (pinfunction "1_1") (pintype "bidirectional"))
      (node (ref "R335") (pin "1") (pinfunction "1_1") (pintype "bidirectional"))
    )
    (net (code "310") (name "Net-(C147-Pad1)") (class "Default")
      (node (ref "C147") (pin "1") (pinfunction "1_1") (pintype "bidirectional"))
      (node (ref "R345") (pin "1") (pinfunction "1_1") (pintype "bidirectional"))
    )
    (net (code "311") (name "Net-(C148-Pad1)") (class "Default")
      (node (ref "C148") (pin "1") (pinfunction "1_1") (pintype "bidirectional"))
      (node (ref "R356") (pin "1") (pinfunction "1_1") (pintype "bidirectional"))
    )
    (net (code "312") (name "Net-(C152-Pad1)") (class "Default")
      (node (ref "C152") (pin "1") (pinfunction "1_1") (pintype "bidirectional"))
      (node (ref "R366") (pin "1") (pinfunction "1_1") (pintype "bidirectional"))
    )
    (net (code "313") (name "Net-(C153-Pad1)") (class "Default")
      (node (ref "C153") (pin "1") (pinfunction "1_1") (pintype "bidirectional"))
      (node (ref "R377") (pin "1") (pinfunction "1_1") (pintype "bidirectional"))
    )
    (net (code "314") (name "Net-(C157-Pad1)") (class "Default")
      (node (ref "C157") (pin "1") (pinfunction "1_1") (pintype "bidirectional"))
      (node (ref "R387") (pin "1") (pinfunction "1_1") (pintype "bidirectional"))
    )
    (net (code "315") (name "Net-(C158-Pad1)") (class "Default")
      (node (ref "C158") (pin "1") (pinfunction "1_1") (pintype "bidirectional"))
      (node (ref "R398") (pin "1") (pinfunction "1_1") (pintype "bidirectional"))
    )
    (net (code "316") (name "Net-(C162-Pad1)") (class "Default")
      (node (ref "C162") (pin "1") (pinfunction "1_1") (pintype "bidirectional"))
      (node (ref "R408") (pin "1") (pinfunction "1_1") (pintype "bidirectional"))
    )
    (net (code "317") (name "Net-(C163-Pad1)") (class "Default")
      (node (ref "C163") (pin "1") (pinfunction "1_1") (pintype "bidirectional"))
      (node (ref "R419") (pin "1") (pinfunction "1_1") (pintype "bidirectional"))
    )
    (net (code "318") (name "Net-(C167-Pad1)") (class "Default")
      (node (ref "C167") (pin "1") (pinfunction "1_1") (pintype "bidirectional"))
      (node (ref "R429") (pin "1") (pinfunction "1_1") (pintype "bidirectional"))
    )
    (net (code "319") (name "Net-(C168-Pad1)") (class "Default")
      (node (ref "C168") (pin "1") (pinfunction "1_1") (pintype "bidirectional"))
      (node (ref "R440") (pin "1") (pinfunction "1_1") (pintype "bidirectional"))
    )
    (net (code "320") (name "Net-(C176-Pad1)") (class "Default")
      (node (ref "C176") (pin "1") (pinfunction "1_1") (pintype "bidirectional"))
      (node (ref "R151") (pin "1") (pinfunction "1_1") (pintype "bidirectional"))
      (node (ref "R152") (pin "1") (pinfunction "1_1") (pintype "bidirectional"))
    )
    (net (code "321") (name "Net-(C182-Pad1)") (class "Default")
      (node (ref "C182") (pin "1") (pinfunction "1_1") (pintype "bidirectional"))
      (node (ref "R155") (pin "1") (pinfunction "1_1") (pintype "bidirectional"))
      (node (ref "R156") (pin "1") (pinfunction "1_1") (pintype "bidirectional"))
    )
    (net (code "322") (name "Net-(C200-Pad1)") (class "Default")
      (node (ref "C200") (pin "1") (pinfunction "1_1") (pintype "bidirectional"))
      (node (ref "R25") (pin "1") (pinfunction "1_1") (pintype "bidirectional"))
      (node (ref "R26") (pin "1") (pinfunction "1_1") (pintype "bidirectional"))
    )
    (net (code "323") (name "Net-(C206-Pad1)") (class "Default")
      (node (ref "C206") (pin "1") (pinfunction "1_1") (pintype "bidirectional"))
      (node (ref "R29") (pin "1") (pinfunction "1_1") (pintype "bidirectional"))
      (node (ref "R30") (pin "1") (pinfunction "1_1") (pintype "bidirectional"))
    )
    (net (code "324") (name "Net-(C212-Pad1)") (class "Default")
      (node (ref "C212") (pin "1") (pinfunction "1_1") (pintype "bidirectional"))
      (node (ref "R73") (pin "1") (pinfunction "1_1") (pintype "bidirectional"))
      (node (ref "R74") (pin "1") (pinfunction "1_1") (pintype "bidirectional"))
    )
    (net (code "325") (name "Net-(C218-Pad1)") (class "Default")
      (node (ref "C218") (pin "1") (pinfunction "1_1") (pintype "bidirectional"))
      (node (ref "R77") (pin "1") (pinfunction "1_1") (pintype "bidirectional"))
      (node (ref "R78") (pin "1") (pinfunction "1_1") (pintype "bidirectional"))
    )
    (net (code "326") (name "Net-(C224-Pad1)") (class "Default")
      (node (ref "C224") (pin "1") (pinfunction "1_1") (pintype "bidirectional"))
      (node (ref "R81") (pin "1") (pinfunction "1_1") (pintype "bidirectional"))
      (node (ref "R82") (pin "1") (pinfunction "1_1") (pintype "bidirectional"))
    )
    (net (code "327") (name "Net-(C230-Pad1)") (class "Default")
      (node (ref "C230") (pin "1") (pinfunction "1_1") (pintype "bidirectional"))
      (node (ref "R85") (pin "1") (pinfunction "1_1") (pintype "bidirectional"))
      (node (ref "R86") (pin "1") (pinfunction "1_1") (pintype "bidirectional"))
    )
    (net (code "328") (name "Net-(C236-Pad1)") (class "Default")
      (node (ref "C236") (pin "1") (pinfunction "1_1") (pintype "bidirectional"))
      (node (ref "R102") (pin "1") (pinfunction "1_1") (pintype "bidirectional"))
      (node (ref "R98") (pin "1") (pinfunction "1_1") (pintype "bidirectional"))
    )
    (net (code "329") (name "Net-(C242-Pad1)") (class "Default")
      (node (ref "C242") (pin "1") (pinfunction "1_1") (pintype "bidirectional"))
      (node (ref "R105") (pin "1") (pinfunction "1_1") (pintype "bidirectional"))
      (node (ref "R106") (pin "1") (pinfunction "1_1") (pintype "bidirectional"))
    )
    (net (code "330") (name "Net-(C248-Pad1)") (class "Default")
      (node (ref "C248") (pin "1") (pinfunction "1_1") (pintype "bidirectional"))
      (node (ref "R109") (pin "1") (pinfunction "1_1") (pintype "bidirectional"))
      (node (ref "R110") (pin "1") (pinfunction "1_1") (pintype "bidirectional"))
    )
    (net (code "331") (name "Net-(C254-Pad1)") (class "Default")
      (node (ref "C254") (pin "1") (pinfunction "1_1") (pintype "bidirectional"))
      (node (ref "R113") (pin "1") (pinfunction "1_1") (pintype "bidirectional"))
      (node (ref "R114") (pin "1") (pinfunction "1_1") (pintype "bidirectional"))
    )
    (net (code "332") (name "Net-(C260-Pad1)") (class "Default")
      (node (ref "C260") (pin "1") (pinfunction "1_1") (pintype "bidirectional"))
      (node (ref "R159") (pin "1") (pinfunction "1_1") (pintype "bidirectional"))
      (node (ref "R160") (pin "1") (pinfunction "1_1") (pintype "bidirectional"))
    )
    (net (code "333") (name "Net-(C266-Pad1)") (class "Default")
      (node (ref "C266") (pin "1") (pinfunction "1_1") (pintype "bidirectional"))
      (node (ref "R163") (pin "1") (pinfunction "1_1") (pintype "bidirectional"))
      (node (ref "R201") (pin "1") (pinfunction "1_1") (pintype "bidirectional"))
    )
    (net (code "334") (name "Net-(C272-Pad1)") (class "Default")
      (node (ref "C272") (pin "1") (pinfunction "1_1") (pintype "bidirectional"))
      (node (ref "R207") (pin "1") (pinfunction "1_1") (pintype "bidirectional"))
      (node (ref "R209") (pin "1") (pinfunction "1_1") (pintype "bidirectional"))
    )
    (net (code "335") (name "Net-(D45-GATE)") (class "Default")
      (node (ref "D45") (pin "1") (pinfunction "GATE_1") (pintype "bidirectional"))
      (node (ref "R36") (pin "1") (pinfunction "1_1") (pintype "bidirectional"))
    )
    (net (code "336") (name "Net-(D48-GATE)") (class "Default")
      (node (ref "D48") (pin "1") (pinfunction "GATE_1") (pintype "bidirectional"))
      (node (ref "R34") (pin "1") (pinfunction "1_1") (pintype "bidirectional"))
    )
    (net (code "337") (name "Net-(D75-GATE)") (class "Default")
      (node (ref "D75") (pin "1") (pinfunction "GATE_1") (pintype "bidirectional"))
      (node (ref "R38") (pin "1") (pinfunction "1_1") (pintype "bidirectional"))
    )
    (net (code "338") (name "Net-(D78-GATE)") (class "Default")
      (node (ref "D78") (pin "1") (pinfunction "GATE_1") (pintype "bidirectional"))
      (node (ref "R40") (pin "1") (pinfunction "1_1") (pintype "bidirectional"))
    )
    (net (code "339") (name "Net-(D79-GATE)") (class "Default")
      (node (ref "D79") (pin "1") (pinfunction "GATE_1") (pintype "bidirectional"))
      (node (ref "R44") (pin "1") (pinfunction "1_1") (pintype "bidirectional"))
    )
    (net (code "340") (name "Net-(D80-GATE)") (class "Default")
      (node (ref "D80") (pin "1") (pinfunction "GATE_1") (pintype "bidirectional"))
      (node (ref "R46") (pin "1") (pinfunction "1_1") (pintype "bidirectional"))
    )
    (net (code "341") (name "Net-(D81-GATE)") (class "Default")
      (node (ref "D81") (pin "1") (pinfunction "GATE_1") (pintype "bidirectional"))
      (node (ref "R48") (pin "1") (pinfunction "1_1") (pintype "bidirectional"))
    )
    (net (code "342") (name "Net-(D82-GATE)") (class "Default")
      (node (ref "D82") (pin "1") (pinfunction "GATE_1") (pintype "bidirectional"))
      (node (ref "R50") (pin "1") (pinfunction "1_1") (pintype "bidirectional"))
    )
    (net (code "343") (name "Net-(D84-DRAIN)") (class "Default")
      (node (ref "D84") (pin "3") (pinfunction "DRAIN_3") (pintype "bidirectional"))
      (node (ref "LED93") (pin "2") (pinfunction "A_2") (pintype "bidirectional"))
      (node (ref "R41") (pin "2") (pinfunction "2_2") (pintype "bidirectional"))
    )
    (net (code "344") (name "Net-(D84-GATE)") (class "Default")
      (node (ref "D84") (pin "1") (pinfunction "GATE_1") (pintype "bidirectional"))
      (node (ref "R42") (pin "1") (pinfunction "1_1") (pintype "bidirectional"))
    )
    (net (code "345") (name "Net-(D85-DRAIN)") (class "Default")
      (node (ref "D85") (pin "3") (pinfunction "DRAIN_3") (pintype "bidirectional"))
      (node (ref "LED94") (pin "2") (pinfunction "A_2") (pintype "bidirectional"))
      (node (ref "R51") (pin "2") (pinfunction "2_2") (pintype "bidirectional"))
    )
    (net (code "346") (name "Net-(D85-GATE)") (class "Default")
      (node (ref "D85") (pin "1") (pinfunction "GATE_1") (pintype "bidirectional"))
      (node (ref "R52") (pin "1") (pinfunction "1_1") (pintype "bidirectional"))
    )
    (net (code "347") (name "Net-(D86-DRAIN)") (class "Default")
      (node (ref "D86") (pin "3") (pinfunction "DRAIN_3") (pintype "bidirectional"))
      (node (ref "LED95") (pin "2") (pinfunction "A_2") (pintype "bidirectional"))
      (node (ref "R53") (pin "2") (pinfunction "2_2") (pintype "bidirectional"))
    )
    (net (code "348") (name "Net-(D86-GATE)") (class "Default")
      (node (ref "D86") (pin "1") (pinfunction "GATE_1") (pintype "bidirectional"))
      (node (ref "R54") (pin "1") (pinfunction "1_1") (pintype "bidirectional"))
    )
    (net (code "349") (name "Net-(D87-DRAIN)") (class "Default")
      (node (ref "D87") (pin "3") (pinfunction "DRAIN_3") (pintype "bidirectional"))
      (node (ref "LED96") (pin "2") (pinfunction "A_2") (pintype "bidirectional"))
      (node (ref "R55") (pin "2") (pinfunction "2_2") (pintype "bidirectional"))
    )
    (net (code "350") (name "Net-(D87-GATE)") (class "Default")
      (node (ref "D87") (pin "1") (pinfunction "GATE_1") (pintype "bidirectional"))
      (node (ref "R56") (pin "1") (pinfunction "1_1") (pintype "bidirectional"))
    )
    (net (code "351") (name "Net-(IC1-IN-)") (class "Default")
      (node (ref "IC1") (pin "1") (pinfunction "OUT_1") (pintype "bidirectional"))
      (node (ref "IC1") (pin "4") (pinfunction "IN-_4") (pintype "bidirectional"))
      (node (ref "R59") (pin "1") (pinfunction "1_1") (pintype "bidirectional"))
    )
    (net (code "352") (name "Net-(IC2-IN-)") (class "Default")
      (node (ref "IC2") (pin "1") (pinfunction "OUT_1") (pintype "bidirectional"))
      (node (ref "IC2") (pin "4") (pinfunction "IN-_4") (pintype "bidirectional"))
      (node (ref "R60") (pin "1") (pinfunction "1_1") (pintype "bidirectional"))
    )
    (net (code "353") (name "Net-(IC3-IN-)") (class "Default")
      (node (ref "IC3") (pin "1") (pinfunction "OUT_1") (pintype "bidirectional"))
      (node (ref "IC3") (pin "4") (pinfunction "IN-_4") (pintype "bidirectional"))
      (node (ref "R61") (pin "1") (pinfunction "1_1") (pintype "bidirectional"))
    )
    (net (code "354") (name "Net-(IC4-CONFIG)") (class "Default")
      (node (ref "C39") (pin "1") (pinfunction "1_1") (pintype "bidirectional"))
      (node (ref "IC4") (pin "2") (pinfunction "CONFIG_2") (pintype "bidirectional"))
      (node (ref "IC4") (pin "3") (pinfunction "INTVCC_3") (pintype "bidirectional"))
    )
    (net (code "355") (name "Net-(IC4-SS)") (class "Default")
      (node (ref "C37") (pin "1") (pinfunction "1_1") (pintype "bidirectional"))
      (node (ref "IC4") (pin "1") (pinfunction "SS_1") (pintype "bidirectional"))
    )
    (net (code "356") (name "Net-(IC4-TIMER)") (class "Default")
      (node (ref "C41") (pin "1") (pinfunction "1_1") (pintype "bidirectional"))
      (node (ref "IC4") (pin "8") (pinfunction "TIMER_8") (pintype "bidirectional"))
    )
    (net (code "357") (name "Net-(IC4-~{ALERT})") (class "Default")
      (node (ref "IC4") (pin "21") (pinfunction "~{ALERT}_21") (pintype "bidirectional"))
      (node (ref "LED2") (pin "1") (pinfunction "K_1") (pintype "bidirectional"))
    )
    (net (code "358") (name "Net-(IC11-CONFIG)") (class "Default")
      (node (ref "C45") (pin "1") (pinfunction "1_1") (pintype "bidirectional"))
      (node (ref "IC11") (pin "2") (pinfunction "CONFIG_2") (pintype "bidirectional"))
      (node (ref "IC11") (pin "3") (pinfunction "INTVCC_3") (pintype "bidirectional"))
    )
    (net (code "359") (name "Net-(IC11-SS)") (class "Default")
      (node (ref "C44") (pin "1") (pinfunction "1_1") (pintype "bidirectional"))
      (node (ref "IC11") (pin "1") (pinfunction "SS_1") (pintype "bidirectional"))
    )
    (net (code "360") (name "Net-(IC11-TIMER)") (class "Default")
      (node (ref "C46") (pin "1") (pinfunction "1_1") (pintype "bidirectional"))
      (node (ref "IC11") (pin "8") (pinfunction "TIMER_8") (pintype "bidirectional"))
    )
    (net (code "361") (name "Net-(IC11-~{ALERT})") (class "Default")
      (node (ref "IC11") (pin "21") (pinfunction "~{ALERT}_21") (pintype "bidirectional"))
      (node (ref "LED7") (pin "1") (pinfunction "K_1") (pintype "bidirectional"))
    )
    (net (code "362") (name "Net-(IC12-CONFIG)") (class "Default")
      (node (ref "C101") (pin "1") (pinfunction "1_1") (pintype "bidirectional"))
      (node (ref "IC12") (pin "2") (pinfunction "CONFIG_2") (pintype "bidirectional"))
      (node (ref "IC12") (pin "3") (pinfunction "INTVCC_3") (pintype "bidirectional"))
    )
    (net (code "363") (name "Net-(IC12-SS)") (class "Default")
      (node (ref "C99") (pin "1") (pinfunction "1_1") (pintype "bidirectional"))
      (node (ref "IC12") (pin "1") (pinfunction "SS_1") (pintype "bidirectional"))
    )
    (net (code "364") (name "Net-(IC12-TIMER)") (class "Default")
      (node (ref "C107") (pin "1") (pinfunction "1_1") (pintype "bidirectional"))
      (node (ref "IC12") (pin "8") (pinfunction "TIMER_8") (pintype "bidirectional"))
    )
    (net (code "365") (name "Net-(IC12-~{ALERT})") (class "Default")
      (node (ref "IC12") (pin "21") (pinfunction "~{ALERT}_21") (pintype "bidirectional"))
      (node (ref "LED12") (pin "1") (pinfunction "K_1") (pintype "bidirectional"))
    )
    (net (code "366") (name "Net-(IC13-CONFIG)") (class "Default")
      (node (ref "C115") (pin "1") (pinfunction "1_1") (pintype "bidirectional"))
      (node (ref "IC13") (pin "2") (pinfunction "CONFIG_2") (pintype "bidirectional"))
      (node (ref "IC13") (pin "3") (pinfunction "INTVCC_3") (pintype "bidirectional"))
    )
    (net (code "367") (name "Net-(IC13-SS)") (class "Default")
      (node (ref "C114") (pin "1") (pinfunction "1_1") (pintype "bidirectional"))
      (node (ref "IC13") (pin "1") (pinfunction "SS_1") (pintype "bidirectional"))
    )
    (net (code "368") (name "Net-(IC13-TIMER)") (class "Default")
      (node (ref "C116") (pin "1") (pinfunction "1_1") (pintype "bidirectional"))
      (node (ref "IC13") (pin "8") (pinfunction "TIMER_8") (pintype "bidirectional"))
    )
    (net (code "369") (name "Net-(IC13-~{ALERT})") (class "Default")
      (node (ref "IC13") (pin "21") (pinfunction "~{ALERT}_21") (pintype "bidirectional"))
      (node (ref "LED17") (pin "1") (pinfunction "K_1") (pintype "bidirectional"))
    )
    (net (code "370") (name "Net-(IC14-CONFIG)") (class "Default")
      (node (ref "C120") (pin "1") (pinfunction "1_1") (pintype "bidirectional"))
      (node (ref "IC14") (pin "2") (pinfunction "CONFIG_2") (pintype "bidirectional"))
      (node (ref "IC14") (pin "3") (pinfunction "INTVCC_3") (pintype "bidirectional"))
    )
    (net (code "371") (name "Net-(IC14-SS)") (class "Default")
      (node (ref "C119") (pin "1") (pinfunction "1_1") (pintype "bidirectional"))
      (node (ref "IC14") (pin "1") (pinfunction "SS_1") (pintype "bidirectional"))
    )
    (net (code "372") (name "Net-(IC14-TIMER)") (class "Default")
      (node (ref "C121") (pin "1") (pinfunction "1_1") (pintype "bidirectional"))
      (node (ref "IC14") (pin "8") (pinfunction "TIMER_8") (pintype "bidirectional"))
    )
    (net (code "373") (name "Net-(IC14-~{ALERT})") (class "Default")
      (node (ref "IC14") (pin "21") (pinfunction "~{ALERT}_21") (pintype "bidirectional"))
      (node (ref "LED22") (pin "1") (pinfunction "K_1") (pintype "bidirectional"))
    )
    (net (code "374") (name "Net-(IC15-CONFIG)") (class "Default")
      (node (ref "C125") (pin "1") (pinfunction "1_1") (pintype "bidirectional"))
      (node (ref "IC15") (pin "2") (pinfunction "CONFIG_2") (pintype "bidirectional"))
      (node (ref "IC15") (pin "3") (pinfunction "INTVCC_3") (pintype "bidirectional"))
    )
    (net (code "375") (name "Net-(IC15-SS)") (class "Default")
      (node (ref "C124") (pin "1") (pinfunction "1_1") (pintype "bidirectional"))
      (node (ref "IC15") (pin "1") (pinfunction "SS_1") (pintype "bidirectional"))
    )
    (net (code "376") (name "Net-(IC15-TIMER)") (class "Default")
      (node (ref "C126") (pin "1") (pinfunction "1_1") (pintype "bidirectional"))
      (node (ref "IC15") (pin "8") (pinfunction "TIMER_8") (pintype "bidirectional"))
    )
    (net (code "377") (name "Net-(IC15-~{ALERT})") (class "Default")
      (node (ref "IC15") (pin "21") (pinfunction "~{ALERT}_21") (pintype "bidirectional"))
      (node (ref "LED27") (pin "1") (pinfunction "K_1") (pintype "bidirectional"))
    )
    (net (code "378") (name "Net-(IC16-CONFIG)") (class "Default")
      (node (ref "C130") (pin "1") (pinfunction "1_1") (pintype "bidirectional"))
      (node (ref "IC16") (pin "2") (pinfunction "CONFIG_2") (pintype "bidirectional"))
      (node (ref "IC16") (pin "3") (pinfunction "INTVCC_3") (pintype "bidirectional"))
    )
    (net (code "379") (name "Net-(IC16-SS)") (class "Default")
      (node (ref "C129") (pin "1") (pinfunction "1_1") (pintype "bidirectional"))
      (node (ref "IC16") (pin "1") (pinfunction "SS_1") (pintype "bidirectional"))
    )
    (net (code "380") (name "Net-(IC16-TIMER)") (class "Default")
      (node (ref "C131") (pin "1") (pinfunction "1_1") (pintype "bidirectional"))
      (node (ref "IC16") (pin "8") (pinfunction "TIMER_8") (pintype "bidirectional"))
    )
    (net (code "381") (name "Net-(IC16-~{ALERT})") (class "Default")
      (node (ref "IC16") (pin "21") (pinfunction "~{ALERT}_21") (pintype "bidirectional"))
      (node (ref "LED32") (pin "1") (pinfunction "K_1") (pintype "bidirectional"))
    )
    (net (code "382") (name "Net-(IC17-CONFIG)") (class "Default")
      (node (ref "C135") (pin "1") (pinfunction "1_1") (pintype "bidirectional"))
      (node (ref "IC17") (pin "2") (pinfunction "CONFIG_2") (pintype "bidirectional"))
      (node (ref "IC17") (pin "3") (pinfunction "INTVCC_3") (pintype "bidirectional"))
    )
    (net (code "383") (name "Net-(IC17-SS)") (class "Default")
      (node (ref "C134") (pin "1") (pinfunction "1_1") (pintype "bidirectional"))
      (node (ref "IC17") (pin "1") (pinfunction "SS_1") (pintype "bidirectional"))
    )
    (net (code "384") (name "Net-(IC17-TIMER)") (class "Default")
      (node (ref "C136") (pin "1") (pinfunction "1_1") (pintype "bidirectional"))
      (node (ref "IC17") (pin "8") (pinfunction "TIMER_8") (pintype "bidirectional"))
    )
    (net (code "385") (name "Net-(IC17-~{ALERT})") (class "Default")
      (node (ref "IC17") (pin "21") (pinfunction "~{ALERT}_21") (pintype "bidirectional"))
      (node (ref "LED37") (pin "1") (pinfunction "K_1") (pintype "bidirectional"))
    )
    (net (code "386") (name "Net-(IC18-CONFIG)") (class "Default")
      (node (ref "C140") (pin "1") (pinfunction "1_1") (pintype "bidirectional"))
      (node (ref "IC18") (pin "2") (pinfunction "CONFIG_2") (pintype "bidirectional"))
      (node (ref "IC18") (pin "3") (pinfunction "INTVCC_3") (pintype "bidirectional"))
    )
    (net (code "387") (name "Net-(IC18-SS)") (class "Default")
      (node (ref "C139") (pin "1") (pinfunction "1_1") (pintype "bidirectional"))
      (node (ref "IC18") (pin "1") (pinfunction "SS_1") (pintype "bidirectional"))
    )
    (net (code "388") (name "Net-(IC18-TIMER)") (class "Default")
      (node (ref "C141") (pin "1") (pinfunction "1_1") (pintype "bidirectional"))
      (node (ref "IC18") (pin "8") (pinfunction "TIMER_8") (pintype "bidirectional"))
    )
    (net (code "389") (name "Net-(IC18-~{ALERT})") (class "Default")
      (node (ref "IC18") (pin "21") (pinfunction "~{ALERT}_21") (pintype "bidirectional"))
      (node (ref "LED42") (pin "1") (pinfunction "K_1") (pintype "bidirectional"))
    )
    (net (code "390") (name "Net-(IC19-CONFIG)") (class "Default")
      (node (ref "C145") (pin "1") (pinfunction "1_1") (pintype "bidirectional"))
      (node (ref "IC19") (pin "2") (pinfunction "CONFIG_2") (pintype "bidirectional"))
      (node (ref "IC19") (pin "3") (pinfunction "INTVCC_3") (pintype "bidirectional"))
    )
    (net (code "391") (name "Net-(IC19-SS)") (class "Default")
      (node (ref "C144") (pin "1") (pinfunction "1_1") (pintype "bidirectional"))
      (node (ref "IC19") (pin "1") (pinfunction "SS_1") (pintype "bidirectional"))
    )
    (net (code "392") (name "Net-(IC19-TIMER)") (class "Default")
      (node (ref "C146") (pin "1") (pinfunction "1_1") (pintype "bidirectional"))
      (node (ref "IC19") (pin "8") (pinfunction "TIMER_8") (pintype "bidirectional"))
    )
    (net (code "393") (name "Net-(IC19-~{ALERT})") (class "Default")
      (node (ref "IC19") (pin "21") (pinfunction "~{ALERT}_21") (pintype "bidirectional"))
      (node (ref "LED47") (pin "1") (pinfunction "K_1") (pintype "bidirectional"))
    )
    (net (code "394") (name "Net-(IC20-CONFIG)") (class "Default")
      (node (ref "C150") (pin "1") (pinfunction "1_1") (pintype "bidirectional"))
      (node (ref "IC20") (pin "2") (pinfunction "CONFIG_2") (pintype "bidirectional"))
      (node (ref "IC20") (pin "3") (pinfunction "INTVCC_3") (pintype "bidirectional"))
    )
    (net (code "395") (name "Net-(IC20-SS)") (class "Default")
      (node (ref "C149") (pin "1") (pinfunction "1_1") (pintype "bidirectional"))
      (node (ref "IC20") (pin "1") (pinfunction "SS_1") (pintype "bidirectional"))
    )
    (net (code "396") (name "Net-(IC20-TIMER)") (class "Default")
      (node (ref "C151") (pin "1") (pinfunction "1_1") (pintype "bidirectional"))
      (node (ref "IC20") (pin "8") (pinfunction "TIMER_8") (pintype "bidirectional"))
    )
    (net (code "397") (name "Net-(IC20-~{ALERT})") (class "Default")
      (node (ref "IC20") (pin "21") (pinfunction "~{ALERT}_21") (pintype "bidirectional"))
      (node (ref "LED52") (pin "1") (pinfunction "K_1") (pintype "bidirectional"))
    )
    (net (code "398") (name "Net-(IC21-CONFIG)") (class "Default")
      (node (ref "C155") (pin "1") (pinfunction "1_1") (pintype "bidirectional"))
      (node (ref "IC21") (pin "2") (pinfunction "CONFIG_2") (pintype "bidirectional"))
      (node (ref "IC21") (pin "3") (pinfunction "INTVCC_3") (pintype "bidirectional"))
    )
    (net (code "399") (name "Net-(IC21-SS)") (class "Default")
      (node (ref "C154") (pin "1") (pinfunction "1_1") (pintype "bidirectional"))
      (node (ref "IC21") (pin "1") (pinfunction "SS_1") (pintype "bidirectional"))
    )
    (net (code "400") (name "Net-(IC21-TIMER)") (class "Default")
      (node (ref "C156") (pin "1") (pinfunction "1_1") (pintype "bidirectional"))
      (node (ref "IC21") (pin "8") (pinfunction "TIMER_8") (pintype "bidirectional"))
    )
    (net (code "401") (name "Net-(IC21-~{ALERT})") (class "Default")
      (node (ref "IC21") (pin "21") (pinfunction "~{ALERT}_21") (pintype "bidirectional"))
      (node (ref "LED57") (pin "1") (pinfunction "K_1") (pintype "bidirectional"))
    )
    (net (code "402") (name "Net-(IC22-CONFIG)") (class "Default")
      (node (ref "C160") (pin "1") (pinfunction "1_1") (pintype "bidirectional"))
      (node (ref "IC22") (pin "2") (pinfunction "CONFIG_2") (pintype "bidirectional"))
      (node (ref "IC22") (pin "3") (pinfunction "INTVCC_3") (pintype "bidirectional"))
    )
    (net (code "403") (name "Net-(IC22-SS)") (class "Default")
      (node (ref "C159") (pin "1") (pinfunction "1_1") (pintype "bidirectional"))
      (node (ref "IC22") (pin "1") (pinfunction "SS_1") (pintype "bidirectional"))
    )
    (net (code "404") (name "Net-(IC22-TIMER)") (class "Default")
      (node (ref "C161") (pin "1") (pinfunction "1_1") (pintype "bidirectional"))
      (node (ref "IC22") (pin "8") (pinfunction "TIMER_8") (pintype "bidirectional"))
    )
    (net (code "405") (name "Net-(IC22-~{ALERT})") (class "Default")
      (node (ref "IC22") (pin "21") (pinfunction "~{ALERT}_21") (pintype "bidirectional"))
      (node (ref "LED62") (pin "1") (pinfunction "K_1") (pintype "bidirectional"))
    )
    (net (code "406") (name "Net-(IC23-CONFIG)") (class "Default")
      (node (ref "C165") (pin "1") (pinfunction "1_1") (pintype "bidirectional"))
      (node (ref "IC23") (pin "2") (pinfunction "CONFIG_2") (pintype "bidirectional"))
      (node (ref "IC23") (pin "3") (pinfunction "INTVCC_3") (pintype "bidirectional"))
    )
    (net (code "407") (name "Net-(IC23-SS)") (class "Default")
      (node (ref "C164") (pin "1") (pinfunction "1_1") (pintype "bidirectional"))
      (node (ref "IC23") (pin "1") (pinfunction "SS_1") (pintype "bidirectional"))
    )
    (net (code "408") (name "Net-(IC23-TIMER)") (class "Default")
      (node (ref "C166") (pin "1") (pinfunction "1_1") (pintype "bidirectional"))
      (node (ref "IC23") (pin "8") (pinfunction "TIMER_8") (pintype "bidirectional"))
    )
    (net (code "409") (name "Net-(IC23-~{ALERT})") (class "Default")
      (node (ref "IC23") (pin "21") (pinfunction "~{ALERT}_21") (pintype "bidirectional"))
      (node (ref "LED67") (pin "1") (pinfunction "K_1") (pintype "bidirectional"))
    )
    (net (code "410") (name "Net-(IC33-A_N)") (class "Default")
      (node (ref "IC33") (pin "3") (pinfunction "A_N_3") (pintype "bidirectional"))
      (node (ref "R514") (pin "1") (pinfunction "1_1") (pintype "bidirectional"))
    )
    (net (code "411") (name "Net-(IC33-A_P)") (class "Default")
      (node (ref "IC33") (pin "2") (pinfunction "A_P_2") (pintype "bidirectional"))
      (node (ref "R513") (pin "1") (pinfunction "1_1") (pintype "bidirectional"))
    )
    (net (code "412") (name "Net-(IC34-CAP+)") (class "Default")
      (node (ref "C173") (pin "1") (pinfunction "1_1") (pintype "bidirectional"))
      (node (ref "IC34") (pin "2") (pinfunction "CAP+_2") (pintype "bidirectional"))
    )
    (net (code "413") (name "Net-(IC34-CAP-)") (class "Default")
      (node (ref "C173") (pin "2") (pinfunction "2_2") (pintype "bidirectional"))
      (node (ref "IC34") (pin "4") (pinfunction "CAP-_4") (pintype "bidirectional"))
    )
    (net (code "414") (name "Net-(IC35-IN+)") (class "Default")
      (node (ref "C175") (pin "1") (pinfunction "1_1") (pintype "bidirectional"))
      (node (ref "IC35") (pin "3") (pinfunction "IN+_3") (pintype "bidirectional"))
      (node (ref "R152") (pin "2") (pinfunction "2_2") (pintype "bidirectional"))
    )
    (net (code "415") (name "Net-(IC35-IN-)") (class "Default")
      (node (ref "C176") (pin "2") (pinfunction "2_2") (pintype "bidirectional"))
      (node (ref "IC35") (pin "1") (pinfunction "OUT_1") (pintype "bidirectional"))
      (node (ref "IC35") (pin "4") (pinfunction "IN-_4") (pintype "bidirectional"))
      (node (ref "IC36") (pin "3") (pinfunction "IN+_3") (pintype "bidirectional"))
    )
    (net (code "416") (name "Net-(IC36-IN-)") (class "Default")
      (node (ref "IC36") (pin "4") (pinfunction "IN-_4") (pintype "bidirectional"))
      (node (ref "R153") (pin "1") (pinfunction "1_1") (pintype "bidirectional"))
      (node (ref "R154") (pin "2") (pinfunction "2_2") (pintype "bidirectional"))
    )
    (net (code "417") (name "Net-(IC37-IN+)") (class "Default")
      (node (ref "C181") (pin "1") (pinfunction "1_1") (pintype "bidirectional"))
      (node (ref "IC37") (pin "3") (pinfunction "IN+_3") (pintype "bidirectional"))
      (node (ref "R156") (pin "2") (pinfunction "2_2") (pintype "bidirectional"))
    )
    (net (code "418") (name "Net-(IC37-IN-)") (class "Default")
      (node (ref "C182") (pin "2") (pinfunction "2_2") (pintype "bidirectional"))
      (node (ref "IC37") (pin "1") (pinfunction "OUT_1") (pintype "bidirectional"))
      (node (ref "IC37") (pin "4") (pinfunction "IN-_4") (pintype "bidirectional"))
      (node (ref "IC39") (pin "3") (pinfunction "IN+_3") (pintype "bidirectional"))
    )
    (net (code "419") (name "Net-(IC39-IN-)") (class "Default")
      (node (ref "IC39") (pin "4") (pinfunction "IN-_4") (pintype "bidirectional"))
      (node (ref "R157") (pin "2") (pinfunction "2_2") (pintype "bidirectional"))
      (node (ref "R158") (pin "1") (pinfunction "1_1") (pintype "bidirectional"))
    )
    (net (code "420") (name "Net-(IC40-IN+)") (class "Default")
      (node (ref "C47") (pin "1") (pinfunction "1_1") (pintype "bidirectional"))
      (node (ref "IC40") (pin "3") (pinfunction "IN+_3") (pintype "bidirectional"))
      (node (ref "R2") (pin "2") (pinfunction "2_2") (pintype "bidirectional"))
    )
    (net (code "421") (name "Net-(IC40-IN-)") (class "Default")
      (node (ref "C48") (pin "2") (pinfunction "2_2") (pintype "bidirectional"))
      (node (ref "IC40") (pin "1") (pinfunction "OUT_1") (pintype "bidirectional"))
      (node (ref "IC40") (pin "4") (pinfunction "IN-_4") (pintype "bidirectional"))
      (node (ref "IC41") (pin "3") (pinfunction "IN+_3") (pintype "bidirectional"))
    )
    (net (code "422") (name "Net-(IC41-IN-)") (class "Default")
      (node (ref "IC41") (pin "4") (pinfunction "IN-_4") (pintype "bidirectional"))
      (node (ref "R3") (pin "2") (pinfunction "2_2") (pintype "bidirectional"))
      (node (ref "R4") (pin "1") (pinfunction "1_1") (pintype "bidirectional"))
    )
    (net (code "423") (name "Net-(IC42-IN+)") (class "Default")
      (node (ref "C53") (pin "1") (pinfunction "1_1") (pintype "bidirectional"))
      (node (ref "IC42") (pin "3") (pinfunction "IN+_3") (pintype "bidirectional"))
      (node (ref "R6") (pin "2") (pinfunction "2_2") (pintype "bidirectional"))
    )
    (net (code "424") (name "Net-(IC42-IN-)") (class "Default")
      (node (ref "C54") (pin "2") (pinfunction "2_2") (pintype "bidirectional"))
      (node (ref "IC42") (pin "1") (pinfunction "OUT_1") (pintype "bidirectional"))
      (node (ref "IC42") (pin "4") (pinfunction "IN-_4") (pintype "bidirectional"))
      (node (ref "IC43") (pin "3") (pinfunction "IN+_3") (pintype "bidirectional"))
    )
    (net (code "425") (name "Net-(IC43-IN-)") (class "Default")
      (node (ref "IC43") (pin "4") (pinfunction "IN-_4") (pintype "bidirectional"))
      (node (ref "R7") (pin "2") (pinfunction "2_2") (pintype "bidirectional"))
      (node (ref "R8") (pin "1") (pinfunction "1_1") (pintype "bidirectional"))
    )
    (net (code "426") (name "Net-(IC44-IN+)") (class "Default")
      (node (ref "C78") (pin "1") (pinfunction "1_1") (pintype "bidirectional"))
      (node (ref "IC44") (pin "3") (pinfunction "IN+_3") (pintype "bidirectional"))
      (node (ref "R10") (pin "2") (pinfunction "2_2") (pintype "bidirectional"))
    )
    (net (code "427") (name "Net-(IC44-IN-)") (class "Default")
      (node (ref "C79") (pin "2") (pinfunction "2_2") (pintype "bidirectional"))
      (node (ref "IC44") (pin "1") (pinfunction "OUT_1") (pintype "bidirectional"))
      (node (ref "IC44") (pin "4") (pinfunction "IN-_4") (pintype "bidirectional"))
      (node (ref "IC45") (pin "3") (pinfunction "IN+_3") (pintype "bidirectional"))
    )
    (net (code "428") (name "Net-(IC45-IN-)") (class "Default")
      (node (ref "IC45") (pin "4") (pinfunction "IN-_4") (pintype "bidirectional"))
      (node (ref "R11") (pin "2") (pinfunction "2_2") (pintype "bidirectional"))
      (node (ref "R12") (pin "1") (pinfunction "1_1") (pintype "bidirectional"))
    )
    (net (code "429") (name "Net-(IC46-IN+)") (class "Default")
      (node (ref "C55") (pin "1") (pinfunction "1_1") (pintype "bidirectional"))
      (node (ref "IC46") (pin "3") (pinfunction "IN+_3") (pintype "bidirectional"))
      (node (ref "R14") (pin "2") (pinfunction "2_2") (pintype "bidirectional"))
    )
    (net (code "430") (name "Net-(IC46-IN-)") (class "Default")
      (node (ref "C56") (pin "2") (pinfunction "2_2") (pintype "bidirectional"))
      (node (ref "IC46") (pin "1") (pinfunction "OUT_1") (pintype "bidirectional"))
      (node (ref "IC46") (pin "4") (pinfunction "IN-_4") (pintype "bidirectional"))
      (node (ref "IC47") (pin "3") (pinfunction "IN+_3") (pintype "bidirectional"))
    )
    (net (code "431") (name "Net-(IC47-IN-)") (class "Default")
      (node (ref "IC47") (pin "4") (pinfunction "IN-_4") (pintype "bidirectional"))
      (node (ref "R15") (pin "2") (pinfunction "2_2") (pintype "bidirectional"))
      (node (ref "R16") (pin "1") (pinfunction "1_1") (pintype "bidirectional"))
    )
    (net (code "432") (name "Net-(IC48-IN+)") (class "Default")
      (node (ref "C61") (pin "1") (pinfunction "1_1") (pintype "bidirectional"))
      (node (ref "IC48") (pin "3") (pinfunction "IN+_3") (pintype "bidirectional"))
      (node (ref "R18") (pin "2") (pinfunction "2_2") (pintype "bidirectional"))
    )
    (net (code "433") (name "Net-(IC48-IN-)") (class "Default")
      (node (ref "C62") (pin "2") (pinfunction "2_2") (pintype "bidirectional"))
      (node (ref "IC48") (pin "1") (pinfunction "OUT_1") (pintype "bidirectional"))
      (node (ref "IC48") (pin "4") (pinfunction "IN-_4") (pintype "bidirectional"))
      (node (ref "IC49") (pin "3") (pinfunction "IN+_3") (pintype "bidirectional"))
    )
    (net (code "434") (name "Net-(IC49-IN-)") (class "Default")
      (node (ref "IC49") (pin "4") (pinfunction "IN-_4") (pintype "bidirectional"))
      (node (ref "R19") (pin "2") (pinfunction "2_2") (pintype "bidirectional"))
      (node (ref "R20") (pin "1") (pinfunction "1_1") (pintype "bidirectional"))
    )
    (net (code "435") (name "Net-(IC50-IN+)") (class "Default")
      (node (ref "C86") (pin "1") (pinfunction "1_1") (pintype "bidirectional"))
      (node (ref "IC50") (pin "3") (pinfunction "IN+_3") (pintype "bidirectional"))
      (node (ref "R22") (pin "2") (pinfunction "2_2") (pintype "bidirectional"))
    )
    (net (code "436") (name "Net-(IC50-IN-)") (class "Default")
      (node (ref "C87") (pin "2") (pinfunction "2_2") (pintype "bidirectional"))
      (node (ref "IC50") (pin "1") (pinfunction "OUT_1") (pintype "bidirectional"))
      (node (ref "IC50") (pin "4") (pinfunction "IN-_4") (pintype "bidirectional"))
      (node (ref "IC53") (pin "3") (pinfunction "IN+_3") (pintype "bidirectional"))
    )
    (net (code "437") (name "Net-(IC53-IN-)") (class "Default")
      (node (ref "IC53") (pin "4") (pinfunction "IN-_4") (pintype "bidirectional"))
      (node (ref "R23") (pin "2") (pinfunction "2_2") (pintype "bidirectional"))
      (node (ref "R24") (pin "1") (pinfunction "1_1") (pintype "bidirectional"))
    )
    (net (code "438") (name "Net-(IC54-IN+)") (class "Default")
      (node (ref "C199") (pin "1") (pinfunction "1_1") (pintype "bidirectional"))
      (node (ref "IC54") (pin "3") (pinfunction "IN+_3") (pintype "bidirectional"))
      (node (ref "R26") (pin "2") (pinfunction "2_2") (pintype "bidirectional"))
    )
    (net (code "439") (name "Net-(IC54-IN-)") (class "Default")
      (node (ref "C200") (pin "2") (pinfunction "2_2") (pintype "bidirectional"))
      (node (ref "IC54") (pin "1") (pinfunction "OUT_1") (pintype "bidirectional"))
      (node (ref "IC54") (pin "4") (pinfunction "IN-_4") (pintype "bidirectional"))
      (node (ref "IC55") (pin "3") (pinfunction "IN+_3") (pintype "bidirectional"))
    )
    (net (code "440") (name "Net-(IC55-IN-)") (class "Default")
      (node (ref "IC55") (pin "4") (pinfunction "IN-_4") (pintype "bidirectional"))
      (node (ref "R27") (pin "2") (pinfunction "2_2") (pintype "bidirectional"))
      (node (ref "R28") (pin "1") (pinfunction "1_1") (pintype "bidirectional"))
    )
    (net (code "441") (name "Net-(IC56-IN+)") (class "Default")
      (node (ref "C205") (pin "1") (pinfunction "1_1") (pintype "bidirectional"))
      (node (ref "IC56") (pin "3") (pinfunction "IN+_3") (pintype "bidirectional"))
      (node (ref "R30") (pin "2") (pinfunction "2_2") (pintype "bidirectional"))
    )
    (net (code "442") (name "Net-(IC56-IN-)") (class "Default")
      (node (ref "C206") (pin "2") (pinfunction "2_2") (pintype "bidirectional"))
      (node (ref "IC56") (pin "1") (pinfunction "OUT_1") (pintype "bidirectional"))
      (node (ref "IC56") (pin "4") (pinfunction "IN-_4") (pintype "bidirectional"))
      (node (ref "IC57") (pin "3") (pinfunction "IN+_3") (pintype "bidirectional"))
    )
    (net (code "443") (name "Net-(IC57-IN-)") (class "Default")
      (node (ref "IC57") (pin "4") (pinfunction "IN-_4") (pintype "bidirectional"))
      (node (ref "R31") (pin "2") (pinfunction "2_2") (pintype "bidirectional"))
      (node (ref "R32") (pin "1") (pinfunction "1_1") (pintype "bidirectional"))
    )
    (net (code "444") (name "Net-(IC58-IN+)") (class "Default")
      (node (ref "C211") (pin "1") (pinfunction "1_1") (pintype "bidirectional"))
      (node (ref "IC58") (pin "3") (pinfunction "IN+_3") (pintype "bidirectional"))
      (node (ref "R74") (pin "2") (pinfunction "2_2") (pintype "bidirectional"))
    )
    (net (code "445") (name "Net-(IC58-IN-)") (class "Default")
      (node (ref "C212") (pin "2") (pinfunction "2_2") (pintype "bidirectional"))
      (node (ref "IC58") (pin "1") (pinfunction "OUT_1") (pintype "bidirectional"))
      (node (ref "IC58") (pin "4") (pinfunction "IN-_4") (pintype "bidirectional"))
      (node (ref "IC59") (pin "3") (pinfunction "IN+_3") (pintype "bidirectional"))
    )
    (net (code "446") (name "Net-(IC59-IN-)") (class "Default")
      (node (ref "IC59") (pin "4") (pinfunction "IN-_4") (pintype "bidirectional"))
      (node (ref "R75") (pin "2") (pinfunction "2_2") (pintype "bidirectional"))
      (node (ref "R76") (pin "1") (pinfunction "1_1") (pintype "bidirectional"))
    )
    (net (code "447") (name "Net-(IC60-IN+)") (class "Default")
      (node (ref "C217") (pin "1") (pinfunction "1_1") (pintype "bidirectional"))
      (node (ref "IC60") (pin "3") (pinfunction "IN+_3") (pintype "bidirectional"))
      (node (ref "R78") (pin "2") (pinfunction "2_2") (pintype "bidirectional"))
    )
    (net (code "448") (name "Net-(IC60-IN-)") (class "Default")
      (node (ref "C218") (pin "2") (pinfunction "2_2") (pintype "bidirectional"))
      (node (ref "IC60") (pin "1") (pinfunction "OUT_1") (pintype "bidirectional"))
      (node (ref "IC60") (pin "4") (pinfunction "IN-_4") (pintype "bidirectional"))
      (node (ref "IC61") (pin "3") (pinfunction "IN+_3") (pintype "bidirectional"))
    )
    (net (code "449") (name "Net-(IC61-IN-)") (class "Default")
      (node (ref "IC61") (pin "4") (pinfunction "IN-_4") (pintype "bidirectional"))
      (node (ref "R79") (pin "2") (pinfunction "2_2") (pintype "bidirectional"))
      (node (ref "R80") (pin "1") (pinfunction "1_1") (pintype "bidirectional"))
    )
    (net (code "450") (name "Net-(IC62-IN+)") (class "Default")
      (node (ref "C223") (pin "1") (pinfunction "1_1") (pintype "bidirectional"))
      (node (ref "IC62") (pin "3") (pinfunction "IN+_3") (pintype "bidirectional"))
      (node (ref "R82") (pin "2") (pinfunction "2_2") (pintype "bidirectional"))
    )
    (net (code "451") (name "Net-(IC62-IN-)") (class "Default")
      (node (ref "C224") (pin "2") (pinfunction "2_2") (pintype "bidirectional"))
      (node (ref "IC62") (pin "1") (pinfunction "OUT_1") (pintype "bidirectional"))
      (node (ref "IC62") (pin "4") (pinfunction "IN-_4") (pintype "bidirectional"))
      (node (ref "IC63") (pin "3") (pinfunction "IN+_3") (pintype "bidirectional"))
    )
    (net (code "452") (name "Net-(IC63-IN-)") (class "Default")
      (node (ref "IC63") (pin "4") (pinfunction "IN-_4") (pintype "bidirectional"))
      (node (ref "R83") (pin "2") (pinfunction "2_2") (pintype "bidirectional"))
      (node (ref "R84") (pin "1") (pinfunction "1_1") (pintype "bidirectional"))
    )
    (net (code "453") (name "Net-(IC64-IN+)") (class "Default")
      (node (ref "C229") (pin "1") (pinfunction "1_1") (pintype "bidirectional"))
      (node (ref "IC64") (pin "3") (pinfunction "IN+_3") (pintype "bidirectional"))
      (node (ref "R86") (pin "2") (pinfunction "2_2") (pintype "bidirectional"))
    )
    (net (code "454") (name "Net-(IC64-IN-)") (class "Default")
      (node (ref "C230") (pin "2") (pinfunction "2_2") (pintype "bidirectional"))
      (node (ref "IC64") (pin "1") (pinfunction "OUT_1") (pintype "bidirectional"))
      (node (ref "IC64") (pin "4") (pinfunction "IN-_4") (pintype "bidirectional"))
      (node (ref "IC65") (pin "3") (pinfunction "IN+_3") (pintype "bidirectional"))
    )
    (net (code "455") (name "Net-(IC65-IN-)") (class "Default")
      (node (ref "IC65") (pin "4") (pinfunction "IN-_4") (pintype "bidirectional"))
      (node (ref "R87") (pin "2") (pinfunction "2_2") (pintype "bidirectional"))
      (node (ref "R88") (pin "1") (pinfunction "1_1") (pintype "bidirectional"))
    )
    (net (code "456") (name "Net-(IC66-IN+)") (class "Default")
      (node (ref "C235") (pin "1") (pinfunction "1_1") (pintype "bidirectional"))
      (node (ref "IC66") (pin "3") (pinfunction "IN+_3") (pintype "bidirectional"))
      (node (ref "R102") (pin "2") (pinfunction "2_2") (pintype "bidirectional"))
    )
    (net (code "457") (name "Net-(IC66-IN-)") (class "Default")
      (node (ref "C236") (pin "2") (pinfunction "2_2") (pintype "bidirectional"))
      (node (ref "IC66") (pin "1") (pinfunction "OUT_1") (pintype "bidirectional"))
      (node (ref "IC66") (pin "4") (pinfunction "IN-_4") (pintype "bidirectional"))
      (node (ref "IC67") (pin "3") (pinfunction "IN+_3") (pintype "bidirectional"))
    )
    (net (code "458") (name "Net-(IC67-IN-)") (class "Default")
      (node (ref "IC67") (pin "4") (pinfunction "IN-_4") (pintype "bidirectional"))
      (node (ref "R103") (pin "2") (pinfunction "2_2") (pintype "bidirectional"))
      (node (ref "R104") (pin "1") (pinfunction "1_1") (pintype "bidirectional"))
    )
    (net (code "459") (name "Net-(IC68-IN+)") (class "Default")
      (node (ref "C241") (pin "1") (pinfunction "1_1") (pintype "bidirectional"))
      (node (ref "IC68") (pin "3") (pinfunction "IN+_3") (pintype "bidirectional"))
      (node (ref "R106") (pin "2") (pinfunction "2_2") (pintype "bidirectional"))
    )
    (net (code "460") (name "Net-(IC68-IN-)") (class "Default")
      (node (ref "C242") (pin "2") (pinfunction "2_2") (pintype "bidirectional"))
      (node (ref "IC68") (pin "1") (pinfunction "OUT_1") (pintype "bidirectional"))
      (node (ref "IC68") (pin "4") (pinfunction "IN-_4") (pintype "bidirectional"))
      (node (ref "IC69") (pin "3") (pinfunction "IN+_3") (pintype "bidirectional"))
    )
    (net (code "461") (name "Net-(IC69-IN-)") (class "Default")
      (node (ref "IC69") (pin "4") (pinfunction "IN-_4") (pintype "bidirectional"))
      (node (ref "R107") (pin "2") (pinfunction "2_2") (pintype "bidirectional"))
      (node (ref "R108") (pin "1") (pinfunction "1_1") (pintype "bidirectional"))
    )
    (net (code "462") (name "Net-(IC70-IN+)") (class "Default")
      (node (ref "C247") (pin "1") (pinfunction "1_1") (pintype "bidirectional"))
      (node (ref "IC70") (pin "3") (pinfunction "IN+_3") (pintype "bidirectional"))
      (node (ref "R110") (pin "2") (pinfunction "2_2") (pintype "bidirectional"))
    )
    (net (code "463") (name "Net-(IC70-IN-)") (class "Default")
      (node (ref "C248") (pin "2") (pinfunction "2_2") (pintype "bidirectional"))
      (node (ref "IC70") (pin "1") (pinfunction "OUT_1") (pintype "bidirectional"))
      (node (ref "IC70") (pin "4") (pinfunction "IN-_4") (pintype "bidirectional"))
      (node (ref "IC71") (pin "3") (pinfunction "IN+_3") (pintype "bidirectional"))
    )
    (net (code "464") (name "Net-(IC71-IN-)") (class "Default")
      (node (ref "IC71") (pin "4") (pinfunction "IN-_4") (pintype "bidirectional"))
      (node (ref "R111") (pin "2") (pinfunction "2_2") (pintype "bidirectional"))
      (node (ref "R112") (pin "1") (pinfunction "1_1") (pintype "bidirectional"))
    )
    (net (code "465") (name "Net-(IC72-IN+)") (class "Default")
      (node (ref "C253") (pin "1") (pinfunction "1_1") (pintype "bidirectional"))
      (node (ref "IC72") (pin "3") (pinfunction "IN+_3") (pintype "bidirectional"))
      (node (ref "R114") (pin "2") (pinfunction "2_2") (pintype "bidirectional"))
    )
    (net (code "466") (name "Net-(IC72-IN-)") (class "Default")
      (node (ref "C254") (pin "2") (pinfunction "2_2") (pintype "bidirectional"))
      (node (ref "IC72") (pin "1") (pinfunction "OUT_1") (pintype "bidirectional"))
      (node (ref "IC72") (pin "4") (pinfunction "IN-_4") (pintype "bidirectional"))
      (node (ref "IC73") (pin "3") (pinfunction "IN+_3") (pintype "bidirectional"))
    )
    (net (code "467") (name "Net-(IC73-IN-)") (class "Default")
      (node (ref "IC73") (pin "4") (pinfunction "IN-_4") (pintype "bidirectional"))
      (node (ref "R115") (pin "2") (pinfunction "2_2") (pintype "bidirectional"))
      (node (ref "R116") (pin "1") (pinfunction "1_1") (pintype "bidirectional"))
    )
    (net (code "468") (name "Net-(IC74-IN+)") (class "Default")
      (node (ref "C259") (pin "1") (pinfunction "1_1") (pintype "bidirectional"))
      (node (ref "IC74") (pin "3") (pinfunction "IN+_3") (pintype "bidirectional"))
      (node (ref "R160") (pin "2") (pinfunction "2_2") (pintype "bidirectional"))
    )
    (net (code "469") (name "Net-(IC74-IN-)") (class "Default")
      (node (ref "C260") (pin "2") (pinfunction "2_2") (pintype "bidirectional"))
      (node (ref "IC74") (pin "1") (pinfunction "OUT_1") (pintype "bidirectional"))
      (node (ref "IC74") (pin "4") (pinfunction "IN-_4") (pintype "bidirectional"))
      (node (ref "IC75") (pin "3") (pinfunction "IN+_3") (pintype "bidirectional"))
    )
    (net (code "470") (name "Net-(IC75-IN-)") (class "Default")
      (node (ref "IC75") (pin "4") (pinfunction "IN-_4") (pintype "bidirectional"))
      (node (ref "R161") (pin "2") (pinfunction "2_2") (pintype "bidirectional"))
      (node (ref "R162") (pin "1") (pinfunction "1_1") (pintype "bidirectional"))
    )
    (net (code "471") (name "Net-(IC76-IN+)") (class "Default")
      (node (ref "C265") (pin "1") (pinfunction "1_1") (pintype "bidirectional"))
      (node (ref "IC76") (pin "3") (pinfunction "IN+_3") (pintype "bidirectional"))
      (node (ref "R201") (pin "2") (pinfunction "2_2") (pintype "bidirectional"))
    )
    (net (code "472") (name "Net-(IC76-IN-)") (class "Default")
      (node (ref "C266") (pin "2") (pinfunction "2_2") (pintype "bidirectional"))
      (node (ref "IC76") (pin "1") (pinfunction "OUT_1") (pintype "bidirectional"))
      (node (ref "IC76") (pin "4") (pinfunction "IN-_4") (pintype "bidirectional"))
      (node (ref "IC77") (pin "3") (pinfunction "IN+_3") (pintype "bidirectional"))
    )
    (net (code "473") (name "Net-(IC77-IN-)") (class "Default")
      (node (ref "IC77") (pin "4") (pinfunction "IN-_4") (pintype "bidirectional"))
      (node (ref "R203") (pin "2") (pinfunction "2_2") (pintype "bidirectional"))
      (node (ref "R205") (pin "1") (pinfunction "1_1") (pintype "bidirectional"))
    )
    (net (code "474") (name "Net-(IC78-IN+)") (class "Default")
      (node (ref "C271") (pin "1") (pinfunction "1_1") (pintype "bidirectional"))
      (node (ref "IC78") (pin "3") (pinfunction "IN+_3") (pintype "bidirectional"))
      (node (ref "R209") (pin "2") (pinfunction "2_2") (pintype "bidirectional"))
    )
    (net (code "475") (name "Net-(IC78-IN-)") (class "Default")
      (node (ref "C272") (pin "2") (pinfunction "2_2") (pintype "bidirectional"))
      (node (ref "IC78") (pin "1") (pinfunction "OUT_1") (pintype "bidirectional"))
      (node (ref "IC78") (pin "4") (pinfunction "IN-_4") (pintype "bidirectional"))
      (node (ref "IC79") (pin "3") (pinfunction "IN+_3") (pintype "bidirectional"))
    )
    (net (code "476") (name "Net-(IC79-IN-)") (class "Default")
      (node (ref "IC79") (pin "4") (pinfunction "IN-_4") (pintype "bidirectional"))
      (node (ref "R211") (pin "2") (pinfunction "2_2") (pintype "bidirectional"))
      (node (ref "R221") (pin "1") (pinfunction "1_1") (pintype "bidirectional"))
    )
    (net (code "477") (name "Net-(LED1-A)") (class "Default")
      (node (ref "LED1") (pin "2") (pinfunction "A_2") (pintype "bidirectional"))
      (node (ref "R97") (pin "1") (pinfunction "1_1") (pintype "bidirectional"))
    )
    (net (code "478") (name "Net-(LED2-A)") (class "Default")
      (node (ref "LED2") (pin "2") (pinfunction "A_2") (pintype "bidirectional"))
      (node (ref "R99") (pin "1") (pinfunction "1_1") (pintype "bidirectional"))
    )
    (net (code "479") (name "Net-(LED3-A)") (class "Default")
      (node (ref "LED3") (pin "1") (pinfunction "A_1") (pintype "bidirectional"))
      (node (ref "R100") (pin "1") (pinfunction "1_1") (pintype "bidirectional"))
    )
    (net (code "480") (name "Net-(LED4-A)") (class "Default")
      (node (ref "LED4") (pin "2") (pinfunction "A_2") (pintype "bidirectional"))
      (node (ref "R134") (pin "1") (pinfunction "1_1") (pintype "bidirectional"))
    )
    (net (code "481") (name "Net-(LED5-A)") (class "Default")
      (node (ref "LED5") (pin "1") (pinfunction "A_1") (pintype "bidirectional"))
      (node (ref "R135") (pin "1") (pinfunction "1_1") (pintype "bidirectional"))
    )
    (net (code "482") (name "Net-(LED6-A)") (class "Default")
      (node (ref "LED6") (pin "2") (pinfunction "A_2") (pintype "bidirectional"))
      (node (ref "R144") (pin "1") (pinfunction "1_1") (pintype "bidirectional"))
    )
    (net (code "483") (name "Net-(LED7-A)") (class "Default")
      (node (ref "LED7") (pin "2") (pinfunction "A_2") (pintype "bidirectional"))
      (node (ref "R145") (pin "1") (pinfunction "1_1") (pintype "bidirectional"))
    )
    (net (code "484") (name "Net-(LED8-A)") (class "Default")
      (node (ref "LED8") (pin "1") (pinfunction "A_1") (pintype "bidirectional"))
      (node (ref "R146") (pin "1") (pinfunction "1_1") (pintype "bidirectional"))
    )
    (net (code "485") (name "Net-(LED9-A)") (class "Default")
      (node (ref "LED9") (pin "2") (pinfunction "A_2") (pintype "bidirectional"))
      (node (ref "R172") (pin "1") (pinfunction "1_1") (pintype "bidirectional"))
    )
    (net (code "486") (name "Net-(LED10-A)") (class "Default")
      (node (ref "LED10") (pin "1") (pinfunction "A_1") (pintype "bidirectional"))
      (node (ref "R173") (pin "1") (pinfunction "1_1") (pintype "bidirectional"))
    )
    (net (code "487") (name "Net-(LED11-A)") (class "Default")
      (node (ref "LED11") (pin "2") (pinfunction "A_2") (pintype "bidirectional"))
      (node (ref "R182") (pin "1") (pinfunction "1_1") (pintype "bidirectional"))
    )
    (net (code "488") (name "Net-(LED12-A)") (class "Default")
      (node (ref "LED12") (pin "2") (pinfunction "A_2") (pintype "bidirectional"))
      (node (ref "R183") (pin "1") (pinfunction "1_1") (pintype "bidirectional"))
    )
    (net (code "489") (name "Net-(LED13-A)") (class "Default")
      (node (ref "LED13") (pin "1") (pinfunction "A_1") (pintype "bidirectional"))
      (node (ref "R184") (pin "1") (pinfunction "1_1") (pintype "bidirectional"))
    )
    (net (code "490") (name "Net-(LED14-A)") (class "Default")
      (node (ref "LED14") (pin "2") (pinfunction "A_2") (pintype "bidirectional"))
      (node (ref "R193") (pin "1") (pinfunction "1_1") (pintype "bidirectional"))
    )
    (net (code "491") (name "Net-(LED15-A)") (class "Default")
      (node (ref "LED15") (pin "1") (pinfunction "A_1") (pintype "bidirectional"))
      (node (ref "R194") (pin "1") (pinfunction "1_1") (pintype "bidirectional"))
    )
    (net (code "492") (name "Net-(LED16-A)") (class "Default")
      (node (ref "LED16") (pin "2") (pinfunction "A_2") (pintype "bidirectional"))
      (node (ref "R206") (pin "1") (pinfunction "1_1") (pintype "bidirectional"))
    )
    (net (code "493") (name "Net-(LED17-A)") (class "Default")
      (node (ref "LED17") (pin "2") (pinfunction "A_2") (pintype "bidirectional"))
      (node (ref "R208") (pin "1") (pinfunction "1_1") (pintype "bidirectional"))
    )
    (net (code "494") (name "Net-(LED18-A)") (class "Default")
      (node (ref "LED18") (pin "1") (pinfunction "A_1") (pintype "bidirectional"))
      (node (ref "R210") (pin "1") (pinfunction "1_1") (pintype "bidirectional"))
    )
    (net (code "495") (name "Net-(LED19-A)") (class "Default")
      (node (ref "LED19") (pin "2") (pinfunction "A_2") (pintype "bidirectional"))
      (node (ref "R220") (pin "1") (pinfunction "1_1") (pintype "bidirectional"))
    )
    (net (code "496") (name "Net-(LED20-A)") (class "Default")
      (node (ref "LED20") (pin "1") (pinfunction "A_1") (pintype "bidirectional"))
      (node (ref "R222") (pin "1") (pinfunction "1_1") (pintype "bidirectional"))
    )
    (net (code "497") (name "Net-(LED21-A)") (class "Default")
      (node (ref "LED21") (pin "2") (pinfunction "A_2") (pintype "bidirectional"))
      (node (ref "R243") (pin "1") (pinfunction "1_1") (pintype "bidirectional"))
    )
    (net (code "498") (name "Net-(LED22-A)") (class "Default")
      (node (ref "LED22") (pin "2") (pinfunction "A_2") (pintype "bidirectional"))
      (node (ref "R244") (pin "1") (pinfunction "1_1") (pintype "bidirectional"))
    )
    (net (code "499") (name "Net-(LED23-A)") (class "Default")
      (node (ref "LED23") (pin "1") (pinfunction "A_1") (pintype "bidirectional"))
      (node (ref "R245") (pin "1") (pinfunction "1_1") (pintype "bidirectional"))
    )
    (net (code "500") (name "Net-(LED24-A)") (class "Default")
      (node (ref "LED24") (pin "2") (pinfunction "A_2") (pintype "bidirectional"))
      (node (ref "R254") (pin "1") (pinfunction "1_1") (pintype "bidirectional"))
    )
    (net (code "501") (name "Net-(LED25-A)") (class "Default")
      (node (ref "LED25") (pin "1") (pinfunction "A_1") (pintype "bidirectional"))
      (node (ref "R255") (pin "1") (pinfunction "1_1") (pintype "bidirectional"))
    )
    (net (code "502") (name "Net-(LED26-A)") (class "Default")
      (node (ref "LED26") (pin "2") (pinfunction "A_2") (pintype "bidirectional"))
      (node (ref "R264") (pin "1") (pinfunction "1_1") (pintype "bidirectional"))
    )
    (net (code "503") (name "Net-(LED27-A)") (class "Default")
      (node (ref "LED27") (pin "2") (pinfunction "A_2") (pintype "bidirectional"))
      (node (ref "R265") (pin "1") (pinfunction "1_1") (pintype "bidirectional"))
    )
    (net (code "504") (name "Net-(LED28-A)") (class "Default")
      (node (ref "LED28") (pin "1") (pinfunction "A_1") (pintype "bidirectional"))
      (node (ref "R266") (pin "1") (pinfunction "1_1") (pintype "bidirectional"))
    )
    (net (code "505") (name "Net-(LED29-A)") (class "Default")
      (node (ref "LED29") (pin "2") (pinfunction "A_2") (pintype "bidirectional"))
      (node (ref "R275") (pin "1") (pinfunction "1_1") (pintype "bidirectional"))
    )
    (net (code "506") (name "Net-(LED30-A)") (class "Default")
      (node (ref "LED30") (pin "1") (pinfunction "A_1") (pintype "bidirectional"))
      (node (ref "R276") (pin "1") (pinfunction "1_1") (pintype "bidirectional"))
    )
    (net (code "507") (name "Net-(LED31-A)") (class "Default")
      (node (ref "LED31") (pin "2") (pinfunction "A_2") (pintype "bidirectional"))
      (node (ref "R285") (pin "1") (pinfunction "1_1") (pintype "bidirectional"))
    )
    (net (code "508") (name "Net-(LED32-A)") (class "Default")
      (node (ref "LED32") (pin "2") (pinfunction "A_2") (pintype "bidirectional"))
      (node (ref "R286") (pin "1") (pinfunction "1_1") (pintype "bidirectional"))
    )
    (net (code "509") (name "Net-(LED33-A)") (class "Default")
      (node (ref "LED33") (pin "1") (pinfunction "A_1") (pintype "bidirectional"))
      (node (ref "R287") (pin "1") (pinfunction "1_1") (pintype "bidirectional"))
    )
    (net (code "510") (name "Net-(LED34-A)") (class "Default")
      (node (ref "LED34") (pin "2") (pinfunction "A_2") (pintype "bidirectional"))
      (node (ref "R296") (pin "1") (pinfunction "1_1") (pintype "bidirectional"))
    )
    (net (code "511") (name "Net-(LED35-A)") (class "Default")
      (node (ref "LED35") (pin "1") (pinfunction "A_1") (pintype "bidirectional"))
      (node (ref "R297") (pin "1") (pinfunction "1_1") (pintype "bidirectional"))
    )
    (net (code "512") (name "Net-(LED36-A)") (class "Default")
      (node (ref "LED36") (pin "2") (pinfunction "A_2") (pintype "bidirectional"))
      (node (ref "R306") (pin "1") (pinfunction "1_1") (pintype "bidirectional"))
    )
    (net (code "513") (name "Net-(LED37-A)") (class "Default")
      (node (ref "LED37") (pin "2") (pinfunction "A_2") (pintype "bidirectional"))
      (node (ref "R307") (pin "1") (pinfunction "1_1") (pintype "bidirectional"))
    )
    (net (code "514") (name "Net-(LED38-A)") (class "Default")
      (node (ref "LED38") (pin "1") (pinfunction "A_1") (pintype "bidirectional"))
      (node (ref "R308") (pin "1") (pinfunction "1_1") (pintype "bidirectional"))
    )
    (net (code "515") (name "Net-(LED39-A)") (class "Default")
      (node (ref "LED39") (pin "2") (pinfunction "A_2") (pintype "bidirectional"))
      (node (ref "R317") (pin "1") (pinfunction "1_1") (pintype "bidirectional"))
    )
    (net (code "516") (name "Net-(LED40-A)") (class "Default")
      (node (ref "LED40") (pin "1") (pinfunction "A_1") (pintype "bidirectional"))
      (node (ref "R318") (pin "1") (pinfunction "1_1") (pintype "bidirectional"))
    )
    (net (code "517") (name "Net-(LED41-A)") (class "Default")
      (node (ref "LED41") (pin "2") (pinfunction "A_2") (pintype "bidirectional"))
      (node (ref "R327") (pin "1") (pinfunction "1_1") (pintype "bidirectional"))
    )
    (net (code "518") (name "Net-(LED42-A)") (class "Default")
      (node (ref "LED42") (pin "2") (pinfunction "A_2") (pintype "bidirectional"))
      (node (ref "R328") (pin "1") (pinfunction "1_1") (pintype "bidirectional"))
    )
    (net (code "519") (name "Net-(LED43-A)") (class "Default")
      (node (ref "LED43") (pin "1") (pinfunction "A_1") (pintype "bidirectional"))
      (node (ref "R329") (pin "1") (pinfunction "1_1") (pintype "bidirectional"))
    )
    (net (code "520") (name "Net-(LED44-A)") (class "Default")
      (node (ref "LED44") (pin "2") (pinfunction "A_2") (pintype "bidirectional"))
      (node (ref "R338") (pin "1") (pinfunction "1_1") (pintype "bidirectional"))
    )
    (net (code "521") (name "Net-(LED45-A)") (class "Default")
      (node (ref "LED45") (pin "1") (pinfunction "A_1") (pintype "bidirectional"))
      (node (ref "R339") (pin "1") (pinfunction "1_1") (pintype "bidirectional"))
    )
    (net (code "522") (name "Net-(LED46-A)") (class "Default")
      (node (ref "LED46") (pin "2") (pinfunction "A_2") (pintype "bidirectional"))
      (node (ref "R348") (pin "1") (pinfunction "1_1") (pintype "bidirectional"))
    )
    (net (code "523") (name "Net-(LED47-A)") (class "Default")
      (node (ref "LED47") (pin "2") (pinfunction "A_2") (pintype "bidirectional"))
      (node (ref "R349") (pin "1") (pinfunction "1_1") (pintype "bidirectional"))
    )
    (net (code "524") (name "Net-(LED48-A)") (class "Default")
      (node (ref "LED48") (pin "1") (pinfunction "A_1") (pintype "bidirectional"))
      (node (ref "R350") (pin "1") (pinfunction "1_1") (pintype "bidirectional"))
    )
    (net (code "525") (name "Net-(LED49-A)") (class "Default")
      (node (ref "LED49") (pin "2") (pinfunction "A_2") (pintype "bidirectional"))
      (node (ref "R359") (pin "1") (pinfunction "1_1") (pintype "bidirectional"))
    )
    (net (code "526") (name "Net-(LED50-A)") (class "Default")
      (node (ref "LED50") (pin "1") (pinfunction "A_1") (pintype "bidirectional"))
      (node (ref "R360") (pin "1") (pinfunction "1_1") (pintype "bidirectional"))
    )
    (net (code "527") (name "Net-(LED51-A)") (class "Default")
      (node (ref "LED51") (pin "2") (pinfunction "A_2") (pintype "bidirectional"))
      (node (ref "R369") (pin "1") (pinfunction "1_1") (pintype "bidirectional"))
    )
    (net (code "528") (name "Net-(LED52-A)") (class "Default")
      (node (ref "LED52") (pin "2") (pinfunction "A_2") (pintype "bidirectional"))
      (node (ref "R370") (pin "1") (pinfunction "1_1") (pintype "bidirectional"))
    )
    (net (code "529") (name "Net-(LED53-A)") (class "Default")
      (node (ref "LED53") (pin "1") (pinfunction "A_1") (pintype "bidirectional"))
      (node (ref "R371") (pin "1") (pinfunction "1_1") (pintype "bidirectional"))
    )
    (net (code "530") (name "Net-(LED54-A)") (class "Default")
      (node (ref "LED54") (pin "2") (pinfunction "A_2") (pintype "bidirectional"))
      (node (ref "R380") (pin "1") (pinfunction "1_1") (pintype "bidirectional"))
    )
    (net (code "531") (name "Net-(LED55-A)") (class "Default")
      (node (ref "LED55") (pin "1") (pinfunction "A_1") (pintype "bidirectional"))
      (node (ref "R381") (pin "1") (pinfunction "1_1") (pintype "bidirectional"))
    )
    (net (code "532") (name "Net-(LED56-A)") (class "Default")
      (node (ref "LED56") (pin "2") (pinfunction "A_2") (pintype "bidirectional"))
      (node (ref "R390") (pin "1") (pinfunction "1_1") (pintype "bidirectional"))
    )
    (net (code "533") (name "Net-(LED57-A)") (class "Default")
      (node (ref "LED57") (pin "2") (pinfunction "A_2") (pintype "bidirectional"))
      (node (ref "R391") (pin "1") (pinfunction "1_1") (pintype "bidirectional"))
    )
    (net (code "534") (name "Net-(LED58-A)") (class "Default")
      (node (ref "LED58") (pin "1") (pinfunction "A_1") (pintype "bidirectional"))
      (node (ref "R392") (pin "1") (pinfunction "1_1") (pintype "bidirectional"))
    )
    (net (code "535") (name "Net-(LED59-A)") (class "Default")
      (node (ref "LED59") (pin "2") (pinfunction "A_2") (pintype "bidirectional"))
      (node (ref "R401") (pin "1") (pinfunction "1_1") (pintype "bidirectional"))
    )
    (net (code "536") (name "Net-(LED60-A)") (class "Default")
      (node (ref "LED60") (pin "1") (pinfunction "A_1") (pintype "bidirectional"))
      (node (ref "R402") (pin "1") (pinfunction "1_1") (pintype "bidirectional"))
    )
    (net (code "537") (name "Net-(LED61-A)") (class "Default")
      (node (ref "LED61") (pin "2") (pinfunction "A_2") (pintype "bidirectional"))
      (node (ref "R411") (pin "1") (pinfunction "1_1") (pintype "bidirectional"))
    )
    (net (code "538") (name "Net-(LED62-A)") (class "Default")
      (node (ref "LED62") (pin "2") (pinfunction "A_2") (pintype "bidirectional"))
      (node (ref "R412") (pin "1") (pinfunction "1_1") (pintype "bidirectional"))
    )
    (net (code "539") (name "Net-(LED63-A)") (class "Default")
      (node (ref "LED63") (pin "1") (pinfunction "A_1") (pintype "bidirectional"))
      (node (ref "R413") (pin "1") (pinfunction "1_1") (pintype "bidirectional"))
    )
    (net (code "540") (name "Net-(LED64-A)") (class "Default")
      (node (ref "LED64") (pin "2") (pinfunction "A_2") (pintype "bidirectional"))
      (node (ref "R422") (pin "1") (pinfunction "1_1") (pintype "bidirectional"))
    )
    (net (code "541") (name "Net-(LED65-A)") (class "Default")
      (node (ref "LED65") (pin "1") (pinfunction "A_1") (pintype "bidirectional"))
      (node (ref "R423") (pin "1") (pinfunction "1_1") (pintype "bidirectional"))
    )
    (net (code "542") (name "Net-(LED66-A)") (class "Default")
      (node (ref "LED66") (pin "2") (pinfunction "A_2") (pintype "bidirectional"))
      (node (ref "R432") (pin "1") (pinfunction "1_1") (pintype "bidirectional"))
    )
    (net (code "543") (name "Net-(LED67-A)") (class "Default")
      (node (ref "LED67") (pin "2") (pinfunction "A_2") (pintype "bidirectional"))
      (node (ref "R433") (pin "1") (pinfunction "1_1") (pintype "bidirectional"))
    )
    (net (code "544") (name "Net-(LED68-A)") (class "Default")
      (node (ref "LED68") (pin "1") (pinfunction "A_1") (pintype "bidirectional"))
      (node (ref "R434") (pin "1") (pinfunction "1_1") (pintype "bidirectional"))
    )
    (net (code "545") (name "Net-(LED69-A)") (class "Default")
      (node (ref "LED69") (pin "2") (pinfunction "A_2") (pintype "bidirectional"))
      (node (ref "R443") (pin "1") (pinfunction "1_1") (pintype "bidirectional"))
    )
    (net (code "546") (name "Net-(LED70-A)") (class "Default")
      (node (ref "LED70") (pin "1") (pinfunction "A_1") (pintype "bidirectional"))
      (node (ref "R444") (pin "1") (pinfunction "1_1") (pintype "bidirectional"))
    )
    (net (code "547") (name "Net-(LED71-A)") (class "Default")
      (node (ref "LED71") (pin "2") (pinfunction "A_2") (pintype "bidirectional"))
      (node (ref "R445") (pin "2") (pinfunction "2_2") (pintype "bidirectional"))
    )
    (net (code "548") (name "Net-(LED72-A)") (class "Default")
      (node (ref "LED72") (pin "2") (pinfunction "A_2") (pintype "bidirectional"))
      (node (ref "R446") (pin "2") (pinfunction "2_2") (pintype "bidirectional"))
    )
    (net (code "549") (name "Net-(LED73-A)") (class "Default")
      (node (ref "LED73") (pin "2") (pinfunction "A_2") (pintype "bidirectional"))
      (node (ref "R447") (pin "2") (pinfunction "2_2") (pintype "bidirectional"))
    )
    (net (code "550") (name "Net-(LED74-A)") (class "Default")
      (node (ref "LED74") (pin "2") (pinfunction "A_2") (pintype "bidirectional"))
      (node (ref "R448") (pin "2") (pinfunction "2_2") (pintype "bidirectional"))
    )
    (net (code "551") (name "Net-(LED75-A)") (class "Default")
      (node (ref "LED75") (pin "2") (pinfunction "A_2") (pintype "bidirectional"))
      (node (ref "R449") (pin "2") (pinfunction "2_2") (pintype "bidirectional"))
    )
    (net (code "552") (name "Net-(LED76-A)") (class "Default")
      (node (ref "LED76") (pin "2") (pinfunction "A_2") (pintype "bidirectional"))
      (node (ref "R450") (pin "2") (pinfunction "2_2") (pintype "bidirectional"))
    )
    (net (code "553") (name "Net-(LED77-A)") (class "Default")
      (node (ref "LED77") (pin "2") (pinfunction "A_2") (pintype "bidirectional"))
      (node (ref "R451") (pin "2") (pinfunction "2_2") (pintype "bidirectional"))
    )
    (net (code "554") (name "Net-(LED78-A)") (class "Default")
      (node (ref "LED78") (pin "2") (pinfunction "A_2") (pintype "bidirectional"))
      (node (ref "R452") (pin "2") (pinfunction "2_2") (pintype "bidirectional"))
    )
    (net (code "555") (name "Net-(LED79-A)") (class "Default")
      (node (ref "LED79") (pin "2") (pinfunction "A_2") (pintype "bidirectional"))
      (node (ref "R453") (pin "2") (pinfunction "2_2") (pintype "bidirectional"))
    )
    (net (code "556") (name "Net-(LED80-A)") (class "Default")
      (node (ref "LED80") (pin "2") (pinfunction "A_2") (pintype "bidirectional"))
      (node (ref "R454") (pin "2") (pinfunction "2_2") (pintype "bidirectional"))
    )
    (net (code "557") (name "Net-(LED81-A)") (class "Default")
      (node (ref "LED81") (pin "2") (pinfunction "A_2") (pintype "bidirectional"))
      (node (ref "R455") (pin "2") (pinfunction "2_2") (pintype "bidirectional"))
    )
    (net (code "558") (name "Net-(LED82-A)") (class "Default")
      (node (ref "LED82") (pin "2") (pinfunction "A_2") (pintype "bidirectional"))
      (node (ref "R456") (pin "2") (pinfunction "2_2") (pintype "bidirectional"))
    )
    (net (code "559") (name "Net-(LED83-A)") (class "Default")
      (node (ref "LED83") (pin "2") (pinfunction "A_2") (pintype "bidirectional"))
      (node (ref "R457") (pin "2") (pinfunction "2_2") (pintype "bidirectional"))
    )
    (net (code "560") (name "Net-(LED84-A)") (class "Default")
      (node (ref "LED84") (pin "2") (pinfunction "A_2") (pintype "bidirectional"))
      (node (ref "R458") (pin "2") (pinfunction "2_2") (pintype "bidirectional"))
    )
    (net (code "561") (name "Net-(LED85-K)") (class "Default")
      (node (ref "LED85") (pin "1") (pinfunction "K_1") (pintype "bidirectional"))
      (node (ref "R459") (pin "2") (pinfunction "2_2") (pintype "bidirectional"))
    )
    (net (code "562") (name "Net-(LED86-K)") (class "Default")
      (node (ref "LED86") (pin "1") (pinfunction "K_1") (pintype "bidirectional"))
      (node (ref "R460") (pin "2") (pinfunction "2_2") (pintype "bidirectional"))
    )
    (net (code "563") (name "Net-(LED87-K)") (class "Default")
      (node (ref "LED87") (pin "1") (pinfunction "K_1") (pintype "bidirectional"))
      (node (ref "R461") (pin "2") (pinfunction "2_2") (pintype "bidirectional"))
    )
    (net (code "564") (name "Net-(LED88-K)") (class "Default")
      (node (ref "LED88") (pin "1") (pinfunction "K_1") (pintype "bidirectional"))
      (node (ref "R462") (pin "2") (pinfunction "2_2") (pintype "bidirectional"))
    )
    (net (code "565") (name "Net-(LED89-K)") (class "Default")
      (node (ref "LED89") (pin "1") (pinfunction "K_1") (pintype "bidirectional"))
      (node (ref "R463") (pin "2") (pinfunction "2_2") (pintype "bidirectional"))
    )
    (net (code "566") (name "Net-(LED90-K)") (class "Default")
      (node (ref "LED90") (pin "1") (pinfunction "K_1") (pintype "bidirectional"))
      (node (ref "R464") (pin "2") (pinfunction "2_2") (pintype "bidirectional"))
    )
    (net (code "567") (name "Net-(LED91-K)") (class "Default")
      (node (ref "LED91") (pin "1") (pinfunction "K_1") (pintype "bidirectional"))
      (node (ref "R465") (pin "2") (pinfunction "2_2") (pintype "bidirectional"))
    )
    (net (code "568") (name "Net-(LED92-K)") (class "Default")
      (node (ref "LED92") (pin "1") (pinfunction "K_1") (pintype "bidirectional"))
      (node (ref "R466") (pin "2") (pinfunction "2_2") (pintype "bidirectional"))
    )
    (net (code "569") (name "Net-(LED93-K)") (class "Default")
      (node (ref "LED93") (pin "1") (pinfunction "K_1") (pintype "bidirectional"))
      (node (ref "R467") (pin "2") (pinfunction "2_2") (pintype "bidirectional"))
    )
    (net (code "570") (name "Net-(LED94-K)") (class "Default")
      (node (ref "LED94") (pin "1") (pinfunction "K_1") (pintype "bidirectional"))
      (node (ref "R468") (pin "2") (pinfunction "2_2") (pintype "bidirectional"))
    )
    (net (code "571") (name "Net-(LED95-K)") (class "Default")
      (node (ref "LED95") (pin "1") (pinfunction "K_1") (pintype "bidirectional"))
      (node (ref "R469") (pin "2") (pinfunction "2_2") (pintype "bidirectional"))
    )
    (net (code "572") (name "Net-(LED96-K)") (class "Default")
      (node (ref "LED96") (pin "1") (pinfunction "K_1") (pintype "bidirectional"))
      (node (ref "R470") (pin "2") (pinfunction "2_2") (pintype "bidirectional"))
    )
    (net (code "573") (name "Net-(M1-G)") (class "Default")
      (node (ref "M1") (pin "3") (pinfunction "G_3") (pintype "bidirectional"))
      (node (ref "R93") (pin "1") (pinfunction "1_1") (pintype "bidirectional"))
    )
    (net (code "574") (name "Net-(M2-G)") (class "Default")
      (node (ref "M2") (pin "3") (pinfunction "G_3") (pintype "bidirectional"))
      (node (ref "R130") (pin "1") (pinfunction "1_1") (pintype "bidirectional"))
    )
    (net (code "575") (name "Net-(M3-G)") (class "Default")
      (node (ref "M3") (pin "3") (pinfunction "G_3") (pintype "bidirectional"))
      (node (ref "R140") (pin "1") (pinfunction "1_1") (pintype "bidirectional"))
    )
    (net (code "576") (name "Net-(M4-G)") (class "Default")
      (node (ref "M4") (pin "3") (pinfunction "G_3") (pintype "bidirectional"))
      (node (ref "R168") (pin "1") (pinfunction "1_1") (pintype "bidirectional"))
    )
    (net (code "577") (name "Net-(M5-G)") (class "Default")
      (node (ref "M5") (pin "3") (pinfunction "G_3") (pintype "bidirectional"))
      (node (ref "R178") (pin "1") (pinfunction "1_1") (pintype "bidirectional"))
    )
    (net (code "578") (name "Net-(M6-G)") (class "Default")
      (node (ref "M6") (pin "3") (pinfunction "G_3") (pintype "bidirectional"))
      (node (ref "R189") (pin "1") (pinfunction "1_1") (pintype "bidirectional"))
    )
    (net (code "579") (name "Net-(M7-G)") (class "Default")
      (node (ref "M7") (pin "3") (pinfunction "G_3") (pintype "bidirectional"))
      (node (ref "R199") (pin "1") (pinfunction "1_1") (pintype "bidirectional"))
    )
    (net (code "580") (name "Net-(M8-G)") (class "Default")
      (node (ref "M8") (pin "3") (pinfunction "G_3") (pintype "bidirectional"))
      (node (ref "R216") (pin "1") (pinfunction "1_1") (pintype "bidirectional"))
    )
    (net (code "581") (name "Net-(M9-G)") (class "Default")
      (node (ref "M9") (pin "3") (pinfunction "G_3") (pintype "bidirectional"))
      (node (ref "R228") (pin "1") (pinfunction "1_1") (pintype "bidirectional"))
    )
    (net (code "582") (name "Net-(M10-G)") (class "Default")
      (node (ref "M10") (pin "3") (pinfunction "G_3") (pintype "bidirectional"))
      (node (ref "R250") (pin "1") (pinfunction "1_1") (pintype "bidirectional"))
    )
    (net (code "583") (name "Net-(M11-G)") (class "Default")
      (node (ref "M11") (pin "3") (pinfunction "G_3") (pintype "bidirectional"))
      (node (ref "R260") (pin "1") (pinfunction "1_1") (pintype "bidirectional"))
    )
    (net (code "584") (name "Net-(M12-G)") (class "Default")
      (node (ref "M12") (pin "3") (pinfunction "G_3") (pintype "bidirectional"))
      (node (ref "R271") (pin "1") (pinfunction "1_1") (pintype "bidirectional"))
    )
    (net (code "585") (name "Net-(M13-G)") (class "Default")
      (node (ref "M13") (pin "3") (pinfunction "G_3") (pintype "bidirectional"))
      (node (ref "R281") (pin "1") (pinfunction "1_1") (pintype "bidirectional"))
    )
    (net (code "586") (name "Net-(M14-G)") (class "Default")
      (node (ref "M14") (pin "3") (pinfunction "G_3") (pintype "bidirectional"))
      (node (ref "R292") (pin "1") (pinfunction "1_1") (pintype "bidirectional"))
    )
    (net (code "587") (name "Net-(M15-G)") (class "Default")
      (node (ref "M15") (pin "3") (pinfunction "G_3") (pintype "bidirectional"))
      (node (ref "R302") (pin "1") (pinfunction "1_1") (pintype "bidirectional"))
    )
    (net (code "588") (name "Net-(M16-G)") (class "Default")
      (node (ref "M16") (pin "3") (pinfunction "G_3") (pintype "bidirectional"))
      (node (ref "R313") (pin "1") (pinfunction "1_1") (pintype "bidirectional"))
    )
    (net (code "589") (name "Net-(M17-G)") (class "Default")
      (node (ref "M17") (pin "3") (pinfunction "G_3") (pintype "bidirectional"))
      (node (ref "R323") (pin "1") (pinfunction "1_1") (pintype "bidirectional"))
    )
    (net (code "590") (name "Net-(M18-G)") (class "Default")
      (node (ref "M18") (pin "3") (pinfunction "G_3") (pintype "bidirectional"))
      (node (ref "R334") (pin "1") (pinfunction "1_1") (pintype "bidirectional"))
    )
    (net (code "591") (name "Net-(M19-G)") (class "Default")
      (node (ref "M19") (pin "3") (pinfunction "G_3") (pintype "bidirectional"))
      (node (ref "R344") (pin "1") (pinfunction "1_1") (pintype "bidirectional"))
    )
    (net (code "592") (name "Net-(M20-G)") (class "Default")
      (node (ref "M20") (pin "3") (pinfunction "G_3") (pintype "bidirectional"))
      (node (ref "R355") (pin "1") (pinfunction "1_1") (pintype "bidirectional"))
    )
    (net (code "593") (name "Net-(M21-G)") (class "Default")
      (node (ref "M21") (pin "3") (pinfunction "G_3") (pintype "bidirectional"))
      (node (ref "R365") (pin "1") (pinfunction "1_1") (pintype "bidirectional"))
    )
    (net (code "594") (name "Net-(M22-G)") (class "Default")
      (node (ref "M22") (pin "3") (pinfunction "G_3") (pintype "bidirectional"))
      (node (ref "R376") (pin "1") (pinfunction "1_1") (pintype "bidirectional"))
    )
    (net (code "595") (name "Net-(M23-G)") (class "Default")
      (node (ref "M23") (pin "3") (pinfunction "G_3") (pintype "bidirectional"))
      (node (ref "R386") (pin "1") (pinfunction "1_1") (pintype "bidirectional"))
    )
    (net (code "596") (name "Net-(M24-G)") (class "Default")
      (node (ref "M24") (pin "3") (pinfunction "G_3") (pintype "bidirectional"))
      (node (ref "R397") (pin "1") (pinfunction "1_1") (pintype "bidirectional"))
    )
    (net (code "597") (name "Net-(M25-G)") (class "Default")
      (node (ref "M25") (pin "3") (pinfunction "G_3") (pintype "bidirectional"))
      (node (ref "R407") (pin "1") (pinfunction "1_1") (pintype "bidirectional"))
    )
    (net (code "598") (name "Net-(M26-G)") (class "Default")
      (node (ref "M26") (pin "3") (pinfunction "G_3") (pintype "bidirectional"))
      (node (ref "R418") (pin "1") (pinfunction "1_1") (pintype "bidirectional"))
    )
    (net (code "599") (name "Net-(M27-G)") (class "Default")
      (node (ref "M27") (pin "3") (pinfunction "G_3") (pintype "bidirectional"))
      (node (ref "R428") (pin "1") (pinfunction "1_1") (pintype "bidirectional"))
    )
    (net (code "600") (name "Net-(M28-G)") (class "Default")
      (node (ref "M28") (pin "3") (pinfunction "G_3") (pintype "bidirectional"))
      (node (ref "R439") (pin "1") (pinfunction "1_1") (pintype "bidirectional"))
    )
    (net (code "601") (name "Net-(T1-PRIMARY_2)") (class "Default")
      (node (ref "C171") (pin "1") (pinfunction "1_1") (pintype "bidirectional"))
      (node (ref "T1") (pin "2") (pinfunction "PRIMARY_2_2") (pintype "bidirectional"))
    )
    (net (code "602") (name "Net-(T1-SECONDARY_2)") (class "Default")
      (node (ref "C172") (pin "1") (pinfunction "1_1") (pintype "bidirectional"))
      (node (ref "T1") (pin "5") (pinfunction "SECONDARY_2_5") (pintype "bidirectional"))
    )
    (net (code "603") (name "OS0_ADC") (class "Default")
      (node (ref "IC38") (pin "3") (pinfunction "OS0_3") (pintype "input"))
      (node (ref "IC51") (pin "3") (pinfunction "OS0_3") (pintype "input"))
      (node (ref "IC52") (pin "3") (pinfunction "OS0_3") (pintype "input"))
      (node (ref "J4") (pin "41") (pinfunction "41_41") (pintype "passive"))
      (node (ref "OS0_ADC") (pin "TP") (pinfunction "TP_TP") (pintype "bidirectional"))
    )
    (net (code "604") (name "OS1_ADC") (class "Default")
      (node (ref "IC38") (pin "4") (pinfunction "OS1_4") (pintype "input"))
      (node (ref "IC51") (pin "4") (pinfunction "OS1_4") (pintype "input"))
      (node (ref "IC52") (pin "4") (pinfunction "OS1_4") (pintype "input"))
      (node (ref "J4") (pin "43") (pinfunction "43_43") (pintype "passive"))
      (node (ref "OS1_ADC") (pin "TP") (pinfunction "TP_TP") (pintype "bidirectional"))
    )
    (net (code "605") (name "OS2_ADC") (class "Default")
      (node (ref "IC38") (pin "5") (pinfunction "OS2_5") (pintype "input"))
      (node (ref "IC51") (pin "5") (pinfunction "OS2_5") (pintype "input"))
      (node (ref "IC52") (pin "5") (pinfunction "OS2_5") (pintype "input"))
      (node (ref "J4") (pin "45") (pinfunction "45_45") (pintype "passive"))
      (node (ref "OS2_ADC") (pin "TP") (pinfunction "TP_TP") (pintype "bidirectional"))
    )
    (net (code "606") (name "OV1_") (class "Default")
      (node (ref "IC4") (pin "32") (pinfunction "OV1_32") (pintype "bidirectional"))
      (node (ref "R90") (pin "2") (pinfunction "2_2") (pintype "bidirectional"))
      (node (ref "R91") (pin "1") (pinfunction "1_1") (pintype "bidirectional"))
    )
    (net (code "607") (name "OV1_0") (class "Default")
      (node (ref "IC11") (pin "32") (pinfunction "OV1_32") (pintype "bidirectional"))
      (node (ref "R137") (pin "2") (pinfunction "2_2") (pintype "bidirectional"))
      (node (ref "R138") (pin "1") (pinfunction "1_1") (pintype "bidirectional"))
    )
    (net (code "608") (name "OV1_1") (class "Default")
      (node (ref "IC20") (pin "32") (pinfunction "OV1_32") (pintype "bidirectional"))
      (node (ref "R362") (pin "2") (pinfunction "2_2") (pintype "bidirectional"))
      (node (ref "R363") (pin "1") (pinfunction "1_1") (pintype "bidirectional"))
    )
    (net (code "609") (name "OV1_2") (class "Default")
      (node (ref "IC21") (pin "32") (pinfunction "OV1_32") (pintype "bidirectional"))
      (node (ref "R383") (pin "2") (pinfunction "2_2") (pintype "bidirectional"))
      (node (ref "R384") (pin "1") (pinfunction "1_1") (pintype "bidirectional"))
    )
    (net (code "610") (name "OV1_3") (class "Default")
      (node (ref "IC12") (pin "32") (pinfunction "OV1_32") (pintype "bidirectional"))
      (node (ref "R175") (pin "2") (pinfunction "2_2") (pintype "bidirectional"))
      (node (ref "R176") (pin "1") (pinfunction "1_1") (pintype "bidirectional"))
    )
    (net (code "611") (name "OV1_4") (class "Default")
      (node (ref "IC13") (pin "32") (pinfunction "OV1_32") (pintype "bidirectional"))
      (node (ref "R196") (pin "2") (pinfunction "2_2") (pintype "bidirectional"))
      (node (ref "R197") (pin "1") (pinfunction "1_1") (pintype "bidirectional"))
    )
    (net (code "612") (name "OV1_5") (class "Default")
      (node (ref "IC18") (pin "32") (pinfunction "OV1_32") (pintype "bidirectional"))
      (node (ref "R320") (pin "2") (pinfunction "2_2") (pintype "bidirectional"))
      (node (ref "R321") (pin "1") (pinfunction "1_1") (pintype "bidirectional"))
    )
    (net (code "613") (name "OV1_6") (class "Default")
      (node (ref "IC19") (pin "32") (pinfunction "OV1_32") (pintype "bidirectional"))
      (node (ref "R341") (pin "2") (pinfunction "2_2") (pintype "bidirectional"))
      (node (ref "R342") (pin "1") (pinfunction "1_1") (pintype "bidirectional"))
    )
    (net (code "614") (name "OV1_7") (class "Default")
      (node (ref "IC14") (pin "32") (pinfunction "OV1_32") (pintype "bidirectional"))
      (node (ref "R224") (pin "2") (pinfunction "2_2") (pintype "bidirectional"))
      (node (ref "R225") (pin "1") (pinfunction "1_1") (pintype "bidirectional"))
    )
    (net (code "615") (name "OV1_8") (class "Default")
      (node (ref "IC15") (pin "32") (pinfunction "OV1_32") (pintype "bidirectional"))
      (node (ref "R257") (pin "2") (pinfunction "2_2") (pintype "bidirectional"))
      (node (ref "R258") (pin "1") (pinfunction "1_1") (pintype "bidirectional"))
    )
    (net (code "616") (name "OV1_9") (class "Default")
      (node (ref "IC16") (pin "32") (pinfunction "OV1_32") (pintype "bidirectional"))
      (node (ref "R278") (pin "2") (pinfunction "2_2") (pintype "bidirectional"))
      (node (ref "R279") (pin "1") (pinfunction "1_1") (pintype "bidirectional"))
    )
    (net (code "617") (name "OV1_10") (class "Default")
      (node (ref "IC17") (pin "32") (pinfunction "OV1_32") (pintype "bidirectional"))
      (node (ref "R299") (pin "2") (pinfunction "2_2") (pintype "bidirectional"))
      (node (ref "R300") (pin "1") (pinfunction "1_1") (pintype "bidirectional"))
    )
    (net (code "618") (name "OV1_11") (class "Default")
      (node (ref "IC22") (pin "32") (pinfunction "OV1_32") (pintype "bidirectional"))
      (node (ref "R404") (pin "2") (pinfunction "2_2") (pintype "bidirectional"))
      (node (ref "R405") (pin "1") (pinfunction "1_1") (pintype "bidirectional"))
    )
    (net (code "619") (name "OV1_12") (class "Default")
      (node (ref "IC23") (pin "32") (pinfunction "OV1_32") (pintype "bidirectional"))
      (node (ref "R425") (pin "2") (pinfunction "2_2") (pintype "bidirectional"))
      (node (ref "R426") (pin "1") (pinfunction "1_1") (pintype "bidirectional"))
    )
    (net (code "620") (name "OV2_") (class "Default")
      (node (ref "IC4") (pin "9") (pinfunction "OV2_9") (pintype "bidirectional"))
      (node (ref "R127") (pin "2") (pinfunction "2_2") (pintype "bidirectional"))
      (node (ref "R128") (pin "1") (pinfunction "1_1") (pintype "bidirectional"))
    )
    (net (code "621") (name "OV2_0") (class "Default")
      (node (ref "IC11") (pin "9") (pinfunction "OV2_9") (pintype "bidirectional"))
      (node (ref "R165") (pin "2") (pinfunction "2_2") (pintype "bidirectional"))
      (node (ref "R166") (pin "1") (pinfunction "1_1") (pintype "bidirectional"))
    )
    (net (code "622") (name "OV2_1") (class "Default")
      (node (ref "IC20") (pin "9") (pinfunction "OV2_9") (pintype "bidirectional"))
      (node (ref "R373") (pin "2") (pinfunction "2_2") (pintype "bidirectional"))
      (node (ref "R374") (pin "1") (pinfunction "1_1") (pintype "bidirectional"))
    )
    (net (code "623") (name "OV2_2") (class "Default")
      (node (ref "IC21") (pin "9") (pinfunction "OV2_9") (pintype "bidirectional"))
      (node (ref "R394") (pin "2") (pinfunction "2_2") (pintype "bidirectional"))
      (node (ref "R395") (pin "1") (pinfunction "1_1") (pintype "bidirectional"))
    )
    (net (code "624") (name "OV2_3") (class "Default")
      (node (ref "IC12") (pin "9") (pinfunction "OV2_9") (pintype "bidirectional"))
      (node (ref "R186") (pin "2") (pinfunction "2_2") (pintype "bidirectional"))
      (node (ref "R187") (pin "1") (pinfunction "1_1") (pintype "bidirectional"))
    )
    (net (code "625") (name "OV2_4") (class "Default")
      (node (ref "IC13") (pin "9") (pinfunction "OV2_9") (pintype "bidirectional"))
      (node (ref "R213") (pin "2") (pinfunction "2_2") (pintype "bidirectional"))
      (node (ref "R214") (pin "1") (pinfunction "1_1") (pintype "bidirectional"))
    )
    (net (code "626") (name "OV2_5") (class "Default")
      (node (ref "IC18") (pin "9") (pinfunction "OV2_9") (pintype "bidirectional"))
      (node (ref "R331") (pin "2") (pinfunction "2_2") (pintype "bidirectional"))
      (node (ref "R332") (pin "1") (pinfunction "1_1") (pintype "bidirectional"))
    )
    (net (code "627") (name "OV2_6") (class "Default")
      (node (ref "IC19") (pin "9") (pinfunction "OV2_9") (pintype "bidirectional"))
      (node (ref "R352") (pin "2") (pinfunction "2_2") (pintype "bidirectional"))
      (node (ref "R353") (pin "1") (pinfunction "1_1") (pintype "bidirectional"))
    )
    (net (code "628") (name "OV2_7") (class "Default")
      (node (ref "IC14") (pin "9") (pinfunction "OV2_9") (pintype "bidirectional"))
      (node (ref "R247") (pin "2") (pinfunction "2_2") (pintype "bidirectional"))
      (node (ref "R248") (pin "1") (pinfunction "1_1") (pintype "bidirectional"))
    )
    (net (code "629") (name "OV2_8") (class "Default")
      (node (ref "IC15") (pin "9") (pinfunction "OV2_9") (pintype "bidirectional"))
      (node (ref "R268") (pin "2") (pinfunction "2_2") (pintype "bidirectional"))
      (node (ref "R269") (pin "1") (pinfunction "1_1") (pintype "bidirectional"))
    )
    (net (code "630") (name "OV2_9") (class "Default")
      (node (ref "IC16") (pin "9") (pinfunction "OV2_9") (pintype "bidirectional"))
      (node (ref "R289") (pin "2") (pinfunction "2_2") (pintype "bidirectional"))
      (node (ref "R290") (pin "1") (pinfunction "1_1") (pintype "bidirectional"))
    )
    (net (code "631") (name "OV2_10") (class "Default")
      (node (ref "IC17") (pin "9") (pinfunction "OV2_9") (pintype "bidirectional"))
      (node (ref "R310") (pin "2") (pinfunction "2_2") (pintype "bidirectional"))
      (node (ref "R311") (pin "1") (pinfunction "1_1") (pintype "bidirectional"))
    )
    (net (code "632") (name "OV2_11") (class "Default")
      (node (ref "IC22") (pin "9") (pinfunction "OV2_9") (pintype "bidirectional"))
      (node (ref "R415") (pin "2") (pinfunction "2_2") (pintype "bidirectional"))
      (node (ref "R416") (pin "1") (pinfunction "1_1") (pintype "bidirectional"))
    )
    (net (code "633") (name "OV2_12") (class "Default")
      (node (ref "IC23") (pin "9") (pinfunction "OV2_9") (pintype "bidirectional"))
      (node (ref "R436") (pin "2") (pinfunction "2_2") (pintype "bidirectional"))
      (node (ref "R437") (pin "1") (pinfunction "1_1") (pintype "bidirectional"))
    )
    (net (code "634") (name "PA0") (class "Default")
      (node (ref "J14") (pin "01") (pinfunction "01_01") (pintype "passive"))
      (node (ref "PA0") (pin "TP") (pinfunction "TP_TP") (pintype "bidirectional"))
      (node (ref "UC1") (pin "PA0") (pinfunction "PA0_PA0") (pintype "passive"))
    )
    (net (code "635") (name "PA3") (class "Default")
      (node (ref "J14") (pin "03") (pinfunction "03_03") (pintype "passive"))
      (node (ref "PA3") (pin "TP") (pinfunction "TP_TP") (pintype "bidirectional"))
      (node (ref "UC1") (pin "PA3") (pinfunction "PA3_PA3") (pintype "passive"))
    )
    (net (code "636") (name "PA4") (class "Default")
      (node (ref "J14") (pin "05") (pinfunction "05_05") (pintype "passive"))
      (node (ref "PA4") (pin "TP") (pinfunction "TP_TP") (pintype "bidirectional"))
      (node (ref "UC1") (pin "PA4") (pinfunction "PA4_PA4") (pintype "passive"))
    )
    (net (code "637") (name "PA5") (class "Default")
      (node (ref "J14") (pin "07") (pinfunction "07_07") (pintype "passive"))
      (node (ref "PA5") (pin "TP") (pinfunction "TP_TP") (pintype "bidirectional"))
      (node (ref "UC1") (pin "PA5") (pinfunction "PA5_PA5") (pintype "passive"))
    )
    (net (code "638") (name "PA6") (class "Default")
      (node (ref "J14") (pin "09") (pinfunction "09_09") (pintype "passive"))
      (node (ref "PA6") (pin "TP") (pinfunction "TP_TP") (pintype "bidirectional"))
      (node (ref "UC1") (pin "PA6") (pinfunction "PA6_PA6") (pintype "passive"))
    )
    (net (code "639") (name "PA8") (class "Default")
      (node (ref "J14") (pin "11") (pinfunction "11_11") (pintype "passive"))
      (node (ref "PA8") (pin "TP") (pinfunction "TP_TP") (pintype "bidirectional"))
      (node (ref "UC1") (pin "PA8") (pinfunction "PA8_PA8") (pintype "passive"))
    )
    (net (code "640") (name "PA9") (class "Default")
      (node (ref "J14") (pin "13") (pinfunction "13_13") (pintype "passive"))
      (node (ref "PA9") (pin "TP") (pinfunction "TP_TP") (pintype "bidirectional"))
      (node (ref "UC1") (pin "PA9") (pinfunction "PA9_PA9") (pintype "passive"))
    )
    (net (code "641") (name "PA10") (class "Default")
      (node (ref "J14") (pin "15") (pinfunction "15_15") (pintype "passive"))
      (node (ref "PA10") (pin "TP") (pinfunction "TP_TP") (pintype "bidirectional"))
      (node (ref "UC1") (pin "PA10") (pinfunction "PA10_PA10") (pintype "passive"))
    )
    (net (code "642") (name "PA11") (class "Default")
      (node (ref "J14") (pin "17") (pinfunction "17_17") (pintype "passive"))
      (node (ref "PA11") (pin "TP") (pinfunction "TP_TP") (pintype "bidirectional"))
      (node (ref "UC1") (pin "PA11") (pinfunction "PA11_PA11") (pintype "passive"))
    )
    (net (code "643") (name "PA12") (class "Default")
      (node (ref "J14") (pin "19") (pinfunction "19_19") (pintype "passive"))
      (node (ref "PA12") (pin "TP") (pinfunction "TP_TP") (pintype "bidirectional"))
      (node (ref "UC1") (pin "PA12") (pinfunction "PA12_PA12") (pintype "passive"))
    )
    (net (code "644") (name "PA13") (class "Default")
      (node (ref "J14") (pin "21") (pinfunction "21_21") (pintype "passive"))
      (node (ref "PA13") (pin "TP") (pinfunction "TP_TP") (pintype "bidirectional"))
      (node (ref "UC1") (pin "PA13") (pinfunction "PA13_PA13") (pintype "passive"))
    )
    (net (code "645") (name "PA14") (class "Default")
      (node (ref "J14") (pin "23") (pinfunction "23_23") (pintype "passive"))
      (node (ref "PA14") (pin "TP") (pinfunction "TP_TP") (pintype "bidirectional"))
      (node (ref "UC1") (pin "PA14") (pinfunction "PA14_PA14") (pintype "passive"))
    )
    (net (code "646") (name "PA15") (class "Default")
      (node (ref "J14") (pin "25") (pinfunction "25_25") (pintype "passive"))
      (node (ref "PA15") (pin "TP") (pinfunction "TP_TP") (pintype "bidirectional"))
      (node (ref "UC1") (pin "PA15") (pinfunction "PA15_PA15") (pintype "passive"))
    )
    (net (code "647") (name "PB0") (class "Default")
      (node (ref "J14") (pin "27") (pinfunction "27_27") (pintype "passive"))
      (node (ref "PB0") (pin "TP") (pinfunction "TP_TP") (pintype "bidirectional"))
      (node (ref "UC1") (pin "PB0") (pinfunction "PB0_PB0") (pintype "passive"))
    )
    (net (code "648") (name "PB1") (class "Default")
      (node (ref "J14") (pin "29") (pinfunction "29_29") (pintype "passive"))
      (node (ref "PB1") (pin "TP") (pinfunction "TP_TP") (pintype "bidirectional"))
      (node (ref "UC1") (pin "PB1") (pinfunction "PB1_PB1") (pintype "passive"))
    )
    (net (code "649") (name "PB2") (class "Default")
      (node (ref "J14") (pin "31") (pinfunction "31_31") (pintype "passive"))
      (node (ref "PB2") (pin "TP") (pinfunction "TP_TP") (pintype "bidirectional"))
      (node (ref "UC1") (pin "PB2") (pinfunction "PB2_PB2") (pintype "passive"))
    )
    (net (code "650") (name "PB3") (class "Default")
      (node (ref "J14") (pin "33") (pinfunction "33_33") (pintype "passive"))
      (node (ref "PB3") (pin "TP") (pinfunction "TP_TP") (pintype "bidirectional"))
      (node (ref "UC1") (pin "PB3") (pinfunction "PB3_PB3") (pintype "passive"))
    )
    (net (code "651") (name "PB4") (class "Default")
      (node (ref "J14") (pin "35") (pinfunction "35_35") (pintype "passive"))
      (node (ref "PB4") (pin "TP") (pinfunction "TP_TP") (pintype "bidirectional"))
      (node (ref "UC1") (pin "PB4") (pinfunction "PB4_PB4") (pintype "passive"))
    )
    (net (code "652") (name "PB5") (class "Default")
      (node (ref "J14") (pin "37") (pinfunction "37_37") (pintype "passive"))
      (node (ref "PB5") (pin "TP") (pinfunction "TP_TP") (pintype "bidirectional"))
      (node (ref "UC1") (pin "PB5") (pinfunction "PB5_PB5") (pintype "passive"))
    )
    (net (code "653") (name "PB6") (class "Default")
      (node (ref "J14") (pin "39") (pinfunction "39_39") (pintype "passive"))
      (node (ref "PB6") (pin "TP") (pinfunction "TP_TP") (pintype "bidirectional"))
      (node (ref "UC1") (pin "PB6") (pinfunction "PB6_PB6") (pintype "passive"))
    )
    (net (code "654") (name "PB7") (class "Default")
      (node (ref "J14") (pin "79") (pinfunction "79_79") (pintype "passive"))
      (node (ref "PB7") (pin "TP") (pinfunction "TP_TP") (pintype "bidirectional"))
      (node (ref "UC1") (pin "PB7") (pinfunction "PB7_PB7") (pintype "passive"))
    )
    (net (code "655") (name "PB8") (class "Default")
      (node (ref "J14") (pin "77") (pinfunction "77_77") (pintype "passive"))
      (node (ref "PB8") (pin "TP") (pinfunction "TP_TP") (pintype "bidirectional"))
      (node (ref "UC1") (pin "PB8") (pinfunction "PB8_PB8") (pintype "passive"))
    )
    (net (code "656") (name "PB9") (class "Default")
      (node (ref "J14") (pin "75") (pinfunction "75_75") (pintype "passive"))
      (node (ref "PB9") (pin "TP") (pinfunction "TP_TP") (pintype "bidirectional"))
      (node (ref "UC1") (pin "PB9") (pinfunction "PB9_PB9") (pintype "passive"))
    )
    (net (code "657") (name "PB10") (class "Default")
      (node (ref "J14") (pin "73") (pinfunction "73_73") (pintype "passive"))
      (node (ref "PB10") (pin "TP") (pinfunction "TP_TP") (pintype "bidirectional"))
      (node (ref "UC1") (pin "PB10") (pinfunction "PB10_PB10") (pintype "passive"))
    )
    (net (code "658") (name "PB11") (class "Default")
      (node (ref "J14") (pin "71") (pinfunction "71_71") (pintype "passive"))
      (node (ref "PB11") (pin "TP") (pinfunction "TP_TP") (pintype "bidirectional"))
      (node (ref "UC1") (pin "PB11") (pinfunction "PB11_PB11") (pintype "passive"))
    )
    (net (code "659") (name "PB12") (class "Default")
      (node (ref "J14") (pin "69") (pinfunction "69_69") (pintype "passive"))
      (node (ref "PB12") (pin "TP") (pinfunction "TP_TP") (pintype "bidirectional"))
      (node (ref "UC1") (pin "PB12") (pinfunction "PB12_PB12") (pintype "passive"))
    )
    (net (code "660") (name "PB14") (class "Default")
      (node (ref "J14") (pin "65") (pinfunction "65_65") (pintype "passive"))
      (node (ref "PB14") (pin "TP") (pinfunction "TP_TP") (pintype "bidirectional"))
      (node (ref "UC1") (pin "PB14") (pinfunction "PB14_PB14") (pintype "passive"))
    )
    (net (code "661") (name "PB15") (class "Default")
      (node (ref "J14") (pin "63") (pinfunction "63_63") (pintype "passive"))
      (node (ref "PB15") (pin "TP") (pinfunction "TP_TP") (pintype "bidirectional"))
      (node (ref "UC1") (pin "PB15") (pinfunction "PB15_PB15") (pintype "passive"))
    )
    (net (code "662") (name "PC0") (class "Default")
      (node (ref "J14") (pin "61") (pinfunction "61_61") (pintype "passive"))
      (node (ref "PC0") (pin "TP") (pinfunction "TP_TP") (pintype "bidirectional"))
      (node (ref "UC1") (pin "PC0") (pinfunction "PC0_PC0") (pintype "passive"))
    )
    (net (code "663") (name "PC2") (class "Default")
      (node (ref "J14") (pin "59") (pinfunction "59_59") (pintype "passive"))
      (node (ref "PC2") (pin "TP") (pinfunction "TP_TP") (pintype "bidirectional"))
      (node (ref "UC1") (pin "PC2") (pinfunction "PC2_PC2") (pintype "passive"))
    )
    (net (code "664") (name "PC3") (class "Default")
      (node (ref "J14") (pin "57") (pinfunction "57_57") (pintype "passive"))
      (node (ref "PC3") (pin "TP") (pinfunction "TP_TP") (pintype "bidirectional"))
      (node (ref "UC1") (pin "PC3") (pinfunction "PC3_PC3") (pintype "passive"))
    )
    (net (code "665") (name "PC6") (class "Default")
      (node (ref "J14") (pin "55") (pinfunction "55_55") (pintype "passive"))
      (node (ref "PC6") (pin "TP") (pinfunction "TP_TP") (pintype "bidirectional"))
      (node (ref "UC1") (pin "PC6") (pinfunction "PC6_PC6") (pintype "passive"))
    )
    (net (code "666") (name "PC7") (class "Default")
      (node (ref "J14") (pin "53") (pinfunction "53_53") (pintype "passive"))
      (node (ref "PC7") (pin "TP") (pinfunction "TP_TP") (pintype "bidirectional"))
      (node (ref "UC1") (pin "PC7") (pinfunction "PC7_PC7") (pintype "passive"))
    )
    (net (code "667") (name "PC8") (class "Default")
      (node (ref "J14") (pin "51") (pinfunction "51_51") (pintype "passive"))
      (node (ref "PC8") (pin "TP") (pinfunction "TP_TP") (pintype "bidirectional"))
      (node (ref "UC1") (pin "PC8") (pinfunction "PC8_PC8") (pintype "passive"))
    )
    (net (code "668") (name "PC9") (class "Default")
      (node (ref "J14") (pin "49") (pinfunction "49_49") (pintype "passive"))
      (node (ref "PC9") (pin "TP") (pinfunction "TP_TP") (pintype "bidirectional"))
      (node (ref "UC1") (pin "PC9") (pinfunction "PC9_PC9") (pintype "passive"))
    )
    (net (code "669") (name "PC10") (class "Default")
      (node (ref "J14") (pin "47") (pinfunction "47_47") (pintype "passive"))
      (node (ref "PC10") (pin "TP") (pinfunction "TP_TP") (pintype "bidirectional"))
      (node (ref "UC1") (pin "PC10") (pinfunction "PC10_PC10") (pintype "passive"))
    )
    (net (code "670") (name "PC11") (class "Default")
      (node (ref "J14") (pin "45") (pinfunction "45_45") (pintype "passive"))
      (node (ref "PC11") (pin "TP") (pinfunction "TP_TP") (pintype "bidirectional"))
      (node (ref "UC1") (pin "PC11") (pinfunction "PC11_PC11") (pintype "passive"))
    )
    (net (code "671") (name "PC12") (class "Default")
      (node (ref "J14") (pin "43") (pinfunction "43_43") (pintype "passive"))
      (node (ref "PC12") (pin "TP") (pinfunction "TP_TP") (pintype "bidirectional"))
      (node (ref "UC1") (pin "PC12") (pinfunction "PC12_PC12") (pintype "passive"))
    )
    (net (code "672") (name "PC13") (class "Default")
      (node (ref "J14") (pin "41") (pinfunction "41_41") (pintype "passive"))
      (node (ref "PC13") (pin "TP") (pinfunction "TP_TP") (pintype "bidirectional"))
      (node (ref "UC1") (pin "PC13") (pinfunction "PC13_PC13") (pintype "passive"))
    )
    (net (code "673") (name "PC14-0SC32_IN") (class "Default")
      (node (ref "UC1") (pin "PC14") (pinfunction "PC14_PC14") (pintype "passive"))
    )
    (net (code "674") (name "PC15-OSC32_OUT") (class "Default")
      (node (ref "UC1") (pin "PC15") (pinfunction "PC15_PC15") (pintype "passive"))
    )
    (net (code "675") (name "PD0") (class "Default")
      (node (ref "J14") (pin "02") (pinfunction "02_02") (pintype "passive"))
      (node (ref "PD0") (pin "TP") (pinfunction "TP_TP") (pintype "bidirectional"))
      (node (ref "UC1") (pin "PD0") (pinfunction "PD0_PD0") (pintype "passive"))
    )
    (net (code "676") (name "PD1") (class "Default")
      (node (ref "J14") (pin "04") (pinfunction "04_04") (pintype "passive"))
      (node (ref "PD1") (pin "TP") (pinfunction "TP_TP") (pintype "bidirectional"))
      (node (ref "UC1") (pin "PD1") (pinfunction "PD1_PD1") (pintype "passive"))
    )
    (net (code "677") (name "PD2") (class "Default")
      (node (ref "J14") (pin "06") (pinfunction "06_06") (pintype "passive"))
      (node (ref "PD2") (pin "TP") (pinfunction "TP_TP") (pintype "bidirectional"))
      (node (ref "UC1") (pin "PD2") (pinfunction "PD2_PD2") (pintype "passive"))
    )
    (net (code "678") (name "PD3") (class "Default")
      (node (ref "J14") (pin "08") (pinfunction "08_08") (pintype "passive"))
      (node (ref "PD3") (pin "TP") (pinfunction "TP_TP") (pintype "bidirectional"))
      (node (ref "UC1") (pin "PD3") (pinfunction "PD3_PD3") (pintype "passive"))
    )
    (net (code "679") (name "PD4") (class "Default")
      (node (ref "J14") (pin "10") (pinfunction "10_10") (pintype "passive"))
      (node (ref "PD4") (pin "TP") (pinfunction "TP_TP") (pintype "bidirectional"))
      (node (ref "UC1") (pin "PD4") (pinfunction "PD4_PD4") (pintype "passive"))
    )
    (net (code "680") (name "PD5") (class "Default")
      (node (ref "J14") (pin "12") (pinfunction "12_12") (pintype "passive"))
      (node (ref "PD5") (pin "TP") (pinfunction "TP_TP") (pintype "bidirectional"))
      (node (ref "UC1") (pin "PD5") (pinfunction "PD5_PD5") (pintype "passive"))
    )
    (net (code "681") (name "PD6") (class "Default")
      (node (ref "J14") (pin "14") (pinfunction "14_14") (pintype "passive"))
      (node (ref "PD6") (pin "TP") (pinfunction "TP_TP") (pintype "bidirectional"))
      (node (ref "UC1") (pin "PD6") (pinfunction "PD6_PD6") (pintype "passive"))
    )
    (net (code "682") (name "PD7") (class "Default")
      (node (ref "J14") (pin "16") (pinfunction "16_16") (pintype "passive"))
      (node (ref "PD7") (pin "TP") (pinfunction "TP_TP") (pintype "bidirectional"))
      (node (ref "UC1") (pin "PD7") (pinfunction "PD7_PD7") (pintype "passive"))
    )
    (net (code "683") (name "PD11") (class "Default")
      (node (ref "J14") (pin "18") (pinfunction "18_18") (pintype "passive"))
      (node (ref "PD11") (pin "TP") (pinfunction "TP_TP") (pintype "bidirectional"))
      (node (ref "UC1") (pin "PD11") (pinfunction "PD11_PD11") (pintype "passive"))
    )
    (net (code "684") (name "PD12") (class "Default")
      (node (ref "J14") (pin "20") (pinfunction "20_20") (pintype "passive"))
      (node (ref "PD12") (pin "TP") (pinfunction "TP_TP") (pintype "bidirectional"))
      (node (ref "UC1") (pin "PD12") (pinfunction "PD12_PD12") (pintype "passive"))
    )
    (net (code "685") (name "PD13") (class "Default")
      (node (ref "J14") (pin "22") (pinfunction "22_22") (pintype "passive"))
      (node (ref "PD13") (pin "TP") (pinfunction "TP_TP") (pintype "bidirectional"))
      (node (ref "UC1") (pin "PD13") (pinfunction "PD13_PD13") (pintype "passive"))
    )
    (net (code "686") (name "PD14") (class "Default")
      (node (ref "J14") (pin "24") (pinfunction "24_24") (pintype "passive"))
      (node (ref "PD14") (pin "TP") (pinfunction "TP_TP") (pintype "bidirectional"))
      (node (ref "UC1") (pin "PD14") (pinfunction "PD14_PD14") (pintype "passive"))
    )
    (net (code "687") (name "PD15") (class "Default")
      (node (ref "J14") (pin "26") (pinfunction "26_26") (pintype "passive"))
      (node (ref "PD15") (pin "TP") (pinfunction "TP_TP") (pintype "bidirectional"))
      (node (ref "UC1") (pin "PD15") (pinfunction "PD15_PD15") (pintype "passive"))
    )
    (net (code "688") (name "PE0") (class "Default")
      (node (ref "J14") (pin "28") (pinfunction "28_28") (pintype "passive"))
      (node (ref "PE0") (pin "TP") (pinfunction "TP_TP") (pintype "bidirectional"))
      (node (ref "UC1") (pin "PE0") (pinfunction "PE0_PE0") (pintype "passive"))
    )
    (net (code "689") (name "PE1") (class "Default")
      (node (ref "J14") (pin "30") (pinfunction "30_30") (pintype "passive"))
      (node (ref "PE1") (pin "TP") (pinfunction "TP_TP") (pintype "bidirectional"))
      (node (ref "UC1") (pin "PE1") (pinfunction "PE1_PE1") (pintype "passive"))
    )
    (net (code "690") (name "PE2") (class "Default")
      (node (ref "J14") (pin "32") (pinfunction "32_32") (pintype "passive"))
      (node (ref "PE2") (pin "TP") (pinfunction "TP_TP") (pintype "bidirectional"))
      (node (ref "UC1") (pin "PE2") (pinfunction "PE2_PE2") (pintype "passive"))
    )
    (net (code "691") (name "PE3") (class "Default")
      (node (ref "J14") (pin "34") (pinfunction "34_34") (pintype "passive"))
      (node (ref "PE3") (pin "TP") (pinfunction "TP_TP") (pintype "bidirectional"))
      (node (ref "UC1") (pin "PE3") (pinfunction "PE3_PE3") (pintype "passive"))
    )
    (net (code "692") (name "PE4") (class "Default")
      (node (ref "J14") (pin "36") (pinfunction "36_36") (pintype "passive"))
      (node (ref "PE4") (pin "TP") (pinfunction "TP_TP") (pintype "bidirectional"))
      (node (ref "UC1") (pin "PE4") (pinfunction "PE4_PE4") (pintype "passive"))
    )
    (net (code "693") (name "PE5") (class "Default")
      (node (ref "J14") (pin "38") (pinfunction "38_38") (pintype "passive"))
      (node (ref "PE5") (pin "TP") (pinfunction "TP_TP") (pintype "bidirectional"))
      (node (ref "UC1") (pin "PE5") (pinfunction "PE5_PE5") (pintype "passive"))
    )
    (net (code "694") (name "PE6") (class "Default")
      (node (ref "J14") (pin "40") (pinfunction "40_40") (pintype "passive"))
      (node (ref "PE6") (pin "TP") (pinfunction "TP_TP") (pintype "bidirectional"))
      (node (ref "UC1") (pin "PE6") (pinfunction "PE6_PE6") (pintype "passive"))
    )
    (net (code "695") (name "PE7") (class "Default")
      (node (ref "J14") (pin "80") (pinfunction "80_80") (pintype "passive"))
      (node (ref "PE7") (pin "TP") (pinfunction "TP_TP") (pintype "bidirectional"))
      (node (ref "UC1") (pin "PE7") (pinfunction "PE7_PE7") (pintype "passive"))
    )
    (net (code "696") (name "PE8") (class "Default")
      (node (ref "J14") (pin "78") (pinfunction "78_78") (pintype "passive"))
      (node (ref "PE8") (pin "TP") (pinfunction "TP_TP") (pintype "bidirectional"))
      (node (ref "UC1") (pin "PE8") (pinfunction "PE8_PE8") (pintype "passive"))
    )
    (net (code "697") (name "PE9") (class "Default")
      (node (ref "J14") (pin "76") (pinfunction "76_76") (pintype "passive"))
      (node (ref "PE9") (pin "TP") (pinfunction "TP_TP") (pintype "bidirectional"))
      (node (ref "UC1") (pin "PE9") (pinfunction "PE9_PE9") (pintype "passive"))
    )
    (net (code "698") (name "PE10") (class "Default")
      (node (ref "J14") (pin "74") (pinfunction "74_74") (pintype "passive"))
      (node (ref "PE10") (pin "TP") (pinfunction "TP_TP") (pintype "bidirectional"))
      (node (ref "UC1") (pin "PE10") (pinfunction "PE10_PE10") (pintype "passive"))
    )
    (net (code "699") (name "PE11") (class "Default")
      (node (ref "J14") (pin "72") (pinfunction "72_72") (pintype "passive"))
      (node (ref "PE11") (pin "TP") (pinfunction "TP_TP") (pintype "bidirectional"))
      (node (ref "UC1") (pin "PE11") (pinfunction "PE11_PE11") (pintype "passive"))
    )
    (net (code "700") (name "PE12") (class "Default")
      (node (ref "J14") (pin "70") (pinfunction "70_70") (pintype "passive"))
      (node (ref "PE12") (pin "TP") (pinfunction "TP_TP") (pintype "bidirectional"))
      (node (ref "UC1") (pin "PE12") (pinfunction "PE12_PE12") (pintype "passive"))
    )
    (net (code "701") (name "PE13") (class "Default")
      (node (ref "J14") (pin "68") (pinfunction "68_68") (pintype "passive"))
      (node (ref "PE13") (pin "TP") (pinfunction "TP_TP") (pintype "bidirectional"))
      (node (ref "UC1") (pin "PE13") (pinfunction "PE13_PE13") (pintype "passive"))
    )
    (net (code "702") (name "PE14") (class "Default")
      (node (ref "J14") (pin "66") (pinfunction "66_66") (pintype "passive"))
      (node (ref "PE14") (pin "TP") (pinfunction "TP_TP") (pintype "bidirectional"))
      (node (ref "UC1") (pin "PE14") (pinfunction "PE14_PE14") (pintype "passive"))
    )
    (net (code "703") (name "PE15") (class "Default")
      (node (ref "J14") (pin "64") (pinfunction "64_64") (pintype "passive"))
      (node (ref "PE15") (pin "TP") (pinfunction "TP_TP") (pintype "bidirectional"))
      (node (ref "UC1") (pin "PE15") (pinfunction "PE15_PE15") (pintype "passive"))
    )
    (net (code "704") (name "PF0") (class "Default")
      (node (ref "J12") (pin "23") (pinfunction "23_23") (pintype "passive"))
      (node (ref "PF0") (pin "TP") (pinfunction "TP_TP") (pintype "bidirectional"))
      (node (ref "UC1") (pin "PF0") (pinfunction "PF0_PF0") (pintype "passive"))
    )
    (net (code "705") (name "PF1") (class "Default")
      (node (ref "J14") (pin "62") (pinfunction "62_62") (pintype "passive"))
      (node (ref "PF1") (pin "TP") (pinfunction "TP_TP") (pintype "bidirectional"))
      (node (ref "UC1") (pin "PF1") (pinfunction "PF1_PF1") (pintype "passive"))
    )
    (net (code "706") (name "PF2") (class "Default")
      (node (ref "J14") (pin "60") (pinfunction "60_60") (pintype "passive"))
      (node (ref "PF2") (pin "TP") (pinfunction "TP_TP") (pintype "bidirectional"))
      (node (ref "UC1") (pin "PF2") (pinfunction "PF2_PF2") (pintype "passive"))
    )
    (net (code "707") (name "PF3") (class "Default")
      (node (ref "J14") (pin "58") (pinfunction "58_58") (pintype "passive"))
      (node (ref "PF3") (pin "TP") (pinfunction "TP_TP") (pintype "bidirectional"))
      (node (ref "UC1") (pin "PF3") (pinfunction "PF3_PF3") (pintype "passive"))
    )
    (net (code "708") (name "PF4") (class "Default")
      (node (ref "J14") (pin "56") (pinfunction "56_56") (pintype "passive"))
      (node (ref "PF4") (pin "TP") (pinfunction "TP_TP") (pintype "bidirectional"))
      (node (ref "UC1") (pin "PF4") (pinfunction "PF4_PF4") (pintype "passive"))
    )
    (net (code "709") (name "PF5") (class "Default")
      (node (ref "J14") (pin "54") (pinfunction "54_54") (pintype "passive"))
      (node (ref "PF5") (pin "TP") (pinfunction "TP_TP") (pintype "bidirectional"))
      (node (ref "UC1") (pin "PF5") (pinfunction "PF5_PF5") (pintype "passive"))
    )
    (net (code "710") (name "PF6") (class "Default")
      (node (ref "J14") (pin "52") (pinfunction "52_52") (pintype "passive"))
      (node (ref "PF6") (pin "TP") (pinfunction "TP_TP") (pintype "bidirectional"))
      (node (ref "UC1") (pin "PF6") (pinfunction "PF6_PF6") (pintype "passive"))
    )
    (net (code "711") (name "PF7") (class "Default")
      (node (ref "J14") (pin "50") (pinfunction "50_50") (pintype "passive"))
      (node (ref "PF7") (pin "TP") (pinfunction "TP_TP") (pintype "bidirectional"))
      (node (ref "UC1") (pin "PF7") (pinfunction "PF7_PF7") (pintype "passive"))
    )
    (net (code "712") (name "PF8") (class "Default")
      (node (ref "J14") (pin "48") (pinfunction "48_48") (pintype "passive"))
      (node (ref "PF8") (pin "TP") (pinfunction "TP_TP") (pintype "bidirectional"))
      (node (ref "UC1") (pin "PF8") (pinfunction "PF8_PF8") (pintype "passive"))
    )
    (net (code "713") (name "PF9") (class "Default")
      (node (ref "J14") (pin "46") (pinfunction "46_46") (pintype "passive"))
      (node (ref "PF9") (pin "TP") (pinfunction "TP_TP") (pintype "bidirectional"))
      (node (ref "UC1") (pin "PF9") (pinfunction "PF9_PF9") (pintype "passive"))
    )
    (net (code "714") (name "PF10") (class "Default")
      (node (ref "J14") (pin "44") (pinfunction "44_44") (pintype "passive"))
      (node (ref "PF10") (pin "TP") (pinfunction "TP_TP") (pintype "bidirectional"))
      (node (ref "UC1") (pin "PF10") (pinfunction "PF10_PF10") (pintype "passive"))
    )
    (net (code "715") (name "PF11") (class "Default")
      (node (ref "J14") (pin "42") (pinfunction "42_42") (pintype "passive"))
      (node (ref "PF11") (pin "TP") (pinfunction "TP_TP") (pintype "bidirectional"))
      (node (ref "UC1") (pin "PF11") (pinfunction "PF11_PF11") (pintype "passive"))
    )
    (net (code "716") (name "PF12") (class "Default")
      (node (ref "J12") (pin "01") (pinfunction "01_01") (pintype "passive"))
      (node (ref "PF12") (pin "TP") (pinfunction "TP_TP") (pintype "bidirectional"))
      (node (ref "UC1") (pin "PF12") (pinfunction "PF12_PF12") (pintype "passive"))
    )
    (net (code "717") (name "PF13") (class "Default")
      (node (ref "J12") (pin "03") (pinfunction "03_03") (pintype "passive"))
      (node (ref "PF13") (pin "TP") (pinfunction "TP_TP") (pintype "bidirectional"))
      (node (ref "UC1") (pin "PF13") (pinfunction "PF13_PF13") (pintype "passive"))
    )
    (net (code "718") (name "PF14") (class "Default")
      (node (ref "J12") (pin "05") (pinfunction "05_05") (pintype "passive"))
      (node (ref "PF14") (pin "TP") (pinfunction "TP_TP") (pintype "bidirectional"))
      (node (ref "UC1") (pin "PF14") (pinfunction "PF14_PF14") (pintype "passive"))
    )
    (net (code "719") (name "PF15") (class "Default")
      (node (ref "J12") (pin "07") (pinfunction "07_07") (pintype "passive"))
      (node (ref "PF15") (pin "TP") (pinfunction "TP_TP") (pintype "bidirectional"))
      (node (ref "UC1") (pin "PF15") (pinfunction "PF15_PF15") (pintype "passive"))
    )
    (net (code "720") (name "PG0") (class "Default")
      (node (ref "J12") (pin "09") (pinfunction "09_09") (pintype "passive"))
      (node (ref "PG0") (pin "TP") (pinfunction "TP_TP") (pintype "bidirectional"))
      (node (ref "UC1") (pin "PG0") (pinfunction "PG0_PG0") (pintype "passive"))
    )
    (net (code "721") (name "PG1") (class "Default")
      (node (ref "J12") (pin "11") (pinfunction "11_11") (pintype "passive"))
      (node (ref "PG1") (pin "TP") (pinfunction "TP_TP") (pintype "bidirectional"))
      (node (ref "UC1") (pin "PG1") (pinfunction "PG1_PG1") (pintype "passive"))
    )
    (net (code "722") (name "PG2") (class "Default")
      (node (ref "J12") (pin "13") (pinfunction "13_13") (pintype "passive"))
      (node (ref "PG2") (pin "TP") (pinfunction "TP_TP") (pintype "bidirectional"))
      (node (ref "UC1") (pin "PG2") (pinfunction "PG2_PG2") (pintype "passive"))
    )
    (net (code "723") (name "PG3") (class "Default")
      (node (ref "J12") (pin "15") (pinfunction "15_15") (pintype "passive"))
      (node (ref "PG3") (pin "TP") (pinfunction "TP_TP") (pintype "bidirectional"))
      (node (ref "UC1") (pin "PG3") (pinfunction "PG3_PG3") (pintype "passive"))
    )
    (net (code "724") (name "PG4") (class "Default")
      (node (ref "J12") (pin "17") (pinfunction "17_17") (pintype "passive"))
      (node (ref "PG4") (pin "TP") (pinfunction "TP_TP") (pintype "bidirectional"))
      (node (ref "UC1") (pin "PG4") (pinfunction "PG4_PG4") (pintype "passive"))
    )
    (net (code "725") (name "PG5") (class "Default")
      (node (ref "J12") (pin "19") (pinfunction "19_19") (pintype "passive"))
      (node (ref "PG5") (pin "TP") (pinfunction "TP_TP") (pintype "bidirectional"))
      (node (ref "UC1") (pin "PG5") (pinfunction "PG5_PG5") (pintype "passive"))
    )
    (net (code "726") (name "PG6") (class "Default")
      (node (ref "J12") (pin "21") (pinfunction "21_21") (pintype "passive"))
      (node (ref "PG6") (pin "TP") (pinfunction "TP_TP") (pintype "bidirectional"))
      (node (ref "UC1") (pin "PG6") (pinfunction "PG6_PG6") (pintype "passive"))
    )
    (net (code "727") (name "PG8") (class "Default")
      (node (ref "J12") (pin "25") (pinfunction "25_25") (pintype "passive"))
      (node (ref "PG8") (pin "TP") (pinfunction "TP_TP") (pintype "bidirectional"))
      (node (ref "UC1") (pin "PG8") (pinfunction "PG8_PG8") (pintype "passive"))
    )
    (net (code "728") (name "PG9") (class "Default")
      (node (ref "J12") (pin "27") (pinfunction "27_27") (pintype "passive"))
      (node (ref "PG9") (pin "TP") (pinfunction "TP_TP") (pintype "bidirectional"))
      (node (ref "UC1") (pin "PG9") (pinfunction "PG9_PG9") (pintype "passive"))
    )
    (net (code "729") (name "PG10") (class "Default")
      (node (ref "J12") (pin "29") (pinfunction "29_29") (pintype "passive"))
      (node (ref "PG10") (pin "TP") (pinfunction "TP_TP") (pintype "bidirectional"))
      (node (ref "UC1") (pin "PG10") (pinfunction "PG10_PG10") (pintype "passive"))
    )
    (net (code "730") (name "PG12") (class "Default")
      (node (ref "J12") (pin "31") (pinfunction "31_31") (pintype "passive"))
      (node (ref "PG12") (pin "TP") (pinfunction "TP_TP") (pintype "bidirectional"))
      (node (ref "UC1") (pin "PG12") (pinfunction "PG12_PG12") (pintype "passive"))
    )
    (net (code "731") (name "PG14") (class "Default")
      (node (ref "J12") (pin "33") (pinfunction "33_33") (pintype "passive"))
      (node (ref "PG14") (pin "TP") (pinfunction "TP_TP") (pintype "bidirectional"))
      (node (ref "UC1") (pin "PG14") (pinfunction "PG14_PG14") (pintype "passive"))
    )
    (net (code "732") (name "PG15") (class "Default")
      (node (ref "J12") (pin "35") (pinfunction "35_35") (pintype "passive"))
      (node (ref "PG15") (pin "TP") (pinfunction "TP_TP") (pintype "bidirectional"))
      (node (ref "UC1") (pin "PG15") (pinfunction "PG15_PG15") (pintype "passive"))
    )
    (net (code "733") (name "PH0-OSC_IN") (class "Default")
      (node (ref "UC1") (pin "PH0") (pinfunction "PH0_PH0") (pintype "passive"))
    )
    (net (code "734") (name "PH1") (class "Default")
      (node (ref "J12") (pin "37") (pinfunction "37_37") (pintype "passive"))
      (node (ref "PH1") (pin "TP") (pinfunction "TP_TP") (pintype "bidirectional"))
      (node (ref "UC1") (pin "PH1") (pinfunction "PH1_PH1") (pintype "passive"))
    )
    (net (code "735") (name "POWER_FAULT1") (class "Default")
      (node (ref "J2") (pin "7") (pinfunction "7_7") (pintype "passive"))
      (node (ref "J4") (pin "15") (pinfunction "15_15") (pintype "passive"))
      (node (ref "P_FAULT1") (pin "TP") (pinfunction "TP_TP") (pintype "bidirectional"))
    )
    (net (code "736") (name "POWER_FAULT2") (class "Default")
      (node (ref "J2") (pin "9") (pinfunction "9_9") (pintype "passive"))
      (node (ref "J4") (pin "17") (pinfunction "17_17") (pintype "passive"))
      (node (ref "P_FAULT2") (pin "TP") (pinfunction "TP_TP") (pintype "bidirectional"))
    )
    (net (code "737") (name "POWER_FAULT3") (class "Default")
      (node (ref "J2") (pin "11") (pinfunction "11_11") (pintype "passive"))
      (node (ref "J4") (pin "19") (pinfunction "19_19") (pintype "passive"))
      (node (ref "P_FAULT3") (pin "TP") (pinfunction "TP_TP") (pintype "bidirectional"))
    )
    (net (code "738") (name "POWER_INDICATOR") (class "Default")
      (node (ref "J1") (pin "2") (pinfunction "2_2") (pintype "passive"))
      (node (ref "R41") (pin "1") (pinfunction "1_1") (pintype "bidirectional"))
    )
    (net (code "739") (name "PPS_NC") (class "Default")
      (node (ref "J9") (pin "01") (pinfunction "01_01") (pintype "passive"))
    )
    (net (code "740") (name "P_LED") (class "Default")
      (node (ref "J4") (pin "64") (pinfunction "64_64") (pintype "passive"))
      (node (ref "LED_P") (pin "TP") (pinfunction "TP_TP") (pintype "bidirectional"))
      (node (ref "R42") (pin "2") (pinfunction "2_2") (pintype "bidirectional"))
    )
    (net (code "741") (name "REFCAPAB") (class "Default")
      (node (ref "C13") (pin "1") (pinfunction "1_1") (pintype "bidirectional"))
      (node (ref "IC51") (pin "44") (pinfunction "REFCAPA_44") (pintype "output"))
      (node (ref "IC51") (pin "45") (pinfunction "REFCAPB_45") (pintype "output"))
    )
    (net (code "742") (name "REFCAPAB00") (class "Default")
      (node (ref "C17") (pin "1") (pinfunction "1_1") (pintype "bidirectional"))
      (node (ref "IC52") (pin "44") (pinfunction "REFCAPA_44") (pintype "output"))
      (node (ref "IC52") (pin "45") (pinfunction "REFCAPB_45") (pintype "output"))
    )
    (net (code "743") (name "REFCAPAB0") (class "Default")
      (node (ref "C16") (pin "1") (pinfunction "1_1") (pintype "bidirectional"))
      (node (ref "IC38") (pin "44") (pinfunction "REFCAPA_44") (pintype "output"))
      (node (ref "IC38") (pin "45") (pinfunction "REFCAPB_45") (pintype "output"))
    )
    (net (code "744") (name "REFIN{slash}OUT") (class "Default")
      (node (ref "C1") (pin "1") (pinfunction "1_1") (pintype "bidirectional"))
      (node (ref "IC51") (pin "42") (pinfunction "REFIN/REFOUT_42") (pintype "bidirectional"))
    )
    (net (code "745") (name "REFIN{slash}OUT0") (class "Default")
      (node (ref "C22") (pin "1") (pinfunction "1_1") (pintype "bidirectional"))
      (node (ref "IC38") (pin "42") (pinfunction "REFIN/REFOUT_42") (pintype "bidirectional"))
    )
    (net (code "746") (name "REFIN{slash}OUT00") (class "Default")
      (node (ref "C25") (pin "1") (pinfunction "1_1") (pintype "bidirectional"))
      (node (ref "IC52") (pin "42") (pinfunction "REFIN/REFOUT_42") (pintype "bidirectional"))
    )
    (net (code "747") (name "REGCAP1") (class "Default")
      (node (ref "C9") (pin "1") (pinfunction "1_1") (pintype "bidirectional"))
      (node (ref "IC51") (pin "36") (pinfunction "REGCAP1_36") (pintype "output"))
    )
    (net (code "748") (name "REGCAP2") (class "Default")
      (node (ref "C8") (pin "1") (pinfunction "1_1") (pintype "bidirectional"))
      (node (ref "IC51") (pin "39") (pinfunction "REGCAP2_39") (pintype "output"))
    )
    (net (code "749") (name "REGCAP10") (class "Default")
      (node (ref "C3") (pin "1") (pinfunction "1_1") (pintype "bidirectional"))
      (node (ref "IC38") (pin "36") (pinfunction "REGCAP1_36") (pintype "output"))
    )
    (net (code "750") (name "REGCAP20") (class "Default")
      (node (ref "C2") (pin "1") (pinfunction "1_1") (pintype "bidirectional"))
      (node (ref "IC38") (pin "39") (pinfunction "REGCAP2_39") (pintype "output"))
    )
    (net (code "751") (name "REGCAP100") (class "Default")
      (node (ref "C21") (pin "1") (pinfunction "1_1") (pintype "bidirectional"))
      (node (ref "IC52") (pin "36") (pinfunction "REGCAP1_36") (pintype "output"))
    )
    (net (code "752") (name "REGCAP200") (class "Default")
      (node (ref "C20") (pin "1") (pinfunction "1_1") (pintype "bidirectional"))
      (node (ref "IC52") (pin "39") (pinfunction "REGCAP2_39") (pintype "output"))
    )
    (net (code "753") (name "RESET_ADC") (class "Default")
      (node (ref "IC38") (pin "11") (pinfunction "RESET_11") (pintype "input"))
      (node (ref "IC51") (pin "11") (pinfunction "RESET_11") (pintype "input"))
      (node (ref "IC52") (pin "11") (pinfunction "RESET_11") (pintype "input"))
      (node (ref "J4") (pin "49") (pinfunction "49_49") (pintype "passive"))
      (node (ref "RST_ADC") (pin "TP") (pinfunction "TP_TP") (pintype "bidirectional"))
    )
    (net (code "754") (name "SCL1") (class "Default")
      (node (ref "IC11") (pin "20") (pinfunction "SCL_20") (pintype "bidirectional"))
      (node (ref "IC12") (pin "20") (pinfunction "SCL_20") (pintype "bidirectional"))
      (node (ref "IC13") (pin "20") (pinfunction "SCL_20") (pintype "bidirectional"))
      (node (ref "IC18") (pin "20") (pinfunction "SCL_20") (pintype "bidirectional"))
      (node (ref "IC20") (pin "20") (pinfunction "SCL_20") (pintype "bidirectional"))
      (node (ref "IC21") (pin "20") (pinfunction "SCL_20") (pintype "bidirectional"))
      (node (ref "IC4") (pin "20") (pinfunction "SCL_20") (pintype "bidirectional"))
      (node (ref "J4") (pin "23") (pinfunction "23_23") (pintype "passive"))
      (node (ref "R148") (pin "1") (pinfunction "1_1") (pintype "bidirectional"))
      (node (ref "SCL1") (pin "TP") (pinfunction "TP_TP") (pintype "bidirectional"))
    )
    (net (code "755") (name "SCL2") (class "Default")
      (node (ref "IC14") (pin "20") (pinfunction "SCL_20") (pintype "bidirectional"))
      (node (ref "IC15") (pin "20") (pinfunction "SCL_20") (pintype "bidirectional"))
      (node (ref "IC16") (pin "20") (pinfunction "SCL_20") (pintype "bidirectional"))
      (node (ref "IC17") (pin "20") (pinfunction "SCL_20") (pintype "bidirectional"))
      (node (ref "IC19") (pin "20") (pinfunction "SCL_20") (pintype "bidirectional"))
      (node (ref "IC22") (pin "20") (pinfunction "SCL_20") (pintype "bidirectional"))
      (node (ref "IC23") (pin "20") (pinfunction "SCL_20") (pintype "bidirectional"))
      (node (ref "J4") (pin "29") (pinfunction "29_29") (pintype "passive"))
      (node (ref "R150") (pin "1") (pinfunction "1_1") (pintype "bidirectional"))
      (node (ref "SCL2") (pin "TP") (pinfunction "TP_TP") (pintype "bidirectional"))
    )
    (net (code "756") (name "SCLK_ADC") (class "Default")
      (node (ref "IC38") (pin "12") (pinfunction "~{RD}/SCLK_12") (pintype "input"))
      (node (ref "IC51") (pin "12") (pinfunction "~{RD}/SCLK_12") (pintype "input"))
      (node (ref "IC52") (pin "12") (pinfunction "~{RD}/SCLK_12") (pintype "input"))
      (node (ref "J4") (pin "51") (pinfunction "51_51") (pintype "passive"))
      (node (ref "SCLK_ADC") (pin "TP") (pinfunction "TP_TP") (pintype "bidirectional"))
    )
    (net (code "757") (name "SDA1") (class "Default")
      (node (ref "IC11") (pin "19") (pinfunction "SDA_19") (pintype "bidirectional"))
      (node (ref "IC12") (pin "19") (pinfunction "SDA_19") (pintype "bidirectional"))
      (node (ref "IC13") (pin "19") (pinfunction "SDA_19") (pintype "bidirectional"))
      (node (ref "IC18") (pin "19") (pinfunction "SDA_19") (pintype "bidirectional"))
      (node (ref "IC20") (pin "19") (pinfunction "SDA_19") (pintype "bidirectional"))
      (node (ref "IC21") (pin "19") (pinfunction "SDA_19") (pintype "bidirectional"))
      (node (ref "IC4") (pin "19") (pinfunction "SDA_19") (pintype "bidirectional"))
      (node (ref "J4") (pin "21") (pinfunction "21_21") (pintype "passive"))
      (node (ref "R147") (pin "1") (pinfunction "1_1") (pintype "bidirectional"))
      (node (ref "SDA1") (pin "TP") (pinfunction "TP_TP") (pintype "bidirectional"))
    )
    (net (code "758") (name "SDA2") (class "Default")
      (node (ref "IC14") (pin "19") (pinfunction "SDA_19") (pintype "bidirectional"))
      (node (ref "IC15") (pin "19") (pinfunction "SDA_19") (pintype "bidirectional"))
      (node (ref "IC16") (pin "19") (pinfunction "SDA_19") (pintype "bidirectional"))
      (node (ref "IC17") (pin "19") (pinfunction "SDA_19") (pintype "bidirectional"))
      (node (ref "IC19") (pin "19") (pinfunction "SDA_19") (pintype "bidirectional"))
      (node (ref "IC22") (pin "19") (pinfunction "SDA_19") (pintype "bidirectional"))
      (node (ref "IC23") (pin "19") (pinfunction "SDA_19") (pintype "bidirectional"))
      (node (ref "J4") (pin "27") (pinfunction "27_27") (pintype "passive"))
      (node (ref "R149") (pin "1") (pinfunction "1_1") (pintype "bidirectional"))
      (node (ref "SDA2") (pin "TP") (pinfunction "TP_TP") (pintype "bidirectional"))
    )
    (net (code "759") (name "SENSE1_") (class "Default")
      (node (ref "IC4") (pin "29") (pinfunction "SENSE1-_29") (pintype "bidirectional"))
      (node (ref "M1") (pin "1") (pinfunction "D_1") (pintype "bidirectional"))
      (node (ref "M1") (pin "2") (pinfunction "D_2") (pintype "bidirectional"))
      (node (ref "M1") (pin "5") (pinfunction "D_5") (pintype "bidirectional"))
      (node (ref "M1") (pin "6") (pinfunction "D_6") (pintype "bidirectional"))
      (node (ref "M1") (pin "7") (pinfunction "D_7") (pintype "bidirectional"))
      (node (ref "R92") (pin "2") (pinfunction "2_2") (pintype "bidirectional"))
    )
    (net (code "760") (name "SENSE1_0") (class "Default")
      (node (ref "IC11") (pin "29") (pinfunction "SENSE1-_29") (pintype "bidirectional"))
      (node (ref "M3") (pin "1") (pinfunction "D_1") (pintype "bidirectional"))
      (node (ref "M3") (pin "2") (pinfunction "D_2") (pintype "bidirectional"))
      (node (ref "M3") (pin "5") (pinfunction "D_5") (pintype "bidirectional"))
      (node (ref "M3") (pin "6") (pinfunction "D_6") (pintype "bidirectional"))
      (node (ref "M3") (pin "7") (pinfunction "D_7") (pintype "bidirectional"))
      (node (ref "R139") (pin "2") (pinfunction "2_2") (pintype "bidirectional"))
    )
    (net (code "761") (name "SENSE1_1") (class "Default")
      (node (ref "IC20") (pin "29") (pinfunction "SENSE1-_29") (pintype "bidirectional"))
      (node (ref "M21") (pin "1") (pinfunction "D_1") (pintype "bidirectional"))
      (node (ref "M21") (pin "2") (pinfunction "D_2") (pintype "bidirectional"))
      (node (ref "M21") (pin "5") (pinfunction "D_5") (pintype "bidirectional"))
      (node (ref "M21") (pin "6") (pinfunction "D_6") (pintype "bidirectional"))
      (node (ref "M21") (pin "7") (pinfunction "D_7") (pintype "bidirectional"))
      (node (ref "R364") (pin "2") (pinfunction "2_2") (pintype "bidirectional"))
    )
    (net (code "762") (name "SENSE1_2") (class "Default")
      (node (ref "IC21") (pin "29") (pinfunction "SENSE1-_29") (pintype "bidirectional"))
      (node (ref "M23") (pin "1") (pinfunction "D_1") (pintype "bidirectional"))
      (node (ref "M23") (pin "2") (pinfunction "D_2") (pintype "bidirectional"))
      (node (ref "M23") (pin "5") (pinfunction "D_5") (pintype "bidirectional"))
      (node (ref "M23") (pin "6") (pinfunction "D_6") (pintype "bidirectional"))
      (node (ref "M23") (pin "7") (pinfunction "D_7") (pintype "bidirectional"))
      (node (ref "R385") (pin "2") (pinfunction "2_2") (pintype "bidirectional"))
    )
    (net (code "763") (name "SENSE1_3") (class "Default")
      (node (ref "IC12") (pin "29") (pinfunction "SENSE1-_29") (pintype "bidirectional"))
      (node (ref "M5") (pin "1") (pinfunction "D_1") (pintype "bidirectional"))
      (node (ref "M5") (pin "2") (pinfunction "D_2") (pintype "bidirectional"))
      (node (ref "M5") (pin "5") (pinfunction "D_5") (pintype "bidirectional"))
      (node (ref "M5") (pin "6") (pinfunction "D_6") (pintype "bidirectional"))
      (node (ref "M5") (pin "7") (pinfunction "D_7") (pintype "bidirectional"))
      (node (ref "R177") (pin "2") (pinfunction "2_2") (pintype "bidirectional"))
    )
    (net (code "764") (name "SENSE1_4") (class "Default")
      (node (ref "IC13") (pin "29") (pinfunction "SENSE1-_29") (pintype "bidirectional"))
      (node (ref "M7") (pin "1") (pinfunction "D_1") (pintype "bidirectional"))
      (node (ref "M7") (pin "2") (pinfunction "D_2") (pintype "bidirectional"))
      (node (ref "M7") (pin "5") (pinfunction "D_5") (pintype "bidirectional"))
      (node (ref "M7") (pin "6") (pinfunction "D_6") (pintype "bidirectional"))
      (node (ref "M7") (pin "7") (pinfunction "D_7") (pintype "bidirectional"))
      (node (ref "R198") (pin "2") (pinfunction "2_2") (pintype "bidirectional"))
    )
    (net (code "765") (name "SENSE1_5") (class "Default")
      (node (ref "IC18") (pin "29") (pinfunction "SENSE1-_29") (pintype "bidirectional"))
      (node (ref "M17") (pin "1") (pinfunction "D_1") (pintype "bidirectional"))
      (node (ref "M17") (pin "2") (pinfunction "D_2") (pintype "bidirectional"))
      (node (ref "M17") (pin "5") (pinfunction "D_5") (pintype "bidirectional"))
      (node (ref "M17") (pin "6") (pinfunction "D_6") (pintype "bidirectional"))
      (node (ref "M17") (pin "7") (pinfunction "D_7") (pintype "bidirectional"))
      (node (ref "R322") (pin "2") (pinfunction "2_2") (pintype "bidirectional"))
    )
    (net (code "766") (name "SENSE1_6") (class "Default")
      (node (ref "IC19") (pin "29") (pinfunction "SENSE1-_29") (pintype "bidirectional"))
      (node (ref "M19") (pin "1") (pinfunction "D_1") (pintype "bidirectional"))
      (node (ref "M19") (pin "2") (pinfunction "D_2") (pintype "bidirectional"))
      (node (ref "M19") (pin "5") (pinfunction "D_5") (pintype "bidirectional"))
      (node (ref "M19") (pin "6") (pinfunction "D_6") (pintype "bidirectional"))
      (node (ref "M19") (pin "7") (pinfunction "D_7") (pintype "bidirectional"))
      (node (ref "R343") (pin "2") (pinfunction "2_2") (pintype "bidirectional"))
    )
    (net (code "767") (name "SENSE1_7") (class "Default")
      (node (ref "IC14") (pin "29") (pinfunction "SENSE1-_29") (pintype "bidirectional"))
      (node (ref "M9") (pin "1") (pinfunction "D_1") (pintype "bidirectional"))
      (node (ref "M9") (pin "2") (pinfunction "D_2") (pintype "bidirectional"))
      (node (ref "M9") (pin "5") (pinfunction "D_5") (pintype "bidirectional"))
      (node (ref "M9") (pin "6") (pinfunction "D_6") (pintype "bidirectional"))
      (node (ref "M9") (pin "7") (pinfunction "D_7") (pintype "bidirectional"))
      (node (ref "R226") (pin "2") (pinfunction "2_2") (pintype "bidirectional"))
    )
    (net (code "768") (name "SENSE1_8") (class "Default")
      (node (ref "IC15") (pin "29") (pinfunction "SENSE1-_29") (pintype "bidirectional"))
      (node (ref "M11") (pin "1") (pinfunction "D_1") (pintype "bidirectional"))
      (node (ref "M11") (pin "2") (pinfunction "D_2") (pintype "bidirectional"))
      (node (ref "M11") (pin "5") (pinfunction "D_5") (pintype "bidirectional"))
      (node (ref "M11") (pin "6") (pinfunction "D_6") (pintype "bidirectional"))
      (node (ref "M11") (pin "7") (pinfunction "D_7") (pintype "bidirectional"))
      (node (ref "R259") (pin "2") (pinfunction "2_2") (pintype "bidirectional"))
    )
    (net (code "769") (name "SENSE1_9") (class "Default")
      (node (ref "IC16") (pin "29") (pinfunction "SENSE1-_29") (pintype "bidirectional"))
      (node (ref "M13") (pin "1") (pinfunction "D_1") (pintype "bidirectional"))
      (node (ref "M13") (pin "2") (pinfunction "D_2") (pintype "bidirectional"))
      (node (ref "M13") (pin "5") (pinfunction "D_5") (pintype "bidirectional"))
      (node (ref "M13") (pin "6") (pinfunction "D_6") (pintype "bidirectional"))
      (node (ref "M13") (pin "7") (pinfunction "D_7") (pintype "bidirectional"))
      (node (ref "R280") (pin "2") (pinfunction "2_2") (pintype "bidirectional"))
    )
    (net (code "770") (name "SENSE1_10") (class "Default")
      (node (ref "IC17") (pin "29") (pinfunction "SENSE1-_29") (pintype "bidirectional"))
      (node (ref "M15") (pin "1") (pinfunction "D_1") (pintype "bidirectional"))
      (node (ref "M15") (pin "2") (pinfunction "D_2") (pintype "bidirectional"))
      (node (ref "M15") (pin "5") (pinfunction "D_5") (pintype "bidirectional"))
      (node (ref "M15") (pin "6") (pinfunction "D_6") (pintype "bidirectional"))
      (node (ref "M15") (pin "7") (pinfunction "D_7") (pintype "bidirectional"))
      (node (ref "R301") (pin "2") (pinfunction "2_2") (pintype "bidirectional"))
    )
    (net (code "771") (name "SENSE1_11") (class "Default")
      (node (ref "IC22") (pin "29") (pinfunction "SENSE1-_29") (pintype "bidirectional"))
      (node (ref "M25") (pin "1") (pinfunction "D_1") (pintype "bidirectional"))
      (node (ref "M25") (pin "2") (pinfunction "D_2") (pintype "bidirectional"))
      (node (ref "M25") (pin "5") (pinfunction "D_5") (pintype "bidirectional"))
      (node (ref "M25") (pin "6") (pinfunction "D_6") (pintype "bidirectional"))
      (node (ref "M25") (pin "7") (pinfunction "D_7") (pintype "bidirectional"))
      (node (ref "R406") (pin "2") (pinfunction "2_2") (pintype "bidirectional"))
    )
    (net (code "772") (name "SENSE1_12") (class "Default")
      (node (ref "IC23") (pin "29") (pinfunction "SENSE1-_29") (pintype "bidirectional"))
      (node (ref "M27") (pin "1") (pinfunction "D_1") (pintype "bidirectional"))
      (node (ref "M27") (pin "2") (pinfunction "D_2") (pintype "bidirectional"))
      (node (ref "M27") (pin "5") (pinfunction "D_5") (pintype "bidirectional"))
      (node (ref "M27") (pin "6") (pinfunction "D_6") (pintype "bidirectional"))
      (node (ref "M27") (pin "7") (pinfunction "D_7") (pintype "bidirectional"))
      (node (ref "R427") (pin "2") (pinfunction "2_2") (pintype "bidirectional"))
    )
    (net (code "773") (name "SENSE2_") (class "Default")
      (node (ref "IC4") (pin "12") (pinfunction "SENSE2-_12") (pintype "bidirectional"))
      (node (ref "M2") (pin "1") (pinfunction "D_1") (pintype "bidirectional"))
      (node (ref "M2") (pin "2") (pinfunction "D_2") (pintype "bidirectional"))
      (node (ref "M2") (pin "5") (pinfunction "D_5") (pintype "bidirectional"))
      (node (ref "M2") (pin "6") (pinfunction "D_6") (pintype "bidirectional"))
      (node (ref "M2") (pin "7") (pinfunction "D_7") (pintype "bidirectional"))
      (node (ref "R129") (pin "2") (pinfunction "2_2") (pintype "bidirectional"))
    )
    (net (code "774") (name "SENSE2_0") (class "Default")
      (node (ref "IC11") (pin "12") (pinfunction "SENSE2-_12") (pintype "bidirectional"))
      (node (ref "M4") (pin "1") (pinfunction "D_1") (pintype "bidirectional"))
      (node (ref "M4") (pin "2") (pinfunction "D_2") (pintype "bidirectional"))
      (node (ref "M4") (pin "5") (pinfunction "D_5") (pintype "bidirectional"))
      (node (ref "M4") (pin "6") (pinfunction "D_6") (pintype "bidirectional"))
      (node (ref "M4") (pin "7") (pinfunction "D_7") (pintype "bidirectional"))
      (node (ref "R167") (pin "2") (pinfunction "2_2") (pintype "bidirectional"))
    )
    (net (code "775") (name "SENSE2_1") (class "Default")
      (node (ref "IC20") (pin "12") (pinfunction "SENSE2-_12") (pintype "bidirectional"))
      (node (ref "M22") (pin "1") (pinfunction "D_1") (pintype "bidirectional"))
      (node (ref "M22") (pin "2") (pinfunction "D_2") (pintype "bidirectional"))
      (node (ref "M22") (pin "5") (pinfunction "D_5") (pintype "bidirectional"))
      (node (ref "M22") (pin "6") (pinfunction "D_6") (pintype "bidirectional"))
      (node (ref "M22") (pin "7") (pinfunction "D_7") (pintype "bidirectional"))
      (node (ref "R375") (pin "2") (pinfunction "2_2") (pintype "bidirectional"))
    )
    (net (code "776") (name "SENSE2_2") (class "Default")
      (node (ref "IC21") (pin "12") (pinfunction "SENSE2-_12") (pintype "bidirectional"))
      (node (ref "M24") (pin "1") (pinfunction "D_1") (pintype "bidirectional"))
      (node (ref "M24") (pin "2") (pinfunction "D_2") (pintype "bidirectional"))
      (node (ref "M24") (pin "5") (pinfunction "D_5") (pintype "bidirectional"))
      (node (ref "M24") (pin "6") (pinfunction "D_6") (pintype "bidirectional"))
      (node (ref "M24") (pin "7") (pinfunction "D_7") (pintype "bidirectional"))
      (node (ref "R396") (pin "2") (pinfunction "2_2") (pintype "bidirectional"))
    )
    (net (code "777") (name "SENSE2_3") (class "Default")
      (node (ref "IC12") (pin "12") (pinfunction "SENSE2-_12") (pintype "bidirectional"))
      (node (ref "M6") (pin "1") (pinfunction "D_1") (pintype "bidirectional"))
      (node (ref "M6") (pin "2") (pinfunction "D_2") (pintype "bidirectional"))
      (node (ref "M6") (pin "5") (pinfunction "D_5") (pintype "bidirectional"))
      (node (ref "M6") (pin "6") (pinfunction "D_6") (pintype "bidirectional"))
      (node (ref "M6") (pin "7") (pinfunction "D_7") (pintype "bidirectional"))
      (node (ref "R188") (pin "2") (pinfunction "2_2") (pintype "bidirectional"))
    )
    (net (code "778") (name "SENSE2_4") (class "Default")
      (node (ref "IC13") (pin "12") (pinfunction "SENSE2-_12") (pintype "bidirectional"))
      (node (ref "M8") (pin "1") (pinfunction "D_1") (pintype "bidirectional"))
      (node (ref "M8") (pin "2") (pinfunction "D_2") (pintype "bidirectional"))
      (node (ref "M8") (pin "5") (pinfunction "D_5") (pintype "bidirectional"))
      (node (ref "M8") (pin "6") (pinfunction "D_6") (pintype "bidirectional"))
      (node (ref "M8") (pin "7") (pinfunction "D_7") (pintype "bidirectional"))
      (node (ref "R215") (pin "2") (pinfunction "2_2") (pintype "bidirectional"))
    )
    (net (code "779") (name "SENSE2_5") (class "Default")
      (node (ref "IC18") (pin "12") (pinfunction "SENSE2-_12") (pintype "bidirectional"))
      (node (ref "M18") (pin "1") (pinfunction "D_1") (pintype "bidirectional"))
      (node (ref "M18") (pin "2") (pinfunction "D_2") (pintype "bidirectional"))
      (node (ref "M18") (pin "5") (pinfunction "D_5") (pintype "bidirectional"))
      (node (ref "M18") (pin "6") (pinfunction "D_6") (pintype "bidirectional"))
      (node (ref "M18") (pin "7") (pinfunction "D_7") (pintype "bidirectional"))
      (node (ref "R333") (pin "2") (pinfunction "2_2") (pintype "bidirectional"))
    )
    (net (code "780") (name "SENSE2_6") (class "Default")
      (node (ref "IC19") (pin "12") (pinfunction "SENSE2-_12") (pintype "bidirectional"))
      (node (ref "M20") (pin "1") (pinfunction "D_1") (pintype "bidirectional"))
      (node (ref "M20") (pin "2") (pinfunction "D_2") (pintype "bidirectional"))
      (node (ref "M20") (pin "5") (pinfunction "D_5") (pintype "bidirectional"))
      (node (ref "M20") (pin "6") (pinfunction "D_6") (pintype "bidirectional"))
      (node (ref "M20") (pin "7") (pinfunction "D_7") (pintype "bidirectional"))
      (node (ref "R354") (pin "2") (pinfunction "2_2") (pintype "bidirectional"))
    )
    (net (code "781") (name "SENSE2_7") (class "Default")
      (node (ref "IC14") (pin "12") (pinfunction "SENSE2-_12") (pintype "bidirectional"))
      (node (ref "M10") (pin "1") (pinfunction "D_1") (pintype "bidirectional"))
      (node (ref "M10") (pin "2") (pinfunction "D_2") (pintype "bidirectional"))
      (node (ref "M10") (pin "5") (pinfunction "D_5") (pintype "bidirectional"))
      (node (ref "M10") (pin "6") (pinfunction "D_6") (pintype "bidirectional"))
      (node (ref "M10") (pin "7") (pinfunction "D_7") (pintype "bidirectional"))
      (node (ref "R249") (pin "2") (pinfunction "2_2") (pintype "bidirectional"))
    )
    (net (code "782") (name "SENSE2_8") (class "Default")
      (node (ref "IC15") (pin "12") (pinfunction "SENSE2-_12") (pintype "bidirectional"))
      (node (ref "M12") (pin "1") (pinfunction "D_1") (pintype "bidirectional"))
      (node (ref "M12") (pin "2") (pinfunction "D_2") (pintype "bidirectional"))
      (node (ref "M12") (pin "5") (pinfunction "D_5") (pintype "bidirectional"))
      (node (ref "M12") (pin "6") (pinfunction "D_6") (pintype "bidirectional"))
      (node (ref "M12") (pin "7") (pinfunction "D_7") (pintype "bidirectional"))
      (node (ref "R270") (pin "2") (pinfunction "2_2") (pintype "bidirectional"))
    )
    (net (code "783") (name "SENSE2_9") (class "Default")
      (node (ref "IC16") (pin "12") (pinfunction "SENSE2-_12") (pintype "bidirectional"))
      (node (ref "M14") (pin "1") (pinfunction "D_1") (pintype "bidirectional"))
      (node (ref "M14") (pin "2") (pinfunction "D_2") (pintype "bidirectional"))
      (node (ref "M14") (pin "5") (pinfunction "D_5") (pintype "bidirectional"))
      (node (ref "M14") (pin "6") (pinfunction "D_6") (pintype "bidirectional"))
      (node (ref "M14") (pin "7") (pinfunction "D_7") (pintype "bidirectional"))
      (node (ref "R291") (pin "2") (pinfunction "2_2") (pintype "bidirectional"))
    )
    (net (code "784") (name "SENSE2_10") (class "Default")
      (node (ref "IC17") (pin "12") (pinfunction "SENSE2-_12") (pintype "bidirectional"))
      (node (ref "M16") (pin "1") (pinfunction "D_1") (pintype "bidirectional"))
      (node (ref "M16") (pin "2") (pinfunction "D_2") (pintype "bidirectional"))
      (node (ref "M16") (pin "5") (pinfunction "D_5") (pintype "bidirectional"))
      (node (ref "M16") (pin "6") (pinfunction "D_6") (pintype "bidirectional"))
      (node (ref "M16") (pin "7") (pinfunction "D_7") (pintype "bidirectional"))
      (node (ref "R312") (pin "2") (pinfunction "2_2") (pintype "bidirectional"))
    )
    (net (code "785") (name "SENSE2_11") (class "Default")
      (node (ref "IC22") (pin "12") (pinfunction "SENSE2-_12") (pintype "bidirectional"))
      (node (ref "M26") (pin "1") (pinfunction "D_1") (pintype "bidirectional"))
      (node (ref "M26") (pin "2") (pinfunction "D_2") (pintype "bidirectional"))
      (node (ref "M26") (pin "5") (pinfunction "D_5") (pintype "bidirectional"))
      (node (ref "M26") (pin "6") (pinfunction "D_6") (pintype "bidirectional"))
      (node (ref "M26") (pin "7") (pinfunction "D_7") (pintype "bidirectional"))
      (node (ref "R417") (pin "2") (pinfunction "2_2") (pintype "bidirectional"))
    )
    (net (code "786") (name "SENSE2_12") (class "Default")
      (node (ref "IC23") (pin "12") (pinfunction "SENSE2-_12") (pintype "bidirectional"))
      (node (ref "M28") (pin "1") (pinfunction "D_1") (pintype "bidirectional"))
      (node (ref "M28") (pin "2") (pinfunction "D_2") (pintype "bidirectional"))
      (node (ref "M28") (pin "5") (pinfunction "D_5") (pintype "bidirectional"))
      (node (ref "M28") (pin "6") (pinfunction "D_6") (pintype "bidirectional"))
      (node (ref "M28") (pin "7") (pinfunction "D_7") (pintype "bidirectional"))
      (node (ref "R438") (pin "2") (pinfunction "2_2") (pintype "bidirectional"))
    )
    (net (code "787") (name "SOURCE1_") (class "Default")
      (node (ref "IC4") (pin "27") (pinfunction "SOURCE1_27") (pintype "bidirectional"))
      (node (ref "J5") (pin "03") (pinfunction "03_03") (pintype "passive"))
      (node (ref "M1") (pin "4") (pinfunction "S_4") (pintype "bidirectional"))
      (node (ref "M1") (pin "8") (pinfunction "S_8") (pintype "bidirectional"))
      (node (ref "R100") (pin "2") (pinfunction "2_2") (pintype "bidirectional"))
      (node (ref "R95") (pin "1") (pinfunction "1_1") (pintype "bidirectional"))
    )
    (net (code "788") (name "SOURCE1_0") (class "Default")
      (node (ref "IC11") (pin "27") (pinfunction "SOURCE1_27") (pintype "bidirectional"))
      (node (ref "J5") (pin "13") (pinfunction "13_13") (pintype "passive"))
      (node (ref "M3") (pin "4") (pinfunction "S_4") (pintype "bidirectional"))
      (node (ref "M3") (pin "8") (pinfunction "S_8") (pintype "bidirectional"))
      (node (ref "R142") (pin "1") (pinfunction "1_1") (pintype "bidirectional"))
      (node (ref "R146") (pin "2") (pinfunction "2_2") (pintype "bidirectional"))
    )
    (net (code "789") (name "SOURCE1_1") (class "Default")
      (node (ref "IC20") (pin "27") (pinfunction "SOURCE1_27") (pintype "bidirectional"))
      (node (ref "J5") (pin "23") (pinfunction "23_23") (pintype "passive"))
      (node (ref "M21") (pin "4") (pinfunction "S_4") (pintype "bidirectional"))
      (node (ref "M21") (pin "8") (pinfunction "S_8") (pintype "bidirectional"))
      (node (ref "R367") (pin "1") (pinfunction "1_1") (pintype "bidirectional"))
      (node (ref "R371") (pin "2") (pinfunction "2_2") (pintype "bidirectional"))
    )
    (net (code "790") (name "SOURCE1_2") (class "Default")
      (node (ref "IC21") (pin "27") (pinfunction "SOURCE1_27") (pintype "bidirectional"))
      (node (ref "J5") (pin "33") (pinfunction "33_33") (pintype "passive"))
      (node (ref "M23") (pin "4") (pinfunction "S_4") (pintype "bidirectional"))
      (node (ref "M23") (pin "8") (pinfunction "S_8") (pintype "bidirectional"))
      (node (ref "R388") (pin "1") (pinfunction "1_1") (pintype "bidirectional"))
      (node (ref "R392") (pin "2") (pinfunction "2_2") (pintype "bidirectional"))
    )
    (net (code "791") (name "SOURCE1_3") (class "Default")
      (node (ref "IC12") (pin "27") (pinfunction "SOURCE1_27") (pintype "bidirectional"))
      (node (ref "J6") (pin "43") (pinfunction "43_43") (pintype "passive"))
      (node (ref "M5") (pin "4") (pinfunction "S_4") (pintype "bidirectional"))
      (node (ref "M5") (pin "8") (pinfunction "S_8") (pintype "bidirectional"))
      (node (ref "R180") (pin "1") (pinfunction "1_1") (pintype "bidirectional"))
      (node (ref "R184") (pin "2") (pinfunction "2_2") (pintype "bidirectional"))
    )
    (net (code "792") (name "SOURCE1_4") (class "Default")
      (node (ref "IC13") (pin "27") (pinfunction "SOURCE1_27") (pintype "bidirectional"))
      (node (ref "J6") (pin "53") (pinfunction "53_53") (pintype "passive"))
      (node (ref "M7") (pin "4") (pinfunction "S_4") (pintype "bidirectional"))
      (node (ref "M7") (pin "8") (pinfunction "S_8") (pintype "bidirectional"))
      (node (ref "R202") (pin "1") (pinfunction "1_1") (pintype "bidirectional"))
      (node (ref "R210") (pin "2") (pinfunction "2_2") (pintype "bidirectional"))
    )
    (net (code "793") (name "SOURCE1_5") (class "Default")
      (node (ref "IC18") (pin "27") (pinfunction "SOURCE1_27") (pintype "bidirectional"))
      (node (ref "J6") (pin "63") (pinfunction "63_63") (pintype "passive"))
      (node (ref "M17") (pin "4") (pinfunction "S_4") (pintype "bidirectional"))
      (node (ref "M17") (pin "8") (pinfunction "S_8") (pintype "bidirectional"))
      (node (ref "R325") (pin "1") (pinfunction "1_1") (pintype "bidirectional"))
      (node (ref "R329") (pin "2") (pinfunction "2_2") (pintype "bidirectional"))
    )
    (net (code "794") (name "SOURCE1_6") (class "Default")
      (node (ref "IC19") (pin "27") (pinfunction "SOURCE1_27") (pintype "bidirectional"))
      (node (ref "J6") (pin "73") (pinfunction "73_73") (pintype "passive"))
      (node (ref "M19") (pin "4") (pinfunction "S_4") (pintype "bidirectional"))
      (node (ref "M19") (pin "8") (pinfunction "S_8") (pintype "bidirectional"))
      (node (ref "R346") (pin "1") (pinfunction "1_1") (pintype "bidirectional"))
      (node (ref "R350") (pin "2") (pinfunction "2_2") (pintype "bidirectional"))
    )
    (net (code "795") (name "SOURCE1_7") (class "Default")
      (node (ref "IC14") (pin "27") (pinfunction "SOURCE1_27") (pintype "bidirectional"))
      (node (ref "J6") (pin "03") (pinfunction "03_03") (pintype "passive"))
      (node (ref "M9") (pin "4") (pinfunction "S_4") (pintype "bidirectional"))
      (node (ref "M9") (pin "8") (pinfunction "S_8") (pintype "bidirectional"))
      (node (ref "R241") (pin "1") (pinfunction "1_1") (pintype "bidirectional"))
      (node (ref "R245") (pin "2") (pinfunction "2_2") (pintype "bidirectional"))
    )
    (net (code "796") (name "SOURCE1_8") (class "Default")
      (node (ref "IC15") (pin "27") (pinfunction "SOURCE1_27") (pintype "bidirectional"))
      (node (ref "J6") (pin "13") (pinfunction "13_13") (pintype "passive"))
      (node (ref "M11") (pin "4") (pinfunction "S_4") (pintype "bidirectional"))
      (node (ref "M11") (pin "8") (pinfunction "S_8") (pintype "bidirectional"))
      (node (ref "R262") (pin "1") (pinfunction "1_1") (pintype "bidirectional"))
      (node (ref "R266") (pin "2") (pinfunction "2_2") (pintype "bidirectional"))
    )
    (net (code "797") (name "SOURCE1_9") (class "Default")
      (node (ref "IC16") (pin "27") (pinfunction "SOURCE1_27") (pintype "bidirectional"))
      (node (ref "J6") (pin "23") (pinfunction "23_23") (pintype "passive"))
      (node (ref "M13") (pin "4") (pinfunction "S_4") (pintype "bidirectional"))
      (node (ref "M13") (pin "8") (pinfunction "S_8") (pintype "bidirectional"))
      (node (ref "R283") (pin "1") (pinfunction "1_1") (pintype "bidirectional"))
      (node (ref "R287") (pin "2") (pinfunction "2_2") (pintype "bidirectional"))
    )
    (net (code "798") (name "SOURCE1_10") (class "Default")
      (node (ref "IC17") (pin "27") (pinfunction "SOURCE1_27") (pintype "bidirectional"))
      (node (ref "J5") (pin "57") (pinfunction "57_57") (pintype "passive"))
      (node (ref "M15") (pin "4") (pinfunction "S_4") (pintype "bidirectional"))
      (node (ref "M15") (pin "8") (pinfunction "S_8") (pintype "bidirectional"))
      (node (ref "R304") (pin "1") (pinfunction "1_1") (pintype "bidirectional"))
      (node (ref "R308") (pin "2") (pinfunction "2_2") (pintype "bidirectional"))
    )
    (net (code "799") (name "SOURCE1_11") (class "Default")
      (node (ref "IC22") (pin "27") (pinfunction "SOURCE1_27") (pintype "bidirectional"))
      (node (ref "J5") (pin "65") (pinfunction "65_65") (pintype "passive"))
      (node (ref "M25") (pin "4") (pinfunction "S_4") (pintype "bidirectional"))
      (node (ref "M25") (pin "8") (pinfunction "S_8") (pintype "bidirectional"))
      (node (ref "R409") (pin "1") (pinfunction "1_1") (pintype "bidirectional"))
      (node (ref "R413") (pin "2") (pinfunction "2_2") (pintype "bidirectional"))
    )
    (net (code "800") (name "SOURCE1_12") (class "Default")
      (node (ref "IC23") (pin "27") (pinfunction "SOURCE1_27") (pintype "bidirectional"))
      (node (ref "J5") (pin "73") (pinfunction "73_73") (pintype "passive"))
      (node (ref "M27") (pin "4") (pinfunction "S_4") (pintype "bidirectional"))
      (node (ref "M27") (pin "8") (pinfunction "S_8") (pintype "bidirectional"))
      (node (ref "R430") (pin "1") (pinfunction "1_1") (pintype "bidirectional"))
      (node (ref "R434") (pin "2") (pinfunction "2_2") (pintype "bidirectional"))
    )
    (net (code "801") (name "SOURCE2_") (class "Default")
      (node (ref "IC4") (pin "14") (pinfunction "SOURCE2_14") (pintype "bidirectional"))
      (node (ref "J5") (pin "05") (pinfunction "05_05") (pintype "passive"))
      (node (ref "M2") (pin "4") (pinfunction "S_4") (pintype "bidirectional"))
      (node (ref "M2") (pin "8") (pinfunction "S_8") (pintype "bidirectional"))
      (node (ref "R132") (pin "1") (pinfunction "1_1") (pintype "bidirectional"))
      (node (ref "R135") (pin "2") (pinfunction "2_2") (pintype "bidirectional"))
    )
    (net (code "802") (name "SOURCE2_0") (class "Default")
      (node (ref "IC11") (pin "14") (pinfunction "SOURCE2_14") (pintype "bidirectional"))
      (node (ref "J5") (pin "15") (pinfunction "15_15") (pintype "passive"))
      (node (ref "M4") (pin "4") (pinfunction "S_4") (pintype "bidirectional"))
      (node (ref "M4") (pin "8") (pinfunction "S_8") (pintype "bidirectional"))
      (node (ref "R170") (pin "1") (pinfunction "1_1") (pintype "bidirectional"))
      (node (ref "R173") (pin "2") (pinfunction "2_2") (pintype "bidirectional"))
    )
    (net (code "803") (name "SOURCE2_1") (class "Default")
      (node (ref "IC20") (pin "14") (pinfunction "SOURCE2_14") (pintype "bidirectional"))
      (node (ref "J5") (pin "25") (pinfunction "25_25") (pintype "passive"))
      (node (ref "M22") (pin "4") (pinfunction "S_4") (pintype "bidirectional"))
      (node (ref "M22") (pin "8") (pinfunction "S_8") (pintype "bidirectional"))
      (node (ref "R378") (pin "1") (pinfunction "1_1") (pintype "bidirectional"))
      (node (ref "R381") (pin "2") (pinfunction "2_2") (pintype "bidirectional"))
    )
    (net (code "804") (name "SOURCE2_2") (class "Default")
      (node (ref "IC21") (pin "14") (pinfunction "SOURCE2_14") (pintype "bidirectional"))
      (node (ref "J5") (pin "35") (pinfunction "35_35") (pintype "passive"))
      (node (ref "M24") (pin "4") (pinfunction "S_4") (pintype "bidirectional"))
      (node (ref "M24") (pin "8") (pinfunction "S_8") (pintype "bidirectional"))
      (node (ref "R399") (pin "1") (pinfunction "1_1") (pintype "bidirectional"))
      (node (ref "R402") (pin "2") (pinfunction "2_2") (pintype "bidirectional"))
    )
    (net (code "805") (name "SOURCE2_3") (class "Default")
      (node (ref "IC12") (pin "14") (pinfunction "SOURCE2_14") (pintype "bidirectional"))
      (node (ref "J6") (pin "45") (pinfunction "45_45") (pintype "passive"))
      (node (ref "M6") (pin "4") (pinfunction "S_4") (pintype "bidirectional"))
      (node (ref "M6") (pin "8") (pinfunction "S_8") (pintype "bidirectional"))
      (node (ref "R191") (pin "1") (pinfunction "1_1") (pintype "bidirectional"))
      (node (ref "R194") (pin "2") (pinfunction "2_2") (pintype "bidirectional"))
    )
    (net (code "806") (name "SOURCE2_4") (class "Default")
      (node (ref "IC13") (pin "14") (pinfunction "SOURCE2_14") (pintype "bidirectional"))
      (node (ref "J6") (pin "55") (pinfunction "55_55") (pintype "passive"))
      (node (ref "M8") (pin "4") (pinfunction "S_4") (pintype "bidirectional"))
      (node (ref "M8") (pin "8") (pinfunction "S_8") (pintype "bidirectional"))
      (node (ref "R218") (pin "1") (pinfunction "1_1") (pintype "bidirectional"))
      (node (ref "R222") (pin "2") (pinfunction "2_2") (pintype "bidirectional"))
    )
    (net (code "807") (name "SOURCE2_5") (class "Default")
      (node (ref "IC18") (pin "14") (pinfunction "SOURCE2_14") (pintype "bidirectional"))
      (node (ref "J6") (pin "65") (pinfunction "65_65") (pintype "passive"))
      (node (ref "M18") (pin "4") (pinfunction "S_4") (pintype "bidirectional"))
      (node (ref "M18") (pin "8") (pinfunction "S_8") (pintype "bidirectional"))
      (node (ref "R336") (pin "1") (pinfunction "1_1") (pintype "bidirectional"))
      (node (ref "R339") (pin "2") (pinfunction "2_2") (pintype "bidirectional"))
    )
    (net (code "808") (name "SOURCE2_6") (class "Default")
      (node (ref "IC19") (pin "14") (pinfunction "SOURCE2_14") (pintype "bidirectional"))
      (node (ref "J6") (pin "75") (pinfunction "75_75") (pintype "passive"))
      (node (ref "M20") (pin "4") (pinfunction "S_4") (pintype "bidirectional"))
      (node (ref "M20") (pin "8") (pinfunction "S_8") (pintype "bidirectional"))
      (node (ref "R357") (pin "1") (pinfunction "1_1") (pintype "bidirectional"))
      (node (ref "R360") (pin "2") (pinfunction "2_2") (pintype "bidirectional"))
    )
    (net (code "809") (name "SOURCE2_7") (class "Default")
      (node (ref "IC14") (pin "14") (pinfunction "SOURCE2_14") (pintype "bidirectional"))
      (node (ref "J6") (pin "05") (pinfunction "05_05") (pintype "passive"))
      (node (ref "M10") (pin "4") (pinfunction "S_4") (pintype "bidirectional"))
      (node (ref "M10") (pin "8") (pinfunction "S_8") (pintype "bidirectional"))
      (node (ref "R252") (pin "1") (pinfunction "1_1") (pintype "bidirectional"))
      (node (ref "R255") (pin "2") (pinfunction "2_2") (pintype "bidirectional"))
    )
    (net (code "810") (name "SOURCE2_8") (class "Default")
      (node (ref "IC15") (pin "14") (pinfunction "SOURCE2_14") (pintype "bidirectional"))
      (node (ref "J6") (pin "15") (pinfunction "15_15") (pintype "passive"))
      (node (ref "M12") (pin "4") (pinfunction "S_4") (pintype "bidirectional"))
      (node (ref "M12") (pin "8") (pinfunction "S_8") (pintype "bidirectional"))
      (node (ref "R273") (pin "1") (pinfunction "1_1") (pintype "bidirectional"))
      (node (ref "R276") (pin "2") (pinfunction "2_2") (pintype "bidirectional"))
    )
    (net (code "811") (name "SOURCE2_9") (class "Default")
      (node (ref "IC16") (pin "14") (pinfunction "SOURCE2_14") (pintype "bidirectional"))
      (node (ref "J6") (pin "25") (pinfunction "25_25") (pintype "passive"))
      (node (ref "M14") (pin "4") (pinfunction "S_4") (pintype "bidirectional"))
      (node (ref "M14") (pin "8") (pinfunction "S_8") (pintype "bidirectional"))
      (node (ref "R294") (pin "1") (pinfunction "1_1") (pintype "bidirectional"))
      (node (ref "R297") (pin "2") (pinfunction "2_2") (pintype "bidirectional"))
    )
    (net (code "812") (name "SOURCE2_10") (class "Default")
      (node (ref "IC17") (pin "14") (pinfunction "SOURCE2_14") (pintype "bidirectional"))
      (node (ref "J5") (pin "59") (pinfunction "59_59") (pintype "passive"))
      (node (ref "M16") (pin "4") (pinfunction "S_4") (pintype "bidirectional"))
      (node (ref "M16") (pin "8") (pinfunction "S_8") (pintype "bidirectional"))
      (node (ref "R315") (pin "1") (pinfunction "1_1") (pintype "bidirectional"))
      (node (ref "R318") (pin "2") (pinfunction "2_2") (pintype "bidirectional"))
    )
    (net (code "813") (name "SOURCE2_11") (class "Default")
      (node (ref "IC22") (pin "14") (pinfunction "SOURCE2_14") (pintype "bidirectional"))
      (node (ref "J5") (pin "67") (pinfunction "67_67") (pintype "passive"))
      (node (ref "M26") (pin "4") (pinfunction "S_4") (pintype "bidirectional"))
      (node (ref "M26") (pin "8") (pinfunction "S_8") (pintype "bidirectional"))
      (node (ref "R420") (pin "1") (pinfunction "1_1") (pintype "bidirectional"))
      (node (ref "R423") (pin "2") (pinfunction "2_2") (pintype "bidirectional"))
    )
    (net (code "814") (name "SOURCE2_12") (class "Default")
      (node (ref "IC23") (pin "14") (pinfunction "SOURCE2_14") (pintype "bidirectional"))
      (node (ref "J5") (pin "75") (pinfunction "75_75") (pintype "passive"))
      (node (ref "M28") (pin "4") (pinfunction "S_4") (pintype "bidirectional"))
      (node (ref "M28") (pin "8") (pinfunction "S_8") (pintype "bidirectional"))
      (node (ref "R441") (pin "1") (pinfunction "1_1") (pintype "bidirectional"))
      (node (ref "R444") (pin "2") (pinfunction "2_2") (pintype "bidirectional"))
    )
    (net (code "815") (name "TEMP1") (class "Default")
      (node (ref "IC27") (pin "3") (pinfunction "IN+_3") (pintype "bidirectional"))
      (node (ref "R471") (pin "2") (pinfunction "2_2") (pintype "bidirectional"))
      (node (ref "U$1") (pin "1") (pinfunction "P$1_1") (pintype "bidirectional"))
    )
    (net (code "816") (name "TEMP2") (class "Default")
      (node (ref "IC28") (pin "3") (pinfunction "IN+_3") (pintype "bidirectional"))
      (node (ref "R499") (pin "2") (pinfunction "2_2") (pintype "bidirectional"))
      (node (ref "U$2") (pin "1") (pinfunction "P$1_1") (pintype "bidirectional"))
    )
    (net (code "817") (name "TEMP3") (class "Default")
      (node (ref "IC29") (pin "3") (pinfunction "IN+_3") (pintype "bidirectional"))
      (node (ref "R500") (pin "2") (pinfunction "2_2") (pintype "bidirectional"))
      (node (ref "U$3") (pin "1") (pinfunction "P$1_1") (pintype "bidirectional"))
    )
    (net (code "818") (name "TEMP4") (class "Default")
      (node (ref "IC30") (pin "3") (pinfunction "IN+_3") (pintype "bidirectional"))
      (node (ref "R501") (pin "2") (pinfunction "2_2") (pintype "bidirectional"))
      (node (ref "U$4") (pin "1") (pinfunction "P$1_1") (pintype "bidirectional"))
    )
    (net (code "819") (name "TEMP_FB_1") (class "Default")
      (node (ref "IC27") (pin "4") (pinfunction "IN-_4") (pintype "bidirectional"))
      (node (ref "R503") (pin "1") (pinfunction "1_1") (pintype "bidirectional"))
      (node (ref "R504") (pin "1") (pinfunction "1_1") (pintype "bidirectional"))
    )
    (net (code "820") (name "TEMP_FB_2") (class "Default")
      (node (ref "IC28") (pin "4") (pinfunction "IN-_4") (pintype "bidirectional"))
      (node (ref "R502") (pin "1") (pinfunction "1_1") (pintype "bidirectional"))
      (node (ref "R505") (pin "1") (pinfunction "1_1") (pintype "bidirectional"))
    )
    (net (code "821") (name "TEMP_FB_3") (class "Default")
      (node (ref "IC29") (pin "4") (pinfunction "IN-_4") (pintype "bidirectional"))
      (node (ref "R506") (pin "1") (pinfunction "1_1") (pintype "bidirectional"))
      (node (ref "R507") (pin "1") (pinfunction "1_1") (pintype "bidirectional"))
    )
    (net (code "822") (name "TEMP_FB_4") (class "Default")
      (node (ref "IC30") (pin "4") (pinfunction "IN-_4") (pintype "bidirectional"))
      (node (ref "R508") (pin "1") (pinfunction "1_1") (pintype "bidirectional"))
      (node (ref "R509") (pin "1") (pinfunction "1_1") (pintype "bidirectional"))
    )
    (net (code "823") (name "THERMOCOUPLE_MISO") (class "Default")
      (node (ref "J4") (pin "34") (pinfunction "34_34") (pintype "passive"))
      (node (ref "R521") (pin "2") (pinfunction "2_2") (pintype "bidirectional"))
      (node (ref "TEMP_MISO") (pin "TP") (pinfunction "TP_TP") (pintype "bidirectional"))
    )
    (net (code "824") (name "THERMOCOUPLE_SCLK") (class "Default")
      (node (ref "J4") (pin "32") (pinfunction "32_32") (pintype "passive"))
      (node (ref "R520") (pin "2") (pinfunction "2_2") (pintype "bidirectional"))
      (node (ref "TEMP_SCLK") (pin "TP") (pinfunction "TP_TP") (pintype "bidirectional"))
    )
    (net (code "825") (name "USART3_TX") (class "Default")
      (node (ref "UC1") (pin "PD8") (pinfunction "PD8_PD8") (pintype "passive"))
    )
    (net (code "826") (name "USART4_RX") (class "Default")
      (node (ref "UC1") (pin "PD9") (pinfunction "PD9_PD9") (pintype "passive"))
    )
    (net (code "827") (name "USB_FS_OVCR") (class "Default")
      (node (ref "UC1") (pin "PG7") (pinfunction "PG7_PG7") (pintype "passive"))
    )
    (net (code "828") (name "USB_FS_PWR_EN") (class "Default")
      (node (ref "UC1") (pin "PD10") (pinfunction "PD10_PD10") (pintype "passive"))
    )
    (net (code "829") (name "UV1_") (class "Default")
      (node (ref "IC4") (pin "31") (pinfunction "UV1_31") (pintype "bidirectional"))
      (node (ref "R89") (pin "1") (pinfunction "1_1") (pintype "bidirectional"))
      (node (ref "R90") (pin "1") (pinfunction "1_1") (pintype "bidirectional"))
    )
    (net (code "830") (name "UV1_0") (class "Default")
      (node (ref "IC11") (pin "31") (pinfunction "UV1_31") (pintype "bidirectional"))
      (node (ref "R136") (pin "1") (pinfunction "1_1") (pintype "bidirectional"))
      (node (ref "R137") (pin "1") (pinfunction "1_1") (pintype "bidirectional"))
    )
    (net (code "831") (name "UV1_1") (class "Default")
      (node (ref "IC20") (pin "31") (pinfunction "UV1_31") (pintype "bidirectional"))
      (node (ref "R361") (pin "1") (pinfunction "1_1") (pintype "bidirectional"))
      (node (ref "R362") (pin "1") (pinfunction "1_1") (pintype "bidirectional"))
    )
    (net (code "832") (name "UV1_2") (class "Default")
      (node (ref "IC21") (pin "31") (pinfunction "UV1_31") (pintype "bidirectional"))
      (node (ref "R382") (pin "1") (pinfunction "1_1") (pintype "bidirectional"))
      (node (ref "R383") (pin "1") (pinfunction "1_1") (pintype "bidirectional"))
    )
    (net (code "833") (name "UV1_3") (class "Default")
      (node (ref "IC12") (pin "31") (pinfunction "UV1_31") (pintype "bidirectional"))
      (node (ref "R174") (pin "1") (pinfunction "1_1") (pintype "bidirectional"))
      (node (ref "R175") (pin "1") (pinfunction "1_1") (pintype "bidirectional"))
    )
    (net (code "834") (name "UV1_4") (class "Default")
      (node (ref "IC13") (pin "31") (pinfunction "UV1_31") (pintype "bidirectional"))
      (node (ref "R195") (pin "1") (pinfunction "1_1") (pintype "bidirectional"))
      (node (ref "R196") (pin "1") (pinfunction "1_1") (pintype "bidirectional"))
    )
    (net (code "835") (name "UV1_5") (class "Default")
      (node (ref "IC18") (pin "31") (pinfunction "UV1_31") (pintype "bidirectional"))
      (node (ref "R319") (pin "1") (pinfunction "1_1") (pintype "bidirectional"))
      (node (ref "R320") (pin "1") (pinfunction "1_1") (pintype "bidirectional"))
    )
    (net (code "836") (name "UV1_6") (class "Default")
      (node (ref "IC19") (pin "31") (pinfunction "UV1_31") (pintype "bidirectional"))
      (node (ref "R340") (pin "1") (pinfunction "1_1") (pintype "bidirectional"))
      (node (ref "R341") (pin "1") (pinfunction "1_1") (pintype "bidirectional"))
    )
    (net (code "837") (name "UV1_7") (class "Default")
      (node (ref "IC14") (pin "31") (pinfunction "UV1_31") (pintype "bidirectional"))
      (node (ref "R223") (pin "1") (pinfunction "1_1") (pintype "bidirectional"))
      (node (ref "R224") (pin "1") (pinfunction "1_1") (pintype "bidirectional"))
    )
    (net (code "838") (name "UV1_8") (class "Default")
      (node (ref "IC15") (pin "31") (pinfunction "UV1_31") (pintype "bidirectional"))
      (node (ref "R256") (pin "1") (pinfunction "1_1") (pintype "bidirectional"))
      (node (ref "R257") (pin "1") (pinfunction "1_1") (pintype "bidirectional"))
    )
    (net (code "839") (name "UV1_9") (class "Default")
      (node (ref "IC16") (pin "31") (pinfunction "UV1_31") (pintype "bidirectional"))
      (node (ref "R277") (pin "1") (pinfunction "1_1") (pintype "bidirectional"))
      (node (ref "R278") (pin "1") (pinfunction "1_1") (pintype "bidirectional"))
    )
    (net (code "840") (name "UV1_10") (class "Default")
      (node (ref "IC17") (pin "31") (pinfunction "UV1_31") (pintype "bidirectional"))
      (node (ref "R298") (pin "1") (pinfunction "1_1") (pintype "bidirectional"))
      (node (ref "R299") (pin "1") (pinfunction "1_1") (pintype "bidirectional"))
    )
    (net (code "841") (name "UV1_11") (class "Default")
      (node (ref "IC22") (pin "31") (pinfunction "UV1_31") (pintype "bidirectional"))
      (node (ref "R403") (pin "1") (pinfunction "1_1") (pintype "bidirectional"))
      (node (ref "R404") (pin "1") (pinfunction "1_1") (pintype "bidirectional"))
    )
    (net (code "842") (name "UV1_12") (class "Default")
      (node (ref "IC23") (pin "31") (pinfunction "UV1_31") (pintype "bidirectional"))
      (node (ref "R424") (pin "1") (pinfunction "1_1") (pintype "bidirectional"))
      (node (ref "R425") (pin "1") (pinfunction "1_1") (pintype "bidirectional"))
    )
    (net (code "843") (name "UV2_") (class "Default")
      (node (ref "IC4") (pin "10") (pinfunction "UV2_10") (pintype "bidirectional"))
      (node (ref "R101") (pin "1") (pinfunction "1_1") (pintype "bidirectional"))
      (node (ref "R127") (pin "1") (pinfunction "1_1") (pintype "bidirectional"))
    )
    (net (code "844") (name "UV2_0") (class "Default")
      (node (ref "IC11") (pin "10") (pinfunction "UV2_10") (pintype "bidirectional"))
      (node (ref "R164") (pin "1") (pinfunction "1_1") (pintype "bidirectional"))
      (node (ref "R165") (pin "1") (pinfunction "1_1") (pintype "bidirectional"))
    )
    (net (code "845") (name "UV2_1") (class "Default")
      (node (ref "IC20") (pin "10") (pinfunction "UV2_10") (pintype "bidirectional"))
      (node (ref "R372") (pin "1") (pinfunction "1_1") (pintype "bidirectional"))
      (node (ref "R373") (pin "1") (pinfunction "1_1") (pintype "bidirectional"))
    )
    (net (code "846") (name "UV2_2") (class "Default")
      (node (ref "IC21") (pin "10") (pinfunction "UV2_10") (pintype "bidirectional"))
      (node (ref "R393") (pin "1") (pinfunction "1_1") (pintype "bidirectional"))
      (node (ref "R394") (pin "1") (pinfunction "1_1") (pintype "bidirectional"))
    )
    (net (code "847") (name "UV2_3") (class "Default")
      (node (ref "IC12") (pin "10") (pinfunction "UV2_10") (pintype "bidirectional"))
      (node (ref "R185") (pin "1") (pinfunction "1_1") (pintype "bidirectional"))
      (node (ref "R186") (pin "1") (pinfunction "1_1") (pintype "bidirectional"))
    )
    (net (code "848") (name "UV2_4") (class "Default")
      (node (ref "IC13") (pin "10") (pinfunction "UV2_10") (pintype "bidirectional"))
      (node (ref "R212") (pin "1") (pinfunction "1_1") (pintype "bidirectional"))
      (node (ref "R213") (pin "1") (pinfunction "1_1") (pintype "bidirectional"))
    )
    (net (code "849") (name "UV2_5") (class "Default")
      (node (ref "IC18") (pin "10") (pinfunction "UV2_10") (pintype "bidirectional"))
      (node (ref "R330") (pin "1") (pinfunction "1_1") (pintype "bidirectional"))
      (node (ref "R331") (pin "1") (pinfunction "1_1") (pintype "bidirectional"))
    )
    (net (code "850") (name "UV2_6") (class "Default")
      (node (ref "IC19") (pin "10") (pinfunction "UV2_10") (pintype "bidirectional"))
      (node (ref "R351") (pin "1") (pinfunction "1_1") (pintype "bidirectional"))
      (node (ref "R352") (pin "1") (pinfunction "1_1") (pintype "bidirectional"))
    )
    (net (code "851") (name "UV2_7") (class "Default")
      (node (ref "IC14") (pin "10") (pinfunction "UV2_10") (pintype "bidirectional"))
      (node (ref "R246") (pin "1") (pinfunction "1_1") (pintype "bidirectional"))
      (node (ref "R247") (pin "1") (pinfunction "1_1") (pintype "bidirectional"))
    )
    (net (code "852") (name "UV2_8") (class "Default")
      (node (ref "IC15") (pin "10") (pinfunction "UV2_10") (pintype "bidirectional"))
      (node (ref "R267") (pin "1") (pinfunction "1_1") (pintype "bidirectional"))
      (node (ref "R268") (pin "1") (pinfunction "1_1") (pintype "bidirectional"))
    )
    (net (code "853") (name "UV2_9") (class "Default")
      (node (ref "IC16") (pin "10") (pinfunction "UV2_10") (pintype "bidirectional"))
      (node (ref "R288") (pin "1") (pinfunction "1_1") (pintype "bidirectional"))
      (node (ref "R289") (pin "1") (pinfunction "1_1") (pintype "bidirectional"))
    )
    (net (code "854") (name "UV2_10") (class "Default")
      (node (ref "IC17") (pin "10") (pinfunction "UV2_10") (pintype "bidirectional"))
      (node (ref "R309") (pin "1") (pinfunction "1_1") (pintype "bidirectional"))
      (node (ref "R310") (pin "1") (pinfunction "1_1") (pintype "bidirectional"))
    )
    (net (code "855") (name "UV2_11") (class "Default")
      (node (ref "IC22") (pin "10") (pinfunction "UV2_10") (pintype "bidirectional"))
      (node (ref "R414") (pin "1") (pinfunction "1_1") (pintype "bidirectional"))
      (node (ref "R415") (pin "1") (pinfunction "1_1") (pintype "bidirectional"))
    )
    (net (code "856") (name "UV2_12") (class "Default")
      (node (ref "IC23") (pin "10") (pinfunction "UV2_10") (pintype "bidirectional"))
      (node (ref "R435") (pin "1") (pinfunction "1_1") (pintype "bidirectional"))
      (node (ref "R436") (pin "1") (pinfunction "1_1") (pintype "bidirectional"))
    )
    (net (code "857") (name "V+_1") (class "Default")
      (node (ref "R473") (pin "2") (pinfunction "2_2") (pintype "bidirectional"))
      (node (ref "R474") (pin "1") (pinfunction "1_1") (pintype "bidirectional"))
      (node (ref "R477") (pin "2") (pinfunction "2_2") (pintype "bidirectional"))
    )
    (net (code "858") (name "V+_2") (class "Default")
      (node (ref "R482") (pin "2") (pinfunction "2_2") (pintype "bidirectional"))
      (node (ref "R483") (pin "1") (pinfunction "1_1") (pintype "bidirectional"))
      (node (ref "R486") (pin "2") (pinfunction "2_2") (pintype "bidirectional"))
    )
    (net (code "859") (name "V+_3") (class "Default")
      (node (ref "R491") (pin "2") (pinfunction "2_2") (pintype "bidirectional"))
      (node (ref "R492") (pin "1") (pinfunction "1_1") (pintype "bidirectional"))
      (node (ref "R495") (pin "2") (pinfunction "2_2") (pintype "bidirectional"))
    )
    (net (code "860") (name "V-_1") (class "Default")
      (node (ref "R475") (pin "2") (pinfunction "2_2") (pintype "bidirectional"))
      (node (ref "R476") (pin "1") (pinfunction "1_1") (pintype "bidirectional"))
      (node (ref "R478") (pin "2") (pinfunction "2_2") (pintype "bidirectional"))
    )
    (net (code "861") (name "V-_2") (class "Default")
      (node (ref "R484") (pin "2") (pinfunction "2_2") (pintype "bidirectional"))
      (node (ref "R485") (pin "1") (pinfunction "1_1") (pintype "bidirectional"))
      (node (ref "R487") (pin "2") (pinfunction "2_2") (pintype "bidirectional"))
    )
    (net (code "862") (name "V-_3") (class "Default")
      (node (ref "R493") (pin "2") (pinfunction "2_2") (pintype "bidirectional"))
      (node (ref "R494") (pin "1") (pinfunction "1_1") (pintype "bidirectional"))
      (node (ref "R496") (pin "2") (pinfunction "2_2") (pintype "bidirectional"))
    )
    (net (code "863") (name "VBAT_NC") (class "Default")
      (node (ref "J9") (pin "07") (pinfunction "07_07") (pintype "passive"))
    )
    (net (code "864") (name "VIN1_P") (class "Default")
      (node (ref "IC36") (pin "1") (pinfunction "OUT_1") (pintype "bidirectional"))
      (node (ref "IC51") (pin "49") (pinfunction "AIN_1P_49") (pintype "input"))
      (node (ref "R154") (pin "1") (pinfunction "1_1") (pintype "bidirectional"))
    )
    (net (code "865") (name "VIN2_P") (class "Default")
      (node (ref "IC39") (pin "1") (pinfunction "OUT_1") (pintype "bidirectional"))
      (node (ref "IC51") (pin "51") (pinfunction "AIN_2P_51") (pintype "input"))
      (node (ref "R157") (pin "1") (pinfunction "1_1") (pintype "bidirectional"))
    )
    (net (code "866") (name "VIN3_P") (class "Default")
      (node (ref "IC41") (pin "1") (pinfunction "OUT_1") (pintype "bidirectional"))
      (node (ref "IC51") (pin "53") (pinfunction "AIN_3P_53") (pintype "input"))
      (node (ref "R3") (pin "1") (pinfunction "1_1") (pintype "bidirectional"))
    )
    (net (code "867") (name "VIN4_P") (class "Default")
      (node (ref "IC43") (pin "1") (pinfunction "OUT_1") (pintype "bidirectional"))
      (node (ref "IC51") (pin "55") (pinfunction "AIN_4P_55") (pintype "input"))
      (node (ref "R7") (pin "1") (pinfunction "1_1") (pintype "bidirectional"))
    )
    (net (code "868") (name "VIN5_P") (class "Default")
      (node (ref "IC45") (pin "1") (pinfunction "OUT_1") (pintype "bidirectional"))
      (node (ref "IC51") (pin "57") (pinfunction "AIN_5P_57") (pintype "input"))
      (node (ref "R11") (pin "1") (pinfunction "1_1") (pintype "bidirectional"))
    )
    (net (code "869") (name "VIN6_P") (class "Default")
      (node (ref "IC47") (pin "1") (pinfunction "OUT_1") (pintype "bidirectional"))
      (node (ref "IC51") (pin "59") (pinfunction "AIN_6P_59") (pintype "input"))
      (node (ref "R15") (pin "1") (pinfunction "1_1") (pintype "bidirectional"))
    )
    (net (code "870") (name "VIN7_P") (class "Default")
      (node (ref "IC49") (pin "1") (pinfunction "OUT_1") (pintype "bidirectional"))
      (node (ref "IC51") (pin "61") (pinfunction "AIN_7P_61") (pintype "input"))
      (node (ref "R19") (pin "1") (pinfunction "1_1") (pintype "bidirectional"))
    )
    (net (code "871") (name "VIN8_P") (class "Default")
      (node (ref "IC51") (pin "63") (pinfunction "AIN_8P_63") (pintype "input"))
      (node (ref "IC53") (pin "1") (pinfunction "OUT_1") (pintype "bidirectional"))
      (node (ref "R23") (pin "1") (pinfunction "1_1") (pintype "bidirectional"))
    )
    (net (code "872") (name "VIN9_P") (class "Default")
      (node (ref "IC38") (pin "49") (pinfunction "AIN_1P_49") (pintype "input"))
      (node (ref "IC55") (pin "1") (pinfunction "OUT_1") (pintype "bidirectional"))
      (node (ref "R27") (pin "1") (pinfunction "1_1") (pintype "bidirectional"))
    )
    (net (code "873") (name "VIN10_P") (class "Default")
      (node (ref "IC38") (pin "51") (pinfunction "AIN_2P_51") (pintype "input"))
      (node (ref "IC57") (pin "1") (pinfunction "OUT_1") (pintype "bidirectional"))
      (node (ref "R31") (pin "1") (pinfunction "1_1") (pintype "bidirectional"))
    )
    (net (code "874") (name "VIN11_P") (class "Default")
      (node (ref "IC38") (pin "53") (pinfunction "AIN_3P_53") (pintype "input"))
      (node (ref "IC59") (pin "1") (pinfunction "OUT_1") (pintype "bidirectional"))
      (node (ref "R75") (pin "1") (pinfunction "1_1") (pintype "bidirectional"))
    )
    (net (code "875") (name "VIN12_P") (class "Default")
      (node (ref "IC38") (pin "55") (pinfunction "AIN_4P_55") (pintype "input"))
      (node (ref "IC61") (pin "1") (pinfunction "OUT_1") (pintype "bidirectional"))
      (node (ref "R79") (pin "1") (pinfunction "1_1") (pintype "bidirectional"))
    )
    (net (code "876") (name "VIN13_P") (class "Default")
      (node (ref "IC38") (pin "57") (pinfunction "AIN_5P_57") (pintype "input"))
      (node (ref "IC63") (pin "1") (pinfunction "OUT_1") (pintype "bidirectional"))
      (node (ref "R83") (pin "1") (pinfunction "1_1") (pintype "bidirectional"))
    )
    (net (code "877") (name "VIN14_P") (class "Default")
      (node (ref "IC38") (pin "59") (pinfunction "AIN_6P_59") (pintype "input"))
      (node (ref "IC65") (pin "1") (pinfunction "OUT_1") (pintype "bidirectional"))
      (node (ref "R87") (pin "1") (pinfunction "1_1") (pintype "bidirectional"))
    )
    (net (code "878") (name "VIN15_P") (class "Default")
      (node (ref "IC38") (pin "61") (pinfunction "AIN_7P_61") (pintype "input"))
      (node (ref "IC67") (pin "1") (pinfunction "OUT_1") (pintype "bidirectional"))
      (node (ref "R103") (pin "1") (pinfunction "1_1") (pintype "bidirectional"))
    )
    (net (code "879") (name "VIN16_P") (class "Default")
      (node (ref "IC38") (pin "63") (pinfunction "AIN_8P_63") (pintype "input"))
      (node (ref "IC69") (pin "1") (pinfunction "OUT_1") (pintype "bidirectional"))
      (node (ref "R107") (pin "1") (pinfunction "1_1") (pintype "bidirectional"))
    )
    (net (code "880") (name "unconnected-(IC4-ADR1-Pad6)") (class "Default")
      (node (ref "IC4") (pin "6") (pinfunction "ADR1_6") (pintype "bidirectional"))
    )
    (net (code "881") (name "unconnected-(IC11-ADR0-Pad5)") (class "Default")
      (node (ref "IC11") (pin "5") (pinfunction "ADR0_5") (pintype "bidirectional"))
    )
    (net (code "882") (name "unconnected-(IC14-ADR1-Pad6)") (class "Default")
      (node (ref "IC14") (pin "6") (pinfunction "ADR1_6") (pintype "bidirectional"))
    )
    (net (code "883") (name "unconnected-(IC14-ADR2-Pad7)") (class "Default")
      (node (ref "IC14") (pin "7") (pinfunction "ADR2_7") (pintype "bidirectional"))
    )
    (net (code "884") (name "unconnected-(IC15-ADR0-Pad5)") (class "Default")
      (node (ref "IC15") (pin "5") (pinfunction "ADR0_5") (pintype "bidirectional"))
    )
    (net (code "885") (name "unconnected-(IC15-ADR2-Pad7)") (class "Default")
      (node (ref "IC15") (pin "7") (pinfunction "ADR2_7") (pintype "bidirectional"))
    )
    (net (code "886") (name "unconnected-(IC16-ADR0-Pad5)") (class "Default")
      (node (ref "IC16") (pin "5") (pinfunction "ADR0_5") (pintype "bidirectional"))
    )
    (net (code "887") (name "unconnected-(IC16-ADR1-Pad6)") (class "Default")
      (node (ref "IC16") (pin "6") (pinfunction "ADR1_6") (pintype "bidirectional"))
    )
    (net (code "888") (name "unconnected-(IC16-ADR2-Pad7)") (class "Default")
      (node (ref "IC16") (pin "7") (pinfunction "ADR2_7") (pintype "bidirectional"))
    )
    (net (code "889") (name "unconnected-(IC17-ADR1-Pad6)") (class "Default")
      (node (ref "IC17") (pin "6") (pinfunction "ADR1_6") (pintype "bidirectional"))
    )
    (net (code "890") (name "unconnected-(IC17-ADR2-Pad7)") (class "Default")
      (node (ref "IC17") (pin "7") (pinfunction "ADR2_7") (pintype "bidirectional"))
    )
    (net (code "891") (name "unconnected-(IC18-ADR0-Pad5)") (class "Default")
      (node (ref "IC18") (pin "5") (pinfunction "ADR0_5") (pintype "bidirectional"))
    )
    (net (code "892") (name "unconnected-(IC20-ADR0-Pad5)") (class "Default")
      (node (ref "IC20") (pin "5") (pinfunction "ADR0_5") (pintype "bidirectional"))
    )
    (net (code "893") (name "unconnected-(IC20-ADR1-Pad6)") (class "Default")
      (node (ref "IC20") (pin "6") (pinfunction "ADR1_6") (pintype "bidirectional"))
    )
    (net (code "894") (name "unconnected-(IC21-ADR1-Pad6)") (class "Default")
      (node (ref "IC21") (pin "6") (pinfunction "ADR1_6") (pintype "bidirectional"))
    )
    (net (code "895") (name "unconnected-(IC22-ADR2-Pad7)") (class "Default")
      (node (ref "IC22") (pin "7") (pinfunction "ADR2_7") (pintype "bidirectional"))
    )
    (net (code "896") (name "unconnected-(IC23-ADR2-Pad7)") (class "Default")
      (node (ref "IC23") (pin "7") (pinfunction "ADR2_7") (pintype "bidirectional"))
    )
    (net (code "897") (name "unconnected-(IC31-DNC-PadC3)") (class "Default")
      (node (ref "IC31") (pin "C3") (pinfunction "DNC_C3") (pintype "bidirectional"))
    )
    (net (code "898") (name "unconnected-(IC31-NC_1-PadA9)") (class "Default")
      (node (ref "IC31") (pin "A9") (pinfunction "NC_1_A9") (pintype "bidirectional"))
    )
    (net (code "899") (name "unconnected-(IC31-NC_2-PadA10)") (class "Default")
      (node (ref "IC31") (pin "A10") (pinfunction "NC_2_A10") (pintype "bidirectional"))
    )
    (net (code "900") (name "unconnected-(IC31-NC_3-PadB1)") (class "Default")
      (node (ref "IC31") (pin "B1") (pinfunction "NC_3_B1") (pintype "bidirectional"))
    )
    (net (code "901") (name "unconnected-(IC31-NC_4-PadB2)") (class "Default")
      (node (ref "IC31") (pin "B2") (pinfunction "NC_4_B2") (pintype "bidirectional"))
    )
    (net (code "902") (name "unconnected-(IC31-NC_5-PadB7)") (class "Default")
      (node (ref "IC31") (pin "B7") (pinfunction "NC_5_B7") (pintype "bidirectional"))
    )
    (net (code "903") (name "unconnected-(IC31-NC_6-PadB8)") (class "Default")
      (node (ref "IC31") (pin "B8") (pinfunction "NC_6_B8") (pintype "bidirectional"))
    )
    (net (code "904") (name "unconnected-(IC31-NC_7-PadB9)") (class "Default")
      (node (ref "IC31") (pin "B9") (pinfunction "NC_7_B9") (pintype "bidirectional"))
    )
    (net (code "905") (name "unconnected-(IC31-NC_8-PadB10)") (class "Default")
      (node (ref "IC31") (pin "B10") (pinfunction "NC_8_B10") (pintype "bidirectional"))
    )
    (net (code "906") (name "unconnected-(IC31-NC_9-PadC1)") (class "Default")
      (node (ref "IC31") (pin "C1") (pinfunction "NC_9_C1") (pintype "bidirectional"))
    )
    (net (code "907") (name "unconnected-(IC31-NC_10-PadC4)") (class "Default")
      (node (ref "IC31") (pin "C4") (pinfunction "NC_10_C4") (pintype "bidirectional"))
    )
    (net (code "908") (name "unconnected-(IC31-NC_11-PadC5)") (class "Default")
      (node (ref "IC31") (pin "C5") (pinfunction "NC_11_C5") (pintype "bidirectional"))
    )
    (net (code "909") (name "unconnected-(IC31-NC_12-PadC8)") (class "Default")
      (node (ref "IC31") (pin "C8") (pinfunction "NC_12_C8") (pintype "bidirectional"))
    )
    (net (code "910") (name "unconnected-(IC31-NC_13-PadC9)") (class "Default")
      (node (ref "IC31") (pin "C9") (pinfunction "NC_13_C9") (pintype "bidirectional"))
    )
    (net (code "911") (name "unconnected-(IC31-NC_14-PadC10)") (class "Default")
      (node (ref "IC31") (pin "C10") (pinfunction "NC_14_C10") (pintype "bidirectional"))
    )
    (net (code "912") (name "unconnected-(IC31-NC_15-PadD1)") (class "Default")
      (node (ref "IC31") (pin "D1") (pinfunction "NC_15_D1") (pintype "bidirectional"))
    )
    (net (code "913") (name "unconnected-(IC31-NC_16-PadD2)") (class "Default")
      (node (ref "IC31") (pin "D2") (pinfunction "NC_16_D2") (pintype "bidirectional"))
    )
    (net (code "914") (name "unconnected-(IC31-NC_17-PadD4)") (class "Default")
      (node (ref "IC31") (pin "D4") (pinfunction "NC_17_D4") (pintype "bidirectional"))
    )
    (net (code "915") (name "unconnected-(IC31-NC_18-PadD5)") (class "Default")
      (node (ref "IC31") (pin "D5") (pinfunction "NC_18_D5") (pintype "bidirectional"))
    )
    (net (code "916") (name "unconnected-(IC31-NC_19-PadD7)") (class "Default")
      (node (ref "IC31") (pin "D7") (pinfunction "NC_19_D7") (pintype "bidirectional"))
    )
    (net (code "917") (name "unconnected-(IC31-NC_20-PadD8)") (class "Default")
      (node (ref "IC31") (pin "D8") (pinfunction "NC_20_D8") (pintype "bidirectional"))
    )
    (net (code "918") (name "unconnected-(IC31-NC_21-PadD9)") (class "Default")
      (node (ref "IC31") (pin "D9") (pinfunction "NC_21_D9") (pintype "bidirectional"))
    )
    (net (code "919") (name "unconnected-(IC31-NC_22-PadD10)") (class "Default")
      (node (ref "IC31") (pin "D10") (pinfunction "NC_22_D10") (pintype "bidirectional"))
    )
    (net (code "920") (name "unconnected-(IC31-NC_23-PadE1)") (class "Default")
      (node (ref "IC31") (pin "E1") (pinfunction "NC_23_E1") (pintype "bidirectional"))
    )
    (net (code "921") (name "unconnected-(IC31-NC_24-PadE4)") (class "Default")
      (node (ref "IC31") (pin "E4") (pinfunction "NC_24_E4") (pintype "bidirectional"))
    )
    (net (code "922") (name "unconnected-(IC31-NC_25-PadE5)") (class "Default")
      (node (ref "IC31") (pin "E5") (pinfunction "NC_25_E5") (pintype "bidirectional"))
    )
    (net (code "923") (name "unconnected-(IC31-NC_26-PadE8)") (class "Default")
      (node (ref "IC31") (pin "E8") (pinfunction "NC_26_E8") (pintype "bidirectional"))
    )
    (net (code "924") (name "unconnected-(IC31-NC_27-PadE9)") (class "Default")
      (node (ref "IC31") (pin "E9") (pinfunction "NC_27_E9") (pintype "bidirectional"))
    )
    (net (code "925") (name "unconnected-(IC31-NC_28-PadE10)") (class "Default")
      (node (ref "IC31") (pin "E10") (pinfunction "NC_28_E10") (pintype "bidirectional"))
    )
    (net (code "926") (name "unconnected-(IC31-NC_29-PadF2)") (class "Default")
      (node (ref "IC31") (pin "F2") (pinfunction "NC_29_F2") (pintype "bidirectional"))
    )
    (net (code "927") (name "unconnected-(IC31-NC_30-PadF4)") (class "Default")
      (node (ref "IC31") (pin "F4") (pinfunction "NC_30_F4") (pintype "bidirectional"))
    )
    (net (code "928") (name "unconnected-(IC31-NC_31-PadF7)") (class "Default")
      (node (ref "IC31") (pin "F7") (pinfunction "NC_31_F7") (pintype "bidirectional"))
    )
    (net (code "929") (name "unconnected-(IC31-NC_32-PadF9)") (class "Default")
      (node (ref "IC31") (pin "F9") (pinfunction "NC_32_F9") (pintype "bidirectional"))
    )
    (net (code "930") (name "unconnected-(IC31-NC_33-PadF10)") (class "Default")
      (node (ref "IC31") (pin "F10") (pinfunction "NC_33_F10") (pintype "bidirectional"))
    )
    (net (code "931") (name "unconnected-(IC31-NC_34-PadG4)") (class "Default")
      (node (ref "IC31") (pin "G4") (pinfunction "NC_34_G4") (pintype "bidirectional"))
    )
    (net (code "932") (name "unconnected-(IC31-NC_35-PadG5)") (class "Default")
      (node (ref "IC31") (pin "G5") (pinfunction "NC_35_G5") (pintype "bidirectional"))
    )
    (net (code "933") (name "unconnected-(IC31-NC_36-PadG8)") (class "Default")
      (node (ref "IC31") (pin "G8") (pinfunction "NC_36_G8") (pintype "bidirectional"))
    )
    (net (code "934") (name "unconnected-(IC31-NC_37-PadG9)") (class "Default")
      (node (ref "IC31") (pin "G9") (pinfunction "NC_37_G9") (pintype "bidirectional"))
    )
    (net (code "935") (name "unconnected-(IC31-NC_38-PadG10)") (class "Default")
      (node (ref "IC31") (pin "G10") (pinfunction "NC_38_G10") (pintype "bidirectional"))
    )
    (net (code "936") (name "unconnected-(IC31-NC_39-PadH2)") (class "Default")
      (node (ref "IC31") (pin "H2") (pinfunction "NC_39_H2") (pintype "bidirectional"))
    )
    (net (code "937") (name "unconnected-(IC31-NC_40-PadH4)") (class "Default")
      (node (ref "IC31") (pin "H4") (pinfunction "NC_40_H4") (pintype "bidirectional"))
    )
    (net (code "938") (name "unconnected-(IC31-NC_41-PadH5)") (class "Default")
      (node (ref "IC31") (pin "H5") (pinfunction "NC_41_H5") (pintype "bidirectional"))
    )
    (net (code "939") (name "unconnected-(IC31-NC_42-PadH7)") (class "Default")
      (node (ref "IC31") (pin "H7") (pinfunction "NC_42_H7") (pintype "bidirectional"))
    )
    (net (code "940") (name "unconnected-(IC31-NC_43-PadH9)") (class "Default")
      (node (ref "IC31") (pin "H9") (pinfunction "NC_43_H9") (pintype "bidirectional"))
    )
    (net (code "941") (name "unconnected-(IC31-NC_44-PadH10)") (class "Default")
      (node (ref "IC31") (pin "H10") (pinfunction "NC_44_H10") (pintype "bidirectional"))
    )
    (net (code "942") (name "unconnected-(IC31-NC_45-PadJ1)") (class "Default")
      (node (ref "IC31") (pin "J1") (pinfunction "NC_45_J1") (pintype "bidirectional"))
    )
    (net (code "943") (name "unconnected-(IC31-NC_46-PadJ8)") (class "Default")
      (node (ref "IC31") (pin "J8") (pinfunction "NC_46_J8") (pintype "bidirectional"))
    )
    (net (code "944") (name "unconnected-(IC31-NC_47-PadJ9)") (class "Default")
      (node (ref "IC31") (pin "J9") (pinfunction "NC_47_J9") (pintype "bidirectional"))
    )
    (net (code "945") (name "unconnected-(IC31-NC_48-PadJ10)") (class "Default")
      (node (ref "IC31") (pin "J10") (pinfunction "NC_48_J10") (pintype "bidirectional"))
    )
    (net (code "946") (name "unconnected-(IC31-NC_49-PadK2)") (class "Default")
      (node (ref "IC31") (pin "K2") (pinfunction "NC_49_K2") (pintype "bidirectional"))
    )
    (net (code "947") (name "unconnected-(IC31-NC_50-PadK4)") (class "Default")
      (node (ref "IC31") (pin "K4") (pinfunction "NC_50_K4") (pintype "bidirectional"))
    )
    (net (code "948") (name "unconnected-(IC31-NC_51-PadK5)") (class "Default")
      (node (ref "IC31") (pin "K5") (pinfunction "NC_51_K5") (pintype "bidirectional"))
    )
    (net (code "949") (name "unconnected-(IC31-NC_52-PadK7)") (class "Default")
      (node (ref "IC31") (pin "K7") (pinfunction "NC_52_K7") (pintype "bidirectional"))
    )
    (net (code "950") (name "unconnected-(IC31-NC_53-PadK9)") (class "Default")
      (node (ref "IC31") (pin "K9") (pinfunction "NC_53_K9") (pintype "bidirectional"))
    )
    (net (code "951") (name "unconnected-(IC31-NC_54-PadK10)") (class "Default")
      (node (ref "IC31") (pin "K10") (pinfunction "NC_54_K10") (pintype "bidirectional"))
    )
    (net (code "952") (name "unconnected-(J3-PadMP1)") (class "Default")
      (node (ref "J3") (pin "MP1") (pinfunction "MP1_MP1") (pintype "bidirectional"))
    )
    (net (code "953") (name "unconnected-(J3-PadMP2)") (class "Default")
      (node (ref "J3") (pin "MP2") (pinfunction "MP2_MP2") (pintype "bidirectional"))
    )
    (net (code "954") (name "unconnected-(J3-PadMP3)") (class "Default")
      (node (ref "J3") (pin "MP3") (pinfunction "MP3_MP3") (pintype "bidirectional"))
    )
    (net (code "955") (name "unconnected-(J3-PadMP4)") (class "Default")
      (node (ref "J3") (pin "MP4") (pinfunction "MP4_MP4") (pintype "bidirectional"))
    )
    (net (code "956") (name "unconnected-(J3-PadMP5)") (class "Default")
      (node (ref "J3") (pin "MP5") (pinfunction "MP5_MP5") (pintype "bidirectional"))
    )
    (net (code "957") (name "unconnected-(J4-Pad14)") (class "Default")
      (node (ref "J4") (pin "14") (pinfunction "14_14") (pintype "passive"))
    )
    (net (code "958") (name "unconnected-(J4-Pad16)") (class "Default")
      (node (ref "J4") (pin "16") (pinfunction "16_16") (pintype "passive"))
    )
    (net (code "959") (name "unconnected-(J4-Pad31)") (class "Default")
      (node (ref "J4") (pin "31") (pinfunction "31_31") (pintype "passive"))
    )
    (net (code "960") (name "unconnected-(J4-Pad33)") (class "Default")
      (node (ref "J4") (pin "33") (pinfunction "33_33") (pintype "passive"))
    )
    (net (code "961") (name "unconnected-(J4-Pad38)") (class "Default")
      (node (ref "J4") (pin "38") (pinfunction "38_38") (pintype "passive"))
    )
    (net (code "962") (name "unconnected-(J4-Pad42)") (class "Default")
      (node (ref "J4") (pin "42") (pinfunction "42_42") (pintype "passive"))
    )
    (net (code "963") (name "unconnected-(J4-Pad44)") (class "Default")
      (node (ref "J4") (pin "44") (pinfunction "44_44") (pintype "passive"))
    )
    (net (code "964") (name "unconnected-(J4-Pad46)") (class "Default")
      (node (ref "J4") (pin "46") (pinfunction "46_46") (pintype "passive"))
    )
    (net (code "965") (name "unconnected-(J4-Pad48)") (class "Default")
      (node (ref "J4") (pin "48") (pinfunction "48_48") (pintype "passive"))
    )
    (net (code "966") (name "unconnected-(J4-Pad50)") (class "Default")
      (node (ref "J4") (pin "50") (pinfunction "50_50") (pintype "passive"))
    )
    (net (code "967") (name "unconnected-(J4-Pad52)") (class "Default")
      (node (ref "J4") (pin "52") (pinfunction "52_52") (pintype "passive"))
    )
    (net (code "968") (name "unconnected-(J4-Pad54)") (class "Default")
      (node (ref "J4") (pin "54") (pinfunction "54_54") (pintype "passive"))
    )
    (net (code "969") (name "unconnected-(J4-Pad56)") (class "Default")
      (node (ref "J4") (pin "56") (pinfunction "56_56") (pintype "passive"))
    )
    (net (code "970") (name "unconnected-(J4-Pad79)") (class "Default")
      (node (ref "J4") (pin "79") (pinfunction "79_79") (pintype "passive"))
    )
    (net (code "971") (name "unconnected-(J5-Pad42)") (class "Default")
      (node (ref "J5") (pin "42") (pinfunction "42_42") (pintype "passive"))
    )
    (net (code "972") (name "unconnected-(J5-Pad44)") (class "Default")
      (node (ref "J5") (pin "44") (pinfunction "44_44") (pintype "passive"))
    )
    (net (code "973") (name "unconnected-(J5-Pad46)") (class "Default")
      (node (ref "J5") (pin "46") (pinfunction "46_46") (pintype "passive"))
    )
    (net (code "974") (name "unconnected-(J5-Pad48)") (class "Default")
      (node (ref "J5") (pin "48") (pinfunction "48_48") (pintype "passive"))
    )
    (net (code "975") (name "unconnected-(J5-Pad50)") (class "Default")
      (node (ref "J5") (pin "50") (pinfunction "50_50") (pintype "passive"))
    )
    (net (code "976") (name "unconnected-(J5-Pad52)") (class "Default")
      (node (ref "J5") (pin "52") (pinfunction "52_52") (pintype "passive"))
    )
    (net (code "977") (name "unconnected-(J14-Pad67)") (class "Default")
      (node (ref "J14") (pin "67") (pinfunction "67_67") (pintype "passive"))
    )
    (net (code "978") (name "unconnected-(U$5-THROUGH_HOLE-Pad1{slash}16IN)") (class "Default")
      (node (ref "U$5") (pin "1/16IN") (pinfunction "THROUGH_HOLE_1/16IN") (pintype "bidirectional"))
    )
    (net (code "979") (name "unconnected-(U$7-THROUGH_HOLE-Pad1{slash}16IN)") (class "Default")
      (node (ref "U$7") (pin "1/16IN") (pinfunction "THROUGH_HOLE_1/16IN") (pintype "bidirectional"))
    )
    (net (code "980") (name "unconnected-(U$9-THROUGH_HOLE-Pad1{slash}16IN)") (class "Default")
      (node (ref "U$9") (pin "1/16IN") (pinfunction "THROUGH_HOLE_1/16IN") (pintype "bidirectional"))
    )
    (net (code "981") (name "unconnected-(U$10-THROUGH_HOLE-Pad1{slash}16IN)") (class "Default")
      (node (ref "U$10") (pin "1/16IN") (pinfunction "THROUGH_HOLE_1/16IN") (pintype "bidirectional"))
    )
    (net (code "982") (name "unconnected-(U$14-THROUGH_HOLE-Pad1{slash}16IN)") (class "Default")
      (node (ref "U$14") (pin "1/16IN") (pinfunction "THROUGH_HOLE_1/16IN") (pintype "bidirectional"))
    )
    (net (code "983") (name "unconnected-(U$15-THROUGH_HOLE-Pad1{slash}16IN)") (class "Default")
      (node (ref "U$15") (pin "1/16IN") (pinfunction "THROUGH_HOLE_1/16IN") (pintype "bidirectional"))
    )
    (net (code "984") (name "unconnected-(UC1-AGND-Pad31_AGND)") (class "Default")
      (node (ref "UC1") (pin "31_AGND") (pinfunction "AGND_31_AGND") (pintype "passive"))
    )
    (net (code "985") (name "unconnected-(UC1-Pad3V3)") (class "Default")
      (node (ref "UC1") (pin "3V3") (pinfunction "3V3_3V3") (pintype "passive"))
    )
    (net (code "986") (name "unconnected-(UC1-Pad5V)") (class "Default")
      (node (ref "UC1") (pin "5V") (pinfunction "5V_5V") (pintype "passive"))
    )
    (net (code "987") (name "unconnected-(UC1-Pad5V_USB_STLK)") (class "Default")
      (node (ref "UC1") (pin "5V_USB_STLK") (pinfunction "5V_USB_STLK_5V_USB_STLK") (pintype "passive"))
    )
    (net (code "988") (name "unconnected-(UC1-PadBOOT0)") (class "Default")
      (node (ref "UC1") (pin "BOOT0") (pinfunction "BOOT0_BOOT0") (pintype "passive"))
    )
    (net (code "989") (name "unconnected-(UC1-PadIOREF)") (class "Default")
      (node (ref "UC1") (pin "IOREF") (pinfunction "IOREF_IOREF") (pintype "passive"))
    )
    (net (code "990") (name "unconnected-(UC1-PadNC_1)") (class "Default")
      (node (ref "UC1") (pin "NC_1") (pinfunction "NC_1_NC_1") (pintype "passive"))
    )
    (net (code "991") (name "unconnected-(UC1-PadNC_2)") (class "Default")
      (node (ref "UC1") (pin "NC_2") (pinfunction "NC_2_NC_2") (pintype "passive"))
    )
    (net (code "992") (name "unconnected-(UC1-PadNC_3)") (class "Default")
      (node (ref "UC1") (pin "NC_3") (pinfunction "NC_3_NC_3") (pintype "passive"))
    )
    (net (code "993") (name "unconnected-(UC1-PadNRST)") (class "Default")
      (node (ref "UC1") (pin "NRST") (pinfunction "NRST_NRST") (pintype "passive"))
    )
    (net (code "994") (name "unconnected-(UC1-PadVBAT)") (class "Default")
      (node (ref "UC1") (pin "VBAT") (pinfunction "VBAT_VBAT") (pintype "passive"))
    )
    (net (code "995") (name "unconnected-(UC1-PadVIN)") (class "Default")
      (node (ref "UC1") (pin "VIN") (pinfunction "VIN_VIN") (pintype "passive"))
    )
    (net (code "996") (name "unconnected-(UC1-PadVREFP)") (class "Default")
      (node (ref "UC1") (pin "VREFP") (pinfunction "VREFP_VREFP") (pintype "passive"))
    )
    (net (code "997") (name "~{CS_ADC}") (class "Default")
      (node (ref "!CS_ADC") (pin "TP") (pinfunction "TP_TP") (pintype "bidirectional"))
      (node (ref "IC38") (pin "13") (pinfunction "~{CS}_13") (pintype "input"))
      (node (ref "IC51") (pin "13") (pinfunction "~{CS}_13") (pintype "input"))
      (node (ref "IC52") (pin "13") (pinfunction "~{CS}_13") (pintype "input"))
      (node (ref "J4") (pin "53") (pinfunction "53_53") (pintype "passive"))
    )
    (net (code "998") (name "~{IMU_CS}") (class "Default")
      (node (ref "!IMU_CS") (pin "TP") (pinfunction "TP_TP") (pintype "bidirectional"))
      (node (ref "IC31") (pin "G3") (pinfunction "~{CS}_G3") (pintype "bidirectional"))
      (node (ref "J4") (pin "03") (pinfunction "03_03") (pintype "passive"))
    )
    (net (code "999") (name "~{IMU_RST}") (class "Default")
      (node (ref "!IMU_RST") (pin "TP") (pinfunction "TP_TP") (pintype "bidirectional"))
      (node (ref "IC31") (pin "F3") (pinfunction "~{RST}_F3") (pintype "bidirectional"))
      (node (ref "J4") (pin "01") (pinfunction "01_01") (pintype "passive"))
    )
    (net (code "1000") (name "~{ISO_CS}") (class "Default")
      (node (ref "!ISO_CS") (pin "TP") (pinfunction "TP_TP") (pintype "bidirectional"))
      (node (ref "IC32") (pin "4") (pinfunction "~{CS}_4") (pintype "bidirectional"))
      (node (ref "J4") (pin "28") (pinfunction "28_28") (pintype "passive"))
    )
    (net (code "1001") (name "~{THERMOCOUPLE_CS}") (class "Default")
      (node (ref "!TEMP_CS") (pin "TP") (pinfunction "TP_TP") (pintype "bidirectional"))
      (node (ref "J4") (pin "36") (pinfunction "36_36") (pintype "passive"))
      (node (ref "R519") (pin "2") (pinfunction "2_2") (pintype "bidirectional"))
    )
  )
)
